# 63-00022_Mainboard_3_2.net
KiCad netlist of a schematic drawn in EAGLE
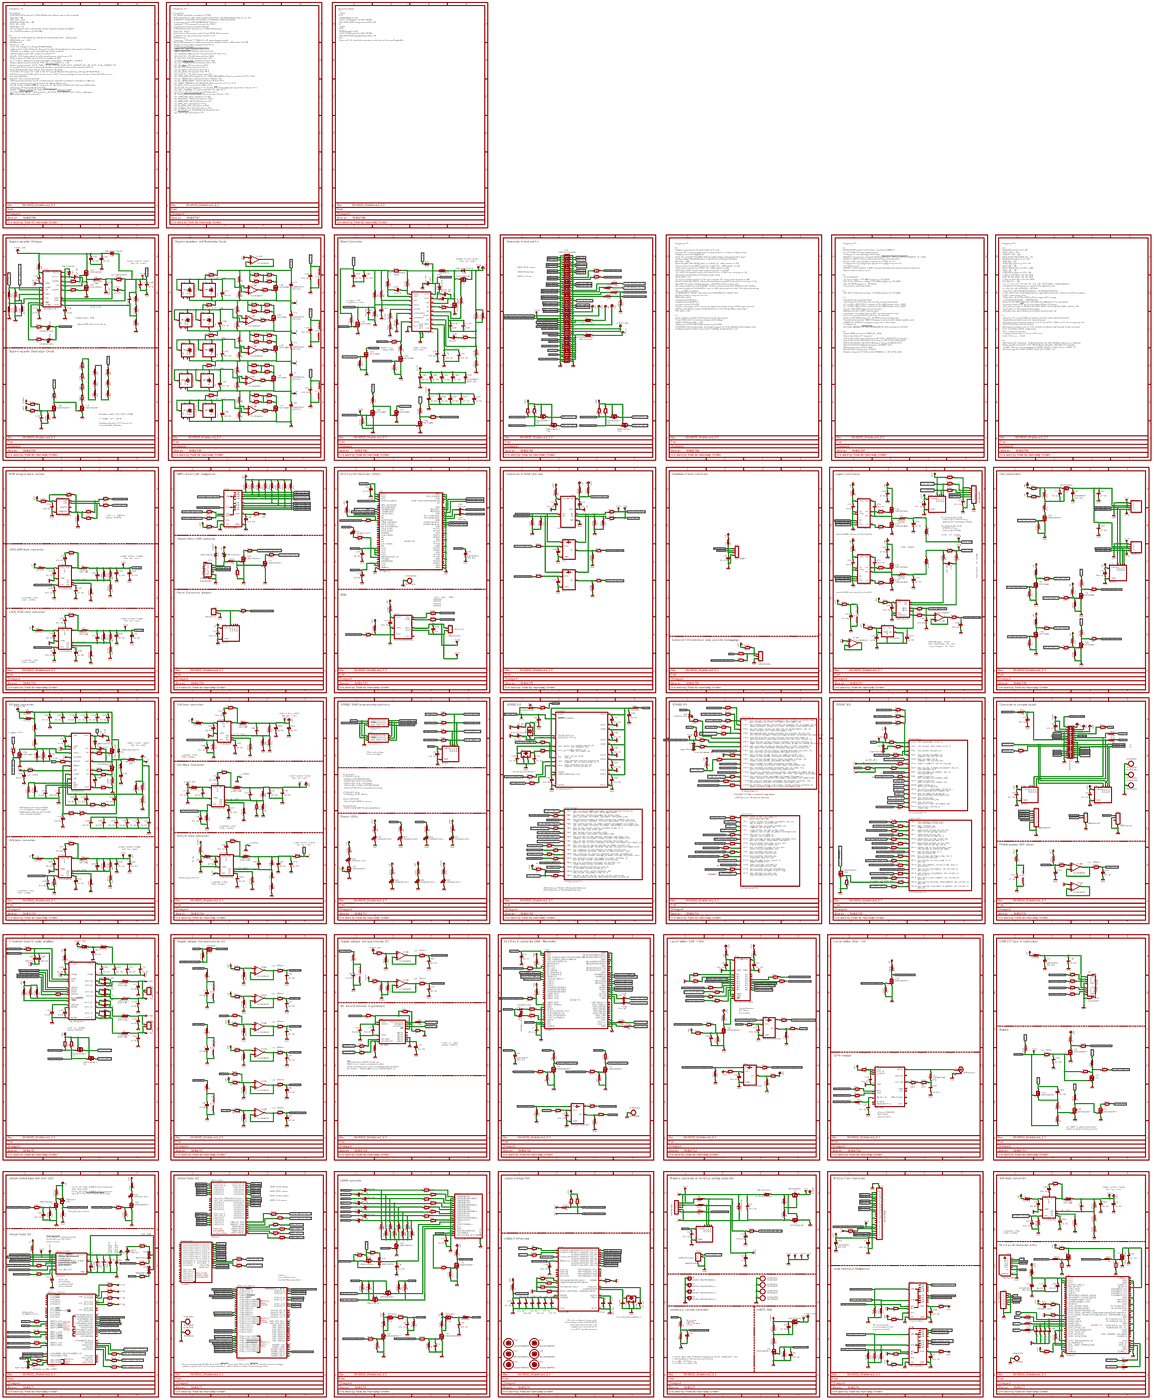
[diagram p0: schematic, sheet 1, overview]
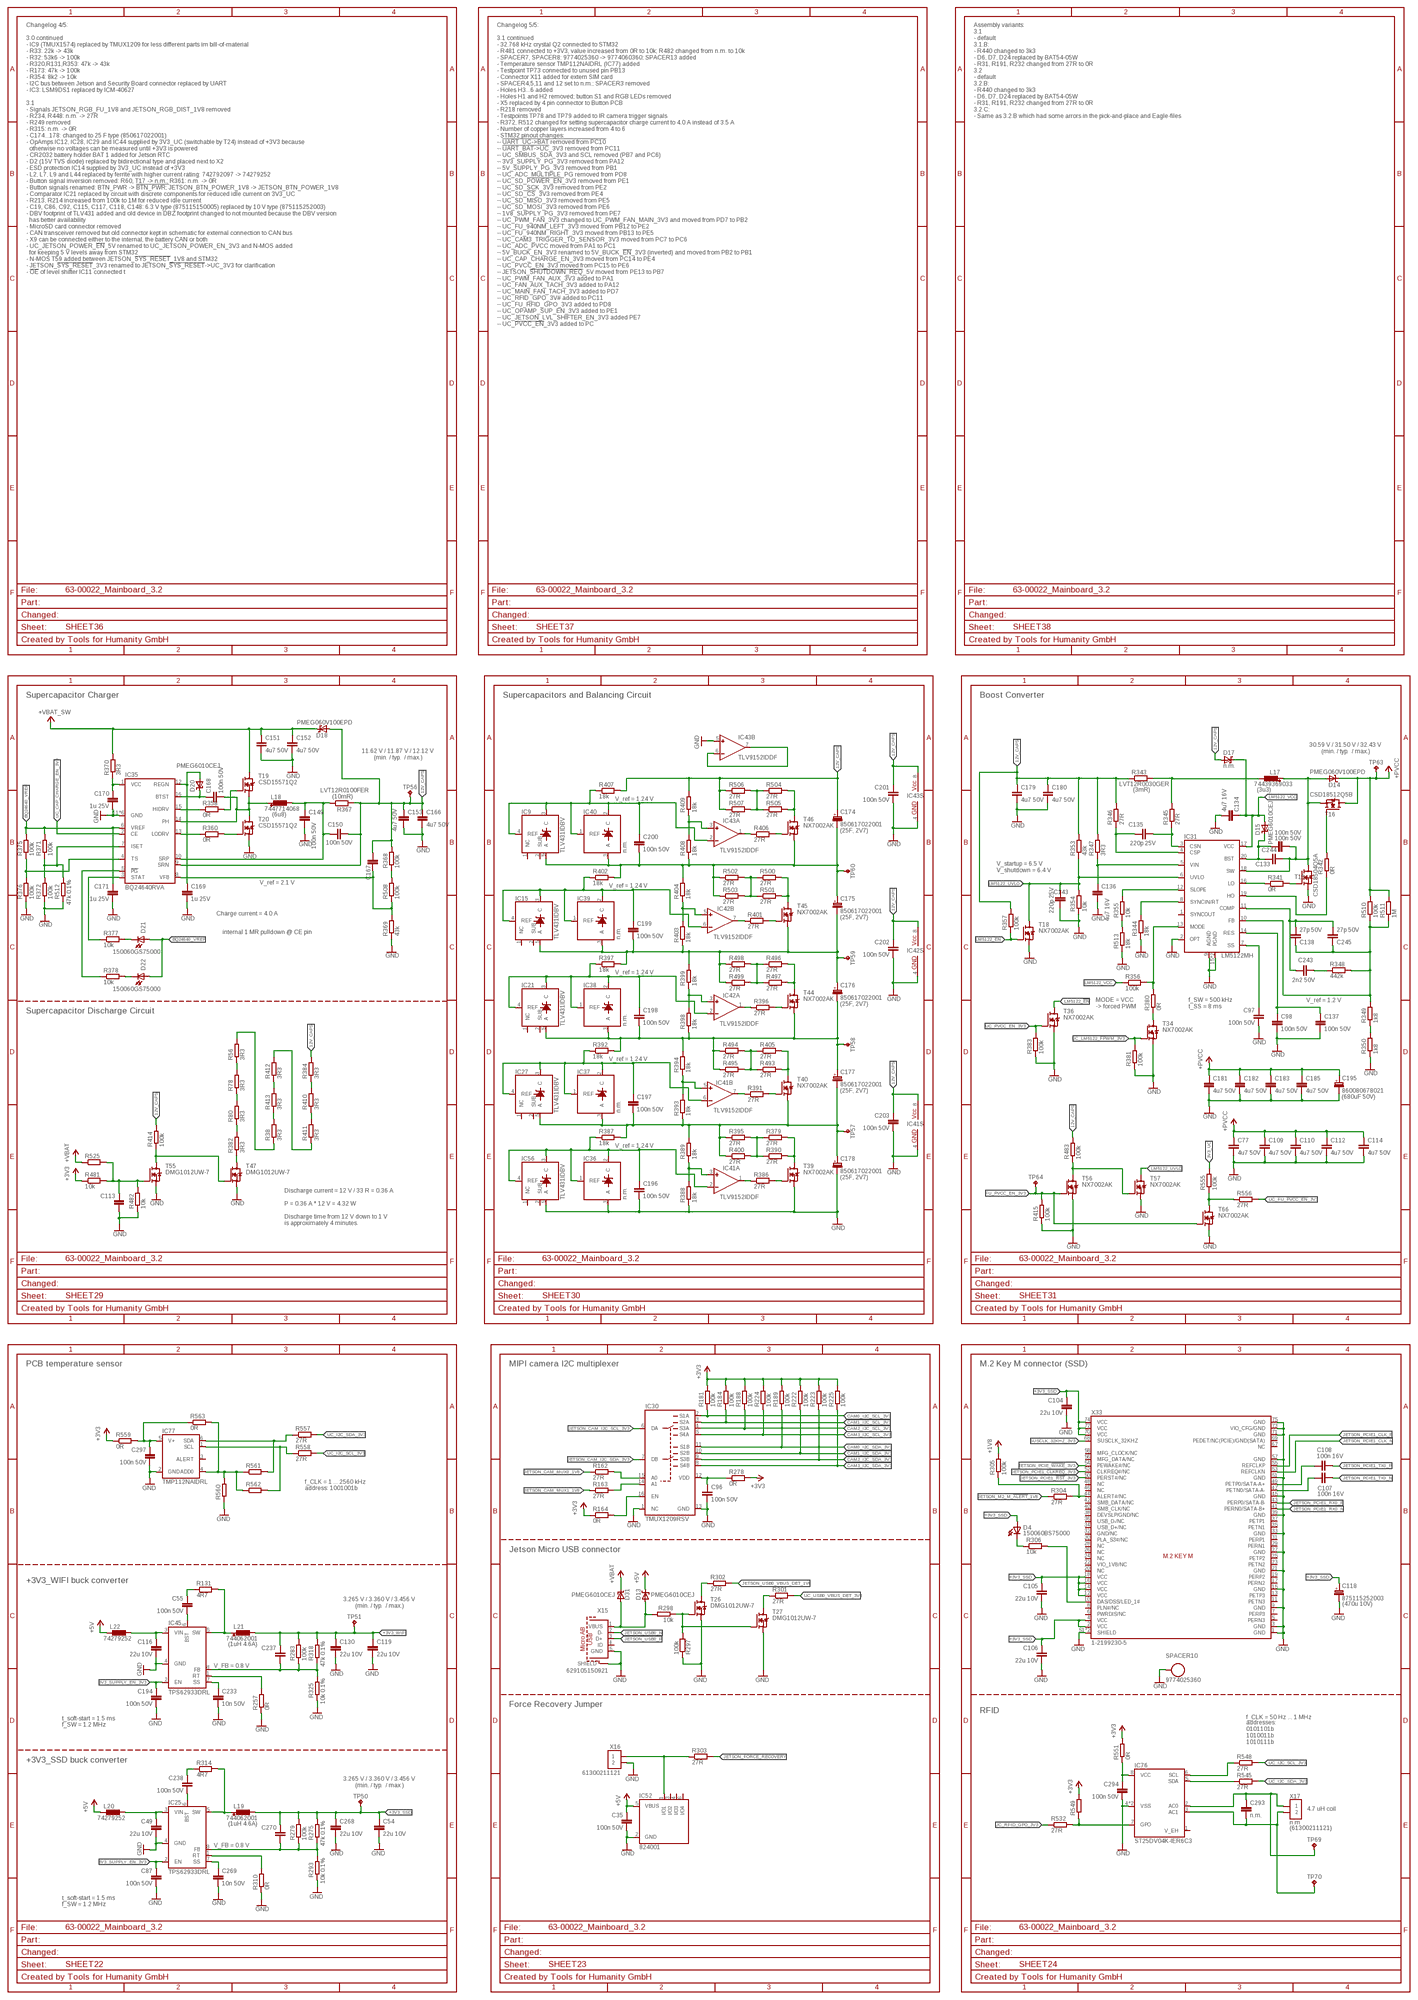
[diagram p1: schematic, sheet 1, part 1 of 4]
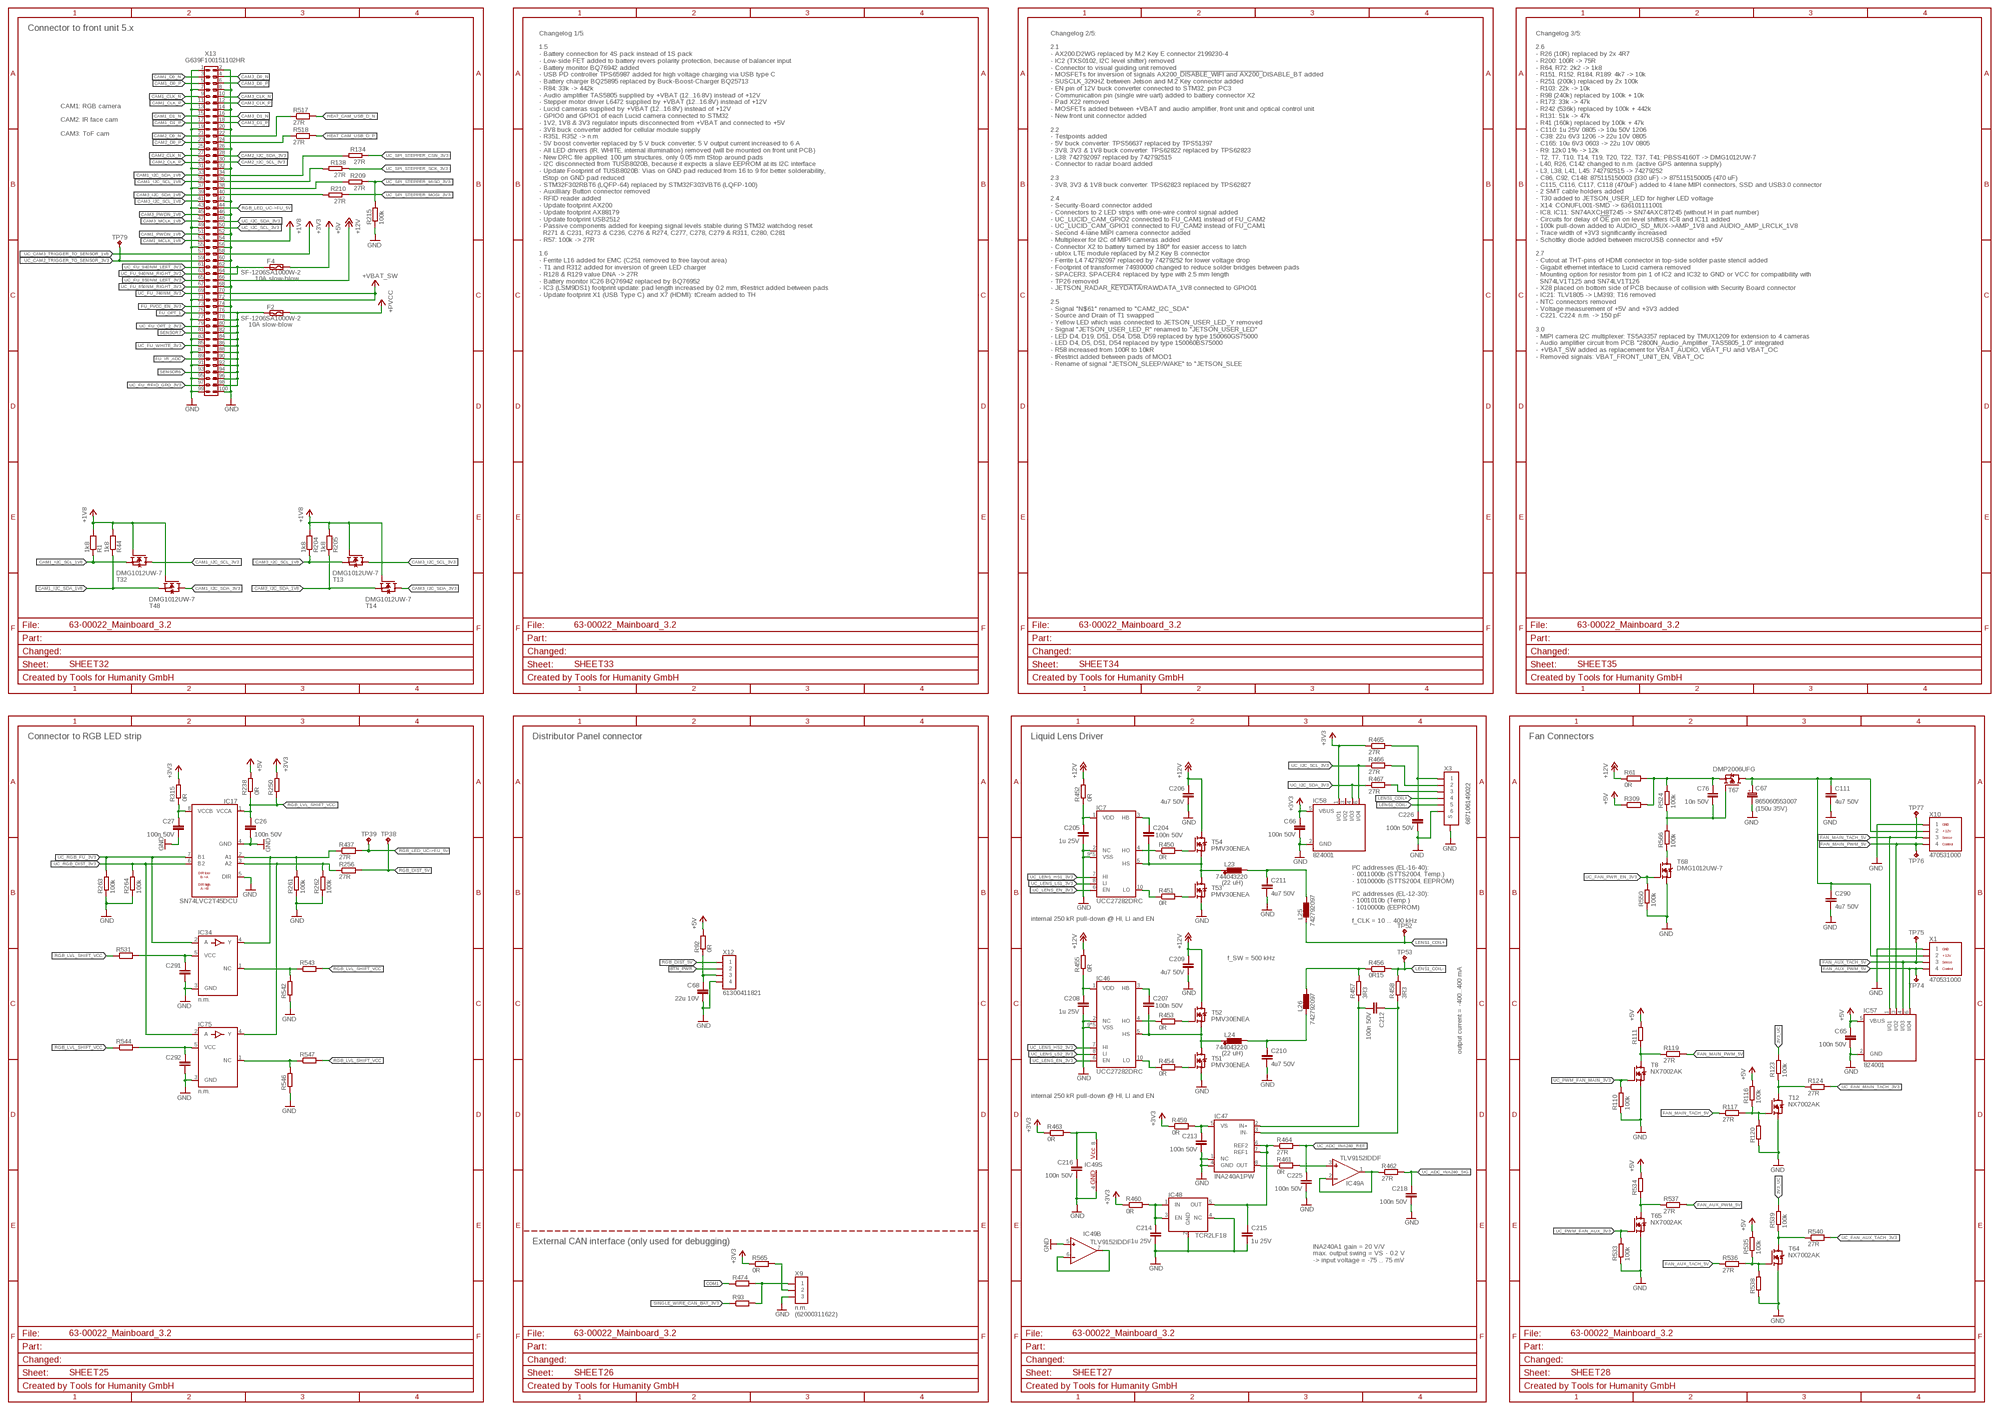
[diagram p2: schematic, sheet 1, part 2 of 4]
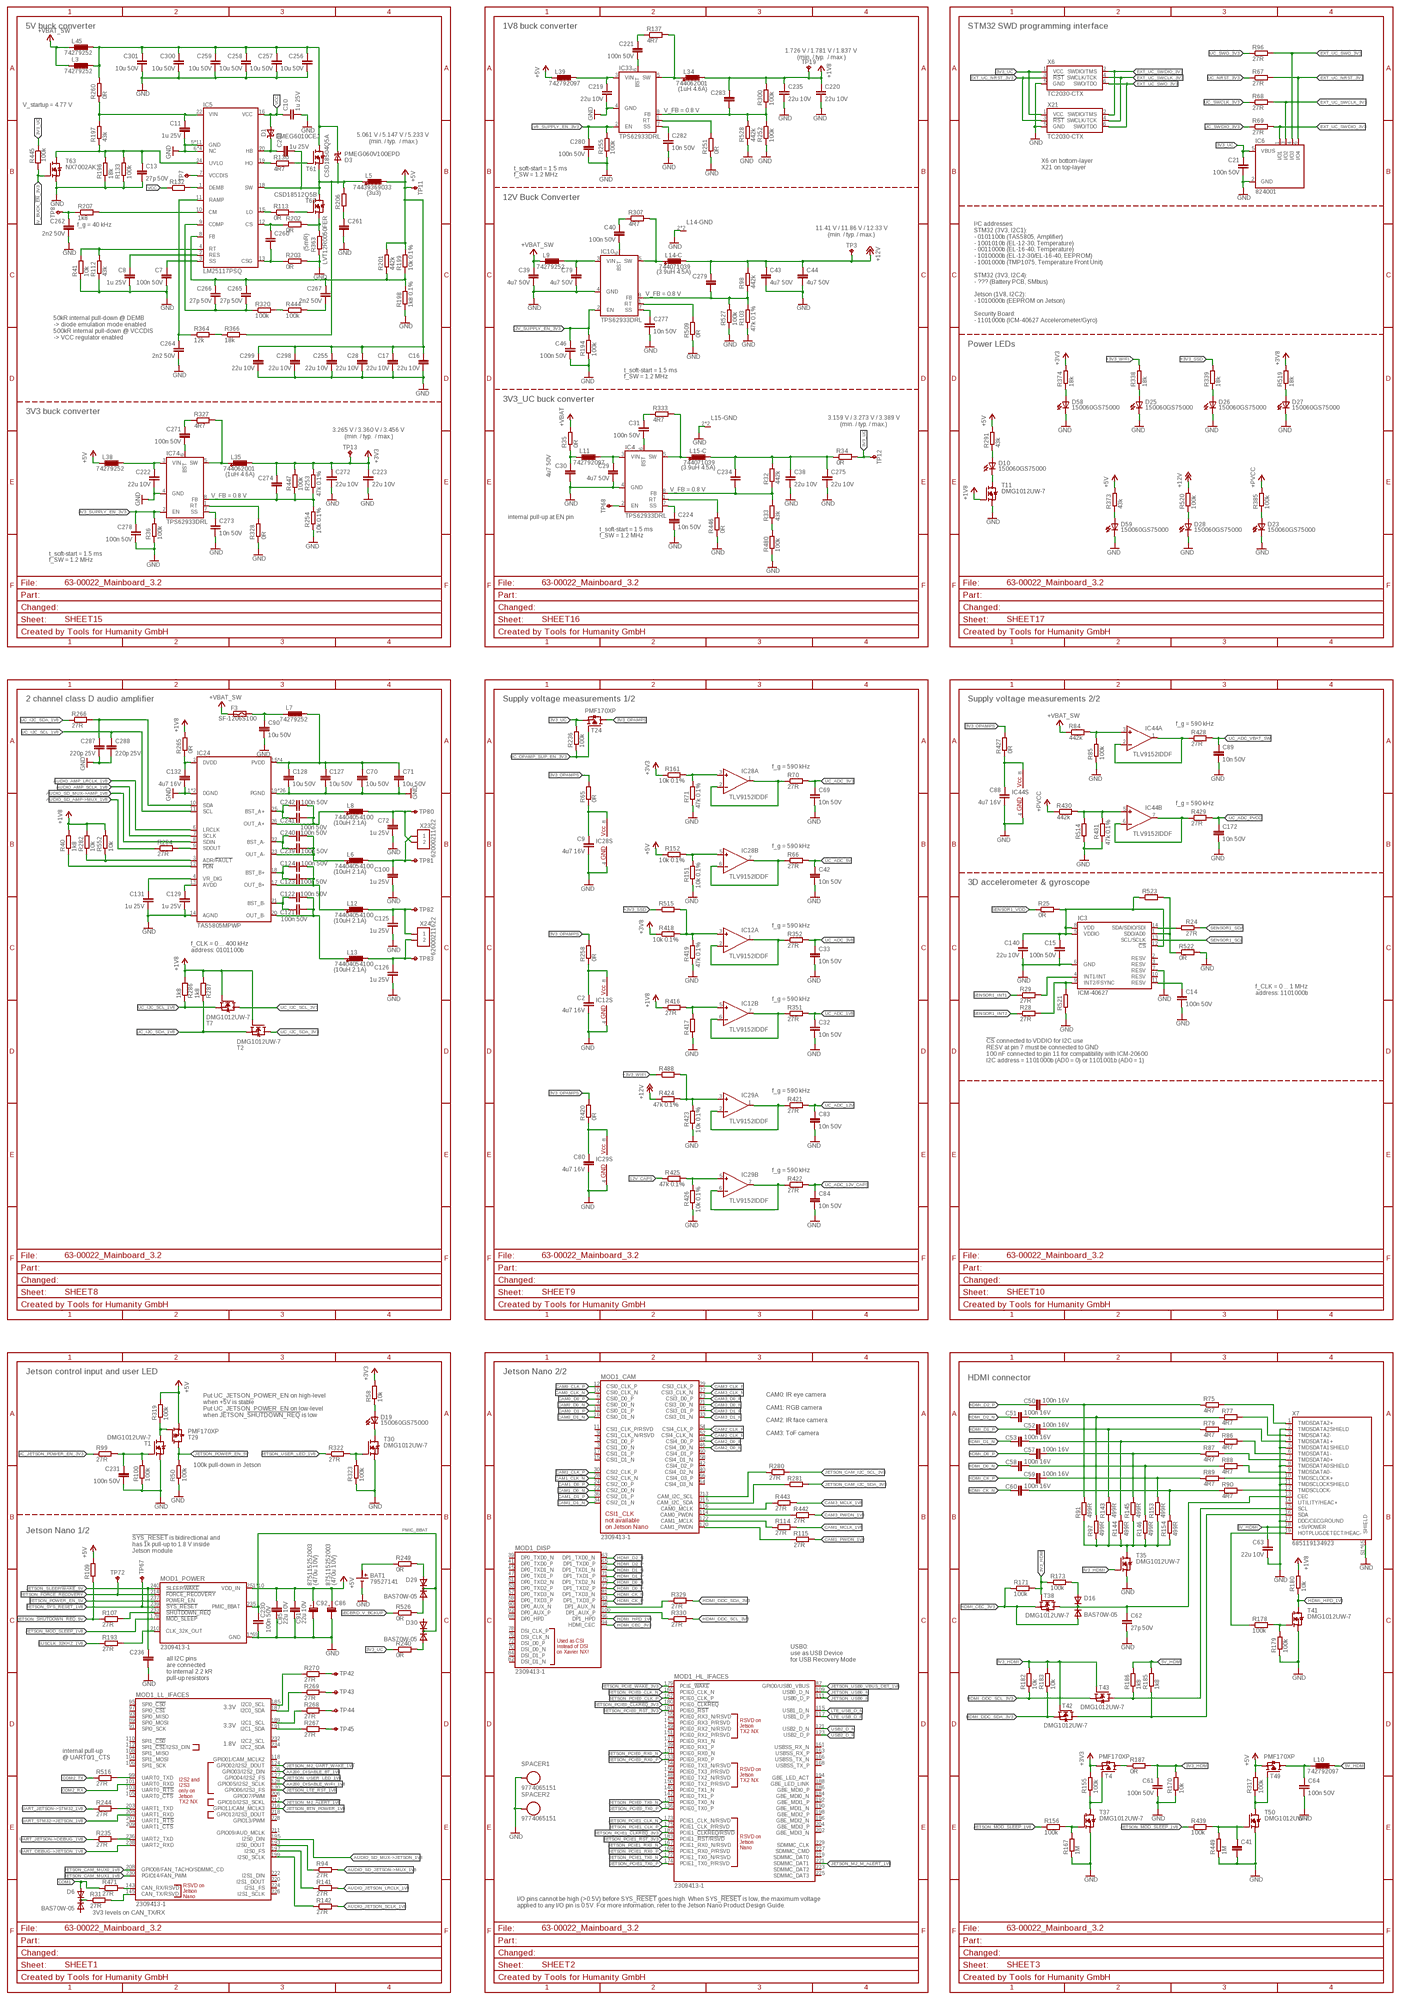
[diagram p3: schematic, sheet 1, part 3 of 4]
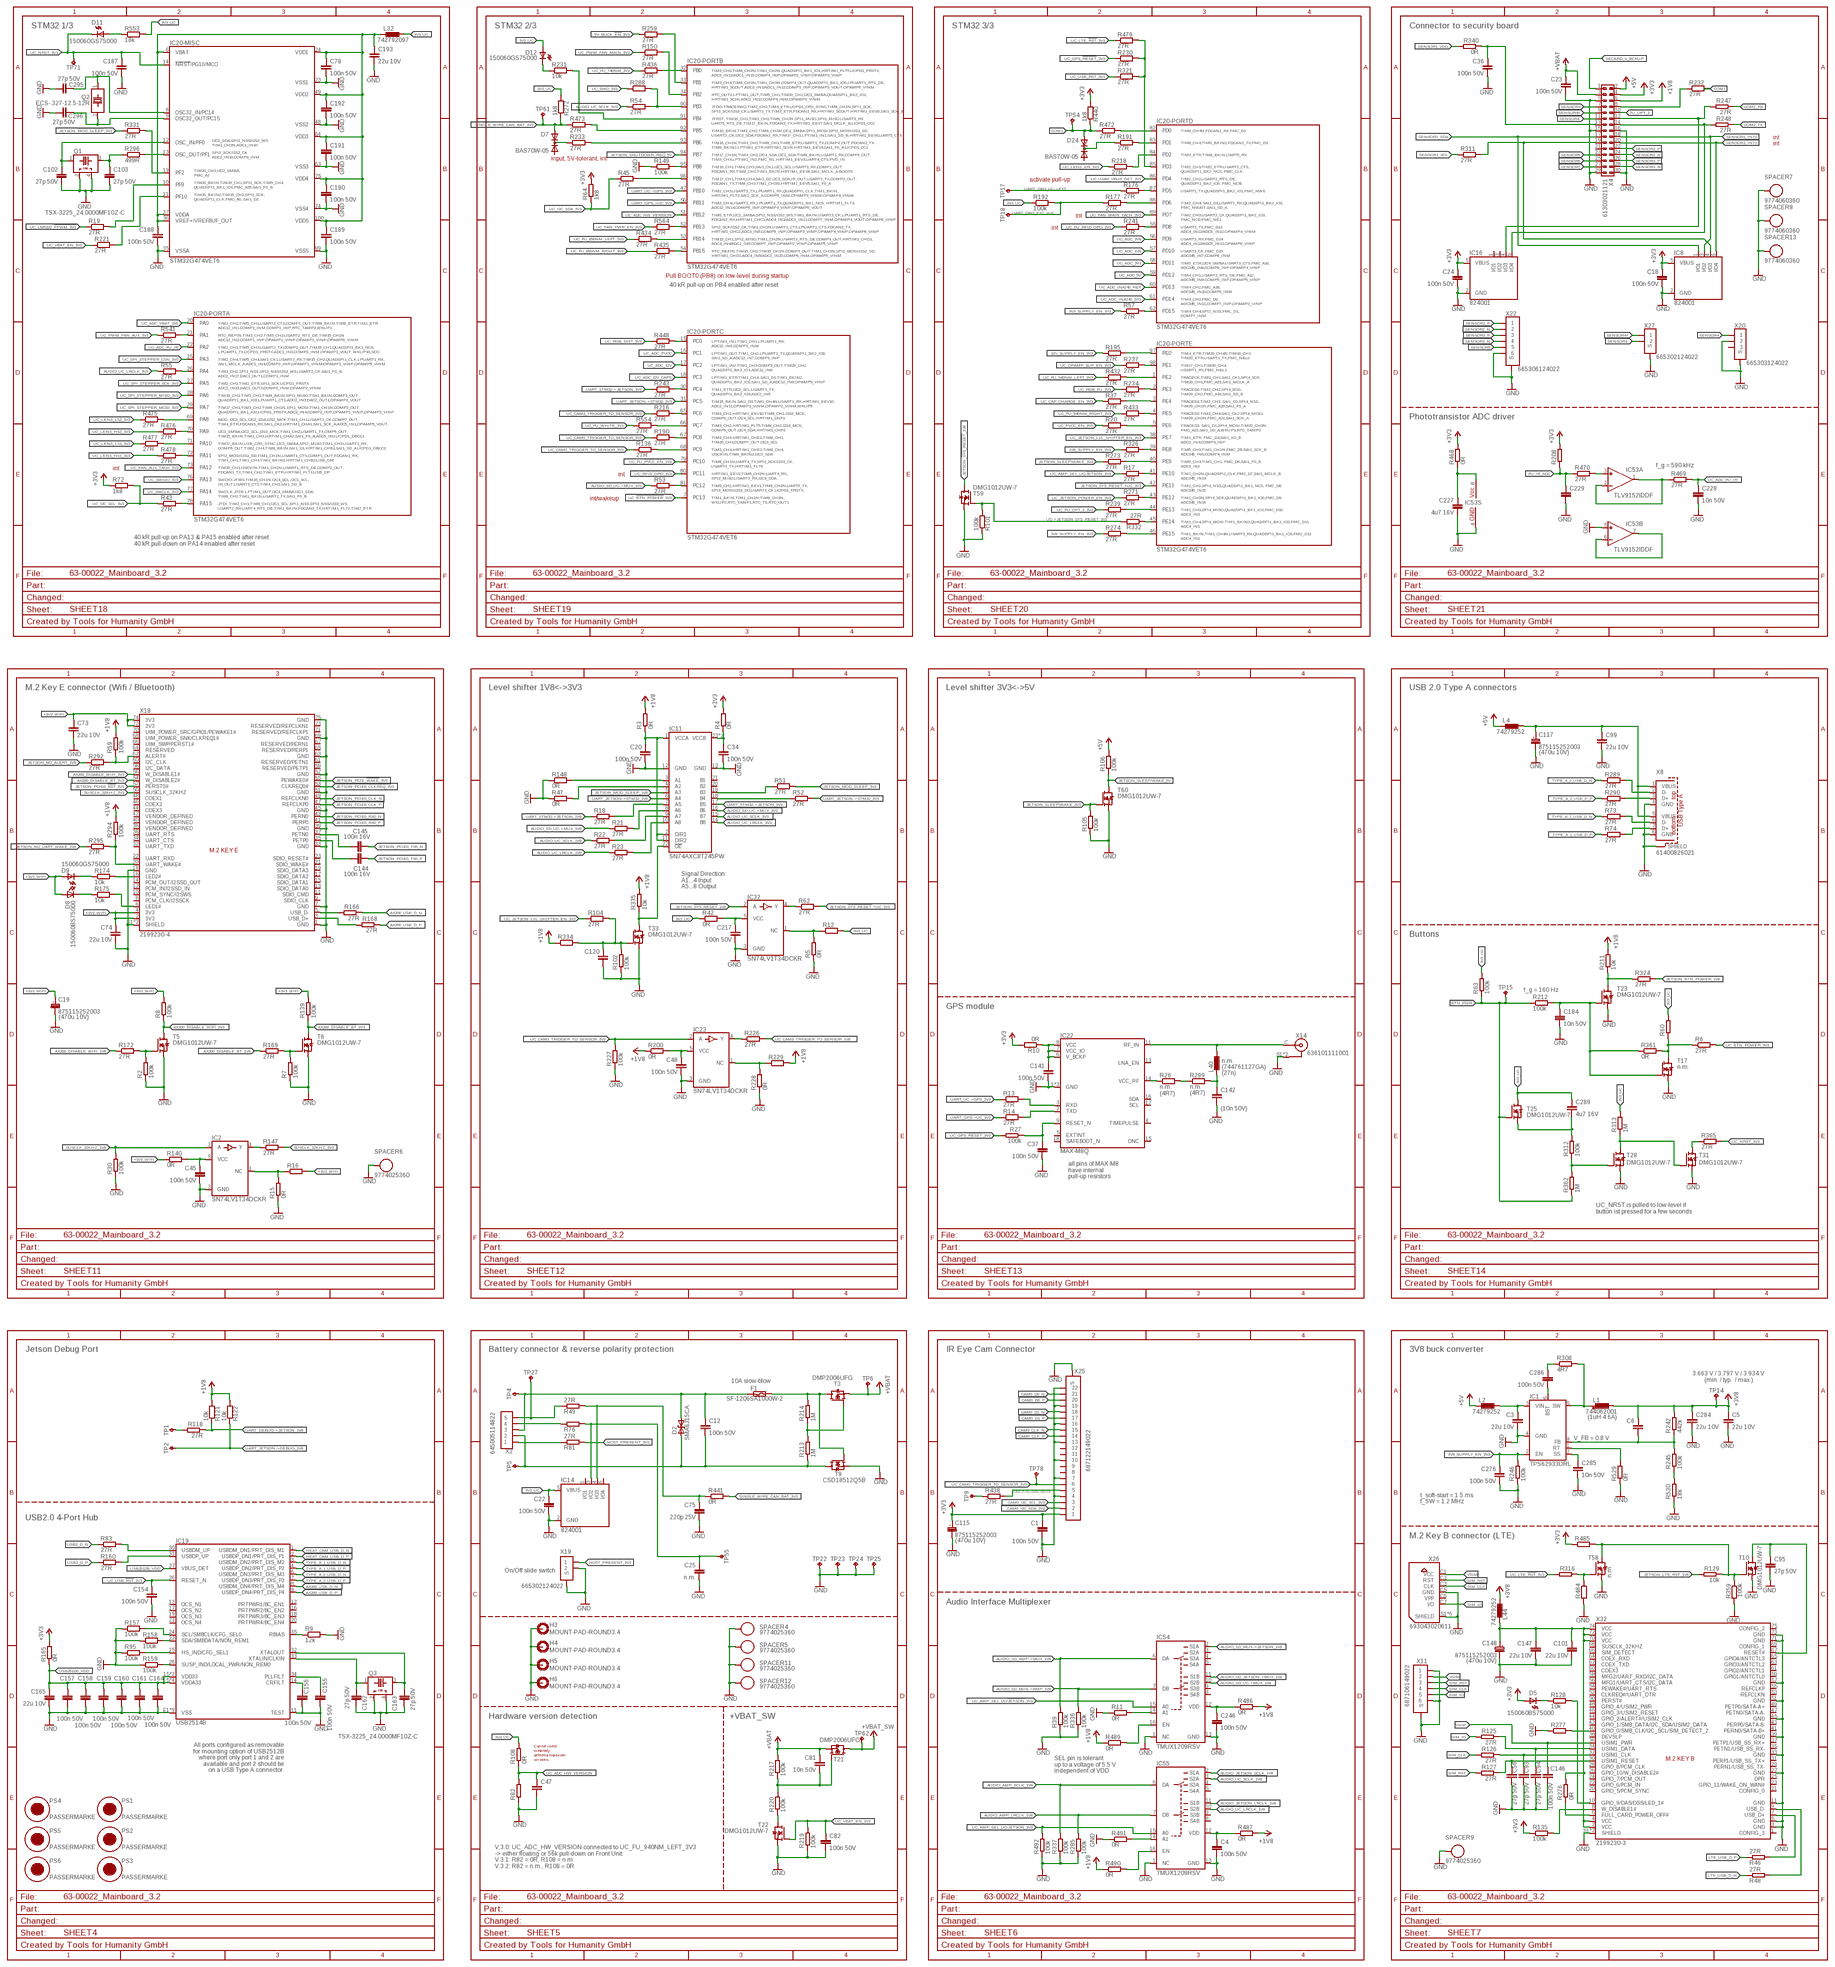
[diagram p4: schematic, sheet 1, part 4 of 4]

(export (version "E")
  (design (tool "Eeschema 10.0.6"))
  (components
    (comp (ref "BAT1")
      (value "79527141")
      (footprint "eagle-import:79527141_WUERTH")
      (fields (field (name "MANUFACTURER") "Wuerth"))
      (libsource (lib "eagle-import") (part "79527141"))
    )
    (comp (ref "C1")
      (value "100n 50V")
      (footprint "eagle-import:C0603")
      (fields
        (field (name "MANUFACTURER") "AVX")
        (field (name "TOLERANCE") "±20 %")
        (field (name "VOLTAGE") "50.0 V")
      )
      (libsource (lib "eagle-import") (part "C-EU-C0603-100N"))
    )
    (comp (ref "C2")
      (value "4u7 16V")
      (footprint "eagle-import:C0805")
      (fields
        (field (name "MANUFACTURER") "AVX")
        (field (name "TOLERANCE") "±20 %")
        (field (name "VOLTAGE") "16.0 V")
      )
      (libsource (lib "eagle-import") (part "C-EU-C0805-4U7"))
    )
    (comp (ref "C3")
      (value "22u 10V")
      (footprint "eagle-import:C0805")
      (fields
        (field (name "MANUFACTURER") "AVX")
        (field (name "TOLERANCE") "±20 %")
        (field (name "VOLTAGE") "10.0 V")
      )
      (libsource (lib "eagle-import") (part "C-EU-C0805-22U"))
    )
    (comp (ref "C4")
      (value "100n 50V")
      (footprint "eagle-import:C0603")
      (fields
        (field (name "MANUFACTURER") "AVX")
        (field (name "TOLERANCE") "±20 %")
        (field (name "VOLTAGE") "50.0 V")
      )
      (libsource (lib "eagle-import") (part "C-EU-C0603-100N"))
    )
    (comp (ref "C5")
      (value "22u 10V")
      (footprint "eagle-import:C0805")
      (fields
        (field (name "MANUFACTURER") "AVX")
        (field (name "TOLERANCE") "±20 %")
        (field (name "VOLTAGE") "10.0 V")
      )
      (libsource (lib "eagle-import") (part "C-EU-C0805-22U"))
    )
    (comp (ref "C6")
      (value "C-EU-C0603")
      (footprint "eagle-import:C0603")
      (fields (field (name "TOLERANCE") "±20 %") (field (name "VOLTAGE") "50.0 V"))
      (libsource (lib "eagle-import") (part "C-EU-C0603"))
    )
    (comp (ref "C7")
      (value "100n 50V")
      (footprint "eagle-import:C0603")
      (fields
        (field (name "MANUFACTURER") "AVX")
        (field (name "TOLERANCE") "±20 %")
        (field (name "VOLTAGE") "50.0 V")
      )
      (libsource (lib "eagle-import") (part "C-EU-C0603-100N"))
    )
    (comp (ref "C8")
      (value "1u 25V")
      (footprint "eagle-import:C0805")
      (fields
        (field (name "MANUFACTURER") "AVX")
        (field (name "TOLERANCE") "±20 %")
        (field (name "VOLTAGE") "25.0 V")
      )
      (libsource (lib "eagle-import") (part "C-EU-C0805-1U"))
    )
    (comp (ref "C9")
      (value "4u7 16V")
      (footprint "eagle-import:C0805")
      (fields
        (field (name "MANUFACTURER") "AVX")
        (field (name "TOLERANCE") "±20 %")
        (field (name "VOLTAGE") "16.0 V")
      )
      (libsource (lib "eagle-import") (part "C-EU-C0805-4U7"))
    )
    (comp (ref "C10")
      (value "1u 25V")
      (footprint "eagle-import:C0805")
      (fields
        (field (name "MANUFACTURER") "AVX")
        (field (name "TOLERANCE") "±20 %")
        (field (name "VOLTAGE") "25.0 V")
      )
      (libsource (lib "eagle-import") (part "C-EU-C0805-1U"))
    )
    (comp (ref "C11")
      (value "1u 25V")
      (footprint "eagle-import:C0805")
      (fields
        (field (name "MANUFACTURER") "AVX")
        (field (name "TOLERANCE") "±20 %")
        (field (name "VOLTAGE") "25.0 V")
      )
      (libsource (lib "eagle-import") (part "C-EU-C0805-1U"))
    )
    (comp (ref "C12")
      (value "100n 50V")
      (footprint "eagle-import:C0603")
      (fields
        (field (name "MANUFACTURER") "AVX")
        (field (name "TOLERANCE") "±20 %")
        (field (name "VOLTAGE") "50.0 V")
      )
      (libsource (lib "eagle-import") (part "C-EU-C0603-100N"))
    )
    (comp (ref "C13")
      (value "27p 50V")
      (footprint "eagle-import:C0603")
      (fields
        (field (name "MANUFACTURER") "AVX")
        (field (name "TOLERANCE") "±20 %")
        (field (name "VOLTAGE") "50.0 V")
      )
      (libsource (lib "eagle-import") (part "C-EU-C0603-27P"))
    )
    (comp (ref "C14")
      (value "100n 50V")
      (footprint "eagle-import:C0603")
      (fields
        (field (name "MANUFACTURER") "AVX")
        (field (name "TOLERANCE") "±20 %")
        (field (name "VOLTAGE") "50.0 V")
      )
      (libsource (lib "eagle-import") (part "C-EU-C0603-100N"))
    )
    (comp (ref "C15")
      (value "100n 50V")
      (footprint "eagle-import:C0603")
      (fields
        (field (name "MANUFACTURER") "AVX")
        (field (name "TOLERANCE") "±20 %")
        (field (name "VOLTAGE") "50.0 V")
      )
      (libsource (lib "eagle-import") (part "C-EU-C0603-100N"))
    )
    (comp (ref "C16")
      (value "22u 10V")
      (footprint "eagle-import:C0805")
      (fields
        (field (name "MANUFACTURER") "AVX")
        (field (name "TOLERANCE") "±20 %")
        (field (name "VOLTAGE") "10.0 V")
      )
      (libsource (lib "eagle-import") (part "C-EU-C0805-22U"))
    )
    (comp (ref "C17")
      (value "22u 10V")
      (footprint "eagle-import:C0805")
      (fields
        (field (name "MANUFACTURER") "AVX")
        (field (name "TOLERANCE") "±20 %")
        (field (name "VOLTAGE") "10.0 V")
      )
      (libsource (lib "eagle-import") (part "C-EU-C0805-22U"))
    )
    (comp (ref "C18")
      (value "100n 50V")
      (footprint "eagle-import:C0603")
      (fields
        (field (name "MANUFACTURER") "AVX")
        (field (name "TOLERANCE") "±20 %")
        (field (name "VOLTAGE") "50.0 V")
      )
      (libsource (lib "eagle-import") (part "C-EU-C0603-100N"))
    )
    (comp (ref "C19")
      (value "875115252003")
      (footprint "eagle-import:WCAP-PSHP_8.0X8.7_WE")
      (fields
        (field (name "MANUFACTURER") "Wuerth")
        (field (name "TOLERANCE") "±20 %")
        (field (name "VOLTAGE") "10.0 V")
      )
      (libsource (lib "eagle-import") (part "875115252003"))
    )
    (comp (ref "C20")
      (value "100n 50V")
      (footprint "eagle-import:C0603")
      (fields
        (field (name "MANUFACTURER") "AVX")
        (field (name "TOLERANCE") "±20 %")
        (field (name "VOLTAGE") "50.0 V")
      )
      (libsource (lib "eagle-import") (part "C-EU-C0603-100N"))
    )
    (comp (ref "C21")
      (value "100n 50V")
      (footprint "eagle-import:C0603")
      (fields
        (field (name "MANUFACTURER") "AVX")
        (field (name "TOLERANCE") "±20 %")
        (field (name "VOLTAGE") "50.0 V")
      )
      (libsource (lib "eagle-import") (part "C-EU-C0603-100N"))
    )
    (comp (ref "C22")
      (value "100n 50V")
      (footprint "eagle-import:C0603")
      (fields
        (field (name "MANUFACTURER") "AVX")
        (field (name "TOLERANCE") "±20 %")
        (field (name "VOLTAGE") "50.0 V")
      )
      (libsource (lib "eagle-import") (part "C-EU-C0603-100N"))
    )
    (comp (ref "C23")
      (value "100n 50V")
      (footprint "eagle-import:C0603")
      (fields
        (field (name "MANUFACTURER") "AVX")
        (field (name "TOLERANCE") "±20 %")
        (field (name "VOLTAGE") "50.0 V")
      )
      (libsource (lib "eagle-import") (part "C-EU-C0603-100N"))
    )
    (comp (ref "C24")
      (value "100n 50V")
      (footprint "eagle-import:C0603")
      (fields
        (field (name "MANUFACTURER") "AVX")
        (field (name "TOLERANCE") "±20 %")
        (field (name "VOLTAGE") "50.0 V")
      )
      (libsource (lib "eagle-import") (part "C-EU-C0603-100N"))
    )
    (comp (ref "C25")
      (value "n.m.")
      (footprint "eagle-import:C0402")
      (fields (field (name "TOLERANCE") "±20 %") (field (name "VOLTAGE") "25.0 V"))
      (libsource (lib "eagle-import") (part "C-EU-C0402"))
    )
    (comp (ref "C26")
      (value "100n 50V")
      (footprint "eagle-import:C0603")
      (fields
        (field (name "MANUFACTURER") "AVX")
        (field (name "TOLERANCE") "±20 %")
        (field (name "VOLTAGE") "50.0 V")
      )
      (libsource (lib "eagle-import") (part "C-EU-C0603-100N"))
    )
    (comp (ref "C27")
      (value "100n 50V")
      (footprint "eagle-import:C0603")
      (fields
        (field (name "MANUFACTURER") "AVX")
        (field (name "TOLERANCE") "±20 %")
        (field (name "VOLTAGE") "50.0 V")
      )
      (libsource (lib "eagle-import") (part "C-EU-C0603-100N"))
    )
    (comp (ref "C28")
      (value "22u 10V")
      (footprint "eagle-import:C0805")
      (fields
        (field (name "MANUFACTURER") "AVX")
        (field (name "TOLERANCE") "±20 %")
        (field (name "VOLTAGE") "10.0 V")
      )
      (libsource (lib "eagle-import") (part "C-EU-C0805-22U"))
    )
    (comp (ref "C29")
      (value "4u7 50V")
      (footprint "eagle-import:C1210")
      (fields
        (field (name "MANUFACTURER") "Taiyo Yuden")
        (field (name "TOLERANCE") "±20 %")
        (field (name "VOLTAGE") "50.0 V")
      )
      (libsource (lib "eagle-import") (part "C-EU-C1210-4U7-50V"))
    )
    (comp (ref "C30")
      (value "4u7 50V")
      (footprint "eagle-import:C1210")
      (fields
        (field (name "MANUFACTURER") "Taiyo Yuden")
        (field (name "TOLERANCE") "±20 %")
        (field (name "VOLTAGE") "50.0 V")
      )
      (libsource (lib "eagle-import") (part "C-EU-C1210-4U7-50V"))
    )
    (comp (ref "C31")
      (value "100n 50V")
      (footprint "eagle-import:C0603")
      (fields
        (field (name "MANUFACTURER") "AVX")
        (field (name "TOLERANCE") "±20 %")
        (field (name "VOLTAGE") "50.0 V")
      )
      (libsource (lib "eagle-import") (part "C-EU-C0603-100N"))
    )
    (comp (ref "C32")
      (value "10n 50V")
      (footprint "eagle-import:C0603")
      (fields
        (field (name "MANUFACTURER") "Samsung")
        (field (name "TOLERANCE") "±20 %")
        (field (name "VOLTAGE") "50.0 V")
      )
      (libsource (lib "eagle-import") (part "C-EU-C0603-10N"))
    )
    (comp (ref "C33")
      (value "10n 50V")
      (footprint "eagle-import:C0603")
      (fields
        (field (name "MANUFACTURER") "Samsung")
        (field (name "TOLERANCE") "±20 %")
        (field (name "VOLTAGE") "50.0 V")
      )
      (libsource (lib "eagle-import") (part "C-EU-C0603-10N"))
    )
    (comp (ref "C34")
      (value "100n 50V")
      (footprint "eagle-import:C0603")
      (fields
        (field (name "MANUFACTURER") "AVX")
        (field (name "TOLERANCE") "±20 %")
        (field (name "VOLTAGE") "50.0 V")
      )
      (libsource (lib "eagle-import") (part "C-EU-C0603-100N"))
    )
    (comp (ref "C35")
      (value "100n 50V")
      (footprint "eagle-import:C0603")
      (fields
        (field (name "MANUFACTURER") "AVX")
        (field (name "TOLERANCE") "±20 %")
        (field (name "VOLTAGE") "50.0 V")
      )
      (libsource (lib "eagle-import") (part "C-EU-C0603-100N"))
    )
    (comp (ref "C36")
      (value "100n 50V")
      (footprint "eagle-import:C0603")
      (fields
        (field (name "MANUFACTURER") "AVX")
        (field (name "TOLERANCE") "±20 %")
        (field (name "VOLTAGE") "50.0 V")
      )
      (libsource (lib "eagle-import") (part "C-EU-C0603-100N"))
    )
    (comp (ref "C37")
      (value "100n 50V")
      (footprint "eagle-import:C0603")
      (fields
        (field (name "MANUFACTURER") "AVX")
        (field (name "TOLERANCE") "±20 %")
        (field (name "VOLTAGE") "50.0 V")
      )
      (libsource (lib "eagle-import") (part "C-EU-C0603-100N"))
    )
    (comp (ref "C38")
      (value "22u 10V")
      (footprint "eagle-import:C0805")
      (fields
        (field (name "MANUFACTURER") "AVX")
        (field (name "TOLERANCE") "±20 %")
        (field (name "VOLTAGE") "10.0 V")
      )
      (libsource (lib "eagle-import") (part "C-EU-C0805-22U"))
    )
    (comp (ref "C39")
      (value "4u7 50V")
      (footprint "eagle-import:C1210")
      (fields
        (field (name "MANUFACTURER") "Taiyo Yuden")
        (field (name "TOLERANCE") "±20 %")
        (field (name "VOLTAGE") "50.0 V")
      )
      (libsource (lib "eagle-import") (part "C-EU-C1210-4U7-50V"))
    )
    (comp (ref "C40")
      (value "100n 50V")
      (footprint "eagle-import:C0603")
      (fields
        (field (name "MANUFACTURER") "AVX")
        (field (name "TOLERANCE") "±20 %")
        (field (name "VOLTAGE") "50.0 V")
      )
      (libsource (lib "eagle-import") (part "C-EU-C0603-100N"))
    )
    (comp (ref "C41")
      (value "C-EU-C0603")
      (footprint "eagle-import:C0603")
      (fields (field (name "TOLERANCE") "±20 %") (field (name "VOLTAGE") "50.0 V"))
      (libsource (lib "eagle-import") (part "C-EU-C0603"))
    )
    (comp (ref "C42")
      (value "10n 50V")
      (footprint "eagle-import:C0603")
      (fields
        (field (name "MANUFACTURER") "Samsung")
        (field (name "TOLERANCE") "±20 %")
        (field (name "VOLTAGE") "50.0 V")
      )
      (libsource (lib "eagle-import") (part "C-EU-C0603-10N"))
    )
    (comp (ref "C43")
      (value "4u7 50V")
      (footprint "eagle-import:C1210")
      (fields
        (field (name "MANUFACTURER") "Taiyo Yuden")
        (field (name "TOLERANCE") "±20 %")
        (field (name "VOLTAGE") "50.0 V")
      )
      (libsource (lib "eagle-import") (part "C-EU-C1210-4U7-50V"))
    )
    (comp (ref "C44")
      (value "4u7 50V")
      (footprint "eagle-import:C1210")
      (fields
        (field (name "MANUFACTURER") "Taiyo Yuden")
        (field (name "TOLERANCE") "±20 %")
        (field (name "VOLTAGE") "50.0 V")
      )
      (libsource (lib "eagle-import") (part "C-EU-C1210-4U7-50V"))
    )
    (comp (ref "C45")
      (value "100n 50V")
      (footprint "eagle-import:C0603")
      (fields
        (field (name "MANUFACTURER") "AVX")
        (field (name "TOLERANCE") "±20 %")
        (field (name "VOLTAGE") "50.0 V")
      )
      (libsource (lib "eagle-import") (part "C-EU-C0603-100N"))
    )
    (comp (ref "C46")
      (value "100n 50V")
      (footprint "eagle-import:C0603")
      (fields
        (field (name "MANUFACTURER") "AVX")
        (field (name "TOLERANCE") "±20 %")
        (field (name "VOLTAGE") "50.0 V")
      )
      (libsource (lib "eagle-import") (part "C-EU-C0603-100N"))
    )
    (comp (ref "C47")
      (value "C-EU-C0603")
      (footprint "eagle-import:C0603")
      (fields (field (name "TOLERANCE") "±20 %") (field (name "VOLTAGE") "50.0 V"))
      (libsource (lib "eagle-import") (part "C-EU-C0603"))
    )
    (comp (ref "C48")
      (value "100n 50V")
      (footprint "eagle-import:C0603")
      (fields
        (field (name "MANUFACTURER") "AVX")
        (field (name "TOLERANCE") "±20 %")
        (field (name "VOLTAGE") "50.0 V")
      )
      (libsource (lib "eagle-import") (part "C-EU-C0603-100N"))
    )
    (comp (ref "C49")
      (value "22u 10V")
      (footprint "eagle-import:C0805")
      (fields
        (field (name "MANUFACTURER") "AVX")
        (field (name "TOLERANCE") "±20 %")
        (field (name "VOLTAGE") "10.0 V")
      )
      (libsource (lib "eagle-import") (part "C-EU-C0805-22U"))
    )
    (comp (ref "C50")
      (value "100n 16V")
      (footprint "eagle-import:C0402")
      (fields
        (field (name "MANUFACTURER") "KEMET")
        (field (name "TOLERANCE") "±20 %")
        (field (name "VOLTAGE") "16.0 V")
      )
      (libsource (lib "eagle-import") (part "C-EU-C0402-100N"))
    )
    (comp (ref "C51")
      (value "100n 16V")
      (footprint "eagle-import:C0402")
      (fields
        (field (name "MANUFACTURER") "KEMET")
        (field (name "TOLERANCE") "±20 %")
        (field (name "VOLTAGE") "16.0 V")
      )
      (libsource (lib "eagle-import") (part "C-EU-C0402-100N"))
    )
    (comp (ref "C52")
      (value "100n 16V")
      (footprint "eagle-import:C0402")
      (fields
        (field (name "MANUFACTURER") "KEMET")
        (field (name "TOLERANCE") "±20 %")
        (field (name "VOLTAGE") "16.0 V")
      )
      (libsource (lib "eagle-import") (part "C-EU-C0402-100N"))
    )
    (comp (ref "C53")
      (value "100n 16V")
      (footprint "eagle-import:C0402")
      (fields
        (field (name "MANUFACTURER") "KEMET")
        (field (name "TOLERANCE") "±20 %")
        (field (name "VOLTAGE") "16.0 V")
      )
      (libsource (lib "eagle-import") (part "C-EU-C0402-100N"))
    )
    (comp (ref "C54")
      (value "22u 10V")
      (footprint "eagle-import:C0805")
      (fields
        (field (name "MANUFACTURER") "AVX")
        (field (name "TOLERANCE") "±20 %")
        (field (name "VOLTAGE") "10.0 V")
      )
      (libsource (lib "eagle-import") (part "C-EU-C0805-22U"))
    )
    (comp (ref "C55")
      (value "100n 50V")
      (footprint "eagle-import:C0603")
      (fields
        (field (name "MANUFACTURER") "AVX")
        (field (name "TOLERANCE") "±20 %")
        (field (name "VOLTAGE") "50.0 V")
      )
      (libsource (lib "eagle-import") (part "C-EU-C0603-100N"))
    )
    (comp (ref "C56")
      (value "27p 50V")
      (footprint "eagle-import:C0603")
      (fields
        (field (name "MANUFACTURER") "AVX")
        (field (name "TOLERANCE") "±20 %")
        (field (name "VOLTAGE") "50.0 V")
      )
      (libsource (lib "eagle-import") (part "C-EU-C0603-27P"))
    )
    (comp (ref "C57")
      (value "100n 16V")
      (footprint "eagle-import:C0402")
      (fields
        (field (name "MANUFACTURER") "KEMET")
        (field (name "TOLERANCE") "±20 %")
        (field (name "VOLTAGE") "16.0 V")
      )
      (libsource (lib "eagle-import") (part "C-EU-C0402-100N"))
    )
    (comp (ref "C58")
      (value "100n 16V")
      (footprint "eagle-import:C0402")
      (fields
        (field (name "MANUFACTURER") "KEMET")
        (field (name "TOLERANCE") "±20 %")
        (field (name "VOLTAGE") "16.0 V")
      )
      (libsource (lib "eagle-import") (part "C-EU-C0402-100N"))
    )
    (comp (ref "C59")
      (value "100n 16V")
      (footprint "eagle-import:C0402")
      (fields
        (field (name "MANUFACTURER") "KEMET")
        (field (name "TOLERANCE") "±20 %")
        (field (name "VOLTAGE") "16.0 V")
      )
      (libsource (lib "eagle-import") (part "C-EU-C0402-100N"))
    )
    (comp (ref "C60")
      (value "100n 16V")
      (footprint "eagle-import:C0402")
      (fields
        (field (name "MANUFACTURER") "KEMET")
        (field (name "TOLERANCE") "±20 %")
        (field (name "VOLTAGE") "16.0 V")
      )
      (libsource (lib "eagle-import") (part "C-EU-C0402-100N"))
    )
    (comp (ref "C61")
      (value "100n 50V")
      (footprint "eagle-import:C0603")
      (fields
        (field (name "MANUFACTURER") "AVX")
        (field (name "TOLERANCE") "±20 %")
        (field (name "VOLTAGE") "50.0 V")
      )
      (libsource (lib "eagle-import") (part "C-EU-C0603-100N"))
    )
    (comp (ref "C62")
      (value "27p 50V")
      (footprint "eagle-import:C0603")
      (fields
        (field (name "MANUFACTURER") "AVX")
        (field (name "TOLERANCE") "±20 %")
        (field (name "VOLTAGE") "50.0 V")
      )
      (libsource (lib "eagle-import") (part "C-EU-C0603-27P"))
    )
    (comp (ref "C63")
      (value "22u 10V")
      (footprint "eagle-import:C0805")
      (fields
        (field (name "MANUFACTURER") "AVX")
        (field (name "TOLERANCE") "±20 %")
        (field (name "VOLTAGE") "10.0 V")
      )
      (libsource (lib "eagle-import") (part "C-EU-C0805-22U"))
    )
    (comp (ref "C64")
      (value "100n 50V")
      (footprint "eagle-import:C0603")
      (fields
        (field (name "MANUFACTURER") "AVX")
        (field (name "TOLERANCE") "±20 %")
        (field (name "VOLTAGE") "50.0 V")
      )
      (libsource (lib "eagle-import") (part "C-EU-C0603-100N"))
    )
    (comp (ref "C65")
      (value "100n 50V")
      (footprint "eagle-import:C0603")
      (fields
        (field (name "MANUFACTURER") "AVX")
        (field (name "TOLERANCE") "±20 %")
        (field (name "VOLTAGE") "50.0 V")
      )
      (libsource (lib "eagle-import") (part "C-EU-C0603-100N"))
    )
    (comp (ref "C66")
      (value "100n 50V")
      (footprint "eagle-import:C0603")
      (fields
        (field (name "MANUFACTURER") "AVX")
        (field (name "TOLERANCE") "±20 %")
        (field (name "VOLTAGE") "50.0 V")
      )
      (libsource (lib "eagle-import") (part "C-EU-C0603-100N"))
    )
    (comp (ref "C67")
      (value "865060553007")
      (footprint "eagle-import:WCAP-ASLL_8.0X10.5_WE")
      (fields
        (field (name "MANUFACTURER") "Wuerth")
        (field (name "TOLERANCE") "± 20%")
        (field (name "VOLTAGE") "35.0 V")
      )
      (libsource (lib "eagle-import") (part "865060553007"))
    )
    (comp (ref "C68")
      (value "22u 10V")
      (footprint "eagle-import:C0805")
      (fields
        (field (name "MANUFACTURER") "AVX")
        (field (name "TOLERANCE") "±20 %")
        (field (name "VOLTAGE") "10.0 V")
      )
      (libsource (lib "eagle-import") (part "C-EU-C0805-22U"))
    )
    (comp (ref "C69")
      (value "10n 50V")
      (footprint "eagle-import:C0603")
      (fields
        (field (name "MANUFACTURER") "Samsung")
        (field (name "TOLERANCE") "±20 %")
        (field (name "VOLTAGE") "50.0 V")
      )
      (libsource (lib "eagle-import") (part "C-EU-C0603-10N"))
    )
    (comp (ref "C70")
      (value "10u 50V")
      (footprint "eagle-import:C1206")
      (fields
        (field (name "MANUFACTURER") "Samsung")
        (field (name "TOLERANCE") "±20 %")
        (field (name "VOLTAGE") "50.0 V")
      )
      (libsource (lib "eagle-import") (part "C-EU-C1206-10U"))
    )
    (comp (ref "C71")
      (value "10u 50V")
      (footprint "eagle-import:C1206")
      (fields
        (field (name "MANUFACTURER") "Samsung")
        (field (name "TOLERANCE") "±20 %")
        (field (name "VOLTAGE") "50.0 V")
      )
      (libsource (lib "eagle-import") (part "C-EU-C1206-10U"))
    )
    (comp (ref "C72")
      (value "1u 25V")
      (footprint "eagle-import:C0805")
      (fields
        (field (name "MANUFACTURER") "AVX")
        (field (name "TOLERANCE") "±20 %")
        (field (name "VOLTAGE") "25.0 V")
      )
      (libsource (lib "eagle-import") (part "C-EU-C0805-1U"))
    )
    (comp (ref "C73")
      (value "22u 10V")
      (footprint "eagle-import:C0805")
      (fields
        (field (name "MANUFACTURER") "AVX")
        (field (name "TOLERANCE") "±20 %")
        (field (name "VOLTAGE") "10.0 V")
      )
      (libsource (lib "eagle-import") (part "C-EU-C0805-22U"))
    )
    (comp (ref "C74")
      (value "22u 10V")
      (footprint "eagle-import:C0805")
      (fields
        (field (name "MANUFACTURER") "AVX")
        (field (name "TOLERANCE") "±20 %")
        (field (name "VOLTAGE") "10.0 V")
      )
      (libsource (lib "eagle-import") (part "C-EU-C0805-22U"))
    )
    (comp (ref "C75")
      (value "220p 25V")
      (footprint "eagle-import:C0402")
      (fields
        (field (name "MANUFACTURER") "Wuerth")
        (field (name "TOLERANCE") "±10 %")
        (field (name "VOLTAGE") "25.0 V")
      )
      (libsource (lib "eagle-import") (part "C-EU-C0402-220P"))
    )
    (comp (ref "C76")
      (value "10n 50V")
      (footprint "eagle-import:C0603")
      (fields
        (field (name "MANUFACTURER") "Samsung")
        (field (name "TOLERANCE") "±20 %")
        (field (name "VOLTAGE") "50.0 V")
      )
      (libsource (lib "eagle-import") (part "C-EU-C0603-10N"))
    )
    (comp (ref "C77")
      (value "4u7 50V")
      (footprint "eagle-import:C1210")
      (fields
        (field (name "MANUFACTURER") "Taiyo Yuden")
        (field (name "TOLERANCE") "±20 %")
        (field (name "VOLTAGE") "50.0 V")
      )
      (libsource (lib "eagle-import") (part "C-EU-C1210-4U7-50V"))
    )
    (comp (ref "C78")
      (value "100n 50V")
      (footprint "eagle-import:C0603")
      (fields
        (field (name "MANUFACTURER") "AVX")
        (field (name "TOLERANCE") "±20 %")
        (field (name "VOLTAGE") "50.0 V")
      )
      (libsource (lib "eagle-import") (part "C-EU-C0603-100N"))
    )
    (comp (ref "C79")
      (value "4u7 50V")
      (footprint "eagle-import:C1210")
      (fields
        (field (name "MANUFACTURER") "Taiyo Yuden")
        (field (name "TOLERANCE") "±20 %")
        (field (name "VOLTAGE") "50.0 V")
      )
      (libsource (lib "eagle-import") (part "C-EU-C1210-4U7-50V"))
    )
    (comp (ref "C80")
      (value "4u7 16V")
      (footprint "eagle-import:C0805")
      (fields
        (field (name "MANUFACTURER") "AVX")
        (field (name "TOLERANCE") "±20 %")
        (field (name "VOLTAGE") "16.0 V")
      )
      (libsource (lib "eagle-import") (part "C-EU-C0805-4U7"))
    )
    (comp (ref "C81")
      (value "10n 50V")
      (footprint "eagle-import:C0603")
      (fields
        (field (name "MANUFACTURER") "Samsung")
        (field (name "TOLERANCE") "±20 %")
        (field (name "VOLTAGE") "50.0 V")
      )
      (libsource (lib "eagle-import") (part "C-EU-C0603-10N"))
    )
    (comp (ref "C82")
      (value "100n 50V")
      (footprint "eagle-import:C0603")
      (fields
        (field (name "MANUFACTURER") "AVX")
        (field (name "TOLERANCE") "±20 %")
        (field (name "VOLTAGE") "50.0 V")
      )
      (libsource (lib "eagle-import") (part "C-EU-C0603-100N"))
    )
    (comp (ref "C83")
      (value "10n 50V")
      (footprint "eagle-import:C0603")
      (fields
        (field (name "MANUFACTURER") "Samsung")
        (field (name "TOLERANCE") "±20 %")
        (field (name "VOLTAGE") "50.0 V")
      )
      (libsource (lib "eagle-import") (part "C-EU-C0603-10N"))
    )
    (comp (ref "C84")
      (value "10n 50V")
      (footprint "eagle-import:C0603")
      (fields
        (field (name "MANUFACTURER") "Samsung")
        (field (name "TOLERANCE") "±20 %")
        (field (name "VOLTAGE") "50.0 V")
      )
      (libsource (lib "eagle-import") (part "C-EU-C0603-10N"))
    )
    (comp (ref "C85")
      (value "22u 10V")
      (footprint "eagle-import:C0805")
      (fields
        (field (name "MANUFACTURER") "AVX")
        (field (name "TOLERANCE") "±20 %")
        (field (name "VOLTAGE") "10.0 V")
      )
      (libsource (lib "eagle-import") (part "C-EU-C0805-22U"))
    )
    (comp (ref "C86")
      (value "875115252003")
      (footprint "eagle-import:WCAP-PSHP_8.0X8.7_WE")
      (fields
        (field (name "MANUFACTURER") "Wuerth")
        (field (name "TOLERANCE") "±20 %")
        (field (name "VOLTAGE") "10.0 V")
      )
      (libsource (lib "eagle-import") (part "875115252003"))
    )
    (comp (ref "C87")
      (value "100n 50V")
      (footprint "eagle-import:C0603")
      (fields
        (field (name "MANUFACTURER") "AVX")
        (field (name "TOLERANCE") "±20 %")
        (field (name "VOLTAGE") "50.0 V")
      )
      (libsource (lib "eagle-import") (part "C-EU-C0603-100N"))
    )
    (comp (ref "C88")
      (value "4u7 16V")
      (footprint "eagle-import:C0805")
      (fields
        (field (name "MANUFACTURER") "AVX")
        (field (name "TOLERANCE") "±20 %")
        (field (name "VOLTAGE") "16.0 V")
      )
      (libsource (lib "eagle-import") (part "C-EU-C0805-4U7"))
    )
    (comp (ref "C89")
      (value "10n 50V")
      (footprint "eagle-import:C0603")
      (fields
        (field (name "MANUFACTURER") "Samsung")
        (field (name "TOLERANCE") "±20 %")
        (field (name "VOLTAGE") "50.0 V")
      )
      (libsource (lib "eagle-import") (part "C-EU-C0603-10N"))
    )
    (comp (ref "C90")
      (value "10u 50V")
      (footprint "eagle-import:C1206")
      (fields
        (field (name "MANUFACTURER") "Samsung")
        (field (name "TOLERANCE") "±20 %")
        (field (name "VOLTAGE") "50.0 V")
      )
      (libsource (lib "eagle-import") (part "C-EU-C1206-10U"))
    )
    (comp (ref "C91")
      (value "22u 10V")
      (footprint "eagle-import:C0805")
      (fields
        (field (name "MANUFACTURER") "AVX")
        (field (name "TOLERANCE") "±20 %")
        (field (name "VOLTAGE") "10.0 V")
      )
      (libsource (lib "eagle-import") (part "C-EU-C0805-22U"))
    )
    (comp (ref "C92")
      (value "875115252003")
      (footprint "eagle-import:WCAP-PSHP_8.0X8.7_WE")
      (fields
        (field (name "MANUFACTURER") "Wuerth")
        (field (name "TOLERANCE") "±20 %")
        (field (name "VOLTAGE") "10.0 V")
      )
      (libsource (lib "eagle-import") (part "875115252003"))
    )
    (comp (ref "C93")
      (value "27p 50V")
      (footprint "eagle-import:C0603")
      (fields
        (field (name "MANUFACTURER") "AVX")
        (field (name "TOLERANCE") "±20 %")
        (field (name "VOLTAGE") "50.0 V")
      )
      (libsource (lib "eagle-import") (part "C-EU-C0603-27P"))
    )
    (comp (ref "C94")
      (value "27p 50V")
      (footprint "eagle-import:C0603")
      (fields
        (field (name "MANUFACTURER") "AVX")
        (field (name "TOLERANCE") "±20 %")
        (field (name "VOLTAGE") "50.0 V")
      )
      (libsource (lib "eagle-import") (part "C-EU-C0603-27P"))
    )
    (comp (ref "C95")
      (value "27p 50V")
      (footprint "eagle-import:C0603")
      (fields
        (field (name "MANUFACTURER") "AVX")
        (field (name "TOLERANCE") "±20 %")
        (field (name "VOLTAGE") "50.0 V")
      )
      (libsource (lib "eagle-import") (part "C-EU-C0603-27P"))
    )
    (comp (ref "C96")
      (value "100n 50V")
      (footprint "eagle-import:C0603")
      (fields
        (field (name "MANUFACTURER") "AVX")
        (field (name "TOLERANCE") "±20 %")
        (field (name "VOLTAGE") "50.0 V")
      )
      (libsource (lib "eagle-import") (part "C-EU-C0603-100N"))
    )
    (comp (ref "C97")
      (value "100n 50V")
      (footprint "eagle-import:C0603")
      (fields
        (field (name "MANUFACTURER") "AVX")
        (field (name "TOLERANCE") "±20 %")
        (field (name "VOLTAGE") "50.0 V")
      )
      (libsource (lib "eagle-import") (part "C-EU-C0603-100N"))
    )
    (comp (ref "C98")
      (value "100n 50V")
      (footprint "eagle-import:C0603")
      (fields
        (field (name "MANUFACTURER") "AVX")
        (field (name "TOLERANCE") "±20 %")
        (field (name "VOLTAGE") "50.0 V")
      )
      (libsource (lib "eagle-import") (part "C-EU-C0603-100N"))
    )
    (comp (ref "C99")
      (value "22u 10V")
      (footprint "eagle-import:C0805")
      (fields
        (field (name "MANUFACTURER") "AVX")
        (field (name "TOLERANCE") "±20 %")
        (field (name "VOLTAGE") "10.0 V")
      )
      (libsource (lib "eagle-import") (part "C-EU-C0805-22U"))
    )
    (comp (ref "C100")
      (value "1u 25V")
      (footprint "eagle-import:C0805")
      (fields
        (field (name "MANUFACTURER") "AVX")
        (field (name "TOLERANCE") "±20 %")
        (field (name "VOLTAGE") "25.0 V")
      )
      (libsource (lib "eagle-import") (part "C-EU-C0805-1U"))
    )
    (comp (ref "C101")
      (value "22u 10V")
      (footprint "eagle-import:C0805")
      (fields
        (field (name "MANUFACTURER") "AVX")
        (field (name "TOLERANCE") "±20 %")
        (field (name "VOLTAGE") "10.0 V")
      )
      (libsource (lib "eagle-import") (part "C-EU-C0805-22U"))
    )
    (comp (ref "C102")
      (value "27p 50V")
      (footprint "eagle-import:C0603")
      (fields
        (field (name "MANUFACTURER") "AVX")
        (field (name "TOLERANCE") "±20 %")
        (field (name "VOLTAGE") "50.0 V")
      )
      (libsource (lib "eagle-import") (part "C-EU-C0603-27P"))
    )
    (comp (ref "C103")
      (value "27p 50V")
      (footprint "eagle-import:C0603")
      (fields
        (field (name "MANUFACTURER") "AVX")
        (field (name "TOLERANCE") "±20 %")
        (field (name "VOLTAGE") "50.0 V")
      )
      (libsource (lib "eagle-import") (part "C-EU-C0603-27P"))
    )
    (comp (ref "C104")
      (value "22u 10V")
      (footprint "eagle-import:C0805")
      (fields
        (field (name "MANUFACTURER") "AVX")
        (field (name "TOLERANCE") "±20 %")
        (field (name "VOLTAGE") "10.0 V")
      )
      (libsource (lib "eagle-import") (part "C-EU-C0805-22U"))
    )
    (comp (ref "C105")
      (value "22u 10V")
      (footprint "eagle-import:C0805")
      (fields
        (field (name "MANUFACTURER") "AVX")
        (field (name "TOLERANCE") "±20 %")
        (field (name "VOLTAGE") "10.0 V")
      )
      (libsource (lib "eagle-import") (part "C-EU-C0805-22U"))
    )
    (comp (ref "C106")
      (value "22u 10V")
      (footprint "eagle-import:C0805")
      (fields
        (field (name "MANUFACTURER") "AVX")
        (field (name "TOLERANCE") "±20 %")
        (field (name "VOLTAGE") "10.0 V")
      )
      (libsource (lib "eagle-import") (part "C-EU-C0805-22U"))
    )
    (comp (ref "C107")
      (value "100n 16V")
      (footprint "eagle-import:C0402")
      (fields
        (field (name "MANUFACTURER") "KEMET")
        (field (name "TOLERANCE") "±20 %")
        (field (name "VOLTAGE") "16.0 V")
      )
      (libsource (lib "eagle-import") (part "C-EU-C0402-100N"))
    )
    (comp (ref "C108")
      (value "100n 16V")
      (footprint "eagle-import:C0402")
      (fields
        (field (name "MANUFACTURER") "KEMET")
        (field (name "TOLERANCE") "±20 %")
        (field (name "VOLTAGE") "16.0 V")
      )
      (libsource (lib "eagle-import") (part "C-EU-C0402-100N"))
    )
    (comp (ref "C109")
      (value "4u7 50V")
      (footprint "eagle-import:C1210")
      (fields
        (field (name "MANUFACTURER") "Taiyo Yuden")
        (field (name "TOLERANCE") "±20 %")
        (field (name "VOLTAGE") "50.0 V")
      )
      (libsource (lib "eagle-import") (part "C-EU-C1210-4U7-50V"))
    )
    (comp (ref "C110")
      (value "4u7 50V")
      (footprint "eagle-import:C1210")
      (fields
        (field (name "MANUFACTURER") "Taiyo Yuden")
        (field (name "TOLERANCE") "±20 %")
        (field (name "VOLTAGE") "50.0 V")
      )
      (libsource (lib "eagle-import") (part "C-EU-C1210-4U7-50V"))
    )
    (comp (ref "C111")
      (value "4u7 50V")
      (footprint "eagle-import:C1210")
      (fields
        (field (name "MANUFACTURER") "Taiyo Yuden")
        (field (name "TOLERANCE") "±20 %")
        (field (name "VOLTAGE") "50.0 V")
      )
      (libsource (lib "eagle-import") (part "C-EU-C1210-4U7-50V"))
    )
    (comp (ref "C112")
      (value "4u7 50V")
      (footprint "eagle-import:C1210")
      (fields
        (field (name "MANUFACTURER") "Taiyo Yuden")
        (field (name "TOLERANCE") "±20 %")
        (field (name "VOLTAGE") "50.0 V")
      )
      (libsource (lib "eagle-import") (part "C-EU-C1210-4U7-50V"))
    )
    (comp (ref "C113")
      (value "C-EU-C0603")
      (footprint "eagle-import:C0603")
      (fields (field (name "TOLERANCE") "±20 %") (field (name "VOLTAGE") "50.0 V"))
      (libsource (lib "eagle-import") (part "C-EU-C0603"))
    )
    (comp (ref "C114")
      (value "4u7 50V")
      (footprint "eagle-import:C1210")
      (fields
        (field (name "MANUFACTURER") "Taiyo Yuden")
        (field (name "TOLERANCE") "±20 %")
        (field (name "VOLTAGE") "50.0 V")
      )
      (libsource (lib "eagle-import") (part "C-EU-C1210-4U7-50V"))
    )
    (comp (ref "C115")
      (value "875115252003")
      (footprint "eagle-import:WCAP-PSHP_8.0X8.7_WE")
      (fields
        (field (name "MANUFACTURER") "Wuerth")
        (field (name "TOLERANCE") "±20 %")
        (field (name "VOLTAGE") "10.0 V")
      )
      (libsource (lib "eagle-import") (part "875115252003"))
    )
    (comp (ref "C116")
      (value "22u 10V")
      (footprint "eagle-import:C0805")
      (fields
        (field (name "MANUFACTURER") "AVX")
        (field (name "TOLERANCE") "±20 %")
        (field (name "VOLTAGE") "10.0 V")
      )
      (libsource (lib "eagle-import") (part "C-EU-C0805-22U"))
    )
    (comp (ref "C117")
      (value "875115252003")
      (footprint "eagle-import:WCAP-PSHP_8.0X8.7_WE")
      (fields
        (field (name "MANUFACTURER") "Wuerth")
        (field (name "TOLERANCE") "±20 %")
        (field (name "VOLTAGE") "10.0 V")
      )
      (libsource (lib "eagle-import") (part "875115252003"))
    )
    (comp (ref "C118")
      (value "875115252003")
      (footprint "eagle-import:WCAP-PSHP_8.0X8.7_WE")
      (fields
        (field (name "MANUFACTURER") "Wuerth")
        (field (name "TOLERANCE") "±20 %")
        (field (name "VOLTAGE") "10.0 V")
      )
      (libsource (lib "eagle-import") (part "875115252003"))
    )
    (comp (ref "C119")
      (value "22u 10V")
      (footprint "eagle-import:C0805")
      (fields
        (field (name "MANUFACTURER") "AVX")
        (field (name "TOLERANCE") "±20 %")
        (field (name "VOLTAGE") "10.0 V")
      )
      (libsource (lib "eagle-import") (part "C-EU-C0805-22U"))
    )
    (comp (ref "C120")
      (value "C-EU-C0603")
      (footprint "eagle-import:C0603")
      (fields (field (name "TOLERANCE") "±20 %") (field (name "VOLTAGE") "50.0 V"))
      (libsource (lib "eagle-import") (part "C-EU-C0603"))
    )
    (comp (ref "C121")
      (value "100n 50V")
      (footprint "eagle-import:C0603")
      (fields
        (field (name "MANUFACTURER") "AVX")
        (field (name "TOLERANCE") "±20 %")
        (field (name "VOLTAGE") "50.0 V")
      )
      (libsource (lib "eagle-import") (part "C-EU-C0603-100N"))
    )
    (comp (ref "C122")
      (value "100n 50V")
      (footprint "eagle-import:C0603")
      (fields
        (field (name "MANUFACTURER") "AVX")
        (field (name "TOLERANCE") "±20 %")
        (field (name "VOLTAGE") "50.0 V")
      )
      (libsource (lib "eagle-import") (part "C-EU-C0603-100N"))
    )
    (comp (ref "C123")
      (value "100n 50V")
      (footprint "eagle-import:C0603")
      (fields
        (field (name "MANUFACTURER") "AVX")
        (field (name "TOLERANCE") "±20 %")
        (field (name "VOLTAGE") "50.0 V")
      )
      (libsource (lib "eagle-import") (part "C-EU-C0603-100N"))
    )
    (comp (ref "C124")
      (value "100n 50V")
      (footprint "eagle-import:C0603")
      (fields
        (field (name "MANUFACTURER") "AVX")
        (field (name "TOLERANCE") "±20 %")
        (field (name "VOLTAGE") "50.0 V")
      )
      (libsource (lib "eagle-import") (part "C-EU-C0603-100N"))
    )
    (comp (ref "C125")
      (value "1u 25V")
      (footprint "eagle-import:C0805")
      (fields
        (field (name "MANUFACTURER") "AVX")
        (field (name "TOLERANCE") "±20 %")
        (field (name "VOLTAGE") "25.0 V")
      )
      (libsource (lib "eagle-import") (part "C-EU-C0805-1U"))
    )
    (comp (ref "C126")
      (value "1u 25V")
      (footprint "eagle-import:C0805")
      (fields
        (field (name "MANUFACTURER") "AVX")
        (field (name "TOLERANCE") "±20 %")
        (field (name "VOLTAGE") "25.0 V")
      )
      (libsource (lib "eagle-import") (part "C-EU-C0805-1U"))
    )
    (comp (ref "C127")
      (value "10u 50V")
      (footprint "eagle-import:C1206")
      (fields
        (field (name "MANUFACTURER") "Samsung")
        (field (name "TOLERANCE") "±20 %")
        (field (name "VOLTAGE") "50.0 V")
      )
      (libsource (lib "eagle-import") (part "C-EU-C1206-10U"))
    )
    (comp (ref "C128")
      (value "10u 50V")
      (footprint "eagle-import:C1206")
      (fields
        (field (name "MANUFACTURER") "Samsung")
        (field (name "TOLERANCE") "±20 %")
        (field (name "VOLTAGE") "50.0 V")
      )
      (libsource (lib "eagle-import") (part "C-EU-C1206-10U"))
    )
    (comp (ref "C129")
      (value "1u 25V")
      (footprint "eagle-import:C0805")
      (fields
        (field (name "MANUFACTURER") "AVX")
        (field (name "TOLERANCE") "±20 %")
        (field (name "VOLTAGE") "25.0 V")
      )
      (libsource (lib "eagle-import") (part "C-EU-C0805-1U"))
    )
    (comp (ref "C130")
      (value "22u 10V")
      (footprint "eagle-import:C0805")
      (fields
        (field (name "MANUFACTURER") "AVX")
        (field (name "TOLERANCE") "±20 %")
        (field (name "VOLTAGE") "10.0 V")
      )
      (libsource (lib "eagle-import") (part "C-EU-C0805-22U"))
    )
    (comp (ref "C131")
      (value "1u 25V")
      (footprint "eagle-import:C0805")
      (fields
        (field (name "MANUFACTURER") "AVX")
        (field (name "TOLERANCE") "±20 %")
        (field (name "VOLTAGE") "25.0 V")
      )
      (libsource (lib "eagle-import") (part "C-EU-C0805-1U"))
    )
    (comp (ref "C132")
      (value "4u7 16V")
      (footprint "eagle-import:C0805")
      (fields
        (field (name "MANUFACTURER") "AVX")
        (field (name "TOLERANCE") "±20 %")
        (field (name "VOLTAGE") "16.0 V")
      )
      (libsource (lib "eagle-import") (part "C-EU-C0805-4U7"))
    )
    (comp (ref "C133")
      (value "100n 50V")
      (footprint "eagle-import:C0603")
      (fields
        (field (name "MANUFACTURER") "AVX")
        (field (name "TOLERANCE") "±20 %")
        (field (name "VOLTAGE") "50.0 V")
      )
      (libsource (lib "eagle-import") (part "C-EU-C0603-100N"))
    )
    (comp (ref "C134")
      (value "4u7 16V")
      (footprint "eagle-import:C0805")
      (fields
        (field (name "MANUFACTURER") "AVX")
        (field (name "TOLERANCE") "±20 %")
        (field (name "VOLTAGE") "16.0 V")
      )
      (libsource (lib "eagle-import") (part "C-EU-C0805-4U7"))
    )
    (comp (ref "C135")
      (value "220p 25V")
      (footprint "eagle-import:C0402")
      (fields
        (field (name "MANUFACTURER") "Wuerth")
        (field (name "TOLERANCE") "±10 %")
        (field (name "VOLTAGE") "25.0 V")
      )
      (libsource (lib "eagle-import") (part "C-EU-C0402-220P"))
    )
    (comp (ref "C136")
      (value "4u7 16V")
      (footprint "eagle-import:C0805")
      (fields
        (field (name "MANUFACTURER") "AVX")
        (field (name "TOLERANCE") "±20 %")
        (field (name "VOLTAGE") "16.0 V")
      )
      (libsource (lib "eagle-import") (part "C-EU-C0805-4U7"))
    )
    (comp (ref "C137")
      (value "100n 50V")
      (footprint "eagle-import:C0603")
      (fields
        (field (name "MANUFACTURER") "AVX")
        (field (name "TOLERANCE") "±20 %")
        (field (name "VOLTAGE") "50.0 V")
      )
      (libsource (lib "eagle-import") (part "C-EU-C0603-100N"))
    )
    (comp (ref "C138")
      (value "27p 50V")
      (footprint "eagle-import:C0603")
      (fields
        (field (name "MANUFACTURER") "AVX")
        (field (name "TOLERANCE") "±20 %")
        (field (name "VOLTAGE") "50.0 V")
      )
      (libsource (lib "eagle-import") (part "C-EU-C0603-27P"))
    )
    (comp (ref "C140")
      (value "22u 10V")
      (footprint "eagle-import:C0805")
      (fields
        (field (name "MANUFACTURER") "AVX")
        (field (name "TOLERANCE") "±20 %")
        (field (name "VOLTAGE") "10.0 V")
      )
      (libsource (lib "eagle-import") (part "C-EU-C0805-22U"))
    )
    (comp (ref "C141")
      (value "100n 50V")
      (footprint "eagle-import:C0603")
      (fields
        (field (name "MANUFACTURER") "AVX")
        (field (name "TOLERANCE") "±20 %")
        (field (name "VOLTAGE") "50.0 V")
      )
      (libsource (lib "eagle-import") (part "C-EU-C0603-100N"))
    )
    (comp (ref "C142")
      (value "C-EU-C0603")
      (footprint "eagle-import:C0603")
      (fields (field (name "TOLERANCE") "±20 %") (field (name "VOLTAGE") "50.0 V"))
      (libsource (lib "eagle-import") (part "C-EU-C0603"))
    )
    (comp (ref "C143")
      (value "220p 25V")
      (footprint "eagle-import:C0402")
      (fields
        (field (name "MANUFACTURER") "Wuerth")
        (field (name "TOLERANCE") "±10 %")
        (field (name "VOLTAGE") "25.0 V")
      )
      (libsource (lib "eagle-import") (part "C-EU-C0402-220P"))
    )
    (comp (ref "C144")
      (value "100n 16V")
      (footprint "eagle-import:C0402")
      (fields
        (field (name "MANUFACTURER") "KEMET")
        (field (name "TOLERANCE") "±20 %")
        (field (name "VOLTAGE") "16.0 V")
      )
      (libsource (lib "eagle-import") (part "C-EU-C0402-100N"))
    )
    (comp (ref "C145")
      (value "100n 16V")
      (footprint "eagle-import:C0402")
      (fields
        (field (name "MANUFACTURER") "KEMET")
        (field (name "TOLERANCE") "±20 %")
        (field (name "VOLTAGE") "16.0 V")
      )
      (libsource (lib "eagle-import") (part "C-EU-C0402-100N"))
    )
    (comp (ref "C146")
      (value "100n 50V")
      (footprint "eagle-import:C0603")
      (fields
        (field (name "MANUFACTURER") "AVX")
        (field (name "TOLERANCE") "±20 %")
        (field (name "VOLTAGE") "50.0 V")
      )
      (libsource (lib "eagle-import") (part "C-EU-C0603-100N"))
    )
    (comp (ref "C147")
      (value "22u 10V")
      (footprint "eagle-import:C0805")
      (fields
        (field (name "MANUFACTURER") "AVX")
        (field (name "TOLERANCE") "±20 %")
        (field (name "VOLTAGE") "10.0 V")
      )
      (libsource (lib "eagle-import") (part "C-EU-C0805-22U"))
    )
    (comp (ref "C148")
      (value "875115252003")
      (footprint "eagle-import:WCAP-PSHP_8.0X8.7_WE")
      (fields
        (field (name "MANUFACTURER") "Wuerth")
        (field (name "TOLERANCE") "±20 %")
        (field (name "VOLTAGE") "10.0 V")
      )
      (libsource (lib "eagle-import") (part "875115252003"))
    )
    (comp (ref "C149")
      (value "100n 50V")
      (footprint "eagle-import:C0603")
      (fields
        (field (name "MANUFACTURER") "AVX")
        (field (name "TOLERANCE") "±20 %")
        (field (name "VOLTAGE") "50.0 V")
      )
      (libsource (lib "eagle-import") (part "C-EU-C0603-100N"))
    )
    (comp (ref "C150")
      (value "100n 50V")
      (footprint "eagle-import:C0603")
      (fields
        (field (name "MANUFACTURER") "AVX")
        (field (name "TOLERANCE") "±20 %")
        (field (name "VOLTAGE") "50.0 V")
      )
      (libsource (lib "eagle-import") (part "C-EU-C0603-100N"))
    )
    (comp (ref "C151")
      (value "4u7 50V")
      (footprint "eagle-import:C1210")
      (fields
        (field (name "MANUFACTURER") "Taiyo Yuden")
        (field (name "TOLERANCE") "±20 %")
        (field (name "VOLTAGE") "50.0 V")
      )
      (libsource (lib "eagle-import") (part "C-EU-C1210-4U7-50V"))
    )
    (comp (ref "C152")
      (value "4u7 50V")
      (footprint "eagle-import:C1210")
      (fields
        (field (name "MANUFACTURER") "Taiyo Yuden")
        (field (name "TOLERANCE") "±20 %")
        (field (name "VOLTAGE") "50.0 V")
      )
      (libsource (lib "eagle-import") (part "C-EU-C1210-4U7-50V"))
    )
    (comp (ref "C153")
      (value "4u7 50V")
      (footprint "eagle-import:C1210")
      (fields
        (field (name "MANUFACTURER") "Taiyo Yuden")
        (field (name "TOLERANCE") "±20 %")
        (field (name "VOLTAGE") "50.0 V")
      )
      (libsource (lib "eagle-import") (part "C-EU-C1210-4U7-50V"))
    )
    (comp (ref "C154")
      (value "100n 50V")
      (footprint "eagle-import:C0603")
      (fields
        (field (name "MANUFACTURER") "AVX")
        (field (name "TOLERANCE") "±20 %")
        (field (name "VOLTAGE") "50.0 V")
      )
      (libsource (lib "eagle-import") (part "C-EU-C0603-100N"))
    )
    (comp (ref "C155")
      (value "100n 50V")
      (footprint "eagle-import:C0603")
      (fields
        (field (name "MANUFACTURER") "AVX")
        (field (name "TOLERANCE") "±20 %")
        (field (name "VOLTAGE") "50.0 V")
      )
      (libsource (lib "eagle-import") (part "C-EU-C0603-100N"))
    )
    (comp (ref "C156")
      (value "100n 50V")
      (footprint "eagle-import:C0603")
      (fields
        (field (name "MANUFACTURER") "AVX")
        (field (name "TOLERANCE") "±20 %")
        (field (name "VOLTAGE") "50.0 V")
      )
      (libsource (lib "eagle-import") (part "C-EU-C0603-100N"))
    )
    (comp (ref "C157")
      (value "100n 50V")
      (footprint "eagle-import:C0603")
      (fields
        (field (name "MANUFACTURER") "AVX")
        (field (name "TOLERANCE") "±20 %")
        (field (name "VOLTAGE") "50.0 V")
      )
      (libsource (lib "eagle-import") (part "C-EU-C0603-100N"))
    )
    (comp (ref "C158")
      (value "100n 50V")
      (footprint "eagle-import:C0603")
      (fields
        (field (name "MANUFACTURER") "AVX")
        (field (name "TOLERANCE") "±20 %")
        (field (name "VOLTAGE") "50.0 V")
      )
      (libsource (lib "eagle-import") (part "C-EU-C0603-100N"))
    )
    (comp (ref "C159")
      (value "100n 50V")
      (footprint "eagle-import:C0603")
      (fields
        (field (name "MANUFACTURER") "AVX")
        (field (name "TOLERANCE") "±20 %")
        (field (name "VOLTAGE") "50.0 V")
      )
      (libsource (lib "eagle-import") (part "C-EU-C0603-100N"))
    )
    (comp (ref "C160")
      (value "100n 50V")
      (footprint "eagle-import:C0603")
      (fields
        (field (name "MANUFACTURER") "AVX")
        (field (name "TOLERANCE") "±20 %")
        (field (name "VOLTAGE") "50.0 V")
      )
      (libsource (lib "eagle-import") (part "C-EU-C0603-100N"))
    )
    (comp (ref "C161")
      (value "100n 50V")
      (footprint "eagle-import:C0603")
      (fields
        (field (name "MANUFACTURER") "AVX")
        (field (name "TOLERANCE") "±20 %")
        (field (name "VOLTAGE") "50.0 V")
      )
      (libsource (lib "eagle-import") (part "C-EU-C0603-100N"))
    )
    (comp (ref "C162")
      (value "27p 50V")
      (footprint "eagle-import:C0603")
      (fields
        (field (name "MANUFACTURER") "AVX")
        (field (name "TOLERANCE") "±20 %")
        (field (name "VOLTAGE") "50.0 V")
      )
      (libsource (lib "eagle-import") (part "C-EU-C0603-27P"))
    )
    (comp (ref "C163")
      (value "27p 50V")
      (footprint "eagle-import:C0603")
      (fields
        (field (name "MANUFACTURER") "AVX")
        (field (name "TOLERANCE") "±20 %")
        (field (name "VOLTAGE") "50.0 V")
      )
      (libsource (lib "eagle-import") (part "C-EU-C0603-27P"))
    )
    (comp (ref "C164")
      (value "100n 50V")
      (footprint "eagle-import:C0603")
      (fields
        (field (name "MANUFACTURER") "AVX")
        (field (name "TOLERANCE") "±20 %")
        (field (name "VOLTAGE") "50.0 V")
      )
      (libsource (lib "eagle-import") (part "C-EU-C0603-100N"))
    )
    (comp (ref "C165")
      (value "22u 10V")
      (footprint "eagle-import:C0805")
      (fields
        (field (name "MANUFACTURER") "AVX")
        (field (name "TOLERANCE") "±20 %")
        (field (name "VOLTAGE") "10.0 V")
      )
      (libsource (lib "eagle-import") (part "C-EU-C0805-22U"))
    )
    (comp (ref "C166")
      (value "4u7 50V")
      (footprint "eagle-import:C1210")
      (fields
        (field (name "MANUFACTURER") "Taiyo Yuden")
        (field (name "TOLERANCE") "±20 %")
        (field (name "VOLTAGE") "50.0 V")
      )
      (libsource (lib "eagle-import") (part "C-EU-C1210-4U7-50V"))
    )
    (comp (ref "C167")
      (value "C-EU-C0603")
      (footprint "eagle-import:C0603")
      (fields (field (name "TOLERANCE") "±20 %") (field (name "VOLTAGE") "50.0 V"))
      (libsource (lib "eagle-import") (part "C-EU-C0603"))
    )
    (comp (ref "C168")
      (value "100n 50V")
      (footprint "eagle-import:C0603")
      (fields
        (field (name "MANUFACTURER") "AVX")
        (field (name "TOLERANCE") "±20 %")
        (field (name "VOLTAGE") "50.0 V")
      )
      (libsource (lib "eagle-import") (part "C-EU-C0603-100N"))
    )
    (comp (ref "C169")
      (value "1u 25V")
      (footprint "eagle-import:C0805")
      (fields
        (field (name "MANUFACTURER") "AVX")
        (field (name "TOLERANCE") "±20 %")
        (field (name "VOLTAGE") "25.0 V")
      )
      (libsource (lib "eagle-import") (part "C-EU-C0805-1U"))
    )
    (comp (ref "C170")
      (value "1u 25V")
      (footprint "eagle-import:C0805")
      (fields
        (field (name "MANUFACTURER") "AVX")
        (field (name "TOLERANCE") "±20 %")
        (field (name "VOLTAGE") "25.0 V")
      )
      (libsource (lib "eagle-import") (part "C-EU-C0805-1U"))
    )
    (comp (ref "C171")
      (value "1u 25V")
      (footprint "eagle-import:C0805")
      (fields
        (field (name "MANUFACTURER") "AVX")
        (field (name "TOLERANCE") "±20 %")
        (field (name "VOLTAGE") "25.0 V")
      )
      (libsource (lib "eagle-import") (part "C-EU-C0805-1U"))
    )
    (comp (ref "C172")
      (value "10n 50V")
      (footprint "eagle-import:C0603")
      (fields
        (field (name "MANUFACTURER") "Samsung")
        (field (name "TOLERANCE") "±20 %")
        (field (name "VOLTAGE") "50.0 V")
      )
      (libsource (lib "eagle-import") (part "C-EU-C0603-10N"))
    )
    (comp (ref "C174")
      (value "850617022001")
      (footprint "eagle-import:WCAP-STSC_16.0X25.0_WE")
      (fields
        (field (name "MANUFACTURER") "Wuerth")
        (field (name "TOLERANCE") "+30%/-10%")
        (field (name "VOLTAGE") "2.7 V")
      )
      (libsource (lib "eagle-import") (part "850617022001"))
    )
    (comp (ref "C175")
      (value "850617022001")
      (footprint "eagle-import:WCAP-STSC_16.0X25.0_WE")
      (fields
        (field (name "MANUFACTURER") "Wuerth")
        (field (name "TOLERANCE") "+30%/-10%")
        (field (name "VOLTAGE") "2.7 V")
      )
      (libsource (lib "eagle-import") (part "850617022001"))
    )
    (comp (ref "C176")
      (value "850617022001")
      (footprint "eagle-import:WCAP-STSC_16.0X25.0_WE")
      (fields
        (field (name "MANUFACTURER") "Wuerth")
        (field (name "TOLERANCE") "+30%/-10%")
        (field (name "VOLTAGE") "2.7 V")
      )
      (libsource (lib "eagle-import") (part "850617022001"))
    )
    (comp (ref "C177")
      (value "850617022001")
      (footprint "eagle-import:WCAP-STSC_16.0X25.0_WE")
      (fields
        (field (name "MANUFACTURER") "Wuerth")
        (field (name "TOLERANCE") "+30%/-10%")
        (field (name "VOLTAGE") "2.7 V")
      )
      (libsource (lib "eagle-import") (part "850617022001"))
    )
    (comp (ref "C178")
      (value "850617022001")
      (footprint "eagle-import:WCAP-STSC_16.0X25.0_WE")
      (fields
        (field (name "MANUFACTURER") "Wuerth")
        (field (name "TOLERANCE") "+30%/-10%")
        (field (name "VOLTAGE") "2.7 V")
      )
      (libsource (lib "eagle-import") (part "850617022001"))
    )
    (comp (ref "C179")
      (value "4u7 50V")
      (footprint "eagle-import:C1210")
      (fields
        (field (name "MANUFACTURER") "Taiyo Yuden")
        (field (name "TOLERANCE") "±20 %")
        (field (name "VOLTAGE") "50.0 V")
      )
      (libsource (lib "eagle-import") (part "C-EU-C1210-4U7-50V"))
    )
    (comp (ref "C180")
      (value "4u7 50V")
      (footprint "eagle-import:C1210")
      (fields
        (field (name "MANUFACTURER") "Taiyo Yuden")
        (field (name "TOLERANCE") "±20 %")
        (field (name "VOLTAGE") "50.0 V")
      )
      (libsource (lib "eagle-import") (part "C-EU-C1210-4U7-50V"))
    )
    (comp (ref "C181")
      (value "4u7 50V")
      (footprint "eagle-import:C1210")
      (fields
        (field (name "MANUFACTURER") "Taiyo Yuden")
        (field (name "TOLERANCE") "±20 %")
        (field (name "VOLTAGE") "50.0 V")
      )
      (libsource (lib "eagle-import") (part "C-EU-C1210-4U7-50V"))
    )
    (comp (ref "C182")
      (value "4u7 50V")
      (footprint "eagle-import:C1210")
      (fields
        (field (name "MANUFACTURER") "Taiyo Yuden")
        (field (name "TOLERANCE") "±20 %")
        (field (name "VOLTAGE") "50.0 V")
      )
      (libsource (lib "eagle-import") (part "C-EU-C1210-4U7-50V"))
    )
    (comp (ref "C183")
      (value "4u7 50V")
      (footprint "eagle-import:C1210")
      (fields
        (field (name "MANUFACTURER") "Taiyo Yuden")
        (field (name "TOLERANCE") "±20 %")
        (field (name "VOLTAGE") "50.0 V")
      )
      (libsource (lib "eagle-import") (part "C-EU-C1210-4U7-50V"))
    )
    (comp (ref "C184")
      (value "10n 50V")
      (footprint "eagle-import:C0603")
      (fields
        (field (name "MANUFACTURER") "Samsung")
        (field (name "TOLERANCE") "±20 %")
        (field (name "VOLTAGE") "50.0 V")
      )
      (libsource (lib "eagle-import") (part "C-EU-C0603-10N"))
    )
    (comp (ref "C185")
      (value "4u7 50V")
      (footprint "eagle-import:C1210")
      (fields
        (field (name "MANUFACTURER") "Taiyo Yuden")
        (field (name "TOLERANCE") "±20 %")
        (field (name "VOLTAGE") "50.0 V")
      )
      (libsource (lib "eagle-import") (part "C-EU-C1210-4U7-50V"))
    )
    (comp (ref "C187")
      (value "100n 50V")
      (footprint "eagle-import:C0603")
      (fields
        (field (name "MANUFACTURER") "AVX")
        (field (name "TOLERANCE") "±20 %")
        (field (name "VOLTAGE") "50.0 V")
      )
      (libsource (lib "eagle-import") (part "C-EU-C0603-100N"))
    )
    (comp (ref "C188")
      (value "100n 50V")
      (footprint "eagle-import:C0603")
      (fields
        (field (name "MANUFACTURER") "AVX")
        (field (name "TOLERANCE") "±20 %")
        (field (name "VOLTAGE") "50.0 V")
      )
      (libsource (lib "eagle-import") (part "C-EU-C0603-100N"))
    )
    (comp (ref "C189")
      (value "100n 50V")
      (footprint "eagle-import:C0603")
      (fields
        (field (name "MANUFACTURER") "AVX")
        (field (name "TOLERANCE") "±20 %")
        (field (name "VOLTAGE") "50.0 V")
      )
      (libsource (lib "eagle-import") (part "C-EU-C0603-100N"))
    )
    (comp (ref "C190")
      (value "100n 50V")
      (footprint "eagle-import:C0603")
      (fields
        (field (name "MANUFACTURER") "AVX")
        (field (name "TOLERANCE") "±20 %")
        (field (name "VOLTAGE") "50.0 V")
      )
      (libsource (lib "eagle-import") (part "C-EU-C0603-100N"))
    )
    (comp (ref "C191")
      (value "100n 50V")
      (footprint "eagle-import:C0603")
      (fields
        (field (name "MANUFACTURER") "AVX")
        (field (name "TOLERANCE") "±20 %")
        (field (name "VOLTAGE") "50.0 V")
      )
      (libsource (lib "eagle-import") (part "C-EU-C0603-100N"))
    )
    (comp (ref "C192")
      (value "100n 50V")
      (footprint "eagle-import:C0603")
      (fields
        (field (name "MANUFACTURER") "AVX")
        (field (name "TOLERANCE") "±20 %")
        (field (name "VOLTAGE") "50.0 V")
      )
      (libsource (lib "eagle-import") (part "C-EU-C0603-100N"))
    )
    (comp (ref "C193")
      (value "22u 10V")
      (footprint "eagle-import:C0805")
      (fields
        (field (name "MANUFACTURER") "AVX")
        (field (name "TOLERANCE") "±20 %")
        (field (name "VOLTAGE") "10.0 V")
      )
      (libsource (lib "eagle-import") (part "C-EU-C0805-22U"))
    )
    (comp (ref "C194")
      (value "100n 50V")
      (footprint "eagle-import:C0603")
      (fields
        (field (name "MANUFACTURER") "AVX")
        (field (name "TOLERANCE") "±20 %")
        (field (name "VOLTAGE") "50.0 V")
      )
      (libsource (lib "eagle-import") (part "C-EU-C0603-100N"))
    )
    (comp (ref "C195")
      (value "860080678021")
      (footprint "eagle-import:WCAP-ATLI_13.0X25.0_WE")
      (fields
        (field (name "MANUFACTURER") "Wuerth")
        (field (name "TOLERANCE") "±20 %")
        (field (name "VOLTAGE") "50.0 V")
      )
      (libsource (lib "eagle-import") (part "860080678021"))
    )
    (comp (ref "C196")
      (value "100n 50V")
      (footprint "eagle-import:C0603")
      (fields
        (field (name "MANUFACTURER") "AVX")
        (field (name "TOLERANCE") "±20 %")
        (field (name "VOLTAGE") "50.0 V")
      )
      (libsource (lib "eagle-import") (part "C-EU-C0603-100N"))
    )
    (comp (ref "C197")
      (value "100n 50V")
      (footprint "eagle-import:C0603")
      (fields
        (field (name "MANUFACTURER") "AVX")
        (field (name "TOLERANCE") "±20 %")
        (field (name "VOLTAGE") "50.0 V")
      )
      (libsource (lib "eagle-import") (part "C-EU-C0603-100N"))
    )
    (comp (ref "C198")
      (value "100n 50V")
      (footprint "eagle-import:C0603")
      (fields
        (field (name "MANUFACTURER") "AVX")
        (field (name "TOLERANCE") "±20 %")
        (field (name "VOLTAGE") "50.0 V")
      )
      (libsource (lib "eagle-import") (part "C-EU-C0603-100N"))
    )
    (comp (ref "C199")
      (value "100n 50V")
      (footprint "eagle-import:C0603")
      (fields
        (field (name "MANUFACTURER") "AVX")
        (field (name "TOLERANCE") "±20 %")
        (field (name "VOLTAGE") "50.0 V")
      )
      (libsource (lib "eagle-import") (part "C-EU-C0603-100N"))
    )
    (comp (ref "C200")
      (value "100n 50V")
      (footprint "eagle-import:C0603")
      (fields
        (field (name "MANUFACTURER") "AVX")
        (field (name "TOLERANCE") "±20 %")
        (field (name "VOLTAGE") "50.0 V")
      )
      (libsource (lib "eagle-import") (part "C-EU-C0603-100N"))
    )
    (comp (ref "C201")
      (value "100n 50V")
      (footprint "eagle-import:C0603")
      (fields
        (field (name "MANUFACTURER") "AVX")
        (field (name "TOLERANCE") "±20 %")
        (field (name "VOLTAGE") "50.0 V")
      )
      (libsource (lib "eagle-import") (part "C-EU-C0603-100N"))
    )
    (comp (ref "C202")
      (value "100n 50V")
      (footprint "eagle-import:C0603")
      (fields
        (field (name "MANUFACTURER") "AVX")
        (field (name "TOLERANCE") "±20 %")
        (field (name "VOLTAGE") "50.0 V")
      )
      (libsource (lib "eagle-import") (part "C-EU-C0603-100N"))
    )
    (comp (ref "C203")
      (value "100n 50V")
      (footprint "eagle-import:C0603")
      (fields
        (field (name "MANUFACTURER") "AVX")
        (field (name "TOLERANCE") "±20 %")
        (field (name "VOLTAGE") "50.0 V")
      )
      (libsource (lib "eagle-import") (part "C-EU-C0603-100N"))
    )
    (comp (ref "C204")
      (value "100n 50V")
      (footprint "eagle-import:C0603")
      (fields
        (field (name "MANUFACTURER") "AVX")
        (field (name "TOLERANCE") "±20 %")
        (field (name "VOLTAGE") "50.0 V")
      )
      (libsource (lib "eagle-import") (part "C-EU-C0603-100N"))
    )
    (comp (ref "C205")
      (value "1u 25V")
      (footprint "eagle-import:C0805")
      (fields
        (field (name "MANUFACTURER") "AVX")
        (field (name "TOLERANCE") "±20 %")
        (field (name "VOLTAGE") "25.0 V")
      )
      (libsource (lib "eagle-import") (part "C-EU-C0805-1U"))
    )
    (comp (ref "C206")
      (value "4u7 50V")
      (footprint "eagle-import:C1210")
      (fields
        (field (name "MANUFACTURER") "Taiyo Yuden")
        (field (name "TOLERANCE") "±20 %")
        (field (name "VOLTAGE") "50.0 V")
      )
      (libsource (lib "eagle-import") (part "C-EU-C1210-4U7-50V"))
    )
    (comp (ref "C207")
      (value "100n 50V")
      (footprint "eagle-import:C0603")
      (fields
        (field (name "MANUFACTURER") "AVX")
        (field (name "TOLERANCE") "±20 %")
        (field (name "VOLTAGE") "50.0 V")
      )
      (libsource (lib "eagle-import") (part "C-EU-C0603-100N"))
    )
    (comp (ref "C208")
      (value "1u 25V")
      (footprint "eagle-import:C0805")
      (fields
        (field (name "MANUFACTURER") "AVX")
        (field (name "TOLERANCE") "±20 %")
        (field (name "VOLTAGE") "25.0 V")
      )
      (libsource (lib "eagle-import") (part "C-EU-C0805-1U"))
    )
    (comp (ref "C209")
      (value "4u7 50V")
      (footprint "eagle-import:C1210")
      (fields
        (field (name "MANUFACTURER") "Taiyo Yuden")
        (field (name "TOLERANCE") "±20 %")
        (field (name "VOLTAGE") "50.0 V")
      )
      (libsource (lib "eagle-import") (part "C-EU-C1210-4U7-50V"))
    )
    (comp (ref "C210")
      (value "4u7 50V")
      (footprint "eagle-import:C1210")
      (fields
        (field (name "MANUFACTURER") "Taiyo Yuden")
        (field (name "TOLERANCE") "±20 %")
        (field (name "VOLTAGE") "50.0 V")
      )
      (libsource (lib "eagle-import") (part "C-EU-C1210-4U7-50V"))
    )
    (comp (ref "C211")
      (value "4u7 50V")
      (footprint "eagle-import:C1210")
      (fields
        (field (name "MANUFACTURER") "Taiyo Yuden")
        (field (name "TOLERANCE") "±20 %")
        (field (name "VOLTAGE") "50.0 V")
      )
      (libsource (lib "eagle-import") (part "C-EU-C1210-4U7-50V"))
    )
    (comp (ref "C212")
      (value "100n 50V")
      (footprint "eagle-import:C0603")
      (fields
        (field (name "MANUFACTURER") "AVX")
        (field (name "TOLERANCE") "±20 %")
        (field (name "VOLTAGE") "50.0 V")
      )
      (libsource (lib "eagle-import") (part "C-EU-C0603-100N"))
    )
    (comp (ref "C213")
      (value "100n 50V")
      (footprint "eagle-import:C0603")
      (fields
        (field (name "MANUFACTURER") "AVX")
        (field (name "TOLERANCE") "±20 %")
        (field (name "VOLTAGE") "50.0 V")
      )
      (libsource (lib "eagle-import") (part "C-EU-C0603-100N"))
    )
    (comp (ref "C214")
      (value "1u 25V")
      (footprint "eagle-import:C0805")
      (fields
        (field (name "MANUFACTURER") "AVX")
        (field (name "TOLERANCE") "±20 %")
        (field (name "VOLTAGE") "25.0 V")
      )
      (libsource (lib "eagle-import") (part "C-EU-C0805-1U"))
    )
    (comp (ref "C215")
      (value "1u 25V")
      (footprint "eagle-import:C0805")
      (fields
        (field (name "MANUFACTURER") "AVX")
        (field (name "TOLERANCE") "±20 %")
        (field (name "VOLTAGE") "25.0 V")
      )
      (libsource (lib "eagle-import") (part "C-EU-C0805-1U"))
    )
    (comp (ref "C216")
      (value "100n 50V")
      (footprint "eagle-import:C0603")
      (fields
        (field (name "MANUFACTURER") "AVX")
        (field (name "TOLERANCE") "±20 %")
        (field (name "VOLTAGE") "50.0 V")
      )
      (libsource (lib "eagle-import") (part "C-EU-C0603-100N"))
    )
    (comp (ref "C217")
      (value "100n 50V")
      (footprint "eagle-import:C0603")
      (fields
        (field (name "MANUFACTURER") "AVX")
        (field (name "TOLERANCE") "±20 %")
        (field (name "VOLTAGE") "50.0 V")
      )
      (libsource (lib "eagle-import") (part "C-EU-C0603-100N"))
    )
    (comp (ref "C218")
      (value "100n 50V")
      (footprint "eagle-import:C0603")
      (fields
        (field (name "MANUFACTURER") "AVX")
        (field (name "TOLERANCE") "±20 %")
        (field (name "VOLTAGE") "50.0 V")
      )
      (libsource (lib "eagle-import") (part "C-EU-C0603-100N"))
    )
    (comp (ref "C219")
      (value "22u 10V")
      (footprint "eagle-import:C0805")
      (fields
        (field (name "MANUFACTURER") "AVX")
        (field (name "TOLERANCE") "±20 %")
        (field (name "VOLTAGE") "10.0 V")
      )
      (libsource (lib "eagle-import") (part "C-EU-C0805-22U"))
    )
    (comp (ref "C220")
      (value "22u 10V")
      (footprint "eagle-import:C0805")
      (fields
        (field (name "MANUFACTURER") "AVX")
        (field (name "TOLERANCE") "±20 %")
        (field (name "VOLTAGE") "10.0 V")
      )
      (libsource (lib "eagle-import") (part "C-EU-C0805-22U"))
    )
    (comp (ref "C221")
      (value "100n 50V")
      (footprint "eagle-import:C0603")
      (fields
        (field (name "MANUFACTURER") "AVX")
        (field (name "TOLERANCE") "±20 %")
        (field (name "VOLTAGE") "50.0 V")
      )
      (libsource (lib "eagle-import") (part "C-EU-C0603-100N"))
    )
    (comp (ref "C222")
      (value "22u 10V")
      (footprint "eagle-import:C0805")
      (fields
        (field (name "MANUFACTURER") "AVX")
        (field (name "TOLERANCE") "±20 %")
        (field (name "VOLTAGE") "10.0 V")
      )
      (libsource (lib "eagle-import") (part "C-EU-C0805-22U"))
    )
    (comp (ref "C223")
      (value "22u 10V")
      (footprint "eagle-import:C0805")
      (fields
        (field (name "MANUFACTURER") "AVX")
        (field (name "TOLERANCE") "±20 %")
        (field (name "VOLTAGE") "10.0 V")
      )
      (libsource (lib "eagle-import") (part "C-EU-C0805-22U"))
    )
    (comp (ref "C224")
      (value "10n 50V")
      (footprint "eagle-import:C0603")
      (fields
        (field (name "MANUFACTURER") "Samsung")
        (field (name "TOLERANCE") "±20 %")
        (field (name "VOLTAGE") "50.0 V")
      )
      (libsource (lib "eagle-import") (part "C-EU-C0603-10N"))
    )
    (comp (ref "C225")
      (value "100n 50V")
      (footprint "eagle-import:C0603")
      (fields
        (field (name "MANUFACTURER") "AVX")
        (field (name "TOLERANCE") "±20 %")
        (field (name "VOLTAGE") "50.0 V")
      )
      (libsource (lib "eagle-import") (part "C-EU-C0603-100N"))
    )
    (comp (ref "C226")
      (value "100n 50V")
      (footprint "eagle-import:C0603")
      (fields
        (field (name "MANUFACTURER") "AVX")
        (field (name "TOLERANCE") "±20 %")
        (field (name "VOLTAGE") "50.0 V")
      )
      (libsource (lib "eagle-import") (part "C-EU-C0603-100N"))
    )
    (comp (ref "C227")
      (value "4u7 16V")
      (footprint "eagle-import:C0805")
      (fields
        (field (name "MANUFACTURER") "AVX")
        (field (name "TOLERANCE") "±20 %")
        (field (name "VOLTAGE") "16.0 V")
      )
      (libsource (lib "eagle-import") (part "C-EU-C0805-4U7"))
    )
    (comp (ref "C228")
      (value "10n 50V")
      (footprint "eagle-import:C0603")
      (fields
        (field (name "MANUFACTURER") "Samsung")
        (field (name "TOLERANCE") "±20 %")
        (field (name "VOLTAGE") "50.0 V")
      )
      (libsource (lib "eagle-import") (part "C-EU-C0603-10N"))
    )
    (comp (ref "C229")
      (value "C-EU-C0603")
      (footprint "eagle-import:C0603")
      (fields (field (name "TOLERANCE") "±20 %") (field (name "VOLTAGE") "50.0 V"))
      (libsource (lib "eagle-import") (part "C-EU-C0603"))
    )
    (comp (ref "C230")
      (value "100n 50V")
      (footprint "eagle-import:C0603")
      (fields
        (field (name "MANUFACTURER") "AVX")
        (field (name "TOLERANCE") "±20 %")
        (field (name "VOLTAGE") "50.0 V")
      )
      (libsource (lib "eagle-import") (part "C-EU-C0603-100N"))
    )
    (comp (ref "C231")
      (value "100n 50V")
      (footprint "eagle-import:C0603")
      (fields
        (field (name "MANUFACTURER") "AVX")
        (field (name "TOLERANCE") "±20 %")
        (field (name "VOLTAGE") "50.0 V")
      )
      (libsource (lib "eagle-import") (part "C-EU-C0603-100N"))
    )
    (comp (ref "C233")
      (value "10n 50V")
      (footprint "eagle-import:C0603")
      (fields
        (field (name "MANUFACTURER") "Samsung")
        (field (name "TOLERANCE") "±20 %")
        (field (name "VOLTAGE") "50.0 V")
      )
      (libsource (lib "eagle-import") (part "C-EU-C0603-10N"))
    )
    (comp (ref "C234")
      (value "C-EU-C0603")
      (footprint "eagle-import:C0603")
      (fields (field (name "TOLERANCE") "±20 %") (field (name "VOLTAGE") "50.0 V"))
      (libsource (lib "eagle-import") (part "C-EU-C0603"))
    )
    (comp (ref "C235")
      (value "22u 10V")
      (footprint "eagle-import:C0805")
      (fields
        (field (name "MANUFACTURER") "AVX")
        (field (name "TOLERANCE") "±20 %")
        (field (name "VOLTAGE") "10.0 V")
      )
      (libsource (lib "eagle-import") (part "C-EU-C0805-22U"))
    )
    (comp (ref "C236")
      (value "C-EU-C0603")
      (footprint "eagle-import:C0603")
      (fields (field (name "TOLERANCE") "±20 %") (field (name "VOLTAGE") "50.0 V"))
      (libsource (lib "eagle-import") (part "C-EU-C0603"))
    )
    (comp (ref "C237")
      (value "C-EU-C0603")
      (footprint "eagle-import:C0603")
      (fields (field (name "TOLERANCE") "±20 %") (field (name "VOLTAGE") "50.0 V"))
      (libsource (lib "eagle-import") (part "C-EU-C0603"))
    )
    (comp (ref "C238")
      (value "100n 50V")
      (footprint "eagle-import:C0603")
      (fields
        (field (name "MANUFACTURER") "AVX")
        (field (name "TOLERANCE") "±20 %")
        (field (name "VOLTAGE") "50.0 V")
      )
      (libsource (lib "eagle-import") (part "C-EU-C0603-100N"))
    )
    (comp (ref "C239")
      (value "100n 50V")
      (footprint "eagle-import:C0603")
      (fields
        (field (name "MANUFACTURER") "AVX")
        (field (name "TOLERANCE") "±20 %")
        (field (name "VOLTAGE") "50.0 V")
      )
      (libsource (lib "eagle-import") (part "C-EU-C0603-100N"))
    )
    (comp (ref "C240")
      (value "100n 50V")
      (footprint "eagle-import:C0603")
      (fields
        (field (name "MANUFACTURER") "AVX")
        (field (name "TOLERANCE") "±20 %")
        (field (name "VOLTAGE") "50.0 V")
      )
      (libsource (lib "eagle-import") (part "C-EU-C0603-100N"))
    )
    (comp (ref "C241")
      (value "100n 50V")
      (footprint "eagle-import:C0603")
      (fields
        (field (name "MANUFACTURER") "AVX")
        (field (name "TOLERANCE") "±20 %")
        (field (name "VOLTAGE") "50.0 V")
      )
      (libsource (lib "eagle-import") (part "C-EU-C0603-100N"))
    )
    (comp (ref "C242")
      (value "100n 50V")
      (footprint "eagle-import:C0603")
      (fields
        (field (name "MANUFACTURER") "AVX")
        (field (name "TOLERANCE") "±20 %")
        (field (name "VOLTAGE") "50.0 V")
      )
      (libsource (lib "eagle-import") (part "C-EU-C0603-100N"))
    )
    (comp (ref "C243")
      (value "2n2 50V")
      (footprint "eagle-import:C0603")
      (fields
        (field (name "MANUFACTURER") "KEMET")
        (field (name "TOLERANCE") "±10 %")
        (field (name "VOLTAGE") "50.0 V")
      )
      (libsource (lib "eagle-import") (part "C-EU-C0603-2N2"))
    )
    (comp (ref "C244")
      (value "100n 50V")
      (footprint "eagle-import:C0603")
      (fields
        (field (name "MANUFACTURER") "AVX")
        (field (name "TOLERANCE") "±20 %")
        (field (name "VOLTAGE") "50.0 V")
      )
      (libsource (lib "eagle-import") (part "C-EU-C0603-100N"))
    )
    (comp (ref "C245")
      (value "27p 50V")
      (footprint "eagle-import:C0603")
      (fields
        (field (name "MANUFACTURER") "AVX")
        (field (name "TOLERANCE") "±20 %")
        (field (name "VOLTAGE") "50.0 V")
      )
      (libsource (lib "eagle-import") (part "C-EU-C0603-27P"))
    )
    (comp (ref "C246")
      (value "100n 50V")
      (footprint "eagle-import:C0603")
      (fields
        (field (name "MANUFACTURER") "AVX")
        (field (name "TOLERANCE") "±20 %")
        (field (name "VOLTAGE") "50.0 V")
      )
      (libsource (lib "eagle-import") (part "C-EU-C0603-100N"))
    )
    (comp (ref "C255")
      (value "22u 10V")
      (footprint "eagle-import:C0805")
      (fields
        (field (name "MANUFACTURER") "AVX")
        (field (name "TOLERANCE") "±20 %")
        (field (name "VOLTAGE") "10.0 V")
      )
      (libsource (lib "eagle-import") (part "C-EU-C0805-22U"))
    )
    (comp (ref "C256")
      (value "10u 50V")
      (footprint "eagle-import:C1206")
      (fields
        (field (name "MANUFACTURER") "Samsung")
        (field (name "TOLERANCE") "±20 %")
        (field (name "VOLTAGE") "50.0 V")
      )
      (libsource (lib "eagle-import") (part "C-EU-C1206-10U"))
    )
    (comp (ref "C257")
      (value "10u 50V")
      (footprint "eagle-import:C1206")
      (fields
        (field (name "MANUFACTURER") "Samsung")
        (field (name "TOLERANCE") "±20 %")
        (field (name "VOLTAGE") "50.0 V")
      )
      (libsource (lib "eagle-import") (part "C-EU-C1206-10U"))
    )
    (comp (ref "C258")
      (value "10u 50V")
      (footprint "eagle-import:C1206")
      (fields
        (field (name "MANUFACTURER") "Samsung")
        (field (name "TOLERANCE") "±20 %")
        (field (name "VOLTAGE") "50.0 V")
      )
      (libsource (lib "eagle-import") (part "C-EU-C1206-10U"))
    )
    (comp (ref "C259")
      (value "10u 50V")
      (footprint "eagle-import:C1206")
      (fields
        (field (name "MANUFACTURER") "Samsung")
        (field (name "TOLERANCE") "±20 %")
        (field (name "VOLTAGE") "50.0 V")
      )
      (libsource (lib "eagle-import") (part "C-EU-C1206-10U"))
    )
    (comp (ref "C260")
      (value "C-EU-C0603")
      (footprint "eagle-import:C0603")
      (fields (field (name "TOLERANCE") "±20 %") (field (name "VOLTAGE") "50.0 V"))
      (libsource (lib "eagle-import") (part "C-EU-C0603"))
    )
    (comp (ref "C261")
      (value "C-EU-C0603")
      (footprint "eagle-import:C0603")
      (fields (field (name "TOLERANCE") "±20 %") (field (name "VOLTAGE") "50.0 V"))
      (libsource (lib "eagle-import") (part "C-EU-C0603"))
    )
    (comp (ref "C262")
      (value "2n2 50V")
      (footprint "eagle-import:C0603")
      (fields
        (field (name "MANUFACTURER") "KEMET")
        (field (name "TOLERANCE") "±10 %")
        (field (name "VOLTAGE") "50.0 V")
      )
      (libsource (lib "eagle-import") (part "C-EU-C0603-2N2"))
    )
    (comp (ref "C263")
      (value "1u 25V")
      (footprint "eagle-import:C0805")
      (fields
        (field (name "MANUFACTURER") "AVX")
        (field (name "TOLERANCE") "±20 %")
        (field (name "VOLTAGE") "25.0 V")
      )
      (libsource (lib "eagle-import") (part "C-EU-C0805-1U"))
    )
    (comp (ref "C264")
      (value "2n2 50V")
      (footprint "eagle-import:C0603")
      (fields
        (field (name "MANUFACTURER") "KEMET")
        (field (name "TOLERANCE") "±10 %")
        (field (name "VOLTAGE") "50.0 V")
      )
      (libsource (lib "eagle-import") (part "C-EU-C0603-2N2"))
    )
    (comp (ref "C265")
      (value "27p 50V")
      (footprint "eagle-import:C0603")
      (fields
        (field (name "MANUFACTURER") "AVX")
        (field (name "TOLERANCE") "±20 %")
        (field (name "VOLTAGE") "50.0 V")
      )
      (libsource (lib "eagle-import") (part "C-EU-C0603-27P"))
    )
    (comp (ref "C266")
      (value "27p 50V")
      (footprint "eagle-import:C0603")
      (fields
        (field (name "MANUFACTURER") "AVX")
        (field (name "TOLERANCE") "±20 %")
        (field (name "VOLTAGE") "50.0 V")
      )
      (libsource (lib "eagle-import") (part "C-EU-C0603-27P"))
    )
    (comp (ref "C267")
      (value "2n2 50V")
      (footprint "eagle-import:C0603")
      (fields
        (field (name "MANUFACTURER") "KEMET")
        (field (name "TOLERANCE") "±10 %")
        (field (name "VOLTAGE") "50.0 V")
      )
      (libsource (lib "eagle-import") (part "C-EU-C0603-2N2"))
    )
    (comp (ref "C268")
      (value "22u 10V")
      (footprint "eagle-import:C0805")
      (fields
        (field (name "MANUFACTURER") "AVX")
        (field (name "TOLERANCE") "±20 %")
        (field (name "VOLTAGE") "10.0 V")
      )
      (libsource (lib "eagle-import") (part "C-EU-C0805-22U"))
    )
    (comp (ref "C269")
      (value "10n 50V")
      (footprint "eagle-import:C0603")
      (fields
        (field (name "MANUFACTURER") "Samsung")
        (field (name "TOLERANCE") "±20 %")
        (field (name "VOLTAGE") "50.0 V")
      )
      (libsource (lib "eagle-import") (part "C-EU-C0603-10N"))
    )
    (comp (ref "C270")
      (value "C-EU-C0603")
      (footprint "eagle-import:C0603")
      (fields (field (name "TOLERANCE") "±20 %") (field (name "VOLTAGE") "50.0 V"))
      (libsource (lib "eagle-import") (part "C-EU-C0603"))
    )
    (comp (ref "C271")
      (value "100n 50V")
      (footprint "eagle-import:C0603")
      (fields
        (field (name "MANUFACTURER") "AVX")
        (field (name "TOLERANCE") "±20 %")
        (field (name "VOLTAGE") "50.0 V")
      )
      (libsource (lib "eagle-import") (part "C-EU-C0603-100N"))
    )
    (comp (ref "C272")
      (value "22u 10V")
      (footprint "eagle-import:C0805")
      (fields
        (field (name "MANUFACTURER") "AVX")
        (field (name "TOLERANCE") "±20 %")
        (field (name "VOLTAGE") "10.0 V")
      )
      (libsource (lib "eagle-import") (part "C-EU-C0805-22U"))
    )
    (comp (ref "C273")
      (value "10n 50V")
      (footprint "eagle-import:C0603")
      (fields
        (field (name "MANUFACTURER") "Samsung")
        (field (name "TOLERANCE") "±20 %")
        (field (name "VOLTAGE") "50.0 V")
      )
      (libsource (lib "eagle-import") (part "C-EU-C0603-10N"))
    )
    (comp (ref "C274")
      (value "C-EU-C0603")
      (footprint "eagle-import:C0603")
      (fields (field (name "TOLERANCE") "±20 %") (field (name "VOLTAGE") "50.0 V"))
      (libsource (lib "eagle-import") (part "C-EU-C0603"))
    )
    (comp (ref "C275")
      (value "22u 10V")
      (footprint "eagle-import:C0805")
      (fields
        (field (name "MANUFACTURER") "AVX")
        (field (name "TOLERANCE") "±20 %")
        (field (name "VOLTAGE") "10.0 V")
      )
      (libsource (lib "eagle-import") (part "C-EU-C0805-22U"))
    )
    (comp (ref "C276")
      (value "100n 50V")
      (footprint "eagle-import:C0603")
      (fields
        (field (name "MANUFACTURER") "AVX")
        (field (name "TOLERANCE") "±20 %")
        (field (name "VOLTAGE") "50.0 V")
      )
      (libsource (lib "eagle-import") (part "C-EU-C0603-100N"))
    )
    (comp (ref "C277")
      (value "10n 50V")
      (footprint "eagle-import:C0603")
      (fields
        (field (name "MANUFACTURER") "Samsung")
        (field (name "TOLERANCE") "±20 %")
        (field (name "VOLTAGE") "50.0 V")
      )
      (libsource (lib "eagle-import") (part "C-EU-C0603-10N"))
    )
    (comp (ref "C278")
      (value "100n 50V")
      (footprint "eagle-import:C0603")
      (fields
        (field (name "MANUFACTURER") "AVX")
        (field (name "TOLERANCE") "±20 %")
        (field (name "VOLTAGE") "50.0 V")
      )
      (libsource (lib "eagle-import") (part "C-EU-C0603-100N"))
    )
    (comp (ref "C279")
      (value "C-EU-C0603")
      (footprint "eagle-import:C0603")
      (fields (field (name "TOLERANCE") "±20 %") (field (name "VOLTAGE") "50.0 V"))
      (libsource (lib "eagle-import") (part "C-EU-C0603"))
    )
    (comp (ref "C280")
      (value "100n 50V")
      (footprint "eagle-import:C0603")
      (fields
        (field (name "MANUFACTURER") "AVX")
        (field (name "TOLERANCE") "±20 %")
        (field (name "VOLTAGE") "50.0 V")
      )
      (libsource (lib "eagle-import") (part "C-EU-C0603-100N"))
    )
    (comp (ref "C282")
      (value "10n 50V")
      (footprint "eagle-import:C0603")
      (fields
        (field (name "MANUFACTURER") "Samsung")
        (field (name "TOLERANCE") "±20 %")
        (field (name "VOLTAGE") "50.0 V")
      )
      (libsource (lib "eagle-import") (part "C-EU-C0603-10N"))
    )
    (comp (ref "C283")
      (value "C-EU-C0603")
      (footprint "eagle-import:C0603")
      (fields (field (name "TOLERANCE") "±20 %") (field (name "VOLTAGE") "50.0 V"))
      (libsource (lib "eagle-import") (part "C-EU-C0603"))
    )
    (comp (ref "C284")
      (value "22u 10V")
      (footprint "eagle-import:C0805")
      (fields
        (field (name "MANUFACTURER") "AVX")
        (field (name "TOLERANCE") "±20 %")
        (field (name "VOLTAGE") "10.0 V")
      )
      (libsource (lib "eagle-import") (part "C-EU-C0805-22U"))
    )
    (comp (ref "C285")
      (value "10n 50V")
      (footprint "eagle-import:C0603")
      (fields
        (field (name "MANUFACTURER") "Samsung")
        (field (name "TOLERANCE") "±20 %")
        (field (name "VOLTAGE") "50.0 V")
      )
      (libsource (lib "eagle-import") (part "C-EU-C0603-10N"))
    )
    (comp (ref "C286")
      (value "100n 50V")
      (footprint "eagle-import:C0603")
      (fields
        (field (name "MANUFACTURER") "AVX")
        (field (name "TOLERANCE") "±20 %")
        (field (name "VOLTAGE") "50.0 V")
      )
      (libsource (lib "eagle-import") (part "C-EU-C0603-100N"))
    )
    (comp (ref "C287")
      (value "220p 25V")
      (footprint "eagle-import:C0402")
      (fields
        (field (name "MANUFACTURER") "Wuerth")
        (field (name "TOLERANCE") "±10 %")
        (field (name "VOLTAGE") "25.0 V")
      )
      (libsource (lib "eagle-import") (part "C-EU-C0402-220P"))
    )
    (comp (ref "C288")
      (value "220p 25V")
      (footprint "eagle-import:C0402")
      (fields
        (field (name "MANUFACTURER") "Wuerth")
        (field (name "TOLERANCE") "±10 %")
        (field (name "VOLTAGE") "25.0 V")
      )
      (libsource (lib "eagle-import") (part "C-EU-C0402-220P"))
    )
    (comp (ref "C289")
      (value "4u7 16V")
      (footprint "eagle-import:C0805")
      (fields
        (field (name "MANUFACTURER") "AVX")
        (field (name "TOLERANCE") "±20 %")
        (field (name "VOLTAGE") "16.0 V")
      )
      (libsource (lib "eagle-import") (part "C-EU-C0805-4U7"))
    )
    (comp (ref "C290")
      (value "4u7 50V")
      (footprint "eagle-import:C1210")
      (fields
        (field (name "MANUFACTURER") "Taiyo Yuden")
        (field (name "TOLERANCE") "±20 %")
        (field (name "VOLTAGE") "50.0 V")
      )
      (libsource (lib "eagle-import") (part "C-EU-C1210-4U7-50V"))
    )
    (comp (ref "C291")
      (value "C-EU-C0603")
      (footprint "eagle-import:C0603")
      (fields (field (name "TOLERANCE") "±20 %") (field (name "VOLTAGE") "50.0 V"))
      (libsource (lib "eagle-import") (part "C-EU-C0603"))
    )
    (comp (ref "C292")
      (value "C-EU-C0603")
      (footprint "eagle-import:C0603")
      (fields (field (name "TOLERANCE") "±20 %") (field (name "VOLTAGE") "50.0 V"))
      (libsource (lib "eagle-import") (part "C-EU-C0603"))
    )
    (comp (ref "C293")
      (value "n.m.")
      (footprint "eagle-import:C0402")
      (fields
        (field (name "TOLERANCE") "±20 %")
        (field (name "DIELECTRIC") "C0G")
        (field (name "TOLERANCE_1") "±5 %")
        (field (name "VOLTAGE") "50 V")
      )
      (libsource (lib "eagle-import") (part "C-EU-C0402"))
    )
    (comp (ref "C294")
      (value "100n 50V")
      (footprint "eagle-import:C0603")
      (fields
        (field (name "MANUFACTURER") "AVX")
        (field (name "TOLERANCE") "±20 %")
        (field (name "VOLTAGE") "50.0 V")
      )
      (libsource (lib "eagle-import") (part "C-EU-C0603-100N"))
    )
    (comp (ref "C295")
      (value "27p 50V")
      (footprint "eagle-import:C0603")
      (fields
        (field (name "MANUFACTURER") "AVX")
        (field (name "TOLERANCE") "±20 %")
        (field (name "VOLTAGE") "50.0 V")
      )
      (libsource (lib "eagle-import") (part "C-EU-C0603-27P"))
    )
    (comp (ref "C296")
      (value "27p 50V")
      (footprint "eagle-import:C0603")
      (fields
        (field (name "MANUFACTURER") "AVX")
        (field (name "TOLERANCE") "±20 %")
        (field (name "VOLTAGE") "50.0 V")
      )
      (libsource (lib "eagle-import") (part "C-EU-C0603-27P"))
    )
    (comp (ref "C297")
      (value "100n 50V")
      (footprint "eagle-import:C0603")
      (fields
        (field (name "MANUFACTURER") "AVX")
        (field (name "TOLERANCE") "±20 %")
        (field (name "VOLTAGE") "50.0 V")
      )
      (libsource (lib "eagle-import") (part "C-EU-C0603-100N"))
    )
    (comp (ref "C298")
      (value "22u 10V")
      (footprint "eagle-import:C0805")
      (fields
        (field (name "MANUFACTURER") "AVX")
        (field (name "TOLERANCE") "±20 %")
        (field (name "VOLTAGE") "10.0 V")
      )
      (libsource (lib "eagle-import") (part "C-EU-C0805-22U"))
    )
    (comp (ref "C299")
      (value "22u 10V")
      (footprint "eagle-import:C0805")
      (fields
        (field (name "MANUFACTURER") "AVX")
        (field (name "TOLERANCE") "±20 %")
        (field (name "VOLTAGE") "10.0 V")
      )
      (libsource (lib "eagle-import") (part "C-EU-C0805-22U"))
    )
    (comp (ref "C300")
      (value "10u 50V")
      (footprint "eagle-import:C1206")
      (fields
        (field (name "MANUFACTURER") "Samsung")
        (field (name "TOLERANCE") "±20 %")
        (field (name "VOLTAGE") "50.0 V")
      )
      (libsource (lib "eagle-import") (part "C-EU-C1206-10U"))
    )
    (comp (ref "C301")
      (value "10u 50V")
      (footprint "eagle-import:C1206")
      (fields
        (field (name "MANUFACTURER") "Samsung")
        (field (name "TOLERANCE") "±20 %")
        (field (name "VOLTAGE") "50.0 V")
      )
      (libsource (lib "eagle-import") (part "C-EU-C1206-10U"))
    )
    (comp (ref "D1")
      (value "PMEG6010CEJ")
      (footprint "eagle-import:SOD323F_SC-90_NXP")
      (fields (field (name "MANUFACTURER") "Nexperia") (field (name "VOLTAGE") "60 V"))
      (libsource (lib "eagle-import") (part "PMEG6010CEJ"))
    )
    (comp (ref "D2")
      (value "SMA6J15CA")
      (footprint "eagle-import:SMA_BI_ST")
      (fields (field (name "MANUFACTURER") "Bourns") (field (name "VOLTAGE") "15.0 V"))
      (libsource (lib "eagle-import") (part "SMA6J15CA"))
    )
    (comp (ref "D3")
      (value "PMEG060V100EPD")
      (footprint "eagle-import:CFP15_SOT1289_NXP")
      (fields (field (name "MANUFACTURER") "Nexperia") (field (name "VOLTAGE") "60.0 V"))
      (libsource (lib "eagle-import") (part "PMEG060V100EPD"))
    )
    (comp (ref "D4")
      (value "150060BS75000")
      (footprint "eagle-import:WL-SMCW_0603_WE")
      (fields (field (name "MANUFACTURER") "Wuerth") (field (name "VOLTAGE") "5.0 V"))
      (libsource (lib "eagle-import") (part "150060BS75000"))
    )
    (comp (ref "D5")
      (value "150060BS75000")
      (footprint "eagle-import:WL-SMCW_0603_WE")
      (fields (field (name "MANUFACTURER") "Wuerth") (field (name "VOLTAGE") "5.0 V"))
      (libsource (lib "eagle-import") (part "150060BS75000"))
    )
    (comp (ref "D6")
      (value "BAS70W-05")
      (footprint "eagle-import:SOT-323_DIODES_INC")
      (fields (field (name "MANUFACTURER") "Diodes Inc") (field (name "VOLTAGE") "70.0 V"))
      (libsource (lib "eagle-import") (part "BAS70W-05"))
    )
    (comp (ref "D7")
      (value "BAS70W-05")
      (footprint "eagle-import:SOT-323_DIODES_INC")
      (fields (field (name "MANUFACTURER") "Diodes Inc") (field (name "VOLTAGE") "70.0 V"))
      (libsource (lib "eagle-import") (part "BAS70W-05"))
    )
    (comp (ref "D8")
      (value "150060BS75000")
      (footprint "eagle-import:WL-SMCW_0603_WE")
      (fields (field (name "MANUFACTURER") "Wuerth") (field (name "VOLTAGE") "5.0 V"))
      (libsource (lib "eagle-import") (part "150060BS75000"))
    )
    (comp (ref "D9")
      (value "150060GS75000")
      (footprint "eagle-import:WL-SMCW_0603_WE")
      (fields (field (name "MANUFACTURER") "Wuerth") (field (name "VOLTAGE") "5.0 V"))
      (libsource (lib "eagle-import") (part "150060GS75000"))
    )
    (comp (ref "D10")
      (value "150060GS75000")
      (footprint "eagle-import:WL-SMCW_0603_WE")
      (fields (field (name "MANUFACTURER") "Wuerth") (field (name "VOLTAGE") "5.0 V"))
      (libsource (lib "eagle-import") (part "150060GS75000"))
    )
    (comp (ref "D11")
      (value "150060GS75000")
      (footprint "eagle-import:WL-SMCW_0603_WE")
      (fields (field (name "MANUFACTURER") "Wuerth") (field (name "VOLTAGE") "5.0 V"))
      (libsource (lib "eagle-import") (part "150060GS75000"))
    )
    (comp (ref "D12")
      (value "150060GS75000")
      (footprint "eagle-import:WL-SMCW_0603_WE")
      (fields (field (name "MANUFACTURER") "Wuerth") (field (name "VOLTAGE") "5.0 V"))
      (libsource (lib "eagle-import") (part "150060GS75000"))
    )
    (comp (ref "D13")
      (value "PMEG6010CEJ")
      (footprint "eagle-import:SOD323F_SC-90_NXP")
      (fields (field (name "MANUFACTURER") "Nexperia") (field (name "VOLTAGE") "60 V"))
      (libsource (lib "eagle-import") (part "PMEG6010CEJ"))
    )
    (comp (ref "D14")
      (value "PMEG060V100EPD")
      (footprint "eagle-import:CFP15_SOT1289_NXP")
      (fields (field (name "MANUFACTURER") "Nexperia") (field (name "VOLTAGE") "60.0 V"))
      (libsource (lib "eagle-import") (part "PMEG060V100EPD"))
    )
    (comp (ref "D15")
      (value "PMEG6010CEJ")
      (footprint "eagle-import:SOD323F_SC-90_NXP")
      (fields (field (name "MANUFACTURER") "Nexperia") (field (name "VOLTAGE") "60 V"))
      (libsource (lib "eagle-import") (part "PMEG6010CEJ"))
    )
    (comp (ref "D16")
      (value "BAS70W-05")
      (footprint "eagle-import:SOT-323_DIODES_INC")
      (fields (field (name "MANUFACTURER") "Diodes Inc") (field (name "VOLTAGE") "70.0 V"))
      (libsource (lib "eagle-import") (part "BAS70W-05"))
    )
    (comp (ref "D17")
      (value "n.m.")
      (footprint "eagle-import:SOD323F_SC-90_NXP")
      (fields (field (name "MANUFACTURER") "Nexperia") (field (name "VOLTAGE") "60 V"))
      (libsource (lib "eagle-import") (part "PMEG6010CEJ"))
    )
    (comp (ref "D18")
      (value "PMEG060V100EPD")
      (footprint "eagle-import:CFP15_SOT1289_NXP")
      (fields (field (name "MANUFACTURER") "Nexperia") (field (name "VOLTAGE") "60.0 V"))
      (libsource (lib "eagle-import") (part "PMEG060V100EPD"))
    )
    (comp (ref "D19")
      (value "150060GS75000")
      (footprint "eagle-import:WL-SMCW_0603_WE")
      (fields (field (name "MANUFACTURER") "Wuerth") (field (name "VOLTAGE") "5.0 V"))
      (libsource (lib "eagle-import") (part "150060GS75000"))
    )
    (comp (ref "D20")
      (value "PMEG6010CEJ")
      (footprint "eagle-import:SOD323F_SC-90_NXP")
      (fields (field (name "MANUFACTURER") "Nexperia") (field (name "VOLTAGE") "60 V"))
      (libsource (lib "eagle-import") (part "PMEG6010CEJ"))
    )
    (comp (ref "D21")
      (value "150060GS75000")
      (footprint "eagle-import:WL-SMCW_0603_WE")
      (fields (field (name "MANUFACTURER") "Wuerth") (field (name "VOLTAGE") "5.0 V"))
      (libsource (lib "eagle-import") (part "150060GS75000"))
    )
    (comp (ref "D22")
      (value "150060GS75000")
      (footprint "eagle-import:WL-SMCW_0603_WE")
      (fields (field (name "MANUFACTURER") "Wuerth") (field (name "VOLTAGE") "5.0 V"))
      (libsource (lib "eagle-import") (part "150060GS75000"))
    )
    (comp (ref "D23")
      (value "150060GS75000")
      (footprint "eagle-import:WL-SMCW_0603_WE")
      (fields (field (name "MANUFACTURER") "Wuerth") (field (name "VOLTAGE") "5.0 V"))
      (libsource (lib "eagle-import") (part "150060GS75000"))
    )
    (comp (ref "D24")
      (value "BAS70W-05")
      (footprint "eagle-import:SOT-323_DIODES_INC")
      (fields (field (name "MANUFACTURER") "Diodes Inc") (field (name "VOLTAGE") "70.0 V"))
      (libsource (lib "eagle-import") (part "BAS70W-05"))
    )
    (comp (ref "D25")
      (value "150060GS75000")
      (footprint "eagle-import:WL-SMCW_0603_WE")
      (fields (field (name "MANUFACTURER") "Wuerth") (field (name "VOLTAGE") "5.0 V"))
      (libsource (lib "eagle-import") (part "150060GS75000"))
    )
    (comp (ref "D26")
      (value "150060GS75000")
      (footprint "eagle-import:WL-SMCW_0603_WE")
      (fields (field (name "MANUFACTURER") "Wuerth") (field (name "VOLTAGE") "5.0 V"))
      (libsource (lib "eagle-import") (part "150060GS75000"))
    )
    (comp (ref "D27")
      (value "150060GS75000")
      (footprint "eagle-import:WL-SMCW_0603_WE")
      (fields (field (name "MANUFACTURER") "Wuerth") (field (name "VOLTAGE") "5.0 V"))
      (libsource (lib "eagle-import") (part "150060GS75000"))
    )
    (comp (ref "D28")
      (value "150060GS75000")
      (footprint "eagle-import:WL-SMCW_0603_WE")
      (fields (field (name "MANUFACTURER") "Wuerth") (field (name "VOLTAGE") "5.0 V"))
      (libsource (lib "eagle-import") (part "150060GS75000"))
    )
    (comp (ref "D29")
      (value "BAS70W-05")
      (footprint "eagle-import:SOT-323_DIODES_INC")
      (fields (field (name "MANUFACTURER") "Diodes Inc") (field (name "VOLTAGE") "70.0 V"))
      (libsource (lib "eagle-import") (part "BAS70W-05"))
    )
    (comp (ref "D30")
      (value "BAS70W-05")
      (footprint "eagle-import:SOT-323_DIODES_INC")
      (fields (field (name "MANUFACTURER") "Diodes Inc") (field (name "VOLTAGE") "70.0 V"))
      (libsource (lib "eagle-import") (part "BAS70W-05"))
    )
    (comp (ref "D31")
      (value "PMEG6010CEJ")
      (footprint "eagle-import:SOD323F_SC-90_NXP")
      (fields (field (name "MANUFACTURER") "Nexperia") (field (name "VOLTAGE") "60 V"))
      (libsource (lib "eagle-import") (part "PMEG6010CEJ"))
    )
    (comp (ref "D58")
      (value "150060GS75000")
      (footprint "eagle-import:WL-SMCW_0603_WE")
      (fields (field (name "MANUFACTURER") "Wuerth") (field (name "VOLTAGE") "5.0 V"))
      (libsource (lib "eagle-import") (part "150060GS75000"))
    )
    (comp (ref "D59")
      (value "150060GS75000")
      (footprint "eagle-import:WL-SMCW_0603_WE")
      (fields (field (name "MANUFACTURER") "Wuerth") (field (name "VOLTAGE") "5.0 V"))
      (libsource (lib "eagle-import") (part "150060GS75000"))
    )
    (comp (ref "F1")
      (value "SF-1206SA1000W-2")
      (footprint "eagle-import:SF-1206SA_BOURNS")
      (fields (field (name "MANUFACTURER") "Bourns"))
      (libsource (lib "eagle-import") (part "SF-1206SA1000W-2"))
    )
    (comp (ref "F2")
      (value "SF-1206SA1000W-2")
      (footprint "eagle-import:SF-1206SA_BOURNS")
      (fields (field (name "MANUFACTURER") "Bourns"))
      (libsource (lib "eagle-import") (part "SF-1206SA1000W-2"))
    )
    (comp (ref "F3")
      (value "SF-1206S100")
      (footprint "eagle-import:SF-1206S_BOURNS")
      (fields (field (name "MANUFACTURER") "Bourns") (field (name "VOLTAGE") "63 V(DC)"))
      (libsource (lib "eagle-import") (part "SF-1206S100"))
    )
    (comp (ref "F4")
      (value "SF-1206SA1000W-2")
      (footprint "eagle-import:SF-1206SA_BOURNS")
      (fields (field (name "MANUFACTURER") "Bourns"))
      (libsource (lib "eagle-import") (part "SF-1206SA1000W-2"))
    )
    (comp (ref "H3")
      (value "MOUNT-PAD-ROUND3.4")
      (footprint "eagle-import:3,4-PAD")
      (libsource (lib "eagle-import") (part "MOUNT-PAD-ROUND3.4"))
    )
    (comp (ref "H4")
      (value "MOUNT-PAD-ROUND3.4")
      (footprint "eagle-import:3,4-PAD")
      (libsource (lib "eagle-import") (part "MOUNT-PAD-ROUND3.4"))
    )
    (comp (ref "H5")
      (value "MOUNT-PAD-ROUND3.4")
      (footprint "eagle-import:3,4-PAD")
      (libsource (lib "eagle-import") (part "MOUNT-PAD-ROUND3.4"))
    )
    (comp (ref "H6")
      (value "MOUNT-PAD-ROUND3.4")
      (footprint "eagle-import:3,4-PAD")
      (libsource (lib "eagle-import") (part "MOUNT-PAD-ROUND3.4"))
    )
    (comp (ref "IC1")
      (value "TPS62933DRL")
      (footprint "eagle-import:DRL0008A_TI")
      (fields (field (name "MANUFACTURER") "TI") (field (name "VOLTAGE") "30.0 V"))
      (libsource (lib "eagle-import") (part "TPS62933DRL"))
    )
    (comp (ref "IC2")
      (value "SN74LV1T34DCKR")
      (footprint "eagle-import:R-PDSO-G5_DCK_TI")
      (fields (field (name "MANUFACTURER") "TI") (field (name "VOLTAGE") "5.5 V"))
      (libsource (lib "eagle-import") (part "SN74LV1T34DCKR"))
    )
    (comp (ref "IC3")
      (value "ICM-40627")
      (footprint "eagle-import:LGA-14_2.5X3.0_TDK")
      (fields (field (name "MANUFACTURER") "TDK") (field (name "VOLTAGE") "3.6 V"))
      (libsource (lib "eagle-import") (part "ICM-40627"))
    )
    (comp (ref "IC4")
      (value "TPS62933DRL")
      (footprint "eagle-import:DRL0008A_TI")
      (fields (field (name "MANUFACTURER") "TI") (field (name "VOLTAGE") "30.0 V"))
      (libsource (lib "eagle-import") (part "TPS62933DRL"))
    )
    (comp (ref "IC5")
      (value "LM25117PSQ")
      (footprint "eagle-import:S-PWQFN-N24_RTW_TI")
      (fields (field (name "MANUFACTURER") "TI") (field (name "VOLTAGE") "42.0 V"))
      (libsource (lib "eagle-import") (part "LM25117PSQ"))
    )
    (comp (ref "IC6")
      (value "824001")
      (footprint "eagle-import:SOT23-6L_WE")
      (fields (field (name "MANUFACTURER") "Wuerth") (field (name "VOLTAGE") "5.0 V"))
      (libsource (lib "eagle-import") (part "824001"))
    )
    (comp (ref "IC7")
      (value "UCC27282DRC")
      (footprint "eagle-import:DRC0010J_TI")
      (fields (field (name "MANUFACTURER") "TI") (field (name "VOLTAGE") "16.0 V"))
      (libsource (lib "eagle-import") (part "UCC27282DRC"))
    )
    (comp (ref "IC8")
      (value "824001")
      (footprint "eagle-import:SOT23-6L_WE")
      (fields (field (name "MANUFACTURER") "Wuerth") (field (name "VOLTAGE") "5.0 V"))
      (libsource (lib "eagle-import") (part "824001"))
    )
    (comp (ref "IC9")
      (value "TLV431IDBV")
      (footprint "eagle-import:DBV0005A_TI")
      (fields (field (name "MANUFACTURER") "TI") (field (name "VOLTAGE") "6.0 V"))
      (libsource (lib "eagle-import") (part "TLV431IDBV"))
    )
    (comp (ref "IC10")
      (value "TPS62933DRL")
      (footprint "eagle-import:DRL0008A_TI")
      (fields (field (name "MANUFACTURER") "TI") (field (name "VOLTAGE") "30.0 V"))
      (libsource (lib "eagle-import") (part "TPS62933DRL"))
    )
    (comp (ref "IC11")
      (value "SN74AXC8T245PW")
      (footprint "eagle-import:PW0024A_TSSOP_TI")
      (fields (field (name "MANUFACTURER") "TI") (field (name "VOLTAGE") "3.6 V"))
      (libsource (lib "eagle-import") (part "SN74AXC8T245PW"))
    )
    (comp (ref "IC12")
      (value "TLV9152IDDF")
      (footprint "eagle-import:DDF0008A_TI")
      (fields (field (name "MANUFACTURER") "TI") (field (name "VOLTAGE") "16.0 V"))
      (libsource (lib "eagle-import") (part "TLV9152DDFI"))
    )
    (comp (ref "IC14")
      (value "824001")
      (footprint "eagle-import:SOT23-6L_WE")
      (fields (field (name "MANUFACTURER") "Wuerth") (field (name "VOLTAGE") "5.0 V"))
      (libsource (lib "eagle-import") (part "824001"))
    )
    (comp (ref "IC15")
      (value "TLV431IDBV")
      (footprint "eagle-import:DBV0005A_TI")
      (fields (field (name "MANUFACTURER") "TI") (field (name "VOLTAGE") "6.0 V"))
      (libsource (lib "eagle-import") (part "TLV431IDBV"))
    )
    (comp (ref "IC16")
      (value "824001")
      (footprint "eagle-import:SOT23-6L_WE")
      (fields (field (name "MANUFACTURER") "Wuerth") (field (name "VOLTAGE") "5.0 V"))
      (libsource (lib "eagle-import") (part "824001"))
    )
    (comp (ref "IC17")
      (value "SN74LVC2T45DCU")
      (footprint "eagle-import:S-PDSO-G8_DCU_TI")
      (fields (field (name "MANUFACTURER") "TI") (field (name "VOLTAGE") "5.5 V"))
      (libsource (lib "eagle-import") (part "SN74LVC2T45DCU"))
    )
    (comp (ref "IC19")
      (value "USB2514B")
      (footprint "eagle-import:SQFN36_6X6_MCP")
      (fields (field (name "MANUFACTURER") "Microchip") (field (name "VOLTAGE") "3.6 V"))
      (libsource (lib "eagle-import") (part "USB2514B"))
    )
    (comp (ref "IC20")
      (value "STM32G474VET6")
      (footprint "eagle-import:LQFP100_STM")
      (fields (field (name "MANUFACTURER") "STM") (field (name "VOLTAGE") "3.6 V"))
      (libsource (lib "eagle-import") (part "STM32G474VET6"))
    )
    (comp (ref "IC21")
      (value "TLV431IDBV")
      (footprint "eagle-import:DBV0005A_TI")
      (fields (field (name "MANUFACTURER") "TI") (field (name "VOLTAGE") "6.0 V"))
      (libsource (lib "eagle-import") (part "TLV431IDBV"))
    )
    (comp (ref "IC22")
      (value "MAX-M8Q")
      (footprint "eagle-import:MAX-8_MAX-M8_UBLOX")
      (fields (field (name "MANUFACTURER") "u-blox") (field (name "VOLTAGE") "3.6 V"))
      (libsource (lib "eagle-import") (part "MAX-M8Q"))
    )
    (comp (ref "IC23")
      (value "SN74LV1T34DCKR")
      (footprint "eagle-import:R-PDSO-G5_DCK_TI")
      (fields (field (name "MANUFACTURER") "TI") (field (name "VOLTAGE") "5.5 V"))
      (libsource (lib "eagle-import") (part "SN74LV1T34DCKR"))
    )
    (comp (ref "IC24")
      (value "TAS5805MPWP")
      (footprint "eagle-import:PWP0028M_TI")
      (fields (field (name "MANUFACTURER") "TI") (field (name "VOLTAGE") "26.4 V"))
      (libsource (lib "eagle-import") (part "TAS5805MPWP"))
    )
    (comp (ref "IC25")
      (value "TPS62933DRL")
      (footprint "eagle-import:DRL0008A_TI")
      (fields (field (name "MANUFACTURER") "TI") (field (name "VOLTAGE") "30.0 V"))
      (libsource (lib "eagle-import") (part "TPS62933DRL"))
    )
    (comp (ref "IC27")
      (value "TLV431IDBV")
      (footprint "eagle-import:DBV0005A_TI")
      (fields (field (name "MANUFACTURER") "TI") (field (name "VOLTAGE") "6.0 V"))
      (libsource (lib "eagle-import") (part "TLV431IDBV"))
    )
    (comp (ref "IC28")
      (value "TLV9152IDDF")
      (footprint "eagle-import:DDF0008A_TI")
      (fields (field (name "MANUFACTURER") "TI") (field (name "VOLTAGE") "16.0 V"))
      (libsource (lib "eagle-import") (part "TLV9152DDFI"))
    )
    (comp (ref "IC29")
      (value "TLV9152IDDF")
      (footprint "eagle-import:DDF0008A_TI")
      (fields (field (name "MANUFACTURER") "TI") (field (name "VOLTAGE") "16.0 V"))
      (libsource (lib "eagle-import") (part "TLV9152DDFI"))
    )
    (comp (ref "IC30")
      (value "TMUX1209RSV")
      (footprint "eagle-import:RSV0016A_TI")
      (fields (field (name "MANUFACTURER") "TI") (field (name "VOLTAGE") "5.5 V"))
      (libsource (lib "eagle-import") (part "TMUX1209RSV"))
    )
    (comp (ref "IC31")
      (value "LM5122MH")
      (footprint "eagle-import:PWP0020A_TI")
      (fields (field (name "MANUFACTURER") "TI") (field (name "VOLTAGE") "65.0 V"))
      (libsource (lib "eagle-import") (part "LM5122MH"))
    )
    (comp (ref "IC32")
      (value "SN74LV1T34DCKR")
      (footprint "eagle-import:R-PDSO-G5_DCK_TI")
      (fields (field (name "MANUFACTURER") "TI") (field (name "VOLTAGE") "5.5 V"))
      (libsource (lib "eagle-import") (part "SN74LV1T34DCKR"))
    )
    (comp (ref "IC33")
      (value "TPS62933DRL")
      (footprint "eagle-import:DRL0008A_TI")
      (fields (field (name "MANUFACTURER") "TI") (field (name "VOLTAGE") "30.0 V"))
      (libsource (lib "eagle-import") (part "TPS62933DRL"))
    )
    (comp (ref "IC34")
      (value "n.m.")
      (footprint "eagle-import:R-PDSO-G5_DCK_TI")
      (fields (field (name "MANUFACTURER") "TI") (field (name "VOLTAGE") "5.5 V"))
      (libsource (lib "eagle-import") (part "SN74LV1T34DCKR"))
    )
    (comp (ref "IC35")
      (value "BQ24640RVA")
      (footprint "eagle-import:S-PVQFN-N16_RVA_TI")
      (fields (field (name "MANUFACTURER") "TI") (field (name "VOLTAGE") "28.0 V"))
      (libsource (lib "eagle-import") (part "BQ24640RVA"))
    )
    (comp (ref "IC36")
      (value "n.m.")
      (footprint "eagle-import:DBZ0003A_TI")
      (fields (field (name "MANUFACTURER") "TI") (field (name "VOLTAGE") "6.0 V"))
      (libsource (lib "eagle-import") (part "TLV431DBZI"))
    )
    (comp (ref "IC37")
      (value "n.m.")
      (footprint "eagle-import:DBZ0003A_TI")
      (fields (field (name "MANUFACTURER") "TI") (field (name "VOLTAGE") "6.0 V"))
      (libsource (lib "eagle-import") (part "TLV431DBZI"))
    )
    (comp (ref "IC38")
      (value "n.m.")
      (footprint "eagle-import:DBZ0003A_TI")
      (fields (field (name "MANUFACTURER") "TI") (field (name "VOLTAGE") "6.0 V"))
      (libsource (lib "eagle-import") (part "TLV431DBZI"))
    )
    (comp (ref "IC39")
      (value "n.m.")
      (footprint "eagle-import:DBZ0003A_TI")
      (fields (field (name "MANUFACTURER") "TI") (field (name "VOLTAGE") "6.0 V"))
      (libsource (lib "eagle-import") (part "TLV431DBZI"))
    )
    (comp (ref "IC40")
      (value "n.m.")
      (footprint "eagle-import:DBZ0003A_TI")
      (fields (field (name "MANUFACTURER") "TI") (field (name "VOLTAGE") "6.0 V"))
      (libsource (lib "eagle-import") (part "TLV431DBZI"))
    )
    (comp (ref "IC41")
      (value "TLV9152IDDF")
      (footprint "eagle-import:DDF0008A_TI")
      (fields (field (name "MANUFACTURER") "TI") (field (name "VOLTAGE") "16.0 V"))
      (libsource (lib "eagle-import") (part "TLV9152DDFI"))
    )
    (comp (ref "IC42")
      (value "TLV9152IDDF")
      (footprint "eagle-import:DDF0008A_TI")
      (fields (field (name "MANUFACTURER") "TI") (field (name "VOLTAGE") "16.0 V"))
      (libsource (lib "eagle-import") (part "TLV9152DDFI"))
    )
    (comp (ref "IC43")
      (value "TLV9152IDDF")
      (footprint "eagle-import:DDF0008A_TI")
      (fields (field (name "MANUFACTURER") "TI") (field (name "VOLTAGE") "16.0 V"))
      (libsource (lib "eagle-import") (part "TLV9152DDFI"))
    )
    (comp (ref "IC44")
      (value "TLV9152IDDF")
      (footprint "eagle-import:DDF0008A_TI")
      (fields (field (name "MANUFACTURER") "TI") (field (name "VOLTAGE") "16.0 V"))
      (libsource (lib "eagle-import") (part "TLV9152DDFI"))
    )
    (comp (ref "IC45")
      (value "TPS62933DRL")
      (footprint "eagle-import:DRL0008A_TI")
      (fields (field (name "MANUFACTURER") "TI") (field (name "VOLTAGE") "30.0 V"))
      (libsource (lib "eagle-import") (part "TPS62933DRL"))
    )
    (comp (ref "IC46")
      (value "UCC27282DRC")
      (footprint "eagle-import:DRC0010J_TI")
      (fields (field (name "MANUFACTURER") "TI") (field (name "VOLTAGE") "16.0 V"))
      (libsource (lib "eagle-import") (part "UCC27282DRC"))
    )
    (comp (ref "IC47")
      (value "INA240A1PW")
      (footprint "eagle-import:PW0008A_TSSOP_TI")
      (fields (field (name "MANUFACTURER") "TI") (field (name "VOLTAGE") "5.5 V"))
      (libsource (lib "eagle-import") (part "INA240PWA1"))
    )
    (comp (ref "IC48")
      (value "TCR2LF18")
      (footprint "eagle-import:SOT-25-5_SC-74A_TOSHIBA")
      (fields (field (name "MANUFACTURER") "Toshiba") (field (name "VOLTAGE") "5.5 V"))
      (libsource (lib "eagle-import") (part "TCR2LF18"))
    )
    (comp (ref "IC49")
      (value "TLV9152IDDF")
      (footprint "eagle-import:DDF0008A_TI")
      (fields (field (name "MANUFACTURER") "TI") (field (name "VOLTAGE") "16.0 V"))
      (libsource (lib "eagle-import") (part "TLV9152DDFI"))
    )
    (comp (ref "IC52")
      (value "824001")
      (footprint "eagle-import:SOT23-6L_WE")
      (fields (field (name "MANUFACTURER") "Wuerth") (field (name "VOLTAGE") "5.0 V"))
      (libsource (lib "eagle-import") (part "824001"))
    )
    (comp (ref "IC53")
      (value "TLV9152IDDF")
      (footprint "eagle-import:DDF0008A_TI")
      (fields (field (name "MANUFACTURER") "TI") (field (name "VOLTAGE") "16.0 V"))
      (libsource (lib "eagle-import") (part "TLV9152DDFI"))
    )
    (comp (ref "IC54")
      (value "TMUX1209RSV")
      (footprint "eagle-import:RSV0016A_TI")
      (fields (field (name "MANUFACTURER") "TI") (field (name "VOLTAGE") "5.5 V"))
      (libsource (lib "eagle-import") (part "TMUX1209RSV"))
    )
    (comp (ref "IC55")
      (value "TMUX1209RSV")
      (footprint "eagle-import:RSV0016A_TI")
      (fields (field (name "MANUFACTURER") "TI") (field (name "VOLTAGE") "5.5 V"))
      (libsource (lib "eagle-import") (part "TMUX1209RSV"))
    )
    (comp (ref "IC56")
      (value "TLV431IDBV")
      (footprint "eagle-import:DBV0005A_TI")
      (fields (field (name "MANUFACTURER") "TI") (field (name "VOLTAGE") "6.0 V"))
      (libsource (lib "eagle-import") (part "TLV431IDBV"))
    )
    (comp (ref "IC57")
      (value "824001")
      (footprint "eagle-import:SOT23-6L_WE")
      (fields (field (name "MANUFACTURER") "Wuerth") (field (name "VOLTAGE") "5.0 V"))
      (libsource (lib "eagle-import") (part "824001"))
    )
    (comp (ref "IC58")
      (value "824001")
      (footprint "eagle-import:SOT23-6L_WE")
      (fields (field (name "MANUFACTURER") "Wuerth") (field (name "VOLTAGE") "5.0 V"))
      (libsource (lib "eagle-import") (part "824001"))
    )
    (comp (ref "IC74")
      (value "TPS62933DRL")
      (footprint "eagle-import:DRL0008A_TI")
      (fields (field (name "MANUFACTURER") "TI") (field (name "VOLTAGE") "30.0 V"))
      (libsource (lib "eagle-import") (part "TPS62933DRL"))
    )
    (comp (ref "IC75")
      (value "n.m.")
      (footprint "eagle-import:R-PDSO-G5_DCK_TI")
      (fields (field (name "MANUFACTURER") "TI") (field (name "VOLTAGE") "5.5 V"))
      (libsource (lib "eagle-import") (part "SN74LV1T34DCKR"))
    )
    (comp (ref "IC76")
      (value "ST25DV04K-IER6C3")
      (footprint "eagle-import:UFDFPN8_ST")
      (fields (field (name "MANUFACTURER") "STM") (field (name "VOLTAGE") "5.5 V"))
      (libsource (lib "eagle-import") (part "ST25DV04K-IER6C3"))
    )
    (comp (ref "IC77")
      (value "TMP112NAIDRL")
      (footprint "eagle-import:DRL0006A_TI")
      (fields (field (name "MANUFACTURER") "TI") (field (name "VOLTAGE") "3.6 V"))
      (libsource (lib "eagle-import") (part "TMP112DRLNAI"))
    )
    (comp (ref "L1")
      (value "744062001")
      (footprint "eagle-import:WE-TPC_6823_WE")
      (fields (field (name "MANUFACTURER") "Wuerth") (field (name "TOLERANCE") "+20 %, -40 %"))
      (libsource (lib "eagle-import") (part "744062001"))
    )
    (comp (ref "L2")
      (value "74279252")
      (footprint "eagle-import:FERRIT_1812_WUERTH")
      (fields (field (name "MANUFACTURER") "Wuerth"))
      (libsource (lib "eagle-import") (part "74279252"))
    )
    (comp (ref "L3")
      (value "74279252")
      (footprint "eagle-import:FERRIT_1812_WUERTH")
      (fields (field (name "MANUFACTURER") "Wuerth"))
      (libsource (lib "eagle-import") (part "74279252"))
    )
    (comp (ref "L4")
      (value "74279252")
      (footprint "eagle-import:FERRIT_1812_WUERTH")
      (fields (field (name "MANUFACTURER") "Wuerth"))
      (libsource (lib "eagle-import") (part "74279252"))
    )
    (comp (ref "L5")
      (value "74439369033")
      (footprint "eagle-import:WE-XHMI_1090_WE")
      (fields (field (name "MANUFACTURER") "Wuerth") (field (name "TOLERANCE") "±20 %"))
      (libsource (lib "eagle-import") (part "74439369033"))
    )
    (comp (ref "L6")
      (value "74404054100")
      (footprint "eagle-import:WE-LQS_5040_WE")
      (fields (field (name "MANUFACTURER") "Wuerth") (field (name "TOLERANCE") "±20 %"))
      (libsource (lib "eagle-import") (part "74404054100"))
    )
    (comp (ref "L7")
      (value "74279252")
      (footprint "eagle-import:FERRIT_1812_WUERTH")
      (fields (field (name "MANUFACTURER") "Wuerth"))
      (libsource (lib "eagle-import") (part "74279252"))
    )
    (comp (ref "L8")
      (value "74404054100")
      (footprint "eagle-import:WE-LQS_5040_WE")
      (fields (field (name "MANUFACTURER") "Wuerth") (field (name "TOLERANCE") "±20 %"))
      (libsource (lib "eagle-import") (part "74404054100"))
    )
    (comp (ref "L9")
      (value "74279252")
      (footprint "eagle-import:FERRIT_1812_WUERTH")
      (fields (field (name "MANUFACTURER") "Wuerth"))
      (libsource (lib "eagle-import") (part "74279252"))
    )
    (comp (ref "L10")
      (value "742792097")
      (footprint "eagle-import:FERRIT_0805_WUERTH")
      (fields (field (name "MANUFACTURER") "Wuerth"))
      (libsource (lib "eagle-import") (part "742792097"))
    )
    (comp (ref "L11")
      (value "742792097")
      (footprint "eagle-import:FERRIT_0805_WUERTH")
      (fields (field (name "MANUFACTURER") "Wuerth"))
      (libsource (lib "eagle-import") (part "742792097"))
    )
    (comp (ref "L12")
      (value "74404054100")
      (footprint "eagle-import:WE-LQS_5040_WE")
      (fields (field (name "MANUFACTURER") "Wuerth") (field (name "TOLERANCE") "±20 %"))
      (libsource (lib "eagle-import") (part "74404054100"))
    )
    (comp (ref "L13")
      (value "74404054100")
      (footprint "eagle-import:WE-LQS_5040_WE")
      (fields (field (name "MANUFACTURER") "Wuerth") (field (name "TOLERANCE") "±20 %"))
      (libsource (lib "eagle-import") (part "74404054100"))
    )
    (comp (ref "L14")
      (value "744071039")
      (footprint "eagle-import:WE-TPC_8043_WE")
      (fields (field (name "MANUFACTURER") "Wuerth") (field (name "TOLERANCE") "±30 %"))
      (libsource (lib "eagle-import") (part "744071039"))
    )
    (comp (ref "L15")
      (value "744071039")
      (footprint "eagle-import:WE-TPC_8043_WE")
      (fields (field (name "MANUFACTURER") "Wuerth") (field (name "TOLERANCE") "±30 %"))
      (libsource (lib "eagle-import") (part "744071039"))
    )
    (comp (ref "L17")
      (value "74439369033")
      (footprint "eagle-import:WE-XHMI_1090_WE")
      (fields (field (name "MANUFACTURER") "Wuerth") (field (name "TOLERANCE") "±20 %"))
      (libsource (lib "eagle-import") (part "74439369033"))
    )
    (comp (ref "L18")
      (value "7447714068")
      (footprint "eagle-import:WE-PD_1050_WE")
      (fields (field (name "MANUFACTURER") "Wuerth") (field (name "TOLERANCE") "±30 %"))
      (libsource (lib "eagle-import") (part "7447714068"))
    )
    (comp (ref "L19")
      (value "744062001")
      (footprint "eagle-import:WE-TPC_6823_WE")
      (fields (field (name "MANUFACTURER") "Wuerth") (field (name "TOLERANCE") "+20 %, -40 %"))
      (libsource (lib "eagle-import") (part "744062001"))
    )
    (comp (ref "L20")
      (value "74279252")
      (footprint "eagle-import:FERRIT_1812_WUERTH")
      (fields (field (name "MANUFACTURER") "Wuerth"))
      (libsource (lib "eagle-import") (part "74279252"))
    )
    (comp (ref "L21")
      (value "744062001")
      (footprint "eagle-import:WE-TPC_6823_WE")
      (fields (field (name "MANUFACTURER") "Wuerth") (field (name "TOLERANCE") "+20 %, -40 %"))
      (libsource (lib "eagle-import") (part "744062001"))
    )
    (comp (ref "L22")
      (value "74279252")
      (footprint "eagle-import:FERRIT_1812_WUERTH")
      (fields (field (name "MANUFACTURER") "Wuerth"))
      (libsource (lib "eagle-import") (part "74279252"))
    )
    (comp (ref "L23")
      (value "744043220")
      (footprint "eagle-import:WE-TPC_4828_WE")
      (fields (field (name "MANUFACTURER") "Wuerth") (field (name "TOLERANCE") "±30 %"))
      (libsource (lib "eagle-import") (part "744043220"))
    )
    (comp (ref "L24")
      (value "744043220")
      (footprint "eagle-import:WE-TPC_4828_WE")
      (fields (field (name "MANUFACTURER") "Wuerth") (field (name "TOLERANCE") "±30 %"))
      (libsource (lib "eagle-import") (part "744043220"))
    )
    (comp (ref "L25")
      (value "742792097")
      (footprint "eagle-import:FERRIT_0805_WUERTH")
      (fields (field (name "MANUFACTURER") "Wuerth"))
      (libsource (lib "eagle-import") (part "742792097"))
    )
    (comp (ref "L26")
      (value "742792097")
      (footprint "eagle-import:FERRIT_0805_WUERTH")
      (fields (field (name "MANUFACTURER") "Wuerth"))
      (libsource (lib "eagle-import") (part "742792097"))
    )
    (comp (ref "L32")
      (value "742792097")
      (footprint "eagle-import:FERRIT_0805_WUERTH")
      (fields (field (name "MANUFACTURER") "Wuerth"))
      (libsource (lib "eagle-import") (part "742792097"))
    )
    (comp (ref "L34")
      (value "744062001")
      (footprint "eagle-import:WE-TPC_6823_WE")
      (fields (field (name "MANUFACTURER") "Wuerth") (field (name "TOLERANCE") "+20 %, -40 %"))
      (libsource (lib "eagle-import") (part "744062001"))
    )
    (comp (ref "L35")
      (value "744062001")
      (footprint "eagle-import:WE-TPC_6823_WE")
      (fields (field (name "MANUFACTURER") "Wuerth") (field (name "TOLERANCE") "+20 %, -40 %"))
      (libsource (lib "eagle-import") (part "744062001"))
    )
    (comp (ref "L38")
      (value "74279252")
      (footprint "eagle-import:FERRIT_1812_WUERTH")
      (fields (field (name "MANUFACTURER") "Wuerth"))
      (libsource (lib "eagle-import") (part "74279252"))
    )
    (comp (ref "L39")
      (value "742792097")
      (footprint "eagle-import:FERRIT_0805_WUERTH")
      (fields (field (name "MANUFACTURER") "Wuerth"))
      (libsource (lib "eagle-import") (part "742792097"))
    )
    (comp (ref "L40")
      (value "n.m.")
      (footprint "eagle-import:WE-KI_0603_WUERTH")
      (fields (field (name "MANUFACTURER") "Wuerth") (field (name "TOLERANCE") "±2 %"))
      (libsource (lib "eagle-import") (part "744761127GA"))
    )
    (comp (ref "L44")
      (value "74279252")
      (footprint "eagle-import:FERRIT_1812_WUERTH")
      (fields (field (name "MANUFACTURER") "Wuerth"))
      (libsource (lib "eagle-import") (part "74279252"))
    )
    (comp (ref "L45")
      (value "74279252")
      (footprint "eagle-import:FERRIT_1812_WUERTH")
      (fields (field (name "MANUFACTURER") "Wuerth"))
      (libsource (lib "eagle-import") (part "74279252"))
    )
    (comp (ref "MOD1")
      (value "2309413-1")
      (footprint "eagle-import:2309413_JETSON_NANO_TE")
      (fields (field (name "MANUFACTURER") "TE Connectivity") (field (name "VOLTAGE") "5.25"))
      (libsource (lib "eagle-import") (part "JETSON_NANO_TX2_NX_XAVIER_NX"))
    )
    (comp (ref "PS1")
      (value "PASSERMARKE")
      (footprint "eagle-import:PASSERMARKE")
      (libsource (lib "eagle-import") (part "PASSERMARKE"))
    )
    (comp (ref "PS2")
      (value "PASSERMARKE")
      (footprint "eagle-import:PASSERMARKE")
      (libsource (lib "eagle-import") (part "PASSERMARKE"))
    )
    (comp (ref "PS3")
      (value "PASSERMARKE")
      (footprint "eagle-import:PASSERMARKE")
      (libsource (lib "eagle-import") (part "PASSERMARKE"))
    )
    (comp (ref "PS4")
      (value "PASSERMARKE")
      (footprint "eagle-import:PASSERMARKE")
      (libsource (lib "eagle-import") (part "PASSERMARKE"))
    )
    (comp (ref "PS5")
      (value "PASSERMARKE")
      (footprint "eagle-import:PASSERMARKE")
      (libsource (lib "eagle-import") (part "PASSERMARKE"))
    )
    (comp (ref "PS6")
      (value "PASSERMARKE")
      (footprint "eagle-import:PASSERMARKE")
      (libsource (lib "eagle-import") (part "PASSERMARKE"))
    )
    (comp (ref "Q1")
      (value "TSX-3225_24.0000MF10Z-C")
      (footprint "eagle-import:TSX-3225_SEIKO_EPSON")
      (fields (field (name "MANUFACTURER") "Epson") (field (name "TOLERANCE") "±10 PPM"))
      (libsource (lib "eagle-import") (part "TSX-3225_24.0000MF10Z-C"))
    )
    (comp (ref "Q2")
      (value "ECS-.327-12.5-12R")
      (footprint "eagle-import:ECX-12R_ECS")
      (fields (field (name "MANUFACTURER") "ECS") (field (name "TOLERANCE") "±20 ppm"))
      (libsource (lib "eagle-import") (part "ECS-.327-12.5-12R"))
    )
    (comp (ref "Q3")
      (value "TSX-3225_24.0000MF10Z-C")
      (footprint "eagle-import:TSX-3225_SEIKO_EPSON")
      (fields (field (name "MANUFACTURER") "Epson") (field (name "TOLERANCE") "±10 PPM"))
      (libsource (lib "eagle-import") (part "TSX-3225_24.0000MF10Z-C"))
    )
    (comp (ref "R1")
      (value "1k8")
      (footprint "eagle-import:R0603")
      (fields
        (field (name "MANUFACTURER") "Stackpole")
        (field (name "POWER") "63 mW")
        (field (name "TOLERANCE") "±1 %")
      )
      (libsource (lib "eagle-import") (part "R-EU-R0603-1K8"))
    )
    (comp (ref "R2")
      (value "100k")
      (footprint "eagle-import:R0603")
      (fields
        (field (name "MANUFACTURER") "Stackpole")
        (field (name "POWER") "63 mW")
        (field (name "TOLERANCE") "±1 %")
      )
      (libsource (lib "eagle-import") (part "R-EU-R0603-100K"))
    )
    (comp (ref "R3")
      (value "0R")
      (footprint "eagle-import:R0603")
      (fields
        (field (name "MANUFACTURER") "Stackpole")
        (field (name "POWER") "63 mW")
        (field (name "VOLTAGE") "50.0 V")
      )
      (libsource (lib "eagle-import") (part "R-EU-R0603-0R"))
    )
    (comp (ref "R4")
      (value "0R")
      (footprint "eagle-import:R0603")
      (fields
        (field (name "MANUFACTURER") "Stackpole")
        (field (name "POWER") "63 mW")
        (field (name "VOLTAGE") "50.0 V")
      )
      (libsource (lib "eagle-import") (part "R-EU-R0603-0R"))
    )
    (comp (ref "R5")
      (value "0R")
      (footprint "eagle-import:R0603")
      (fields
        (field (name "MANUFACTURER") "Stackpole")
        (field (name "POWER") "63 mW")
        (field (name "VOLTAGE") "50.0 V")
      )
      (libsource (lib "eagle-import") (part "R-EU-R0603-0R"))
    )
    (comp (ref "R6")
      (value "27R")
      (footprint "eagle-import:R0603")
      (fields
        (field (name "MANUFACTURER") "Stackpole")
        (field (name "POWER") "63 mW")
        (field (name "TOLERANCE") "±1 %")
      )
      (libsource (lib "eagle-import") (part "R-EU-R0603-27R"))
    )
    (comp (ref "R7")
      (value "100k")
      (footprint "eagle-import:R0603")
      (fields
        (field (name "MANUFACTURER") "Stackpole")
        (field (name "POWER") "63 mW")
        (field (name "TOLERANCE") "±1 %")
      )
      (libsource (lib "eagle-import") (part "R-EU-R0603-100K"))
    )
    (comp (ref "R8")
      (value "100k")
      (footprint "eagle-import:R0603")
      (fields
        (field (name "MANUFACTURER") "Stackpole")
        (field (name "POWER") "63 mW")
        (field (name "TOLERANCE") "±1 %")
      )
      (libsource (lib "eagle-import") (part "R-EU-R0603-100K"))
    )
    (comp (ref "R9")
      (value "12k")
      (footprint "eagle-import:R0603")
      (fields
        (field (name "MANUFACTURER") "Stackpole")
        (field (name "POWER") "63 mW")
        (field (name "TOLERANCE") "±1 %")
      )
      (libsource (lib "eagle-import") (part "R-EU-R0603-12K"))
    )
    (comp (ref "R10")
      (value "0R")
      (footprint "eagle-import:R0603")
      (fields
        (field (name "MANUFACTURER") "Stackpole")
        (field (name "POWER") "63 mW")
        (field (name "VOLTAGE") "50.0 V")
      )
      (libsource (lib "eagle-import") (part "R-EU-R0603-0R"))
    )
    (comp (ref "R11")
      (value "0R")
      (footprint "eagle-import:R0603")
      (fields
        (field (name "MANUFACTURER") "Stackpole")
        (field (name "POWER") "63 mW")
        (field (name "VOLTAGE") "50.0 V")
      )
      (libsource (lib "eagle-import") (part "R-EU-R0603-0R"))
    )
    (comp (ref "R12")
      (value "R-EU-R0603")
      (footprint "eagle-import:R0603")
      (fields
        (field (name "POWER") "63 mW")
        (field (name "TOLERANCE") "±1 %")
        (field (name "VOLTAGE") "50 V")
      )
      (libsource (lib "eagle-import") (part "R-EU-R0603"))
    )
    (comp (ref "R13")
      (value "27R")
      (footprint "eagle-import:R0603")
      (fields
        (field (name "MANUFACTURER") "Stackpole")
        (field (name "POWER") "63 mW")
        (field (name "TOLERANCE") "±1 %")
      )
      (libsource (lib "eagle-import") (part "R-EU-R0603-27R"))
    )
    (comp (ref "R14")
      (value "27R")
      (footprint "eagle-import:R0603")
      (fields
        (field (name "MANUFACTURER") "Stackpole")
        (field (name "POWER") "63 mW")
        (field (name "TOLERANCE") "±1 %")
      )
      (libsource (lib "eagle-import") (part "R-EU-R0603-27R"))
    )
    (comp (ref "R15")
      (value "0R")
      (footprint "eagle-import:R0603")
      (fields
        (field (name "MANUFACTURER") "Stackpole")
        (field (name "POWER") "63 mW")
        (field (name "VOLTAGE") "50.0 V")
      )
      (libsource (lib "eagle-import") (part "R-EU-R0603-0R"))
    )
    (comp (ref "R16")
      (value "R-EU-R0603")
      (footprint "eagle-import:R0603")
      (fields
        (field (name "POWER") "63 mW")
        (field (name "TOLERANCE") "±1 %")
        (field (name "VOLTAGE") "50 V")
      )
      (libsource (lib "eagle-import") (part "R-EU-R0603"))
    )
    (comp (ref "R17")
      (value "27R")
      (footprint "eagle-import:R0603")
      (fields
        (field (name "MANUFACTURER") "Stackpole")
        (field (name "POWER") "63 mW")
        (field (name "TOLERANCE") "±1 %")
      )
      (libsource (lib "eagle-import") (part "R-EU-R0603-27R"))
    )
    (comp (ref "R18")
      (value "27R")
      (footprint "eagle-import:R0603")
      (fields
        (field (name "MANUFACTURER") "Stackpole")
        (field (name "POWER") "63 mW")
        (field (name "TOLERANCE") "±1 %")
      )
      (libsource (lib "eagle-import") (part "R-EU-R0603-27R"))
    )
    (comp (ref "R19")
      (value "27R")
      (footprint "eagle-import:R0603")
      (fields
        (field (name "MANUFACTURER") "Stackpole")
        (field (name "POWER") "63 mW")
        (field (name "TOLERANCE") "±1 %")
      )
      (libsource (lib "eagle-import") (part "R-EU-R0603-27R"))
    )
    (comp (ref "R20")
      (value "27R")
      (footprint "eagle-import:R0603")
      (fields
        (field (name "MANUFACTURER") "Stackpole")
        (field (name "POWER") "63 mW")
        (field (name "TOLERANCE") "±1 %")
      )
      (libsource (lib "eagle-import") (part "R-EU-R0603-27R"))
    )
    (comp (ref "R21")
      (value "27R")
      (footprint "eagle-import:R0603")
      (fields
        (field (name "MANUFACTURER") "Stackpole")
        (field (name "POWER") "63 mW")
        (field (name "TOLERANCE") "±1 %")
      )
      (libsource (lib "eagle-import") (part "R-EU-R0603-27R"))
    )
    (comp (ref "R22")
      (value "27R")
      (footprint "eagle-import:R0603")
      (fields
        (field (name "MANUFACTURER") "Stackpole")
        (field (name "POWER") "63 mW")
        (field (name "TOLERANCE") "±1 %")
      )
      (libsource (lib "eagle-import") (part "R-EU-R0603-27R"))
    )
    (comp (ref "R23")
      (value "27R")
      (footprint "eagle-import:R0603")
      (fields
        (field (name "MANUFACTURER") "Stackpole")
        (field (name "POWER") "63 mW")
        (field (name "TOLERANCE") "±1 %")
      )
      (libsource (lib "eagle-import") (part "R-EU-R0603-27R"))
    )
    (comp (ref "R24")
      (value "27R")
      (footprint "eagle-import:R0603")
      (fields
        (field (name "MANUFACTURER") "Stackpole")
        (field (name "POWER") "63 mW")
        (field (name "TOLERANCE") "±1 %")
      )
      (libsource (lib "eagle-import") (part "R-EU-R0603-27R"))
    )
    (comp (ref "R25")
      (value "0R")
      (footprint "eagle-import:R0603")
      (fields
        (field (name "MANUFACTURER") "Stackpole")
        (field (name "POWER") "63 mW")
        (field (name "VOLTAGE") "50.0 V")
      )
      (libsource (lib "eagle-import") (part "R-EU-R0603-0R"))
    )
    (comp (ref "R26")
      (value "n.m.")
      (footprint "eagle-import:R0402")
      (fields
        (field (name "POWER") "63 mW")
        (field (name "TOLERANCE") "±1 %")
        (field (name "VOLTAGE") "25 V")
      )
      (libsource (lib "eagle-import") (part "R-EU-R0402"))
    )
    (comp (ref "R27")
      (value "100k")
      (footprint "eagle-import:R0603")
      (fields
        (field (name "MANUFACTURER") "Stackpole")
        (field (name "POWER") "63 mW")
        (field (name "TOLERANCE") "±1 %")
      )
      (libsource (lib "eagle-import") (part "R-EU-R0603-100K"))
    )
    (comp (ref "R28")
      (value "27R")
      (footprint "eagle-import:R0603")
      (fields
        (field (name "MANUFACTURER") "Stackpole")
        (field (name "POWER") "63 mW")
        (field (name "TOLERANCE") "±1 %")
      )
      (libsource (lib "eagle-import") (part "R-EU-R0603-27R"))
    )
    (comp (ref "R29")
      (value "27R")
      (footprint "eagle-import:R0603")
      (fields
        (field (name "MANUFACTURER") "Stackpole")
        (field (name "POWER") "63 mW")
        (field (name "TOLERANCE") "±1 %")
      )
      (libsource (lib "eagle-import") (part "R-EU-R0603-27R"))
    )
    (comp (ref "R30")
      (value "100k")
      (footprint "eagle-import:R0603")
      (fields
        (field (name "MANUFACTURER") "Stackpole")
        (field (name "POWER") "63 mW")
        (field (name "TOLERANCE") "±1 %")
      )
      (libsource (lib "eagle-import") (part "R-EU-R0603-100K"))
    )
    (comp (ref "R31")
      (value "27R")
      (footprint "eagle-import:R0603")
      (fields
        (field (name "MANUFACTURER") "Stackpole")
        (field (name "POWER") "63 mW")
        (field (name "TOLERANCE") "±1 %")
      )
      (libsource (lib "eagle-import") (part "R-EU-R0603-27R"))
    )
    (comp (ref "R32")
      (value "442k")
      (footprint "eagle-import:R0603")
      (fields
        (field (name "MANUFACTURER") "Stackpole")
        (field (name "POWER") "63 mW")
        (field (name "TOLERANCE") "±1 %")
      )
      (libsource (lib "eagle-import") (part "R-EU-R0603-442K"))
    )
    (comp (ref "R33")
      (value "43k")
      (footprint "eagle-import:R0603")
      (fields
        (field (name "MANUFACTURER") "Uniroyal")
        (field (name "POWER") "63 mW")
        (field (name "TOLERANCE") "±1 %")
      )
      (libsource (lib "eagle-import") (part "R-EU-R0603-43K"))
    )
    (comp (ref "R34")
      (value "0R")
      (footprint "eagle-import:R0603")
      (fields
        (field (name "MANUFACTURER") "Stackpole")
        (field (name "POWER") "63 mW")
        (field (name "VOLTAGE") "50.0 V")
      )
      (libsource (lib "eagle-import") (part "R-EU-R0603-0R"))
    )
    (comp (ref "R35")
      (value "0R")
      (footprint "eagle-import:R0603")
      (fields
        (field (name "MANUFACTURER") "Stackpole")
        (field (name "POWER") "63 mW")
        (field (name "VOLTAGE") "50.0 V")
      )
      (libsource (lib "eagle-import") (part "R-EU-R0603-0R"))
    )
    (comp (ref "R36")
      (value "100k")
      (footprint "eagle-import:R0603")
      (fields
        (field (name "MANUFACTURER") "Stackpole")
        (field (name "POWER") "63 mW")
        (field (name "TOLERANCE") "±1 %")
      )
      (libsource (lib "eagle-import") (part "R-EU-R0603-100K"))
    )
    (comp (ref "R37")
      (value "27R")
      (footprint "eagle-import:R0603")
      (fields
        (field (name "MANUFACTURER") "Stackpole")
        (field (name "POWER") "63 mW")
        (field (name "TOLERANCE") "±1 %")
      )
      (libsource (lib "eagle-import") (part "R-EU-R0603-27R"))
    )
    (comp (ref "R38")
      (value "3R3")
      (footprint "eagle-import:R1210")
      (fields
        (field (name "MANUFACTURER") "YAGEO")
        (field (name "POWER") "500 mW")
        (field (name "TOLERANCE") "±1 %")
      )
      (libsource (lib "eagle-import") (part "R-EU-R1210-3R3"))
    )
    (comp (ref "R39")
      (value "100k")
      (footprint "eagle-import:R0603")
      (fields
        (field (name "MANUFACTURER") "Stackpole")
        (field (name "POWER") "63 mW")
        (field (name "TOLERANCE") "±1 %")
      )
      (libsource (lib "eagle-import") (part "R-EU-R0603-100K"))
    )
    (comp (ref "R40")
      (value "1k8")
      (footprint "eagle-import:R0603")
      (fields
        (field (name "MANUFACTURER") "Stackpole")
        (field (name "POWER") "63 mW")
        (field (name "TOLERANCE") "±1 %")
      )
      (libsource (lib "eagle-import") (part "R-EU-R0603-1K8"))
    )
    (comp (ref "R41")
      (value "10k")
      (footprint "eagle-import:R0603")
      (fields
        (field (name "MANUFACTURER") "Stackpole")
        (field (name "POWER") "63 mW")
        (field (name "TOLERANCE") "±1 %")
      )
      (libsource (lib "eagle-import") (part "R-EU-R0603-10K"))
    )
    (comp (ref "R42")
      (value "0R")
      (footprint "eagle-import:R0603")
      (fields
        (field (name "MANUFACTURER") "Stackpole")
        (field (name "POWER") "63 mW")
        (field (name "VOLTAGE") "50.0 V")
      )
      (libsource (lib "eagle-import") (part "R-EU-R0603-0R"))
    )
    (comp (ref "R43")
      (value "27R")
      (footprint "eagle-import:R0603")
      (fields
        (field (name "MANUFACTURER") "Stackpole")
        (field (name "POWER") "63 mW")
        (field (name "TOLERANCE") "±1 %")
      )
      (libsource (lib "eagle-import") (part "R-EU-R0603-27R"))
    )
    (comp (ref "R44")
      (value "1k8")
      (footprint "eagle-import:R0603")
      (fields
        (field (name "MANUFACTURER") "Stackpole")
        (field (name "POWER") "63 mW")
        (field (name "TOLERANCE") "±1 %")
      )
      (libsource (lib "eagle-import") (part "R-EU-R0603-1K8"))
    )
    (comp (ref "R45")
      (value "27R")
      (footprint "eagle-import:R0603")
      (fields
        (field (name "MANUFACTURER") "Stackpole")
        (field (name "POWER") "63 mW")
        (field (name "TOLERANCE") "±1 %")
      )
      (libsource (lib "eagle-import") (part "R-EU-R0603-27R"))
    )
    (comp (ref "R46")
      (value "27R")
      (footprint "eagle-import:R0603")
      (fields
        (field (name "MANUFACTURER") "Stackpole")
        (field (name "POWER") "63 mW")
        (field (name "TOLERANCE") "±1 %")
      )
      (libsource (lib "eagle-import") (part "R-EU-R0603-27R"))
    )
    (comp (ref "R47")
      (value "0R")
      (footprint "eagle-import:R0603")
      (fields
        (field (name "MANUFACTURER") "Stackpole")
        (field (name "POWER") "63 mW")
        (field (name "VOLTAGE") "50.0 V")
      )
      (libsource (lib "eagle-import") (part "R-EU-R0603-0R"))
    )
    (comp (ref "R48")
      (value "27R")
      (footprint "eagle-import:R0603")
      (fields
        (field (name "MANUFACTURER") "Stackpole")
        (field (name "POWER") "63 mW")
        (field (name "TOLERANCE") "±1 %")
      )
      (libsource (lib "eagle-import") (part "R-EU-R0603-27R"))
    )
    (comp (ref "R49")
      (value "27R")
      (footprint "eagle-import:R0603")
      (fields
        (field (name "MANUFACTURER") "Stackpole")
        (field (name "POWER") "63 mW")
        (field (name "TOLERANCE") "±1 %")
      )
      (libsource (lib "eagle-import") (part "R-EU-R0603-27R"))
    )
    (comp (ref "R50")
      (value "100k")
      (footprint "eagle-import:R0603")
      (fields
        (field (name "MANUFACTURER") "Stackpole")
        (field (name "POWER") "63 mW")
        (field (name "TOLERANCE") "±1 %")
      )
      (libsource (lib "eagle-import") (part "R-EU-R0603-100K"))
    )
    (comp (ref "R51")
      (value "27R")
      (footprint "eagle-import:R0603")
      (fields
        (field (name "MANUFACTURER") "Stackpole")
        (field (name "POWER") "63 mW")
        (field (name "TOLERANCE") "±1 %")
      )
      (libsource (lib "eagle-import") (part "R-EU-R0603-27R"))
    )
    (comp (ref "R52")
      (value "27R")
      (footprint "eagle-import:R0603")
      (fields
        (field (name "MANUFACTURER") "Stackpole")
        (field (name "POWER") "63 mW")
        (field (name "TOLERANCE") "±1 %")
      )
      (libsource (lib "eagle-import") (part "R-EU-R0603-27R"))
    )
    (comp (ref "R53")
      (value "27R")
      (footprint "eagle-import:R0603")
      (fields
        (field (name "MANUFACTURER") "Stackpole")
        (field (name "POWER") "63 mW")
        (field (name "TOLERANCE") "±1 %")
      )
      (libsource (lib "eagle-import") (part "R-EU-R0603-27R"))
    )
    (comp (ref "R54")
      (value "27R")
      (footprint "eagle-import:R0603")
      (fields
        (field (name "MANUFACTURER") "Stackpole")
        (field (name "POWER") "63 mW")
        (field (name "TOLERANCE") "±1 %")
      )
      (libsource (lib "eagle-import") (part "R-EU-R0603-27R"))
    )
    (comp (ref "R55")
      (value "27R")
      (footprint "eagle-import:R0603")
      (fields
        (field (name "MANUFACTURER") "Stackpole")
        (field (name "POWER") "63 mW")
        (field (name "TOLERANCE") "±1 %")
      )
      (libsource (lib "eagle-import") (part "R-EU-R0603-27R"))
    )
    (comp (ref "R56")
      (value "3R3")
      (footprint "eagle-import:R1210")
      (fields
        (field (name "MANUFACTURER") "YAGEO")
        (field (name "POWER") "500 mW")
        (field (name "TOLERANCE") "±1 %")
      )
      (libsource (lib "eagle-import") (part "R-EU-R1210-3R3"))
    )
    (comp (ref "R57")
      (value "27R")
      (footprint "eagle-import:R0603")
      (fields
        (field (name "MANUFACTURER") "Stackpole")
        (field (name "POWER") "63 mW")
        (field (name "TOLERANCE") "±1 %")
      )
      (libsource (lib "eagle-import") (part "R-EU-R0603-27R"))
    )
    (comp (ref "R58")
      (value "10k")
      (footprint "eagle-import:R0603")
      (fields
        (field (name "MANUFACTURER") "Stackpole")
        (field (name "POWER") "63 mW")
        (field (name "TOLERANCE") "±1 %")
      )
      (libsource (lib "eagle-import") (part "R-EU-R0603-10K"))
    )
    (comp (ref "R59")
      (value "100k")
      (footprint "eagle-import:R0603")
      (fields
        (field (name "MANUFACTURER") "Stackpole")
        (field (name "POWER") "63 mW")
        (field (name "TOLERANCE") "±1 %")
      )
      (libsource (lib "eagle-import") (part "R-EU-R0603-100K"))
    )
    (comp (ref "R60")
      (value "R-EU-R0603")
      (footprint "eagle-import:R0603")
      (fields
        (field (name "POWER") "63 mW")
        (field (name "TOLERANCE") "±1 %")
        (field (name "VOLTAGE") "50 V")
      )
      (libsource (lib "eagle-import") (part "R-EU-R0603"))
    )
    (comp (ref "R61")
      (value "0R")
      (footprint "eagle-import:R0603")
      (fields
        (field (name "MANUFACTURER") "Stackpole")
        (field (name "POWER") "63 mW")
        (field (name "VOLTAGE") "50.0 V")
      )
      (libsource (lib "eagle-import") (part "R-EU-R0603-0R"))
    )
    (comp (ref "R62")
      (value "27R")
      (footprint "eagle-import:R0603")
      (fields
        (field (name "MANUFACTURER") "Stackpole")
        (field (name "POWER") "63 mW")
        (field (name "TOLERANCE") "±1 %")
      )
      (libsource (lib "eagle-import") (part "R-EU-R0603-27R"))
    )
    (comp (ref "R63")
      (value "100k")
      (footprint "eagle-import:R0603")
      (fields
        (field (name "MANUFACTURER") "Stackpole")
        (field (name "POWER") "63 mW")
        (field (name "TOLERANCE") "±1 %")
      )
      (libsource (lib "eagle-import") (part "R-EU-R0603-100K"))
    )
    (comp (ref "R64")
      (value "1k8")
      (footprint "eagle-import:R0603")
      (fields
        (field (name "MANUFACTURER") "Stackpole")
        (field (name "POWER") "63 mW")
        (field (name "TOLERANCE") "±1 %")
      )
      (libsource (lib "eagle-import") (part "R-EU-R0603-1K8"))
    )
    (comp (ref "R65")
      (value "0R")
      (footprint "eagle-import:R0603")
      (fields
        (field (name "MANUFACTURER") "Stackpole")
        (field (name "POWER") "63 mW")
        (field (name "VOLTAGE") "50.0 V")
      )
      (libsource (lib "eagle-import") (part "R-EU-R0603-0R"))
    )
    (comp (ref "R66")
      (value "27R")
      (footprint "eagle-import:R0603")
      (fields
        (field (name "MANUFACTURER") "Stackpole")
        (field (name "POWER") "63 mW")
        (field (name "TOLERANCE") "±1 %")
      )
      (libsource (lib "eagle-import") (part "R-EU-R0603-27R"))
    )
    (comp (ref "R67")
      (value "27R")
      (footprint "eagle-import:R0603")
      (fields
        (field (name "MANUFACTURER") "Stackpole")
        (field (name "POWER") "63 mW")
        (field (name "TOLERANCE") "±1 %")
      )
      (libsource (lib "eagle-import") (part "R-EU-R0603-27R"))
    )
    (comp (ref "R68")
      (value "27R")
      (footprint "eagle-import:R0603")
      (fields
        (field (name "MANUFACTURER") "Stackpole")
        (field (name "POWER") "63 mW")
        (field (name "TOLERANCE") "±1 %")
      )
      (libsource (lib "eagle-import") (part "R-EU-R0603-27R"))
    )
    (comp (ref "R69")
      (value "27R")
      (footprint "eagle-import:R0603")
      (fields
        (field (name "MANUFACTURER") "Stackpole")
        (field (name "POWER") "63 mW")
        (field (name "TOLERANCE") "±1 %")
      )
      (libsource (lib "eagle-import") (part "R-EU-R0603-27R"))
    )
    (comp (ref "R70")
      (value "27R")
      (footprint "eagle-import:R0603")
      (fields
        (field (name "MANUFACTURER") "Stackpole")
        (field (name "POWER") "63 mW")
        (field (name "TOLERANCE") "±1 %")
      )
      (libsource (lib "eagle-import") (part "R-EU-R0603-27R"))
    )
    (comp (ref "R71")
      (value "47k 0.1%")
      (footprint "eagle-import:R0603")
      (fields
        (field (name "MANUFACTURER") "YAGEO")
        (field (name "POWER") "63 mW")
        (field (name "TOLERANCE") "±0.1 %")
      )
      (libsource (lib "eagle-import") (part "R-EU-R0603-47K-0P1"))
    )
    (comp (ref "R72")
      (value "1k8")
      (footprint "eagle-import:R0603")
      (fields
        (field (name "MANUFACTURER") "Stackpole")
        (field (name "POWER") "63 mW")
        (field (name "TOLERANCE") "±1 %")
      )
      (libsource (lib "eagle-import") (part "R-EU-R0603-1K8"))
    )
    (comp (ref "R73")
      (value "27R")
      (footprint "eagle-import:R0603")
      (fields
        (field (name "MANUFACTURER") "Stackpole")
        (field (name "POWER") "63 mW")
        (field (name "TOLERANCE") "±1 %")
      )
      (libsource (lib "eagle-import") (part "R-EU-R0603-27R"))
    )
    (comp (ref "R74")
      (value "27R")
      (footprint "eagle-import:R0603")
      (fields
        (field (name "MANUFACTURER") "Stackpole")
        (field (name "POWER") "63 mW")
        (field (name "TOLERANCE") "±1 %")
      )
      (libsource (lib "eagle-import") (part "R-EU-R0603-27R"))
    )
    (comp (ref "R75")
      (value "4R7")
      (footprint "eagle-import:R0402")
      (fields
        (field (name "MANUFACTURER") "Stackpole")
        (field (name "POWER") "63 mW")
        (field (name "TOLERANCE") "±1 %")
      )
      (libsource (lib "eagle-import") (part "R-EU-R0402-4R7"))
    )
    (comp (ref "R76")
      (value "R-EU-R0603")
      (footprint "eagle-import:R0603")
      (fields
        (field (name "POWER") "63 mW")
        (field (name "TOLERANCE") "±1 %")
        (field (name "VOLTAGE") "50 V")
      )
      (libsource (lib "eagle-import") (part "R-EU-R0603"))
    )
    (comp (ref "R77")
      (value "4R7")
      (footprint "eagle-import:R0402")
      (fields
        (field (name "MANUFACTURER") "Stackpole")
        (field (name "POWER") "63 mW")
        (field (name "TOLERANCE") "±1 %")
      )
      (libsource (lib "eagle-import") (part "R-EU-R0402-4R7"))
    )
    (comp (ref "R78")
      (value "3R3")
      (footprint "eagle-import:R1210")
      (fields
        (field (name "MANUFACTURER") "YAGEO")
        (field (name "POWER") "500 mW")
        (field (name "TOLERANCE") "±1 %")
      )
      (libsource (lib "eagle-import") (part "R-EU-R1210-3R3"))
    )
    (comp (ref "R79")
      (value "4R7")
      (footprint "eagle-import:R0402")
      (fields
        (field (name "MANUFACTURER") "Stackpole")
        (field (name "POWER") "63 mW")
        (field (name "TOLERANCE") "±1 %")
      )
      (libsource (lib "eagle-import") (part "R-EU-R0402-4R7"))
    )
    (comp (ref "R80")
      (value "3R3")
      (footprint "eagle-import:R1210")
      (fields
        (field (name "MANUFACTURER") "YAGEO")
        (field (name "POWER") "500 mW")
        (field (name "TOLERANCE") "±1 %")
      )
      (libsource (lib "eagle-import") (part "R-EU-R1210-3R3"))
    )
    (comp (ref "R81")
      (value "27R")
      (footprint "eagle-import:R0603")
      (fields
        (field (name "MANUFACTURER") "Stackpole")
        (field (name "POWER") "63 mW")
        (field (name "TOLERANCE") "±1 %")
      )
      (libsource (lib "eagle-import") (part "R-EU-R0603-27R"))
    )
    (comp (ref "R82")
      (value "R-EU-R0603")
      (footprint "eagle-import:R0603")
      (fields
        (field (name "POWER") "63 mW")
        (field (name "TOLERANCE") "±1 %")
        (field (name "VOLTAGE") "50 V")
      )
      (libsource (lib "eagle-import") (part "R-EU-R0603"))
    )
    (comp (ref "R83")
      (value "27R")
      (footprint "eagle-import:R0603")
      (fields
        (field (name "MANUFACTURER") "Stackpole")
        (field (name "POWER") "63 mW")
        (field (name "TOLERANCE") "±1 %")
      )
      (libsource (lib "eagle-import") (part "R-EU-R0603-27R"))
    )
    (comp (ref "R84")
      (value "442k")
      (footprint "eagle-import:R0603")
      (fields
        (field (name "MANUFACTURER") "Stackpole")
        (field (name "POWER") "63 mW")
        (field (name "TOLERANCE") "±1 %")
      )
      (libsource (lib "eagle-import") (part "R-EU-R0603-442K"))
    )
    (comp (ref "R85")
      (value "100k")
      (footprint "eagle-import:R0603")
      (fields
        (field (name "MANUFACTURER") "Stackpole")
        (field (name "POWER") "63 mW")
        (field (name "TOLERANCE") "±1 %")
      )
      (libsource (lib "eagle-import") (part "R-EU-R0603-100K"))
    )
    (comp (ref "R86")
      (value "4R7")
      (footprint "eagle-import:R0402")
      (fields
        (field (name "MANUFACTURER") "Stackpole")
        (field (name "POWER") "63 mW")
        (field (name "TOLERANCE") "±1 %")
      )
      (libsource (lib "eagle-import") (part "R-EU-R0402-4R7"))
    )
    (comp (ref "R87")
      (value "4R7")
      (footprint "eagle-import:R0402")
      (fields
        (field (name "MANUFACTURER") "Stackpole")
        (field (name "POWER") "63 mW")
        (field (name "TOLERANCE") "±1 %")
      )
      (libsource (lib "eagle-import") (part "R-EU-R0402-4R7"))
    )
    (comp (ref "R88")
      (value "4R7")
      (footprint "eagle-import:R0402")
      (fields
        (field (name "MANUFACTURER") "Stackpole")
        (field (name "POWER") "63 mW")
        (field (name "TOLERANCE") "±1 %")
      )
      (libsource (lib "eagle-import") (part "R-EU-R0402-4R7"))
    )
    (comp (ref "R89")
      (value "4R7")
      (footprint "eagle-import:R0402")
      (fields
        (field (name "MANUFACTURER") "Stackpole")
        (field (name "POWER") "63 mW")
        (field (name "TOLERANCE") "±1 %")
      )
      (libsource (lib "eagle-import") (part "R-EU-R0402-4R7"))
    )
    (comp (ref "R90")
      (value "4R7")
      (footprint "eagle-import:R0402")
      (fields
        (field (name "MANUFACTURER") "Stackpole")
        (field (name "POWER") "63 mW")
        (field (name "TOLERANCE") "±1 %")
      )
      (libsource (lib "eagle-import") (part "R-EU-R0402-4R7"))
    )
    (comp (ref "R91")
      (value "499R")
      (footprint "eagle-import:R0402")
      (fields
        (field (name "MANUFACTURER") "YAGEO")
        (field (name "POWER") "63 mW")
        (field (name "TOLERANCE") "±1 %")
      )
      (libsource (lib "eagle-import") (part "R-EU-R0402-499R"))
    )
    (comp (ref "R92")
      (value "0R")
      (footprint "eagle-import:R0603")
      (fields
        (field (name "MANUFACTURER") "Stackpole")
        (field (name "POWER") "63 mW")
        (field (name "VOLTAGE") "50.0 V")
      )
      (libsource (lib "eagle-import") (part "R-EU-R0603-0R"))
    )
    (comp (ref "R93")
      (value "R-EU-R0603")
      (footprint "eagle-import:R0603")
      (fields
        (field (name "POWER") "63 mW")
        (field (name "TOLERANCE") "±1 %")
        (field (name "VOLTAGE") "50 V")
      )
      (libsource (lib "eagle-import") (part "R-EU-R0603"))
    )
    (comp (ref "R94")
      (value "27R")
      (footprint "eagle-import:R0603")
      (fields
        (field (name "MANUFACTURER") "Stackpole")
        (field (name "POWER") "63 mW")
        (field (name "TOLERANCE") "±1 %")
      )
      (libsource (lib "eagle-import") (part "R-EU-R0603-27R"))
    )
    (comp (ref "R95")
      (value "100k")
      (footprint "eagle-import:R0603")
      (fields
        (field (name "MANUFACTURER") "Stackpole")
        (field (name "POWER") "63 mW")
        (field (name "TOLERANCE") "±1 %")
      )
      (libsource (lib "eagle-import") (part "R-EU-R0603-100K"))
    )
    (comp (ref "R96")
      (value "27R")
      (footprint "eagle-import:R0603")
      (fields
        (field (name "MANUFACTURER") "Stackpole")
        (field (name "POWER") "63 mW")
        (field (name "TOLERANCE") "±1 %")
      )
      (libsource (lib "eagle-import") (part "R-EU-R0603-27R"))
    )
    (comp (ref "R97")
      (value "499R")
      (footprint "eagle-import:R0402")
      (fields
        (field (name "MANUFACTURER") "YAGEO")
        (field (name "POWER") "63 mW")
        (field (name "TOLERANCE") "±1 %")
      )
      (libsource (lib "eagle-import") (part "R-EU-R0402-499R"))
    )
    (comp (ref "R98")
      (value "442k")
      (footprint "eagle-import:R0603")
      (fields
        (field (name "MANUFACTURER") "Stackpole")
        (field (name "POWER") "63 mW")
        (field (name "TOLERANCE") "±1 %")
      )
      (libsource (lib "eagle-import") (part "R-EU-R0603-442K"))
    )
    (comp (ref "R99")
      (value "27R")
      (footprint "eagle-import:R0603")
      (fields
        (field (name "MANUFACTURER") "Stackpole")
        (field (name "POWER") "63 mW")
        (field (name "TOLERANCE") "±1 %")
      )
      (libsource (lib "eagle-import") (part "R-EU-R0603-27R"))
    )
    (comp (ref "R100")
      (value "100k")
      (footprint "eagle-import:R0603")
      (fields
        (field (name "MANUFACTURER") "Stackpole")
        (field (name "POWER") "63 mW")
        (field (name "TOLERANCE") "±1 %")
      )
      (libsource (lib "eagle-import") (part "R-EU-R0603-100K"))
    )
    (comp (ref "R101")
      (value "100k")
      (footprint "eagle-import:R0603")
      (fields
        (field (name "MANUFACTURER") "Stackpole")
        (field (name "POWER") "63 mW")
        (field (name "TOLERANCE") "±1 %")
      )
      (libsource (lib "eagle-import") (part "R-EU-R0603-100K"))
    )
    (comp (ref "R102")
      (value "100k")
      (footprint "eagle-import:R0603")
      (fields
        (field (name "MANUFACTURER") "Stackpole")
        (field (name "POWER") "63 mW")
        (field (name "TOLERANCE") "±1 %")
      )
      (libsource (lib "eagle-import") (part "R-EU-R0603-100K"))
    )
    (comp (ref "R103")
      (value "47k 0.1%")
      (footprint "eagle-import:R0603")
      (fields
        (field (name "MANUFACTURER") "YAGEO")
        (field (name "POWER") "63 mW")
        (field (name "TOLERANCE") "±0.1 %")
      )
      (libsource (lib "eagle-import") (part "R-EU-R0603-47K-0P1"))
    )
    (comp (ref "R104")
      (value "27R")
      (footprint "eagle-import:R0603")
      (fields
        (field (name "MANUFACTURER") "Stackpole")
        (field (name "POWER") "63 mW")
        (field (name "TOLERANCE") "±1 %")
      )
      (libsource (lib "eagle-import") (part "R-EU-R0603-27R"))
    )
    (comp (ref "R105")
      (value "100k")
      (footprint "eagle-import:R0603")
      (fields
        (field (name "MANUFACTURER") "Stackpole")
        (field (name "POWER") "63 mW")
        (field (name "TOLERANCE") "±1 %")
      )
      (libsource (lib "eagle-import") (part "R-EU-R0603-100K"))
    )
    (comp (ref "R106")
      (value "100k")
      (footprint "eagle-import:R0603")
      (fields
        (field (name "MANUFACTURER") "Stackpole")
        (field (name "POWER") "63 mW")
        (field (name "TOLERANCE") "±1 %")
      )
      (libsource (lib "eagle-import") (part "R-EU-R0603-100K"))
    )
    (comp (ref "R107")
      (value "27R")
      (footprint "eagle-import:R0603")
      (fields
        (field (name "MANUFACTURER") "Stackpole")
        (field (name "POWER") "63 mW")
        (field (name "TOLERANCE") "±1 %")
      )
      (libsource (lib "eagle-import") (part "R-EU-R0603-27R"))
    )
    (comp (ref "R108")
      (value "0R")
      (footprint "eagle-import:R0603")
      (fields
        (field (name "MANUFACTURER") "Stackpole")
        (field (name "POWER") "63 mW")
        (field (name "VOLTAGE") "50.0 V")
      )
      (libsource (lib "eagle-import") (part "R-EU-R0603-0R"))
    )
    (comp (ref "R109")
      (value "R-EU-R0603")
      (footprint "eagle-import:R0603")
      (fields
        (field (name "POWER") "63 mW")
        (field (name "TOLERANCE") "±1 %")
        (field (name "VOLTAGE") "50 V")
      )
      (libsource (lib "eagle-import") (part "R-EU-R0603"))
    )
    (comp (ref "R110")
      (value "100k")
      (footprint "eagle-import:R0603")
      (fields
        (field (name "MANUFACTURER") "Stackpole")
        (field (name "POWER") "63 mW")
        (field (name "TOLERANCE") "±1 %")
      )
      (libsource (lib "eagle-import") (part "R-EU-R0603-100K"))
    )
    (comp (ref "R111")
      (value "R-EU-R0603")
      (footprint "eagle-import:R0603")
      (fields
        (field (name "POWER") "63 mW")
        (field (name "TOLERANCE") "±1 %")
        (field (name "VOLTAGE") "50 V")
      )
      (libsource (lib "eagle-import") (part "R-EU-R0603"))
    )
    (comp (ref "R112")
      (value "43k")
      (footprint "eagle-import:R0603")
      (fields
        (field (name "MANUFACTURER") "Uniroyal")
        (field (name "POWER") "63 mW")
        (field (name "TOLERANCE") "±1 %")
      )
      (libsource (lib "eagle-import") (part "R-EU-R0603-43K"))
    )
    (comp (ref "R113")
      (value "0R")
      (footprint "eagle-import:R0603")
      (fields
        (field (name "MANUFACTURER") "Stackpole")
        (field (name "POWER") "63 mW")
        (field (name "VOLTAGE") "50.0 V")
      )
      (libsource (lib "eagle-import") (part "R-EU-R0603-0R"))
    )
    (comp (ref "R114")
      (value "27R")
      (footprint "eagle-import:R0603")
      (fields
        (field (name "MANUFACTURER") "Stackpole")
        (field (name "POWER") "63 mW")
        (field (name "TOLERANCE") "±1 %")
      )
      (libsource (lib "eagle-import") (part "R-EU-R0603-27R"))
    )
    (comp (ref "R115")
      (value "27R")
      (footprint "eagle-import:R0603")
      (fields
        (field (name "MANUFACTURER") "Stackpole")
        (field (name "POWER") "63 mW")
        (field (name "TOLERANCE") "±1 %")
      )
      (libsource (lib "eagle-import") (part "R-EU-R0603-27R"))
    )
    (comp (ref "R116")
      (value "100k")
      (footprint "eagle-import:R0603")
      (fields
        (field (name "MANUFACTURER") "Stackpole")
        (field (name "POWER") "63 mW")
        (field (name "TOLERANCE") "±1 %")
      )
      (libsource (lib "eagle-import") (part "R-EU-R0603-100K"))
    )
    (comp (ref "R117")
      (value "27R")
      (footprint "eagle-import:R0603")
      (fields
        (field (name "MANUFACTURER") "Stackpole")
        (field (name "POWER") "63 mW")
        (field (name "TOLERANCE") "±1 %")
      )
      (libsource (lib "eagle-import") (part "R-EU-R0603-27R"))
    )
    (comp (ref "R118")
      (value "27R")
      (footprint "eagle-import:R0603")
      (fields
        (field (name "MANUFACTURER") "Stackpole")
        (field (name "POWER") "63 mW")
        (field (name "TOLERANCE") "±1 %")
      )
      (libsource (lib "eagle-import") (part "R-EU-R0603-27R"))
    )
    (comp (ref "R119")
      (value "27R")
      (footprint "eagle-import:R0603")
      (fields
        (field (name "MANUFACTURER") "Stackpole")
        (field (name "POWER") "63 mW")
        (field (name "TOLERANCE") "±1 %")
      )
      (libsource (lib "eagle-import") (part "R-EU-R0603-27R"))
    )
    (comp (ref "R120")
      (value "R-EU-R0603")
      (footprint "eagle-import:R0603")
      (fields
        (field (name "POWER") "63 mW")
        (field (name "TOLERANCE") "±1 %")
        (field (name "VOLTAGE") "50 V")
      )
      (libsource (lib "eagle-import") (part "R-EU-R0603"))
    )
    (comp (ref "R121")
      (value "10k")
      (footprint "eagle-import:R0603")
      (fields
        (field (name "MANUFACTURER") "Stackpole")
        (field (name "POWER") "63 mW")
        (field (name "TOLERANCE") "±1 %")
      )
      (libsource (lib "eagle-import") (part "R-EU-R0603-10K"))
    )
    (comp (ref "R122")
      (value "10k")
      (footprint "eagle-import:R0603")
      (fields
        (field (name "MANUFACTURER") "Stackpole")
        (field (name "POWER") "63 mW")
        (field (name "TOLERANCE") "±1 %")
      )
      (libsource (lib "eagle-import") (part "R-EU-R0603-10K"))
    )
    (comp (ref "R123")
      (value "100k")
      (footprint "eagle-import:R0603")
      (fields
        (field (name "MANUFACTURER") "Stackpole")
        (field (name "POWER") "63 mW")
        (field (name "TOLERANCE") "±1 %")
      )
      (libsource (lib "eagle-import") (part "R-EU-R0603-100K"))
    )
    (comp (ref "R124")
      (value "27R")
      (footprint "eagle-import:R0603")
      (fields
        (field (name "MANUFACTURER") "Stackpole")
        (field (name "POWER") "63 mW")
        (field (name "TOLERANCE") "±1 %")
      )
      (libsource (lib "eagle-import") (part "R-EU-R0603-27R"))
    )
    (comp (ref "R125")
      (value "27R")
      (footprint "eagle-import:R0603")
      (fields
        (field (name "MANUFACTURER") "Stackpole")
        (field (name "POWER") "63 mW")
        (field (name "TOLERANCE") "±1 %")
      )
      (libsource (lib "eagle-import") (part "R-EU-R0603-27R"))
    )
    (comp (ref "R126")
      (value "27R")
      (footprint "eagle-import:R0603")
      (fields
        (field (name "MANUFACTURER") "Stackpole")
        (field (name "POWER") "63 mW")
        (field (name "TOLERANCE") "±1 %")
      )
      (libsource (lib "eagle-import") (part "R-EU-R0603-27R"))
    )
    (comp (ref "R127")
      (value "27R")
      (footprint "eagle-import:R0603")
      (fields
        (field (name "MANUFACTURER") "Stackpole")
        (field (name "POWER") "63 mW")
        (field (name "TOLERANCE") "±1 %")
      )
      (libsource (lib "eagle-import") (part "R-EU-R0603-27R"))
    )
    (comp (ref "R128")
      (value "10k")
      (footprint "eagle-import:R0603")
      (fields
        (field (name "MANUFACTURER") "Stackpole")
        (field (name "POWER") "63 mW")
        (field (name "TOLERANCE") "±1 %")
      )
      (libsource (lib "eagle-import") (part "R-EU-R0603-10K"))
    )
    (comp (ref "R129")
      (value "10k")
      (footprint "eagle-import:R0603")
      (fields
        (field (name "MANUFACTURER") "Stackpole")
        (field (name "POWER") "63 mW")
        (field (name "TOLERANCE") "±1 %")
      )
      (libsource (lib "eagle-import") (part "R-EU-R0603-10K"))
    )
    (comp (ref "R130")
      (value "4R7")
      (footprint "eagle-import:R0402")
      (fields
        (field (name "MANUFACTURER") "Stackpole")
        (field (name "POWER") "63 mW")
        (field (name "TOLERANCE") "±1 %")
      )
      (libsource (lib "eagle-import") (part "R-EU-R0402-4R7"))
    )
    (comp (ref "R131")
      (value "4R7")
      (footprint "eagle-import:R0402")
      (fields
        (field (name "MANUFACTURER") "Stackpole")
        (field (name "POWER") "63 mW")
        (field (name "TOLERANCE") "±1 %")
      )
      (libsource (lib "eagle-import") (part "R-EU-R0402-4R7"))
    )
    (comp (ref "R132")
      (value "R-EU-R0603")
      (footprint "eagle-import:R0603")
      (fields
        (field (name "POWER") "63 mW")
        (field (name "TOLERANCE") "±1 %")
        (field (name "VOLTAGE") "50 V")
      )
      (libsource (lib "eagle-import") (part "R-EU-R0603"))
    )
    (comp (ref "R133")
      (value "100k")
      (footprint "eagle-import:R0603")
      (fields
        (field (name "MANUFACTURER") "Stackpole")
        (field (name "POWER") "63 mW")
        (field (name "TOLERANCE") "±1 %")
      )
      (libsource (lib "eagle-import") (part "R-EU-R0603-100K"))
    )
    (comp (ref "R134")
      (value "27R")
      (footprint "eagle-import:R0603")
      (fields
        (field (name "MANUFACTURER") "Stackpole")
        (field (name "POWER") "63 mW")
        (field (name "TOLERANCE") "±1 %")
      )
      (libsource (lib "eagle-import") (part "R-EU-R0603-27R"))
    )
    (comp (ref "R135")
      (value "100k")
      (footprint "eagle-import:R0603")
      (fields
        (field (name "MANUFACTURER") "Stackpole")
        (field (name "POWER") "63 mW")
        (field (name "TOLERANCE") "±1 %")
      )
      (libsource (lib "eagle-import") (part "R-EU-R0603-100K"))
    )
    (comp (ref "R136")
      (value "27R")
      (footprint "eagle-import:R0603")
      (fields
        (field (name "MANUFACTURER") "Stackpole")
        (field (name "POWER") "63 mW")
        (field (name "TOLERANCE") "±1 %")
      )
      (libsource (lib "eagle-import") (part "R-EU-R0603-27R"))
    )
    (comp (ref "R137")
      (value "4R7")
      (footprint "eagle-import:R0402")
      (fields
        (field (name "MANUFACTURER") "Stackpole")
        (field (name "POWER") "63 mW")
        (field (name "TOLERANCE") "±1 %")
      )
      (libsource (lib "eagle-import") (part "R-EU-R0402-4R7"))
    )
    (comp (ref "R138")
      (value "27R")
      (footprint "eagle-import:R0603")
      (fields
        (field (name "MANUFACTURER") "Stackpole")
        (field (name "POWER") "63 mW")
        (field (name "TOLERANCE") "±1 %")
      )
      (libsource (lib "eagle-import") (part "R-EU-R0603-27R"))
    )
    (comp (ref "R139")
      (value "100k")
      (footprint "eagle-import:R0603")
      (fields
        (field (name "MANUFACTURER") "Stackpole")
        (field (name "POWER") "63 mW")
        (field (name "TOLERANCE") "±1 %")
      )
      (libsource (lib "eagle-import") (part "R-EU-R0603-100K"))
    )
    (comp (ref "R140")
      (value "0R")
      (footprint "eagle-import:R0603")
      (fields
        (field (name "MANUFACTURER") "Stackpole")
        (field (name "POWER") "63 mW")
        (field (name "VOLTAGE") "50.0 V")
      )
      (libsource (lib "eagle-import") (part "R-EU-R0603-0R"))
    )
    (comp (ref "R141")
      (value "27R")
      (footprint "eagle-import:R0603")
      (fields
        (field (name "MANUFACTURER") "Stackpole")
        (field (name "POWER") "63 mW")
        (field (name "TOLERANCE") "±1 %")
      )
      (libsource (lib "eagle-import") (part "R-EU-R0603-27R"))
    )
    (comp (ref "R142")
      (value "27R")
      (footprint "eagle-import:R0603")
      (fields
        (field (name "MANUFACTURER") "Stackpole")
        (field (name "POWER") "63 mW")
        (field (name "TOLERANCE") "±1 %")
      )
      (libsource (lib "eagle-import") (part "R-EU-R0603-27R"))
    )
    (comp (ref "R143")
      (value "499R")
      (footprint "eagle-import:R0402")
      (fields
        (field (name "MANUFACTURER") "YAGEO")
        (field (name "POWER") "63 mW")
        (field (name "TOLERANCE") "±1 %")
      )
      (libsource (lib "eagle-import") (part "R-EU-R0402-499R"))
    )
    (comp (ref "R144")
      (value "499R")
      (footprint "eagle-import:R0402")
      (fields
        (field (name "MANUFACTURER") "YAGEO")
        (field (name "POWER") "63 mW")
        (field (name "TOLERANCE") "±1 %")
      )
      (libsource (lib "eagle-import") (part "R-EU-R0402-499R"))
    )
    (comp (ref "R145")
      (value "499R")
      (footprint "eagle-import:R0402")
      (fields
        (field (name "MANUFACTURER") "YAGEO")
        (field (name "POWER") "63 mW")
        (field (name "TOLERANCE") "±1 %")
      )
      (libsource (lib "eagle-import") (part "R-EU-R0402-499R"))
    )
    (comp (ref "R146")
      (value "499R")
      (footprint "eagle-import:R0402")
      (fields
        (field (name "MANUFACTURER") "YAGEO")
        (field (name "POWER") "63 mW")
        (field (name "TOLERANCE") "±1 %")
      )
      (libsource (lib "eagle-import") (part "R-EU-R0402-499R"))
    )
    (comp (ref "R147")
      (value "27R")
      (footprint "eagle-import:R0603")
      (fields
        (field (name "MANUFACTURER") "Stackpole")
        (field (name "POWER") "63 mW")
        (field (name "TOLERANCE") "±1 %")
      )
      (libsource (lib "eagle-import") (part "R-EU-R0603-27R"))
    )
    (comp (ref "R148")
      (value "0R")
      (footprint "eagle-import:R0603")
      (fields
        (field (name "MANUFACTURER") "Stackpole")
        (field (name "POWER") "63 mW")
        (field (name "VOLTAGE") "50.0 V")
      )
      (libsource (lib "eagle-import") (part "R-EU-R0603-0R"))
    )
    (comp (ref "R149")
      (value "100k")
      (footprint "eagle-import:R0603")
      (fields
        (field (name "MANUFACTURER") "Stackpole")
        (field (name "POWER") "63 mW")
        (field (name "TOLERANCE") "±1 %")
      )
      (libsource (lib "eagle-import") (part "R-EU-R0603-100K"))
    )
    (comp (ref "R150")
      (value "27R")
      (footprint "eagle-import:R0603")
      (fields
        (field (name "MANUFACTURER") "Stackpole")
        (field (name "POWER") "63 mW")
        (field (name "TOLERANCE") "±1 %")
      )
      (libsource (lib "eagle-import") (part "R-EU-R0603-27R"))
    )
    (comp (ref "R151")
      (value "10k 0.1%")
      (footprint "eagle-import:R0603")
      (fields
        (field (name "MANUFACTURER") "KOA Speer")
        (field (name "POWER") "63 mW")
        (field (name "TOLERANCE") "±0.1 %")
      )
      (libsource (lib "eagle-import") (part "R-EU-R0603-10K-0P1"))
    )
    (comp (ref "R152")
      (value "10k 0.1%")
      (footprint "eagle-import:R0603")
      (fields
        (field (name "MANUFACTURER") "KOA Speer")
        (field (name "POWER") "63 mW")
        (field (name "TOLERANCE") "±0.1 %")
      )
      (libsource (lib "eagle-import") (part "R-EU-R0603-10K-0P1"))
    )
    (comp (ref "R153")
      (value "499R")
      (footprint "eagle-import:R0402")
      (fields
        (field (name "MANUFACTURER") "YAGEO")
        (field (name "POWER") "63 mW")
        (field (name "TOLERANCE") "±1 %")
      )
      (libsource (lib "eagle-import") (part "R-EU-R0402-499R"))
    )
    (comp (ref "R154")
      (value "499R")
      (footprint "eagle-import:R0402")
      (fields
        (field (name "MANUFACTURER") "YAGEO")
        (field (name "POWER") "63 mW")
        (field (name "TOLERANCE") "±1 %")
      )
      (libsource (lib "eagle-import") (part "R-EU-R0402-499R"))
    )
    (comp (ref "R155")
      (value "100k")
      (footprint "eagle-import:R0603")
      (fields
        (field (name "MANUFACTURER") "Stackpole")
        (field (name "POWER") "63 mW")
        (field (name "TOLERANCE") "±1 %")
      )
      (libsource (lib "eagle-import") (part "R-EU-R0603-100K"))
    )
    (comp (ref "R156")
      (value "100k")
      (footprint "eagle-import:R0603")
      (fields
        (field (name "MANUFACTURER") "Stackpole")
        (field (name "POWER") "63 mW")
        (field (name "TOLERANCE") "±1 %")
      )
      (libsource (lib "eagle-import") (part "R-EU-R0603-100K"))
    )
    (comp (ref "R157")
      (value "100k")
      (footprint "eagle-import:R0603")
      (fields
        (field (name "MANUFACTURER") "Stackpole")
        (field (name "POWER") "63 mW")
        (field (name "TOLERANCE") "±1 %")
      )
      (libsource (lib "eagle-import") (part "R-EU-R0603-100K"))
    )
    (comp (ref "R158")
      (value "100k")
      (footprint "eagle-import:R0603")
      (fields
        (field (name "MANUFACTURER") "Stackpole")
        (field (name "POWER") "63 mW")
        (field (name "TOLERANCE") "±1 %")
      )
      (libsource (lib "eagle-import") (part "R-EU-R0603-100K"))
    )
    (comp (ref "R159")
      (value "100k")
      (footprint "eagle-import:R0603")
      (fields
        (field (name "MANUFACTURER") "Stackpole")
        (field (name "POWER") "63 mW")
        (field (name "TOLERANCE") "±1 %")
      )
      (libsource (lib "eagle-import") (part "R-EU-R0603-100K"))
    )
    (comp (ref "R160")
      (value "27R")
      (footprint "eagle-import:R0603")
      (fields
        (field (name "MANUFACTURER") "Stackpole")
        (field (name "POWER") "63 mW")
        (field (name "TOLERANCE") "±1 %")
      )
      (libsource (lib "eagle-import") (part "R-EU-R0603-27R"))
    )
    (comp (ref "R161")
      (value "10k 0.1%")
      (footprint "eagle-import:R0603")
      (fields
        (field (name "MANUFACTURER") "KOA Speer")
        (field (name "POWER") "63 mW")
        (field (name "TOLERANCE") "±0.1 %")
      )
      (libsource (lib "eagle-import") (part "R-EU-R0603-10K-0P1"))
    )
    (comp (ref "R162")
      (value "27R")
      (footprint "eagle-import:R0603")
      (fields
        (field (name "MANUFACTURER") "Stackpole")
        (field (name "POWER") "63 mW")
        (field (name "TOLERANCE") "±1 %")
      )
      (libsource (lib "eagle-import") (part "R-EU-R0603-27R"))
    )
    (comp (ref "R163")
      (value "27R")
      (footprint "eagle-import:R0603")
      (fields
        (field (name "MANUFACTURER") "Stackpole")
        (field (name "POWER") "63 mW")
        (field (name "TOLERANCE") "±1 %")
      )
      (libsource (lib "eagle-import") (part "R-EU-R0603-27R"))
    )
    (comp (ref "R164")
      (value "0R")
      (footprint "eagle-import:R0603")
      (fields
        (field (name "MANUFACTURER") "Stackpole")
        (field (name "POWER") "63 mW")
        (field (name "VOLTAGE") "50.0 V")
      )
      (libsource (lib "eagle-import") (part "R-EU-R0603-0R"))
    )
    (comp (ref "R165")
      (value "0R")
      (footprint "eagle-import:R0603")
      (fields
        (field (name "MANUFACTURER") "Stackpole")
        (field (name "POWER") "63 mW")
        (field (name "VOLTAGE") "50.0 V")
      )
      (libsource (lib "eagle-import") (part "R-EU-R0603-0R"))
    )
    (comp (ref "R166")
      (value "27R")
      (footprint "eagle-import:R0603")
      (fields
        (field (name "MANUFACTURER") "Stackpole")
        (field (name "POWER") "63 mW")
        (field (name "TOLERANCE") "±1 %")
      )
      (libsource (lib "eagle-import") (part "R-EU-R0603-27R"))
    )
    (comp (ref "R167")
      (value "1M")
      (footprint "eagle-import:R0603")
      (fields
        (field (name "MANUFACTURER") "Uniroyal")
        (field (name "POWER") "63 mW")
        (field (name "TOLERANCE") "±1 %")
      )
      (libsource (lib "eagle-import") (part "R-EU-R0603-1M"))
    )
    (comp (ref "R168")
      (value "27R")
      (footprint "eagle-import:R0603")
      (fields
        (field (name "MANUFACTURER") "Stackpole")
        (field (name "POWER") "63 mW")
        (field (name "TOLERANCE") "±1 %")
      )
      (libsource (lib "eagle-import") (part "R-EU-R0603-27R"))
    )
    (comp (ref "R169")
      (value "27R")
      (footprint "eagle-import:R0603")
      (fields
        (field (name "MANUFACTURER") "Stackpole")
        (field (name "POWER") "63 mW")
        (field (name "TOLERANCE") "±1 %")
      )
      (libsource (lib "eagle-import") (part "R-EU-R0603-27R"))
    )
    (comp (ref "R170")
      (value "10k")
      (footprint "eagle-import:R0603")
      (fields
        (field (name "MANUFACTURER") "Stackpole")
        (field (name "POWER") "63 mW")
        (field (name "TOLERANCE") "±1 %")
      )
      (libsource (lib "eagle-import") (part "R-EU-R0603-10K"))
    )
    (comp (ref "R171")
      (value "100k")
      (footprint "eagle-import:R0603")
      (fields
        (field (name "MANUFACTURER") "Stackpole")
        (field (name "POWER") "63 mW")
        (field (name "TOLERANCE") "±1 %")
      )
      (libsource (lib "eagle-import") (part "R-EU-R0603-100K"))
    )
    (comp (ref "R172")
      (value "27R")
      (footprint "eagle-import:R0603")
      (fields
        (field (name "MANUFACTURER") "Stackpole")
        (field (name "POWER") "63 mW")
        (field (name "TOLERANCE") "±1 %")
      )
      (libsource (lib "eagle-import") (part "R-EU-R0603-27R"))
    )
    (comp (ref "R173")
      (value "100k")
      (footprint "eagle-import:R0603")
      (fields
        (field (name "MANUFACTURER") "Stackpole")
        (field (name "POWER") "63 mW")
        (field (name "TOLERANCE") "±1 %")
      )
      (libsource (lib "eagle-import") (part "R-EU-R0603-100K"))
    )
    (comp (ref "R174")
      (value "10k")
      (footprint "eagle-import:R0603")
      (fields
        (field (name "MANUFACTURER") "Stackpole")
        (field (name "POWER") "63 mW")
        (field (name "TOLERANCE") "±1 %")
      )
      (libsource (lib "eagle-import") (part "R-EU-R0603-10K"))
    )
    (comp (ref "R175")
      (value "10k")
      (footprint "eagle-import:R0603")
      (fields
        (field (name "MANUFACTURER") "Stackpole")
        (field (name "POWER") "63 mW")
        (field (name "TOLERANCE") "±1 %")
      )
      (libsource (lib "eagle-import") (part "R-EU-R0603-10K"))
    )
    (comp (ref "R176")
      (value "27R")
      (footprint "eagle-import:R0603")
      (fields
        (field (name "MANUFACTURER") "Stackpole")
        (field (name "POWER") "63 mW")
        (field (name "TOLERANCE") "±1 %")
      )
      (libsource (lib "eagle-import") (part "R-EU-R0603-27R"))
    )
    (comp (ref "R177")
      (value "27R")
      (footprint "eagle-import:R0603")
      (fields
        (field (name "MANUFACTURER") "Stackpole")
        (field (name "POWER") "63 mW")
        (field (name "TOLERANCE") "±1 %")
      )
      (libsource (lib "eagle-import") (part "R-EU-R0603-27R"))
    )
    (comp (ref "R178")
      (value "100k")
      (footprint "eagle-import:R0603")
      (fields
        (field (name "MANUFACTURER") "Stackpole")
        (field (name "POWER") "63 mW")
        (field (name "TOLERANCE") "±1 %")
      )
      (libsource (lib "eagle-import") (part "R-EU-R0603-100K"))
    )
    (comp (ref "R179")
      (value "100k")
      (footprint "eagle-import:R0603")
      (fields
        (field (name "MANUFACTURER") "Stackpole")
        (field (name "POWER") "63 mW")
        (field (name "TOLERANCE") "±1 %")
      )
      (libsource (lib "eagle-import") (part "R-EU-R0603-100K"))
    )
    (comp (ref "R180")
      (value "10k")
      (footprint "eagle-import:R0603")
      (fields
        (field (name "MANUFACTURER") "Stackpole")
        (field (name "POWER") "63 mW")
        (field (name "TOLERANCE") "±1 %")
      )
      (libsource (lib "eagle-import") (part "R-EU-R0603-10K"))
    )
    (comp (ref "R181")
      (value "100k")
      (footprint "eagle-import:R0603")
      (fields
        (field (name "MANUFACTURER") "Stackpole")
        (field (name "POWER") "63 mW")
        (field (name "TOLERANCE") "±1 %")
      )
      (libsource (lib "eagle-import") (part "R-EU-R0603-100K"))
    )
    (comp (ref "R182")
      (value "10k")
      (footprint "eagle-import:R0603")
      (fields
        (field (name "MANUFACTURER") "Stackpole")
        (field (name "POWER") "63 mW")
        (field (name "TOLERANCE") "±1 %")
      )
      (libsource (lib "eagle-import") (part "R-EU-R0603-10K"))
    )
    (comp (ref "R183")
      (value "10k")
      (footprint "eagle-import:R0603")
      (fields
        (field (name "MANUFACTURER") "Stackpole")
        (field (name "POWER") "63 mW")
        (field (name "TOLERANCE") "±1 %")
      )
      (libsource (lib "eagle-import") (part "R-EU-R0603-10K"))
    )
    (comp (ref "R184")
      (value "100k")
      (footprint "eagle-import:R0603")
      (fields
        (field (name "MANUFACTURER") "Stackpole")
        (field (name "POWER") "63 mW")
        (field (name "TOLERANCE") "±1 %")
      )
      (libsource (lib "eagle-import") (part "R-EU-R0603-100K"))
    )
    (comp (ref "R185")
      (value "1k8")
      (footprint "eagle-import:R0603")
      (fields
        (field (name "MANUFACTURER") "Stackpole")
        (field (name "POWER") "63 mW")
        (field (name "TOLERANCE") "±1 %")
      )
      (libsource (lib "eagle-import") (part "R-EU-R0603-1K8"))
    )
    (comp (ref "R186")
      (value "1k8")
      (footprint "eagle-import:R0603")
      (fields
        (field (name "MANUFACTURER") "Stackpole")
        (field (name "POWER") "63 mW")
        (field (name "TOLERANCE") "±1 %")
      )
      (libsource (lib "eagle-import") (part "R-EU-R0603-1K8"))
    )
    (comp (ref "R187")
      (value "0R")
      (footprint "eagle-import:R0603")
      (fields
        (field (name "MANUFACTURER") "Stackpole")
        (field (name "POWER") "63 mW")
        (field (name "VOLTAGE") "50.0 V")
      )
      (libsource (lib "eagle-import") (part "R-EU-R0603-0R"))
    )
    (comp (ref "R188")
      (value "100k")
      (footprint "eagle-import:R0603")
      (fields
        (field (name "MANUFACTURER") "Stackpole")
        (field (name "POWER") "63 mW")
        (field (name "TOLERANCE") "±1 %")
      )
      (libsource (lib "eagle-import") (part "R-EU-R0603-100K"))
    )
    (comp (ref "R189")
      (value "100k")
      (footprint "eagle-import:R0603")
      (fields
        (field (name "MANUFACTURER") "Stackpole")
        (field (name "POWER") "63 mW")
        (field (name "TOLERANCE") "±1 %")
      )
      (libsource (lib "eagle-import") (part "R-EU-R0603-100K"))
    )
    (comp (ref "R190")
      (value "27R")
      (footprint "eagle-import:R0603")
      (fields
        (field (name "MANUFACTURER") "Stackpole")
        (field (name "POWER") "63 mW")
        (field (name "TOLERANCE") "±1 %")
      )
      (libsource (lib "eagle-import") (part "R-EU-R0603-27R"))
    )
    (comp (ref "R191")
      (value "27R")
      (footprint "eagle-import:R0603")
      (fields
        (field (name "MANUFACTURER") "Stackpole")
        (field (name "POWER") "63 mW")
        (field (name "TOLERANCE") "±1 %")
      )
      (libsource (lib "eagle-import") (part "R-EU-R0603-27R"))
    )
    (comp (ref "R192")
      (value "100k")
      (footprint "eagle-import:R0603")
      (fields
        (field (name "MANUFACTURER") "Stackpole")
        (field (name "POWER") "63 mW")
        (field (name "TOLERANCE") "±1 %")
      )
      (libsource (lib "eagle-import") (part "R-EU-R0603-100K"))
    )
    (comp (ref "R193")
      (value "27R")
      (footprint "eagle-import:R0603")
      (fields
        (field (name "MANUFACTURER") "Stackpole")
        (field (name "POWER") "63 mW")
        (field (name "TOLERANCE") "±1 %")
      )
      (libsource (lib "eagle-import") (part "R-EU-R0603-27R"))
    )
    (comp (ref "R194")
      (value "100k")
      (footprint "eagle-import:R0603")
      (fields
        (field (name "MANUFACTURER") "Stackpole")
        (field (name "POWER") "63 mW")
        (field (name "TOLERANCE") "±1 %")
      )
      (libsource (lib "eagle-import") (part "R-EU-R0603-100K"))
    )
    (comp (ref "R195")
      (value "27R")
      (footprint "eagle-import:R0603")
      (fields
        (field (name "MANUFACTURER") "Stackpole")
        (field (name "POWER") "63 mW")
        (field (name "TOLERANCE") "±1 %")
      )
      (libsource (lib "eagle-import") (part "R-EU-R0603-27R"))
    )
    (comp (ref "R196")
      (value "18k")
      (footprint "eagle-import:R0603")
      (fields
        (field (name "MANUFACTURER") "Stackpole")
        (field (name "POWER") "63 mW")
        (field (name "TOLERANCE") "±1 %")
      )
      (libsource (lib "eagle-import") (part "R-EU-R0603-18K"))
    )
    (comp (ref "R197")
      (value "43k")
      (footprint "eagle-import:R0603")
      (fields
        (field (name "MANUFACTURER") "Uniroyal")
        (field (name "POWER") "63 mW")
        (field (name "TOLERANCE") "±1 %")
      )
      (libsource (lib "eagle-import") (part "R-EU-R0603-43K"))
    )
    (comp (ref "R198")
      (value "1k8 0.1%")
      (footprint "eagle-import:R0603")
      (fields
        (field (name "MANUFACTURER") "TE Connectivity")
        (field (name "POWER") "63 mW")
        (field (name "TOLERANCE") "±0.1 %")
      )
      (libsource (lib "eagle-import") (part "R-EU-R0603-1K8-0P1"))
    )
    (comp (ref "R199")
      (value "10k 0.1%")
      (footprint "eagle-import:R0603")
      (fields
        (field (name "MANUFACTURER") "KOA Speer")
        (field (name "POWER") "63 mW")
        (field (name "TOLERANCE") "±0.1 %")
      )
      (libsource (lib "eagle-import") (part "R-EU-R0603-10K-0P1"))
    )
    (comp (ref "R200")
      (value "0R")
      (footprint "eagle-import:R0603")
      (fields
        (field (name "MANUFACTURER") "Stackpole")
        (field (name "POWER") "63 mW")
        (field (name "VOLTAGE") "50.0 V")
      )
      (libsource (lib "eagle-import") (part "R-EU-R0603-0R"))
    )
    (comp (ref "R201")
      (value "442k")
      (footprint "eagle-import:R0603")
      (fields
        (field (name "MANUFACTURER") "Stackpole")
        (field (name "POWER") "63 mW")
        (field (name "TOLERANCE") "±1 %")
      )
      (libsource (lib "eagle-import") (part "R-EU-R0603-442K"))
    )
    (comp (ref "R202")
      (value "0R")
      (footprint "eagle-import:R0603")
      (fields
        (field (name "MANUFACTURER") "Stackpole")
        (field (name "POWER") "63 mW")
        (field (name "VOLTAGE") "50.0 V")
      )
      (libsource (lib "eagle-import") (part "R-EU-R0603-0R"))
    )
    (comp (ref "R203")
      (value "0R")
      (footprint "eagle-import:R0603")
      (fields
        (field (name "MANUFACTURER") "Stackpole")
        (field (name "POWER") "63 mW")
        (field (name "VOLTAGE") "50.0 V")
      )
      (libsource (lib "eagle-import") (part "R-EU-R0603-0R"))
    )
    (comp (ref "R204")
      (value "1k8")
      (footprint "eagle-import:R0603")
      (fields
        (field (name "MANUFACTURER") "Stackpole")
        (field (name "POWER") "63 mW")
        (field (name "TOLERANCE") "±1 %")
      )
      (libsource (lib "eagle-import") (part "R-EU-R0603-1K8"))
    )
    (comp (ref "R205")
      (value "1k8")
      (footprint "eagle-import:R0603")
      (fields
        (field (name "MANUFACTURER") "Stackpole")
        (field (name "POWER") "63 mW")
        (field (name "TOLERANCE") "±1 %")
      )
      (libsource (lib "eagle-import") (part "R-EU-R0603-1K8"))
    )
    (comp (ref "R206")
      (value "R-EU-R0603")
      (footprint "eagle-import:R0603")
      (fields
        (field (name "POWER") "63 mW")
        (field (name "TOLERANCE") "±1 %")
        (field (name "VOLTAGE") "50 V")
      )
      (libsource (lib "eagle-import") (part "R-EU-R0603"))
    )
    (comp (ref "R207")
      (value "1k8")
      (footprint "eagle-import:R0603")
      (fields
        (field (name "MANUFACTURER") "Stackpole")
        (field (name "POWER") "63 mW")
        (field (name "TOLERANCE") "±1 %")
      )
      (libsource (lib "eagle-import") (part "R-EU-R0603-1K8"))
    )
    (comp (ref "R208")
      (value "R-EU-R0603")
      (footprint "eagle-import:R0603")
      (fields
        (field (name "POWER") "63 mW")
        (field (name "TOLERANCE") "±1 %")
        (field (name "VOLTAGE") "50 V")
      )
      (libsource (lib "eagle-import") (part "R-EU-R0603"))
    )
    (comp (ref "R209")
      (value "27R")
      (footprint "eagle-import:R0603")
      (fields
        (field (name "MANUFACTURER") "Stackpole")
        (field (name "POWER") "63 mW")
        (field (name "TOLERANCE") "±1 %")
      )
      (libsource (lib "eagle-import") (part "R-EU-R0603-27R"))
    )
    (comp (ref "R210")
      (value "27R")
      (footprint "eagle-import:R0603")
      (fields
        (field (name "MANUFACTURER") "Stackpole")
        (field (name "POWER") "63 mW")
        (field (name "TOLERANCE") "±1 %")
      )
      (libsource (lib "eagle-import") (part "R-EU-R0603-27R"))
    )
    (comp (ref "R211")
      (value "10k")
      (footprint "eagle-import:R0603")
      (fields
        (field (name "MANUFACTURER") "Stackpole")
        (field (name "POWER") "63 mW")
        (field (name "TOLERANCE") "±1 %")
      )
      (libsource (lib "eagle-import") (part "R-EU-R0603-10K"))
    )
    (comp (ref "R212")
      (value "100k")
      (footprint "eagle-import:R0603")
      (fields
        (field (name "MANUFACTURER") "Stackpole")
        (field (name "POWER") "63 mW")
        (field (name "TOLERANCE") "±1 %")
      )
      (libsource (lib "eagle-import") (part "R-EU-R0603-100K"))
    )
    (comp (ref "R213")
      (value "1M")
      (footprint "eagle-import:R0603")
      (fields
        (field (name "MANUFACTURER") "Uniroyal")
        (field (name "POWER") "63 mW")
        (field (name "TOLERANCE") "±1 %")
      )
      (libsource (lib "eagle-import") (part "R-EU-R0603-1M"))
    )
    (comp (ref "R214")
      (value "1M")
      (footprint "eagle-import:R0603")
      (fields
        (field (name "MANUFACTURER") "Uniroyal")
        (field (name "POWER") "63 mW")
        (field (name "TOLERANCE") "±1 %")
      )
      (libsource (lib "eagle-import") (part "R-EU-R0603-1M"))
    )
    (comp (ref "R215")
      (value "100k")
      (footprint "eagle-import:R0603")
      (fields
        (field (name "MANUFACTURER") "Stackpole")
        (field (name "POWER") "63 mW")
        (field (name "TOLERANCE") "±1 %")
      )
      (libsource (lib "eagle-import") (part "R-EU-R0603-100K"))
    )
    (comp (ref "R216")
      (value "27R")
      (footprint "eagle-import:R0603")
      (fields
        (field (name "MANUFACTURER") "Stackpole")
        (field (name "POWER") "63 mW")
        (field (name "TOLERANCE") "±1 %")
      )
      (libsource (lib "eagle-import") (part "R-EU-R0603-27R"))
    )
    (comp (ref "R217")
      (value "100k")
      (footprint "eagle-import:R0603")
      (fields
        (field (name "MANUFACTURER") "Stackpole")
        (field (name "POWER") "63 mW")
        (field (name "TOLERANCE") "±1 %")
      )
      (libsource (lib "eagle-import") (part "R-EU-R0603-100K"))
    )
    (comp (ref "R218")
      (value "27R")
      (footprint "eagle-import:R0603")
      (fields
        (field (name "MANUFACTURER") "Stackpole")
        (field (name "POWER") "63 mW")
        (field (name "TOLERANCE") "±1 %")
      )
      (libsource (lib "eagle-import") (part "R-EU-R0603-27R"))
    )
    (comp (ref "R219")
      (value "100k")
      (footprint "eagle-import:R0603")
      (fields
        (field (name "MANUFACTURER") "Stackpole")
        (field (name "POWER") "63 mW")
        (field (name "TOLERANCE") "±1 %")
      )
      (libsource (lib "eagle-import") (part "R-EU-R0603-100K"))
    )
    (comp (ref "R220")
      (value "100k")
      (footprint "eagle-import:R0603")
      (fields
        (field (name "MANUFACTURER") "Stackpole")
        (field (name "POWER") "63 mW")
        (field (name "TOLERANCE") "±1 %")
      )
      (libsource (lib "eagle-import") (part "R-EU-R0603-100K"))
    )
    (comp (ref "R221")
      (value "27R")
      (footprint "eagle-import:R0603")
      (fields
        (field (name "MANUFACTURER") "Stackpole")
        (field (name "POWER") "63 mW")
        (field (name "TOLERANCE") "±1 %")
      )
      (libsource (lib "eagle-import") (part "R-EU-R0603-27R"))
    )
    (comp (ref "R222")
      (value "100k")
      (footprint "eagle-import:R0603")
      (fields
        (field (name "MANUFACTURER") "Stackpole")
        (field (name "POWER") "63 mW")
        (field (name "TOLERANCE") "±1 %")
      )
      (libsource (lib "eagle-import") (part "R-EU-R0603-100K"))
    )
    (comp (ref "R223")
      (value "100k")
      (footprint "eagle-import:R0603")
      (fields
        (field (name "MANUFACTURER") "Stackpole")
        (field (name "POWER") "63 mW")
        (field (name "TOLERANCE") "±1 %")
      )
      (libsource (lib "eagle-import") (part "R-EU-R0603-100K"))
    )
    (comp (ref "R224")
      (value "100k")
      (footprint "eagle-import:R0603")
      (fields
        (field (name "MANUFACTURER") "Stackpole")
        (field (name "POWER") "63 mW")
        (field (name "TOLERANCE") "±1 %")
      )
      (libsource (lib "eagle-import") (part "R-EU-R0603-100K"))
    )
    (comp (ref "R225")
      (value "100k")
      (footprint "eagle-import:R0603")
      (fields
        (field (name "MANUFACTURER") "Stackpole")
        (field (name "POWER") "63 mW")
        (field (name "TOLERANCE") "±1 %")
      )
      (libsource (lib "eagle-import") (part "R-EU-R0603-100K"))
    )
    (comp (ref "R226")
      (value "27R")
      (footprint "eagle-import:R0603")
      (fields
        (field (name "MANUFACTURER") "Stackpole")
        (field (name "POWER") "63 mW")
        (field (name "TOLERANCE") "±1 %")
      )
      (libsource (lib "eagle-import") (part "R-EU-R0603-27R"))
    )
    (comp (ref "R227")
      (value "100k")
      (footprint "eagle-import:R0603")
      (fields
        (field (name "MANUFACTURER") "Stackpole")
        (field (name "POWER") "63 mW")
        (field (name "TOLERANCE") "±1 %")
      )
      (libsource (lib "eagle-import") (part "R-EU-R0603-100K"))
    )
    (comp (ref "R228")
      (value "0R")
      (footprint "eagle-import:R0603")
      (fields
        (field (name "MANUFACTURER") "Stackpole")
        (field (name "POWER") "63 mW")
        (field (name "VOLTAGE") "50.0 V")
      )
      (libsource (lib "eagle-import") (part "R-EU-R0603-0R"))
    )
    (comp (ref "R229")
      (value "R-EU-R0603")
      (footprint "eagle-import:R0603")
      (fields
        (field (name "POWER") "63 mW")
        (field (name "TOLERANCE") "±1 %")
        (field (name "VOLTAGE") "50 V")
      )
      (libsource (lib "eagle-import") (part "R-EU-R0603"))
    )
    (comp (ref "R230")
      (value "27R")
      (footprint "eagle-import:R0603")
      (fields
        (field (name "MANUFACTURER") "Stackpole")
        (field (name "POWER") "63 mW")
        (field (name "TOLERANCE") "±1 %")
      )
      (libsource (lib "eagle-import") (part "R-EU-R0603-27R"))
    )
    (comp (ref "R231")
      (value "10k")
      (footprint "eagle-import:R0603")
      (fields
        (field (name "MANUFACTURER") "Stackpole")
        (field (name "POWER") "63 mW")
        (field (name "TOLERANCE") "±1 %")
      )
      (libsource (lib "eagle-import") (part "R-EU-R0603-10K"))
    )
    (comp (ref "R232")
      (value "27R")
      (footprint "eagle-import:R0603")
      (fields
        (field (name "MANUFACTURER") "Stackpole")
        (field (name "POWER") "63 mW")
        (field (name "TOLERANCE") "±1 %")
      )
      (libsource (lib "eagle-import") (part "R-EU-R0603-27R"))
    )
    (comp (ref "R233")
      (value "27R")
      (footprint "eagle-import:R0603")
      (fields
        (field (name "MANUFACTURER") "Stackpole")
        (field (name "POWER") "63 mW")
        (field (name "TOLERANCE") "±1 %")
      )
      (libsource (lib "eagle-import") (part "R-EU-R0603-27R"))
    )
    (comp (ref "R234")
      (value "27R")
      (footprint "eagle-import:R0603")
      (fields
        (field (name "MANUFACTURER") "Stackpole")
        (field (name "POWER") "63 mW")
        (field (name "TOLERANCE") "±1 %")
      )
      (libsource (lib "eagle-import") (part "R-EU-R0603-27R"))
    )
    (comp (ref "R235")
      (value "27R")
      (footprint "eagle-import:R0603")
      (fields
        (field (name "MANUFACTURER") "Stackpole")
        (field (name "POWER") "63 mW")
        (field (name "TOLERANCE") "±1 %")
      )
      (libsource (lib "eagle-import") (part "R-EU-R0603-27R"))
    )
    (comp (ref "R236")
      (value "100k")
      (footprint "eagle-import:R0603")
      (fields
        (field (name "MANUFACTURER") "Stackpole")
        (field (name "POWER") "63 mW")
        (field (name "TOLERANCE") "±1 %")
      )
      (libsource (lib "eagle-import") (part "R-EU-R0603-100K"))
    )
    (comp (ref "R237")
      (value "27R")
      (footprint "eagle-import:R0603")
      (fields
        (field (name "MANUFACTURER") "Stackpole")
        (field (name "POWER") "63 mW")
        (field (name "TOLERANCE") "±1 %")
      )
      (libsource (lib "eagle-import") (part "R-EU-R0603-27R"))
    )
    (comp (ref "R238")
      (value "0R")
      (footprint "eagle-import:R0603")
      (fields
        (field (name "MANUFACTURER") "Stackpole")
        (field (name "POWER") "63 mW")
        (field (name "VOLTAGE") "50.0 V")
      )
      (libsource (lib "eagle-import") (part "R-EU-R0603-0R"))
    )
    (comp (ref "R239")
      (value "27R")
      (footprint "eagle-import:R0603")
      (fields
        (field (name "MANUFACTURER") "Stackpole")
        (field (name "POWER") "63 mW")
        (field (name "TOLERANCE") "±1 %")
      )
      (libsource (lib "eagle-import") (part "R-EU-R0603-27R"))
    )
    (comp (ref "R240")
      (value "0R")
      (footprint "eagle-import:R0603")
      (fields
        (field (name "MANUFACTURER") "Stackpole")
        (field (name "POWER") "63 mW")
        (field (name "VOLTAGE") "50.0 V")
      )
      (libsource (lib "eagle-import") (part "R-EU-R0603-0R"))
    )
    (comp (ref "R241")
      (value "27R")
      (footprint "eagle-import:R0603")
      (fields
        (field (name "MANUFACTURER") "Stackpole")
        (field (name "POWER") "63 mW")
        (field (name "TOLERANCE") "±1 %")
      )
      (libsource (lib "eagle-import") (part "R-EU-R0603-27R"))
    )
    (comp (ref "R242")
      (value "442k")
      (footprint "eagle-import:R0603")
      (fields
        (field (name "MANUFACTURER") "Stackpole")
        (field (name "POWER") "63 mW")
        (field (name "TOLERANCE") "±1 %")
      )
      (libsource (lib "eagle-import") (part "R-EU-R0603-442K"))
    )
    (comp (ref "R243")
      (value "27R")
      (footprint "eagle-import:R0603")
      (fields
        (field (name "MANUFACTURER") "Stackpole")
        (field (name "POWER") "63 mW")
        (field (name "TOLERANCE") "±1 %")
      )
      (libsource (lib "eagle-import") (part "R-EU-R0603-27R"))
    )
    (comp (ref "R244")
      (value "27R")
      (footprint "eagle-import:R0603")
      (fields
        (field (name "MANUFACTURER") "Stackpole")
        (field (name "POWER") "63 mW")
        (field (name "TOLERANCE") "±1 %")
      )
      (libsource (lib "eagle-import") (part "R-EU-R0603-27R"))
    )
    (comp (ref "R245")
      (value "100k")
      (footprint "eagle-import:R0603")
      (fields
        (field (name "MANUFACTURER") "Stackpole")
        (field (name "POWER") "63 mW")
        (field (name "TOLERANCE") "±1 %")
      )
      (libsource (lib "eagle-import") (part "R-EU-R0603-100K"))
    )
    (comp (ref "R246")
      (value "100k")
      (footprint "eagle-import:R0603")
      (fields
        (field (name "MANUFACTURER") "Stackpole")
        (field (name "POWER") "63 mW")
        (field (name "TOLERANCE") "±1 %")
      )
      (libsource (lib "eagle-import") (part "R-EU-R0603-100K"))
    )
    (comp (ref "R247")
      (value "27R")
      (footprint "eagle-import:R0603")
      (fields
        (field (name "MANUFACTURER") "Stackpole")
        (field (name "POWER") "63 mW")
        (field (name "TOLERANCE") "±1 %")
      )
      (libsource (lib "eagle-import") (part "R-EU-R0603-27R"))
    )
    (comp (ref "R248")
      (value "27R")
      (footprint "eagle-import:R0603")
      (fields
        (field (name "MANUFACTURER") "Stackpole")
        (field (name "POWER") "63 mW")
        (field (name "TOLERANCE") "±1 %")
      )
      (libsource (lib "eagle-import") (part "R-EU-R0603-27R"))
    )
    (comp (ref "R249")
      (value "0R")
      (footprint "eagle-import:R0603")
      (fields
        (field (name "MANUFACTURER") "Stackpole")
        (field (name "POWER") "63 mW")
        (field (name "VOLTAGE") "50.0 V")
      )
      (libsource (lib "eagle-import") (part "R-EU-R0603-0R"))
    )
    (comp (ref "R250")
      (value "R-EU-R0603")
      (footprint "eagle-import:R0603")
      (fields
        (field (name "POWER") "63 mW")
        (field (name "TOLERANCE") "±1 %")
        (field (name "VOLTAGE") "50 V")
      )
      (libsource (lib "eagle-import") (part "R-EU-R0603"))
    )
    (comp (ref "R251")
      (value "0R")
      (footprint "eagle-import:R0603")
      (fields
        (field (name "MANUFACTURER") "Stackpole")
        (field (name "POWER") "63 mW")
        (field (name "VOLTAGE") "50.0 V")
      )
      (libsource (lib "eagle-import") (part "R-EU-R0603-0R"))
    )
    (comp (ref "R252")
      (value "100k")
      (footprint "eagle-import:R0603")
      (fields
        (field (name "MANUFACTURER") "Stackpole")
        (field (name "POWER") "63 mW")
        (field (name "TOLERANCE") "±1 %")
      )
      (libsource (lib "eagle-import") (part "R-EU-R0603-100K"))
    )
    (comp (ref "R253")
      (value "47k 0.1%")
      (footprint "eagle-import:R0603")
      (fields
        (field (name "MANUFACTURER") "YAGEO")
        (field (name "POWER") "63 mW")
        (field (name "TOLERANCE") "±0.1 %")
      )
      (libsource (lib "eagle-import") (part "R-EU-R0603-47K-0P1"))
    )
    (comp (ref "R254")
      (value "10k 0.1%")
      (footprint "eagle-import:R0603")
      (fields
        (field (name "MANUFACTURER") "KOA Speer")
        (field (name "POWER") "63 mW")
        (field (name "TOLERANCE") "±0.1 %")
      )
      (libsource (lib "eagle-import") (part "R-EU-R0603-10K-0P1"))
    )
    (comp (ref "R255")
      (value "100k")
      (footprint "eagle-import:R0603")
      (fields
        (field (name "MANUFACTURER") "Stackpole")
        (field (name "POWER") "63 mW")
        (field (name "TOLERANCE") "±1 %")
      )
      (libsource (lib "eagle-import") (part "R-EU-R0603-100K"))
    )
    (comp (ref "R256")
      (value "27R")
      (footprint "eagle-import:R0603")
      (fields
        (field (name "MANUFACTURER") "Stackpole")
        (field (name "POWER") "63 mW")
        (field (name "TOLERANCE") "±1 %")
      )
      (libsource (lib "eagle-import") (part "R-EU-R0603-27R"))
    )
    (comp (ref "R257")
      (value "0R")
      (footprint "eagle-import:R0603")
      (fields
        (field (name "MANUFACTURER") "Stackpole")
        (field (name "POWER") "63 mW")
        (field (name "VOLTAGE") "50.0 V")
      )
      (libsource (lib "eagle-import") (part "R-EU-R0603-0R"))
    )
    (comp (ref "R258")
      (value "0R")
      (footprint "eagle-import:R0603")
      (fields
        (field (name "MANUFACTURER") "Stackpole")
        (field (name "POWER") "63 mW")
        (field (name "VOLTAGE") "50.0 V")
      )
      (libsource (lib "eagle-import") (part "R-EU-R0603-0R"))
    )
    (comp (ref "R259")
      (value "27R")
      (footprint "eagle-import:R0603")
      (fields
        (field (name "MANUFACTURER") "Stackpole")
        (field (name "POWER") "63 mW")
        (field (name "TOLERANCE") "±1 %")
      )
      (libsource (lib "eagle-import") (part "R-EU-R0603-27R"))
    )
    (comp (ref "R260")
      (value "0R")
      (footprint "eagle-import:R0603")
      (fields
        (field (name "MANUFACTURER") "Stackpole")
        (field (name "POWER") "63 mW")
        (field (name "VOLTAGE") "50.0 V")
      )
      (libsource (lib "eagle-import") (part "R-EU-R0603-0R"))
    )
    (comp (ref "R261")
      (value "100k")
      (footprint "eagle-import:R0603")
      (fields
        (field (name "MANUFACTURER") "Stackpole")
        (field (name "POWER") "63 mW")
        (field (name "TOLERANCE") "±1 %")
      )
      (libsource (lib "eagle-import") (part "R-EU-R0603-100K"))
    )
    (comp (ref "R262")
      (value "100k")
      (footprint "eagle-import:R0603")
      (fields
        (field (name "MANUFACTURER") "Stackpole")
        (field (name "POWER") "63 mW")
        (field (name "TOLERANCE") "±1 %")
      )
      (libsource (lib "eagle-import") (part "R-EU-R0603-100K"))
    )
    (comp (ref "R263")
      (value "100k")
      (footprint "eagle-import:R0603")
      (fields
        (field (name "MANUFACTURER") "Stackpole")
        (field (name "POWER") "63 mW")
        (field (name "TOLERANCE") "±1 %")
      )
      (libsource (lib "eagle-import") (part "R-EU-R0603-100K"))
    )
    (comp (ref "R264")
      (value "100k")
      (footprint "eagle-import:R0603")
      (fields
        (field (name "MANUFACTURER") "Stackpole")
        (field (name "POWER") "63 mW")
        (field (name "TOLERANCE") "±1 %")
      )
      (libsource (lib "eagle-import") (part "R-EU-R0603-100K"))
    )
    (comp (ref "R265")
      (value "0R")
      (footprint "eagle-import:R0603")
      (fields
        (field (name "MANUFACTURER") "Stackpole")
        (field (name "POWER") "63 mW")
        (field (name "VOLTAGE") "50.0 V")
      )
      (libsource (lib "eagle-import") (part "R-EU-R0603-0R"))
    )
    (comp (ref "R266")
      (value "27R")
      (footprint "eagle-import:R0603")
      (fields
        (field (name "MANUFACTURER") "Stackpole")
        (field (name "POWER") "63 mW")
        (field (name "TOLERANCE") "±1 %")
      )
      (libsource (lib "eagle-import") (part "R-EU-R0603-27R"))
    )
    (comp (ref "R267")
      (value "27R")
      (footprint "eagle-import:R0603")
      (fields
        (field (name "MANUFACTURER") "Stackpole")
        (field (name "POWER") "63 mW")
        (field (name "TOLERANCE") "±1 %")
      )
      (libsource (lib "eagle-import") (part "R-EU-R0603-27R"))
    )
    (comp (ref "R268")
      (value "27R")
      (footprint "eagle-import:R0603")
      (fields
        (field (name "MANUFACTURER") "Stackpole")
        (field (name "POWER") "63 mW")
        (field (name "TOLERANCE") "±1 %")
      )
      (libsource (lib "eagle-import") (part "R-EU-R0603-27R"))
    )
    (comp (ref "R269")
      (value "27R")
      (footprint "eagle-import:R0603")
      (fields
        (field (name "MANUFACTURER") "Stackpole")
        (field (name "POWER") "63 mW")
        (field (name "TOLERANCE") "±1 %")
      )
      (libsource (lib "eagle-import") (part "R-EU-R0603-27R"))
    )
    (comp (ref "R270")
      (value "27R")
      (footprint "eagle-import:R0603")
      (fields
        (field (name "MANUFACTURER") "Stackpole")
        (field (name "POWER") "63 mW")
        (field (name "TOLERANCE") "±1 %")
      )
      (libsource (lib "eagle-import") (part "R-EU-R0603-27R"))
    )
    (comp (ref "R271")
      (value "27R")
      (footprint "eagle-import:R0603")
      (fields
        (field (name "MANUFACTURER") "Stackpole")
        (field (name "POWER") "63 mW")
        (field (name "TOLERANCE") "±1 %")
      )
      (libsource (lib "eagle-import") (part "R-EU-R0603-27R"))
    )
    (comp (ref "R272")
      (value "1k8")
      (footprint "eagle-import:R0603")
      (fields
        (field (name "MANUFACTURER") "Stackpole")
        (field (name "POWER") "63 mW")
        (field (name "TOLERANCE") "±1 %")
      )
      (libsource (lib "eagle-import") (part "R-EU-R0603-1K8"))
    )
    (comp (ref "R273")
      (value "27R")
      (footprint "eagle-import:R0603")
      (fields
        (field (name "MANUFACTURER") "Stackpole")
        (field (name "POWER") "63 mW")
        (field (name "TOLERANCE") "±1 %")
      )
      (libsource (lib "eagle-import") (part "R-EU-R0603-27R"))
    )
    (comp (ref "R274")
      (value "27R")
      (footprint "eagle-import:R0603")
      (fields
        (field (name "MANUFACTURER") "Stackpole")
        (field (name "POWER") "63 mW")
        (field (name "TOLERANCE") "±1 %")
      )
      (libsource (lib "eagle-import") (part "R-EU-R0603-27R"))
    )
    (comp (ref "R275")
      (value "47k 0.1%")
      (footprint "eagle-import:R0603")
      (fields
        (field (name "MANUFACTURER") "YAGEO")
        (field (name "POWER") "63 mW")
        (field (name "TOLERANCE") "±0.1 %")
      )
      (libsource (lib "eagle-import") (part "R-EU-R0603-47K-0P1"))
    )
    (comp (ref "R276")
      (value "0R")
      (footprint "eagle-import:R0603")
      (fields
        (field (name "MANUFACTURER") "Stackpole")
        (field (name "POWER") "63 mW")
        (field (name "VOLTAGE") "50.0 V")
      )
      (libsource (lib "eagle-import") (part "R-EU-R0603-0R"))
    )
    (comp (ref "R277")
      (value "R-EU-R0603")
      (footprint "eagle-import:R0603")
      (fields
        (field (name "POWER") "63 mW")
        (field (name "TOLERANCE") "±1 %")
        (field (name "VOLTAGE") "50 V")
      )
      (libsource (lib "eagle-import") (part "R-EU-R0603"))
    )
    (comp (ref "R278")
      (value "0R")
      (footprint "eagle-import:R0603")
      (fields
        (field (name "MANUFACTURER") "Stackpole")
        (field (name "POWER") "63 mW")
        (field (name "VOLTAGE") "50.0 V")
      )
      (libsource (lib "eagle-import") (part "R-EU-R0603-0R"))
    )
    (comp (ref "R279")
      (value "100k")
      (footprint "eagle-import:R0603")
      (fields
        (field (name "MANUFACTURER") "Stackpole")
        (field (name "POWER") "63 mW")
        (field (name "TOLERANCE") "±1 %")
      )
      (libsource (lib "eagle-import") (part "R-EU-R0603-100K"))
    )
    (comp (ref "R280")
      (value "27R")
      (footprint "eagle-import:R0603")
      (fields
        (field (name "MANUFACTURER") "Stackpole")
        (field (name "POWER") "63 mW")
        (field (name "TOLERANCE") "±1 %")
      )
      (libsource (lib "eagle-import") (part "R-EU-R0603-27R"))
    )
    (comp (ref "R281")
      (value "27R")
      (footprint "eagle-import:R0603")
      (fields
        (field (name "MANUFACTURER") "Stackpole")
        (field (name "POWER") "63 mW")
        (field (name "TOLERANCE") "±1 %")
      )
      (libsource (lib "eagle-import") (part "R-EU-R0603-27R"))
    )
    (comp (ref "R282")
      (value "10k")
      (footprint "eagle-import:R0603")
      (fields
        (field (name "MANUFACTURER") "Stackpole")
        (field (name "POWER") "63 mW")
        (field (name "TOLERANCE") "±1 %")
      )
      (libsource (lib "eagle-import") (part "R-EU-R0603-10K"))
    )
    (comp (ref "R283")
      (value "100k")
      (footprint "eagle-import:R0603")
      (fields
        (field (name "MANUFACTURER") "Stackpole")
        (field (name "POWER") "63 mW")
        (field (name "TOLERANCE") "±1 %")
      )
      (libsource (lib "eagle-import") (part "R-EU-R0603-100K"))
    )
    (comp (ref "R284")
      (value "27R")
      (footprint "eagle-import:R0603")
      (fields
        (field (name "MANUFACTURER") "Stackpole")
        (field (name "POWER") "63 mW")
        (field (name "TOLERANCE") "±1 %")
      )
      (libsource (lib "eagle-import") (part "R-EU-R0603-27R"))
    )
    (comp (ref "R285")
      (value "100k")
      (footprint "eagle-import:R0603")
      (fields
        (field (name "MANUFACTURER") "Stackpole")
        (field (name "POWER") "63 mW")
        (field (name "TOLERANCE") "±1 %")
      )
      (libsource (lib "eagle-import") (part "R-EU-R0603-100K"))
    )
    (comp (ref "R286")
      (value "1k8")
      (footprint "eagle-import:R0603")
      (fields
        (field (name "MANUFACTURER") "Stackpole")
        (field (name "POWER") "63 mW")
        (field (name "TOLERANCE") "±1 %")
      )
      (libsource (lib "eagle-import") (part "R-EU-R0603-1K8"))
    )
    (comp (ref "R287")
      (value "1k8")
      (footprint "eagle-import:R0603")
      (fields
        (field (name "MANUFACTURER") "Stackpole")
        (field (name "POWER") "63 mW")
        (field (name "TOLERANCE") "±1 %")
      )
      (libsource (lib "eagle-import") (part "R-EU-R0603-1K8"))
    )
    (comp (ref "R288")
      (value "R-EU-R0603")
      (footprint "eagle-import:R0603")
      (fields
        (field (name "POWER") "63 mW")
        (field (name "TOLERANCE") "±1 %")
        (field (name "VOLTAGE") "50 V")
      )
      (libsource (lib "eagle-import") (part "R-EU-R0603"))
    )
    (comp (ref "R289")
      (value "27R")
      (footprint "eagle-import:R0603")
      (fields
        (field (name "MANUFACTURER") "Stackpole")
        (field (name "POWER") "63 mW")
        (field (name "TOLERANCE") "±1 %")
      )
      (libsource (lib "eagle-import") (part "R-EU-R0603-27R"))
    )
    (comp (ref "R290")
      (value "27R")
      (footprint "eagle-import:R0603")
      (fields
        (field (name "MANUFACTURER") "Stackpole")
        (field (name "POWER") "63 mW")
        (field (name "TOLERANCE") "±1 %")
      )
      (libsource (lib "eagle-import") (part "R-EU-R0603-27R"))
    )
    (comp (ref "R291")
      (value "43k")
      (footprint "eagle-import:R0603")
      (fields
        (field (name "MANUFACTURER") "Uniroyal")
        (field (name "POWER") "63 mW")
        (field (name "TOLERANCE") "±1 %")
      )
      (libsource (lib "eagle-import") (part "R-EU-R0603-43K"))
    )
    (comp (ref "R292")
      (value "27R")
      (footprint "eagle-import:R0603")
      (fields
        (field (name "MANUFACTURER") "Stackpole")
        (field (name "POWER") "63 mW")
        (field (name "TOLERANCE") "±1 %")
      )
      (libsource (lib "eagle-import") (part "R-EU-R0603-27R"))
    )
    (comp (ref "R293")
      (value "10k 0.1%")
      (footprint "eagle-import:R0603")
      (fields
        (field (name "MANUFACTURER") "KOA Speer")
        (field (name "POWER") "63 mW")
        (field (name "TOLERANCE") "±0.1 %")
      )
      (libsource (lib "eagle-import") (part "R-EU-R0603-10K-0P1"))
    )
    (comp (ref "R294")
      (value "100k")
      (footprint "eagle-import:R0603")
      (fields
        (field (name "MANUFACTURER") "Stackpole")
        (field (name "POWER") "63 mW")
        (field (name "TOLERANCE") "±1 %")
      )
      (libsource (lib "eagle-import") (part "R-EU-R0603-100K"))
    )
    (comp (ref "R295")
      (value "27R")
      (footprint "eagle-import:R0603")
      (fields
        (field (name "MANUFACTURER") "Stackpole")
        (field (name "POWER") "63 mW")
        (field (name "TOLERANCE") "±1 %")
      )
      (libsource (lib "eagle-import") (part "R-EU-R0603-27R"))
    )
    (comp (ref "R296")
      (value "499R")
      (footprint "eagle-import:R0402")
      (fields
        (field (name "MANUFACTURER") "YAGEO")
        (field (name "POWER") "63 mW")
        (field (name "TOLERANCE") "±1 %")
      )
      (libsource (lib "eagle-import") (part "R-EU-R0402-499R"))
    )
    (comp (ref "R297")
      (value "100k")
      (footprint "eagle-import:R0603")
      (fields
        (field (name "MANUFACTURER") "Stackpole")
        (field (name "POWER") "63 mW")
        (field (name "TOLERANCE") "±1 %")
      )
      (libsource (lib "eagle-import") (part "R-EU-R0603-100K"))
    )
    (comp (ref "R298")
      (value "10k")
      (footprint "eagle-import:R0603")
      (fields
        (field (name "MANUFACTURER") "Stackpole")
        (field (name "POWER") "63 mW")
        (field (name "TOLERANCE") "±1 %")
      )
      (libsource (lib "eagle-import") (part "R-EU-R0603-10K"))
    )
    (comp (ref "R299")
      (value "n.m.")
      (footprint "eagle-import:R0402")
      (fields
        (field (name "POWER") "63 mW")
        (field (name "TOLERANCE") "±1 %")
        (field (name "VOLTAGE") "25 V")
      )
      (libsource (lib "eagle-import") (part "R-EU-R0402"))
    )
    (comp (ref "R300")
      (value "100k")
      (footprint "eagle-import:R0603")
      (fields
        (field (name "MANUFACTURER") "Stackpole")
        (field (name "POWER") "63 mW")
        (field (name "TOLERANCE") "±1 %")
      )
      (libsource (lib "eagle-import") (part "R-EU-R0603-100K"))
    )
    (comp (ref "R301")
      (value "27R")
      (footprint "eagle-import:R0603")
      (fields
        (field (name "MANUFACTURER") "Stackpole")
        (field (name "POWER") "63 mW")
        (field (name "TOLERANCE") "±1 %")
      )
      (libsource (lib "eagle-import") (part "R-EU-R0603-27R"))
    )
    (comp (ref "R302")
      (value "27R")
      (footprint "eagle-import:R0603")
      (fields
        (field (name "MANUFACTURER") "Stackpole")
        (field (name "POWER") "63 mW")
        (field (name "TOLERANCE") "±1 %")
      )
      (libsource (lib "eagle-import") (part "R-EU-R0603-27R"))
    )
    (comp (ref "R303")
      (value "27R")
      (footprint "eagle-import:R0603")
      (fields
        (field (name "MANUFACTURER") "Stackpole")
        (field (name "POWER") "63 mW")
        (field (name "TOLERANCE") "±1 %")
      )
      (libsource (lib "eagle-import") (part "R-EU-R0603-27R"))
    )
    (comp (ref "R304")
      (value "27R")
      (footprint "eagle-import:R0603")
      (fields
        (field (name "MANUFACTURER") "Stackpole")
        (field (name "POWER") "63 mW")
        (field (name "TOLERANCE") "±1 %")
      )
      (libsource (lib "eagle-import") (part "R-EU-R0603-27R"))
    )
    (comp (ref "R305")
      (value "100k")
      (footprint "eagle-import:R0603")
      (fields
        (field (name "MANUFACTURER") "Stackpole")
        (field (name "POWER") "63 mW")
        (field (name "TOLERANCE") "±1 %")
      )
      (libsource (lib "eagle-import") (part "R-EU-R0603-100K"))
    )
    (comp (ref "R306")
      (value "10k")
      (footprint "eagle-import:R0603")
      (fields
        (field (name "MANUFACTURER") "Stackpole")
        (field (name "POWER") "63 mW")
        (field (name "TOLERANCE") "±1 %")
      )
      (libsource (lib "eagle-import") (part "R-EU-R0603-10K"))
    )
    (comp (ref "R307")
      (value "4R7")
      (footprint "eagle-import:R0402")
      (fields
        (field (name "MANUFACTURER") "Stackpole")
        (field (name "POWER") "63 mW")
        (field (name "TOLERANCE") "±1 %")
      )
      (libsource (lib "eagle-import") (part "R-EU-R0402-4R7"))
    )
    (comp (ref "R308")
      (value "4R7")
      (footprint "eagle-import:R0402")
      (fields
        (field (name "MANUFACTURER") "Stackpole")
        (field (name "POWER") "63 mW")
        (field (name "TOLERANCE") "±1 %")
      )
      (libsource (lib "eagle-import") (part "R-EU-R0402-4R7"))
    )
    (comp (ref "R309")
      (value "R-EU-R0603")
      (footprint "eagle-import:R0603")
      (fields
        (field (name "POWER") "63 mW")
        (field (name "TOLERANCE") "±1 %")
        (field (name "VOLTAGE") "50 V")
      )
      (libsource (lib "eagle-import") (part "R-EU-R0603"))
    )
    (comp (ref "R310")
      (value "0R")
      (footprint "eagle-import:R0603")
      (fields
        (field (name "MANUFACTURER") "Stackpole")
        (field (name "POWER") "63 mW")
        (field (name "VOLTAGE") "50.0 V")
      )
      (libsource (lib "eagle-import") (part "R-EU-R0603-0R"))
    )
    (comp (ref "R311")
      (value "27R")
      (footprint "eagle-import:R0603")
      (fields
        (field (name "MANUFACTURER") "Stackpole")
        (field (name "POWER") "63 mW")
        (field (name "TOLERANCE") "±1 %")
      )
      (libsource (lib "eagle-import") (part "R-EU-R0603-27R"))
    )
    (comp (ref "R312")
      (value "100k")
      (footprint "eagle-import:R0603")
      (fields
        (field (name "MANUFACTURER") "Stackpole")
        (field (name "POWER") "63 mW")
        (field (name "TOLERANCE") "±1 %")
      )
      (libsource (lib "eagle-import") (part "R-EU-R0603-100K"))
    )
    (comp (ref "R313")
      (value "1M")
      (footprint "eagle-import:R0603")
      (fields
        (field (name "MANUFACTURER") "Uniroyal")
        (field (name "POWER") "63 mW")
        (field (name "TOLERANCE") "±1 %")
      )
      (libsource (lib "eagle-import") (part "R-EU-R0603-1M"))
    )
    (comp (ref "R314")
      (value "4R7")
      (footprint "eagle-import:R0402")
      (fields
        (field (name "MANUFACTURER") "Stackpole")
        (field (name "POWER") "63 mW")
        (field (name "TOLERANCE") "±1 %")
      )
      (libsource (lib "eagle-import") (part "R-EU-R0402-4R7"))
    )
    (comp (ref "R315")
      (value "0R")
      (footprint "eagle-import:R0603")
      (fields
        (field (name "MANUFACTURER") "Stackpole")
        (field (name "POWER") "63 mW")
        (field (name "VOLTAGE") "50.0 V")
      )
      (libsource (lib "eagle-import") (part "R-EU-R0603-0R"))
    )
    (comp (ref "R316")
      (value "R-EU-R0603")
      (footprint "eagle-import:R0603")
      (fields
        (field (name "POWER") "63 mW")
        (field (name "TOLERANCE") "±1 %")
        (field (name "VOLTAGE") "50 V")
      )
      (libsource (lib "eagle-import") (part "R-EU-R0603"))
    )
    (comp (ref "R317")
      (value "100k")
      (footprint "eagle-import:R0603")
      (fields
        (field (name "MANUFACTURER") "Stackpole")
        (field (name "POWER") "63 mW")
        (field (name "TOLERANCE") "±1 %")
      )
      (libsource (lib "eagle-import") (part "R-EU-R0603-100K"))
    )
    (comp (ref "R318")
      (value "47k 0.1%")
      (footprint "eagle-import:R0603")
      (fields
        (field (name "MANUFACTURER") "YAGEO")
        (field (name "POWER") "63 mW")
        (field (name "TOLERANCE") "±0.1 %")
      )
      (libsource (lib "eagle-import") (part "R-EU-R0603-47K-0P1"))
    )
    (comp (ref "R319")
      (value "100k")
      (footprint "eagle-import:R0603")
      (fields
        (field (name "MANUFACTURER") "Stackpole")
        (field (name "POWER") "63 mW")
        (field (name "TOLERANCE") "±1 %")
      )
      (libsource (lib "eagle-import") (part "R-EU-R0603-100K"))
    )
    (comp (ref "R320")
      (value "100k")
      (footprint "eagle-import:R0603")
      (fields
        (field (name "MANUFACTURER") "Stackpole")
        (field (name "POWER") "63 mW")
        (field (name "TOLERANCE") "±1 %")
      )
      (libsource (lib "eagle-import") (part "R-EU-R0603-100K"))
    )
    (comp (ref "R321")
      (value "27R")
      (footprint "eagle-import:R0603")
      (fields
        (field (name "MANUFACTURER") "Stackpole")
        (field (name "POWER") "63 mW")
        (field (name "TOLERANCE") "±1 %")
      )
      (libsource (lib "eagle-import") (part "R-EU-R0603-27R"))
    )
    (comp (ref "R322")
      (value "27R")
      (footprint "eagle-import:R0603")
      (fields
        (field (name "MANUFACTURER") "Stackpole")
        (field (name "POWER") "63 mW")
        (field (name "TOLERANCE") "±1 %")
      )
      (libsource (lib "eagle-import") (part "R-EU-R0603-27R"))
    )
    (comp (ref "R323")
      (value "100k")
      (footprint "eagle-import:R0603")
      (fields
        (field (name "MANUFACTURER") "Stackpole")
        (field (name "POWER") "63 mW")
        (field (name "TOLERANCE") "±1 %")
      )
      (libsource (lib "eagle-import") (part "R-EU-R0603-100K"))
    )
    (comp (ref "R324")
      (value "27R")
      (footprint "eagle-import:R0603")
      (fields
        (field (name "MANUFACTURER") "Stackpole")
        (field (name "POWER") "63 mW")
        (field (name "TOLERANCE") "±1 %")
      )
      (libsource (lib "eagle-import") (part "R-EU-R0603-27R"))
    )
    (comp (ref "R325")
      (value "10k 0.1%")
      (footprint "eagle-import:R0603")
      (fields
        (field (name "MANUFACTURER") "KOA Speer")
        (field (name "POWER") "63 mW")
        (field (name "TOLERANCE") "±0.1 %")
      )
      (libsource (lib "eagle-import") (part "R-EU-R0603-10K-0P1"))
    )
    (comp (ref "R326")
      (value "27R")
      (footprint "eagle-import:R0603")
      (fields
        (field (name "MANUFACTURER") "Stackpole")
        (field (name "POWER") "63 mW")
        (field (name "TOLERANCE") "±1 %")
      )
      (libsource (lib "eagle-import") (part "R-EU-R0603-27R"))
    )
    (comp (ref "R327")
      (value "4R7")
      (footprint "eagle-import:R0402")
      (fields
        (field (name "MANUFACTURER") "Stackpole")
        (field (name "POWER") "63 mW")
        (field (name "TOLERANCE") "±1 %")
      )
      (libsource (lib "eagle-import") (part "R-EU-R0402-4R7"))
    )
    (comp (ref "R328")
      (value "0R")
      (footprint "eagle-import:R0603")
      (fields
        (field (name "MANUFACTURER") "Stackpole")
        (field (name "POWER") "63 mW")
        (field (name "VOLTAGE") "50.0 V")
      )
      (libsource (lib "eagle-import") (part "R-EU-R0603-0R"))
    )
    (comp (ref "R329")
      (value "27R")
      (footprint "eagle-import:R0603")
      (fields
        (field (name "MANUFACTURER") "Stackpole")
        (field (name "POWER") "63 mW")
        (field (name "TOLERANCE") "±1 %")
      )
      (libsource (lib "eagle-import") (part "R-EU-R0603-27R"))
    )
    (comp (ref "R330")
      (value "27R")
      (footprint "eagle-import:R0603")
      (fields
        (field (name "MANUFACTURER") "Stackpole")
        (field (name "POWER") "63 mW")
        (field (name "TOLERANCE") "±1 %")
      )
      (libsource (lib "eagle-import") (part "R-EU-R0603-27R"))
    )
    (comp (ref "R331")
      (value "27R")
      (footprint "eagle-import:R0603")
      (fields
        (field (name "MANUFACTURER") "Stackpole")
        (field (name "POWER") "63 mW")
        (field (name "TOLERANCE") "±1 %")
      )
      (libsource (lib "eagle-import") (part "R-EU-R0603-27R"))
    )
    (comp (ref "R332")
      (value "27R")
      (footprint "eagle-import:R0603")
      (fields
        (field (name "MANUFACTURER") "Stackpole")
        (field (name "POWER") "63 mW")
        (field (name "TOLERANCE") "±1 %")
      )
      (libsource (lib "eagle-import") (part "R-EU-R0603-27R"))
    )
    (comp (ref "R333")
      (value "4R7")
      (footprint "eagle-import:R0402")
      (fields
        (field (name "MANUFACTURER") "Stackpole")
        (field (name "POWER") "63 mW")
        (field (name "TOLERANCE") "±1 %")
      )
      (libsource (lib "eagle-import") (part "R-EU-R0402-4R7"))
    )
    (comp (ref "R334")
      (value "R-EU-R0603")
      (footprint "eagle-import:R0603")
      (fields
        (field (name "POWER") "63 mW")
        (field (name "TOLERANCE") "±1 %")
        (field (name "VOLTAGE") "50 V")
      )
      (libsource (lib "eagle-import") (part "R-EU-R0603"))
    )
    (comp (ref "R335")
      (value "10k")
      (footprint "eagle-import:R0603")
      (fields
        (field (name "MANUFACTURER") "Stackpole")
        (field (name "POWER") "63 mW")
        (field (name "TOLERANCE") "±1 %")
      )
      (libsource (lib "eagle-import") (part "R-EU-R0603-10K"))
    )
    (comp (ref "R336")
      (value "100k")
      (footprint "eagle-import:R0603")
      (fields
        (field (name "MANUFACTURER") "Stackpole")
        (field (name "POWER") "63 mW")
        (field (name "TOLERANCE") "±1 %")
      )
      (libsource (lib "eagle-import") (part "R-EU-R0603-100K"))
    )
    (comp (ref "R337")
      (value "100k")
      (footprint "eagle-import:R0603")
      (fields
        (field (name "MANUFACTURER") "Stackpole")
        (field (name "POWER") "63 mW")
        (field (name "TOLERANCE") "±1 %")
      )
      (libsource (lib "eagle-import") (part "R-EU-R0603-100K"))
    )
    (comp (ref "R338")
      (value "18k")
      (footprint "eagle-import:R0603")
      (fields
        (field (name "MANUFACTURER") "Stackpole")
        (field (name "POWER") "63 mW")
        (field (name "TOLERANCE") "±1 %")
      )
      (libsource (lib "eagle-import") (part "R-EU-R0603-18K"))
    )
    (comp (ref "R339")
      (value "18k")
      (footprint "eagle-import:R0603")
      (fields
        (field (name "MANUFACTURER") "Stackpole")
        (field (name "POWER") "63 mW")
        (field (name "TOLERANCE") "±1 %")
      )
      (libsource (lib "eagle-import") (part "R-EU-R0603-18K"))
    )
    (comp (ref "R340")
      (value "0R")
      (footprint "eagle-import:R0603")
      (fields
        (field (name "MANUFACTURER") "Stackpole")
        (field (name "POWER") "63 mW")
        (field (name "VOLTAGE") "50.0 V")
      )
      (libsource (lib "eagle-import") (part "R-EU-R0603-0R"))
    )
    (comp (ref "R341")
      (value "0R")
      (footprint "eagle-import:R0603")
      (fields
        (field (name "MANUFACTURER") "Stackpole")
        (field (name "POWER") "63 mW")
        (field (name "VOLTAGE") "50.0 V")
      )
      (libsource (lib "eagle-import") (part "R-EU-R0603-0R"))
    )
    (comp (ref "R342")
      (value "0R")
      (footprint "eagle-import:R0603")
      (fields
        (field (name "MANUFACTURER") "Stackpole")
        (field (name "POWER") "63 mW")
        (field (name "VOLTAGE") "50.0 V")
      )
      (libsource (lib "eagle-import") (part "R-EU-R0603-0R"))
    )
    (comp (ref "R343")
      (value "LVT12R0030GER")
      (footprint "eagle-import:LVT12_R003_OHMITE")
      (fields (field (name "MANUFACTURER") "ohmite") (field (name "TOLERANCE") "±2 %"))
      (libsource (lib "eagle-import") (part "LVT12R0030GER"))
    )
    (comp (ref "R344")
      (value "18k")
      (footprint "eagle-import:R0603")
      (fields
        (field (name "MANUFACTURER") "Stackpole")
        (field (name "POWER") "63 mW")
        (field (name "TOLERANCE") "±1 %")
      )
      (libsource (lib "eagle-import") (part "R-EU-R0603-18K"))
    )
    (comp (ref "R345")
      (value "27R")
      (footprint "eagle-import:R0603")
      (fields
        (field (name "MANUFACTURER") "Stackpole")
        (field (name "POWER") "63 mW")
        (field (name "TOLERANCE") "±1 %")
      )
      (libsource (lib "eagle-import") (part "R-EU-R0603-27R"))
    )
    (comp (ref "R346")
      (value "27R")
      (footprint "eagle-import:R0603")
      (fields
        (field (name "MANUFACTURER") "Stackpole")
        (field (name "POWER") "63 mW")
        (field (name "TOLERANCE") "±1 %")
      )
      (libsource (lib "eagle-import") (part "R-EU-R0603-27R"))
    )
    (comp (ref "R347")
      (value "3R3")
      (footprint "eagle-import:R0603")
      (fields
        (field (name "MANUFACTURER") "Uniroyal")
        (field (name "POWER") "63 mW")
        (field (name "TOLERANCE") "±1 %")
      )
      (libsource (lib "eagle-import") (part "R-EU-R0603-3R3"))
    )
    (comp (ref "R348")
      (value "442k")
      (footprint "eagle-import:R0603")
      (fields
        (field (name "MANUFACTURER") "Stackpole")
        (field (name "POWER") "63 mW")
        (field (name "TOLERANCE") "±1 %")
      )
      (libsource (lib "eagle-import") (part "R-EU-R0603-442K"))
    )
    (comp (ref "R349")
      (value "1k8")
      (footprint "eagle-import:R0603")
      (fields
        (field (name "MANUFACTURER") "Stackpole")
        (field (name "POWER") "63 mW")
        (field (name "TOLERANCE") "±1 %")
      )
      (libsource (lib "eagle-import") (part "R-EU-R0603-1K8"))
    )
    (comp (ref "R350")
      (value "1k8")
      (footprint "eagle-import:R0603")
      (fields
        (field (name "MANUFACTURER") "Stackpole")
        (field (name "POWER") "63 mW")
        (field (name "TOLERANCE") "±1 %")
      )
      (libsource (lib "eagle-import") (part "R-EU-R0603-1K8"))
    )
    (comp (ref "R351")
      (value "27R")
      (footprint "eagle-import:R0603")
      (fields
        (field (name "MANUFACTURER") "Stackpole")
        (field (name "POWER") "63 mW")
        (field (name "TOLERANCE") "±1 %")
      )
      (libsource (lib "eagle-import") (part "R-EU-R0603-27R"))
    )
    (comp (ref "R352")
      (value "27R")
      (footprint "eagle-import:R0603")
      (fields
        (field (name "MANUFACTURER") "Stackpole")
        (field (name "POWER") "63 mW")
        (field (name "TOLERANCE") "±1 %")
      )
      (libsource (lib "eagle-import") (part "R-EU-R0603-27R"))
    )
    (comp (ref "R353")
      (value "43k")
      (footprint "eagle-import:R0603")
      (fields
        (field (name "MANUFACTURER") "Uniroyal")
        (field (name "POWER") "63 mW")
        (field (name "TOLERANCE") "±1 %")
      )
      (libsource (lib "eagle-import") (part "R-EU-R0603-43K"))
    )
    (comp (ref "R354")
      (value "10k")
      (footprint "eagle-import:R0603")
      (fields
        (field (name "MANUFACTURER") "Stackpole")
        (field (name "POWER") "63 mW")
        (field (name "TOLERANCE") "±1 %")
      )
      (libsource (lib "eagle-import") (part "R-EU-R0603-10K"))
    )
    (comp (ref "R355")
      (value "10k")
      (footprint "eagle-import:R0603")
      (fields
        (field (name "MANUFACTURER") "Stackpole")
        (field (name "POWER") "63 mW")
        (field (name "TOLERANCE") "±1 %")
      )
      (libsource (lib "eagle-import") (part "R-EU-R0603-10K"))
    )
    (comp (ref "R356")
      (value "100k")
      (footprint "eagle-import:R0603")
      (fields
        (field (name "MANUFACTURER") "Stackpole")
        (field (name "POWER") "63 mW")
        (field (name "TOLERANCE") "±1 %")
      )
      (libsource (lib "eagle-import") (part "R-EU-R0603-100K"))
    )
    (comp (ref "R357")
      (value "100k")
      (footprint "eagle-import:R0603")
      (fields
        (field (name "MANUFACTURER") "Stackpole")
        (field (name "POWER") "63 mW")
        (field (name "TOLERANCE") "±1 %")
      )
      (libsource (lib "eagle-import") (part "R-EU-R0603-100K"))
    )
    (comp (ref "R358")
      (value "0R")
      (footprint "eagle-import:R0603")
      (fields
        (field (name "MANUFACTURER") "Stackpole")
        (field (name "POWER") "63 mW")
        (field (name "VOLTAGE") "50.0 V")
      )
      (libsource (lib "eagle-import") (part "R-EU-R0603-0R"))
    )
    (comp (ref "R359")
      (value "100k")
      (footprint "eagle-import:R0603")
      (fields
        (field (name "MANUFACTURER") "Stackpole")
        (field (name "POWER") "63 mW")
        (field (name "TOLERANCE") "±1 %")
      )
      (libsource (lib "eagle-import") (part "R-EU-R0603-100K"))
    )
    (comp (ref "R360")
      (value "0R")
      (footprint "eagle-import:R0603")
      (fields
        (field (name "MANUFACTURER") "Stackpole")
        (field (name "POWER") "63 mW")
        (field (name "VOLTAGE") "50.0 V")
      )
      (libsource (lib "eagle-import") (part "R-EU-R0603-0R"))
    )
    (comp (ref "R361")
      (value "0R")
      (footprint "eagle-import:R0603")
      (fields
        (field (name "MANUFACTURER") "Stackpole")
        (field (name "POWER") "63 mW")
        (field (name "VOLTAGE") "50.0 V")
      )
      (libsource (lib "eagle-import") (part "R-EU-R0603-0R"))
    )
    (comp (ref "R362")
      (value "1M")
      (footprint "eagle-import:R0603")
      (fields
        (field (name "MANUFACTURER") "Uniroyal")
        (field (name "POWER") "63 mW")
        (field (name "TOLERANCE") "±1 %")
      )
      (libsource (lib "eagle-import") (part "R-EU-R0603-1M"))
    )
    (comp (ref "R363")
      (value "LVT12R0050FER")
      (footprint "eagle-import:LVT12_R003_OHMITE")
      (fields (field (name "MANUFACTURER") "ohmite") (field (name "TOLERANCE") "±1 %"))
      (libsource (lib "eagle-import") (part "LVT12R0050FER"))
    )
    (comp (ref "R364")
      (value "12k")
      (footprint "eagle-import:R0603")
      (fields
        (field (name "MANUFACTURER") "Stackpole")
        (field (name "POWER") "63 mW")
        (field (name "TOLERANCE") "±1 %")
      )
      (libsource (lib "eagle-import") (part "R-EU-R0603-12K"))
    )
    (comp (ref "R365")
      (value "27R")
      (footprint "eagle-import:R0603")
      (fields
        (field (name "MANUFACTURER") "Stackpole")
        (field (name "POWER") "63 mW")
        (field (name "TOLERANCE") "±1 %")
      )
      (libsource (lib "eagle-import") (part "R-EU-R0603-27R"))
    )
    (comp (ref "R366")
      (value "18k")
      (footprint "eagle-import:R0603")
      (fields
        (field (name "MANUFACTURER") "Stackpole")
        (field (name "POWER") "63 mW")
        (field (name "TOLERANCE") "±1 %")
      )
      (libsource (lib "eagle-import") (part "R-EU-R0603-18K"))
    )
    (comp (ref "R367")
      (value "LVT12R0100FER")
      (footprint "eagle-import:LVT12_R003_OHMITE")
      (fields (field (name "MANUFACTURER") "ohmite") (field (name "TOLERANCE") "±1 %"))
      (libsource (lib "eagle-import") (part "LVT12R0100FER"))
    )
    (comp (ref "R368")
      (value "100k")
      (footprint "eagle-import:R0603")
      (fields
        (field (name "MANUFACTURER") "Stackpole")
        (field (name "POWER") "63 mW")
        (field (name "TOLERANCE") "±1 %")
      )
      (libsource (lib "eagle-import") (part "R-EU-R0603-100K"))
    )
    (comp (ref "R369")
      (value "43k")
      (footprint "eagle-import:R0603")
      (fields
        (field (name "MANUFACTURER") "Uniroyal")
        (field (name "POWER") "63 mW")
        (field (name "TOLERANCE") "±1 %")
      )
      (libsource (lib "eagle-import") (part "R-EU-R0603-43K"))
    )
    (comp (ref "R370")
      (value "3R3")
      (footprint "eagle-import:R0603")
      (fields
        (field (name "MANUFACTURER") "Uniroyal")
        (field (name "POWER") "63 mW")
        (field (name "TOLERANCE") "±1 %")
      )
      (libsource (lib "eagle-import") (part "R-EU-R0603-3R3"))
    )
    (comp (ref "R371")
      (value "100k")
      (footprint "eagle-import:R0603")
      (fields
        (field (name "MANUFACTURER") "Stackpole")
        (field (name "POWER") "63 mW")
        (field (name "TOLERANCE") "±1 %")
      )
      (libsource (lib "eagle-import") (part "R-EU-R0603-100K"))
    )
    (comp (ref "R372")
      (value "100k")
      (footprint "eagle-import:R0603")
      (fields
        (field (name "MANUFACTURER") "Stackpole")
        (field (name "POWER") "63 mW")
        (field (name "TOLERANCE") "±1 %")
      )
      (libsource (lib "eagle-import") (part "R-EU-R0603-100K"))
    )
    (comp (ref "R373")
      (value "43k")
      (footprint "eagle-import:R0603")
      (fields
        (field (name "MANUFACTURER") "Uniroyal")
        (field (name "POWER") "63 mW")
        (field (name "TOLERANCE") "±1 %")
      )
      (libsource (lib "eagle-import") (part "R-EU-R0603-43K"))
    )
    (comp (ref "R374")
      (value "18k")
      (footprint "eagle-import:R0603")
      (fields
        (field (name "MANUFACTURER") "Stackpole")
        (field (name "POWER") "63 mW")
        (field (name "TOLERANCE") "±1 %")
      )
      (libsource (lib "eagle-import") (part "R-EU-R0603-18K"))
    )
    (comp (ref "R375")
      (value "100k")
      (footprint "eagle-import:R0603")
      (fields
        (field (name "MANUFACTURER") "Stackpole")
        (field (name "POWER") "63 mW")
        (field (name "TOLERANCE") "±1 %")
      )
      (libsource (lib "eagle-import") (part "R-EU-R0603-100K"))
    )
    (comp (ref "R376")
      (value "100k")
      (footprint "eagle-import:R0603")
      (fields
        (field (name "MANUFACTURER") "Stackpole")
        (field (name "POWER") "63 mW")
        (field (name "TOLERANCE") "±1 %")
      )
      (libsource (lib "eagle-import") (part "R-EU-R0603-100K"))
    )
    (comp (ref "R377")
      (value "10k")
      (footprint "eagle-import:R0603")
      (fields
        (field (name "MANUFACTURER") "Stackpole")
        (field (name "POWER") "63 mW")
        (field (name "TOLERANCE") "±1 %")
      )
      (libsource (lib "eagle-import") (part "R-EU-R0603-10K"))
    )
    (comp (ref "R378")
      (value "10k")
      (footprint "eagle-import:R0603")
      (fields
        (field (name "MANUFACTURER") "Stackpole")
        (field (name "POWER") "63 mW")
        (field (name "TOLERANCE") "±1 %")
      )
      (libsource (lib "eagle-import") (part "R-EU-R0603-10K"))
    )
    (comp (ref "R379")
      (value "27R")
      (footprint "eagle-import:R0603")
      (fields
        (field (name "MANUFACTURER") "Stackpole")
        (field (name "POWER") "63 mW")
        (field (name "TOLERANCE") "±1 %")
      )
      (libsource (lib "eagle-import") (part "R-EU-R0603-27R"))
    )
    (comp (ref "R380")
      (value "0R")
      (footprint "eagle-import:R0603")
      (fields
        (field (name "MANUFACTURER") "Stackpole")
        (field (name "POWER") "63 mW")
        (field (name "VOLTAGE") "50.0 V")
      )
      (libsource (lib "eagle-import") (part "R-EU-R0603-0R"))
    )
    (comp (ref "R381")
      (value "100k")
      (footprint "eagle-import:R0603")
      (fields
        (field (name "MANUFACTURER") "Stackpole")
        (field (name "POWER") "63 mW")
        (field (name "TOLERANCE") "±1 %")
      )
      (libsource (lib "eagle-import") (part "R-EU-R0603-100K"))
    )
    (comp (ref "R382")
      (value "3R3")
      (footprint "eagle-import:R1210")
      (fields
        (field (name "MANUFACTURER") "YAGEO")
        (field (name "POWER") "500 mW")
        (field (name "TOLERANCE") "±1 %")
      )
      (libsource (lib "eagle-import") (part "R-EU-R1210-3R3"))
    )
    (comp (ref "R383")
      (value "100k")
      (footprint "eagle-import:R0603")
      (fields
        (field (name "MANUFACTURER") "Stackpole")
        (field (name "POWER") "63 mW")
        (field (name "TOLERANCE") "±1 %")
      )
      (libsource (lib "eagle-import") (part "R-EU-R0603-100K"))
    )
    (comp (ref "R384")
      (value "3R3")
      (footprint "eagle-import:R1210")
      (fields
        (field (name "MANUFACTURER") "YAGEO")
        (field (name "POWER") "500 mW")
        (field (name "TOLERANCE") "±1 %")
      )
      (libsource (lib "eagle-import") (part "R-EU-R1210-3R3"))
    )
    (comp (ref "R385")
      (value "100k")
      (footprint "eagle-import:R0603")
      (fields
        (field (name "MANUFACTURER") "Stackpole")
        (field (name "POWER") "63 mW")
        (field (name "TOLERANCE") "±1 %")
      )
      (libsource (lib "eagle-import") (part "R-EU-R0603-100K"))
    )
    (comp (ref "R386")
      (value "27R")
      (footprint "eagle-import:R0603")
      (fields
        (field (name "MANUFACTURER") "Stackpole")
        (field (name "POWER") "63 mW")
        (field (name "TOLERANCE") "±1 %")
      )
      (libsource (lib "eagle-import") (part "R-EU-R0603-27R"))
    )
    (comp (ref "R387")
      (value "18k")
      (footprint "eagle-import:R0603")
      (fields
        (field (name "MANUFACTURER") "Stackpole")
        (field (name "POWER") "63 mW")
        (field (name "TOLERANCE") "±1 %")
      )
      (libsource (lib "eagle-import") (part "R-EU-R0603-18K"))
    )
    (comp (ref "R388")
      (value "18k")
      (footprint "eagle-import:R0603")
      (fields
        (field (name "MANUFACTURER") "Stackpole")
        (field (name "POWER") "63 mW")
        (field (name "TOLERANCE") "±1 %")
      )
      (libsource (lib "eagle-import") (part "R-EU-R0603-18K"))
    )
    (comp (ref "R389")
      (value "18k")
      (footprint "eagle-import:R0603")
      (fields
        (field (name "MANUFACTURER") "Stackpole")
        (field (name "POWER") "63 mW")
        (field (name "TOLERANCE") "±1 %")
      )
      (libsource (lib "eagle-import") (part "R-EU-R0603-18K"))
    )
    (comp (ref "R390")
      (value "27R")
      (footprint "eagle-import:R0603")
      (fields
        (field (name "MANUFACTURER") "Stackpole")
        (field (name "POWER") "63 mW")
        (field (name "TOLERANCE") "±1 %")
      )
      (libsource (lib "eagle-import") (part "R-EU-R0603-27R"))
    )
    (comp (ref "R391")
      (value "27R")
      (footprint "eagle-import:R0603")
      (fields
        (field (name "MANUFACTURER") "Stackpole")
        (field (name "POWER") "63 mW")
        (field (name "TOLERANCE") "±1 %")
      )
      (libsource (lib "eagle-import") (part "R-EU-R0603-27R"))
    )
    (comp (ref "R392")
      (value "18k")
      (footprint "eagle-import:R0603")
      (fields
        (field (name "MANUFACTURER") "Stackpole")
        (field (name "POWER") "63 mW")
        (field (name "TOLERANCE") "±1 %")
      )
      (libsource (lib "eagle-import") (part "R-EU-R0603-18K"))
    )
    (comp (ref "R393")
      (value "18k")
      (footprint "eagle-import:R0603")
      (fields
        (field (name "MANUFACTURER") "Stackpole")
        (field (name "POWER") "63 mW")
        (field (name "TOLERANCE") "±1 %")
      )
      (libsource (lib "eagle-import") (part "R-EU-R0603-18K"))
    )
    (comp (ref "R394")
      (value "18k")
      (footprint "eagle-import:R0603")
      (fields
        (field (name "MANUFACTURER") "Stackpole")
        (field (name "POWER") "63 mW")
        (field (name "TOLERANCE") "±1 %")
      )
      (libsource (lib "eagle-import") (part "R-EU-R0603-18K"))
    )
    (comp (ref "R395")
      (value "27R")
      (footprint "eagle-import:R0603")
      (fields
        (field (name "MANUFACTURER") "Stackpole")
        (field (name "POWER") "63 mW")
        (field (name "TOLERANCE") "±1 %")
      )
      (libsource (lib "eagle-import") (part "R-EU-R0603-27R"))
    )
    (comp (ref "R396")
      (value "27R")
      (footprint "eagle-import:R0603")
      (fields
        (field (name "MANUFACTURER") "Stackpole")
        (field (name "POWER") "63 mW")
        (field (name "TOLERANCE") "±1 %")
      )
      (libsource (lib "eagle-import") (part "R-EU-R0603-27R"))
    )
    (comp (ref "R397")
      (value "18k")
      (footprint "eagle-import:R0603")
      (fields
        (field (name "MANUFACTURER") "Stackpole")
        (field (name "POWER") "63 mW")
        (field (name "TOLERANCE") "±1 %")
      )
      (libsource (lib "eagle-import") (part "R-EU-R0603-18K"))
    )
    (comp (ref "R398")
      (value "18k")
      (footprint "eagle-import:R0603")
      (fields
        (field (name "MANUFACTURER") "Stackpole")
        (field (name "POWER") "63 mW")
        (field (name "TOLERANCE") "±1 %")
      )
      (libsource (lib "eagle-import") (part "R-EU-R0603-18K"))
    )
    (comp (ref "R399")
      (value "18k")
      (footprint "eagle-import:R0603")
      (fields
        (field (name "MANUFACTURER") "Stackpole")
        (field (name "POWER") "63 mW")
        (field (name "TOLERANCE") "±1 %")
      )
      (libsource (lib "eagle-import") (part "R-EU-R0603-18K"))
    )
    (comp (ref "R400")
      (value "27R")
      (footprint "eagle-import:R0603")
      (fields
        (field (name "MANUFACTURER") "Stackpole")
        (field (name "POWER") "63 mW")
        (field (name "TOLERANCE") "±1 %")
      )
      (libsource (lib "eagle-import") (part "R-EU-R0603-27R"))
    )
    (comp (ref "R401")
      (value "27R")
      (footprint "eagle-import:R0603")
      (fields
        (field (name "MANUFACTURER") "Stackpole")
        (field (name "POWER") "63 mW")
        (field (name "TOLERANCE") "±1 %")
      )
      (libsource (lib "eagle-import") (part "R-EU-R0603-27R"))
    )
    (comp (ref "R402")
      (value "18k")
      (footprint "eagle-import:R0603")
      (fields
        (field (name "MANUFACTURER") "Stackpole")
        (field (name "POWER") "63 mW")
        (field (name "TOLERANCE") "±1 %")
      )
      (libsource (lib "eagle-import") (part "R-EU-R0603-18K"))
    )
    (comp (ref "R403")
      (value "18k")
      (footprint "eagle-import:R0603")
      (fields
        (field (name "MANUFACTURER") "Stackpole")
        (field (name "POWER") "63 mW")
        (field (name "TOLERANCE") "±1 %")
      )
      (libsource (lib "eagle-import") (part "R-EU-R0603-18K"))
    )
    (comp (ref "R404")
      (value "18k")
      (footprint "eagle-import:R0603")
      (fields
        (field (name "MANUFACTURER") "Stackpole")
        (field (name "POWER") "63 mW")
        (field (name "TOLERANCE") "±1 %")
      )
      (libsource (lib "eagle-import") (part "R-EU-R0603-18K"))
    )
    (comp (ref "R405")
      (value "27R")
      (footprint "eagle-import:R0603")
      (fields
        (field (name "MANUFACTURER") "Stackpole")
        (field (name "POWER") "63 mW")
        (field (name "TOLERANCE") "±1 %")
      )
      (libsource (lib "eagle-import") (part "R-EU-R0603-27R"))
    )
    (comp (ref "R406")
      (value "27R")
      (footprint "eagle-import:R0603")
      (fields
        (field (name "MANUFACTURER") "Stackpole")
        (field (name "POWER") "63 mW")
        (field (name "TOLERANCE") "±1 %")
      )
      (libsource (lib "eagle-import") (part "R-EU-R0603-27R"))
    )
    (comp (ref "R407")
      (value "18k")
      (footprint "eagle-import:R0603")
      (fields
        (field (name "MANUFACTURER") "Stackpole")
        (field (name "POWER") "63 mW")
        (field (name "TOLERANCE") "±1 %")
      )
      (libsource (lib "eagle-import") (part "R-EU-R0603-18K"))
    )
    (comp (ref "R408")
      (value "18k")
      (footprint "eagle-import:R0603")
      (fields
        (field (name "MANUFACTURER") "Stackpole")
        (field (name "POWER") "63 mW")
        (field (name "TOLERANCE") "±1 %")
      )
      (libsource (lib "eagle-import") (part "R-EU-R0603-18K"))
    )
    (comp (ref "R409")
      (value "18k")
      (footprint "eagle-import:R0603")
      (fields
        (field (name "MANUFACTURER") "Stackpole")
        (field (name "POWER") "63 mW")
        (field (name "TOLERANCE") "±1 %")
      )
      (libsource (lib "eagle-import") (part "R-EU-R0603-18K"))
    )
    (comp (ref "R410")
      (value "3R3")
      (footprint "eagle-import:R1210")
      (fields
        (field (name "MANUFACTURER") "YAGEO")
        (field (name "POWER") "500 mW")
        (field (name "TOLERANCE") "±1 %")
      )
      (libsource (lib "eagle-import") (part "R-EU-R1210-3R3"))
    )
    (comp (ref "R411")
      (value "3R3")
      (footprint "eagle-import:R1210")
      (fields
        (field (name "MANUFACTURER") "YAGEO")
        (field (name "POWER") "500 mW")
        (field (name "TOLERANCE") "±1 %")
      )
      (libsource (lib "eagle-import") (part "R-EU-R1210-3R3"))
    )
    (comp (ref "R412")
      (value "3R3")
      (footprint "eagle-import:R1210")
      (fields
        (field (name "MANUFACTURER") "YAGEO")
        (field (name "POWER") "500 mW")
        (field (name "TOLERANCE") "±1 %")
      )
      (libsource (lib "eagle-import") (part "R-EU-R1210-3R3"))
    )
    (comp (ref "R413")
      (value "3R3")
      (footprint "eagle-import:R1210")
      (fields
        (field (name "MANUFACTURER") "YAGEO")
        (field (name "POWER") "500 mW")
        (field (name "TOLERANCE") "±1 %")
      )
      (libsource (lib "eagle-import") (part "R-EU-R1210-3R3"))
    )
    (comp (ref "R414")
      (value "100k")
      (footprint "eagle-import:R0603")
      (fields
        (field (name "MANUFACTURER") "Stackpole")
        (field (name "POWER") "63 mW")
        (field (name "TOLERANCE") "±1 %")
      )
      (libsource (lib "eagle-import") (part "R-EU-R0603-100K"))
    )
    (comp (ref "R415")
      (value "100k")
      (footprint "eagle-import:R0603")
      (fields
        (field (name "MANUFACTURER") "Stackpole")
        (field (name "POWER") "63 mW")
        (field (name "TOLERANCE") "±1 %")
      )
      (libsource (lib "eagle-import") (part "R-EU-R0603-100K"))
    )
    (comp (ref "R416")
      (value "27R")
      (footprint "eagle-import:R0603")
      (fields
        (field (name "MANUFACTURER") "Stackpole")
        (field (name "POWER") "63 mW")
        (field (name "TOLERANCE") "±1 %")
      )
      (libsource (lib "eagle-import") (part "R-EU-R0603-27R"))
    )
    (comp (ref "R417")
      (value "R-EU-R0603")
      (footprint "eagle-import:R0603")
      (fields
        (field (name "POWER") "63 mW")
        (field (name "TOLERANCE") "±1 %")
        (field (name "VOLTAGE") "50 V")
      )
      (libsource (lib "eagle-import") (part "R-EU-R0603"))
    )
    (comp (ref "R418")
      (value "10k 0.1%")
      (footprint "eagle-import:R0603")
      (fields
        (field (name "MANUFACTURER") "KOA Speer")
        (field (name "POWER") "63 mW")
        (field (name "TOLERANCE") "±0.1 %")
      )
      (libsource (lib "eagle-import") (part "R-EU-R0603-10K-0P1"))
    )
    (comp (ref "R419")
      (value "47k 0.1%")
      (footprint "eagle-import:R0603")
      (fields
        (field (name "MANUFACTURER") "YAGEO")
        (field (name "POWER") "63 mW")
        (field (name "TOLERANCE") "±0.1 %")
      )
      (libsource (lib "eagle-import") (part "R-EU-R0603-47K-0P1"))
    )
    (comp (ref "R420")
      (value "0R")
      (footprint "eagle-import:R0603")
      (fields
        (field (name "MANUFACTURER") "Stackpole")
        (field (name "POWER") "63 mW")
        (field (name "VOLTAGE") "50.0 V")
      )
      (libsource (lib "eagle-import") (part "R-EU-R0603-0R"))
    )
    (comp (ref "R421")
      (value "27R")
      (footprint "eagle-import:R0603")
      (fields
        (field (name "MANUFACTURER") "Stackpole")
        (field (name "POWER") "63 mW")
        (field (name "TOLERANCE") "±1 %")
      )
      (libsource (lib "eagle-import") (part "R-EU-R0603-27R"))
    )
    (comp (ref "R422")
      (value "27R")
      (footprint "eagle-import:R0603")
      (fields
        (field (name "MANUFACTURER") "Stackpole")
        (field (name "POWER") "63 mW")
        (field (name "TOLERANCE") "±1 %")
      )
      (libsource (lib "eagle-import") (part "R-EU-R0603-27R"))
    )
    (comp (ref "R423")
      (value "10k 0.1%")
      (footprint "eagle-import:R0603")
      (fields
        (field (name "MANUFACTURER") "KOA Speer")
        (field (name "POWER") "63 mW")
        (field (name "TOLERANCE") "±0.1 %")
      )
      (libsource (lib "eagle-import") (part "R-EU-R0603-10K-0P1"))
    )
    (comp (ref "R424")
      (value "47k 0.1%")
      (footprint "eagle-import:R0603")
      (fields
        (field (name "MANUFACTURER") "YAGEO")
        (field (name "POWER") "63 mW")
        (field (name "TOLERANCE") "±0.1 %")
      )
      (libsource (lib "eagle-import") (part "R-EU-R0603-47K-0P1"))
    )
    (comp (ref "R425")
      (value "47k 0.1%")
      (footprint "eagle-import:R0603")
      (fields
        (field (name "MANUFACTURER") "YAGEO")
        (field (name "POWER") "63 mW")
        (field (name "TOLERANCE") "±0.1 %")
      )
      (libsource (lib "eagle-import") (part "R-EU-R0603-47K-0P1"))
    )
    (comp (ref "R426")
      (value "10k 0.1%")
      (footprint "eagle-import:R0603")
      (fields
        (field (name "MANUFACTURER") "KOA Speer")
        (field (name "POWER") "63 mW")
        (field (name "TOLERANCE") "±0.1 %")
      )
      (libsource (lib "eagle-import") (part "R-EU-R0603-10K-0P1"))
    )
    (comp (ref "R427")
      (value "0R")
      (footprint "eagle-import:R0603")
      (fields
        (field (name "MANUFACTURER") "Stackpole")
        (field (name "POWER") "63 mW")
        (field (name "VOLTAGE") "50.0 V")
      )
      (libsource (lib "eagle-import") (part "R-EU-R0603-0R"))
    )
    (comp (ref "R428")
      (value "27R")
      (footprint "eagle-import:R0603")
      (fields
        (field (name "MANUFACTURER") "Stackpole")
        (field (name "POWER") "63 mW")
        (field (name "TOLERANCE") "±1 %")
      )
      (libsource (lib "eagle-import") (part "R-EU-R0603-27R"))
    )
    (comp (ref "R429")
      (value "27R")
      (footprint "eagle-import:R0603")
      (fields
        (field (name "MANUFACTURER") "Stackpole")
        (field (name "POWER") "63 mW")
        (field (name "TOLERANCE") "±1 %")
      )
      (libsource (lib "eagle-import") (part "R-EU-R0603-27R"))
    )
    (comp (ref "R430")
      (value "442k")
      (footprint "eagle-import:R0603")
      (fields
        (field (name "MANUFACTURER") "Stackpole")
        (field (name "POWER") "63 mW")
        (field (name "TOLERANCE") "±1 %")
      )
      (libsource (lib "eagle-import") (part "R-EU-R0603-442K"))
    )
    (comp (ref "R431")
      (value "47k 0.1%")
      (footprint "eagle-import:R0603")
      (fields
        (field (name "MANUFACTURER") "YAGEO")
        (field (name "POWER") "63 mW")
        (field (name "TOLERANCE") "±0.1 %")
      )
      (libsource (lib "eagle-import") (part "R-EU-R0603-47K-0P1"))
    )
    (comp (ref "R432")
      (value "27R")
      (footprint "eagle-import:R0603")
      (fields
        (field (name "MANUFACTURER") "Stackpole")
        (field (name "POWER") "63 mW")
        (field (name "TOLERANCE") "±1 %")
      )
      (libsource (lib "eagle-import") (part "R-EU-R0603-27R"))
    )
    (comp (ref "R433")
      (value "27R")
      (footprint "eagle-import:R0603")
      (fields
        (field (name "MANUFACTURER") "Stackpole")
        (field (name "POWER") "63 mW")
        (field (name "TOLERANCE") "±1 %")
      )
      (libsource (lib "eagle-import") (part "R-EU-R0603-27R"))
    )
    (comp (ref "R434")
      (value "27R")
      (footprint "eagle-import:R0603")
      (fields
        (field (name "MANUFACTURER") "Stackpole")
        (field (name "POWER") "63 mW")
        (field (name "TOLERANCE") "±1 %")
      )
      (libsource (lib "eagle-import") (part "R-EU-R0603-27R"))
    )
    (comp (ref "R435")
      (value "27R")
      (footprint "eagle-import:R0603")
      (fields
        (field (name "MANUFACTURER") "Stackpole")
        (field (name "POWER") "63 mW")
        (field (name "TOLERANCE") "±1 %")
      )
      (libsource (lib "eagle-import") (part "R-EU-R0603-27R"))
    )
    (comp (ref "R436")
      (value "27R")
      (footprint "eagle-import:R0603")
      (fields
        (field (name "MANUFACTURER") "Stackpole")
        (field (name "POWER") "63 mW")
        (field (name "TOLERANCE") "±1 %")
      )
      (libsource (lib "eagle-import") (part "R-EU-R0603-27R"))
    )
    (comp (ref "R437")
      (value "27R")
      (footprint "eagle-import:R0603")
      (fields
        (field (name "MANUFACTURER") "Stackpole")
        (field (name "POWER") "63 mW")
        (field (name "TOLERANCE") "±1 %")
      )
      (libsource (lib "eagle-import") (part "R-EU-R0603-27R"))
    )
    (comp (ref "R438")
      (value "27R")
      (footprint "eagle-import:R0603")
      (fields
        (field (name "MANUFACTURER") "Stackpole")
        (field (name "POWER") "63 mW")
        (field (name "TOLERANCE") "±1 %")
      )
      (libsource (lib "eagle-import") (part "R-EU-R0603-27R"))
    )
    (comp (ref "R439")
      (value "100k")
      (footprint "eagle-import:R0603")
      (fields
        (field (name "MANUFACTURER") "Stackpole")
        (field (name "POWER") "63 mW")
        (field (name "TOLERANCE") "±1 %")
      )
      (libsource (lib "eagle-import") (part "R-EU-R0603-100K"))
    )
    (comp (ref "R440")
      (value "1k8")
      (footprint "eagle-import:R0603")
      (fields
        (field (name "MANUFACTURER") "Stackpole")
        (field (name "POWER") "63 mW")
        (field (name "TOLERANCE") "±1 %")
      )
      (libsource (lib "eagle-import") (part "R-EU-R0603-1K8"))
    )
    (comp (ref "R441")
      (value "0R")
      (footprint "eagle-import:R0603")
      (fields
        (field (name "MANUFACTURER") "Stackpole")
        (field (name "POWER") "63 mW")
        (field (name "VOLTAGE") "50.0 V")
      )
      (libsource (lib "eagle-import") (part "R-EU-R0603-0R"))
    )
    (comp (ref "R442")
      (value "27R")
      (footprint "eagle-import:R0603")
      (fields
        (field (name "MANUFACTURER") "Stackpole")
        (field (name "POWER") "63 mW")
        (field (name "TOLERANCE") "±1 %")
      )
      (libsource (lib "eagle-import") (part "R-EU-R0603-27R"))
    )
    (comp (ref "R443")
      (value "27R")
      (footprint "eagle-import:R0603")
      (fields
        (field (name "MANUFACTURER") "Stackpole")
        (field (name "POWER") "63 mW")
        (field (name "TOLERANCE") "±1 %")
      )
      (libsource (lib "eagle-import") (part "R-EU-R0603-27R"))
    )
    (comp (ref "R444")
      (value "100k")
      (footprint "eagle-import:R0603")
      (fields
        (field (name "MANUFACTURER") "Stackpole")
        (field (name "POWER") "63 mW")
        (field (name "TOLERANCE") "±1 %")
      )
      (libsource (lib "eagle-import") (part "R-EU-R0603-100K"))
    )
    (comp (ref "R445")
      (value "100k")
      (footprint "eagle-import:R0603")
      (fields
        (field (name "MANUFACTURER") "Stackpole")
        (field (name "POWER") "63 mW")
        (field (name "TOLERANCE") "±1 %")
      )
      (libsource (lib "eagle-import") (part "R-EU-R0603-100K"))
    )
    (comp (ref "R446")
      (value "0R")
      (footprint "eagle-import:R0603")
      (fields
        (field (name "MANUFACTURER") "Stackpole")
        (field (name "POWER") "63 mW")
        (field (name "VOLTAGE") "50.0 V")
      )
      (libsource (lib "eagle-import") (part "R-EU-R0603-0R"))
    )
    (comp (ref "R447")
      (value "100k")
      (footprint "eagle-import:R0603")
      (fields
        (field (name "MANUFACTURER") "Stackpole")
        (field (name "POWER") "63 mW")
        (field (name "TOLERANCE") "±1 %")
      )
      (libsource (lib "eagle-import") (part "R-EU-R0603-100K"))
    )
    (comp (ref "R448")
      (value "27R")
      (footprint "eagle-import:R0603")
      (fields
        (field (name "MANUFACTURER") "Stackpole")
        (field (name "POWER") "63 mW")
        (field (name "TOLERANCE") "±1 %")
      )
      (libsource (lib "eagle-import") (part "R-EU-R0603-27R"))
    )
    (comp (ref "R449")
      (value "1M")
      (footprint "eagle-import:R0603")
      (fields
        (field (name "MANUFACTURER") "Uniroyal")
        (field (name "POWER") "63 mW")
        (field (name "TOLERANCE") "±1 %")
      )
      (libsource (lib "eagle-import") (part "R-EU-R0603-1M"))
    )
    (comp (ref "R450")
      (value "0R")
      (footprint "eagle-import:R0603")
      (fields
        (field (name "MANUFACTURER") "Stackpole")
        (field (name "POWER") "63 mW")
        (field (name "VOLTAGE") "50.0 V")
      )
      (libsource (lib "eagle-import") (part "R-EU-R0603-0R"))
    )
    (comp (ref "R451")
      (value "0R")
      (footprint "eagle-import:R0603")
      (fields
        (field (name "MANUFACTURER") "Stackpole")
        (field (name "POWER") "63 mW")
        (field (name "VOLTAGE") "50.0 V")
      )
      (libsource (lib "eagle-import") (part "R-EU-R0603-0R"))
    )
    (comp (ref "R452")
      (value "0R")
      (footprint "eagle-import:R0603")
      (fields
        (field (name "MANUFACTURER") "Stackpole")
        (field (name "POWER") "63 mW")
        (field (name "VOLTAGE") "50.0 V")
      )
      (libsource (lib "eagle-import") (part "R-EU-R0603-0R"))
    )
    (comp (ref "R453")
      (value "0R")
      (footprint "eagle-import:R0603")
      (fields
        (field (name "MANUFACTURER") "Stackpole")
        (field (name "POWER") "63 mW")
        (field (name "VOLTAGE") "50.0 V")
      )
      (libsource (lib "eagle-import") (part "R-EU-R0603-0R"))
    )
    (comp (ref "R454")
      (value "0R")
      (footprint "eagle-import:R0603")
      (fields
        (field (name "MANUFACTURER") "Stackpole")
        (field (name "POWER") "63 mW")
        (field (name "VOLTAGE") "50.0 V")
      )
      (libsource (lib "eagle-import") (part "R-EU-R0603-0R"))
    )
    (comp (ref "R455")
      (value "0R")
      (footprint "eagle-import:R0603")
      (fields
        (field (name "MANUFACTURER") "Stackpole")
        (field (name "POWER") "63 mW")
        (field (name "VOLTAGE") "50.0 V")
      )
      (libsource (lib "eagle-import") (part "R-EU-R0603-0R"))
    )
    (comp (ref "R456")
      (value "0R15")
      (footprint "eagle-import:R1206")
      (fields
        (field (name "MANUFACTURER") "Uniroyal")
        (field (name "POWER") "250 mW")
        (field (name "TOLERANCE") "±1 %")
      )
      (libsource (lib "eagle-import") (part "R-EU-R1206-0R15"))
    )
    (comp (ref "R457")
      (value "3R3")
      (footprint "eagle-import:R0603")
      (fields
        (field (name "MANUFACTURER") "Uniroyal")
        (field (name "POWER") "63 mW")
        (field (name "TOLERANCE") "±1 %")
      )
      (libsource (lib "eagle-import") (part "R-EU-R0603-3R3"))
    )
    (comp (ref "R458")
      (value "3R3")
      (footprint "eagle-import:R0603")
      (fields
        (field (name "MANUFACTURER") "Uniroyal")
        (field (name "POWER") "63 mW")
        (field (name "TOLERANCE") "±1 %")
      )
      (libsource (lib "eagle-import") (part "R-EU-R0603-3R3"))
    )
    (comp (ref "R459")
      (value "0R")
      (footprint "eagle-import:R0603")
      (fields
        (field (name "MANUFACTURER") "Stackpole")
        (field (name "POWER") "63 mW")
        (field (name "VOLTAGE") "50.0 V")
      )
      (libsource (lib "eagle-import") (part "R-EU-R0603-0R"))
    )
    (comp (ref "R460")
      (value "0R")
      (footprint "eagle-import:R0603")
      (fields
        (field (name "MANUFACTURER") "Stackpole")
        (field (name "POWER") "63 mW")
        (field (name "VOLTAGE") "50.0 V")
      )
      (libsource (lib "eagle-import") (part "R-EU-R0603-0R"))
    )
    (comp (ref "R461")
      (value "0R")
      (footprint "eagle-import:R0603")
      (fields
        (field (name "MANUFACTURER") "Stackpole")
        (field (name "POWER") "63 mW")
        (field (name "VOLTAGE") "50.0 V")
      )
      (libsource (lib "eagle-import") (part "R-EU-R0603-0R"))
    )
    (comp (ref "R462")
      (value "27R")
      (footprint "eagle-import:R0603")
      (fields
        (field (name "MANUFACTURER") "Stackpole")
        (field (name "POWER") "63 mW")
        (field (name "TOLERANCE") "±1 %")
      )
      (libsource (lib "eagle-import") (part "R-EU-R0603-27R"))
    )
    (comp (ref "R463")
      (value "0R")
      (footprint "eagle-import:R0603")
      (fields
        (field (name "MANUFACTURER") "Stackpole")
        (field (name "POWER") "63 mW")
        (field (name "VOLTAGE") "50.0 V")
      )
      (libsource (lib "eagle-import") (part "R-EU-R0603-0R"))
    )
    (comp (ref "R464")
      (value "27R")
      (footprint "eagle-import:R0603")
      (fields
        (field (name "MANUFACTURER") "Stackpole")
        (field (name "POWER") "63 mW")
        (field (name "TOLERANCE") "±1 %")
      )
      (libsource (lib "eagle-import") (part "R-EU-R0603-27R"))
    )
    (comp (ref "R465")
      (value "27R")
      (footprint "eagle-import:R0603")
      (fields
        (field (name "MANUFACTURER") "Stackpole")
        (field (name "POWER") "63 mW")
        (field (name "TOLERANCE") "±1 %")
      )
      (libsource (lib "eagle-import") (part "R-EU-R0603-27R"))
    )
    (comp (ref "R466")
      (value "27R")
      (footprint "eagle-import:R0603")
      (fields
        (field (name "MANUFACTURER") "Stackpole")
        (field (name "POWER") "63 mW")
        (field (name "TOLERANCE") "±1 %")
      )
      (libsource (lib "eagle-import") (part "R-EU-R0603-27R"))
    )
    (comp (ref "R467")
      (value "27R")
      (footprint "eagle-import:R0603")
      (fields
        (field (name "MANUFACTURER") "Stackpole")
        (field (name "POWER") "63 mW")
        (field (name "TOLERANCE") "±1 %")
      )
      (libsource (lib "eagle-import") (part "R-EU-R0603-27R"))
    )
    (comp (ref "R468")
      (value "0R")
      (footprint "eagle-import:R0603")
      (fields
        (field (name "MANUFACTURER") "Stackpole")
        (field (name "POWER") "63 mW")
        (field (name "VOLTAGE") "50.0 V")
      )
      (libsource (lib "eagle-import") (part "R-EU-R0603-0R"))
    )
    (comp (ref "R469")
      (value "27R")
      (footprint "eagle-import:R0603")
      (fields
        (field (name "MANUFACTURER") "Stackpole")
        (field (name "POWER") "63 mW")
        (field (name "TOLERANCE") "±1 %")
      )
      (libsource (lib "eagle-import") (part "R-EU-R0603-27R"))
    )
    (comp (ref "R470")
      (value "27R")
      (footprint "eagle-import:R0603")
      (fields
        (field (name "MANUFACTURER") "Stackpole")
        (field (name "POWER") "63 mW")
        (field (name "TOLERANCE") "±1 %")
      )
      (libsource (lib "eagle-import") (part "R-EU-R0603-27R"))
    )
    (comp (ref "R471")
      (value "27R")
      (footprint "eagle-import:R0603")
      (fields
        (field (name "MANUFACTURER") "Stackpole")
        (field (name "POWER") "63 mW")
        (field (name "TOLERANCE") "±1 %")
      )
      (libsource (lib "eagle-import") (part "R-EU-R0603-27R"))
    )
    (comp (ref "R472")
      (value "27R")
      (footprint "eagle-import:R0603")
      (fields
        (field (name "MANUFACTURER") "Stackpole")
        (field (name "POWER") "63 mW")
        (field (name "TOLERANCE") "±1 %")
      )
      (libsource (lib "eagle-import") (part "R-EU-R0603-27R"))
    )
    (comp (ref "R473")
      (value "27R")
      (footprint "eagle-import:R0603")
      (fields
        (field (name "MANUFACTURER") "Stackpole")
        (field (name "POWER") "63 mW")
        (field (name "TOLERANCE") "±1 %")
      )
      (libsource (lib "eagle-import") (part "R-EU-R0603-27R"))
    )
    (comp (ref "R474")
      (value "R-EU-R0603")
      (footprint "eagle-import:R0603")
      (fields
        (field (name "POWER") "63 mW")
        (field (name "TOLERANCE") "±1 %")
        (field (name "VOLTAGE") "50 V")
      )
      (libsource (lib "eagle-import") (part "R-EU-R0603"))
    )
    (comp (ref "R475")
      (value "27R")
      (footprint "eagle-import:R0603")
      (fields
        (field (name "MANUFACTURER") "Stackpole")
        (field (name "POWER") "63 mW")
        (field (name "TOLERANCE") "±1 %")
      )
      (libsource (lib "eagle-import") (part "R-EU-R0603-27R"))
    )
    (comp (ref "R476")
      (value "27R")
      (footprint "eagle-import:R0603")
      (fields
        (field (name "MANUFACTURER") "Stackpole")
        (field (name "POWER") "63 mW")
        (field (name "TOLERANCE") "±1 %")
      )
      (libsource (lib "eagle-import") (part "R-EU-R0603-27R"))
    )
    (comp (ref "R477")
      (value "27R")
      (footprint "eagle-import:R0603")
      (fields
        (field (name "MANUFACTURER") "Stackpole")
        (field (name "POWER") "63 mW")
        (field (name "TOLERANCE") "±1 %")
      )
      (libsource (lib "eagle-import") (part "R-EU-R0603-27R"))
    )
    (comp (ref "R478")
      (value "27R")
      (footprint "eagle-import:R0603")
      (fields
        (field (name "MANUFACTURER") "Stackpole")
        (field (name "POWER") "63 mW")
        (field (name "TOLERANCE") "±1 %")
      )
      (libsource (lib "eagle-import") (part "R-EU-R0603-27R"))
    )
    (comp (ref "R479")
      (value "27R")
      (footprint "eagle-import:R0603")
      (fields
        (field (name "MANUFACTURER") "Stackpole")
        (field (name "POWER") "63 mW")
        (field (name "TOLERANCE") "±1 %")
      )
      (libsource (lib "eagle-import") (part "R-EU-R0603-27R"))
    )
    (comp (ref "R480")
      (value "100k")
      (footprint "eagle-import:R0603")
      (fields
        (field (name "MANUFACTURER") "Stackpole")
        (field (name "POWER") "63 mW")
        (field (name "TOLERANCE") "±1 %")
      )
      (libsource (lib "eagle-import") (part "R-EU-R0603-100K"))
    )
    (comp (ref "R481")
      (value "10k")
      (footprint "eagle-import:R0603")
      (fields
        (field (name "MANUFACTURER") "Stackpole")
        (field (name "POWER") "63 mW")
        (field (name "TOLERANCE") "±1 %")
      )
      (libsource (lib "eagle-import") (part "R-EU-R0603-10K"))
    )
    (comp (ref "R482")
      (value "10k")
      (footprint "eagle-import:R0603")
      (fields
        (field (name "MANUFACTURER") "Stackpole")
        (field (name "POWER") "63 mW")
        (field (name "TOLERANCE") "±1 %")
      )
      (libsource (lib "eagle-import") (part "R-EU-R0603-10K"))
    )
    (comp (ref "R483")
      (value "100k")
      (footprint "eagle-import:R0603")
      (fields
        (field (name "MANUFACTURER") "Stackpole")
        (field (name "POWER") "63 mW")
        (field (name "TOLERANCE") "±1 %")
      )
      (libsource (lib "eagle-import") (part "R-EU-R0603-100K"))
    )
    (comp (ref "R484")
      (value "R-EU-R0603")
      (footprint "eagle-import:R0603")
      (fields
        (field (name "POWER") "63 mW")
        (field (name "TOLERANCE") "±1 %")
        (field (name "VOLTAGE") "50 V")
      )
      (libsource (lib "eagle-import") (part "R-EU-R0603"))
    )
    (comp (ref "R485")
      (value "R-EU-R0603")
      (footprint "eagle-import:R0603")
      (fields
        (field (name "POWER") "63 mW")
        (field (name "TOLERANCE") "±1 %")
        (field (name "VOLTAGE") "50 V")
      )
      (libsource (lib "eagle-import") (part "R-EU-R0603"))
    )
    (comp (ref "R486")
      (value "0R")
      (footprint "eagle-import:R0603")
      (fields
        (field (name "MANUFACTURER") "Stackpole")
        (field (name "POWER") "63 mW")
        (field (name "VOLTAGE") "50.0 V")
      )
      (libsource (lib "eagle-import") (part "R-EU-R0603-0R"))
    )
    (comp (ref "R487")
      (value "0R")
      (footprint "eagle-import:R0603")
      (fields
        (field (name "MANUFACTURER") "Stackpole")
        (field (name "POWER") "63 mW")
        (field (name "VOLTAGE") "50.0 V")
      )
      (libsource (lib "eagle-import") (part "R-EU-R0603-0R"))
    )
    (comp (ref "R488")
      (value "R-EU-R0603")
      (footprint "eagle-import:R0603")
      (fields
        (field (name "POWER") "63 mW")
        (field (name "TOLERANCE") "±1 %")
        (field (name "VOLTAGE") "50 V")
      )
      (libsource (lib "eagle-import") (part "R-EU-R0603"))
    )
    (comp (ref "R489")
      (value "0R")
      (footprint "eagle-import:R0603")
      (fields
        (field (name "MANUFACTURER") "Stackpole")
        (field (name "POWER") "63 mW")
        (field (name "VOLTAGE") "50.0 V")
      )
      (libsource (lib "eagle-import") (part "R-EU-R0603-0R"))
    )
    (comp (ref "R490")
      (value "0R")
      (footprint "eagle-import:R0603")
      (fields
        (field (name "MANUFACTURER") "Stackpole")
        (field (name "POWER") "63 mW")
        (field (name "VOLTAGE") "50.0 V")
      )
      (libsource (lib "eagle-import") (part "R-EU-R0603-0R"))
    )
    (comp (ref "R491")
      (value "0R")
      (footprint "eagle-import:R0603")
      (fields
        (field (name "MANUFACTURER") "Stackpole")
        (field (name "POWER") "63 mW")
        (field (name "VOLTAGE") "50.0 V")
      )
      (libsource (lib "eagle-import") (part "R-EU-R0603-0R"))
    )
    (comp (ref "R492")
      (value "100k")
      (footprint "eagle-import:R0603")
      (fields
        (field (name "MANUFACTURER") "Stackpole")
        (field (name "POWER") "63 mW")
        (field (name "TOLERANCE") "±1 %")
      )
      (libsource (lib "eagle-import") (part "R-EU-R0603-100K"))
    )
    (comp (ref "R493")
      (value "27R")
      (footprint "eagle-import:R0603")
      (fields
        (field (name "MANUFACTURER") "Stackpole")
        (field (name "POWER") "63 mW")
        (field (name "TOLERANCE") "±1 %")
      )
      (libsource (lib "eagle-import") (part "R-EU-R0603-27R"))
    )
    (comp (ref "R494")
      (value "27R")
      (footprint "eagle-import:R0603")
      (fields
        (field (name "MANUFACTURER") "Stackpole")
        (field (name "POWER") "63 mW")
        (field (name "TOLERANCE") "±1 %")
      )
      (libsource (lib "eagle-import") (part "R-EU-R0603-27R"))
    )
    (comp (ref "R495")
      (value "27R")
      (footprint "eagle-import:R0603")
      (fields
        (field (name "MANUFACTURER") "Stackpole")
        (field (name "POWER") "63 mW")
        (field (name "TOLERANCE") "±1 %")
      )
      (libsource (lib "eagle-import") (part "R-EU-R0603-27R"))
    )
    (comp (ref "R496")
      (value "27R")
      (footprint "eagle-import:R0603")
      (fields
        (field (name "MANUFACTURER") "Stackpole")
        (field (name "POWER") "63 mW")
        (field (name "TOLERANCE") "±1 %")
      )
      (libsource (lib "eagle-import") (part "R-EU-R0603-27R"))
    )
    (comp (ref "R497")
      (value "27R")
      (footprint "eagle-import:R0603")
      (fields
        (field (name "MANUFACTURER") "Stackpole")
        (field (name "POWER") "63 mW")
        (field (name "TOLERANCE") "±1 %")
      )
      (libsource (lib "eagle-import") (part "R-EU-R0603-27R"))
    )
    (comp (ref "R498")
      (value "27R")
      (footprint "eagle-import:R0603")
      (fields
        (field (name "MANUFACTURER") "Stackpole")
        (field (name "POWER") "63 mW")
        (field (name "TOLERANCE") "±1 %")
      )
      (libsource (lib "eagle-import") (part "R-EU-R0603-27R"))
    )
    (comp (ref "R499")
      (value "27R")
      (footprint "eagle-import:R0603")
      (fields
        (field (name "MANUFACTURER") "Stackpole")
        (field (name "POWER") "63 mW")
        (field (name "TOLERANCE") "±1 %")
      )
      (libsource (lib "eagle-import") (part "R-EU-R0603-27R"))
    )
    (comp (ref "R500")
      (value "27R")
      (footprint "eagle-import:R0603")
      (fields
        (field (name "MANUFACTURER") "Stackpole")
        (field (name "POWER") "63 mW")
        (field (name "TOLERANCE") "±1 %")
      )
      (libsource (lib "eagle-import") (part "R-EU-R0603-27R"))
    )
    (comp (ref "R501")
      (value "27R")
      (footprint "eagle-import:R0603")
      (fields
        (field (name "MANUFACTURER") "Stackpole")
        (field (name "POWER") "63 mW")
        (field (name "TOLERANCE") "±1 %")
      )
      (libsource (lib "eagle-import") (part "R-EU-R0603-27R"))
    )
    (comp (ref "R502")
      (value "27R")
      (footprint "eagle-import:R0603")
      (fields
        (field (name "MANUFACTURER") "Stackpole")
        (field (name "POWER") "63 mW")
        (field (name "TOLERANCE") "±1 %")
      )
      (libsource (lib "eagle-import") (part "R-EU-R0603-27R"))
    )
    (comp (ref "R503")
      (value "27R")
      (footprint "eagle-import:R0603")
      (fields
        (field (name "MANUFACTURER") "Stackpole")
        (field (name "POWER") "63 mW")
        (field (name "TOLERANCE") "±1 %")
      )
      (libsource (lib "eagle-import") (part "R-EU-R0603-27R"))
    )
    (comp (ref "R504")
      (value "27R")
      (footprint "eagle-import:R0603")
      (fields
        (field (name "MANUFACTURER") "Stackpole")
        (field (name "POWER") "63 mW")
        (field (name "TOLERANCE") "±1 %")
      )
      (libsource (lib "eagle-import") (part "R-EU-R0603-27R"))
    )
    (comp (ref "R505")
      (value "27R")
      (footprint "eagle-import:R0603")
      (fields
        (field (name "MANUFACTURER") "Stackpole")
        (field (name "POWER") "63 mW")
        (field (name "TOLERANCE") "±1 %")
      )
      (libsource (lib "eagle-import") (part "R-EU-R0603-27R"))
    )
    (comp (ref "R506")
      (value "27R")
      (footprint "eagle-import:R0603")
      (fields
        (field (name "MANUFACTURER") "Stackpole")
        (field (name "POWER") "63 mW")
        (field (name "TOLERANCE") "±1 %")
      )
      (libsource (lib "eagle-import") (part "R-EU-R0603-27R"))
    )
    (comp (ref "R507")
      (value "27R")
      (footprint "eagle-import:R0603")
      (fields
        (field (name "MANUFACTURER") "Stackpole")
        (field (name "POWER") "63 mW")
        (field (name "TOLERANCE") "±1 %")
      )
      (libsource (lib "eagle-import") (part "R-EU-R0603-27R"))
    )
    (comp (ref "R508")
      (value "100k")
      (footprint "eagle-import:R0603")
      (fields
        (field (name "MANUFACTURER") "Stackpole")
        (field (name "POWER") "63 mW")
        (field (name "TOLERANCE") "±1 %")
      )
      (libsource (lib "eagle-import") (part "R-EU-R0603-100K"))
    )
    (comp (ref "R509")
      (value "0R")
      (footprint "eagle-import:R0603")
      (fields
        (field (name "MANUFACTURER") "Stackpole")
        (field (name "POWER") "63 mW")
        (field (name "VOLTAGE") "50.0 V")
      )
      (libsource (lib "eagle-import") (part "R-EU-R0603-0R"))
    )
    (comp (ref "R510")
      (value "100k")
      (footprint "eagle-import:R0603")
      (fields
        (field (name "MANUFACTURER") "Stackpole")
        (field (name "POWER") "63 mW")
        (field (name "TOLERANCE") "±1 %")
      )
      (libsource (lib "eagle-import") (part "R-EU-R0603-100K"))
    )
    (comp (ref "R511")
      (value "1M")
      (footprint "eagle-import:R0603")
      (fields
        (field (name "MANUFACTURER") "Uniroyal")
        (field (name "POWER") "63 mW")
        (field (name "TOLERANCE") "±1 %")
      )
      (libsource (lib "eagle-import") (part "R-EU-R0603-1M"))
    )
    (comp (ref "R512")
      (value "47k 0.1%")
      (footprint "eagle-import:R0603")
      (fields
        (field (name "MANUFACTURER") "YAGEO")
        (field (name "POWER") "63 mW")
        (field (name "TOLERANCE") "±0.1 %")
      )
      (libsource (lib "eagle-import") (part "R-EU-R0603-47K-0P1"))
    )
    (comp (ref "R513")
      (value "18k")
      (footprint "eagle-import:R0603")
      (fields
        (field (name "MANUFACTURER") "Stackpole")
        (field (name "POWER") "63 mW")
        (field (name "TOLERANCE") "±1 %")
      )
      (libsource (lib "eagle-import") (part "R-EU-R0603-18K"))
    )
    (comp (ref "R514")
      (value "R-EU-R0603")
      (footprint "eagle-import:R0603")
      (fields
        (field (name "POWER") "63 mW")
        (field (name "TOLERANCE") "±1 %")
        (field (name "VOLTAGE") "50 V")
      )
      (libsource (lib "eagle-import") (part "R-EU-R0603"))
    )
    (comp (ref "R515")
      (value "R-EU-R0603")
      (footprint "eagle-import:R0603")
      (fields
        (field (name "POWER") "63 mW")
        (field (name "TOLERANCE") "±1 %")
        (field (name "VOLTAGE") "50 V")
      )
      (libsource (lib "eagle-import") (part "R-EU-R0603"))
    )
    (comp (ref "R516")
      (value "27R")
      (footprint "eagle-import:R0603")
      (fields
        (field (name "MANUFACTURER") "Stackpole")
        (field (name "POWER") "63 mW")
        (field (name "TOLERANCE") "±1 %")
      )
      (libsource (lib "eagle-import") (part "R-EU-R0603-27R"))
    )
    (comp (ref "R517")
      (value "27R")
      (footprint "eagle-import:R0603")
      (fields
        (field (name "MANUFACTURER") "Stackpole")
        (field (name "POWER") "63 mW")
        (field (name "TOLERANCE") "±1 %")
      )
      (libsource (lib "eagle-import") (part "R-EU-R0603-27R"))
    )
    (comp (ref "R518")
      (value "27R")
      (footprint "eagle-import:R0603")
      (fields
        (field (name "MANUFACTURER") "Stackpole")
        (field (name "POWER") "63 mW")
        (field (name "TOLERANCE") "±1 %")
      )
      (libsource (lib "eagle-import") (part "R-EU-R0603-27R"))
    )
    (comp (ref "R519")
      (value "18k")
      (footprint "eagle-import:R0603")
      (fields
        (field (name "MANUFACTURER") "Stackpole")
        (field (name "POWER") "63 mW")
        (field (name "TOLERANCE") "±1 %")
      )
      (libsource (lib "eagle-import") (part "R-EU-R0603-18K"))
    )
    (comp (ref "R520")
      (value "100k")
      (footprint "eagle-import:R0603")
      (fields
        (field (name "MANUFACTURER") "Stackpole")
        (field (name "POWER") "63 mW")
        (field (name "TOLERANCE") "±1 %")
      )
      (libsource (lib "eagle-import") (part "R-EU-R0603-100K"))
    )
    (comp (ref "R521")
      (value "R-EU-R0603")
      (footprint "eagle-import:R0603")
      (fields
        (field (name "POWER") "63 mW")
        (field (name "TOLERANCE") "±1 %")
        (field (name "VOLTAGE") "50 V")
      )
      (libsource (lib "eagle-import") (part "R-EU-R0603"))
    )
    (comp (ref "R522")
      (value "0R")
      (footprint "eagle-import:R0603")
      (fields
        (field (name "MANUFACTURER") "Stackpole")
        (field (name "POWER") "63 mW")
        (field (name "VOLTAGE") "50.0 V")
      )
      (libsource (lib "eagle-import") (part "R-EU-R0603-0R"))
    )
    (comp (ref "R523")
      (value "R-EU-R0603")
      (footprint "eagle-import:R0603")
      (fields
        (field (name "POWER") "63 mW")
        (field (name "TOLERANCE") "±1 %")
        (field (name "VOLTAGE") "50 V")
      )
      (libsource (lib "eagle-import") (part "R-EU-R0603"))
    )
    (comp (ref "R524")
      (value "100k")
      (footprint "eagle-import:R0603")
      (fields
        (field (name "MANUFACTURER") "Stackpole")
        (field (name "POWER") "63 mW")
        (field (name "TOLERANCE") "±1 %")
      )
      (libsource (lib "eagle-import") (part "R-EU-R0603-100K"))
    )
    (comp (ref "R525")
      (value "R-EU-R0603")
      (footprint "eagle-import:R0603")
      (fields
        (field (name "POWER") "63 mW")
        (field (name "TOLERANCE") "±1 %")
        (field (name "VOLTAGE") "50 V")
      )
      (libsource (lib "eagle-import") (part "R-EU-R0603"))
    )
    (comp (ref "R526")
      (value "0R")
      (footprint "eagle-import:R0603")
      (fields
        (field (name "MANUFACTURER") "Stackpole")
        (field (name "POWER") "63 mW")
        (field (name "VOLTAGE") "50.0 V")
      )
      (libsource (lib "eagle-import") (part "R-EU-R0603-0R"))
    )
    (comp (ref "R527")
      (value "100k")
      (footprint "eagle-import:R0603")
      (fields
        (field (name "MANUFACTURER") "Stackpole")
        (field (name "POWER") "63 mW")
        (field (name "TOLERANCE") "±1 %")
      )
      (libsource (lib "eagle-import") (part "R-EU-R0603-100K"))
    )
    (comp (ref "R528")
      (value "442k")
      (footprint "eagle-import:R0603")
      (fields
        (field (name "MANUFACTURER") "Stackpole")
        (field (name "POWER") "63 mW")
        (field (name "TOLERANCE") "±1 %")
      )
      (libsource (lib "eagle-import") (part "R-EU-R0603-442K"))
    )
    (comp (ref "R529")
      (value "0R")
      (footprint "eagle-import:R0603")
      (fields
        (field (name "MANUFACTURER") "Stackpole")
        (field (name "POWER") "63 mW")
        (field (name "VOLTAGE") "50.0 V")
      )
      (libsource (lib "eagle-import") (part "R-EU-R0603-0R"))
    )
    (comp (ref "R530")
      (value "18k")
      (footprint "eagle-import:R0603")
      (fields
        (field (name "MANUFACTURER") "Stackpole")
        (field (name "POWER") "63 mW")
        (field (name "TOLERANCE") "±1 %")
      )
      (libsource (lib "eagle-import") (part "R-EU-R0603-18K"))
    )
    (comp (ref "R531")
      (value "R-EU-R0603")
      (footprint "eagle-import:R0603")
      (fields
        (field (name "POWER") "63 mW")
        (field (name "TOLERANCE") "±1 %")
        (field (name "VOLTAGE") "50 V")
      )
      (libsource (lib "eagle-import") (part "R-EU-R0603"))
    )
    (comp (ref "R532")
      (value "27R")
      (footprint "eagle-import:R0603")
      (fields
        (field (name "MANUFACTURER") "Stackpole")
        (field (name "POWER") "63 mW")
        (field (name "TOLERANCE") "±1 %")
      )
      (libsource (lib "eagle-import") (part "R-EU-R0603-27R"))
    )
    (comp (ref "R533")
      (value "100k")
      (footprint "eagle-import:R0603")
      (fields
        (field (name "MANUFACTURER") "Stackpole")
        (field (name "POWER") "63 mW")
        (field (name "TOLERANCE") "±1 %")
      )
      (libsource (lib "eagle-import") (part "R-EU-R0603-100K"))
    )
    (comp (ref "R534")
      (value "R-EU-R0603")
      (footprint "eagle-import:R0603")
      (fields
        (field (name "POWER") "63 mW")
        (field (name "TOLERANCE") "±1 %")
        (field (name "VOLTAGE") "50 V")
      )
      (libsource (lib "eagle-import") (part "R-EU-R0603"))
    )
    (comp (ref "R535")
      (value "100k")
      (footprint "eagle-import:R0603")
      (fields
        (field (name "MANUFACTURER") "Stackpole")
        (field (name "POWER") "63 mW")
        (field (name "TOLERANCE") "±1 %")
      )
      (libsource (lib "eagle-import") (part "R-EU-R0603-100K"))
    )
    (comp (ref "R536")
      (value "27R")
      (footprint "eagle-import:R0603")
      (fields
        (field (name "MANUFACTURER") "Stackpole")
        (field (name "POWER") "63 mW")
        (field (name "TOLERANCE") "±1 %")
      )
      (libsource (lib "eagle-import") (part "R-EU-R0603-27R"))
    )
    (comp (ref "R537")
      (value "27R")
      (footprint "eagle-import:R0603")
      (fields
        (field (name "MANUFACTURER") "Stackpole")
        (field (name "POWER") "63 mW")
        (field (name "TOLERANCE") "±1 %")
      )
      (libsource (lib "eagle-import") (part "R-EU-R0603-27R"))
    )
    (comp (ref "R538")
      (value "R-EU-R0603")
      (footprint "eagle-import:R0603")
      (fields
        (field (name "POWER") "63 mW")
        (field (name "TOLERANCE") "±1 %")
        (field (name "VOLTAGE") "50 V")
      )
      (libsource (lib "eagle-import") (part "R-EU-R0603"))
    )
    (comp (ref "R539")
      (value "100k")
      (footprint "eagle-import:R0603")
      (fields
        (field (name "MANUFACTURER") "Stackpole")
        (field (name "POWER") "63 mW")
        (field (name "TOLERANCE") "±1 %")
      )
      (libsource (lib "eagle-import") (part "R-EU-R0603-100K"))
    )
    (comp (ref "R540")
      (value "27R")
      (footprint "eagle-import:R0603")
      (fields
        (field (name "MANUFACTURER") "Stackpole")
        (field (name "POWER") "63 mW")
        (field (name "TOLERANCE") "±1 %")
      )
      (libsource (lib "eagle-import") (part "R-EU-R0603-27R"))
    )
    (comp (ref "R541")
      (value "27R")
      (footprint "eagle-import:R0603")
      (fields
        (field (name "MANUFACTURER") "Stackpole")
        (field (name "POWER") "63 mW")
        (field (name "TOLERANCE") "±1 %")
      )
      (libsource (lib "eagle-import") (part "R-EU-R0603-27R"))
    )
    (comp (ref "R542")
      (value "R-EU-R0603")
      (footprint "eagle-import:R0603")
      (fields
        (field (name "POWER") "63 mW")
        (field (name "TOLERANCE") "±1 %")
        (field (name "VOLTAGE") "50 V")
      )
      (libsource (lib "eagle-import") (part "R-EU-R0603"))
    )
    (comp (ref "R543")
      (value "R-EU-R0603")
      (footprint "eagle-import:R0603")
      (fields
        (field (name "POWER") "63 mW")
        (field (name "TOLERANCE") "±1 %")
        (field (name "VOLTAGE") "50 V")
      )
      (libsource (lib "eagle-import") (part "R-EU-R0603"))
    )
    (comp (ref "R544")
      (value "R-EU-R0603")
      (footprint "eagle-import:R0603")
      (fields
        (field (name "POWER") "63 mW")
        (field (name "TOLERANCE") "±1 %")
        (field (name "VOLTAGE") "50 V")
      )
      (libsource (lib "eagle-import") (part "R-EU-R0603"))
    )
    (comp (ref "R545")
      (value "27R")
      (footprint "eagle-import:R0603")
      (fields
        (field (name "MANUFACTURER") "Stackpole")
        (field (name "POWER") "63 mW")
        (field (name "TOLERANCE") "±1 %")
      )
      (libsource (lib "eagle-import") (part "R-EU-R0603-27R"))
    )
    (comp (ref "R546")
      (value "R-EU-R0603")
      (footprint "eagle-import:R0603")
      (fields
        (field (name "POWER") "63 mW")
        (field (name "TOLERANCE") "±1 %")
        (field (name "VOLTAGE") "50 V")
      )
      (libsource (lib "eagle-import") (part "R-EU-R0603"))
    )
    (comp (ref "R547")
      (value "R-EU-R0603")
      (footprint "eagle-import:R0603")
      (fields
        (field (name "POWER") "63 mW")
        (field (name "TOLERANCE") "±1 %")
        (field (name "VOLTAGE") "50 V")
      )
      (libsource (lib "eagle-import") (part "R-EU-R0603"))
    )
    (comp (ref "R548")
      (value "27R")
      (footprint "eagle-import:R0603")
      (fields
        (field (name "MANUFACTURER") "Stackpole")
        (field (name "POWER") "63 mW")
        (field (name "TOLERANCE") "±1 %")
      )
      (libsource (lib "eagle-import") (part "R-EU-R0603-27R"))
    )
    (comp (ref "R549")
      (value "R-EU-R0603")
      (footprint "eagle-import:R0603")
      (fields
        (field (name "POWER") "63 mW")
        (field (name "TOLERANCE") "±1 %")
        (field (name "VOLTAGE") "50 V")
      )
      (libsource (lib "eagle-import") (part "R-EU-R0603"))
    )
    (comp (ref "R550")
      (value "100k")
      (footprint "eagle-import:R0603")
      (fields
        (field (name "MANUFACTURER") "Stackpole")
        (field (name "POWER") "63 mW")
        (field (name "TOLERANCE") "±1 %")
      )
      (libsource (lib "eagle-import") (part "R-EU-R0603-100K"))
    )
    (comp (ref "R551")
      (value "0R")
      (footprint "eagle-import:R0603")
      (fields
        (field (name "MANUFACTURER") "Stackpole")
        (field (name "POWER") "63 mW")
        (field (name "VOLTAGE") "50.0 V")
      )
      (libsource (lib "eagle-import") (part "R-EU-R0603-0R"))
    )
    (comp (ref "R552")
      (value "10k")
      (footprint "eagle-import:R0603")
      (fields
        (field (name "MANUFACTURER") "Stackpole")
        (field (name "POWER") "63 mW")
        (field (name "TOLERANCE") "±1 %")
      )
      (libsource (lib "eagle-import") (part "R-EU-R0603-10K"))
    )
    (comp (ref "R553")
      (value "18k")
      (footprint "eagle-import:R0603")
      (fields
        (field (name "MANUFACTURER") "Stackpole")
        (field (name "POWER") "63 mW")
        (field (name "TOLERANCE") "±1 %")
      )
      (libsource (lib "eagle-import") (part "R-EU-R0603-18K"))
    )
    (comp (ref "R554")
      (value "27R")
      (footprint "eagle-import:R0603")
      (fields
        (field (name "MANUFACTURER") "Stackpole")
        (field (name "POWER") "63 mW")
        (field (name "TOLERANCE") "±1 %")
      )
      (libsource (lib "eagle-import") (part "R-EU-R0603-27R"))
    )
    (comp (ref "R555")
      (value "100k")
      (footprint "eagle-import:R0603")
      (fields
        (field (name "MANUFACTURER") "Stackpole")
        (field (name "POWER") "63 mW")
        (field (name "TOLERANCE") "±1 %")
      )
      (libsource (lib "eagle-import") (part "R-EU-R0603-100K"))
    )
    (comp (ref "R556")
      (value "27R")
      (footprint "eagle-import:R0603")
      (fields
        (field (name "MANUFACTURER") "Stackpole")
        (field (name "POWER") "63 mW")
        (field (name "TOLERANCE") "±1 %")
      )
      (libsource (lib "eagle-import") (part "R-EU-R0603-27R"))
    )
    (comp (ref "R557")
      (value "27R")
      (footprint "eagle-import:R0603")
      (fields
        (field (name "MANUFACTURER") "Stackpole")
        (field (name "POWER") "63 mW")
        (field (name "TOLERANCE") "±1 %")
      )
      (libsource (lib "eagle-import") (part "R-EU-R0603-27R"))
    )
    (comp (ref "R558")
      (value "27R")
      (footprint "eagle-import:R0603")
      (fields
        (field (name "MANUFACTURER") "Stackpole")
        (field (name "POWER") "63 mW")
        (field (name "TOLERANCE") "±1 %")
      )
      (libsource (lib "eagle-import") (part "R-EU-R0603-27R"))
    )
    (comp (ref "R559")
      (value "0R")
      (footprint "eagle-import:R0603")
      (fields
        (field (name "MANUFACTURER") "Stackpole")
        (field (name "POWER") "63 mW")
        (field (name "VOLTAGE") "50.0 V")
      )
      (libsource (lib "eagle-import") (part "R-EU-R0603-0R"))
    )
    (comp (ref "R560")
      (value "R-EU-R0603")
      (footprint "eagle-import:R0603")
      (fields
        (field (name "POWER") "63 mW")
        (field (name "TOLERANCE") "±1 %")
        (field (name "VOLTAGE") "50 V")
      )
      (libsource (lib "eagle-import") (part "R-EU-R0603"))
    )
    (comp (ref "R561")
      (value "R-EU-R0603")
      (footprint "eagle-import:R0603")
      (fields
        (field (name "POWER") "63 mW")
        (field (name "TOLERANCE") "±1 %")
        (field (name "VOLTAGE") "50 V")
      )
      (libsource (lib "eagle-import") (part "R-EU-R0603"))
    )
    (comp (ref "R562")
      (value "R-EU-R0603")
      (footprint "eagle-import:R0603")
      (fields
        (field (name "POWER") "63 mW")
        (field (name "TOLERANCE") "±1 %")
        (field (name "VOLTAGE") "50 V")
      )
      (libsource (lib "eagle-import") (part "R-EU-R0603"))
    )
    (comp (ref "R563")
      (value "0R")
      (footprint "eagle-import:R0603")
      (fields
        (field (name "MANUFACTURER") "Stackpole")
        (field (name "POWER") "63 mW")
        (field (name "VOLTAGE") "50.0 V")
      )
      (libsource (lib "eagle-import") (part "R-EU-R0603-0R"))
    )
    (comp (ref "R564")
      (value "27R")
      (footprint "eagle-import:R0603")
      (fields
        (field (name "MANUFACTURER") "Stackpole")
        (field (name "POWER") "63 mW")
        (field (name "TOLERANCE") "±1 %")
      )
      (libsource (lib "eagle-import") (part "R-EU-R0603-27R"))
    )
    (comp (ref "R565")
      (value "0R")
      (footprint "eagle-import:R0603")
      (fields
        (field (name "MANUFACTURER") "Stackpole")
        (field (name "POWER") "63 mW")
        (field (name "VOLTAGE") "50.0 V")
      )
      (libsource (lib "eagle-import") (part "R-EU-R0603-0R"))
    )
    (comp (ref "R566")
      (value "100k")
      (footprint "eagle-import:R0603")
      (fields
        (field (name "MANUFACTURER") "Stackpole")
        (field (name "POWER") "63 mW")
        (field (name "TOLERANCE") "±1 %")
      )
      (libsource (lib "eagle-import") (part "R-EU-R0603-100K"))
    )
    (comp (ref "SPACER1")
      (value "9774065151")
      (footprint "eagle-import:WA-SMSI_9774065151_WUERTH")
      (fields (field (name "MANUFACTURER") "Wuerth"))
      (libsource (lib "eagle-import") (part "9774065151"))
    )
    (comp (ref "SPACER2")
      (value "9774065151")
      (footprint "eagle-import:WA-SMSI_9774065151_WUERTH")
      (fields (field (name "MANUFACTURER") "Wuerth"))
      (libsource (lib "eagle-import") (part "9774065151"))
    )
    (comp (ref "SPACER4")
      (value "9774025360")
      (footprint "eagle-import:WA-SMSI_9774025360_WUERTH")
      (fields (field (name "MANUFACTURER") "Wuerth"))
      (libsource (lib "eagle-import") (part "9774025360"))
    )
    (comp (ref "SPACER5")
      (value "9774025360")
      (footprint "eagle-import:WA-SMSI_9774025360_WUERTH")
      (fields (field (name "MANUFACTURER") "Wuerth"))
      (libsource (lib "eagle-import") (part "9774025360"))
    )
    (comp (ref "SPACER6")
      (value "9774025360")
      (footprint "eagle-import:WA-SMSI_9774025360_WUERTH")
      (fields (field (name "MANUFACTURER") "Wuerth"))
      (libsource (lib "eagle-import") (part "9774025360"))
    )
    (comp (ref "SPACER7")
      (value "9774060360")
      (footprint "eagle-import:WA-SMSI_9774060360_WUERTH")
      (fields (field (name "MANUFACTURER") "Wuerth"))
      (libsource (lib "eagle-import") (part "9774060360"))
    )
    (comp (ref "SPACER8")
      (value "9774060360")
      (footprint "eagle-import:WA-SMSI_9774060360_WUERTH")
      (fields (field (name "MANUFACTURER") "Wuerth"))
      (libsource (lib "eagle-import") (part "9774060360"))
    )
    (comp (ref "SPACER9")
      (value "9774025360")
      (footprint "eagle-import:WA-SMSI_9774025360_WUERTH")
      (fields (field (name "MANUFACTURER") "Wuerth"))
      (libsource (lib "eagle-import") (part "9774025360"))
    )
    (comp (ref "SPACER10")
      (value "9774025360")
      (footprint "eagle-import:WA-SMSI_9774025360_WUERTH")
      (fields (field (name "MANUFACTURER") "Wuerth"))
      (libsource (lib "eagle-import") (part "9774025360"))
    )
    (comp (ref "SPACER11")
      (value "9774025360")
      (footprint "eagle-import:WA-SMSI_9774025360_WUERTH")
      (fields (field (name "MANUFACTURER") "Wuerth"))
      (libsource (lib "eagle-import") (part "9774025360"))
    )
    (comp (ref "SPACER12")
      (value "9774025360")
      (footprint "eagle-import:WA-SMSI_9774025360_WUERTH")
      (fields (field (name "MANUFACTURER") "Wuerth"))
      (libsource (lib "eagle-import") (part "9774025360"))
    )
    (comp (ref "SPACER13")
      (value "9774060360")
      (footprint "eagle-import:WA-SMSI_9774060360_WUERTH")
      (fields (field (name "MANUFACTURER") "Wuerth"))
      (libsource (lib "eagle-import") (part "9774060360"))
    )
    (comp (ref "T1")
      (value "DMG1012UW-7")
      (footprint "eagle-import:SOT-323_DIODES_INC")
      (fields (field (name "MANUFACTURER") "Diodes Inc"))
      (libsource (lib "eagle-import") (part "DMG1012UW-7"))
    )
    (comp (ref "T2")
      (value "DMG1012UW-7")
      (footprint "eagle-import:SOT-323_DIODES_INC")
      (fields (field (name "MANUFACTURER") "Diodes Inc"))
      (libsource (lib "eagle-import") (part "DMG1012UW-7"))
    )
    (comp (ref "T3")
      (value "DMP2006UFG")
      (footprint "eagle-import:POWERDI3333-8_DIODES_INC")
      (fields (field (name "MANUFACTURER") "Diodes Inc"))
      (libsource (lib "eagle-import") (part "DMP2006UFG"))
    )
    (comp (ref "T4")
      (value "PMF170XP")
      (footprint "eagle-import:SOT-323_SC-70_NXP")
      (fields (field (name "MANUFACTURER") "Nexperia"))
      (libsource (lib "eagle-import") (part "PMF170XP"))
    )
    (comp (ref "T5")
      (value "DMG1012UW-7")
      (footprint "eagle-import:SOT-323_DIODES_INC")
      (fields (field (name "MANUFACTURER") "Diodes Inc"))
      (libsource (lib "eagle-import") (part "DMG1012UW-7"))
    )
    (comp (ref "T6")
      (value "DMG1012UW-7")
      (footprint "eagle-import:SOT-323_DIODES_INC")
      (fields (field (name "MANUFACTURER") "Diodes Inc"))
      (libsource (lib "eagle-import") (part "DMG1012UW-7"))
    )
    (comp (ref "T7")
      (value "DMG1012UW-7")
      (footprint "eagle-import:SOT-323_DIODES_INC")
      (fields (field (name "MANUFACTURER") "Diodes Inc"))
      (libsource (lib "eagle-import") (part "DMG1012UW-7"))
    )
    (comp (ref "T8")
      (value "NX7002AK")
      (footprint "eagle-import:SOT-23_NXP")
      (fields (field (name "MANUFACTURER") "Nexperia"))
      (libsource (lib "eagle-import") (part "NX7002AK"))
    )
    (comp (ref "T9")
      (value "CSD18512Q5B")
      (footprint "eagle-import:Q5B_TI")
      (fields (field (name "MANUFACTURER") "TI"))
      (libsource (lib "eagle-import") (part "CSD18512Q5B"))
    )
    (comp (ref "T10")
      (value "DMG1012UW-7")
      (footprint "eagle-import:SOT-323_DIODES_INC")
      (fields (field (name "MANUFACTURER") "Diodes Inc"))
      (libsource (lib "eagle-import") (part "DMG1012UW-7"))
    )
    (comp (ref "T11")
      (value "DMG1012UW-7")
      (footprint "eagle-import:SOT-323_DIODES_INC")
      (fields (field (name "MANUFACTURER") "Diodes Inc"))
      (libsource (lib "eagle-import") (part "DMG1012UW-7"))
    )
    (comp (ref "T12")
      (value "NX7002AK")
      (footprint "eagle-import:SOT-23_NXP")
      (fields (field (name "MANUFACTURER") "Nexperia"))
      (libsource (lib "eagle-import") (part "NX7002AK"))
    )
    (comp (ref "T13")
      (value "DMG1012UW-7")
      (footprint "eagle-import:SOT-323_DIODES_INC")
      (fields (field (name "MANUFACTURER") "Diodes Inc"))
      (libsource (lib "eagle-import") (part "DMG1012UW-7"))
    )
    (comp (ref "T14")
      (value "DMG1012UW-7")
      (footprint "eagle-import:SOT-323_DIODES_INC")
      (fields (field (name "MANUFACTURER") "Diodes Inc"))
      (libsource (lib "eagle-import") (part "DMG1012UW-7"))
    )
    (comp (ref "T15")
      (value "CSD18504Q5A")
      (footprint "eagle-import:Q5A_TI")
      (fields (field (name "MANUFACTURER") "TI"))
      (libsource (lib "eagle-import") (part "CSD18504Q5A"))
    )
    (comp (ref "T16")
      (value "CSD18512Q5B")
      (footprint "eagle-import:Q5B_TI")
      (fields (field (name "MANUFACTURER") "TI"))
      (libsource (lib "eagle-import") (part "CSD18512Q5B"))
    )
    (comp (ref "T17")
      (value "n.m.")
      (footprint "eagle-import:SOT-323_DIODES_INC")
      (fields (field (name "MANUFACTURER") "Diodes Inc"))
      (libsource (lib "eagle-import") (part "DMG1012UW-7"))
    )
    (comp (ref "T18")
      (value "NX7002AK")
      (footprint "eagle-import:SOT-23_NXP")
      (fields (field (name "MANUFACTURER") "Nexperia"))
      (libsource (lib "eagle-import") (part "NX7002AK"))
    )
    (comp (ref "T19")
      (value "CSD15571Q2")
      (footprint "eagle-import:Q2_TI")
      (fields (field (name "MANUFACTURER") "TI"))
      (libsource (lib "eagle-import") (part "CSD15571Q2"))
    )
    (comp (ref "T20")
      (value "CSD15571Q2")
      (footprint "eagle-import:Q2_TI")
      (fields (field (name "MANUFACTURER") "TI"))
      (libsource (lib "eagle-import") (part "CSD15571Q2"))
    )
    (comp (ref "T21")
      (value "DMP2006UFG")
      (footprint "eagle-import:POWERDI3333-8_DIODES_INC")
      (fields (field (name "MANUFACTURER") "Diodes Inc"))
      (libsource (lib "eagle-import") (part "DMP2006UFG"))
    )
    (comp (ref "T22")
      (value "DMG1012UW-7")
      (footprint "eagle-import:SOT-323_DIODES_INC")
      (fields (field (name "MANUFACTURER") "Diodes Inc"))
      (libsource (lib "eagle-import") (part "DMG1012UW-7"))
    )
    (comp (ref "T23")
      (value "DMG1012UW-7")
      (footprint "eagle-import:SOT-323_DIODES_INC")
      (fields (field (name "MANUFACTURER") "Diodes Inc"))
      (libsource (lib "eagle-import") (part "DMG1012UW-7"))
    )
    (comp (ref "T24")
      (value "PMF170XP")
      (footprint "eagle-import:SOT-323_SC-70_NXP")
      (fields (field (name "MANUFACTURER") "Nexperia"))
      (libsource (lib "eagle-import") (part "PMF170XP"))
    )
    (comp (ref "T25")
      (value "DMG1012UW-7")
      (footprint "eagle-import:SOT-323_DIODES_INC")
      (fields (field (name "MANUFACTURER") "Diodes Inc"))
      (libsource (lib "eagle-import") (part "DMG1012UW-7"))
    )
    (comp (ref "T26")
      (value "DMG1012UW-7")
      (footprint "eagle-import:SOT-323_DIODES_INC")
      (fields (field (name "MANUFACTURER") "Diodes Inc"))
      (libsource (lib "eagle-import") (part "DMG1012UW-7"))
    )
    (comp (ref "T27")
      (value "DMG1012UW-7")
      (footprint "eagle-import:SOT-323_DIODES_INC")
      (fields (field (name "MANUFACTURER") "Diodes Inc"))
      (libsource (lib "eagle-import") (part "DMG1012UW-7"))
    )
    (comp (ref "T28")
      (value "DMG1012UW-7")
      (footprint "eagle-import:SOT-323_DIODES_INC")
      (fields (field (name "MANUFACTURER") "Diodes Inc"))
      (libsource (lib "eagle-import") (part "DMG1012UW-7"))
    )
    (comp (ref "T29")
      (value "PMF170XP")
      (footprint "eagle-import:SOT-323_SC-70_NXP")
      (fields (field (name "MANUFACTURER") "Nexperia"))
      (libsource (lib "eagle-import") (part "PMF170XP"))
    )
    (comp (ref "T30")
      (value "DMG1012UW-7")
      (footprint "eagle-import:SOT-323_DIODES_INC")
      (fields (field (name "MANUFACTURER") "Diodes Inc"))
      (libsource (lib "eagle-import") (part "DMG1012UW-7"))
    )
    (comp (ref "T31")
      (value "DMG1012UW-7")
      (footprint "eagle-import:SOT-323_DIODES_INC")
      (fields (field (name "MANUFACTURER") "Diodes Inc"))
      (libsource (lib "eagle-import") (part "DMG1012UW-7"))
    )
    (comp (ref "T32")
      (value "DMG1012UW-7")
      (footprint "eagle-import:SOT-323_DIODES_INC")
      (fields (field (name "MANUFACTURER") "Diodes Inc"))
      (libsource (lib "eagle-import") (part "DMG1012UW-7"))
    )
    (comp (ref "T33")
      (value "DMG1012UW-7")
      (footprint "eagle-import:SOT-323_DIODES_INC")
      (fields (field (name "MANUFACTURER") "Diodes Inc"))
      (libsource (lib "eagle-import") (part "DMG1012UW-7"))
    )
    (comp (ref "T34")
      (value "NX7002AK")
      (footprint "eagle-import:SOT-23_NXP")
      (fields (field (name "MANUFACTURER") "Nexperia"))
      (libsource (lib "eagle-import") (part "NX7002AK"))
    )
    (comp (ref "T35")
      (value "DMG1012UW-7")
      (footprint "eagle-import:SOT-323_DIODES_INC")
      (fields (field (name "MANUFACTURER") "Diodes Inc"))
      (libsource (lib "eagle-import") (part "DMG1012UW-7"))
    )
    (comp (ref "T36")
      (value "NX7002AK")
      (footprint "eagle-import:SOT-23_NXP")
      (fields (field (name "MANUFACTURER") "Nexperia"))
      (libsource (lib "eagle-import") (part "NX7002AK"))
    )
    (comp (ref "T37")
      (value "DMG1012UW-7")
      (footprint "eagle-import:SOT-323_DIODES_INC")
      (fields (field (name "MANUFACTURER") "Diodes Inc"))
      (libsource (lib "eagle-import") (part "DMG1012UW-7"))
    )
    (comp (ref "T38")
      (value "DMG1012UW-7")
      (footprint "eagle-import:SOT-323_DIODES_INC")
      (fields (field (name "MANUFACTURER") "Diodes Inc"))
      (libsource (lib "eagle-import") (part "DMG1012UW-7"))
    )
    (comp (ref "T39")
      (value "NX7002AK")
      (footprint "eagle-import:SOT-23_NXP")
      (fields (field (name "MANUFACTURER") "Nexperia"))
      (libsource (lib "eagle-import") (part "NX7002AK"))
    )
    (comp (ref "T40")
      (value "NX7002AK")
      (footprint "eagle-import:SOT-23_NXP")
      (fields (field (name "MANUFACTURER") "Nexperia"))
      (libsource (lib "eagle-import") (part "NX7002AK"))
    )
    (comp (ref "T41")
      (value "DMG1012UW-7")
      (footprint "eagle-import:SOT-323_DIODES_INC")
      (fields (field (name "MANUFACTURER") "Diodes Inc"))
      (libsource (lib "eagle-import") (part "DMG1012UW-7"))
    )
    (comp (ref "T42")
      (value "DMG1012UW-7")
      (footprint "eagle-import:SOT-323_DIODES_INC")
      (fields (field (name "MANUFACTURER") "Diodes Inc"))
      (libsource (lib "eagle-import") (part "DMG1012UW-7"))
    )
    (comp (ref "T43")
      (value "DMG1012UW-7")
      (footprint "eagle-import:SOT-323_DIODES_INC")
      (fields (field (name "MANUFACTURER") "Diodes Inc"))
      (libsource (lib "eagle-import") (part "DMG1012UW-7"))
    )
    (comp (ref "T44")
      (value "NX7002AK")
      (footprint "eagle-import:SOT-23_NXP")
      (fields (field (name "MANUFACTURER") "Nexperia"))
      (libsource (lib "eagle-import") (part "NX7002AK"))
    )
    (comp (ref "T45")
      (value "NX7002AK")
      (footprint "eagle-import:SOT-23_NXP")
      (fields (field (name "MANUFACTURER") "Nexperia"))
      (libsource (lib "eagle-import") (part "NX7002AK"))
    )
    (comp (ref "T46")
      (value "NX7002AK")
      (footprint "eagle-import:SOT-23_NXP")
      (fields (field (name "MANUFACTURER") "Nexperia"))
      (libsource (lib "eagle-import") (part "NX7002AK"))
    )
    (comp (ref "T47")
      (value "DMG1012UW-7")
      (footprint "eagle-import:SOT-323_DIODES_INC")
      (fields (field (name "MANUFACTURER") "Diodes Inc"))
      (libsource (lib "eagle-import") (part "DMG1012UW-7"))
    )
    (comp (ref "T48")
      (value "DMG1012UW-7")
      (footprint "eagle-import:SOT-323_DIODES_INC")
      (fields (field (name "MANUFACTURER") "Diodes Inc"))
      (libsource (lib "eagle-import") (part "DMG1012UW-7"))
    )
    (comp (ref "T49")
      (value "PMF170XP")
      (footprint "eagle-import:SOT-323_SC-70_NXP")
      (fields (field (name "MANUFACTURER") "Nexperia"))
      (libsource (lib "eagle-import") (part "PMF170XP"))
    )
    (comp (ref "T50")
      (value "DMG1012UW-7")
      (footprint "eagle-import:SOT-323_DIODES_INC")
      (fields (field (name "MANUFACTURER") "Diodes Inc"))
      (libsource (lib "eagle-import") (part "DMG1012UW-7"))
    )
    (comp (ref "T51")
      (value "PMV30ENEA")
      (footprint "eagle-import:SOT-23_NXP")
      (fields (field (name "MANUFACTURER") "Nexperia"))
      (libsource (lib "eagle-import") (part "PMV30ENEA"))
    )
    (comp (ref "T52")
      (value "PMV30ENEA")
      (footprint "eagle-import:SOT-23_NXP")
      (fields (field (name "MANUFACTURER") "Nexperia"))
      (libsource (lib "eagle-import") (part "PMV30ENEA"))
    )
    (comp (ref "T53")
      (value "PMV30ENEA")
      (footprint "eagle-import:SOT-23_NXP")
      (fields (field (name "MANUFACTURER") "Nexperia"))
      (libsource (lib "eagle-import") (part "PMV30ENEA"))
    )
    (comp (ref "T54")
      (value "PMV30ENEA")
      (footprint "eagle-import:SOT-23_NXP")
      (fields (field (name "MANUFACTURER") "Nexperia"))
      (libsource (lib "eagle-import") (part "PMV30ENEA"))
    )
    (comp (ref "T55")
      (value "DMG1012UW-7")
      (footprint "eagle-import:SOT-323_DIODES_INC")
      (fields (field (name "MANUFACTURER") "Diodes Inc"))
      (libsource (lib "eagle-import") (part "DMG1012UW-7"))
    )
    (comp (ref "T56")
      (value "NX7002AK")
      (footprint "eagle-import:SOT-23_NXP")
      (fields (field (name "MANUFACTURER") "Nexperia"))
      (libsource (lib "eagle-import") (part "NX7002AK"))
    )
    (comp (ref "T57")
      (value "NX7002AK")
      (footprint "eagle-import:SOT-23_NXP")
      (fields (field (name "MANUFACTURER") "Nexperia"))
      (libsource (lib "eagle-import") (part "NX7002AK"))
    )
    (comp (ref "T58")
      (value "n.m.")
      (footprint "eagle-import:SOT-323_DIODES_INC")
      (fields (field (name "MANUFACTURER") "Diodes Inc"))
      (libsource (lib "eagle-import") (part "DMG1012UW-7"))
    )
    (comp (ref "T59")
      (value "DMG1012UW-7")
      (footprint "eagle-import:SOT-323_DIODES_INC")
      (fields (field (name "MANUFACTURER") "Diodes Inc"))
      (libsource (lib "eagle-import") (part "DMG1012UW-7"))
    )
    (comp (ref "T60")
      (value "DMG1012UW-7")
      (footprint "eagle-import:SOT-323_DIODES_INC")
      (fields (field (name "MANUFACTURER") "Diodes Inc"))
      (libsource (lib "eagle-import") (part "DMG1012UW-7"))
    )
    (comp (ref "T61")
      (value "CSD18504Q5A")
      (footprint "eagle-import:Q5A_TI")
      (fields (field (name "MANUFACTURER") "TI"))
      (libsource (lib "eagle-import") (part "CSD18504Q5A"))
    )
    (comp (ref "T62")
      (value "CSD18512Q5B")
      (footprint "eagle-import:Q5B_TI")
      (fields (field (name "MANUFACTURER") "TI"))
      (libsource (lib "eagle-import") (part "CSD18512Q5B"))
    )
    (comp (ref "T63")
      (value "NX7002AK")
      (footprint "eagle-import:SOT-23_NXP")
      (fields (field (name "MANUFACTURER") "Nexperia"))
      (libsource (lib "eagle-import") (part "NX7002AK"))
    )
    (comp (ref "T64")
      (value "NX7002AK")
      (footprint "eagle-import:SOT-23_NXP")
      (fields (field (name "MANUFACTURER") "Nexperia"))
      (libsource (lib "eagle-import") (part "NX7002AK"))
    )
    (comp (ref "T65")
      (value "NX7002AK")
      (footprint "eagle-import:SOT-23_NXP")
      (fields (field (name "MANUFACTURER") "Nexperia"))
      (libsource (lib "eagle-import") (part "NX7002AK"))
    )
    (comp (ref "T66")
      (value "NX7002AK")
      (footprint "eagle-import:SOT-23_NXP")
      (fields (field (name "MANUFACTURER") "Nexperia"))
      (libsource (lib "eagle-import") (part "NX7002AK"))
    )
    (comp (ref "T67")
      (value "DMP2006UFG")
      (footprint "eagle-import:POWERDI3333-8_DIODES_INC")
      (fields (field (name "MANUFACTURER") "Diodes Inc"))
      (libsource (lib "eagle-import") (part "DMP2006UFG"))
    )
    (comp (ref "T68")
      (value "DMG1012UW-7")
      (footprint "eagle-import:SOT-323_DIODES_INC")
      (fields (field (name "MANUFACTURER") "Diodes Inc"))
      (libsource (lib "eagle-import") (part "DMG1012UW-7"))
    )
    (comp (ref "TP1")
      (value "TESTPOINT_VIA_ROUND_0.8MM")
      (footprint "eagle-import:TESTVIA_ROUND_0.8MM")
      (libsource (lib "eagle-import") (part "TESTPOINT_VIA_ROUND_0.8MM"))
    )
    (comp (ref "TP2")
      (value "TESTPOINT_VIA_ROUND_0.8MM")
      (footprint "eagle-import:TESTVIA_ROUND_0.8MM")
      (libsource (lib "eagle-import") (part "TESTPOINT_VIA_ROUND_0.8MM"))
    )
    (comp (ref "TP3")
      (value "TESTPOINT_VIA_ROUND_0.8MM")
      (footprint "eagle-import:TESTVIA_ROUND_0.8MM")
      (libsource (lib "eagle-import") (part "TESTPOINT_VIA_ROUND_0.8MM"))
    )
    (comp (ref "TP4")
      (value "TESTPOINT_VIA_ROUND_0.8MM")
      (footprint "eagle-import:TESTVIA_ROUND_0.8MM")
      (libsource (lib "eagle-import") (part "TESTPOINT_VIA_ROUND_0.8MM"))
    )
    (comp (ref "TP5")
      (value "TESTPOINT_VIA_ROUND_0.8MM")
      (footprint "eagle-import:TESTVIA_ROUND_0.8MM")
      (libsource (lib "eagle-import") (part "TESTPOINT_VIA_ROUND_0.8MM"))
    )
    (comp (ref "TP6")
      (value "TESTPOINT_VIA_ROUND_0.8MM")
      (footprint "eagle-import:TESTVIA_ROUND_0.8MM")
      (libsource (lib "eagle-import") (part "TESTPOINT_VIA_ROUND_0.8MM"))
    )
    (comp (ref "TP7")
      (value "TESTPOINT_VIA_ROUND_0.8MM")
      (footprint "eagle-import:TESTVIA_ROUND_0.8MM")
      (libsource (lib "eagle-import") (part "TESTPOINT_VIA_ROUND_0.8MM"))
    )
    (comp (ref "TP8")
      (value "TESTPOINT_VIA_ROUND_0.8MM")
      (footprint "eagle-import:TESTVIA_ROUND_0.8MM")
      (libsource (lib "eagle-import") (part "TESTPOINT_VIA_ROUND_0.8MM"))
    )
    (comp (ref "TP9")
      (value "TESTPOINT_VIA_ROUND_0.8MM")
      (footprint "eagle-import:TESTVIA_ROUND_0.8MM")
      (libsource (lib "eagle-import") (part "TESTPOINT_VIA_ROUND_0.8MM"))
    )
    (comp (ref "TP11")
      (value "TESTPOINT_VIA_ROUND_0.8MM")
      (footprint "eagle-import:TESTVIA_ROUND_0.8MM")
      (libsource (lib "eagle-import") (part "TESTPOINT_VIA_ROUND_0.8MM"))
    )
    (comp (ref "TP12")
      (value "TESTPOINT_VIA_ROUND_0.8MM")
      (footprint "eagle-import:TESTVIA_ROUND_0.8MM")
      (libsource (lib "eagle-import") (part "TESTPOINT_VIA_ROUND_0.8MM"))
    )
    (comp (ref "TP13")
      (value "TESTPOINT_VIA_ROUND_0.8MM")
      (footprint "eagle-import:TESTVIA_ROUND_0.8MM")
      (libsource (lib "eagle-import") (part "TESTPOINT_VIA_ROUND_0.8MM"))
    )
    (comp (ref "TP14")
      (value "TESTPOINT_VIA_ROUND_0.8MM")
      (footprint "eagle-import:TESTVIA_ROUND_0.8MM")
      (libsource (lib "eagle-import") (part "TESTPOINT_VIA_ROUND_0.8MM"))
    )
    (comp (ref "TP15")
      (value "TESTPOINT_VIA_ROUND_0.8MM")
      (footprint "eagle-import:TESTVIA_ROUND_0.8MM")
      (libsource (lib "eagle-import") (part "TESTPOINT_VIA_ROUND_0.8MM"))
    )
    (comp (ref "TP17")
      (value "TESTPOINT_VIA_ROUND_0.8MM")
      (footprint "eagle-import:TESTVIA_ROUND_0.8MM")
      (libsource (lib "eagle-import") (part "TESTPOINT_VIA_ROUND_0.8MM"))
    )
    (comp (ref "TP18")
      (value "TESTPOINT_VIA_ROUND_0.8MM")
      (footprint "eagle-import:TESTVIA_ROUND_0.8MM")
      (libsource (lib "eagle-import") (part "TESTPOINT_VIA_ROUND_0.8MM"))
    )
    (comp (ref "TP19")
      (value "TESTPOINT_VIA_ROUND_0.8MM")
      (footprint "eagle-import:TESTVIA_ROUND_0.8MM")
      (libsource (lib "eagle-import") (part "TESTPOINT_VIA_ROUND_0.8MM"))
    )
    (comp (ref "TP22")
      (value "TESTPOINT_VIA_ROUND_0.8MM")
      (footprint "eagle-import:TESTVIA_ROUND_0.8MM")
      (libsource (lib "eagle-import") (part "TESTPOINT_VIA_ROUND_0.8MM"))
    )
    (comp (ref "TP23")
      (value "TESTPOINT_VIA_ROUND_0.8MM")
      (footprint "eagle-import:TESTVIA_ROUND_0.8MM")
      (libsource (lib "eagle-import") (part "TESTPOINT_VIA_ROUND_0.8MM"))
    )
    (comp (ref "TP24")
      (value "TESTPOINT_VIA_ROUND_0.8MM")
      (footprint "eagle-import:TESTVIA_ROUND_0.8MM")
      (libsource (lib "eagle-import") (part "TESTPOINT_VIA_ROUND_0.8MM"))
    )
    (comp (ref "TP25")
      (value "TESTPOINT_VIA_ROUND_0.8MM")
      (footprint "eagle-import:TESTVIA_ROUND_0.8MM")
      (libsource (lib "eagle-import") (part "TESTPOINT_VIA_ROUND_0.8MM"))
    )
    (comp (ref "TP27")
      (value "TESTPOINT_VIA_ROUND_0.8MM")
      (footprint "eagle-import:TESTVIA_ROUND_0.8MM")
      (libsource (lib "eagle-import") (part "TESTPOINT_VIA_ROUND_0.8MM"))
    )
    (comp (ref "TP38")
      (value "TESTPOINT_VIA_ROUND_0.8MM")
      (footprint "eagle-import:TESTVIA_ROUND_0.8MM")
      (libsource (lib "eagle-import") (part "TESTPOINT_VIA_ROUND_0.8MM"))
    )
    (comp (ref "TP39")
      (value "TESTPOINT_VIA_ROUND_0.8MM")
      (footprint "eagle-import:TESTVIA_ROUND_0.8MM")
      (libsource (lib "eagle-import") (part "TESTPOINT_VIA_ROUND_0.8MM"))
    )
    (comp (ref "TP42")
      (value "TESTPOINT_VIA_ROUND_0.8MM")
      (footprint "eagle-import:TESTVIA_ROUND_0.8MM")
      (libsource (lib "eagle-import") (part "TESTPOINT_VIA_ROUND_0.8MM"))
    )
    (comp (ref "TP43")
      (value "TESTPOINT_VIA_ROUND_0.8MM")
      (footprint "eagle-import:TESTVIA_ROUND_0.8MM")
      (libsource (lib "eagle-import") (part "TESTPOINT_VIA_ROUND_0.8MM"))
    )
    (comp (ref "TP44")
      (value "TESTPOINT_VIA_ROUND_0.8MM")
      (footprint "eagle-import:TESTVIA_ROUND_0.8MM")
      (libsource (lib "eagle-import") (part "TESTPOINT_VIA_ROUND_0.8MM"))
    )
    (comp (ref "TP45")
      (value "TESTPOINT_VIA_ROUND_0.8MM")
      (footprint "eagle-import:TESTVIA_ROUND_0.8MM")
      (libsource (lib "eagle-import") (part "TESTPOINT_VIA_ROUND_0.8MM"))
    )
    (comp (ref "TP50")
      (value "TESTPOINT_VIA_ROUND_0.8MM")
      (footprint "eagle-import:TESTVIA_ROUND_0.8MM")
      (libsource (lib "eagle-import") (part "TESTPOINT_VIA_ROUND_0.8MM"))
    )
    (comp (ref "TP51")
      (value "TESTPOINT_VIA_ROUND_0.8MM")
      (footprint "eagle-import:TESTVIA_ROUND_0.8MM")
      (libsource (lib "eagle-import") (part "TESTPOINT_VIA_ROUND_0.8MM"))
    )
    (comp (ref "TP52")
      (value "TESTPOINT_VIA_ROUND_0.8MM")
      (footprint "eagle-import:TESTVIA_ROUND_0.8MM")
      (libsource (lib "eagle-import") (part "TESTPOINT_VIA_ROUND_0.8MM"))
    )
    (comp (ref "TP53")
      (value "TESTPOINT_VIA_ROUND_0.8MM")
      (footprint "eagle-import:TESTVIA_ROUND_0.8MM")
      (libsource (lib "eagle-import") (part "TESTPOINT_VIA_ROUND_0.8MM"))
    )
    (comp (ref "TP54")
      (value "TESTPOINT_VIA_ROUND_0.8MM")
      (footprint "eagle-import:TESTVIA_ROUND_0.8MM")
      (libsource (lib "eagle-import") (part "TESTPOINT_VIA_ROUND_0.8MM"))
    )
    (comp (ref "TP55")
      (value "TESTPOINT_VIA_ROUND_0.8MM")
      (footprint "eagle-import:TESTVIA_ROUND_0.8MM")
      (libsource (lib "eagle-import") (part "TESTPOINT_VIA_ROUND_0.8MM"))
    )
    (comp (ref "TP56")
      (value "TESTPOINT_VIA_ROUND_0.8MM")
      (footprint "eagle-import:TESTVIA_ROUND_0.8MM")
      (libsource (lib "eagle-import") (part "TESTPOINT_VIA_ROUND_0.8MM"))
    )
    (comp (ref "TP57")
      (value "TESTPOINT_VIA_ROUND_0.8MM")
      (footprint "eagle-import:TESTVIA_ROUND_0.8MM")
      (libsource (lib "eagle-import") (part "TESTPOINT_VIA_ROUND_0.8MM"))
    )
    (comp (ref "TP58")
      (value "TESTPOINT_VIA_ROUND_0.8MM")
      (footprint "eagle-import:TESTVIA_ROUND_0.8MM")
      (libsource (lib "eagle-import") (part "TESTPOINT_VIA_ROUND_0.8MM"))
    )
    (comp (ref "TP59")
      (value "TESTPOINT_VIA_ROUND_0.8MM")
      (footprint "eagle-import:TESTVIA_ROUND_0.8MM")
      (libsource (lib "eagle-import") (part "TESTPOINT_VIA_ROUND_0.8MM"))
    )
    (comp (ref "TP60")
      (value "TESTPOINT_VIA_ROUND_0.8MM")
      (footprint "eagle-import:TESTVIA_ROUND_0.8MM")
      (libsource (lib "eagle-import") (part "TESTPOINT_VIA_ROUND_0.8MM"))
    )
    (comp (ref "TP61")
      (value "TESTPOINT_VIA_ROUND_0.8MM")
      (footprint "eagle-import:TESTVIA_ROUND_0.8MM")
      (libsource (lib "eagle-import") (part "TESTPOINT_VIA_ROUND_0.8MM"))
    )
    (comp (ref "TP62")
      (value "TESTPOINT_VIA_ROUND_0.8MM")
      (footprint "eagle-import:TESTVIA_ROUND_0.8MM")
      (libsource (lib "eagle-import") (part "TESTPOINT_VIA_ROUND_0.8MM"))
    )
    (comp (ref "TP63")
      (value "TESTPOINT_VIA_ROUND_0.8MM")
      (footprint "eagle-import:TESTVIA_ROUND_0.8MM")
      (libsource (lib "eagle-import") (part "TESTPOINT_VIA_ROUND_0.8MM"))
    )
    (comp (ref "TP64")
      (value "TESTPOINT_VIA_ROUND_0.8MM")
      (footprint "eagle-import:TESTVIA_ROUND_0.8MM")
      (libsource (lib "eagle-import") (part "TESTPOINT_VIA_ROUND_0.8MM"))
    )
    (comp (ref "TP67")
      (value "TESTPOINT_VIA_ROUND_0.8MM")
      (footprint "eagle-import:TESTVIA_ROUND_0.8MM")
      (libsource (lib "eagle-import") (part "TESTPOINT_VIA_ROUND_0.8MM"))
    )
    (comp (ref "TP68")
      (value "TESTPOINT_VIA_ROUND_0.8MM")
      (footprint "eagle-import:TESTVIA_ROUND_0.8MM")
      (libsource (lib "eagle-import") (part "TESTPOINT_VIA_ROUND_0.8MM"))
    )
    (comp (ref "TP69")
      (value "TESTPOINT_VIA_ROUND_0.8MM")
      (footprint "eagle-import:TESTVIA_ROUND_0.8MM")
      (libsource (lib "eagle-import") (part "TESTPOINT_VIA_ROUND_0.8MM"))
    )
    (comp (ref "TP70")
      (value "TESTPOINT_VIA_ROUND_0.8MM")
      (footprint "eagle-import:TESTVIA_ROUND_0.8MM")
      (libsource (lib "eagle-import") (part "TESTPOINT_VIA_ROUND_0.8MM"))
    )
    (comp (ref "TP71")
      (value "TESTPOINT_VIA_ROUND_0.8MM")
      (footprint "eagle-import:TESTVIA_ROUND_0.8MM")
      (libsource (lib "eagle-import") (part "TESTPOINT_VIA_ROUND_0.8MM"))
    )
    (comp (ref "TP72")
      (value "TESTPOINT_VIA_ROUND_0.8MM")
      (footprint "eagle-import:TESTVIA_ROUND_0.8MM")
      (libsource (lib "eagle-import") (part "TESTPOINT_VIA_ROUND_0.8MM"))
    )
    (comp (ref "TP74")
      (value "TESTPOINT_VIA_ROUND_0.8MM")
      (footprint "eagle-import:TESTVIA_ROUND_0.8MM")
      (libsource (lib "eagle-import") (part "TESTPOINT_VIA_ROUND_0.8MM"))
    )
    (comp (ref "TP75")
      (value "TESTPOINT_VIA_ROUND_0.8MM")
      (footprint "eagle-import:TESTVIA_ROUND_0.8MM")
      (libsource (lib "eagle-import") (part "TESTPOINT_VIA_ROUND_0.8MM"))
    )
    (comp (ref "TP76")
      (value "TESTPOINT_VIA_ROUND_0.8MM")
      (footprint "eagle-import:TESTVIA_ROUND_0.8MM")
      (libsource (lib "eagle-import") (part "TESTPOINT_VIA_ROUND_0.8MM"))
    )
    (comp (ref "TP77")
      (value "TESTPOINT_VIA_ROUND_0.8MM")
      (footprint "eagle-import:TESTVIA_ROUND_0.8MM")
      (libsource (lib "eagle-import") (part "TESTPOINT_VIA_ROUND_0.8MM"))
    )
    (comp (ref "TP78")
      (value "TESTPOINT_VIA_ROUND_0.8MM")
      (footprint "eagle-import:TESTVIA_ROUND_0.8MM")
      (libsource (lib "eagle-import") (part "TESTPOINT_VIA_ROUND_0.8MM"))
    )
    (comp (ref "TP79")
      (value "TESTPOINT_VIA_ROUND_0.8MM")
      (footprint "eagle-import:TESTVIA_ROUND_0.8MM")
      (libsource (lib "eagle-import") (part "TESTPOINT_VIA_ROUND_0.8MM"))
    )
    (comp (ref "TP80")
      (value "TESTPOINT_VIA_ROUND_0.8MM")
      (footprint "eagle-import:TESTVIA_ROUND_0.8MM")
      (libsource (lib "eagle-import") (part "TESTPOINT_VIA_ROUND_0.8MM"))
    )
    (comp (ref "TP81")
      (value "TESTPOINT_VIA_ROUND_0.8MM")
      (footprint "eagle-import:TESTVIA_ROUND_0.8MM")
      (libsource (lib "eagle-import") (part "TESTPOINT_VIA_ROUND_0.8MM"))
    )
    (comp (ref "TP82")
      (value "TESTPOINT_VIA_ROUND_0.8MM")
      (footprint "eagle-import:TESTVIA_ROUND_0.8MM")
      (libsource (lib "eagle-import") (part "TESTPOINT_VIA_ROUND_0.8MM"))
    )
    (comp (ref "TP83")
      (value "TESTPOINT_VIA_ROUND_0.8MM")
      (footprint "eagle-import:TESTVIA_ROUND_0.8MM")
      (libsource (lib "eagle-import") (part "TESTPOINT_VIA_ROUND_0.8MM"))
    )
    (comp (ref "X1")
      (value "470531000")
      (footprint "eagle-import:470531000_MOLEX")
      (fields (field (name "MANUFACTURER") "Molex") (field (name "VOLTAGE") "500 V(AC)"))
      (libsource (lib "eagle-import") (part "470531000"))
    )
    (comp (ref "X2")
      (value "645005114822")
      (footprint "eagle-import:645005114822_WUERTH")
      (fields (field (name "MANUFACTURER") "Wuerth") (field (name "VOLTAGE") "250.0 V(AC)"))
      (libsource (lib "eagle-import") (part "645005114822"))
    )
    (comp (ref "X3")
      (value "687106149022")
      (footprint "eagle-import:687106149022_WUERTH")
      (fields (field (name "MANUFACTURER") "Wuerth") (field (name "VOLTAGE") "50 V (AC)"))
      (libsource (lib "eagle-import") (part "687106149022"))
    )
    (comp (ref "X4")
      (value "61303021121")
      (footprint "eagle-import:61303021121_WUERTH")
      (fields (field (name "MANUFACTURER") "Wuerth") (field (name "VOLTAGE") "250 VAC"))
      (libsource (lib "eagle-import") (part "61303021121"))
    )
    (comp (ref "X6")
      (value "TC2030-CTX")
      (footprint "eagle-import:TC2030-IDC-FP_TAGCONNECT")
      (libsource (lib "eagle-import") (part "TC2030-CTX"))
    )
    (comp (ref "X7")
      (value "685119134923")
      (footprint "eagle-import:685119134923_WUERTH")
      (fields (field (name "MANUFACTURER") "Wuerth"))
      (libsource (lib "eagle-import") (part "685119134923"))
    )
    (comp (ref "X8")
      (value "61400826021")
      (footprint "eagle-import:61400826021_WUERTH")
      (fields (field (name "MANUFACTURER") "Wuerth") (field (name "VOLTAGE") "30.0 V"))
      (libsource (lib "eagle-import") (part "61400826021"))
    )
    (comp (ref "X9")
      (value "n.m.")
      (footprint "eagle-import:62000311622_WUERTH")
      (fields (field (name "MANUFACTURER") "Wuerth") (field (name "VOLTAGE") "125 V(AC)"))
      (libsource (lib "eagle-import") (part "62000311622"))
    )
    (comp (ref "X10")
      (value "470531000")
      (footprint "eagle-import:470531000_MOLEX")
      (fields (field (name "MANUFACTURER") "Molex") (field (name "VOLTAGE") "500 V(AC)"))
      (libsource (lib "eagle-import") (part "470531000"))
    )
    (comp (ref "X11")
      (value "687106149022")
      (footprint "eagle-import:687106149022_WUERTH")
      (fields (field (name "MANUFACTURER") "Wuerth") (field (name "VOLTAGE") "50 V (AC)"))
      (libsource (lib "eagle-import") (part "687106149022"))
    )
    (comp (ref "X12")
      (value "61300411821")
      (footprint "eagle-import:61300411821_WUERTH")
      (fields (field (name "MANUFACTURER") "Wuerth") (field (name "VOLTAGE") "250 V(AC)"))
      (libsource (lib "eagle-import") (part "61300411821"))
    )
    (comp (ref "X13")
      (value "G639F100151102HR")
      (footprint "eagle-import:G639F100151102HR_AMPHENOL")
      (fields (field (name "MANUFACTURER") "Amphenol") (field (name "VOLTAGE") "???"))
      (libsource (lib "eagle-import") (part "G639F100151102HR"))
    )
    (comp (ref "X14")
      (value "636101111001")
      (footprint "eagle-import:636101111001_WE")
      (fields (field (name "MANUFACTURER") "Wuerth"))
      (libsource (lib "eagle-import") (part "636101111001"))
    )
    (comp (ref "X15")
      (value "629105150921")
      (footprint "eagle-import:629105150921_WUERTH")
      (fields (field (name "MANUFACTURER") "Wuerth"))
      (libsource (lib "eagle-import") (part "629105150921"))
    )
    (comp (ref "X16")
      (value "61300211121")
      (footprint "eagle-import:61300211121_WUERTH")
      (fields (field (name "MANUFACTURER") "Wuerth") (field (name "VOLTAGE") "500 V(AC)"))
      (libsource (lib "eagle-import") (part "61300211121"))
    )
    (comp (ref "X17")
      (value "n.m.")
      (footprint "eagle-import:61300211121_WUERTH")
      (fields (field (name "MANUFACTURER") "Wuerth") (field (name "VOLTAGE") "500 V(AC)"))
      (libsource (lib "eagle-import") (part "61300211121"))
    )
    (comp (ref "X18")
      (value "2199230-4")
      (footprint "eagle-import:2199230-4_2230_TE")
      (fields (field (name "MANUFACTURER") "TE Connectivity"))
      (libsource (lib "eagle-import") (part "2199230-4"))
    )
    (comp (ref "X19")
      (value "665302124022")
      (footprint "eagle-import:665302124022_WUERTH")
      (fields (field (name "MANUFACTURER") "Wuerth") (field (name "VOLTAGE") "50.0 VAC"))
      (libsource (lib "eagle-import") (part "665302124022"))
    )
    (comp (ref "X20")
      (value "665303124022")
      (footprint "eagle-import:665303124022_WUERTH")
      (fields (field (name "MANUFACTURER") "Wuerth") (field (name "VOLTAGE") "50.0 VAC"))
      (libsource (lib "eagle-import") (part "665303124022"))
    )
    (comp (ref "X21")
      (value "TC2030-CTX")
      (footprint "eagle-import:TC2030-IDC-FP_TAGCONNECT")
      (libsource (lib "eagle-import") (part "TC2030-CTX"))
    )
    (comp (ref "X22")
      (value "665306124022")
      (footprint "eagle-import:665306124022_WUERTH")
      (fields (field (name "MANUFACTURER") "Wuerth") (field (name "VOLTAGE") "50.0 VAC"))
      (libsource (lib "eagle-import") (part "665306124022"))
    )
    (comp (ref "X23")
      (value "62000211622")
      (footprint "eagle-import:62000211622_WUERTH")
      (fields (field (name "MANUFACTURER") "Wuerth") (field (name "VOLTAGE") "125 V(AC)"))
      (libsource (lib "eagle-import") (part "62000211622"))
    )
    (comp (ref "X24")
      (value "62000211622")
      (footprint "eagle-import:62000211622_WUERTH")
      (fields (field (name "MANUFACTURER") "Wuerth") (field (name "VOLTAGE") "125 V(AC)"))
      (libsource (lib "eagle-import") (part "62000211622"))
    )
    (comp (ref "X25")
      (value "687122149022")
      (footprint "eagle-import:687122149022_WUERTH")
      (fields (field (name "MANUFACTURER") "Wuerth") (field (name "VOLTAGE") "50 V (AC)"))
      (libsource (lib "eagle-import") (part "687122149022"))
    )
    (comp (ref "X26")
      (value "693043020611")
      (footprint "eagle-import:693043020611_WUERTH")
      (fields (field (name "MANUFACTURER") "Wuerth"))
      (libsource (lib "eagle-import") (part "693043020611"))
    )
    (comp (ref "X27")
      (value "665302124022")
      (footprint "eagle-import:665302124022_WUERTH")
      (fields (field (name "MANUFACTURER") "Wuerth") (field (name "VOLTAGE") "50.0 VAC"))
      (libsource (lib "eagle-import") (part "665302124022"))
    )
    (comp (ref "X32")
      (value "2199230-3")
      (footprint "eagle-import:2199230-3_3042_TE")
      (fields (field (name "MANUFACTURER") "TE Connectivity"))
      (libsource (lib "eagle-import") (part "2199230-3"))
    )
    (comp (ref "X33")
      (value "1-2199230-5")
      (footprint "eagle-import:1-2199230-5_2280_TE")
      (fields (field (name "MANUFACTURER") "TE Connectivity"))
      (libsource (lib "eagle-import") (part "1-2199230-5"))
    )
  )
  (nets
    (net (code "1") (name "+1V8") (class "Default")
      (node (ref "C220") (pin "1") (pinfunction "1_1") (pintype "passive"))
      (node (ref "C235") (pin "1") (pinfunction "1_1") (pintype "passive"))
      (node (ref "C283") (pin "1") (pinfunction "1_1") (pintype "passive"))
      (node (ref "L34") (pin "NO_DOT") (pinfunction "NODOT_NO_DOT") (pintype "passive"))
      (node (ref "R1") (pin "2") (pinfunction "2_2") (pintype "passive"))
      (node (ref "R121") (pin "2") (pinfunction "2_2") (pintype "passive"))
      (node (ref "R122") (pin "2") (pinfunction "2_2") (pintype "passive"))
      (node (ref "R180") (pin "2") (pinfunction "2_2") (pintype "passive"))
      (node (ref "R200") (pin "1") (pinfunction "1_1") (pintype "passive"))
      (node (ref "R204") (pin "2") (pinfunction "2_2") (pintype "passive"))
      (node (ref "R205") (pin "2") (pinfunction "2_2") (pintype "passive"))
      (node (ref "R211") (pin "2") (pinfunction "2_2") (pintype "passive"))
      (node (ref "R229") (pin "2") (pinfunction "2_2") (pintype "passive"))
      (node (ref "R265") (pin "2") (pinfunction "2_2") (pintype "passive"))
      (node (ref "R282") (pin "2") (pinfunction "2_2") (pintype "passive"))
      (node (ref "R286") (pin "2") (pinfunction "2_2") (pintype "passive"))
      (node (ref "R287") (pin "2") (pinfunction "2_2") (pintype "passive"))
      (node (ref "R294") (pin "2") (pinfunction "2_2") (pintype "passive"))
      (node (ref "R3") (pin "2") (pinfunction "2_2") (pintype "passive"))
      (node (ref "R300") (pin "2") (pinfunction "2_2") (pintype "passive"))
      (node (ref "R305") (pin "2") (pinfunction "2_2") (pintype "passive"))
      (node (ref "R334") (pin "1") (pinfunction "1_1") (pintype "passive"))
      (node (ref "R335") (pin "2") (pinfunction "2_2") (pintype "passive"))
      (node (ref "R40") (pin "2") (pinfunction "2_2") (pintype "passive"))
      (node (ref "R416") (pin "1") (pinfunction "1_1") (pintype "passive"))
      (node (ref "R44") (pin "2") (pinfunction "2_2") (pintype "passive"))
      (node (ref "R486") (pin "2") (pinfunction "2_2") (pintype "passive"))
      (node (ref "R487") (pin "2") (pinfunction "2_2") (pintype "passive"))
      (node (ref "R489") (pin "1") (pinfunction "1_1") (pintype "passive"))
      (node (ref "R490") (pin "1") (pinfunction "1_1") (pintype "passive"))
      (node (ref "R552") (pin "2") (pinfunction "2_2") (pintype "passive"))
      (node (ref "R59") (pin "2") (pinfunction "2_2") (pintype "passive"))
      (node (ref "T11") (pin "1") (pinfunction "G_1") (pintype "passive"))
      (node (ref "T13") (pin "1") (pinfunction "G_1") (pintype "passive"))
      (node (ref "T14") (pin "1") (pinfunction "G_1") (pintype "passive"))
      (node (ref "T2") (pin "1") (pinfunction "G_1") (pintype "passive"))
      (node (ref "T32") (pin "1") (pinfunction "G_1") (pintype "passive"))
      (node (ref "T48") (pin "1") (pinfunction "G_1") (pintype "passive"))
      (node (ref "T7") (pin "1") (pinfunction "G_1") (pintype "passive"))
      (node (ref "TP19") (pin "P$1") (pinfunction "TP_P$1") (pintype "input"))
      (node (ref "X13") (pin "54") (pinfunction "54_54") (pintype "passive"))
      (node (ref "X4") (pin "6") (pinfunction "6_6") (pintype "passive"))
    )
    (net (code "2") (name "+3V3") (class "Default")
      (node (ref "C1") (pin "1") (pinfunction "1_1") (pintype "passive"))
      (node (ref "C115") (pin "+") (pinfunction "+_+") (pintype "passive"))
      (node (ref "C18") (pin "1") (pinfunction "1_1") (pintype "passive"))
      (node (ref "C223") (pin "1") (pinfunction "1_1") (pintype "passive"))
      (node (ref "C24") (pin "1") (pinfunction "1_1") (pintype "passive"))
      (node (ref "C272") (pin "1") (pinfunction "1_1") (pintype "passive"))
      (node (ref "C274") (pin "1") (pinfunction "1_1") (pintype "passive"))
      (node (ref "C66") (pin "1") (pinfunction "1_1") (pintype "passive"))
      (node (ref "D5") (pin "A") (pinfunction "A_A") (pintype "passive"))
      (node (ref "IC16") (pin "5") (pinfunction "VBUS_5") (pintype "input"))
      (node (ref "IC58") (pin "1") (pinfunction "I/O1_1") (pintype "passive"))
      (node (ref "IC58") (pin "5") (pinfunction "VBUS_5") (pintype "input"))
      (node (ref "IC8") (pin "5") (pinfunction "VBUS_5") (pintype "input"))
      (node (ref "L35") (pin "NO_DOT") (pinfunction "NODOT_NO_DOT") (pintype "passive"))
      (node (ref "R10") (pin "2") (pinfunction "2_2") (pintype "passive"))
      (node (ref "R135") (pin "1") (pinfunction "1_1") (pintype "passive"))
      (node (ref "R155") (pin "2") (pinfunction "2_2") (pintype "passive"))
      (node (ref "R161") (pin "1") (pinfunction "1_1") (pintype "passive"))
      (node (ref "R164") (pin "1") (pinfunction "1_1") (pintype "passive"))
      (node (ref "R165") (pin "2") (pinfunction "2_2") (pintype "passive"))
      (node (ref "R181") (pin "2") (pinfunction "2_2") (pintype "passive"))
      (node (ref "R184") (pin "2") (pinfunction "2_2") (pintype "passive"))
      (node (ref "R188") (pin "2") (pinfunction "2_2") (pintype "passive"))
      (node (ref "R189") (pin "2") (pinfunction "2_2") (pintype "passive"))
      (node (ref "R208") (pin "2") (pinfunction "2_2") (pintype "passive"))
      (node (ref "R222") (pin "2") (pinfunction "2_2") (pintype "passive"))
      (node (ref "R223") (pin "2") (pinfunction "2_2") (pintype "passive"))
      (node (ref "R224") (pin "2") (pinfunction "2_2") (pintype "passive"))
      (node (ref "R225") (pin "2") (pinfunction "2_2") (pintype "passive"))
      (node (ref "R250") (pin "2") (pinfunction "2_2") (pintype "passive"))
      (node (ref "R253") (pin "2") (pinfunction "2_2") (pintype "passive"))
      (node (ref "R278") (pin "2") (pinfunction "2_2") (pintype "passive"))
      (node (ref "R315") (pin "2") (pinfunction "2_2") (pintype "passive"))
      (node (ref "R374") (pin "2") (pinfunction "2_2") (pintype "passive"))
      (node (ref "R4") (pin "2") (pinfunction "2_2") (pintype "passive"))
      (node (ref "R440") (pin "2") (pinfunction "2_2") (pintype "passive"))
      (node (ref "R447") (pin "2") (pinfunction "2_2") (pintype "passive"))
      (node (ref "R459") (pin "1") (pinfunction "1_1") (pintype "passive"))
      (node (ref "R460") (pin "1") (pinfunction "1_1") (pintype "passive"))
      (node (ref "R463") (pin "1") (pinfunction "1_1") (pintype "passive"))
      (node (ref "R465") (pin "1") (pinfunction "1_1") (pintype "passive"))
      (node (ref "R468") (pin "2") (pinfunction "2_2") (pintype "passive"))
      (node (ref "R481") (pin "1") (pinfunction "1_1") (pintype "passive"))
      (node (ref "R485") (pin "1") (pinfunction "1_1") (pintype "passive"))
      (node (ref "R549") (pin "2") (pinfunction "2_2") (pintype "passive"))
      (node (ref "R551") (pin "2") (pinfunction "2_2") (pintype "passive"))
      (node (ref "R559") (pin "1") (pinfunction "1_1") (pintype "passive"))
      (node (ref "R565") (pin "1") (pinfunction "1_1") (pintype "passive"))
      (node (ref "R58") (pin "2") (pinfunction "2_2") (pintype "passive"))
      (node (ref "R64") (pin "2") (pinfunction "2_2") (pintype "passive"))
      (node (ref "R72") (pin "1") (pinfunction "1_1") (pintype "passive"))
      (node (ref "T4") (pin "2") (pinfunction "S_2") (pintype "passive"))
      (node (ref "TP13") (pin "P$1") (pinfunction "TP_P$1") (pintype "input"))
      (node (ref "X13") (pin "58") (pinfunction "58_58") (pintype "passive"))
      (node (ref "X25") (pin "1") (pinfunction "1_1") (pintype "passive"))
      (node (ref "X4") (pin "4") (pinfunction "4_4") (pintype "passive"))
    )
    (net (code "3") (name "+3V3_SSD") (class "Default")
      (node (ref "C104") (pin "1") (pinfunction "1_1") (pintype "passive"))
      (node (ref "C105") (pin "1") (pinfunction "1_1") (pintype "passive"))
      (node (ref "C106") (pin "1") (pinfunction "1_1") (pintype "passive"))
      (node (ref "C118") (pin "+") (pinfunction "+_+") (pintype "passive"))
      (node (ref "C268") (pin "1") (pinfunction "1_1") (pintype "passive"))
      (node (ref "C270") (pin "1") (pinfunction "1_1") (pintype "passive"))
      (node (ref "C54") (pin "1") (pinfunction "1_1") (pintype "passive"))
      (node (ref "D4") (pin "A") (pinfunction "A_A") (pintype "passive"))
      (node (ref "L19") (pin "NO_DOT") (pinfunction "NODOT_NO_DOT") (pintype "passive"))
      (node (ref "R275") (pin "2") (pinfunction "2_2") (pintype "passive"))
      (node (ref "R279") (pin "2") (pinfunction "2_2") (pintype "passive"))
      (node (ref "R339") (pin "2") (pinfunction "2_2") (pintype "passive"))
      (node (ref "R515") (pin "1") (pinfunction "1_1") (pintype "passive"))
      (node (ref "TP50") (pin "P$1") (pinfunction "TP_P$1") (pintype "input"))
      (node (ref "X33") (pin "12") (pinfunction "VCC_12") (pintype "input"))
      (node (ref "X33") (pin "14") (pinfunction "VCC_14") (pintype "input"))
      (node (ref "X33") (pin "16") (pinfunction "VCC_16") (pintype "input"))
      (node (ref "X33") (pin "18") (pinfunction "VCC_18") (pintype "input"))
      (node (ref "X33") (pin "2") (pinfunction "VCC_2") (pintype "input"))
      (node (ref "X33") (pin "4") (pinfunction "VCC_4") (pintype "input"))
      (node (ref "X33") (pin "70") (pinfunction "VCC_70") (pintype "input"))
      (node (ref "X33") (pin "72") (pinfunction "VCC_72") (pintype "input"))
      (node (ref "X33") (pin "74") (pinfunction "VCC_74") (pintype "input"))
    )
    (net (code "4") (name "+3V3_WIFI") (class "Default")
      (node (ref "C119") (pin "1") (pinfunction "1_1") (pintype "passive"))
      (node (ref "C130") (pin "1") (pinfunction "1_1") (pintype "passive"))
      (node (ref "C19") (pin "+") (pinfunction "+_+") (pintype "passive"))
      (node (ref "C237") (pin "1") (pinfunction "1_1") (pintype "passive"))
      (node (ref "C73") (pin "1") (pinfunction "1_1") (pintype "passive"))
      (node (ref "C74") (pin "1") (pinfunction "1_1") (pintype "passive"))
      (node (ref "D8") (pin "A") (pinfunction "A_A") (pintype "passive"))
      (node (ref "D9") (pin "A") (pinfunction "A_A") (pintype "passive"))
      (node (ref "L21") (pin "NO_DOT") (pinfunction "NODOT_NO_DOT") (pintype "passive"))
      (node (ref "R139") (pin "2") (pinfunction "2_2") (pintype "passive"))
      (node (ref "R140") (pin "1") (pinfunction "1_1") (pintype "passive"))
      (node (ref "R16") (pin "2") (pinfunction "2_2") (pintype "passive"))
      (node (ref "R283") (pin "2") (pinfunction "2_2") (pintype "passive"))
      (node (ref "R318") (pin "2") (pinfunction "2_2") (pintype "passive"))
      (node (ref "R338") (pin "2") (pinfunction "2_2") (pintype "passive"))
      (node (ref "R488") (pin "1") (pinfunction "1_1") (pintype "passive"))
      (node (ref "R8") (pin "2") (pinfunction "2_2") (pintype "passive"))
      (node (ref "TP51") (pin "P$1") (pinfunction "TP_P$1") (pintype "input"))
      (node (ref "X18") (pin "2") (pinfunction "3V3_2") (pintype "input"))
      (node (ref "X18") (pin "4") (pinfunction "3V3_4") (pintype "input"))
      (node (ref "X18") (pin "72") (pinfunction "3V3_72") (pintype "input"))
      (node (ref "X18") (pin "74") (pinfunction "3V3_74") (pintype "input"))
    )
    (net (code "5") (name "+3V8") (class "Default")
      (node (ref "C284") (pin "1") (pinfunction "1_1") (pintype "passive"))
      (node (ref "C5") (pin "1") (pinfunction "1_1") (pintype "passive"))
      (node (ref "C6") (pin "1") (pinfunction "1_1") (pintype "passive"))
      (node (ref "L1") (pin "NO_DOT") (pinfunction "NODOT_NO_DOT") (pintype "passive"))
      (node (ref "L44") (pin "1") (pinfunction "1_1") (pintype "passive"))
      (node (ref "R242") (pin "2") (pinfunction "2_2") (pintype "passive"))
      (node (ref "R418") (pin "1") (pinfunction "1_1") (pintype "passive"))
      (node (ref "R519") (pin "2") (pinfunction "2_2") (pintype "passive"))
      (node (ref "TP14") (pin "P$1") (pinfunction "TP_P$1") (pintype "input"))
    )
    (net (code "6") (name "+5V") (class "Default")
      (node (ref "C16") (pin "1") (pinfunction "1_1") (pintype "passive"))
      (node (ref "C17") (pin "1") (pinfunction "1_1") (pintype "passive"))
      (node (ref "C255") (pin "1") (pinfunction "1_1") (pintype "passive"))
      (node (ref "C28") (pin "1") (pinfunction "1_1") (pintype "passive"))
      (node (ref "C298") (pin "1") (pinfunction "1_1") (pintype "passive"))
      (node (ref "C299") (pin "1") (pinfunction "1_1") (pintype "passive"))
      (node (ref "C35") (pin "1") (pinfunction "1_1") (pintype "passive"))
      (node (ref "C65") (pin "1") (pinfunction "1_1") (pintype "passive"))
      (node (ref "C85") (pin "1") (pinfunction "1_1") (pintype "passive"))
      (node (ref "C86") (pin "+") (pinfunction "+_+") (pintype "passive"))
      (node (ref "C91") (pin "1") (pinfunction "1_1") (pintype "passive"))
      (node (ref "C92") (pin "+") (pinfunction "+_+") (pintype "passive"))
      (node (ref "D13") (pin "C") (pinfunction "C_C") (pintype "passive"))
      (node (ref "F4") (pin "2") (pinfunction "2_2") (pintype "passive"))
      (node (ref "IC52") (pin "5") (pinfunction "VBUS_5") (pintype "input"))
      (node (ref "IC57") (pin "5") (pinfunction "VBUS_5") (pintype "input"))
      (node (ref "L2") (pin "2") (pinfunction "2_2") (pintype "passive"))
      (node (ref "L20") (pin "2") (pinfunction "2_2") (pintype "passive"))
      (node (ref "L22") (pin "2") (pinfunction "2_2") (pintype "passive"))
      (node (ref "L38") (pin "2") (pinfunction "2_2") (pintype "passive"))
      (node (ref "L39") (pin "2") (pinfunction "2_2") (pintype "passive"))
      (node (ref "L4") (pin "2") (pinfunction "2_2") (pintype "passive"))
      (node (ref "L5") (pin "NO_DOT") (pinfunction "NODOT_NO_DOT") (pintype "passive"))
      (node (ref "MOD1") (pin "251") (pinfunction "VDD_IN_251") (pintype "input"))
      (node (ref "MOD1") (pin "252") (pinfunction "VDD_IN_252") (pintype "input"))
      (node (ref "MOD1") (pin "253") (pinfunction "VDD_IN_253") (pintype "input"))
      (node (ref "MOD1") (pin "254") (pinfunction "VDD_IN_254") (pintype "input"))
      (node (ref "MOD1") (pin "255") (pinfunction "VDD_IN_255") (pintype "input"))
      (node (ref "MOD1") (pin "256") (pinfunction "VDD_IN_256") (pintype "input"))
      (node (ref "MOD1") (pin "257") (pinfunction "VDD_IN_257") (pintype "input"))
      (node (ref "MOD1") (pin "258") (pinfunction "VDD_IN_258") (pintype "input"))
      (node (ref "MOD1") (pin "259") (pinfunction "VDD_IN_259") (pintype "input"))
      (node (ref "MOD1") (pin "260") (pinfunction "VDD_IN_260") (pintype "input"))
      (node (ref "R106") (pin "2") (pinfunction "2_2") (pintype "passive"))
      (node (ref "R109") (pin "2") (pinfunction "2_2") (pintype "passive"))
      (node (ref "R111") (pin "2") (pinfunction "2_2") (pintype "passive"))
      (node (ref "R116") (pin "2") (pinfunction "2_2") (pintype "passive"))
      (node (ref "R152") (pin "1") (pinfunction "1_1") (pintype "passive"))
      (node (ref "R199") (pin "2") (pinfunction "2_2") (pintype "passive"))
      (node (ref "R201") (pin "2") (pinfunction "2_2") (pintype "passive"))
      (node (ref "R238") (pin "2") (pinfunction "2_2") (pintype "passive"))
      (node (ref "R291") (pin "2") (pinfunction "2_2") (pintype "passive"))
      (node (ref "R309") (pin "1") (pinfunction "1_1") (pintype "passive"))
      (node (ref "R317") (pin "2") (pinfunction "2_2") (pintype "passive"))
      (node (ref "R319") (pin "2") (pinfunction "2_2") (pintype "passive"))
      (node (ref "R373") (pin "2") (pinfunction "2_2") (pintype "passive"))
      (node (ref "R534") (pin "2") (pinfunction "2_2") (pintype "passive"))
      (node (ref "R535") (pin "2") (pinfunction "2_2") (pintype "passive"))
      (node (ref "R92") (pin "2") (pinfunction "2_2") (pintype "passive"))
      (node (ref "T29") (pin "2") (pinfunction "S_2") (pintype "passive"))
      (node (ref "T49") (pin "2") (pinfunction "S_2") (pintype "passive"))
      (node (ref "TP11") (pin "P$1") (pinfunction "TP_P$1") (pintype "input"))
      (node (ref "X4") (pin "2") (pinfunction "2_2") (pintype "passive"))
    )
    (net (code "7") (name "+12V") (class "Default")
      (node (ref "C206") (pin "1") (pinfunction "1_1") (pintype "passive"))
      (node (ref "C209") (pin "1") (pinfunction "1_1") (pintype "passive"))
      (node (ref "C279") (pin "1") (pinfunction "1_1") (pintype "passive"))
      (node (ref "C43") (pin "1") (pinfunction "1_1") (pintype "passive"))
      (node (ref "C44") (pin "1") (pinfunction "1_1") (pintype "passive"))
      (node (ref "L14") (pin "3") (pinfunction "NODOT_3") (pintype "passive"))
      (node (ref "R424") (pin "1") (pinfunction "1_1") (pintype "passive"))
      (node (ref "R452") (pin "2") (pinfunction "2_2") (pintype "passive"))
      (node (ref "R455") (pin "2") (pinfunction "2_2") (pintype "passive"))
      (node (ref "R520") (pin "2") (pinfunction "2_2") (pintype "passive"))
      (node (ref "R61") (pin "1") (pinfunction "1_1") (pintype "passive"))
      (node (ref "R98") (pin "2") (pinfunction "2_2") (pintype "passive"))
      (node (ref "T52") (pin "3") (pinfunction "D_3") (pintype "passive"))
      (node (ref "T54") (pin "3") (pinfunction "D_3") (pintype "passive"))
      (node (ref "TP3") (pin "P$1") (pinfunction "TP_P$1") (pintype "input"))
      (node (ref "X13") (pin "66") (pinfunction "66_66") (pintype "passive"))
    )
    (net (code "8") (name "+PVCC") (class "Default")
      (node (ref "C109") (pin "1") (pinfunction "1_1") (pintype "passive"))
      (node (ref "C110") (pin "1") (pinfunction "1_1") (pintype "passive"))
      (node (ref "C112") (pin "1") (pinfunction "1_1") (pintype "passive"))
      (node (ref "C114") (pin "1") (pinfunction "1_1") (pintype "passive"))
      (node (ref "C181") (pin "1") (pinfunction "1_1") (pintype "passive"))
      (node (ref "C182") (pin "1") (pinfunction "1_1") (pintype "passive"))
      (node (ref "C183") (pin "1") (pinfunction "1_1") (pintype "passive"))
      (node (ref "C185") (pin "1") (pinfunction "1_1") (pintype "passive"))
      (node (ref "C195") (pin "+") (pinfunction "+_+") (pintype "passive"))
      (node (ref "C77") (pin "1") (pinfunction "1_1") (pintype "passive"))
      (node (ref "D14") (pin "C") (pinfunction "C_C") (pintype "passive"))
      (node (ref "F2") (pin "2") (pinfunction "2_2") (pintype "passive"))
      (node (ref "R385") (pin "2") (pinfunction "2_2") (pintype "passive"))
      (node (ref "R430") (pin "1") (pinfunction "1_1") (pintype "passive"))
      (node (ref "R510") (pin "2") (pinfunction "2_2") (pintype "passive"))
      (node (ref "R511") (pin "2") (pinfunction "2_2") (pintype "passive"))
      (node (ref "T16") (pin "D1") (pinfunction "D_D1") (pintype "passive"))
      (node (ref "T16") (pin "D10") (pinfunction "D_D10") (pintype "passive"))
      (node (ref "T16") (pin "D11") (pinfunction "D_D11") (pintype "passive"))
      (node (ref "T16") (pin "D12") (pinfunction "D_D12") (pintype "passive"))
      (node (ref "T16") (pin "D13") (pinfunction "D_D13") (pintype "passive"))
      (node (ref "T16") (pin "D14") (pinfunction "D_D14") (pintype "passive"))
      (node (ref "T16") (pin "D15") (pinfunction "D_D15") (pintype "passive"))
      (node (ref "T16") (pin "D2") (pinfunction "D_D2") (pintype "passive"))
      (node (ref "T16") (pin "D3") (pinfunction "D_D3") (pintype "passive"))
      (node (ref "T16") (pin "D4") (pinfunction "D_D4") (pintype "passive"))
      (node (ref "T16") (pin "D5") (pinfunction "D_D5") (pintype "passive"))
      (node (ref "T16") (pin "D6") (pinfunction "D_D6") (pintype "passive"))
      (node (ref "T16") (pin "D7") (pinfunction "D_D7") (pintype "passive"))
      (node (ref "T16") (pin "D8") (pinfunction "D_D8") (pintype "passive"))
      (node (ref "T16") (pin "D9") (pinfunction "D_D9") (pintype "passive"))
      (node (ref "TP63") (pin "P$1") (pinfunction "TP_P$1") (pintype "input"))
    )
    (net (code "9") (name "+VBAT") (class "Default")
      (node (ref "C23") (pin "1") (pinfunction "1_1") (pintype "passive"))
      (node (ref "C81") (pin "1") (pinfunction "1_1") (pintype "passive"))
      (node (ref "D31") (pin "C") (pinfunction "C_C") (pintype "passive"))
      (node (ref "R217") (pin "2") (pinfunction "2_2") (pintype "passive"))
      (node (ref "R35") (pin "2") (pinfunction "2_2") (pintype "passive"))
      (node (ref "R525") (pin "1") (pinfunction "1_1") (pintype "passive"))
      (node (ref "T21") (pin "1") (pinfunction "S_1") (pintype "passive"))
      (node (ref "T21") (pin "2") (pinfunction "S_2") (pintype "passive"))
      (node (ref "T21") (pin "3") (pinfunction "S_3") (pintype "passive"))
      (node (ref "T3") (pin "1") (pinfunction "S_1") (pintype "passive"))
      (node (ref "T3") (pin "2") (pinfunction "S_2") (pintype "passive"))
      (node (ref "T3") (pin "3") (pinfunction "S_3") (pintype "passive"))
      (node (ref "TP6") (pin "P$1") (pinfunction "TP_P$1") (pintype "input"))
      (node (ref "X4") (pin "3") (pinfunction "3_3") (pintype "passive"))
    )
    (net (code "10") (name "+VBAT_SW") (class "Default")
      (node (ref "C151") (pin "1") (pinfunction "1_1") (pintype "passive"))
      (node (ref "C152") (pin "1") (pinfunction "1_1") (pintype "passive"))
      (node (ref "C39") (pin "1") (pinfunction "1_1") (pintype "passive"))
      (node (ref "D18") (pin "C") (pinfunction "C_C") (pintype "passive"))
      (node (ref "F3") (pin "1") (pinfunction "1_1") (pintype "passive"))
      (node (ref "L3") (pin "2") (pinfunction "2_2") (pintype "passive"))
      (node (ref "L45") (pin "2") (pinfunction "2_2") (pintype "passive"))
      (node (ref "L9") (pin "2") (pinfunction "2_2") (pintype "passive"))
      (node (ref "R370") (pin "2") (pinfunction "2_2") (pintype "passive"))
      (node (ref "R84") (pin "1") (pinfunction "1_1") (pintype "passive"))
      (node (ref "T19") (pin "1") (pinfunction "D_1") (pintype "passive"))
      (node (ref "T19") (pin "2") (pinfunction "D_2") (pintype "passive"))
      (node (ref "T19") (pin "5") (pinfunction "D_5") (pintype "passive"))
      (node (ref "T19") (pin "6") (pinfunction "D_6") (pintype "passive"))
      (node (ref "T19") (pin "D") (pinfunction "D_D") (pintype "passive"))
      (node (ref "T21") (pin "5") (pinfunction "D_5") (pintype "passive"))
      (node (ref "TP62") (pin "P$1") (pinfunction "TP_P$1") (pintype "input"))
      (node (ref "X13") (pin "70") (pinfunction "70_70") (pintype "passive"))
      (node (ref "X13") (pin "72") (pinfunction "72_72") (pintype "passive"))
    )
    (net (code "11") (name "/5V_BUCK_~{EN}_3V3") (class "Default")
      (node (ref "R259") (pin "1") (pinfunction "1_1") (pintype "passive"))
      (node (ref "R445") (pin "2") (pinfunction "2_2") (pintype "passive"))
      (node (ref "T63") (pin "1") (pinfunction "G_1") (pintype "passive"))
    )
    (net (code "12") (name "/AX200_~{DISABLE_BT}_3V3") (class "Default")
      (node (ref "R139") (pin "1") (pinfunction "1_1") (pintype "passive"))
      (node (ref "T6") (pin "3") (pinfunction "D_3") (pintype "passive"))
      (node (ref "X18") (pin "54") (pinfunction "W_DISABLE2#_54") (pintype "input"))
    )
    (net (code "13") (name "/AX200_~{DISABLE_WIFI}_3V3") (class "Default")
      (node (ref "R8") (pin "1") (pinfunction "1_1") (pintype "passive"))
      (node (ref "T5") (pin "3") (pinfunction "D_3") (pintype "passive"))
      (node (ref "X18") (pin "56") (pinfunction "W_DISABLE1#_56") (pintype "input"))
    )
    (net (code "14") (name "/CAM0_FLASH_FROM_SENSOR") (class "Default")
      (node (ref "R438") (pin "2") (pinfunction "2_2") (pintype "passive"))
      (node (ref "X25") (pin "5") (pinfunction "5_5") (pintype "passive"))
    )
    (net (code "15") (name "/JETSON_M2_M_~{ALERT}_1V8") (class "Default")
      (node (ref "MOD1") (pin "221") (pinfunction "SDMMC_DAT1_221") (pintype "bidirectional"))
      (node (ref "R304") (pin "1") (pinfunction "1_1") (pintype "passive"))
    )
    (net (code "16") (name "/JETSON_M2_~{ALERT_1V8}") (class "Default")
      (node (ref "MOD1") (pin "212") (pinfunction "GPIO10/I2S3_SCKL_212") (pintype "bidirectional"))
      (node (ref "R292") (pin "1") (pinfunction "1_1") (pintype "passive"))
    )
    (net (code "17") (name "/JETSON_M2_~{UART_WAKE_1V8}") (class "Default")
      (node (ref "MOD1") (pin "124") (pinfunction "GPIO02/I2S2_DOUT_124") (pintype "bidirectional"))
      (node (ref "R295") (pin "1") (pinfunction "1_1") (pintype "passive"))
    )
    (net (code "18") (name "/JETSON_PCIE0_~{CLKREQ}_3V3") (class "Default")
      (node (ref "MOD1") (pin "180") (pinfunction "PCIE0_~{CLKREQ}_180") (pintype "bidirectional"))
      (node (ref "X18") (pin "53") (pinfunction "CLKREQ0#_53") (pintype "bidirectional"))
    )
    (net (code "19") (name "/JETSON_PCIE0_~{RST}_3V3") (class "Default")
      (node (ref "MOD1") (pin "181") (pinfunction "PCIE0_~{RST}_181") (pintype "output"))
      (node (ref "X18") (pin "52") (pinfunction "PERST0#_52") (pintype "input"))
    )
    (net (code "20") (name "/JETSON_PCIE1_~{CLKREQ}_3V3") (class "Default")
      (node (ref "MOD1") (pin "182") (pinfunction "PCIE1_~{CLKREQ/RSVD}_182") (pintype "bidirectional"))
      (node (ref "X33") (pin "52") (pinfunction "CLKREQ#/NC_52") (pintype "bidirectional"))
    )
    (net (code "21") (name "/JETSON_PCIE1_~{RST}_3V3") (class "Default")
      (node (ref "MOD1") (pin "183") (pinfunction "PCIE1_~{RST/RSVD}_183") (pintype "output"))
      (node (ref "X33") (pin "50") (pinfunction "PERST#/NC_50") (pintype "input"))
    )
    (net (code "22") (name "/JETSON_PCIE_~{WAKE}_3V3") (class "Default")
      (node (ref "MOD1") (pin "179") (pinfunction "PCIE_~{WAKE}_179") (pintype "input"))
      (node (ref "X18") (pin "55") (pinfunction "PEWAKE0#_55") (pintype "bidirectional"))
      (node (ref "X33") (pin "54") (pinfunction "PEWAKE#/NC_54") (pintype "bidirectional"))
    )
    (net (code "23") (name "/JETSON_SLEEP{slash}~{WAKE}_5V") (class "Default")
      (node (ref "C236") (pin "1") (pinfunction "1_1") (pintype "passive"))
      (node (ref "MOD1") (pin "240") (pinfunction "SLEEP/~{WAKE}_240") (pintype "input"))
      (node (ref "R106") (pin "1") (pinfunction "1_1") (pintype "passive"))
      (node (ref "T60") (pin "3") (pinfunction "D_3") (pintype "passive"))
    )
    (net (code "24") (name "/JETSON_~{FORCE_RECOVERY}") (class "Default")
      (node (ref "MOD1") (pin "214") (pinfunction "~{FORCE_RECOVERY}_214") (pintype "input"))
      (node (ref "R303") (pin "2") (pinfunction "2_2") (pintype "passive"))
      (node (ref "TP72") (pin "P$1") (pinfunction "TP_P$1") (pintype "input"))
    )
    (net (code "25") (name "/JETSON_~{MOD_SLEEP}_1V8") (class "Default")
      (node (ref "IC11") (pin "5") (pinfunction "A3_5") (pintype "bidirectional"))
      (node (ref "MOD1") (pin "178") (pinfunction "~{MOD_SLEEP}_178") (pintype "output"))
      (node (ref "R156") (pin "1") (pinfunction "1_1") (pintype "passive"))
      (node (ref "R439") (pin "1") (pinfunction "1_1") (pintype "passive"))
    )
    (net (code "26") (name "/JETSON_~{MOD_SLEEP}_3V3") (class "Default")
      (node (ref "R331") (pin "1") (pinfunction "1_1") (pintype "passive"))
      (node (ref "R51") (pin "2") (pinfunction "2_2") (pintype "passive"))
    )
    (net (code "27") (name "/JETSON_~{SHUTDOWN_REQ}_5V") (class "Default")
      (node (ref "IC20") (pin "94") (pinfunction "PB7_94") (pintype "bidirectional"))
      (node (ref "R107") (pin "1") (pinfunction "1_1") (pintype "passive"))
      (node (ref "R109") (pin "1") (pinfunction "1_1") (pintype "passive"))
    )
    (net (code "28") (name "/JETSON_~{SLEEP}{slash}WAKE_3V3") (class "Default")
      (node (ref "R105") (pin "2") (pinfunction "2_2") (pintype "passive"))
      (node (ref "R273") (pin "1") (pinfunction "1_1") (pintype "passive"))
      (node (ref "T60") (pin "1") (pinfunction "G_1") (pintype "passive"))
    )
    (net (code "29") (name "/JETSON_~{SYS_RESET}->UC_3V3") (class "Default")
      (node (ref "IC20") (pin "42") (pinfunction "PE11_42") (pintype "bidirectional"))
      (node (ref "R62") (pin "2") (pinfunction "2_2") (pintype "passive"))
    )
    (net (code "30") (name "/JETSON_~{SYS_RESET}_1V8") (class "Default")
      (node (ref "IC32") (pin "2") (pinfunction "A_2") (pintype "input"))
      (node (ref "MOD1") (pin "239") (pinfunction "~{SYS_RESET}_239") (pintype "bidirectional"))
      (node (ref "T59") (pin "3") (pinfunction "D_3") (pintype "passive"))
      (node (ref "TP67") (pin "P$1") (pinfunction "TP_P$1") (pintype "input"))
    )
    (net (code "31") (name "/LM5122_~{EN}") (class "Default")
      (node (ref "R357") (pin "1") (pinfunction "1_1") (pintype "passive"))
      (node (ref "T18") (pin "1") (pinfunction "G_1") (pintype "passive"))
      (node (ref "T36") (pin "3") (pinfunction "D_3") (pintype "passive"))
    )
    (net (code "32") (name "/PMIC_BBAT") (class "Default")
      (node (ref "C230") (pin "1") (pinfunction "1_1") (pintype "passive"))
      (node (ref "D29") (pin "3") (pinfunction "C_3") (pintype "passive"))
      (node (ref "D30") (pin "3") (pinfunction "C_3") (pintype "passive"))
      (node (ref "MOD1") (pin "235") (pinfunction "PMIC_BBAT_235") (pintype "bidirectional"))
    )
    (net (code "33") (name "/UART_DBG_EXT->UC") (class "Default")
      (node (ref "R177") (pin "1") (pinfunction "1_1") (pintype "passive"))
      (node (ref "R192") (pin "2") (pinfunction "2_2") (pintype "passive"))
      (node (ref "TP18") (pin "P$1") (pinfunction "TP_P$1") (pintype "input"))
    )
    (net (code "34") (name "/UART_DBG_UC->EXT") (class "Default")
      (node (ref "R176") (pin "1") (pinfunction "1_1") (pintype "passive"))
      (node (ref "TP17") (pin "P$1") (pinfunction "TP_P$1") (pintype "input"))
    )
    (net (code "35") (name "/UC->JETSON_SYS_RESET_3V3") (class "Default")
      (node (ref "R101") (pin "2") (pinfunction "2_2") (pintype "passive"))
      (node (ref "R332") (pin "2") (pinfunction "2_2") (pintype "passive"))
      (node (ref "T59") (pin "1") (pinfunction "G_1") (pintype "passive"))
    )
    (net (code "36") (name "/UC_AMP_SEL_UC{slash}~{JETSON}_3V3") (class "Default")
      (node (ref "IC54") (pin "15") (pinfunction "A0_15") (pintype "input"))
      (node (ref "IC55") (pin "15") (pinfunction "A0_15") (pintype "input"))
      (node (ref "R17") (pin "1") (pinfunction "1_1") (pintype "passive"))
      (node (ref "R492") (pin "2") (pinfunction "2_2") (pintype "passive"))
    )
    (net (code "37") (name "/UC_FU_~{PVCC_EN}_3V3") (class "Default")
      (node (ref "IC20") (pin "79") (pinfunction "PC10_79") (pintype "bidirectional"))
      (node (ref "R556") (pin "2") (pinfunction "2_2") (pintype "passive"))
    )
    (net (code "38") (name "/UC_GPS_~{RESET}_3V3") (class "Default")
      (node (ref "R230") (pin "1") (pinfunction "1_1") (pintype "passive"))
      (node (ref "R27") (pin "2") (pinfunction "2_2") (pintype "passive"))
    )
    (net (code "39") (name "/UC_LM5122_~{FPWM_3V3}") (class "Default")
      (node (ref "R19") (pin "1") (pinfunction "1_1") (pintype "passive"))
      (node (ref "R381") (pin "2") (pinfunction "2_2") (pintype "passive"))
      (node (ref "T34") (pin "1") (pinfunction "G_1") (pintype "passive"))
    )
    (net (code "40") (name "/UC_LTE_~{RST}_3V3") (class "Default")
      (node (ref "R316") (pin "2") (pinfunction "2_2") (pintype "passive"))
      (node (ref "R479") (pin "1") (pinfunction "1_1") (pintype "passive"))
    )
    (net (code "41") (name "/UC_USB_~{RST}_3V3") (class "Default")
      (node (ref "C154") (pin "1") (pinfunction "1_1") (pintype "passive"))
      (node (ref "IC19") (pin "26") (pinfunction "RESET_N_26") (pintype "input"))
      (node (ref "R321") (pin "1") (pinfunction "1_1") (pintype "passive"))
    )
    (net (code "42") (name "/UC_~{BTN_POWER}_3V3") (class "Default")
      (node (ref "IC20") (pin "7") (pinfunction "PC13_7") (pintype "bidirectional"))
      (node (ref "R6") (pin "2") (pinfunction "2_2") (pintype "passive"))
    )
    (net (code "43") (name "/~{BTN_PWR}") (class "Default")
      (node (ref "R212") (pin "1") (pinfunction "1_1") (pintype "passive"))
      (node (ref "R362") (pin "1") (pinfunction "1_1") (pintype "passive"))
      (node (ref "R63") (pin "1") (pinfunction "1_1") (pintype "passive"))
      (node (ref "T25") (pin "1") (pinfunction "G_1") (pintype "passive"))
      (node (ref "TP15") (pin "P$1") (pinfunction "TP_P$1") (pintype "input"))
      (node (ref "X12") (pin "2") (pinfunction "2_2") (pintype "passive"))
    )
    (net (code "44") (name "1V8_SUPPLY_EN_3V3") (class "Default")
      (node (ref "C280") (pin "1") (pinfunction "1_1") (pintype "passive"))
      (node (ref "IC33") (pin "2") (pinfunction "EN_2") (pintype "input"))
      (node (ref "R255") (pin "2") (pinfunction "2_2") (pintype "passive"))
      (node (ref "R326") (pin "1") (pinfunction "1_1") (pintype "passive"))
    )
    (net (code "45") (name "3V3_HDMI") (class "Default")
      (node (ref "C61") (pin "1") (pinfunction "1_1") (pintype "passive"))
      (node (ref "R170") (pin "2") (pinfunction "2_2") (pintype "passive"))
      (node (ref "R171") (pin "2") (pinfunction "2_2") (pintype "passive"))
      (node (ref "R173") (pin "1") (pinfunction "1_1") (pintype "passive"))
      (node (ref "R182") (pin "2") (pinfunction "2_2") (pintype "passive"))
      (node (ref "R183") (pin "2") (pinfunction "2_2") (pintype "passive"))
      (node (ref "R187") (pin "2") (pinfunction "2_2") (pintype "passive"))
      (node (ref "T35") (pin "1") (pinfunction "G_1") (pintype "passive"))
      (node (ref "T38") (pin "1") (pinfunction "G_1") (pintype "passive"))
      (node (ref "T42") (pin "1") (pinfunction "G_1") (pintype "passive"))
      (node (ref "T43") (pin "1") (pinfunction "G_1") (pintype "passive"))
    )
    (net (code "46") (name "3V3_OPAMPS") (class "Default")
      (node (ref "R258") (pin "2") (pinfunction "2_2") (pintype "passive"))
      (node (ref "R420") (pin "2") (pinfunction "2_2") (pintype "passive"))
      (node (ref "R427") (pin "2") (pinfunction "2_2") (pintype "passive"))
      (node (ref "R65") (pin "2") (pinfunction "2_2") (pintype "passive"))
      (node (ref "T24") (pin "3") (pinfunction "D_3") (pintype "passive"))
    )
    (net (code "47") (name "3V3_SUPPLY_EN_3V3") (class "Default")
      (node (ref "C194") (pin "1") (pinfunction "1_1") (pintype "passive"))
      (node (ref "C278") (pin "1") (pinfunction "1_1") (pintype "passive"))
      (node (ref "C87") (pin "1") (pinfunction "1_1") (pintype "passive"))
      (node (ref "IC25") (pin "2") (pinfunction "EN_2") (pintype "input"))
      (node (ref "IC45") (pin "2") (pinfunction "EN_2") (pintype "input"))
      (node (ref "IC74") (pin "2") (pinfunction "EN_2") (pintype "input"))
      (node (ref "R36") (pin "2") (pinfunction "2_2") (pintype "passive"))
      (node (ref "R57") (pin "1") (pinfunction "1_1") (pintype "passive"))
    )
    (net (code "48") (name "3V3_UC") (class "Default")
      (node (ref "C21") (pin "1") (pinfunction "1_1") (pintype "passive"))
      (node (ref "C22") (pin "1") (pinfunction "1_1") (pintype "passive"))
      (node (ref "C289") (pin "1") (pinfunction "1_1") (pintype "passive"))
      (node (ref "D12") (pin "A") (pinfunction "A_A") (pintype "passive"))
      (node (ref "IC14") (pin "5") (pinfunction "VBUS_5") (pintype "input"))
      (node (ref "IC6") (pin "5") (pinfunction "VBUS_5") (pintype "input"))
      (node (ref "L32") (pin "1") (pinfunction "1_1") (pintype "passive"))
      (node (ref "R108") (pin "2") (pinfunction "2_2") (pintype "passive"))
      (node (ref "R12") (pin "2") (pinfunction "2_2") (pintype "passive"))
      (node (ref "R123") (pin "2") (pinfunction "2_2") (pintype "passive"))
      (node (ref "R192") (pin "1") (pinfunction "1_1") (pintype "passive"))
      (node (ref "R236") (pin "2") (pinfunction "2_2") (pintype "passive"))
      (node (ref "R240") (pin "1") (pinfunction "1_1") (pintype "passive"))
      (node (ref "R272") (pin "2") (pinfunction "2_2") (pintype "passive"))
      (node (ref "R313") (pin "2") (pinfunction "2_2") (pintype "passive"))
      (node (ref "R34") (pin "2") (pinfunction "2_2") (pintype "passive"))
      (node (ref "R42") (pin "1") (pinfunction "1_1") (pintype "passive"))
      (node (ref "R445") (pin "1") (pinfunction "1_1") (pintype "passive"))
      (node (ref "R539") (pin "2") (pinfunction "2_2") (pintype "passive"))
      (node (ref "R553") (pin "2") (pinfunction "2_2") (pintype "passive"))
      (node (ref "R555") (pin "2") (pinfunction "2_2") (pintype "passive"))
      (node (ref "R60") (pin "2") (pinfunction "2_2") (pintype "passive"))
      (node (ref "R63") (pin "2") (pinfunction "2_2") (pintype "passive"))
      (node (ref "T24") (pin "2") (pinfunction "S_2") (pintype "passive"))
      (node (ref "T25") (pin "3") (pinfunction "D_3") (pintype "passive"))
      (node (ref "TP12") (pin "P$1") (pinfunction "TP_P$1") (pintype "input"))
      (node (ref "X21") (pin "1") (pinfunction "VCC_1") (pintype "input"))
      (node (ref "X6") (pin "1") (pinfunction "VCC_1") (pintype "input"))
    )
    (net (code "49") (name "3V8_SUPPLY_EN_3V3") (class "Default")
      (node (ref "C276") (pin "1") (pinfunction "1_1") (pintype "passive"))
      (node (ref "IC1") (pin "2") (pinfunction "EN_2") (pintype "input"))
      (node (ref "R246") (pin "2") (pinfunction "2_2") (pintype "passive"))
      (node (ref "R274") (pin "1") (pinfunction "1_1") (pintype "passive"))
    )
    (net (code "50") (name "5V_HDMI") (class "Default")
      (node (ref "C63") (pin "1") (pinfunction "1_1") (pintype "passive"))
      (node (ref "L10") (pin "1") (pinfunction "1_1") (pintype "passive"))
      (node (ref "R185") (pin "2") (pinfunction "2_2") (pintype "passive"))
      (node (ref "R186") (pin "2") (pinfunction "2_2") (pintype "passive"))
      (node (ref "X7") (pin "18") (pinfunction "+5VPOWER_18") (pintype "input"))
    )
    (net (code "51") (name "12V_CAPS") (class "Default")
      (node (ref "C150") (pin "2") (pinfunction "2_2") (pintype "passive"))
      (node (ref "C153") (pin "1") (pinfunction "1_1") (pintype "passive"))
      (node (ref "C166") (pin "1") (pinfunction "1_1") (pintype "passive"))
      (node (ref "C167") (pin "1") (pinfunction "1_1") (pintype "passive"))
      (node (ref "C174") (pin "+") (pinfunction "+_+") (pintype "passive"))
      (node (ref "C179") (pin "1") (pinfunction "1_1") (pintype "passive"))
      (node (ref "C180") (pin "1") (pinfunction "1_1") (pintype "passive"))
      (node (ref "C201") (pin "1") (pinfunction "1_1") (pintype "passive"))
      (node (ref "C202") (pin "1") (pinfunction "1_1") (pintype "passive"))
      (node (ref "C203") (pin "1") (pinfunction "1_1") (pintype "passive"))
      (node (ref "D17") (pin "A") (pinfunction "A_A") (pintype "passive"))
      (node (ref "D18") (pin "A1") (pinfunction "A_A1") (pintype "passive"))
      (node (ref "D18") (pin "A2") (pinfunction "A_A2") (pintype "passive"))
      (node (ref "IC35") (pin "9") (pinfunction "SRN_9") (pintype "input"))
      (node (ref "IC41") (pin "8") (pinfunction "VCC_8") (pintype "input"))
      (node (ref "IC42") (pin "8") (pinfunction "VCC_8") (pintype "input"))
      (node (ref "IC43") (pin "8") (pinfunction "VCC_8") (pintype "input"))
      (node (ref "R343") (pin "1") (pinfunction "1_1") (pintype "passive"))
      (node (ref "R346") (pin "2") (pinfunction "2_2") (pintype "passive"))
      (node (ref "R347") (pin "2") (pinfunction "2_2") (pintype "passive"))
      (node (ref "R353") (pin "2") (pinfunction "2_2") (pintype "passive"))
      (node (ref "R357") (pin "2") (pinfunction "2_2") (pintype "passive"))
      (node (ref "R367") (pin "2") (pinfunction "2_2") (pintype "passive"))
      (node (ref "R368") (pin "2") (pinfunction "2_2") (pintype "passive"))
      (node (ref "R384") (pin "2") (pinfunction "2_2") (pintype "passive"))
      (node (ref "R407") (pin "2") (pinfunction "2_2") (pintype "passive"))
      (node (ref "R409") (pin "2") (pinfunction "2_2") (pintype "passive"))
      (node (ref "R414") (pin "2") (pinfunction "2_2") (pintype "passive"))
      (node (ref "R425") (pin "1") (pinfunction "1_1") (pintype "passive"))
      (node (ref "R483") (pin "2") (pinfunction "2_2") (pintype "passive"))
      (node (ref "R506") (pin "1") (pinfunction "1_1") (pintype "passive"))
      (node (ref "R507") (pin "1") (pinfunction "1_1") (pintype "passive"))
      (node (ref "TP56") (pin "P$1") (pinfunction "TP_P$1") (pintype "input"))
    )
    (net (code "52") (name "12V_SUPPLY_EN_3V3") (class "Default")
      (node (ref "C46") (pin "1") (pinfunction "1_1") (pintype "passive"))
      (node (ref "IC10") (pin "2") (pinfunction "EN_2") (pintype "input"))
      (node (ref "R194") (pin "2") (pinfunction "2_2") (pintype "passive"))
      (node (ref "R195") (pin "1") (pinfunction "1_1") (pintype "passive"))
    )
    (net (code "53") (name "AUDIO_AMP_LRCLK_1V8") (class "Default")
      (node (ref "IC24") (pin "6") (pinfunction "LRCLK_6") (pintype "input"))
      (node (ref "IC55") (pin "7") (pinfunction "DB_7") (pintype "passive"))
      (node (ref "R285") (pin "2") (pinfunction "2_2") (pintype "passive"))
    )
    (net (code "54") (name "AUDIO_AMP_SCLK_1V8") (class "Default")
      (node (ref "IC24") (pin "7") (pinfunction "SCLK_7") (pintype "input"))
      (node (ref "IC55") (pin "6") (pinfunction "DA_6") (pintype "passive"))
      (node (ref "R337") (pin "2") (pinfunction "2_2") (pintype "passive"))
    )
    (net (code "55") (name "AUDIO_JETSON_LRCLK_1V8") (class "Default")
      (node (ref "IC55") (pin "11") (pinfunction "S1B_11") (pintype "passive"))
      (node (ref "R141") (pin "2") (pinfunction "2_2") (pintype "passive"))
    )
    (net (code "56") (name "AUDIO_JETSON_SCLK_1V8") (class "Default")
      (node (ref "IC55") (pin "2") (pinfunction "S1A_2") (pintype "passive"))
      (node (ref "R142") (pin "2") (pinfunction "2_2") (pintype "passive"))
    )
    (net (code "57") (name "AUDIO_SD_AMP->MUX_1V8") (class "Default")
      (node (ref "IC54") (pin "6") (pinfunction "DA_6") (pintype "passive"))
      (node (ref "R284") (pin "1") (pinfunction "1_1") (pintype "passive"))
      (node (ref "R39") (pin "2") (pinfunction "2_2") (pintype "passive"))
    )
    (net (code "58") (name "AUDIO_SD_JETSON->MUX_1V8") (class "Default")
      (node (ref "IC54") (pin "11") (pinfunction "S1B_11") (pintype "passive"))
      (node (ref "R94") (pin "2") (pinfunction "2_2") (pintype "passive"))
    )
    (net (code "59") (name "AUDIO_SD_MUX->AMP_1V8") (class "Default")
      (node (ref "IC24") (pin "8") (pinfunction "SDIN_8") (pintype "input"))
      (node (ref "IC54") (pin "7") (pinfunction "DB_7") (pintype "passive"))
      (node (ref "R336") (pin "2") (pinfunction "2_2") (pintype "passive"))
    )
    (net (code "60") (name "AUDIO_SD_MUX->JETSON_1V8") (class "Default")
      (node (ref "IC54") (pin "2") (pinfunction "S1A_2") (pintype "passive"))
      (node (ref "MOD1") (pin "195") (pinfunction "I2S0_DIN_195") (pintype "input"))
    )
    (net (code "61") (name "AUDIO_SD_UC->MUX_1V8") (class "Default")
      (node (ref "IC54") (pin "10") (pinfunction "S2B_10") (pintype "passive"))
      (node (ref "R21") (pin "1") (pinfunction "1_1") (pintype "passive"))
    )
    (net (code "62") (name "AUDIO_SD_UC->MUX_3V3") (class "Default")
      (node (ref "IC11") (pin "16") (pinfunction "B6_16") (pintype "bidirectional"))
      (node (ref "R53") (pin "1") (pinfunction "1_1") (pintype "passive"))
    )
    (net (code "63") (name "AUDIO_UC_LRCLK_1V8") (class "Default")
      (node (ref "IC55") (pin "10") (pinfunction "S2B_10") (pintype "passive"))
      (node (ref "R23") (pin "1") (pinfunction "1_1") (pintype "passive"))
    )
    (net (code "64") (name "AUDIO_UC_LRCLK_3V3") (class "Default")
      (node (ref "IC11") (pin "14") (pinfunction "B8_14") (pintype "bidirectional"))
      (node (ref "R55") (pin "1") (pinfunction "1_1") (pintype "passive"))
    )
    (net (code "65") (name "AUDIO_UC_SCLK_1V8") (class "Default")
      (node (ref "IC55") (pin "3") (pinfunction "S2A_3") (pintype "passive"))
      (node (ref "R22") (pin "1") (pinfunction "1_1") (pintype "passive"))
    )
    (net (code "66") (name "AUDIO_UC_SCLK_3V3") (class "Default")
      (node (ref "IC11") (pin "15") (pinfunction "B7_15") (pintype "bidirectional"))
      (node (ref "R54") (pin "1") (pinfunction "1_1") (pintype "passive"))
    )
    (net (code "67") (name "AX200_DISABLE_BT_1V8") (class "Default")
      (node (ref "MOD1") (pin "126") (pinfunction "GPIO03/I2S2_DIN_126") (pintype "bidirectional"))
      (node (ref "R169") (pin "1") (pinfunction "1_1") (pintype "passive"))
    )
    (net (code "68") (name "AX200_DISABLE_WIFI_1V8") (class "Default")
      (node (ref "MOD1") (pin "128") (pinfunction "GPIO05/I2S2_SCLK_128") (pintype "bidirectional"))
      (node (ref "R172") (pin "1") (pinfunction "1_1") (pintype "passive"))
    )
    (net (code "69") (name "AX200_USB_D_N") (class "Default")
      (node (ref "IC19") (pin "8") (pinfunction "USBDM_DN4/PRT_DIS_M4_8") (pintype "bidirectional"))
      (node (ref "R166") (pin "1") (pinfunction "1_1") (pintype "passive"))
    )
    (net (code "70") (name "AX200_USB_D_P") (class "Default")
      (node (ref "IC19") (pin "9") (pinfunction "USBDP_DN4/PRT_DIS_P4_9") (pintype "bidirectional"))
      (node (ref "R168") (pin "1") (pinfunction "1_1") (pintype "passive"))
    )
    (net (code "71") (name "BQ24640_VREF") (class "Default")
      (node (ref "C171") (pin "1") (pinfunction "1_1") (pintype "passive"))
      (node (ref "D21") (pin "A") (pinfunction "A_A") (pintype "passive"))
      (node (ref "D22") (pin "A") (pinfunction "A_A") (pintype "passive"))
      (node (ref "IC35") (pin "6") (pinfunction "VREF_6") (pintype "output"))
      (node (ref "R371") (pin "2") (pinfunction "2_2") (pintype "passive"))
      (node (ref "R375") (pin "2") (pinfunction "2_2") (pintype "passive"))
    )
    (net (code "72") (name "CAM0_CLK_N") (class "Default")
      (node (ref "MOD1") (pin "10") (pinfunction "CSI0_CLK_N_10") (pintype "input"))
      (node (ref "X25") (pin "15") (pinfunction "15_15") (pintype "passive"))
    )
    (net (code "73") (name "CAM0_CLK_P") (class "Default")
      (node (ref "MOD1") (pin "12") (pinfunction "CSI0_CLK_P_12") (pintype "input"))
      (node (ref "X25") (pin "14") (pinfunction "14_14") (pintype "passive"))
    )
    (net (code "74") (name "CAM0_D0_N") (class "Default")
      (node (ref "MOD1") (pin "4") (pinfunction "CSI0_D0_N_4") (pintype "input"))
      (node (ref "X25") (pin "21") (pinfunction "21_21") (pintype "passive"))
    )
    (net (code "75") (name "CAM0_D0_P") (class "Default")
      (node (ref "MOD1") (pin "6") (pinfunction "CSI0_D0_P_6") (pintype "input"))
      (node (ref "X25") (pin "20") (pinfunction "20_20") (pintype "passive"))
    )
    (net (code "76") (name "CAM0_D1_N") (class "Default")
      (node (ref "MOD1") (pin "16") (pinfunction "CSI0_D1_N_16") (pintype "input"))
      (node (ref "X25") (pin "18") (pinfunction "18_18") (pintype "passive"))
    )
    (net (code "77") (name "CAM0_D1_P") (class "Default")
      (node (ref "MOD1") (pin "18") (pinfunction "CSI0_D1_P_18") (pintype "input"))
      (node (ref "X25") (pin "17") (pinfunction "17_17") (pintype "passive"))
    )
    (net (code "78") (name "CAM0_I2C_SCL_3V3") (class "Default")
      (node (ref "IC30") (pin "2") (pinfunction "S1A_2") (pintype "passive"))
      (node (ref "R181") (pin "1") (pinfunction "1_1") (pintype "passive"))
      (node (ref "X25") (pin "3") (pinfunction "3_3") (pintype "passive"))
    )
    (net (code "79") (name "CAM0_I2C_SDA_3V3") (class "Default")
      (node (ref "IC30") (pin "11") (pinfunction "S1B_11") (pintype "passive"))
      (node (ref "R189") (pin "1") (pinfunction "1_1") (pintype "passive"))
      (node (ref "X25") (pin "2") (pinfunction "2_2") (pintype "passive"))
    )
    (net (code "80") (name "CAM1_CLK_N") (class "Default")
      (node (ref "MOD1") (pin "28") (pinfunction "CSI2_CLK_N_28") (pintype "input"))
      (node (ref "X13") (pin "9") (pinfunction "9_9") (pintype "passive"))
    )
    (net (code "81") (name "CAM1_CLK_P") (class "Default")
      (node (ref "MOD1") (pin "30") (pinfunction "CSI2_CLK_P_30") (pintype "input"))
      (node (ref "X13") (pin "11") (pinfunction "11_11") (pintype "passive"))
    )
    (net (code "82") (name "CAM1_D0_N") (class "Default")
      (node (ref "MOD1") (pin "22") (pinfunction "CSI2_D0_N_22") (pintype "input"))
      (node (ref "X13") (pin "3") (pinfunction "3_3") (pintype "passive"))
    )
    (net (code "83") (name "CAM1_D0_P") (class "Default")
      (node (ref "MOD1") (pin "24") (pinfunction "CSI2_D0_P_24") (pintype "input"))
      (node (ref "X13") (pin "5") (pinfunction "5_5") (pintype "passive"))
    )
    (net (code "84") (name "CAM1_D1_N") (class "Default")
      (node (ref "MOD1") (pin "34") (pinfunction "CSI2_D1_N_34") (pintype "input"))
      (node (ref "X13") (pin "15") (pinfunction "15_15") (pintype "passive"))
    )
    (net (code "85") (name "CAM1_D1_P") (class "Default")
      (node (ref "MOD1") (pin "36") (pinfunction "CSI2_D1_P_36") (pintype "input"))
      (node (ref "X13") (pin "17") (pinfunction "17_17") (pintype "passive"))
    )
    (net (code "86") (name "CAM1_I2C_SCL_1V8") (class "Default")
      (node (ref "R1") (pin "1") (pinfunction "1_1") (pintype "passive"))
      (node (ref "T32") (pin "2") (pinfunction "S_2") (pintype "passive"))
      (node (ref "X13") (pin "35") (pinfunction "35_35") (pintype "passive"))
    )
    (net (code "87") (name "CAM1_I2C_SCL_3V3") (class "Default")
      (node (ref "IC30") (pin "3") (pinfunction "S2A_3") (pintype "passive"))
      (node (ref "R184") (pin "1") (pinfunction "1_1") (pintype "passive"))
      (node (ref "T32") (pin "3") (pinfunction "D_3") (pintype "passive"))
    )
    (net (code "88") (name "CAM1_I2C_SDA_1V8") (class "Default")
      (node (ref "R44") (pin "1") (pinfunction "1_1") (pintype "passive"))
      (node (ref "T48") (pin "2") (pinfunction "S_2") (pintype "passive"))
      (node (ref "X13") (pin "33") (pinfunction "33_33") (pintype "passive"))
    )
    (net (code "89") (name "CAM1_I2C_SDA_3V3") (class "Default")
      (node (ref "IC30") (pin "10") (pinfunction "S2B_10") (pintype "passive"))
      (node (ref "R222") (pin "1") (pinfunction "1_1") (pintype "passive"))
      (node (ref "T48") (pin "3") (pinfunction "D_3") (pintype "passive"))
    )
    (net (code "90") (name "CAM1_MCLK_1V8") (class "Default")
      (node (ref "R114") (pin "2") (pinfunction "2_2") (pintype "passive"))
      (node (ref "X13") (pin "53") (pinfunction "53_53") (pintype "passive"))
    )
    (net (code "91") (name "CAM1_PWDN_1V8") (class "Default")
      (node (ref "R115") (pin "2") (pinfunction "2_2") (pintype "passive"))
      (node (ref "X13") (pin "51") (pinfunction "51_51") (pintype "passive"))
    )
    (net (code "92") (name "CAM2_CLK_N") (class "Default")
      (node (ref "MOD1") (pin "52") (pinfunction "CSI4_CLK_N_52") (pintype "input"))
      (node (ref "X13") (pin "27") (pinfunction "27_27") (pintype "passive"))
    )
    (net (code "93") (name "CAM2_CLK_P") (class "Default")
      (node (ref "MOD1") (pin "54") (pinfunction "CSI4_CLK_P_54") (pintype "input"))
      (node (ref "X13") (pin "29") (pinfunction "29_29") (pintype "passive"))
    )
    (net (code "94") (name "CAM2_D0_N") (class "Default")
      (node (ref "MOD1") (pin "46") (pinfunction "CSI4_D0_N_46") (pintype "input"))
      (node (ref "X13") (pin "21") (pinfunction "21_21") (pintype "passive"))
    )
    (net (code "95") (name "CAM2_D0_P") (class "Default")
      (node (ref "MOD1") (pin "48") (pinfunction "CSI4_D0_P_48") (pintype "input"))
      (node (ref "X13") (pin "23") (pinfunction "23_23") (pintype "passive"))
    )
    (net (code "96") (name "CAM2_I2C_SCL_3V3") (class "Default")
      (node (ref "IC30") (pin "4") (pinfunction "S3A_4") (pintype "passive"))
      (node (ref "R188") (pin "1") (pinfunction "1_1") (pintype "passive"))
      (node (ref "X13") (pin "30") (pinfunction "30_30") (pintype "passive"))
    )
    (net (code "97") (name "CAM2_I2C_SDA_3V3") (class "Default")
      (node (ref "IC30") (pin "9") (pinfunction "S3B_9") (pintype "passive"))
      (node (ref "R223") (pin "1") (pinfunction "1_1") (pintype "passive"))
      (node (ref "X13") (pin "28") (pinfunction "28_28") (pintype "passive"))
    )
    (net (code "98") (name "CAM3_CLK_N") (class "Default")
      (node (ref "MOD1") (pin "27") (pinfunction "CSI3_CLK_N_27") (pintype "input"))
      (node (ref "X13") (pin "10") (pinfunction "10_10") (pintype "passive"))
    )
    (net (code "99") (name "CAM3_CLK_P") (class "Default")
      (node (ref "MOD1") (pin "29") (pinfunction "CSI3_CLK_P_29") (pintype "input"))
      (node (ref "X13") (pin "12") (pinfunction "12_12") (pintype "passive"))
    )
    (net (code "100") (name "CAM3_D0_N") (class "Default")
      (node (ref "MOD1") (pin "21") (pinfunction "CSI3_D0_N_21") (pintype "input"))
      (node (ref "X13") (pin "4") (pinfunction "4_4") (pintype "passive"))
    )
    (net (code "101") (name "CAM3_D0_P") (class "Default")
      (node (ref "MOD1") (pin "23") (pinfunction "CSI3_D0_P_23") (pintype "input"))
      (node (ref "X13") (pin "6") (pinfunction "6_6") (pintype "passive"))
    )
    (net (code "102") (name "CAM3_D1_N") (class "Default")
      (node (ref "MOD1") (pin "33") (pinfunction "CSI3_D1_N_33") (pintype "input"))
      (node (ref "X13") (pin "16") (pinfunction "16_16") (pintype "passive"))
    )
    (net (code "103") (name "CAM3_D1_P") (class "Default")
      (node (ref "MOD1") (pin "35") (pinfunction "CSI3_D1_P_35") (pintype "input"))
      (node (ref "X13") (pin "18") (pinfunction "18_18") (pintype "passive"))
    )
    (net (code "104") (name "CAM3_I2C_SCL_1V8") (class "Default")
      (node (ref "R204") (pin "1") (pinfunction "1_1") (pintype "passive"))
      (node (ref "T13") (pin "2") (pinfunction "S_2") (pintype "passive"))
      (node (ref "X13") (pin "41") (pinfunction "41_41") (pintype "passive"))
    )
    (net (code "105") (name "CAM3_I2C_SCL_3V3") (class "Default")
      (node (ref "IC30") (pin "5") (pinfunction "S4A_5") (pintype "passive"))
      (node (ref "R224") (pin "1") (pinfunction "1_1") (pintype "passive"))
      (node (ref "T13") (pin "3") (pinfunction "D_3") (pintype "passive"))
    )
    (net (code "106") (name "CAM3_I2C_SDA_1V8") (class "Default")
      (node (ref "R205") (pin "1") (pinfunction "1_1") (pintype "passive"))
      (node (ref "T14") (pin "2") (pinfunction "S_2") (pintype "passive"))
      (node (ref "X13") (pin "39") (pinfunction "39_39") (pintype "passive"))
    )
    (net (code "107") (name "CAM3_I2C_SDA_3V3") (class "Default")
      (node (ref "IC30") (pin "8") (pinfunction "S4B_8") (pintype "passive"))
      (node (ref "R225") (pin "1") (pinfunction "1_1") (pintype "passive"))
      (node (ref "T14") (pin "3") (pinfunction "D_3") (pintype "passive"))
    )
    (net (code "108") (name "CAM3_MCLK_1V8") (class "Default")
      (node (ref "R443") (pin "2") (pinfunction "2_2") (pintype "passive"))
      (node (ref "X13") (pin "47") (pinfunction "47_47") (pintype "passive"))
    )
    (net (code "109") (name "CAM3_PWDN_1V8") (class "Default")
      (node (ref "R442") (pin "2") (pinfunction "2_2") (pintype "passive"))
      (node (ref "X13") (pin "45") (pinfunction "45_45") (pintype "passive"))
    )
    (net (code "110") (name "COM1") (class "Default")
      (node (ref "D24") (pin "2") (pinfunction "A2_2") (pintype "passive"))
      (node (ref "D6") (pin "2") (pinfunction "A2_2") (pintype "passive"))
      (node (ref "R232") (pin "2") (pinfunction "2_2") (pintype "passive"))
      (node (ref "R440") (pin "1") (pinfunction "1_1") (pintype "passive"))
      (node (ref "R471") (pin "1") (pinfunction "1_1") (pintype "passive"))
      (node (ref "R472") (pin "1") (pinfunction "1_1") (pintype "passive"))
      (node (ref "R474") (pin "1") (pinfunction "1_1") (pintype "passive"))
      (node (ref "TP54") (pin "P$1") (pinfunction "TP_P$1") (pintype "input"))
    )
    (net (code "111") (name "COM2_RX") (class "Default")
      (node (ref "MOD1") (pin "101") (pinfunction "UART0_RXD_101") (pintype "input"))
      (node (ref "R247") (pin "1") (pinfunction "1_1") (pintype "passive"))
    )
    (net (code "112") (name "COM2_TX") (class "Default")
      (node (ref "R248") (pin "1") (pinfunction "1_1") (pintype "passive"))
      (node (ref "R516") (pin "1") (pinfunction "1_1") (pintype "passive"))
    )
    (net (code "113") (name "EXT_UC_NRST_3V3") (class "Default")
      (node (ref "IC6") (pin "6") (pinfunction "I/O4_6") (pintype "passive"))
      (node (ref "R67") (pin "2") (pinfunction "2_2") (pintype "passive"))
      (node (ref "X21") (pin "3") (pinfunction "~{RST}_3") (pintype "output"))
      (node (ref "X6") (pin "3") (pinfunction "~{RST}_3") (pintype "output"))
    )
    (net (code "114") (name "EXT_UC_SWCLK_3V3") (class "Default")
      (node (ref "IC6") (pin "3") (pinfunction "I/O2_3") (pintype "passive"))
      (node (ref "R68") (pin "2") (pinfunction "2_2") (pintype "passive"))
      (node (ref "X21") (pin "4") (pinfunction "SWCLK/TCK_4") (pintype "output"))
      (node (ref "X6") (pin "4") (pinfunction "SWCLK/TCK_4") (pintype "output"))
    )
    (net (code "115") (name "EXT_UC_SWDIO_3V3") (class "Default")
      (node (ref "IC6") (pin "1") (pinfunction "I/O1_1") (pintype "passive"))
      (node (ref "R69") (pin "2") (pinfunction "2_2") (pintype "passive"))
      (node (ref "X21") (pin "2") (pinfunction "SWDIO/TMS_2") (pintype "bidirectional"))
      (node (ref "X6") (pin "2") (pinfunction "SWDIO/TMS_2") (pintype "bidirectional"))
    )
    (net (code "116") (name "EXT_UC_SWO_3V3") (class "Default")
      (node (ref "IC6") (pin "4") (pinfunction "I/O3_4") (pintype "passive"))
      (node (ref "R96") (pin "2") (pinfunction "2_2") (pintype "passive"))
      (node (ref "X21") (pin "6") (pinfunction "SWO/TDO_6") (pintype "input"))
      (node (ref "X6") (pin "6") (pinfunction "SWO/TDO_6") (pintype "input"))
    )
    (net (code "117") (name "FAN_AUX_PWM_5V") (class "Default")
      (node (ref "IC57") (pin "6") (pinfunction "I/O4_6") (pintype "passive"))
      (node (ref "R537") (pin "2") (pinfunction "2_2") (pintype "passive"))
      (node (ref "TP74") (pin "P$1") (pinfunction "TP_P$1") (pintype "input"))
      (node (ref "X1") (pin "4") (pinfunction "4_4") (pintype "input"))
    )
    (net (code "118") (name "FAN_AUX_TACH_5V") (class "Default")
      (node (ref "IC57") (pin "4") (pinfunction "I/O3_4") (pintype "passive"))
      (node (ref "R536") (pin "1") (pinfunction "1_1") (pintype "passive"))
      (node (ref "TP75") (pin "P$1") (pinfunction "TP_P$1") (pintype "input"))
      (node (ref "X1") (pin "3") (pinfunction "3_3") (pintype "output"))
    )
    (net (code "119") (name "FAN_MAIN_PWM_5V") (class "Default")
      (node (ref "IC57") (pin "3") (pinfunction "I/O2_3") (pintype "passive"))
      (node (ref "R119") (pin "2") (pinfunction "2_2") (pintype "passive"))
      (node (ref "TP76") (pin "P$1") (pinfunction "TP_P$1") (pintype "input"))
      (node (ref "X10") (pin "4") (pinfunction "4_4") (pintype "input"))
    )
    (net (code "120") (name "FAN_MAIN_TACH_5V") (class "Default")
      (node (ref "IC57") (pin "1") (pinfunction "I/O1_1") (pintype "passive"))
      (node (ref "R117") (pin "1") (pinfunction "1_1") (pintype "passive"))
      (node (ref "TP77") (pin "P$1") (pinfunction "TP_P$1") (pintype "input"))
      (node (ref "X10") (pin "3") (pinfunction "3_3") (pintype "output"))
    )
    (net (code "121") (name "FU_IR_ADC") (class "Default")
      (node (ref "C229") (pin "1") (pinfunction "1_1") (pintype "passive"))
      (node (ref "R208") (pin "1") (pinfunction "1_1") (pintype "passive"))
      (node (ref "R470") (pin "1") (pinfunction "1_1") (pintype "passive"))
      (node (ref "X13") (pin "89") (pinfunction "89_89") (pintype "passive"))
    )
    (net (code "122") (name "FU_OPT_1") (class "Default")
      (node (ref "X13") (pin "75") (pinfunction "75_75") (pintype "passive"))
      (node (ref "X4") (pin "10") (pinfunction "10_10") (pintype "passive"))
    )
    (net (code "123") (name "FU_PVCC_EN_3V3") (class "Default")
      (node (ref "R415") (pin "2") (pinfunction "2_2") (pintype "passive"))
      (node (ref "T56") (pin "1") (pinfunction "G_1") (pintype "passive"))
      (node (ref "T66") (pin "1") (pinfunction "G_1") (pintype "passive"))
      (node (ref "TP64") (pin "P$1") (pinfunction "TP_P$1") (pintype "input"))
      (node (ref "X13") (pin "73") (pinfunction "73_73") (pintype "passive"))
    )
    (net (code "124") (name "GND") (class "Default")
      (node (ref "BAT1") (pin "-") (pinfunction "-_-") (pintype "passive"))
      (node (ref "C1") (pin "2") (pinfunction "2_2") (pintype "passive"))
      (node (ref "C10") (pin "2") (pinfunction "2_2") (pintype "passive"))
      (node (ref "C100") (pin "2") (pinfunction "2_2") (pintype "passive"))
      (node (ref "C101") (pin "2") (pinfunction "2_2") (pintype "passive"))
      (node (ref "C102") (pin "2") (pinfunction "2_2") (pintype "passive"))
      (node (ref "C103") (pin "2") (pinfunction "2_2") (pintype "passive"))
      (node (ref "C104") (pin "2") (pinfunction "2_2") (pintype "passive"))
      (node (ref "C105") (pin "2") (pinfunction "2_2") (pintype "passive"))
      (node (ref "C106") (pin "2") (pinfunction "2_2") (pintype "passive"))
      (node (ref "C109") (pin "2") (pinfunction "2_2") (pintype "passive"))
      (node (ref "C11") (pin "2") (pinfunction "2_2") (pintype "passive"))
      (node (ref "C110") (pin "2") (pinfunction "2_2") (pintype "passive"))
      (node (ref "C111") (pin "2") (pinfunction "2_2") (pintype "passive"))
      (node (ref "C112") (pin "2") (pinfunction "2_2") (pintype "passive"))
      (node (ref "C113") (pin "2") (pinfunction "2_2") (pintype "passive"))
      (node (ref "C114") (pin "2") (pinfunction "2_2") (pintype "passive"))
      (node (ref "C115") (pin "-") (pinfunction "-_-") (pintype "passive"))
      (node (ref "C116") (pin "2") (pinfunction "2_2") (pintype "passive"))
      (node (ref "C117") (pin "-") (pinfunction "-_-") (pintype "passive"))
      (node (ref "C118") (pin "-") (pinfunction "-_-") (pintype "passive"))
      (node (ref "C119") (pin "2") (pinfunction "2_2") (pintype "passive"))
      (node (ref "C120") (pin "2") (pinfunction "2_2") (pintype "passive"))
      (node (ref "C125") (pin "2") (pinfunction "2_2") (pintype "passive"))
      (node (ref "C126") (pin "2") (pinfunction "2_2") (pintype "passive"))
      (node (ref "C127") (pin "2") (pinfunction "2_2") (pintype "passive"))
      (node (ref "C128") (pin "2") (pinfunction "2_2") (pintype "passive"))
      (node (ref "C129") (pin "2") (pinfunction "2_2") (pintype "passive"))
      (node (ref "C13") (pin "2") (pinfunction "2_2") (pintype "passive"))
      (node (ref "C130") (pin "2") (pinfunction "2_2") (pintype "passive"))
      (node (ref "C131") (pin "2") (pinfunction "2_2") (pintype "passive"))
      (node (ref "C132") (pin "2") (pinfunction "2_2") (pintype "passive"))
      (node (ref "C134") (pin "2") (pinfunction "2_2") (pintype "passive"))
      (node (ref "C136") (pin "2") (pinfunction "2_2") (pintype "passive"))
      (node (ref "C137") (pin "2") (pinfunction "2_2") (pintype "passive"))
      (node (ref "C14") (pin "2") (pinfunction "2_2") (pintype "passive"))
      (node (ref "C140") (pin "2") (pinfunction "2_2") (pintype "passive"))
      (node (ref "C141") (pin "2") (pinfunction "2_2") (pintype "passive"))
      (node (ref "C142") (pin "2") (pinfunction "2_2") (pintype "passive"))
      (node (ref "C143") (pin "2") (pinfunction "2_2") (pintype "passive"))
      (node (ref "C146") (pin "2") (pinfunction "2_2") (pintype "passive"))
      (node (ref "C147") (pin "2") (pinfunction "2_2") (pintype "passive"))
      (node (ref "C148") (pin "-") (pinfunction "-_-") (pintype "passive"))
      (node (ref "C149") (pin "2") (pinfunction "2_2") (pintype "passive"))
      (node (ref "C15") (pin "2") (pinfunction "2_2") (pintype "passive"))
      (node (ref "C151") (pin "2") (pinfunction "2_2") (pintype "passive"))
      (node (ref "C152") (pin "2") (pinfunction "2_2") (pintype "passive"))
      (node (ref "C153") (pin "2") (pinfunction "2_2") (pintype "passive"))
      (node (ref "C154") (pin "2") (pinfunction "2_2") (pintype "passive"))
      (node (ref "C155") (pin "2") (pinfunction "2_2") (pintype "passive"))
      (node (ref "C156") (pin "2") (pinfunction "2_2") (pintype "passive"))
      (node (ref "C157") (pin "1") (pinfunction "1_1") (pintype "passive"))
      (node (ref "C158") (pin "1") (pinfunction "1_1") (pintype "passive"))
      (node (ref "C159") (pin "1") (pinfunction "1_1") (pintype "passive"))
      (node (ref "C16") (pin "2") (pinfunction "2_2") (pintype "passive"))
      (node (ref "C160") (pin "1") (pinfunction "1_1") (pintype "passive"))
      (node (ref "C161") (pin "1") (pinfunction "1_1") (pintype "passive"))
      (node (ref "C162") (pin "2") (pinfunction "2_2") (pintype "passive"))
      (node (ref "C163") (pin "1") (pinfunction "1_1") (pintype "passive"))
      (node (ref "C164") (pin "1") (pinfunction "1_1") (pintype "passive"))
      (node (ref "C165") (pin "2") (pinfunction "2_2") (pintype "passive"))
      (node (ref "C166") (pin "2") (pinfunction "2_2") (pintype "passive"))
      (node (ref "C169") (pin "2") (pinfunction "2_2") (pintype "passive"))
      (node (ref "C17") (pin "2") (pinfunction "2_2") (pintype "passive"))
      (node (ref "C170") (pin "2") (pinfunction "2_2") (pintype "passive"))
      (node (ref "C171") (pin "2") (pinfunction "2_2") (pintype "passive"))
      (node (ref "C172") (pin "2") (pinfunction "2_2") (pintype "passive"))
      (node (ref "C178") (pin "-") (pinfunction "-_-") (pintype "passive"))
      (node (ref "C179") (pin "2") (pinfunction "2_2") (pintype "passive"))
      (node (ref "C18") (pin "2") (pinfunction "2_2") (pintype "passive"))
      (node (ref "C180") (pin "2") (pinfunction "2_2") (pintype "passive"))
      (node (ref "C181") (pin "2") (pinfunction "2_2") (pintype "passive"))
      (node (ref "C182") (pin "2") (pinfunction "2_2") (pintype "passive"))
      (node (ref "C183") (pin "2") (pinfunction "2_2") (pintype "passive"))
      (node (ref "C184") (pin "2") (pinfunction "2_2") (pintype "passive"))
      (node (ref "C185") (pin "2") (pinfunction "2_2") (pintype "passive"))
      (node (ref "C187") (pin "2") (pinfunction "2_2") (pintype "passive"))
      (node (ref "C188") (pin "2") (pinfunction "2_2") (pintype "passive"))
      (node (ref "C189") (pin "2") (pinfunction "2_2") (pintype "passive"))
      (node (ref "C19") (pin "-") (pinfunction "-_-") (pintype "passive"))
      (node (ref "C190") (pin "2") (pinfunction "2_2") (pintype "passive"))
      (node (ref "C191") (pin "2") (pinfunction "2_2") (pintype "passive"))
      (node (ref "C192") (pin "2") (pinfunction "2_2") (pintype "passive"))
      (node (ref "C193") (pin "2") (pinfunction "2_2") (pintype "passive"))
      (node (ref "C194") (pin "2") (pinfunction "2_2") (pintype "passive"))
      (node (ref "C195") (pin "-") (pinfunction "-_-") (pintype "passive"))
      (node (ref "C196") (pin "2") (pinfunction "2_2") (pintype "passive"))
      (node (ref "C2") (pin "2") (pinfunction "2_2") (pintype "passive"))
      (node (ref "C20") (pin "2") (pinfunction "2_2") (pintype "passive"))
      (node (ref "C201") (pin "2") (pinfunction "2_2") (pintype "passive"))
      (node (ref "C202") (pin "2") (pinfunction "2_2") (pintype "passive"))
      (node (ref "C203") (pin "2") (pinfunction "2_2") (pintype "passive"))
      (node (ref "C205") (pin "2") (pinfunction "2_2") (pintype "passive"))
      (node (ref "C206") (pin "2") (pinfunction "2_2") (pintype "passive"))
      (node (ref "C208") (pin "2") (pinfunction "2_2") (pintype "passive"))
      (node (ref "C209") (pin "2") (pinfunction "2_2") (pintype "passive"))
      (node (ref "C21") (pin "2") (pinfunction "2_2") (pintype "passive"))
      (node (ref "C210") (pin "2") (pinfunction "2_2") (pintype "passive"))
      (node (ref "C211") (pin "2") (pinfunction "2_2") (pintype "passive"))
      (node (ref "C213") (pin "2") (pinfunction "2_2") (pintype "passive"))
      (node (ref "C214") (pin "2") (pinfunction "2_2") (pintype "passive"))
      (node (ref "C215") (pin "2") (pinfunction "2_2") (pintype "passive"))
      (node (ref "C216") (pin "2") (pinfunction "2_2") (pintype "passive"))
      (node (ref "C217") (pin "2") (pinfunction "2_2") (pintype "passive"))
      (node (ref "C218") (pin "2") (pinfunction "2_2") (pintype "passive"))
      (node (ref "C219") (pin "2") (pinfunction "2_2") (pintype "passive"))
      (node (ref "C22") (pin "2") (pinfunction "2_2") (pintype "passive"))
      (node (ref "C220") (pin "2") (pinfunction "2_2") (pintype "passive"))
      (node (ref "C222") (pin "2") (pinfunction "2_2") (pintype "passive"))
      (node (ref "C223") (pin "2") (pinfunction "2_2") (pintype "passive"))
      (node (ref "C224") (pin "2") (pinfunction "2_2") (pintype "passive"))
      (node (ref "C225") (pin "2") (pinfunction "2_2") (pintype "passive"))
      (node (ref "C226") (pin "2") (pinfunction "2_2") (pintype "passive"))
      (node (ref "C227") (pin "2") (pinfunction "2_2") (pintype "passive"))
      (node (ref "C228") (pin "2") (pinfunction "2_2") (pintype "passive"))
      (node (ref "C229") (pin "2") (pinfunction "2_2") (pintype "passive"))
      (node (ref "C23") (pin "2") (pinfunction "2_2") (pintype "passive"))
      (node (ref "C230") (pin "2") (pinfunction "2_2") (pintype "passive"))
      (node (ref "C231") (pin "2") (pinfunction "2_2") (pintype "passive"))
      (node (ref "C233") (pin "2") (pinfunction "2_2") (pintype "passive"))
      (node (ref "C235") (pin "2") (pinfunction "2_2") (pintype "passive"))
      (node (ref "C236") (pin "2") (pinfunction "2_2") (pintype "passive"))
      (node (ref "C24") (pin "2") (pinfunction "2_2") (pintype "passive"))
      (node (ref "C246") (pin "2") (pinfunction "2_2") (pintype "passive"))
      (node (ref "C25") (pin "2") (pinfunction "2_2") (pintype "passive"))
      (node (ref "C255") (pin "2") (pinfunction "2_2") (pintype "passive"))
      (node (ref "C256") (pin "2") (pinfunction "2_2") (pintype "passive"))
      (node (ref "C257") (pin "2") (pinfunction "2_2") (pintype "passive"))
      (node (ref "C258") (pin "2") (pinfunction "2_2") (pintype "passive"))
      (node (ref "C259") (pin "2") (pinfunction "2_2") (pintype "passive"))
      (node (ref "C26") (pin "2") (pinfunction "2_2") (pintype "passive"))
      (node (ref "C261") (pin "2") (pinfunction "2_2") (pintype "passive"))
      (node (ref "C262") (pin "2") (pinfunction "2_2") (pintype "passive"))
      (node (ref "C264") (pin "2") (pinfunction "2_2") (pintype "passive"))
      (node (ref "C268") (pin "2") (pinfunction "2_2") (pintype "passive"))
      (node (ref "C269") (pin "2") (pinfunction "2_2") (pintype "passive"))
      (node (ref "C27") (pin "2") (pinfunction "2_2") (pintype "passive"))
      (node (ref "C272") (pin "2") (pinfunction "2_2") (pintype "passive"))
      (node (ref "C273") (pin "2") (pinfunction "2_2") (pintype "passive"))
      (node (ref "C275") (pin "2") (pinfunction "2_2") (pintype "passive"))
      (node (ref "C276") (pin "2") (pinfunction "2_2") (pintype "passive"))
      (node (ref "C277") (pin "2") (pinfunction "2_2") (pintype "passive"))
      (node (ref "C278") (pin "2") (pinfunction "2_2") (pintype "passive"))
      (node (ref "C28") (pin "2") (pinfunction "2_2") (pintype "passive"))
      (node (ref "C280") (pin "2") (pinfunction "2_2") (pintype "passive"))
      (node (ref "C282") (pin "2") (pinfunction "2_2") (pintype "passive"))
      (node (ref "C284") (pin "2") (pinfunction "2_2") (pintype "passive"))
      (node (ref "C285") (pin "2") (pinfunction "2_2") (pintype "passive"))
      (node (ref "C287") (pin "2") (pinfunction "2_2") (pintype "passive"))
      (node (ref "C288") (pin "2") (pinfunction "2_2") (pintype "passive"))
      (node (ref "C29") (pin "2") (pinfunction "2_2") (pintype "passive"))
      (node (ref "C290") (pin "2") (pinfunction "2_2") (pintype "passive"))
      (node (ref "C291") (pin "2") (pinfunction "2_2") (pintype "passive"))
      (node (ref "C292") (pin "2") (pinfunction "2_2") (pintype "passive"))
      (node (ref "C294") (pin "2") (pinfunction "2_2") (pintype "passive"))
      (node (ref "C295") (pin "2") (pinfunction "2_2") (pintype "passive"))
      (node (ref "C296") (pin "2") (pinfunction "2_2") (pintype "passive"))
      (node (ref "C297") (pin "2") (pinfunction "2_2") (pintype "passive"))
      (node (ref "C298") (pin "2") (pinfunction "2_2") (pintype "passive"))
      (node (ref "C299") (pin "2") (pinfunction "2_2") (pintype "passive"))
      (node (ref "C3") (pin "2") (pinfunction "2_2") (pintype "passive"))
      (node (ref "C30") (pin "2") (pinfunction "2_2") (pintype "passive"))
      (node (ref "C300") (pin "2") (pinfunction "2_2") (pintype "passive"))
      (node (ref "C301") (pin "2") (pinfunction "2_2") (pintype "passive"))
      (node (ref "C32") (pin "2") (pinfunction "2_2") (pintype "passive"))
      (node (ref "C33") (pin "2") (pinfunction "2_2") (pintype "passive"))
      (node (ref "C34") (pin "2") (pinfunction "2_2") (pintype "passive"))
      (node (ref "C35") (pin "2") (pinfunction "2_2") (pintype "passive"))
      (node (ref "C36") (pin "2") (pinfunction "2_2") (pintype "passive"))
      (node (ref "C37") (pin "2") (pinfunction "2_2") (pintype "passive"))
      (node (ref "C38") (pin "2") (pinfunction "2_2") (pintype "passive"))
      (node (ref "C39") (pin "2") (pinfunction "2_2") (pintype "passive"))
      (node (ref "C4") (pin "2") (pinfunction "2_2") (pintype "passive"))
      (node (ref "C41") (pin "2") (pinfunction "2_2") (pintype "passive"))
      (node (ref "C42") (pin "2") (pinfunction "2_2") (pintype "passive"))
      (node (ref "C43") (pin "2") (pinfunction "2_2") (pintype "passive"))
      (node (ref "C44") (pin "2") (pinfunction "2_2") (pintype "passive"))
      (node (ref "C45") (pin "2") (pinfunction "2_2") (pintype "passive"))
      (node (ref "C46") (pin "2") (pinfunction "2_2") (pintype "passive"))
      (node (ref "C47") (pin "2") (pinfunction "2_2") (pintype "passive"))
      (node (ref "C48") (pin "2") (pinfunction "2_2") (pintype "passive"))
      (node (ref "C49") (pin "2") (pinfunction "2_2") (pintype "passive"))
      (node (ref "C5") (pin "2") (pinfunction "2_2") (pintype "passive"))
      (node (ref "C54") (pin "2") (pinfunction "2_2") (pintype "passive"))
      (node (ref "C56") (pin "2") (pinfunction "2_2") (pintype "passive"))
      (node (ref "C61") (pin "2") (pinfunction "2_2") (pintype "passive"))
      (node (ref "C62") (pin "2") (pinfunction "2_2") (pintype "passive"))
      (node (ref "C63") (pin "2") (pinfunction "2_2") (pintype "passive"))
      (node (ref "C64") (pin "2") (pinfunction "2_2") (pintype "passive"))
      (node (ref "C65") (pin "2") (pinfunction "2_2") (pintype "passive"))
      (node (ref "C66") (pin "2") (pinfunction "2_2") (pintype "passive"))
      (node (ref "C67") (pin "-") (pinfunction "-_-") (pintype "passive"))
      (node (ref "C68") (pin "2") (pinfunction "2_2") (pintype "passive"))
      (node (ref "C69") (pin "2") (pinfunction "2_2") (pintype "passive"))
      (node (ref "C7") (pin "2") (pinfunction "2_2") (pintype "passive"))
      (node (ref "C70") (pin "2") (pinfunction "2_2") (pintype "passive"))
      (node (ref "C71") (pin "2") (pinfunction "2_2") (pintype "passive"))
      (node (ref "C72") (pin "2") (pinfunction "2_2") (pintype "passive"))
      (node (ref "C73") (pin "2") (pinfunction "2_2") (pintype "passive"))
      (node (ref "C74") (pin "2") (pinfunction "2_2") (pintype "passive"))
      (node (ref "C75") (pin "2") (pinfunction "2_2") (pintype "passive"))
      (node (ref "C77") (pin "2") (pinfunction "2_2") (pintype "passive"))
      (node (ref "C78") (pin "2") (pinfunction "2_2") (pintype "passive"))
      (node (ref "C79") (pin "2") (pinfunction "2_2") (pintype "passive"))
      (node (ref "C8") (pin "2") (pinfunction "2_2") (pintype "passive"))
      (node (ref "C80") (pin "2") (pinfunction "2_2") (pintype "passive"))
      (node (ref "C82") (pin "2") (pinfunction "2_2") (pintype "passive"))
      (node (ref "C83") (pin "2") (pinfunction "2_2") (pintype "passive"))
      (node (ref "C84") (pin "2") (pinfunction "2_2") (pintype "passive"))
      (node (ref "C85") (pin "2") (pinfunction "2_2") (pintype "passive"))
      (node (ref "C86") (pin "-") (pinfunction "-_-") (pintype "passive"))
      (node (ref "C87") (pin "2") (pinfunction "2_2") (pintype "passive"))
      (node (ref "C88") (pin "2") (pinfunction "2_2") (pintype "passive"))
      (node (ref "C89") (pin "2") (pinfunction "2_2") (pintype "passive"))
      (node (ref "C9") (pin "2") (pinfunction "2_2") (pintype "passive"))
      (node (ref "C90") (pin "2") (pinfunction "2_2") (pintype "passive"))
      (node (ref "C91") (pin "2") (pinfunction "2_2") (pintype "passive"))
      (node (ref "C92") (pin "-") (pinfunction "-_-") (pintype "passive"))
      (node (ref "C93") (pin "2") (pinfunction "2_2") (pintype "passive"))
      (node (ref "C94") (pin "2") (pinfunction "2_2") (pintype "passive"))
      (node (ref "C95") (pin "2") (pinfunction "2_2") (pintype "passive"))
      (node (ref "C96") (pin "2") (pinfunction "2_2") (pintype "passive"))
      (node (ref "C97") (pin "2") (pinfunction "2_2") (pintype "passive"))
      (node (ref "C98") (pin "2") (pinfunction "2_2") (pintype "passive"))
      (node (ref "C99") (pin "2") (pinfunction "2_2") (pintype "passive"))
      (node (ref "D23") (pin "C") (pinfunction "C_C") (pintype "passive"))
      (node (ref "D25") (pin "C") (pinfunction "C_C") (pintype "passive"))
      (node (ref "D26") (pin "C") (pinfunction "C_C") (pintype "passive"))
      (node (ref "D27") (pin "C") (pinfunction "C_C") (pintype "passive"))
      (node (ref "D28") (pin "C") (pinfunction "C_C") (pintype "passive"))
      (node (ref "D58") (pin "C") (pinfunction "C_C") (pintype "passive"))
      (node (ref "D59") (pin "C") (pinfunction "C_C") (pintype "passive"))
      (node (ref "H3") (pin "B3,4") (pinfunction "MOUNT_B3,4") (pintype "passive"))
      (node (ref "H4") (pin "B3,4") (pinfunction "MOUNT_B3,4") (pintype "passive"))
      (node (ref "H5") (pin "B3,4") (pinfunction "MOUNT_B3,4") (pintype "passive"))
      (node (ref "H6") (pin "B3,4") (pinfunction "MOUNT_B3,4") (pintype "passive"))
      (node (ref "IC1") (pin "4") (pinfunction "GND_4") (pintype "input"))
      (node (ref "IC10") (pin "4") (pinfunction "GND_4") (pintype "input"))
      (node (ref "IC11") (pin "12") (pinfunction "GND_12") (pintype "input"))
      (node (ref "IC11") (pin "13") (pinfunction "GND_13") (pintype "input"))
      (node (ref "IC12") (pin "4") (pinfunction "GND_4") (pintype "input"))
      (node (ref "IC14") (pin "2") (pinfunction "GND_2") (pintype "input"))
      (node (ref "IC16") (pin "2") (pinfunction "GND_2") (pintype "input"))
      (node (ref "IC17") (pin "4") (pinfunction "GND_4") (pintype "input"))
      (node (ref "IC17") (pin "5") (pinfunction "DIR_5") (pintype "input"))
      (node (ref "IC19") (pin "11") (pinfunction "TEST_11") (pintype "input"))
      (node (ref "IC19") (pin "E1") (pinfunction "VSS_E1") (pintype "input"))
      (node (ref "IC19") (pin "E2") (pinfunction "VSS_E2") (pintype "input"))
      (node (ref "IC19") (pin "E3") (pinfunction "VSS_E3") (pintype "input"))
      (node (ref "IC19") (pin "E4") (pinfunction "VSS_E4") (pintype "input"))
      (node (ref "IC19") (pin "E5") (pinfunction "VSS_E5") (pintype "input"))
      (node (ref "IC19") (pin "E6") (pinfunction "VSS_E6") (pintype "input"))
      (node (ref "IC19") (pin "E7") (pinfunction "VSS_E7") (pintype "input"))
      (node (ref "IC19") (pin "E8") (pinfunction "VSS_E8") (pintype "input"))
      (node (ref "IC19") (pin "E9") (pinfunction "VSS_E9") (pintype "input"))
      (node (ref "IC2") (pin "3") (pinfunction "GND_3") (pintype "input"))
      (node (ref "IC20") (pin "23") (pinfunction "VSS1_23") (pintype "input"))
      (node (ref "IC20") (pin "35") (pinfunction "VSSA_35") (pintype "input"))
      (node (ref "IC20") (pin "48") (pinfunction "VSS2_48") (pintype "input"))
      (node (ref "IC20") (pin "63") (pinfunction "VSS3_63") (pintype "input"))
      (node (ref "IC20") (pin "74") (pinfunction "VSS4_74") (pintype "input"))
      (node (ref "IC20") (pin "99") (pinfunction "VSS5_99") (pintype "input"))
      (node (ref "IC22") (pin "1") (pinfunction "GND_1") (pintype "input"))
      (node (ref "IC22") (pin "10") (pinfunction "GND_10") (pintype "input"))
      (node (ref "IC22") (pin "12") (pinfunction "GND_12") (pintype "input"))
      (node (ref "IC23") (pin "3") (pinfunction "GND_3") (pintype "input"))
      (node (ref "IC24") (pin "1") (pinfunction "DGND_1") (pintype "input"))
      (node (ref "IC24") (pin "14") (pinfunction "AGND_14") (pintype "input"))
      (node (ref "IC24") (pin "19") (pinfunction "PGND_19") (pintype "input"))
      (node (ref "IC24") (pin "24") (pinfunction "PGND_24") (pintype "input"))
      (node (ref "IC24") (pin "5") (pinfunction "DGND_5") (pintype "input"))
      (node (ref "IC24") (pin "P$1") (pinfunction "PGND_P$1") (pintype "input"))
      (node (ref "IC24") (pin "P$10") (pinfunction "PGND_P$10") (pintype "input"))
      (node (ref "IC24") (pin "P$11") (pinfunction "PGND_P$11") (pintype "input"))
      (node (ref "IC24") (pin "P$12") (pinfunction "PGND_P$12") (pintype "input"))
      (node (ref "IC24") (pin "P$13") (pinfunction "PGND_P$13") (pintype "input"))
      (node (ref "IC24") (pin "P$14") (pinfunction "PGND_P$14") (pintype "input"))
      (node (ref "IC24") (pin "P$15") (pinfunction "PGND_P$15") (pintype "input"))
      (node (ref "IC24") (pin "P$16") (pinfunction "PGND_P$16") (pintype "input"))
      (node (ref "IC24") (pin "P$17") (pinfunction "PGND_P$17") (pintype "input"))
      (node (ref "IC24") (pin "P$18") (pinfunction "PGND_P$18") (pintype "input"))
      (node (ref "IC24") (pin "P$19") (pinfunction "PGND_P$19") (pintype "input"))
      (node (ref "IC24") (pin "P$2") (pinfunction "PGND_P$2") (pintype "input"))
      (node (ref "IC24") (pin "P$20") (pinfunction "PGND_P$20") (pintype "input"))
      (node (ref "IC24") (pin "P$21") (pinfunction "PGND_P$21") (pintype "input"))
      (node (ref "IC24") (pin "P$22") (pinfunction "PGND_P$22") (pintype "input"))
      (node (ref "IC24") (pin "P$23") (pinfunction "PGND_P$23") (pintype "input"))
      (node (ref "IC24") (pin "P$24") (pinfunction "PGND_P$24") (pintype "input"))
      (node (ref "IC24") (pin "P$3") (pinfunction "PGND_P$3") (pintype "input"))
      (node (ref "IC24") (pin "P$4") (pinfunction "PGND_P$4") (pintype "input"))
      (node (ref "IC24") (pin "P$5") (pinfunction "PGND_P$5") (pintype "input"))
      (node (ref "IC24") (pin "P$6") (pinfunction "PGND_P$6") (pintype "input"))
      (node (ref "IC24") (pin "P$7") (pinfunction "PGND_P$7") (pintype "input"))
      (node (ref "IC24") (pin "P$8") (pinfunction "PGND_P$8") (pintype "input"))
      (node (ref "IC24") (pin "P$9") (pinfunction "PGND_P$9") (pintype "input"))
      (node (ref "IC25") (pin "4") (pinfunction "GND_4") (pintype "input"))
      (node (ref "IC28") (pin "4") (pinfunction "GND_4") (pintype "input"))
      (node (ref "IC29") (pin "4") (pinfunction "GND_4") (pintype "input"))
      (node (ref "IC3") (pin "6") (pinfunction "GND_6") (pintype "input"))
      (node (ref "IC3") (pin "7") (pinfunction "RESV_7") (pintype "input"))
      (node (ref "IC30") (pin "1") (pinfunction "NC_1") (pintype "passive"))
      (node (ref "IC30") (pin "13") (pinfunction "GND_13") (pintype "input"))
      (node (ref "IC31") (pin "15") (pinfunction "PGND_15") (pintype "input"))
      (node (ref "IC31") (pin "2") (pinfunction "OPT_2") (pintype "input"))
      (node (ref "IC31") (pin "9") (pinfunction "AGND_9") (pintype "input"))
      (node (ref "IC31") (pin "EP") (pinfunction "PGND_EP") (pintype "input"))
      (node (ref "IC32") (pin "3") (pinfunction "GND_3") (pintype "input"))
      (node (ref "IC33") (pin "4") (pinfunction "GND_4") (pintype "input"))
      (node (ref "IC34") (pin "3") (pinfunction "GND_3") (pintype "input"))
      (node (ref "IC35") (pin "11") (pinfunction "GND_11") (pintype "input"))
      (node (ref "IC35") (pin "EP1") (pinfunction "GND_EP1") (pintype "input"))
      (node (ref "IC35") (pin "EP2") (pinfunction "GND_EP2") (pintype "input"))
      (node (ref "IC35") (pin "EP3") (pinfunction "GND_EP3") (pintype "input"))
      (node (ref "IC35") (pin "EP4") (pinfunction "GND_EP4") (pintype "input"))
      (node (ref "IC35") (pin "EP5") (pinfunction "GND_EP5") (pintype "input"))
      (node (ref "IC36") (pin "3") (pinfunction "A_3") (pintype "input"))
      (node (ref "IC4") (pin "4") (pinfunction "GND_4") (pintype "input"))
      (node (ref "IC41") (pin "4") (pinfunction "GND_4") (pintype "input"))
      (node (ref "IC42") (pin "4") (pinfunction "GND_4") (pintype "input"))
      (node (ref "IC43") (pin "4") (pinfunction "GND_4") (pintype "input"))
      (node (ref "IC43") (pin "5") (pinfunction "+IN_5") (pintype "input"))
      (node (ref "IC44") (pin "4") (pinfunction "GND_4") (pintype "input"))
      (node (ref "IC45") (pin "4") (pinfunction "GND_4") (pintype "input"))
      (node (ref "IC46") (pin "2") (pinfunction "NC_2") (pintype "passive"))
      (node (ref "IC46") (pin "9") (pinfunction "VSS_9") (pintype "input"))
      (node (ref "IC46") (pin "EP1") (pinfunction "VSS_EP1") (pintype "input"))
      (node (ref "IC46") (pin "EP2") (pinfunction "VSS_EP2") (pintype "input"))
      (node (ref "IC46") (pin "EP3") (pinfunction "VSS_EP3") (pintype "input"))
      (node (ref "IC46") (pin "EP4") (pinfunction "VSS_EP4") (pintype "input"))
      (node (ref "IC47") (pin "1") (pinfunction "NC_1") (pintype "passive"))
      (node (ref "IC47") (pin "4") (pinfunction "GND_4") (pintype "input"))
      (node (ref "IC48") (pin "2") (pinfunction "GND_2") (pintype "power_in"))
      (node (ref "IC48") (pin "4") (pinfunction "NC_4") (pintype "passive"))
      (node (ref "IC49") (pin "4") (pinfunction "GND_4") (pintype "input"))
      (node (ref "IC49") (pin "5") (pinfunction "+IN_5") (pintype "input"))
      (node (ref "IC5") (pin "14") (pinfunction "GND_14") (pintype "input"))
      (node (ref "IC5") (pin "17") (pinfunction "NC_17") (pintype "passive"))
      (node (ref "IC5") (pin "21") (pinfunction "NC_21") (pintype "passive"))
      (node (ref "IC5") (pin "23") (pinfunction "NC_23") (pintype "passive"))
      (node (ref "IC5") (pin "5") (pinfunction "GND_5") (pintype "input"))
      (node (ref "IC5") (pin "6") (pinfunction "NC_6") (pintype "passive"))
      (node (ref "IC5") (pin "P$1") (pinfunction "GND_P$1") (pintype "input"))
      (node (ref "IC5") (pin "P$2") (pinfunction "GND_P$2") (pintype "input"))
      (node (ref "IC5") (pin "P$3") (pinfunction "GND_P$3") (pintype "input"))
      (node (ref "IC5") (pin "P$4") (pinfunction "GND_P$4") (pintype "input"))
      (node (ref "IC5") (pin "P$5") (pinfunction "GND_P$5") (pintype "input"))
      (node (ref "IC5") (pin "P$6") (pinfunction "GND_P$6") (pintype "input"))
      (node (ref "IC5") (pin "P$7") (pinfunction "GND_P$7") (pintype "input"))
      (node (ref "IC5") (pin "P$8") (pinfunction "GND_P$8") (pintype "input"))
      (node (ref "IC5") (pin "P$9") (pinfunction "GND_P$9") (pintype "input"))
      (node (ref "IC52") (pin "2") (pinfunction "GND_2") (pintype "input"))
      (node (ref "IC53") (pin "4") (pinfunction "GND_4") (pintype "input"))
      (node (ref "IC53") (pin "5") (pinfunction "+IN_5") (pintype "input"))
      (node (ref "IC54") (pin "1") (pinfunction "NC_1") (pintype "passive"))
      (node (ref "IC54") (pin "13") (pinfunction "GND_13") (pintype "input"))
      (node (ref "IC55") (pin "1") (pinfunction "NC_1") (pintype "passive"))
      (node (ref "IC55") (pin "13") (pinfunction "GND_13") (pintype "input"))
      (node (ref "IC56") (pin "5") (pinfunction "A_5") (pintype "input"))
      (node (ref "IC57") (pin "2") (pinfunction "GND_2") (pintype "input"))
      (node (ref "IC58") (pin "2") (pinfunction "GND_2") (pintype "input"))
      (node (ref "IC6") (pin "2") (pinfunction "GND_2") (pintype "input"))
      (node (ref "IC7") (pin "2") (pinfunction "NC_2") (pintype "passive"))
      (node (ref "IC7") (pin "9") (pinfunction "VSS_9") (pintype "input"))
      (node (ref "IC7") (pin "EP1") (pinfunction "VSS_EP1") (pintype "input"))
      (node (ref "IC7") (pin "EP2") (pinfunction "VSS_EP2") (pintype "input"))
      (node (ref "IC7") (pin "EP3") (pinfunction "VSS_EP3") (pintype "input"))
      (node (ref "IC7") (pin "EP4") (pinfunction "VSS_EP4") (pintype "input"))
      (node (ref "IC74") (pin "4") (pinfunction "GND_4") (pintype "input"))
      (node (ref "IC75") (pin "3") (pinfunction "GND_3") (pintype "input"))
      (node (ref "IC76") (pin "4") (pinfunction "VSS_4") (pintype "input"))
      (node (ref "IC76") (pin "EP") (pinfunction "VSS_EP") (pintype "input"))
      (node (ref "IC77") (pin "2") (pinfunction "GND_2") (pintype "input"))
      (node (ref "IC8") (pin "2") (pinfunction "GND_2") (pintype "input"))
      (node (ref "L14") (pin "2") (pinfunction "P$1_2") (pintype "passive"))
      (node (ref "L14") (pin "4") (pinfunction "P$1_4") (pintype "passive"))
      (node (ref "L15") (pin "2") (pinfunction "P$1_2") (pintype "passive"))
      (node (ref "L15") (pin "4") (pinfunction "P$1_4") (pintype "passive"))
      (node (ref "MOD1") (pin "1") (pinfunction "GND_1") (pintype "input"))
      (node (ref "MOD1") (pin "102") (pinfunction "GND_102") (pintype "input"))
      (node (ref "MOD1") (pin "107") (pinfunction "GND_107") (pintype "input"))
      (node (ref "MOD1") (pin "113") (pinfunction "GND_113") (pintype "input"))
      (node (ref "MOD1") (pin "119") (pinfunction "GND_119") (pintype "input"))
      (node (ref "MOD1") (pin "125") (pinfunction "GND_125") (pintype "input"))
      (node (ref "MOD1") (pin "129") (pinfunction "GND_129") (pintype "input"))
      (node (ref "MOD1") (pin "13") (pinfunction "GND_13") (pintype "input"))
      (node (ref "MOD1") (pin "132") (pinfunction "GND_132") (pintype "input"))
      (node (ref "MOD1") (pin "135") (pinfunction "GND_135") (pintype "input"))
      (node (ref "MOD1") (pin "138") (pinfunction "GND_138") (pintype "input"))
      (node (ref "MOD1") (pin "14") (pinfunction "GND_14") (pintype "input"))
      (node (ref "MOD1") (pin "141") (pinfunction "GND_141") (pintype "input"))
      (node (ref "MOD1") (pin "144") (pinfunction "GND_144") (pintype "input"))
      (node (ref "MOD1") (pin "146") (pinfunction "GND_146") (pintype "input"))
      (node (ref "MOD1") (pin "147") (pinfunction "GND_147") (pintype "input"))
      (node (ref "MOD1") (pin "152") (pinfunction "GND_152") (pintype "input"))
      (node (ref "MOD1") (pin "153") (pinfunction "GND_153") (pintype "input"))
      (node (ref "MOD1") (pin "158") (pinfunction "GND_158") (pintype "input"))
      (node (ref "MOD1") (pin "159") (pinfunction "GND_159") (pintype "input"))
      (node (ref "MOD1") (pin "164") (pinfunction "GND_164") (pintype "input"))
      (node (ref "MOD1") (pin "165") (pinfunction "GND_165") (pintype "input"))
      (node (ref "MOD1") (pin "170") (pinfunction "GND_170") (pintype "input"))
      (node (ref "MOD1") (pin "171") (pinfunction "GND_171") (pintype "input"))
      (node (ref "MOD1") (pin "176") (pinfunction "GND_176") (pintype "input"))
      (node (ref "MOD1") (pin "177") (pinfunction "GND_177") (pintype "input"))
      (node (ref "MOD1") (pin "19") (pinfunction "GND_19") (pintype "input"))
      (node (ref "MOD1") (pin "2") (pinfunction "GND_2") (pintype "input"))
      (node (ref "MOD1") (pin "20") (pinfunction "GND_20") (pintype "input"))
      (node (ref "MOD1") (pin "200") (pinfunction "GND_200") (pintype "input"))
      (node (ref "MOD1") (pin "201") (pinfunction "GND_201") (pintype "input"))
      (node (ref "MOD1") (pin "217") (pinfunction "GND_217") (pintype "input"))
      (node (ref "MOD1") (pin "231") (pinfunction "GND_231") (pintype "input"))
      (node (ref "MOD1") (pin "241") (pinfunction "GND_241") (pintype "input"))
      (node (ref "MOD1") (pin "242") (pinfunction "GND_242") (pintype "input"))
      (node (ref "MOD1") (pin "243") (pinfunction "GND_243") (pintype "input"))
      (node (ref "MOD1") (pin "244") (pinfunction "GND_244") (pintype "input"))
      (node (ref "MOD1") (pin "245") (pinfunction "GND_245") (pintype "input"))
      (node (ref "MOD1") (pin "246") (pinfunction "GND_246") (pintype "input"))
      (node (ref "MOD1") (pin "247") (pinfunction "GND_247") (pintype "input"))
      (node (ref "MOD1") (pin "248") (pinfunction "GND_248") (pintype "input"))
      (node (ref "MOD1") (pin "249") (pinfunction "GND_249") (pintype "input"))
      (node (ref "MOD1") (pin "25") (pinfunction "GND_25") (pintype "input"))
      (node (ref "MOD1") (pin "250") (pinfunction "GND_250") (pintype "input"))
      (node (ref "MOD1") (pin "26") (pinfunction "GND_26") (pintype "input"))
      (node (ref "MOD1") (pin "31") (pinfunction "GND_31") (pintype "input"))
      (node (ref "MOD1") (pin "32") (pinfunction "GND_32") (pintype "input"))
      (node (ref "MOD1") (pin "37") (pinfunction "GND_37") (pintype "input"))
      (node (ref "MOD1") (pin "38") (pinfunction "GND_38") (pintype "input"))
      (node (ref "MOD1") (pin "43") (pinfunction "GND_43") (pintype "input"))
      (node (ref "MOD1") (pin "44") (pinfunction "GND_44") (pintype "input"))
      (node (ref "MOD1") (pin "49") (pinfunction "GND_49") (pintype "input"))
      (node (ref "MOD1") (pin "50") (pinfunction "GND_50") (pintype "input"))
      (node (ref "MOD1") (pin "55") (pinfunction "GND_55") (pintype "input"))
      (node (ref "MOD1") (pin "56") (pinfunction "GND_56") (pintype "input"))
      (node (ref "MOD1") (pin "61") (pinfunction "GND_61") (pintype "input"))
      (node (ref "MOD1") (pin "62") (pinfunction "GND_62") (pintype "input"))
      (node (ref "MOD1") (pin "67") (pinfunction "GND_67") (pintype "input"))
      (node (ref "MOD1") (pin "68") (pinfunction "GND_68") (pintype "input"))
      (node (ref "MOD1") (pin "7") (pinfunction "GND_7") (pintype "input"))
      (node (ref "MOD1") (pin "73") (pinfunction "GND_73") (pintype "input"))
      (node (ref "MOD1") (pin "74") (pinfunction "GND_74") (pintype "input"))
      (node (ref "MOD1") (pin "79") (pinfunction "GND_79") (pintype "input"))
      (node (ref "MOD1") (pin "8") (pinfunction "GND_8") (pintype "input"))
      (node (ref "MOD1") (pin "80") (pinfunction "GND_80") (pintype "input"))
      (node (ref "MOD1") (pin "85") (pinfunction "GND_85") (pintype "input"))
      (node (ref "MOD1") (pin "86") (pinfunction "GND_86") (pintype "input"))
      (node (ref "MOD1") (pin "M1") (pinfunction "GND_M1") (pintype "input"))
      (node (ref "MOD1") (pin "M2") (pinfunction "GND_M2") (pintype "input"))
      (node (ref "Q1") (pin "2") (pinfunction "G1_2") (pintype "bidirectional"))
      (node (ref "Q1") (pin "4") (pinfunction "G2_4") (pintype "bidirectional"))
      (node (ref "Q3") (pin "2") (pinfunction "G1_2") (pintype "bidirectional"))
      (node (ref "Q3") (pin "4") (pinfunction "G2_4") (pintype "bidirectional"))
      (node (ref "R100") (pin "1") (pinfunction "1_1") (pintype "passive"))
      (node (ref "R101") (pin "1") (pinfunction "1_1") (pintype "passive"))
      (node (ref "R102") (pin "1") (pinfunction "1_1") (pintype "passive"))
      (node (ref "R103") (pin "1") (pinfunction "1_1") (pintype "passive"))
      (node (ref "R105") (pin "1") (pinfunction "1_1") (pintype "passive"))
      (node (ref "R11") (pin "1") (pinfunction "1_1") (pintype "passive"))
      (node (ref "R110") (pin "1") (pinfunction "1_1") (pintype "passive"))
      (node (ref "R112") (pin "1") (pinfunction "1_1") (pintype "passive"))
      (node (ref "R120") (pin "1") (pinfunction "1_1") (pintype "passive"))
      (node (ref "R133") (pin "1") (pinfunction "1_1") (pintype "passive"))
      (node (ref "R148") (pin "1") (pinfunction "1_1") (pintype "passive"))
      (node (ref "R149") (pin "1") (pinfunction "1_1") (pintype "passive"))
      (node (ref "R15") (pin "1") (pinfunction "1_1") (pintype "passive"))
      (node (ref "R151") (pin "1") (pinfunction "1_1") (pintype "passive"))
      (node (ref "R157") (pin "1") (pinfunction "1_1") (pintype "passive"))
      (node (ref "R158") (pin "1") (pinfunction "1_1") (pintype "passive"))
      (node (ref "R159") (pin "1") (pinfunction "1_1") (pintype "passive"))
      (node (ref "R167") (pin "1") (pinfunction "1_1") (pintype "passive"))
      (node (ref "R170") (pin "1") (pinfunction "1_1") (pintype "passive"))
      (node (ref "R179") (pin "1") (pinfunction "1_1") (pintype "passive"))
      (node (ref "R194") (pin "1") (pinfunction "1_1") (pintype "passive"))
      (node (ref "R196") (pin "1") (pinfunction "1_1") (pintype "passive"))
      (node (ref "R198") (pin "1") (pinfunction "1_1") (pintype "passive"))
      (node (ref "R2") (pin "1") (pinfunction "1_1") (pintype "passive"))
      (node (ref "R203") (pin "2") (pinfunction "2_2") (pintype "passive"))
      (node (ref "R215") (pin "1") (pinfunction "1_1") (pintype "passive"))
      (node (ref "R219") (pin "1") (pinfunction "1_1") (pintype "passive"))
      (node (ref "R227") (pin "1") (pinfunction "1_1") (pintype "passive"))
      (node (ref "R228") (pin "1") (pinfunction "1_1") (pintype "passive"))
      (node (ref "R246") (pin "1") (pinfunction "1_1") (pintype "passive"))
      (node (ref "R251") (pin "1") (pinfunction "1_1") (pintype "passive"))
      (node (ref "R252") (pin "1") (pinfunction "1_1") (pintype "passive"))
      (node (ref "R254") (pin "1") (pinfunction "1_1") (pintype "passive"))
      (node (ref "R255") (pin "1") (pinfunction "1_1") (pintype "passive"))
      (node (ref "R257") (pin "1") (pinfunction "1_1") (pintype "passive"))
      (node (ref "R261") (pin "1") (pinfunction "1_1") (pintype "passive"))
      (node (ref "R262") (pin "1") (pinfunction "1_1") (pintype "passive"))
      (node (ref "R263") (pin "1") (pinfunction "1_1") (pintype "passive"))
      (node (ref "R264") (pin "1") (pinfunction "1_1") (pintype "passive"))
      (node (ref "R277") (pin "1") (pinfunction "1_1") (pintype "passive"))
      (node (ref "R285") (pin "1") (pinfunction "1_1") (pintype "passive"))
      (node (ref "R293") (pin "1") (pinfunction "1_1") (pintype "passive"))
      (node (ref "R297") (pin "1") (pinfunction "1_1") (pintype "passive"))
      (node (ref "R30") (pin "1") (pinfunction "1_1") (pintype "passive"))
      (node (ref "R310") (pin "1") (pinfunction "1_1") (pintype "passive"))
      (node (ref "R323") (pin "1") (pinfunction "1_1") (pintype "passive"))
      (node (ref "R325") (pin "1") (pinfunction "1_1") (pintype "passive"))
      (node (ref "R328") (pin "1") (pinfunction "1_1") (pintype "passive"))
      (node (ref "R336") (pin "1") (pinfunction "1_1") (pintype "passive"))
      (node (ref "R337") (pin "1") (pinfunction "1_1") (pintype "passive"))
      (node (ref "R344") (pin "1") (pinfunction "1_1") (pintype "passive"))
      (node (ref "R350") (pin "1") (pinfunction "1_1") (pintype "passive"))
      (node (ref "R354") (pin "1") (pinfunction "1_1") (pintype "passive"))
      (node (ref "R359") (pin "2") (pinfunction "2_2") (pintype "passive"))
      (node (ref "R36") (pin "1") (pinfunction "1_1") (pintype "passive"))
      (node (ref "R363") (pin "1") (pinfunction "1_1") (pintype "passive"))
      (node (ref "R369") (pin "1") (pinfunction "1_1") (pintype "passive"))
      (node (ref "R372") (pin "1") (pinfunction "1_1") (pintype "passive"))
      (node (ref "R376") (pin "1") (pinfunction "1_1") (pintype "passive"))
      (node (ref "R381") (pin "1") (pinfunction "1_1") (pintype "passive"))
      (node (ref "R383") (pin "1") (pinfunction "1_1") (pintype "passive"))
      (node (ref "R388") (pin "1") (pinfunction "1_1") (pintype "passive"))
      (node (ref "R39") (pin "1") (pinfunction "1_1") (pintype "passive"))
      (node (ref "R41") (pin "1") (pinfunction "1_1") (pintype "passive"))
      (node (ref "R415") (pin "1") (pinfunction "1_1") (pintype "passive"))
      (node (ref "R417") (pin "1") (pinfunction "1_1") (pintype "passive"))
      (node (ref "R419") (pin "1") (pinfunction "1_1") (pintype "passive"))
      (node (ref "R423") (pin "1") (pinfunction "1_1") (pintype "passive"))
      (node (ref "R426") (pin "1") (pinfunction "1_1") (pintype "passive"))
      (node (ref "R431") (pin "1") (pinfunction "1_1") (pintype "passive"))
      (node (ref "R446") (pin "1") (pinfunction "1_1") (pintype "passive"))
      (node (ref "R449") (pin "1") (pinfunction "1_1") (pintype "passive"))
      (node (ref "R47") (pin "1") (pinfunction "1_1") (pintype "passive"))
      (node (ref "R480") (pin "1") (pinfunction "1_1") (pintype "passive"))
      (node (ref "R482") (pin "1") (pinfunction "1_1") (pintype "passive"))
      (node (ref "R484") (pin "2") (pinfunction "2_2") (pintype "passive"))
      (node (ref "R491") (pin "1") (pinfunction "1_1") (pintype "passive"))
      (node (ref "R492") (pin "1") (pinfunction "1_1") (pintype "passive"))
      (node (ref "R5") (pin "1") (pinfunction "1_1") (pintype "passive"))
      (node (ref "R50") (pin "1") (pinfunction "1_1") (pintype "passive"))
      (node (ref "R509") (pin "1") (pinfunction "1_1") (pintype "passive"))
      (node (ref "R512") (pin "1") (pinfunction "1_1") (pintype "passive"))
      (node (ref "R513") (pin "1") (pinfunction "1_1") (pintype "passive"))
      (node (ref "R514") (pin "1") (pinfunction "1_1") (pintype "passive"))
      (node (ref "R521") (pin "1") (pinfunction "1_1") (pintype "passive"))
      (node (ref "R522") (pin "2") (pinfunction "2_2") (pintype "passive"))
      (node (ref "R527") (pin "1") (pinfunction "1_1") (pintype "passive"))
      (node (ref "R528") (pin "1") (pinfunction "1_1") (pintype "passive"))
      (node (ref "R529") (pin "1") (pinfunction "1_1") (pintype "passive"))
      (node (ref "R530") (pin "1") (pinfunction "1_1") (pintype "passive"))
      (node (ref "R533") (pin "1") (pinfunction "1_1") (pintype "passive"))
      (node (ref "R538") (pin "1") (pinfunction "1_1") (pintype "passive"))
      (node (ref "R542") (pin "1") (pinfunction "1_1") (pintype "passive"))
      (node (ref "R546") (pin "1") (pinfunction "1_1") (pintype "passive"))
      (node (ref "R550") (pin "1") (pinfunction "1_1") (pintype "passive"))
      (node (ref "R560") (pin "1") (pinfunction "1_1") (pintype "passive"))
      (node (ref "R7") (pin "1") (pinfunction "1_1") (pintype "passive"))
      (node (ref "R71") (pin "1") (pinfunction "1_1") (pintype "passive"))
      (node (ref "R82") (pin "1") (pinfunction "1_1") (pintype "passive"))
      (node (ref "R85") (pin "1") (pinfunction "1_1") (pintype "passive"))
      (node (ref "R9") (pin "2") (pinfunction "2_2") (pintype "passive"))
      (node (ref "R95") (pin "1") (pinfunction "1_1") (pintype "passive"))
      (node (ref "SPACER1") (pin "2") (pinfunction "1_2") (pintype "passive"))
      (node (ref "SPACER1") (pin "3") (pinfunction "1_3") (pintype "passive"))
      (node (ref "SPACER10") (pin "2") (pinfunction "1_2") (pintype "passive"))
      (node (ref "SPACER10") (pin "3") (pinfunction "1_3") (pintype "passive"))
      (node (ref "SPACER11") (pin "2") (pinfunction "1_2") (pintype "passive"))
      (node (ref "SPACER11") (pin "3") (pinfunction "1_3") (pintype "passive"))
      (node (ref "SPACER12") (pin "2") (pinfunction "1_2") (pintype "passive"))
      (node (ref "SPACER12") (pin "3") (pinfunction "1_3") (pintype "passive"))
      (node (ref "SPACER13") (pin "2") (pinfunction "1_2") (pintype "passive"))
      (node (ref "SPACER13") (pin "3") (pinfunction "1_3") (pintype "passive"))
      (node (ref "SPACER2") (pin "2") (pinfunction "1_2") (pintype "passive"))
      (node (ref "SPACER2") (pin "3") (pinfunction "1_3") (pintype "passive"))
      (node (ref "SPACER4") (pin "2") (pinfunction "1_2") (pintype "passive"))
      (node (ref "SPACER4") (pin "3") (pinfunction "1_3") (pintype "passive"))
      (node (ref "SPACER5") (pin "2") (pinfunction "1_2") (pintype "passive"))
      (node (ref "SPACER5") (pin "3") (pinfunction "1_3") (pintype "passive"))
      (node (ref "SPACER6") (pin "2") (pinfunction "1_2") (pintype "passive"))
      (node (ref "SPACER6") (pin "3") (pinfunction "1_3") (pintype "passive"))
      (node (ref "SPACER7") (pin "2") (pinfunction "1_2") (pintype "passive"))
      (node (ref "SPACER7") (pin "3") (pinfunction "1_3") (pintype "passive"))
      (node (ref "SPACER8") (pin "2") (pinfunction "1_2") (pintype "passive"))
      (node (ref "SPACER8") (pin "3") (pinfunction "1_3") (pintype "passive"))
      (node (ref "SPACER9") (pin "2") (pinfunction "1_2") (pintype "passive"))
      (node (ref "SPACER9") (pin "3") (pinfunction "1_3") (pintype "passive"))
      (node (ref "T1") (pin "2") (pinfunction "S_2") (pintype "passive"))
      (node (ref "T10") (pin "2") (pinfunction "S_2") (pintype "passive"))
      (node (ref "T11") (pin "2") (pinfunction "S_2") (pintype "passive"))
      (node (ref "T12") (pin "2") (pinfunction "S_2") (pintype "passive"))
      (node (ref "T15") (pin "1") (pinfunction "S_1") (pintype "passive"))
      (node (ref "T15") (pin "2") (pinfunction "S_2") (pintype "passive"))
      (node (ref "T15") (pin "3") (pinfunction "S_3") (pintype "passive"))
      (node (ref "T17") (pin "2") (pinfunction "S_2") (pintype "passive"))
      (node (ref "T18") (pin "2") (pinfunction "S_2") (pintype "passive"))
      (node (ref "T20") (pin "4") (pinfunction "S_4") (pintype "passive"))
      (node (ref "T20") (pin "S") (pinfunction "S_S") (pintype "passive"))
      (node (ref "T22") (pin "2") (pinfunction "S_2") (pintype "passive"))
      (node (ref "T23") (pin "2") (pinfunction "S_2") (pintype "passive"))
      (node (ref "T26") (pin "2") (pinfunction "S_2") (pintype "passive"))
      (node (ref "T27") (pin "2") (pinfunction "S_2") (pintype "passive"))
      (node (ref "T28") (pin "2") (pinfunction "S_2") (pintype "passive"))
      (node (ref "T30") (pin "2") (pinfunction "S_2") (pintype "passive"))
      (node (ref "T31") (pin "2") (pinfunction "S_2") (pintype "passive"))
      (node (ref "T33") (pin "2") (pinfunction "S_2") (pintype "passive"))
      (node (ref "T34") (pin "2") (pinfunction "S_2") (pintype "passive"))
      (node (ref "T35") (pin "2") (pinfunction "S_2") (pintype "passive"))
      (node (ref "T36") (pin "2") (pinfunction "S_2") (pintype "passive"))
      (node (ref "T37") (pin "2") (pinfunction "S_2") (pintype "passive"))
      (node (ref "T39") (pin "2") (pinfunction "S_2") (pintype "passive"))
      (node (ref "T41") (pin "2") (pinfunction "S_2") (pintype "passive"))
      (node (ref "T47") (pin "2") (pinfunction "S_2") (pintype "passive"))
      (node (ref "T5") (pin "2") (pinfunction "S_2") (pintype "passive"))
      (node (ref "T50") (pin "2") (pinfunction "S_2") (pintype "passive"))
      (node (ref "T51") (pin "2") (pinfunction "S_2") (pintype "passive"))
      (node (ref "T53") (pin "2") (pinfunction "S_2") (pintype "passive"))
      (node (ref "T55") (pin "2") (pinfunction "S_2") (pintype "passive"))
      (node (ref "T56") (pin "2") (pinfunction "S_2") (pintype "passive"))
      (node (ref "T57") (pin "2") (pinfunction "S_2") (pintype "passive"))
      (node (ref "T58") (pin "2") (pinfunction "S_2") (pintype "passive"))
      (node (ref "T59") (pin "2") (pinfunction "S_2") (pintype "passive"))
      (node (ref "T6") (pin "2") (pinfunction "S_2") (pintype "passive"))
      (node (ref "T60") (pin "2") (pinfunction "S_2") (pintype "passive"))
      (node (ref "T63") (pin "2") (pinfunction "S_2") (pintype "passive"))
      (node (ref "T64") (pin "2") (pinfunction "S_2") (pintype "passive"))
      (node (ref "T65") (pin "2") (pinfunction "S_2") (pintype "passive"))
      (node (ref "T66") (pin "2") (pinfunction "S_2") (pintype "passive"))
      (node (ref "T68") (pin "2") (pinfunction "S_2") (pintype "passive"))
      (node (ref "T8") (pin "2") (pinfunction "S_2") (pintype "passive"))
      (node (ref "T9") (pin "1") (pinfunction "S_1") (pintype "passive"))
      (node (ref "T9") (pin "2") (pinfunction "S_2") (pintype "passive"))
      (node (ref "T9") (pin "3") (pinfunction "S_3") (pintype "passive"))
      (node (ref "TP22") (pin "P$1") (pinfunction "TP_P$1") (pintype "input"))
      (node (ref "TP23") (pin "P$1") (pinfunction "TP_P$1") (pintype "input"))
      (node (ref "TP24") (pin "P$1") (pinfunction "TP_P$1") (pintype "input"))
      (node (ref "TP25") (pin "P$1") (pinfunction "TP_P$1") (pintype "input"))
      (node (ref "X1") (pin "1") (pinfunction "1_1") (pintype "input"))
      (node (ref "X10") (pin "1") (pinfunction "1_1") (pintype "input"))
      (node (ref "X11") (pin "1") (pinfunction "1_1") (pintype "passive"))
      (node (ref "X11") (pin "6") (pinfunction "6_6") (pintype "passive"))
      (node (ref "X11") (pin "S1") (pinfunction "S_S1") (pintype "passive"))
      (node (ref "X11") (pin "S2") (pinfunction "S_S2") (pintype "passive"))
      (node (ref "X12") (pin "4") (pinfunction "4_4") (pintype "passive"))
      (node (ref "X13") (pin "1") (pinfunction "1_1") (pintype "passive"))
      (node (ref "X13") (pin "100") (pinfunction "100_100") (pintype "passive"))
      (node (ref "X13") (pin "13") (pinfunction "13_13") (pintype "passive"))
      (node (ref "X13") (pin "14") (pinfunction "14_14") (pintype "passive"))
      (node (ref "X13") (pin "19") (pinfunction "19_19") (pintype "passive"))
      (node (ref "X13") (pin "2") (pinfunction "2_2") (pintype "passive"))
      (node (ref "X13") (pin "20") (pinfunction "20_20") (pintype "passive"))
      (node (ref "X13") (pin "25") (pinfunction "25_25") (pintype "passive"))
      (node (ref "X13") (pin "26") (pinfunction "26_26") (pintype "passive"))
      (node (ref "X13") (pin "31") (pinfunction "31_31") (pintype "passive"))
      (node (ref "X13") (pin "32") (pinfunction "32_32") (pintype "passive"))
      (node (ref "X13") (pin "37") (pinfunction "37_37") (pintype "passive"))
      (node (ref "X13") (pin "42") (pinfunction "42_42") (pintype "passive"))
      (node (ref "X13") (pin "43") (pinfunction "43_43") (pintype "passive"))
      (node (ref "X13") (pin "46") (pinfunction "46_46") (pintype "passive"))
      (node (ref "X13") (pin "49") (pinfunction "49_49") (pintype "passive"))
      (node (ref "X13") (pin "52") (pinfunction "52_52") (pintype "passive"))
      (node (ref "X13") (pin "55") (pinfunction "55_55") (pintype "passive"))
      (node (ref "X13") (pin "56") (pinfunction "56_56") (pintype "passive"))
      (node (ref "X13") (pin "60") (pinfunction "60_60") (pintype "passive"))
      (node (ref "X13") (pin "68") (pinfunction "68_68") (pintype "passive"))
      (node (ref "X13") (pin "7") (pinfunction "7_7") (pintype "passive"))
      (node (ref "X13") (pin "71") (pinfunction "71_71") (pintype "passive"))
      (node (ref "X13") (pin "74") (pinfunction "74_74") (pintype "passive"))
      (node (ref "X13") (pin "77") (pinfunction "77_77") (pintype "passive"))
      (node (ref "X13") (pin "8") (pinfunction "8_8") (pintype "passive"))
      (node (ref "X13") (pin "83") (pinfunction "83_83") (pintype "passive"))
      (node (ref "X13") (pin "87") (pinfunction "87_87") (pintype "passive"))
      (node (ref "X13") (pin "91") (pinfunction "91_91") (pintype "passive"))
      (node (ref "X13") (pin "95") (pinfunction "95_95") (pintype "passive"))
      (node (ref "X13") (pin "99") (pinfunction "99_99") (pintype "passive"))
      (node (ref "X14") (pin "S1") (pinfunction "S_S1") (pintype "passive"))
      (node (ref "X14") (pin "S2") (pinfunction "S_S2") (pintype "passive"))
      (node (ref "X15") (pin "5") (pinfunction "GND_5") (pintype "passive"))
      (node (ref "X15") (pin "SHELL1") (pinfunction "SHIELD_SHELL1") (pintype "passive"))
      (node (ref "X15") (pin "SHELL10") (pinfunction "SHIELD_SHELL10") (pintype "passive"))
      (node (ref "X15") (pin "SHELL2") (pinfunction "SHIELD_SHELL2") (pintype "passive"))
      (node (ref "X15") (pin "SHELL3") (pinfunction "SHIELD_SHELL3") (pintype "passive"))
      (node (ref "X15") (pin "SHELL4") (pinfunction "SHIELD_SHELL4") (pintype "passive"))
      (node (ref "X15") (pin "SHELL5") (pinfunction "SHIELD_SHELL5") (pintype "passive"))
      (node (ref "X15") (pin "SHELL6") (pinfunction "SHIELD_SHELL6") (pintype "passive"))
      (node (ref "X15") (pin "SHELL7") (pinfunction "SHIELD_SHELL7") (pintype "passive"))
      (node (ref "X15") (pin "SHELL8") (pinfunction "SHIELD_SHELL8") (pintype "passive"))
      (node (ref "X15") (pin "SHELL9") (pinfunction "SHIELD_SHELL9") (pintype "passive"))
      (node (ref "X16") (pin "2") (pinfunction "2_2") (pintype "passive"))
      (node (ref "X18") (pin "1") (pinfunction "GND_1") (pintype "input"))
      (node (ref "X18") (pin "18") (pinfunction "GND_18") (pintype "input"))
      (node (ref "X18") (pin "33") (pinfunction "GND_33") (pintype "input"))
      (node (ref "X18") (pin "39") (pinfunction "GND_39") (pintype "input"))
      (node (ref "X18") (pin "45") (pinfunction "GND_45") (pintype "input"))
      (node (ref "X18") (pin "51") (pinfunction "GND_51") (pintype "input"))
      (node (ref "X18") (pin "57") (pinfunction "GND_57") (pintype "input"))
      (node (ref "X18") (pin "63") (pinfunction "GND_63") (pintype "input"))
      (node (ref "X18") (pin "69") (pinfunction "GND_69") (pintype "input"))
      (node (ref "X18") (pin "7") (pinfunction "GND_7") (pintype "input"))
      (node (ref "X18") (pin "75") (pinfunction "GND_75") (pintype "input"))
      (node (ref "X18") (pin "S1") (pinfunction "SHIELD_S1") (pintype "passive"))
      (node (ref "X18") (pin "S2") (pinfunction "SHIELD_S2") (pintype "passive"))
      (node (ref "X19") (pin "2") (pinfunction "2_2") (pintype "passive"))
      (node (ref "X19") (pin "S1") (pinfunction "S_S1") (pintype "passive"))
      (node (ref "X19") (pin "S2") (pinfunction "S_S2") (pintype "passive"))
      (node (ref "X20") (pin "2") (pinfunction "2_2") (pintype "passive"))
      (node (ref "X20") (pin "S1") (pinfunction "S_S1") (pintype "passive"))
      (node (ref "X20") (pin "S2") (pinfunction "S_S2") (pintype "passive"))
      (node (ref "X21") (pin "5") (pinfunction "GND_5") (pintype "input"))
      (node (ref "X22") (pin "6") (pinfunction "6_6") (pintype "passive"))
      (node (ref "X22") (pin "S1") (pinfunction "S_S1") (pintype "passive"))
      (node (ref "X22") (pin "S2") (pinfunction "S_S2") (pintype "passive"))
      (node (ref "X25") (pin "10") (pinfunction "10_10") (pintype "passive"))
      (node (ref "X25") (pin "13") (pinfunction "13_13") (pintype "passive"))
      (node (ref "X25") (pin "16") (pinfunction "16_16") (pintype "passive"))
      (node (ref "X25") (pin "19") (pinfunction "19_19") (pintype "passive"))
      (node (ref "X25") (pin "22") (pinfunction "22_22") (pintype "passive"))
      (node (ref "X25") (pin "4") (pinfunction "4_4") (pintype "passive"))
      (node (ref "X25") (pin "7") (pinfunction "7_7") (pintype "passive"))
      (node (ref "X25") (pin "S1") (pinfunction "S_S1") (pintype "passive"))
      (node (ref "X25") (pin "S2") (pinfunction "S_S2") (pintype "passive"))
      (node (ref "X26") (pin "C5") (pinfunction "GND_C5") (pintype "input"))
      (node (ref "X26") (pin "S1") (pinfunction "SHIELD_S1") (pintype "input"))
      (node (ref "X26") (pin "S2") (pinfunction "SHIELD_S2") (pintype "input"))
      (node (ref "X26") (pin "S3") (pinfunction "SHIELD_S3") (pintype "input"))
      (node (ref "X26") (pin "S4") (pinfunction "SHIELD_S4") (pintype "input"))
      (node (ref "X26") (pin "S5") (pinfunction "SHIELD_S5") (pintype "input"))
      (node (ref "X26") (pin "S6") (pinfunction "SHIELD_S6") (pintype "input"))
      (node (ref "X27") (pin "S1") (pinfunction "S_S1") (pintype "passive"))
      (node (ref "X27") (pin "S2") (pinfunction "S_S2") (pintype "passive"))
      (node (ref "X3") (pin "6") (pinfunction "6_6") (pintype "passive"))
      (node (ref "X3") (pin "S1") (pinfunction "S_S1") (pintype "passive"))
      (node (ref "X3") (pin "S2") (pinfunction "S_S2") (pintype "passive"))
      (node (ref "X32") (pin "11") (pinfunction "GND_11") (pintype "input"))
      (node (ref "X32") (pin "27") (pinfunction "GND_27") (pintype "input"))
      (node (ref "X32") (pin "3") (pinfunction "GND_3") (pintype "input"))
      (node (ref "X32") (pin "33") (pinfunction "GND_33") (pintype "input"))
      (node (ref "X32") (pin "39") (pinfunction "GND_39") (pintype "input"))
      (node (ref "X32") (pin "45") (pinfunction "GND_45") (pintype "input"))
      (node (ref "X32") (pin "5") (pinfunction "GND_5") (pintype "input"))
      (node (ref "X32") (pin "51") (pinfunction "GND_51") (pintype "input"))
      (node (ref "X32") (pin "57") (pinfunction "GND_57") (pintype "input"))
      (node (ref "X32") (pin "71") (pinfunction "GND_71") (pintype "bidirectional"))
      (node (ref "X32") (pin "73") (pinfunction "GND_73") (pintype "bidirectional"))
      (node (ref "X32") (pin "S1") (pinfunction "SHIELD_S1") (pintype "passive"))
      (node (ref "X32") (pin "S2") (pinfunction "SHIELD_S2") (pintype "passive"))
      (node (ref "X33") (pin "1") (pinfunction "GND_1") (pintype "input"))
      (node (ref "X33") (pin "15") (pinfunction "GND_15") (pintype "input"))
      (node (ref "X33") (pin "21") (pinfunction "GND_21") (pintype "input"))
      (node (ref "X33") (pin "27") (pinfunction "GND_27") (pintype "input"))
      (node (ref "X33") (pin "3") (pinfunction "GND_3") (pintype "input"))
      (node (ref "X33") (pin "33") (pinfunction "GND_33") (pintype "input"))
      (node (ref "X33") (pin "39") (pinfunction "GND_39") (pintype "input"))
      (node (ref "X33") (pin "45") (pinfunction "GND_45") (pintype "input"))
      (node (ref "X33") (pin "51") (pinfunction "GND_51") (pintype "input"))
      (node (ref "X33") (pin "57") (pinfunction "GND_57") (pintype "input"))
      (node (ref "X33") (pin "71") (pinfunction "GND_71") (pintype "input"))
      (node (ref "X33") (pin "73") (pinfunction "VIO_CFG/GND_73") (pintype "bidirectional"))
      (node (ref "X33") (pin "75") (pinfunction "GND_75") (pintype "input"))
      (node (ref "X33") (pin "9") (pinfunction "GND_9") (pintype "input"))
      (node (ref "X33") (pin "S1") (pinfunction "SHIELD_S1") (pintype "passive"))
      (node (ref "X33") (pin "S2") (pinfunction "SHIELD_S2") (pintype "passive"))
      (node (ref "X4") (pin "15") (pinfunction "15_15") (pintype "passive"))
      (node (ref "X4") (pin "16") (pinfunction "16_16") (pintype "passive"))
      (node (ref "X4") (pin "29") (pinfunction "29_29") (pintype "passive"))
      (node (ref "X4") (pin "30") (pinfunction "30_30") (pintype "passive"))
      (node (ref "X4") (pin "5") (pinfunction "5_5") (pintype "passive"))
      (node (ref "X6") (pin "5") (pinfunction "GND_5") (pintype "input"))
      (node (ref "X7") (pin "11") (pinfunction "TMDSCLOCKSHIELD_11") (pintype "input"))
      (node (ref "X7") (pin "17") (pinfunction "DDC/CECGROUND_17") (pintype "bidirectional"))
      (node (ref "X7") (pin "2") (pinfunction "TMDSDATA2SHIELD_2") (pintype "input"))
      (node (ref "X7") (pin "5") (pinfunction "TMDSDATA1SHIELD_5") (pintype "input"))
      (node (ref "X7") (pin "8") (pinfunction "TMDSDATA0SHIELD_8") (pintype "input"))
      (node (ref "X7") (pin "S1") (pinfunction "SHIELD_S1") (pintype "input"))
      (node (ref "X7") (pin "S10") (pinfunction "SHIELD_S10") (pintype "input"))
      (node (ref "X7") (pin "S11") (pinfunction "SHIELD_S11") (pintype "input"))
      (node (ref "X7") (pin "S12") (pinfunction "SHIELD_S12") (pintype "input"))
      (node (ref "X7") (pin "S13") (pinfunction "SHIELD_S13") (pintype "input"))
      (node (ref "X7") (pin "S14") (pinfunction "SHIELD_S14") (pintype "input"))
      (node (ref "X7") (pin "S16") (pinfunction "SHIELD_S16") (pintype "input"))
      (node (ref "X7") (pin "S17") (pinfunction "SHIELD_S17") (pintype "input"))
      (node (ref "X7") (pin "S18") (pinfunction "SHIELD_S18") (pintype "input"))
      (node (ref "X7") (pin "S19") (pinfunction "SHIELD_S19") (pintype "input"))
      (node (ref "X7") (pin "S2") (pinfunction "SHIELD_S2") (pintype "input"))
      (node (ref "X7") (pin "S20") (pinfunction "SHIELD_S20") (pintype "input"))
      (node (ref "X7") (pin "S21") (pinfunction "SHIELD_S21") (pintype "input"))
      (node (ref "X7") (pin "S22") (pinfunction "SHIELD_S22") (pintype "input"))
      (node (ref "X7") (pin "S23") (pinfunction "SHIELD_S23") (pintype "input"))
      (node (ref "X7") (pin "S24") (pinfunction "SHIELD_S24") (pintype "input"))
      (node (ref "X7") (pin "S25") (pinfunction "SHIELD_S25") (pintype "input"))
      (node (ref "X7") (pin "S26") (pinfunction "SHIELD_S26") (pintype "input"))
      (node (ref "X7") (pin "S27") (pinfunction "SHIELD_S27") (pintype "input"))
      (node (ref "X7") (pin "S28") (pinfunction "SHIELD_S28") (pintype "input"))
      (node (ref "X7") (pin "S29") (pinfunction "SHIELD_S29") (pintype "input"))
      (node (ref "X7") (pin "S3") (pinfunction "SHIELD_S3") (pintype "input"))
      (node (ref "X7") (pin "S30") (pinfunction "SHIELD_S30") (pintype "input"))
      (node (ref "X7") (pin "S31") (pinfunction "SHIELD_S31") (pintype "input"))
      (node (ref "X7") (pin "S32") (pinfunction "SHIELD_S32") (pintype "input"))
      (node (ref "X7") (pin "S33") (pinfunction "SHIELD_S33") (pintype "input"))
      (node (ref "X7") (pin "S34") (pinfunction "SHIELD_S34") (pintype "input"))
      (node (ref "X7") (pin "S35") (pinfunction "SHIELD_S35") (pintype "input"))
      (node (ref "X7") (pin "S36") (pinfunction "SHIELD_S36") (pintype "input"))
      (node (ref "X7") (pin "S37") (pinfunction "SHIELD_S37") (pintype "input"))
      (node (ref "X7") (pin "S38") (pinfunction "SHIELD_S38") (pintype "input"))
      (node (ref "X7") (pin "S39") (pinfunction "SHIELD_S39") (pintype "input"))
      (node (ref "X7") (pin "S4") (pinfunction "SHIELD_S4") (pintype "input"))
      (node (ref "X7") (pin "S40") (pinfunction "SHIELD_S40") (pintype "input"))
      (node (ref "X7") (pin "S41") (pinfunction "SHIELD_S41") (pintype "input"))
      (node (ref "X7") (pin "S42") (pinfunction "SHIELD_S42") (pintype "input"))
      (node (ref "X7") (pin "S43") (pinfunction "SHIELD_S43") (pintype "input"))
      (node (ref "X7") (pin "S44") (pinfunction "SHIELD_S44") (pintype "input"))
      (node (ref "X7") (pin "S45") (pinfunction "SHIELD_S45") (pintype "input"))
      (node (ref "X7") (pin "S46") (pinfunction "SHIELD_S46") (pintype "input"))
      (node (ref "X7") (pin "S47") (pinfunction "SHIELD_S47") (pintype "input"))
      (node (ref "X7") (pin "S48") (pinfunction "SHIELD_S48") (pintype "input"))
      (node (ref "X7") (pin "S49") (pinfunction "SHIELD_S49") (pintype "input"))
      (node (ref "X7") (pin "S5") (pinfunction "SHIELD_S5") (pintype "input"))
      (node (ref "X7") (pin "S50") (pinfunction "SHIELD_S50") (pintype "input"))
      (node (ref "X7") (pin "S51") (pinfunction "SHIELD_S51") (pintype "input"))
      (node (ref "X7") (pin "S52") (pinfunction "SHIELD_S52") (pintype "input"))
      (node (ref "X7") (pin "S53") (pinfunction "SHIELD_S53") (pintype "input"))
      (node (ref "X7") (pin "S54") (pinfunction "SHIELD_S54") (pintype "input"))
      (node (ref "X7") (pin "S55") (pinfunction "SHIELD_S55") (pintype "input"))
      (node (ref "X7") (pin "S56") (pinfunction "SHIELD_S56") (pintype "input"))
      (node (ref "X7") (pin "S57") (pinfunction "SHIELD_S57") (pintype "input"))
      (node (ref "X7") (pin "S58") (pinfunction "SHIELD_S58") (pintype "input"))
      (node (ref "X7") (pin "S59") (pinfunction "SHIELD_S59") (pintype "input"))
      (node (ref "X7") (pin "S6") (pinfunction "SHIELD_S6") (pintype "input"))
      (node (ref "X7") (pin "S60") (pinfunction "SHIELD_S60") (pintype "input"))
      (node (ref "X7") (pin "S61") (pinfunction "SHIELD_S61") (pintype "input"))
      (node (ref "X7") (pin "S62") (pinfunction "SHIELD_S62") (pintype "input"))
      (node (ref "X7") (pin "S63") (pinfunction "SHIELD_S63") (pintype "input"))
      (node (ref "X7") (pin "S64") (pinfunction "SHIELD_S64") (pintype "input"))
      (node (ref "X7") (pin "S65") (pinfunction "SHIELD_S65") (pintype "input"))
      (node (ref "X7") (pin "S66") (pinfunction "SHIELD_S66") (pintype "input"))
      (node (ref "X7") (pin "S7") (pinfunction "SHIELD_S7") (pintype "input"))
      (node (ref "X7") (pin "S8") (pinfunction "SHIELD_S8") (pintype "input"))
      (node (ref "X7") (pin "S9") (pinfunction "SHIELD_S9") (pintype "input"))
      (node (ref "X8") (pin "4") (pinfunction "GND_4") (pintype "passive"))
      (node (ref "X8") (pin "8") (pinfunction "GND_8") (pintype "passive"))
      (node (ref "X8") (pin "S1") (pinfunction "SHIELD_S1") (pintype "passive"))
      (node (ref "X8") (pin "S2") (pinfunction "SHIELD_S2") (pintype "passive"))
      (node (ref "X8") (pin "S3") (pinfunction "SHIELD_S3") (pintype "passive"))
      (node (ref "X8") (pin "S4") (pinfunction "SHIELD_S4") (pintype "passive"))
      (node (ref "X9") (pin "3") (pinfunction "3_3") (pintype "passive"))
    )
    (net (code "125") (name "HDMI_CEC_3V3") (class "Default")
      (node (ref "D16") (pin "1") (pinfunction "A1_1") (pintype "passive"))
      (node (ref "MOD1") (pin "94") (pinfunction "HDMI_CEC_94") (pintype "bidirectional"))
      (node (ref "R171") (pin "1") (pinfunction "1_1") (pintype "passive"))
      (node (ref "T38") (pin "2") (pinfunction "S_2") (pintype "passive"))
    )
    (net (code "126") (name "HDMI_CK_N") (class "Default")
      (node (ref "C60") (pin "1") (pinfunction "1_1") (pintype "passive"))
      (node (ref "MOD1") (pin "81") (pinfunction "DP1_TXD3_N_81") (pintype "output"))
    )
    (net (code "127") (name "HDMI_CK_P") (class "Default")
      (node (ref "C59") (pin "1") (pinfunction "1_1") (pintype "passive"))
      (node (ref "MOD1") (pin "83") (pinfunction "DP1_TXD3_P_83") (pintype "output"))
    )
    (net (code "128") (name "HDMI_D0_N") (class "Default")
      (node (ref "C58") (pin "1") (pinfunction "1_1") (pintype "passive"))
      (node (ref "MOD1") (pin "75") (pinfunction "DP1_TXD2_N_75") (pintype "output"))
    )
    (net (code "129") (name "HDMI_D0_P") (class "Default")
      (node (ref "C57") (pin "1") (pinfunction "1_1") (pintype "passive"))
      (node (ref "MOD1") (pin "77") (pinfunction "DP1_TXD2_P_77") (pintype "output"))
    )
    (net (code "130") (name "HDMI_D1_N") (class "Default")
      (node (ref "C53") (pin "1") (pinfunction "1_1") (pintype "passive"))
      (node (ref "MOD1") (pin "69") (pinfunction "DP1_TXD1_N_69") (pintype "output"))
    )
    (net (code "131") (name "HDMI_D1_P") (class "Default")
      (node (ref "C52") (pin "1") (pinfunction "1_1") (pintype "passive"))
      (node (ref "MOD1") (pin "71") (pinfunction "DP1_TXD1_P_71") (pintype "output"))
    )
    (net (code "132") (name "HDMI_D2_N") (class "Default")
      (node (ref "C51") (pin "1") (pinfunction "1_1") (pintype "passive"))
      (node (ref "MOD1") (pin "63") (pinfunction "DP1_TXD0_N_63") (pintype "output"))
    )
    (net (code "133") (name "HDMI_D2_P") (class "Default")
      (node (ref "C50") (pin "1") (pinfunction "1_1") (pintype "passive"))
      (node (ref "MOD1") (pin "65") (pinfunction "DP1_TXD0_P_65") (pintype "output"))
    )
    (net (code "134") (name "HDMI_DDC_SCL_3V3") (class "Default")
      (node (ref "R182") (pin "1") (pinfunction "1_1") (pintype "passive"))
      (node (ref "R330") (pin "2") (pinfunction "2_2") (pintype "passive"))
      (node (ref "T43") (pin "2") (pinfunction "S_2") (pintype "passive"))
    )
    (net (code "135") (name "HDMI_DDC_SDA_3V3") (class "Default")
      (node (ref "R183") (pin "1") (pinfunction "1_1") (pintype "passive"))
      (node (ref "R329") (pin "2") (pinfunction "2_2") (pintype "passive"))
      (node (ref "T42") (pin "2") (pinfunction "S_2") (pintype "passive"))
    )
    (net (code "136") (name "HDMI_HPD_1V8") (class "Default")
      (node (ref "MOD1") (pin "96") (pinfunction "DP1_HPD_96") (pintype "input"))
      (node (ref "R180") (pin "1") (pinfunction "1_1") (pintype "passive"))
      (node (ref "T41") (pin "3") (pinfunction "D_3") (pintype "passive"))
    )
    (net (code "137") (name "HEAT_CAM_USB_D_N") (class "Default")
      (node (ref "IC19") (pin "1") (pinfunction "USBDM_DN1/PRT_DIS_M1_1") (pintype "bidirectional"))
      (node (ref "R517") (pin "2") (pinfunction "2_2") (pintype "passive"))
    )
    (net (code "138") (name "HEAT_CAM_USB_D_P") (class "Default")
      (node (ref "IC19") (pin "2") (pinfunction "USBDP_DN1/PRT_DIS_P1_2") (pintype "bidirectional"))
      (node (ref "R518") (pin "2") (pinfunction "2_2") (pintype "passive"))
    )
    (net (code "139") (name "HOST_PRESENT_3V3") (class "Default")
      (node (ref "R81") (pin "2") (pinfunction "2_2") (pintype "passive"))
      (node (ref "X19") (pin "1") (pinfunction "1_1") (pintype "passive"))
    )
    (net (code "140") (name "JETSON_BTN_POWER_1V8") (class "Default")
      (node (ref "MOD1") (pin "216") (pinfunction "GPIO11/CAM_MCLK3_216") (pintype "bidirectional"))
      (node (ref "R324") (pin "2") (pinfunction "2_2") (pintype "passive"))
    )
    (net (code "141") (name "JETSON_CAM_I2C_SCL_3V3") (class "Default")
      (node (ref "IC30") (pin "6") (pinfunction "DA_6") (pintype "passive"))
      (node (ref "R280") (pin "2") (pinfunction "2_2") (pintype "passive"))
    )
    (net (code "142") (name "JETSON_CAM_I2C_SDA_3V3") (class "Default")
      (node (ref "IC30") (pin "7") (pinfunction "DB_7") (pintype "passive"))
      (node (ref "R281") (pin "2") (pinfunction "2_2") (pintype "passive"))
    )
    (net (code "143") (name "JETSON_CAM_MUX0_1V8") (class "Default")
      (node (ref "MOD1") (pin "208") (pinfunction "GPIO08/FAN_TACHO/SDMMC_CD_208") (pintype "input"))
      (node (ref "R162") (pin "1") (pinfunction "1_1") (pintype "passive"))
    )
    (net (code "144") (name "JETSON_CAM_MUX1_1V8") (class "Default")
      (node (ref "MOD1") (pin "230") (pinfunction "PGIO14/FAN_PWM_230") (pintype "output"))
      (node (ref "R163") (pin "1") (pinfunction "1_1") (pintype "passive"))
    )
    (net (code "145") (name "JETSON_LTE_RST_1V8") (class "Default")
      (node (ref "MOD1") (pin "130") (pinfunction "GPIO06/I2S3_FS_130") (pintype "bidirectional"))
      (node (ref "R129") (pin "2") (pinfunction "2_2") (pintype "passive"))
    )
    (net (code "146") (name "JETSON_PCIE0_CLK_N") (class "Default")
      (node (ref "MOD1") (pin "160") (pinfunction "PCIE0_CLK_N_160") (pintype "output"))
      (node (ref "X18") (pin "49") (pinfunction "REFCLKN0_49") (pintype "bidirectional"))
    )
    (net (code "147") (name "JETSON_PCIE0_CLK_P") (class "Default")
      (node (ref "MOD1") (pin "162") (pinfunction "PCIE0_CLK_P_162") (pintype "output"))
      (node (ref "X18") (pin "47") (pinfunction "REFCLKP0_47") (pintype "bidirectional"))
    )
    (net (code "148") (name "JETSON_PCIE0_RX0_N") (class "Default")
      (node (ref "MOD1") (pin "131") (pinfunction "PCIE0_RX0_N_131") (pintype "input"))
      (node (ref "X18") (pin "43") (pinfunction "PERN0_43") (pintype "bidirectional"))
    )
    (net (code "149") (name "JETSON_PCIE0_RX0_P") (class "Default")
      (node (ref "MOD1") (pin "133") (pinfunction "PCIE0_RX0_P_133") (pintype "input"))
      (node (ref "X18") (pin "41") (pinfunction "PERP0_41") (pintype "bidirectional"))
    )
    (net (code "150") (name "JETSON_PCIE0_TX0_N") (class "Default")
      (node (ref "C145") (pin "1") (pinfunction "1_1") (pintype "passive"))
      (node (ref "MOD1") (pin "134") (pinfunction "PCIE0_TX0_N_134") (pintype "output"))
    )
    (net (code "151") (name "JETSON_PCIE0_TX0_P") (class "Default")
      (node (ref "C144") (pin "1") (pinfunction "1_1") (pintype "passive"))
      (node (ref "MOD1") (pin "136") (pinfunction "PCIE0_TX0_P_136") (pintype "output"))
    )
    (net (code "152") (name "JETSON_PCIE1_CLK_N") (class "Default")
      (node (ref "MOD1") (pin "173") (pinfunction "PCIE1_CLK_N/RSVD_173") (pintype "output"))
      (node (ref "X33") (pin "53") (pinfunction "REFCLKN_53") (pintype "bidirectional"))
    )
    (net (code "153") (name "JETSON_PCIE1_CLK_P") (class "Default")
      (node (ref "MOD1") (pin "175") (pinfunction "PCIE1_CLK_P/RSVD_175") (pintype "output"))
      (node (ref "X33") (pin "55") (pinfunction "REFCLKP_55") (pintype "bidirectional"))
    )
    (net (code "154") (name "JETSON_PCIE1_RX0_N") (class "Default")
      (node (ref "MOD1") (pin "167") (pinfunction "PCIE1_RX0_N/RSVD_167") (pintype "input"))
      (node (ref "X33") (pin "41") (pinfunction "PERN0/SATA-B+_41") (pintype "bidirectional"))
    )
    (net (code "155") (name "JETSON_PCIE1_RX0_P") (class "Default")
      (node (ref "MOD1") (pin "169") (pinfunction "PCIE1_RX0_P/RSVD_169") (pintype "input"))
      (node (ref "X33") (pin "43") (pinfunction "PERP0/SATA-B-_43") (pintype "bidirectional"))
    )
    (net (code "156") (name "JETSON_PCIE1_TX0_N") (class "Default")
      (node (ref "C107") (pin "1") (pinfunction "1_1") (pintype "passive"))
      (node (ref "MOD1") (pin "172") (pinfunction "PCIE1_TX0_N/RSVD_172") (pintype "output"))
    )
    (net (code "157") (name "JETSON_PCIE1_TX0_P") (class "Default")
      (node (ref "C108") (pin "1") (pinfunction "1_1") (pintype "passive"))
      (node (ref "MOD1") (pin "174") (pinfunction "PCIE1_TX0_P/RSVD_174") (pintype "output"))
    )
    (net (code "158") (name "JETSON_POWER_EN_5V") (class "Default")
      (node (ref "MOD1") (pin "237") (pinfunction "POWER_EN_237") (pintype "input"))
      (node (ref "R50") (pin "2") (pinfunction "2_2") (pintype "passive"))
      (node (ref "T29") (pin "3") (pinfunction "D_3") (pintype "passive"))
    )
    (net (code "159") (name "JETSON_USB0_N") (class "Default")
      (node (ref "MOD1") (pin "109") (pinfunction "USB0_D_N_109") (pintype "bidirectional"))
      (node (ref "X15") (pin "2") (pinfunction "D-_2") (pintype "bidirectional"))
    )
    (net (code "160") (name "JETSON_USB0_P") (class "Default")
      (node (ref "MOD1") (pin "111") (pinfunction "USB0_D_P_111") (pintype "bidirectional"))
      (node (ref "X15") (pin "3") (pinfunction "D+_3") (pintype "bidirectional"))
    )
    (net (code "161") (name "JETSON_USB0_VBUS_DET_1V8") (class "Default")
      (node (ref "MOD1") (pin "87") (pinfunction "GPIO0/USB0_VBUS_87") (pintype "input"))
      (node (ref "R302") (pin "2") (pinfunction "2_2") (pintype "passive"))
    )
    (net (code "162") (name "JETSON_USER_LED_1V8") (class "Default")
      (node (ref "MOD1") (pin "127") (pinfunction "GPIO04/I2S2_FS_127") (pintype "bidirectional"))
      (node (ref "R322") (pin "1") (pinfunction "1_1") (pintype "passive"))
    )
    (net (code "163") (name "LENS1_COIL+") (class "Default")
      (node (ref "L25") (pin "2") (pinfunction "2_2") (pintype "passive"))
      (node (ref "TP52") (pin "P$1") (pinfunction "TP_P$1") (pintype "input"))
      (node (ref "X3") (pin "4") (pinfunction "4_4") (pintype "passive"))
    )
    (net (code "164") (name "LENS1_COIL-") (class "Default")
      (node (ref "R456") (pin "2") (pinfunction "2_2") (pintype "passive"))
      (node (ref "R458") (pin "2") (pinfunction "2_2") (pintype "passive"))
      (node (ref "TP53") (pin "P$1") (pinfunction "TP_P$1") (pintype "input"))
      (node (ref "X3") (pin "5") (pinfunction "5_5") (pintype "passive"))
    )
    (net (code "165") (name "LM5122_UVLO") (class "Default")
      (node (ref "C143") (pin "1") (pinfunction "1_1") (pintype "passive"))
      (node (ref "IC31") (pin "6") (pinfunction "UVLO_6") (pintype "input"))
      (node (ref "R353") (pin "1") (pinfunction "1_1") (pintype "passive"))
      (node (ref "R354") (pin "2") (pinfunction "2_2") (pintype "passive"))
      (node (ref "T18") (pin "3") (pinfunction "D_3") (pintype "passive"))
      (node (ref "T57") (pin "3") (pinfunction "D_3") (pintype "passive"))
    )
    (net (code "166") (name "LM5122_VCC") (class "Default")
      (node (ref "C134") (pin "1") (pinfunction "1_1") (pintype "passive"))
      (node (ref "D15") (pin "A") (pinfunction "A_A") (pintype "passive"))
      (node (ref "D17") (pin "C") (pinfunction "C_C") (pintype "passive"))
      (node (ref "IC31") (pin "17") (pinfunction "VCC_17") (pintype "bidirectional"))
      (node (ref "R356") (pin "1") (pinfunction "1_1") (pintype "passive"))
    )
    (net (code "167") (name "LTE_USB_D_N") (class "Default")
      (node (ref "MOD1") (pin "115") (pinfunction "USB1_D_N_115") (pintype "bidirectional"))
      (node (ref "R48") (pin "1") (pinfunction "1_1") (pintype "passive"))
    )
    (net (code "168") (name "LTE_USB_D_P") (class "Default")
      (node (ref "MOD1") (pin "117") (pinfunction "USB1_D_P_117") (pintype "bidirectional"))
      (node (ref "R46") (pin "1") (pinfunction "1_1") (pintype "passive"))
    )
    (net (code "169") (name "Net-(BAT1-Pad+)") (class "Default")
      (node (ref "BAT1") (pin "+") (pinfunction "+_+") (pintype "passive"))
      (node (ref "R249") (pin "1") (pinfunction "1_1") (pintype "passive"))
    )
    (net (code "170") (name "Net-(C14-Pad1)") (class "Default")
      (node (ref "C14") (pin "1") (pinfunction "1_1") (pintype "passive"))
      (node (ref "IC3") (pin "11") (pinfunction "RESV_11") (pintype "bidirectional"))
    )
    (net (code "171") (name "Net-(C30-Pad1)") (class "Default")
      (node (ref "C30") (pin "1") (pinfunction "1_1") (pintype "passive"))
      (node (ref "L11") (pin "2") (pinfunction "2_2") (pintype "passive"))
      (node (ref "R35") (pin "1") (pinfunction "1_1") (pintype "passive"))
    )
    (net (code "172") (name "Net-(C31-Pad1)") (class "Default")
      (node (ref "C31") (pin "1") (pinfunction "1_1") (pintype "passive"))
      (node (ref "R333") (pin "1") (pinfunction "1_1") (pintype "passive"))
    )
    (net (code "173") (name "Net-(C34-Pad1)") (class "Default")
      (node (ref "C34") (pin "1") (pinfunction "1_1") (pintype "passive"))
      (node (ref "IC11") (pin "23") (pinfunction "VCCB_23") (pintype "input"))
      (node (ref "IC11") (pin "24") (pinfunction "VCCB_24") (pintype "input"))
      (node (ref "R4") (pin "1") (pinfunction "1_1") (pintype "passive"))
    )
    (net (code "174") (name "Net-(C36-Pad1)") (class "Default")
      (node (ref "C36") (pin "1") (pinfunction "1_1") (pintype "passive"))
      (node (ref "R340") (pin "1") (pinfunction "1_1") (pintype "passive"))
      (node (ref "X4") (pin "13") (pinfunction "13_13") (pintype "passive"))
    )
    (net (code "175") (name "Net-(C40-Pad1)") (class "Default")
      (node (ref "C40") (pin "1") (pinfunction "1_1") (pintype "passive"))
      (node (ref "R307") (pin "1") (pinfunction "1_1") (pintype "passive"))
    )
    (net (code "176") (name "Net-(C50-Pad2)") (class "Default")
      (node (ref "C50") (pin "2") (pinfunction "2_2") (pintype "passive"))
      (node (ref "R75") (pin "1") (pinfunction "1_1") (pintype "passive"))
      (node (ref "R91") (pin "2") (pinfunction "2_2") (pintype "passive"))
    )
    (net (code "177") (name "Net-(C51-Pad2)") (class "Default")
      (node (ref "C51") (pin "2") (pinfunction "2_2") (pintype "passive"))
      (node (ref "R77") (pin "1") (pinfunction "1_1") (pintype "passive"))
      (node (ref "R97") (pin "2") (pinfunction "2_2") (pintype "passive"))
    )
    (net (code "178") (name "Net-(C52-Pad2)") (class "Default")
      (node (ref "C52") (pin "2") (pinfunction "2_2") (pintype "passive"))
      (node (ref "R143") (pin "2") (pinfunction "2_2") (pintype "passive"))
      (node (ref "R79") (pin "1") (pinfunction "1_1") (pintype "passive"))
    )
    (net (code "179") (name "Net-(C53-Pad2)") (class "Default")
      (node (ref "C53") (pin "2") (pinfunction "2_2") (pintype "passive"))
      (node (ref "R144") (pin "2") (pinfunction "2_2") (pintype "passive"))
      (node (ref "R86") (pin "1") (pinfunction "1_1") (pintype "passive"))
    )
    (net (code "180") (name "Net-(C55-Pad1)") (class "Default")
      (node (ref "C55") (pin "1") (pinfunction "1_1") (pintype "passive"))
      (node (ref "R131") (pin "1") (pinfunction "1_1") (pintype "passive"))
    )
    (net (code "181") (name "Net-(C57-Pad2)") (class "Default")
      (node (ref "C57") (pin "2") (pinfunction "2_2") (pintype "passive"))
      (node (ref "R145") (pin "2") (pinfunction "2_2") (pintype "passive"))
      (node (ref "R87") (pin "1") (pinfunction "1_1") (pintype "passive"))
    )
    (net (code "182") (name "Net-(C58-Pad2)") (class "Default")
      (node (ref "C58") (pin "2") (pinfunction "2_2") (pintype "passive"))
      (node (ref "R146") (pin "2") (pinfunction "2_2") (pintype "passive"))
      (node (ref "R88") (pin "1") (pinfunction "1_1") (pintype "passive"))
    )
    (net (code "183") (name "Net-(C59-Pad2)") (class "Default")
      (node (ref "C59") (pin "2") (pinfunction "2_2") (pintype "passive"))
      (node (ref "R153") (pin "2") (pinfunction "2_2") (pintype "passive"))
      (node (ref "R89") (pin "1") (pinfunction "1_1") (pintype "passive"))
    )
    (net (code "184") (name "Net-(C60-Pad2)") (class "Default")
      (node (ref "C60") (pin "2") (pinfunction "2_2") (pintype "passive"))
      (node (ref "R154") (pin "2") (pinfunction "2_2") (pintype "passive"))
      (node (ref "R90") (pin "1") (pinfunction "1_1") (pintype "passive"))
    )
    (net (code "185") (name "Net-(C68-Pad1)") (class "Default")
      (node (ref "C68") (pin "1") (pinfunction "1_1") (pintype "passive"))
      (node (ref "R92") (pin "1") (pinfunction "1_1") (pintype "passive"))
      (node (ref "X12") (pin "3") (pinfunction "3_3") (pintype "passive"))
    )
    (net (code "186") (name "Net-(C76-Pad1)") (class "Default")
      (node (ref "C76") (pin "1") (pinfunction "1_1") (pintype "passive"))
      (node (ref "R309") (pin "2") (pinfunction "2_2") (pintype "passive"))
      (node (ref "R524") (pin "2") (pinfunction "2_2") (pintype "passive"))
      (node (ref "R61") (pin "2") (pinfunction "2_2") (pintype "passive"))
      (node (ref "T67") (pin "1") (pinfunction "S_1") (pintype "passive"))
      (node (ref "T67") (pin "2") (pinfunction "S_2") (pintype "passive"))
      (node (ref "T67") (pin "3") (pinfunction "S_3") (pintype "passive"))
    )
    (net (code "187") (name "Net-(C90-Pad1)") (class "Default")
      (node (ref "C90") (pin "1") (pinfunction "1_1") (pintype "passive"))
      (node (ref "F3") (pin "2") (pinfunction "2_2") (pintype "passive"))
      (node (ref "L7") (pin "2") (pinfunction "2_2") (pintype "passive"))
    )
    (net (code "188") (name "Net-(C101-Pad1)") (class "Default")
      (node (ref "C101") (pin "1") (pinfunction "1_1") (pintype "passive"))
      (node (ref "C147") (pin "1") (pinfunction "1_1") (pintype "passive"))
      (node (ref "C148") (pin "+") (pinfunction "+_+") (pintype "passive"))
      (node (ref "L44") (pin "2") (pinfunction "2_2") (pintype "passive"))
      (node (ref "R276") (pin "2") (pinfunction "2_2") (pintype "passive"))
      (node (ref "X32") (pin "2") (pinfunction "VCC_2") (pintype "input"))
      (node (ref "X32") (pin "4") (pinfunction "VCC_4") (pintype "input"))
      (node (ref "X32") (pin "70") (pinfunction "VCC_70") (pintype "bidirectional"))
      (node (ref "X32") (pin "72") (pinfunction "VCC_72") (pintype "input"))
      (node (ref "X32") (pin "74") (pinfunction "VCC_74") (pintype "input"))
    )
    (net (code "189") (name "Net-(C117-Pad+)") (class "Default")
      (node (ref "C117") (pin "+") (pinfunction "+_+") (pintype "passive"))
      (node (ref "C99") (pin "1") (pinfunction "1_1") (pintype "passive"))
      (node (ref "L4") (pin "1") (pinfunction "1_1") (pintype "passive"))
      (node (ref "X8") (pin "1") (pinfunction "VBUS_1") (pintype "output"))
      (node (ref "X8") (pin "5") (pinfunction "VBUS_5") (pintype "output"))
    )
    (net (code "190") (name "Net-(C127-Pad1)") (class "Default")
      (node (ref "C127") (pin "1") (pinfunction "1_1") (pintype "passive"))
      (node (ref "C128") (pin "1") (pinfunction "1_1") (pintype "passive"))
      (node (ref "C70") (pin "1") (pinfunction "1_1") (pintype "passive"))
      (node (ref "C71") (pin "1") (pinfunction "1_1") (pintype "passive"))
      (node (ref "IC24") (pin "15") (pinfunction "PVDD_15") (pintype "input"))
      (node (ref "IC24") (pin "16") (pinfunction "PVDD_16") (pintype "input"))
      (node (ref "IC24") (pin "27") (pinfunction "PVDD_27") (pintype "input"))
      (node (ref "IC24") (pin "28") (pinfunction "PVDD_28") (pintype "input"))
      (node (ref "L7") (pin "1") (pinfunction "1_1") (pintype "passive"))
    )
    (net (code "191") (name "Net-(C142-Pad1)") (class "Default")
      (node (ref "C142") (pin "1") (pinfunction "1_1") (pintype "passive"))
      (node (ref "L40") (pin "2") (pinfunction "2_2") (pintype "passive"))
      (node (ref "R299") (pin "2") (pinfunction "2_2") (pintype "passive"))
    )
    (net (code "192") (name "Net-(C221-Pad1)") (class "Default")
      (node (ref "C221") (pin "1") (pinfunction "1_1") (pintype "passive"))
      (node (ref "R137") (pin "1") (pinfunction "1_1") (pintype "passive"))
    )
    (net (code "193") (name "Net-(C226-Pad1)") (class "Default")
      (node (ref "C226") (pin "1") (pinfunction "1_1") (pintype "passive"))
      (node (ref "R465") (pin "2") (pinfunction "2_2") (pintype "passive"))
      (node (ref "X3") (pin "1") (pinfunction "1_1") (pintype "passive"))
    )
    (net (code "194") (name "Net-(C238-Pad1)") (class "Default")
      (node (ref "C238") (pin "1") (pinfunction "1_1") (pintype "passive"))
      (node (ref "R314") (pin "1") (pinfunction "1_1") (pintype "passive"))
    )
    (net (code "195") (name "Net-(C243-Pad2)") (class "Default")
      (node (ref "C243") (pin "2") (pinfunction "2_2") (pintype "passive"))
      (node (ref "R348") (pin "1") (pinfunction "1_1") (pintype "passive"))
    )
    (net (code "196") (name "Net-(C256-Pad1)") (class "Default")
      (node (ref "C256") (pin "1") (pinfunction "1_1") (pintype "passive"))
      (node (ref "C257") (pin "1") (pinfunction "1_1") (pintype "passive"))
      (node (ref "C258") (pin "1") (pinfunction "1_1") (pintype "passive"))
      (node (ref "C259") (pin "1") (pinfunction "1_1") (pintype "passive"))
      (node (ref "C300") (pin "1") (pinfunction "1_1") (pintype "passive"))
      (node (ref "C301") (pin "1") (pinfunction "1_1") (pintype "passive"))
      (node (ref "D3") (pin "C") (pinfunction "C_C") (pintype "passive"))
      (node (ref "L3") (pin "1") (pinfunction "1_1") (pintype "passive"))
      (node (ref "L45") (pin "1") (pinfunction "1_1") (pintype "passive"))
      (node (ref "R260") (pin "2") (pinfunction "2_2") (pintype "passive"))
      (node (ref "T61") (pin "D1") (pinfunction "D_D1") (pintype "passive"))
      (node (ref "T61") (pin "D10") (pinfunction "D_D10") (pintype "passive"))
      (node (ref "T61") (pin "D11") (pinfunction "D_D11") (pintype "passive"))
      (node (ref "T61") (pin "D12") (pinfunction "D_D12") (pintype "passive"))
      (node (ref "T61") (pin "D13") (pinfunction "D_D13") (pintype "passive"))
      (node (ref "T61") (pin "D14") (pinfunction "D_D14") (pintype "passive"))
      (node (ref "T61") (pin "D15") (pinfunction "D_D15") (pintype "passive"))
      (node (ref "T61") (pin "D2") (pinfunction "D_D2") (pintype "passive"))
      (node (ref "T61") (pin "D3") (pinfunction "D_D3") (pintype "passive"))
      (node (ref "T61") (pin "D4") (pinfunction "D_D4") (pintype "passive"))
      (node (ref "T61") (pin "D5") (pinfunction "D_D5") (pintype "passive"))
      (node (ref "T61") (pin "D6") (pinfunction "D_D6") (pintype "passive"))
      (node (ref "T61") (pin "D7") (pinfunction "D_D7") (pintype "passive"))
      (node (ref "T61") (pin "D8") (pinfunction "D_D8") (pintype "passive"))
      (node (ref "T61") (pin "D9") (pinfunction "D_D9") (pintype "passive"))
    )
    (net (code "197") (name "Net-(C261-Pad1)") (class "Default")
      (node (ref "C261") (pin "1") (pinfunction "1_1") (pintype "passive"))
      (node (ref "R206") (pin "1") (pinfunction "1_1") (pintype "passive"))
    )
    (net (code "198") (name "Net-(C267-Pad2)") (class "Default")
      (node (ref "C267") (pin "2") (pinfunction "2_2") (pintype "passive"))
      (node (ref "R444") (pin "2") (pinfunction "2_2") (pintype "passive"))
    )
    (net (code "199") (name "Net-(C271-Pad1)") (class "Default")
      (node (ref "C271") (pin "1") (pinfunction "1_1") (pintype "passive"))
      (node (ref "R327") (pin "1") (pinfunction "1_1") (pintype "passive"))
    )
    (net (code "200") (name "Net-(C286-Pad1)") (class "Default")
      (node (ref "C286") (pin "1") (pinfunction "1_1") (pintype "passive"))
      (node (ref "R308") (pin "1") (pinfunction "1_1") (pintype "passive"))
    )
    (net (code "201") (name "Net-(D4-PadC)") (class "Default")
      (node (ref "D4") (pin "C") (pinfunction "C_C") (pintype "passive"))
      (node (ref "R306") (pin "1") (pinfunction "1_1") (pintype "passive"))
    )
    (net (code "202") (name "Net-(D5-PadC)") (class "Default")
      (node (ref "D5") (pin "C") (pinfunction "C_C") (pintype "passive"))
      (node (ref "R128") (pin "1") (pinfunction "1_1") (pintype "passive"))
    )
    (net (code "203") (name "Net-(D6-C)") (class "Default")
      (node (ref "D6") (pin "3") (pinfunction "C_3") (pintype "passive"))
      (node (ref "R31") (pin "1") (pinfunction "1_1") (pintype "passive"))
    )
    (net (code "204") (name "Net-(D7-C)") (class "Default")
      (node (ref "D7") (pin "3") (pinfunction "C_3") (pintype "passive"))
      (node (ref "R233") (pin "1") (pinfunction "1_1") (pintype "passive"))
    )
    (net (code "205") (name "Net-(D8-PadC)") (class "Default")
      (node (ref "D8") (pin "C") (pinfunction "C_C") (pintype "passive"))
      (node (ref "R175") (pin "1") (pinfunction "1_1") (pintype "passive"))
    )
    (net (code "206") (name "Net-(D9-PadC)") (class "Default")
      (node (ref "D9") (pin "C") (pinfunction "C_C") (pintype "passive"))
      (node (ref "R174") (pin "1") (pinfunction "1_1") (pintype "passive"))
    )
    (net (code "207") (name "Net-(D10-PadA)") (class "Default")
      (node (ref "D10") (pin "A") (pinfunction "A_A") (pintype "passive"))
      (node (ref "R291") (pin "1") (pinfunction "1_1") (pintype "passive"))
    )
    (net (code "208") (name "Net-(D11-PadA)") (class "Default")
      (node (ref "D11") (pin "A") (pinfunction "A_A") (pintype "passive"))
      (node (ref "R553") (pin "1") (pinfunction "1_1") (pintype "passive"))
    )
    (net (code "209") (name "Net-(D12-PadC)") (class "Default")
      (node (ref "D12") (pin "C") (pinfunction "C_C") (pintype "passive"))
      (node (ref "R231") (pin "1") (pinfunction "1_1") (pintype "passive"))
    )
    (net (code "210") (name "Net-(D16-A2)") (class "Default")
      (node (ref "D16") (pin "2") (pinfunction "A2_2") (pintype "passive"))
      (node (ref "R173") (pin "2") (pinfunction "2_2") (pintype "passive"))
    )
    (net (code "211") (name "Net-(D16-C)") (class "Default")
      (node (ref "C62") (pin "1") (pinfunction "1_1") (pintype "passive"))
      (node (ref "D16") (pin "3") (pinfunction "C_3") (pintype "passive"))
      (node (ref "T38") (pin "3") (pinfunction "D_3") (pintype "passive"))
      (node (ref "X7") (pin "13") (pinfunction "CEC_13") (pintype "bidirectional"))
    )
    (net (code "212") (name "Net-(D19-PadA)") (class "Default")
      (node (ref "D19") (pin "A") (pinfunction "A_A") (pintype "passive"))
      (node (ref "R58") (pin "1") (pinfunction "1_1") (pintype "passive"))
    )
    (net (code "213") (name "Net-(D21-PadC)") (class "Default")
      (node (ref "D21") (pin "C") (pinfunction "C_C") (pintype "passive"))
      (node (ref "R377") (pin "2") (pinfunction "2_2") (pintype "passive"))
    )
    (net (code "214") (name "Net-(D22-PadC)") (class "Default")
      (node (ref "D22") (pin "C") (pinfunction "C_C") (pintype "passive"))
      (node (ref "R378") (pin "2") (pinfunction "2_2") (pintype "passive"))
    )
    (net (code "215") (name "Net-(D23-PadA)") (class "Default")
      (node (ref "D23") (pin "A") (pinfunction "A_A") (pintype "passive"))
      (node (ref "R385") (pin "1") (pinfunction "1_1") (pintype "passive"))
    )
    (net (code "216") (name "Net-(D24-C)") (class "Default")
      (node (ref "D24") (pin "3") (pinfunction "C_3") (pintype "passive"))
      (node (ref "R191") (pin "1") (pinfunction "1_1") (pintype "passive"))
    )
    (net (code "217") (name "Net-(D25-PadA)") (class "Default")
      (node (ref "D25") (pin "A") (pinfunction "A_A") (pintype "passive"))
      (node (ref "R338") (pin "1") (pinfunction "1_1") (pintype "passive"))
    )
    (net (code "218") (name "Net-(D26-PadA)") (class "Default")
      (node (ref "D26") (pin "A") (pinfunction "A_A") (pintype "passive"))
      (node (ref "R339") (pin "1") (pinfunction "1_1") (pintype "passive"))
    )
    (net (code "219") (name "Net-(D27-PadA)") (class "Default")
      (node (ref "D27") (pin "A") (pinfunction "A_A") (pintype "passive"))
      (node (ref "R519") (pin "1") (pinfunction "1_1") (pintype "passive"))
    )
    (net (code "220") (name "Net-(D28-PadA)") (class "Default")
      (node (ref "D28") (pin "A") (pinfunction "A_A") (pintype "passive"))
      (node (ref "R520") (pin "1") (pinfunction "1_1") (pintype "passive"))
    )
    (net (code "221") (name "Net-(D29-A1)") (class "Default")
      (node (ref "D29") (pin "1") (pinfunction "A1_1") (pintype "passive"))
      (node (ref "R526") (pin "2") (pinfunction "2_2") (pintype "passive"))
    )
    (net (code "222") (name "Net-(D29-A2)") (class "Default")
      (node (ref "D29") (pin "2") (pinfunction "A2_2") (pintype "passive"))
      (node (ref "R249") (pin "2") (pinfunction "2_2") (pintype "passive"))
    )
    (net (code "223") (name "Net-(D30-A1)") (class "Default")
      (node (ref "D30") (pin "1") (pinfunction "A1_1") (pintype "passive"))
      (node (ref "R240") (pin "2") (pinfunction "2_2") (pintype "passive"))
    )
    (net (code "224") (name "Net-(D58-PadA)") (class "Default")
      (node (ref "D58") (pin "A") (pinfunction "A_A") (pintype "passive"))
      (node (ref "R374") (pin "1") (pinfunction "1_1") (pintype "passive"))
    )
    (net (code "225") (name "Net-(D59-PadA)") (class "Default")
      (node (ref "D59") (pin "A") (pinfunction "A_A") (pintype "passive"))
      (node (ref "R373") (pin "1") (pinfunction "1_1") (pintype "passive"))
    )
    (net (code "226") (name "Net-(F2-Pad1)") (class "Default")
      (node (ref "F2") (pin "1") (pinfunction "1_1") (pintype "passive"))
      (node (ref "X13") (pin "76") (pinfunction "76_76") (pintype "passive"))
      (node (ref "X13") (pin "78") (pinfunction "78_78") (pintype "passive"))
      (node (ref "X13") (pin "80") (pinfunction "80_80") (pintype "passive"))
      (node (ref "X13") (pin "82") (pinfunction "82_82") (pintype "passive"))
      (node (ref "X13") (pin "84") (pinfunction "84_84") (pintype "passive"))
      (node (ref "X13") (pin "86") (pinfunction "86_86") (pintype "passive"))
      (node (ref "X13") (pin "88") (pinfunction "88_88") (pintype "passive"))
      (node (ref "X13") (pin "90") (pinfunction "90_90") (pintype "passive"))
      (node (ref "X13") (pin "92") (pinfunction "92_92") (pintype "passive"))
      (node (ref "X13") (pin "94") (pinfunction "94_94") (pintype "passive"))
      (node (ref "X13") (pin "96") (pinfunction "96_96") (pintype "passive"))
      (node (ref "X13") (pin "98") (pinfunction "98_98") (pintype "passive"))
    )
    (net (code "227") (name "Net-(F4-Pad1)") (class "Default")
      (node (ref "F4") (pin "1") (pinfunction "1_1") (pintype "passive"))
      (node (ref "X13") (pin "62") (pinfunction "62_62") (pintype "passive"))
      (node (ref "X13") (pin "64") (pinfunction "64_64") (pintype "passive"))
    )
    (net (code "228") (name "Net-(IC1-BST)") (class "Default")
      (node (ref "C286") (pin "2") (pinfunction "2_2") (pintype "passive"))
      (node (ref "IC1") (pin "6") (pinfunction "BST_6") (pintype "input"))
    )
    (net (code "229") (name "Net-(IC1-FB)") (class "Default")
      (node (ref "C6") (pin "2") (pinfunction "2_2") (pintype "passive"))
      (node (ref "IC1") (pin "8") (pinfunction "FB_8") (pintype "input"))
      (node (ref "R242") (pin "1") (pinfunction "1_1") (pintype "passive"))
      (node (ref "R245") (pin "2") (pinfunction "2_2") (pintype "passive"))
    )
    (net (code "230") (name "Net-(IC1-RT)") (class "Default")
      (node (ref "IC1") (pin "1") (pinfunction "RT_1") (pintype "input"))
      (node (ref "R529") (pin "2") (pinfunction "2_2") (pintype "passive"))
    )
    (net (code "231") (name "Net-(IC1-SS)") (class "Default")
      (node (ref "C285") (pin "1") (pinfunction "1_1") (pintype "passive"))
      (node (ref "IC1") (pin "7") (pinfunction "SS_7") (pintype "input"))
    )
    (net (code "232") (name "Net-(IC1-SW)") (class "Default")
      (node (ref "IC1") (pin "5") (pinfunction "SW_5") (pintype "bidirectional"))
      (node (ref "L1") (pin "DOT") (pinfunction "DOT_DOT") (pintype "passive"))
      (node (ref "R308") (pin "2") (pinfunction "2_2") (pintype "passive"))
    )
    (net (code "233") (name "Net-(IC1-VIN)") (class "Default")
      (node (ref "C3") (pin "1") (pinfunction "1_1") (pintype "passive"))
      (node (ref "IC1") (pin "3") (pinfunction "VIN_3") (pintype "input"))
      (node (ref "L2") (pin "1") (pinfunction "1_1") (pintype "passive"))
    )
    (net (code "234") (name "Net-(IC2-NC)") (class "Default")
      (node (ref "IC2") (pin "1") (pinfunction "NC_1") (pintype "passive"))
      (node (ref "R15") (pin "2") (pinfunction "2_2") (pintype "passive"))
      (node (ref "R16") (pin "1") (pinfunction "1_1") (pintype "passive"))
    )
    (net (code "235") (name "Net-(IC2-VCC)") (class "Default")
      (node (ref "C45") (pin "1") (pinfunction "1_1") (pintype "passive"))
      (node (ref "IC2") (pin "5") (pinfunction "VCC_5") (pintype "input"))
      (node (ref "R140") (pin "2") (pinfunction "2_2") (pintype "passive"))
    )
    (net (code "236") (name "Net-(IC2-Y)") (class "Default")
      (node (ref "IC2") (pin "4") (pinfunction "Y_4") (pintype "output"))
      (node (ref "R147") (pin "1") (pinfunction "1_1") (pintype "passive"))
    )
    (net (code "237") (name "Net-(IC3-INT1{slash}INT)") (class "Default")
      (node (ref "IC3") (pin "4") (pinfunction "INT1/INT_4") (pintype "bidirectional"))
      (node (ref "R29") (pin "2") (pinfunction "2_2") (pintype "passive"))
    )
    (net (code "238") (name "Net-(IC3-INT2{slash}FSYNC)") (class "Default")
      (node (ref "IC3") (pin "9") (pinfunction "INT2/FSYNC_9") (pintype "bidirectional"))
      (node (ref "R28") (pin "2") (pinfunction "2_2") (pintype "passive"))
      (node (ref "R521") (pin "2") (pinfunction "2_2") (pintype "passive"))
    )
    (net (code "239") (name "Net-(IC3-SDA{slash}SDIO{slash}SDI)") (class "Default")
      (node (ref "IC3") (pin "14") (pinfunction "SDA/SDIO/SDI_14") (pintype "bidirectional"))
      (node (ref "R24") (pin "2") (pinfunction "2_2") (pintype "passive"))
    )
    (net (code "240") (name "Net-(IC3-SDO{slash}AD0)") (class "Default")
      (node (ref "IC3") (pin "1") (pinfunction "SDO/AD0_1") (pintype "bidirectional"))
      (node (ref "R522") (pin "1") (pinfunction "1_1") (pintype "passive"))
      (node (ref "R523") (pin "2") (pinfunction "2_2") (pintype "passive"))
    )
    (net (code "241") (name "Net-(IC3-VDD)") (class "Default")
      (node (ref "C140") (pin "1") (pinfunction "1_1") (pintype "passive"))
      (node (ref "C15") (pin "1") (pinfunction "1_1") (pintype "passive"))
      (node (ref "IC3") (pin "12") (pinfunction "~{CS}_12") (pintype "input"))
      (node (ref "IC3") (pin "5") (pinfunction "VDDIO_5") (pintype "input"))
      (node (ref "IC3") (pin "8") (pinfunction "VDD_8") (pintype "input"))
      (node (ref "R25") (pin "2") (pinfunction "2_2") (pintype "passive"))
      (node (ref "R523") (pin "1") (pinfunction "1_1") (pintype "passive"))
    )
    (net (code "242") (name "Net-(IC4-BST)") (class "Default")
      (node (ref "C31") (pin "2") (pinfunction "2_2") (pintype "passive"))
      (node (ref "IC4") (pin "6") (pinfunction "BST_6") (pintype "input"))
    )
    (net (code "243") (name "Net-(IC4-EN)") (class "Default")
      (node (ref "IC4") (pin "2") (pinfunction "EN_2") (pintype "input"))
      (node (ref "TP68") (pin "P$1") (pinfunction "TP_P$1") (pintype "input"))
    )
    (net (code "244") (name "Net-(IC4-FB)") (class "Default")
      (node (ref "C234") (pin "2") (pinfunction "2_2") (pintype "passive"))
      (node (ref "IC4") (pin "8") (pinfunction "FB_8") (pintype "input"))
      (node (ref "R32") (pin "1") (pinfunction "1_1") (pintype "passive"))
      (node (ref "R33") (pin "2") (pinfunction "2_2") (pintype "passive"))
    )
    (net (code "245") (name "Net-(IC4-RT)") (class "Default")
      (node (ref "IC4") (pin "1") (pinfunction "RT_1") (pintype "input"))
      (node (ref "R446") (pin "2") (pinfunction "2_2") (pintype "passive"))
    )
    (net (code "246") (name "Net-(IC4-SS)") (class "Default")
      (node (ref "C224") (pin "1") (pinfunction "1_1") (pintype "passive"))
      (node (ref "IC4") (pin "7") (pinfunction "SS_7") (pintype "input"))
    )
    (net (code "247") (name "Net-(IC4-SW)") (class "Default")
      (node (ref "IC4") (pin "5") (pinfunction "SW_5") (pintype "bidirectional"))
      (node (ref "L15") (pin "1") (pinfunction "DOT_1") (pintype "passive"))
      (node (ref "R333") (pin "2") (pinfunction "2_2") (pintype "passive"))
    )
    (net (code "248") (name "Net-(IC4-VIN)") (class "Default")
      (node (ref "C29") (pin "1") (pinfunction "1_1") (pintype "passive"))
      (node (ref "IC4") (pin "3") (pinfunction "VIN_3") (pintype "input"))
      (node (ref "L11") (pin "1") (pinfunction "1_1") (pintype "passive"))
    )
    (net (code "249") (name "Net-(IC5-CM)") (class "Default")
      (node (ref "IC5") (pin "10") (pinfunction "CM_10") (pintype "output"))
      (node (ref "R207") (pin "2") (pinfunction "2_2") (pintype "passive"))
    )
    (net (code "250") (name "Net-(IC5-COMP)") (class "Default")
      (node (ref "C265") (pin "2") (pinfunction "2_2") (pintype "passive"))
      (node (ref "C266") (pin "2") (pinfunction "2_2") (pintype "passive"))
      (node (ref "IC5") (pin "9") (pinfunction "COMP_9") (pintype "bidirectional"))
      (node (ref "R320") (pin "1") (pinfunction "1_1") (pintype "passive"))
    )
    (net (code "251") (name "Net-(IC5-CS)") (class "Default")
      (node (ref "C260") (pin "1") (pinfunction "1_1") (pintype "passive"))
      (node (ref "IC5") (pin "12") (pinfunction "CS_12") (pintype "input"))
      (node (ref "R202") (pin "1") (pinfunction "1_1") (pintype "passive"))
    )
    (net (code "252") (name "Net-(IC5-CSG)") (class "Default")
      (node (ref "C260") (pin "2") (pinfunction "2_2") (pintype "passive"))
      (node (ref "IC5") (pin "13") (pinfunction "CSG_13") (pintype "input"))
      (node (ref "R203") (pin "1") (pinfunction "1_1") (pintype "passive"))
    )
    (net (code "253") (name "Net-(IC5-DEMB)") (class "Default")
      (node (ref "IC5") (pin "1") (pinfunction "DEMB_1") (pintype "input"))
      (node (ref "R132") (pin "2") (pinfunction "2_2") (pintype "passive"))
    )
    (net (code "254") (name "Net-(IC5-FB)") (class "Default")
      (node (ref "C265") (pin "1") (pinfunction "1_1") (pintype "passive"))
      (node (ref "C266") (pin "1") (pinfunction "1_1") (pintype "passive"))
      (node (ref "C267") (pin "1") (pinfunction "1_1") (pintype "passive"))
      (node (ref "IC5") (pin "8") (pinfunction "FB_8") (pintype "input"))
      (node (ref "R198") (pin "2") (pinfunction "2_2") (pintype "passive"))
      (node (ref "R199") (pin "1") (pinfunction "1_1") (pintype "passive"))
      (node (ref "R201") (pin "1") (pinfunction "1_1") (pintype "passive"))
    )
    (net (code "255") (name "Net-(IC5-HB)") (class "Default")
      (node (ref "C263") (pin "1") (pinfunction "1_1") (pintype "passive"))
      (node (ref "D1") (pin "C") (pinfunction "C_C") (pintype "passive"))
      (node (ref "IC5") (pin "20") (pinfunction "HB_20") (pintype "bidirectional"))
    )
    (net (code "256") (name "Net-(IC5-HO)") (class "Default")
      (node (ref "IC5") (pin "19") (pinfunction "HO_19") (pintype "output"))
      (node (ref "R130") (pin "1") (pinfunction "1_1") (pintype "passive"))
    )
    (net (code "257") (name "Net-(IC5-LO)") (class "Default")
      (node (ref "IC5") (pin "15") (pinfunction "LO_15") (pintype "output"))
      (node (ref "R113") (pin "1") (pinfunction "1_1") (pintype "passive"))
    )
    (net (code "258") (name "Net-(IC5-RAMP)") (class "Default")
      (node (ref "C264") (pin "1") (pinfunction "1_1") (pintype "passive"))
      (node (ref "IC5") (pin "11") (pinfunction "RAMP_11") (pintype "input"))
      (node (ref "R364") (pin "1") (pinfunction "1_1") (pintype "passive"))
    )
    (net (code "259") (name "Net-(IC5-RES)") (class "Default")
      (node (ref "C8") (pin "1") (pinfunction "1_1") (pintype "passive"))
      (node (ref "IC5") (pin "2") (pinfunction "RES_2") (pintype "bidirectional"))
    )
    (net (code "260") (name "Net-(IC5-RT)") (class "Default")
      (node (ref "IC5") (pin "4") (pinfunction "RT_4") (pintype "input"))
      (node (ref "R112") (pin "2") (pinfunction "2_2") (pintype "passive"))
      (node (ref "R41") (pin "2") (pinfunction "2_2") (pintype "passive"))
    )
    (net (code "261") (name "Net-(IC5-SS)") (class "Default")
      (node (ref "C7") (pin "1") (pinfunction "1_1") (pintype "passive"))
      (node (ref "IC5") (pin "3") (pinfunction "SS_3") (pintype "input"))
    )
    (net (code "262") (name "Net-(IC5-SW)") (class "Default")
      (node (ref "C263") (pin "2") (pinfunction "2_2") (pintype "passive"))
      (node (ref "D3") (pin "A1") (pinfunction "A_A1") (pintype "passive"))
      (node (ref "D3") (pin "A2") (pinfunction "A_A2") (pintype "passive"))
      (node (ref "IC5") (pin "18") (pinfunction "SW_18") (pintype "bidirectional"))
      (node (ref "L5") (pin "DOT") (pinfunction "DOT_DOT") (pintype "passive"))
      (node (ref "R206") (pin "2") (pinfunction "2_2") (pintype "passive"))
      (node (ref "R366") (pin "2") (pinfunction "2_2") (pintype "passive"))
      (node (ref "T61") (pin "1") (pinfunction "S_1") (pintype "passive"))
      (node (ref "T61") (pin "2") (pinfunction "S_2") (pintype "passive"))
      (node (ref "T61") (pin "3") (pinfunction "S_3") (pintype "passive"))
      (node (ref "T62") (pin "D1") (pinfunction "D_D1") (pintype "passive"))
      (node (ref "T62") (pin "D10") (pinfunction "D_D10") (pintype "passive"))
      (node (ref "T62") (pin "D11") (pinfunction "D_D11") (pintype "passive"))
      (node (ref "T62") (pin "D12") (pinfunction "D_D12") (pintype "passive"))
      (node (ref "T62") (pin "D13") (pinfunction "D_D13") (pintype "passive"))
      (node (ref "T62") (pin "D14") (pinfunction "D_D14") (pintype "passive"))
      (node (ref "T62") (pin "D15") (pinfunction "D_D15") (pintype "passive"))
      (node (ref "T62") (pin "D2") (pinfunction "D_D2") (pintype "passive"))
      (node (ref "T62") (pin "D3") (pinfunction "D_D3") (pintype "passive"))
      (node (ref "T62") (pin "D4") (pinfunction "D_D4") (pintype "passive"))
      (node (ref "T62") (pin "D5") (pinfunction "D_D5") (pintype "passive"))
      (node (ref "T62") (pin "D6") (pinfunction "D_D6") (pintype "passive"))
      (node (ref "T62") (pin "D7") (pinfunction "D_D7") (pintype "passive"))
      (node (ref "T62") (pin "D8") (pinfunction "D_D8") (pintype "passive"))
      (node (ref "T62") (pin "D9") (pinfunction "D_D9") (pintype "passive"))
    )
    (net (code "263") (name "Net-(IC5-UVLO)") (class "Default")
      (node (ref "C13") (pin "1") (pinfunction "1_1") (pintype "passive"))
      (node (ref "IC5") (pin "24") (pinfunction "UVLO_24") (pintype "input"))
      (node (ref "R133") (pin "2") (pinfunction "2_2") (pintype "passive"))
      (node (ref "R196") (pin "2") (pinfunction "2_2") (pintype "passive"))
      (node (ref "R197") (pin "1") (pinfunction "1_1") (pintype "passive"))
      (node (ref "T63") (pin "3") (pinfunction "D_3") (pintype "passive"))
    )
    (net (code "264") (name "Net-(IC5-VCCDIS)") (class "Default")
      (node (ref "IC5") (pin "7") (pinfunction "VCCDIS_7") (pintype "input"))
      (node (ref "TP7") (pin "P$1") (pinfunction "TP_P$1") (pintype "input"))
    )
    (net (code "265") (name "Net-(IC5-VIN)") (class "Default")
      (node (ref "C11") (pin "1") (pinfunction "1_1") (pintype "passive"))
      (node (ref "IC5") (pin "22") (pinfunction "VIN_22") (pintype "input"))
      (node (ref "R197") (pin "2") (pinfunction "2_2") (pintype "passive"))
      (node (ref "R260") (pin "1") (pinfunction "1_1") (pintype "passive"))
    )
    (net (code "266") (name "Net-(IC7-HB)") (class "Default")
      (node (ref "C204") (pin "1") (pinfunction "1_1") (pintype "passive"))
      (node (ref "IC7") (pin "3") (pinfunction "HB_3") (pintype "input"))
    )
    (net (code "267") (name "Net-(IC7-HO)") (class "Default")
      (node (ref "IC7") (pin "4") (pinfunction "HO_4") (pintype "output"))
      (node (ref "R450") (pin "1") (pinfunction "1_1") (pintype "passive"))
    )
    (net (code "268") (name "Net-(IC7-HS)") (class "Default")
      (node (ref "C204") (pin "2") (pinfunction "2_2") (pintype "passive"))
      (node (ref "IC7") (pin "5") (pinfunction "HS_5") (pintype "input"))
      (node (ref "L23") (pin "DOT") (pinfunction "DOT_DOT") (pintype "passive"))
      (node (ref "T53") (pin "3") (pinfunction "D_3") (pintype "passive"))
      (node (ref "T54") (pin "2") (pinfunction "S_2") (pintype "passive"))
    )
    (net (code "269") (name "Net-(IC7-LO)") (class "Default")
      (node (ref "IC7") (pin "10") (pinfunction "LO_10") (pintype "output"))
      (node (ref "R451") (pin "1") (pinfunction "1_1") (pintype "passive"))
    )
    (net (code "270") (name "Net-(IC7-VDD)") (class "Default")
      (node (ref "C205") (pin "1") (pinfunction "1_1") (pintype "passive"))
      (node (ref "IC7") (pin "1") (pinfunction "VDD_1") (pintype "input"))
      (node (ref "R452") (pin "1") (pinfunction "1_1") (pintype "passive"))
    )
    (net (code "271") (name "Net-(IC8-I{slash}O3)") (class "Default")
      (node (ref "IC8") (pin "4") (pinfunction "I/O3_4") (pintype "passive"))
      (node (ref "R311") (pin "2") (pinfunction "2_2") (pintype "passive"))
      (node (ref "X4") (pin "19") (pinfunction "19_19") (pintype "passive"))
    )
    (net (code "272") (name "Net-(IC10-BST)") (class "Default")
      (node (ref "C40") (pin "2") (pinfunction "2_2") (pintype "passive"))
      (node (ref "IC10") (pin "6") (pinfunction "BST_6") (pintype "input"))
    )
    (net (code "273") (name "Net-(IC10-FB)") (class "Default")
      (node (ref "C279") (pin "2") (pinfunction "2_2") (pintype "passive"))
      (node (ref "IC10") (pin "8") (pinfunction "FB_8") (pintype "input"))
      (node (ref "R103") (pin "2") (pinfunction "2_2") (pintype "passive"))
      (node (ref "R527") (pin "2") (pinfunction "2_2") (pintype "passive"))
      (node (ref "R98") (pin "1") (pinfunction "1_1") (pintype "passive"))
    )
    (net (code "274") (name "Net-(IC10-RT)") (class "Default")
      (node (ref "IC10") (pin "1") (pinfunction "RT_1") (pintype "input"))
      (node (ref "R509") (pin "2") (pinfunction "2_2") (pintype "passive"))
    )
    (net (code "275") (name "Net-(IC10-SS)") (class "Default")
      (node (ref "C277") (pin "1") (pinfunction "1_1") (pintype "passive"))
      (node (ref "IC10") (pin "7") (pinfunction "SS_7") (pintype "input"))
    )
    (net (code "276") (name "Net-(IC10-SW)") (class "Default")
      (node (ref "IC10") (pin "5") (pinfunction "SW_5") (pintype "bidirectional"))
      (node (ref "L14") (pin "1") (pinfunction "DOT_1") (pintype "passive"))
      (node (ref "R307") (pin "2") (pinfunction "2_2") (pintype "passive"))
    )
    (net (code "277") (name "Net-(IC10-VIN)") (class "Default")
      (node (ref "C79") (pin "1") (pinfunction "1_1") (pintype "passive"))
      (node (ref "IC10") (pin "3") (pinfunction "VIN_3") (pintype "input"))
      (node (ref "L9") (pin "1") (pinfunction "1_1") (pintype "passive"))
    )
    (net (code "278") (name "Net-(IC11-A1)") (class "Default")
      (node (ref "IC11") (pin "3") (pinfunction "A1_3") (pintype "bidirectional"))
      (node (ref "R148") (pin "2") (pinfunction "2_2") (pintype "passive"))
    )
    (net (code "279") (name "Net-(IC11-A2)") (class "Default")
      (node (ref "IC11") (pin "4") (pinfunction "A2_4") (pintype "bidirectional"))
      (node (ref "R47") (pin "2") (pinfunction "2_2") (pintype "passive"))
    )
    (net (code "280") (name "Net-(IC11-A5)") (class "Default")
      (node (ref "IC11") (pin "7") (pinfunction "A5_7") (pintype "bidirectional"))
      (node (ref "R18") (pin "2") (pinfunction "2_2") (pintype "passive"))
    )
    (net (code "281") (name "Net-(IC11-A6)") (class "Default")
      (node (ref "IC11") (pin "8") (pinfunction "A6_8") (pintype "bidirectional"))
      (node (ref "R21") (pin "2") (pinfunction "2_2") (pintype "passive"))
    )
    (net (code "282") (name "Net-(IC11-A7)") (class "Default")
      (node (ref "IC11") (pin "9") (pinfunction "A7_9") (pintype "bidirectional"))
      (node (ref "R22") (pin "2") (pinfunction "2_2") (pintype "passive"))
    )
    (net (code "283") (name "Net-(IC11-A8)") (class "Default")
      (node (ref "IC11") (pin "10") (pinfunction "A8_10") (pintype "bidirectional"))
      (node (ref "R23") (pin "2") (pinfunction "2_2") (pintype "passive"))
    )
    (net (code "284") (name "Net-(IC11-B3)") (class "Default")
      (node (ref "IC11") (pin "19") (pinfunction "B3_19") (pintype "bidirectional"))
      (node (ref "R51") (pin "1") (pinfunction "1_1") (pintype "passive"))
    )
    (net (code "285") (name "Net-(IC11-B4)") (class "Default")
      (node (ref "IC11") (pin "18") (pinfunction "B4_18") (pintype "bidirectional"))
      (node (ref "R52") (pin "1") (pinfunction "1_1") (pintype "passive"))
    )
    (net (code "286") (name "Net-(IC11-DIR1)") (class "Default")
      (node (ref "C20") (pin "1") (pinfunction "1_1") (pintype "passive"))
      (node (ref "IC11") (pin "1") (pinfunction "VCCA_1") (pintype "input"))
      (node (ref "IC11") (pin "11") (pinfunction "DIR2_11") (pintype "input"))
      (node (ref "IC11") (pin "2") (pinfunction "DIR1_2") (pintype "input"))
      (node (ref "R3") (pin "1") (pinfunction "1_1") (pintype "passive"))
    )
    (net (code "287") (name "Net-(IC11-~{OE})") (class "Default")
      (node (ref "IC11") (pin "22") (pinfunction "~{OE}_22") (pintype "input"))
      (node (ref "R335") (pin "1") (pinfunction "1_1") (pintype "passive"))
      (node (ref "T33") (pin "3") (pinfunction "D_3") (pintype "passive"))
    )
    (net (code "288") (name "Net-(IC12A-+IN)") (class "Default")
      (node (ref "IC12") (pin "3") (pinfunction "+IN_3") (pintype "input"))
      (node (ref "R418") (pin "2") (pinfunction "2_2") (pintype "passive"))
      (node (ref "R419") (pin "2") (pinfunction "2_2") (pintype "passive"))
      (node (ref "R515") (pin "2") (pinfunction "2_2") (pintype "passive"))
    )
    (net (code "289") (name "Net-(IC12A--IN)") (class "Default")
      (node (ref "IC12") (pin "1") (pinfunction "OUT_1") (pintype "output"))
      (node (ref "IC12") (pin "2") (pinfunction "-IN_2") (pintype "input"))
      (node (ref "R352") (pin "1") (pinfunction "1_1") (pintype "passive"))
    )
    (net (code "290") (name "Net-(IC12B-+IN)") (class "Default")
      (node (ref "IC12") (pin "5") (pinfunction "+IN_5") (pintype "input"))
      (node (ref "R416") (pin "2") (pinfunction "2_2") (pintype "passive"))
      (node (ref "R417") (pin "2") (pinfunction "2_2") (pintype "passive"))
    )
    (net (code "291") (name "Net-(IC12B--IN)") (class "Default")
      (node (ref "IC12") (pin "6") (pinfunction "-IN_6") (pintype "input"))
      (node (ref "IC12") (pin "7") (pinfunction "OUT_7") (pintype "output"))
      (node (ref "R351") (pin "1") (pinfunction "1_1") (pintype "passive"))
    )
    (net (code "292") (name "Net-(IC12C-VCC)") (class "Default")
      (node (ref "C2") (pin "1") (pinfunction "1_1") (pintype "passive"))
      (node (ref "IC12") (pin "8") (pinfunction "VCC_8") (pintype "input"))
      (node (ref "R258") (pin "1") (pinfunction "1_1") (pintype "passive"))
    )
    (net (code "293") (name "Net-(IC14-I{slash}O2)") (class "Default")
      (node (ref "C25") (pin "1") (pinfunction "1_1") (pintype "passive"))
      (node (ref "IC14") (pin "3") (pinfunction "I/O2_3") (pintype "passive"))
      (node (ref "R76") (pin "2") (pinfunction "2_2") (pintype "passive"))
      (node (ref "TP55") (pin "P$1") (pinfunction "TP_P$1") (pintype "input"))
    )
    (net (code "294") (name "Net-(IC14-I{slash}O3)") (class "Default")
      (node (ref "C75") (pin "1") (pinfunction "1_1") (pintype "passive"))
      (node (ref "IC14") (pin "4") (pinfunction "I/O3_4") (pintype "passive"))
      (node (ref "R441") (pin "1") (pinfunction "1_1") (pintype "passive"))
      (node (ref "R49") (pin "2") (pinfunction "2_2") (pintype "passive"))
    )
    (net (code "295") (name "Net-(IC15-A)") (class "Default")
      (node (ref "C175") (pin "-") (pinfunction "-_-") (pintype "passive"))
      (node (ref "C176") (pin "+") (pinfunction "+_+") (pintype "passive"))
      (node (ref "C199") (pin "2") (pinfunction "2_2") (pintype "passive"))
      (node (ref "IC15") (pin "5") (pinfunction "A_5") (pintype "input"))
      (node (ref "IC39") (pin "3") (pinfunction "A_3") (pintype "input"))
      (node (ref "R397") (pin "2") (pinfunction "2_2") (pintype "passive"))
      (node (ref "R399") (pin "2") (pinfunction "2_2") (pintype "passive"))
      (node (ref "R403") (pin "1") (pinfunction "1_1") (pintype "passive"))
      (node (ref "R498") (pin "1") (pinfunction "1_1") (pintype "passive"))
      (node (ref "R499") (pin "1") (pinfunction "1_1") (pintype "passive"))
      (node (ref "T45") (pin "2") (pinfunction "S_2") (pintype "passive"))
      (node (ref "TP59") (pin "P$1") (pinfunction "TP_P$1") (pintype "input"))
    )
    (net (code "296") (name "Net-(IC15-C)") (class "Default")
      (node (ref "C199") (pin "1") (pinfunction "1_1") (pintype "passive"))
      (node (ref "IC15") (pin "3") (pinfunction "C_3") (pintype "bidirectional"))
      (node (ref "IC15") (pin "4") (pinfunction "REF_4") (pintype "input"))
      (node (ref "IC39") (pin "1") (pinfunction "REF_1") (pintype "input"))
      (node (ref "IC39") (pin "2") (pinfunction "C_2") (pintype "bidirectional"))
      (node (ref "IC42") (pin "6") (pinfunction "-IN_6") (pintype "input"))
      (node (ref "R402") (pin "1") (pinfunction "1_1") (pintype "passive"))
    )
    (net (code "297") (name "Net-(IC16-I{slash}O3)") (class "Default")
      (node (ref "IC16") (pin "4") (pinfunction "I/O3_4") (pintype "passive"))
      (node (ref "R247") (pin "2") (pinfunction "2_2") (pintype "passive"))
      (node (ref "X4") (pin "12") (pinfunction "12_12") (pintype "passive"))
    )
    (net (code "298") (name "Net-(IC16-I{slash}O4)") (class "Default")
      (node (ref "IC16") (pin "6") (pinfunction "I/O4_6") (pintype "passive"))
      (node (ref "R248") (pin "2") (pinfunction "2_2") (pintype "passive"))
      (node (ref "X4") (pin "14") (pinfunction "14_14") (pintype "passive"))
    )
    (net (code "299") (name "Net-(IC17-A1)") (class "Default")
      (node (ref "IC17") (pin "2") (pinfunction "A1_2") (pintype "bidirectional"))
      (node (ref "IC34") (pin "4") (pinfunction "Y_4") (pintype "output"))
      (node (ref "R261") (pin "2") (pinfunction "2_2") (pintype "passive"))
      (node (ref "R437") (pin "1") (pinfunction "1_1") (pintype "passive"))
    )
    (net (code "300") (name "Net-(IC17-A2)") (class "Default")
      (node (ref "IC17") (pin "3") (pinfunction "A2_3") (pintype "bidirectional"))
      (node (ref "IC75") (pin "4") (pinfunction "Y_4") (pintype "output"))
      (node (ref "R256") (pin "1") (pinfunction "1_1") (pintype "passive"))
      (node (ref "R262") (pin "2") (pinfunction "2_2") (pintype "passive"))
    )
    (net (code "301") (name "Net-(IC17-VCCB)") (class "Default")
      (node (ref "C27") (pin "1") (pinfunction "1_1") (pintype "passive"))
      (node (ref "IC17") (pin "8") (pinfunction "VCCB_8") (pintype "input"))
      (node (ref "R315") (pin "1") (pinfunction "1_1") (pintype "passive"))
    )
    (net (code "302") (name "Net-(IC19-CRFILT)") (class "Default")
      (node (ref "C156") (pin "1") (pinfunction "1_1") (pintype "passive"))
      (node (ref "IC19") (pin "14") (pinfunction "CRFILT_14") (pintype "input"))
    )
    (net (code "303") (name "Net-(IC19-HS_IND{slash}CFG_SEL1)") (class "Default")
      (node (ref "IC19") (pin "25") (pinfunction "HS_IND/CFG_SEL1_25") (pintype "bidirectional"))
      (node (ref "R95") (pin "2") (pinfunction "2_2") (pintype "passive"))
    )
    (net (code "304") (name "Net-(IC19-PLLFILT)") (class "Default")
      (node (ref "C155") (pin "1") (pinfunction "1_1") (pintype "passive"))
      (node (ref "IC19") (pin "34") (pinfunction "PLLFILT_34") (pintype "input"))
    )
    (net (code "305") (name "Net-(IC19-RBIAS)") (class "Default")
      (node (ref "IC19") (pin "35") (pinfunction "RBIAS_35") (pintype "input"))
      (node (ref "R9") (pin "1") (pinfunction "1_1") (pintype "passive"))
    )
    (net (code "306") (name "Net-(IC19-SCL{slash}SMBCLK{slash}CFG_SEL0)") (class "Default")
      (node (ref "IC19") (pin "24") (pinfunction "SCL/SMBCLK/CFG_SEL0_24") (pintype "bidirectional"))
      (node (ref "R157") (pin "2") (pinfunction "2_2") (pintype "passive"))
    )
    (net (code "307") (name "Net-(IC19-SDA{slash}SMBDATA{slash}NON_REM1)") (class "Default")
      (node (ref "IC19") (pin "22") (pinfunction "SDA/SMBDATA/NON_REM1_22") (pintype "bidirectional"))
      (node (ref "R158") (pin "2") (pinfunction "2_2") (pintype "passive"))
    )
    (net (code "308") (name "Net-(IC19-SUSP_IND{slash}LOCAL_PWR{slash}NON_REM0)") (class "Default")
      (node (ref "IC19") (pin "28") (pinfunction "SUSP_IND/LOCAL_PWR/NON_REM0_28") (pintype "bidirectional"))
      (node (ref "R159") (pin "2") (pinfunction "2_2") (pintype "passive"))
    )
    (net (code "309") (name "Net-(IC19-USBDM_UP)") (class "Default")
      (node (ref "IC19") (pin "30") (pinfunction "USBDM_UP_30") (pintype "bidirectional"))
      (node (ref "R83") (pin "2") (pinfunction "2_2") (pintype "passive"))
    )
    (net (code "310") (name "Net-(IC19-USBDP_UP)") (class "Default")
      (node (ref "IC19") (pin "31") (pinfunction "USBDP_UP_31") (pintype "bidirectional"))
      (node (ref "R160") (pin "2") (pinfunction "2_2") (pintype "passive"))
    )
    (net (code "311") (name "Net-(IC19-XTALIN{slash}CLKIN)") (class "Default")
      (node (ref "C162") (pin "1") (pinfunction "1_1") (pintype "passive"))
      (node (ref "IC19") (pin "33") (pinfunction "XTALIN/CLKIN_33") (pintype "input"))
      (node (ref "Q3") (pin "1") (pinfunction "C1_1") (pintype "bidirectional"))
    )
    (net (code "312") (name "Net-(IC19-XTALOUT)") (class "Default")
      (node (ref "C163") (pin "2") (pinfunction "2_2") (pintype "passive"))
      (node (ref "IC19") (pin "32") (pinfunction "XTALOUT_32") (pintype "output"))
      (node (ref "Q3") (pin "3") (pinfunction "C2_3") (pintype "bidirectional"))
    )
    (net (code "313") (name "Net-(IC20A-OSC32_IN{slash}PC14)") (class "Default")
      (node (ref "C295") (pin "1") (pinfunction "1_1") (pintype "passive"))
      (node (ref "IC20") (pin "8") (pinfunction "OSC32_IN/PC14_8") (pintype "bidirectional"))
      (node (ref "Q2") (pin "1") (pinfunction "1_1") (pintype "passive"))
    )
    (net (code "314") (name "Net-(IC20A-OSC32_OUT{slash}PC15)") (class "Default")
      (node (ref "C296") (pin "1") (pinfunction "1_1") (pintype "passive"))
      (node (ref "IC20") (pin "9") (pinfunction "OSC32_OUT/PC15_9") (pintype "bidirectional"))
      (node (ref "Q2") (pin "2") (pinfunction "2_2") (pintype "passive"))
    )
    (net (code "315") (name "Net-(IC20A-OSC_IN{slash}PF0)") (class "Default")
      (node (ref "C102") (pin "1") (pinfunction "1_1") (pintype "passive"))
      (node (ref "IC20") (pin "12") (pinfunction "OSC_IN/PF0_12") (pintype "bidirectional"))
      (node (ref "Q1") (pin "1") (pinfunction "C1_1") (pintype "bidirectional"))
    )
    (net (code "316") (name "Net-(IC20A-OSC_OUT{slash}PF1)") (class "Default")
      (node (ref "IC20") (pin "13") (pinfunction "OSC_OUT/PF1_13") (pintype "bidirectional"))
      (node (ref "R296") (pin "2") (pinfunction "2_2") (pintype "passive"))
    )
    (net (code "317") (name "Net-(IC20A-PF2)") (class "Default")
      (node (ref "IC20") (pin "19") (pinfunction "PF2_19") (pintype "bidirectional"))
      (node (ref "R331") (pin "2") (pinfunction "2_2") (pintype "passive"))
    )
    (net (code "318") (name "Net-(IC20A-PF9)") (class "Default")
      (node (ref "IC20") (pin "10") (pinfunction "PF9_10") (pintype "bidirectional"))
      (node (ref "R19") (pin "2") (pinfunction "2_2") (pintype "passive"))
    )
    (net (code "319") (name "Net-(IC20A-PF10)") (class "Default")
      (node (ref "IC20") (pin "11") (pinfunction "PF10_11") (pintype "bidirectional"))
      (node (ref "R221") (pin "2") (pinfunction "2_2") (pintype "passive"))
    )
    (net (code "320") (name "Net-(IC20A-VBAT)") (class "Default")
      (node (ref "C188") (pin "1") (pinfunction "1_1") (pintype "passive"))
      (node (ref "C189") (pin "1") (pinfunction "1_1") (pintype "passive"))
      (node (ref "C190") (pin "1") (pinfunction "1_1") (pintype "passive"))
      (node (ref "C191") (pin "1") (pinfunction "1_1") (pintype "passive"))
      (node (ref "C192") (pin "1") (pinfunction "1_1") (pintype "passive"))
      (node (ref "C193") (pin "1") (pinfunction "1_1") (pintype "passive"))
      (node (ref "C78") (pin "1") (pinfunction "1_1") (pintype "passive"))
      (node (ref "IC20") (pin "100") (pinfunction "VDD5_100") (pintype "input"))
      (node (ref "IC20") (pin "24") (pinfunction "VDD1_24") (pintype "input"))
      (node (ref "IC20") (pin "36") (pinfunction "VREF+/VREFBUF_OUT_36") (pintype "input"))
      (node (ref "IC20") (pin "37") (pinfunction "VDDA_37") (pintype "input"))
      (node (ref "IC20") (pin "49") (pinfunction "VDD2_49") (pintype "input"))
      (node (ref "IC20") (pin "6") (pinfunction "VBAT_6") (pintype "input"))
      (node (ref "IC20") (pin "64") (pinfunction "VDD3_64") (pintype "input"))
      (node (ref "IC20") (pin "75") (pinfunction "VDD4_75") (pintype "input"))
      (node (ref "L32") (pin "2") (pinfunction "2_2") (pintype "passive"))
    )
    (net (code "321") (name "Net-(IC20B-PA1)") (class "Default")
      (node (ref "IC20") (pin "21") (pinfunction "PA1_21") (pintype "bidirectional"))
      (node (ref "R541") (pin "2") (pinfunction "2_2") (pintype "passive"))
    )
    (net (code "322") (name "Net-(IC20B-PA4)") (class "Default")
      (node (ref "IC20") (pin "26") (pinfunction "PA4_26") (pintype "bidirectional"))
      (node (ref "R55") (pin "2") (pinfunction "2_2") (pintype "passive"))
    )
    (net (code "323") (name "Net-(IC20B-PA8)") (class "Default")
      (node (ref "IC20") (pin "69") (pinfunction "PA8_69") (pintype "bidirectional"))
      (node (ref "R475") (pin "2") (pinfunction "2_2") (pintype "passive"))
    )
    (net (code "324") (name "Net-(IC20B-PA9)") (class "Default")
      (node (ref "IC20") (pin "70") (pinfunction "PA9_70") (pintype "bidirectional"))
      (node (ref "R476") (pin "2") (pinfunction "2_2") (pintype "passive"))
    )
    (net (code "325") (name "Net-(IC20B-PA10)") (class "Default")
      (node (ref "IC20") (pin "71") (pinfunction "PA10_71") (pintype "bidirectional"))
      (node (ref "R477") (pin "2") (pinfunction "2_2") (pintype "passive"))
    )
    (net (code "326") (name "Net-(IC20B-PA11)") (class "Default")
      (node (ref "IC20") (pin "72") (pinfunction "PA11_72") (pintype "bidirectional"))
      (node (ref "R478") (pin "2") (pinfunction "2_2") (pintype "passive"))
    )
    (net (code "327") (name "Net-(IC20B-PA15)") (class "Default")
      (node (ref "IC20") (pin "78") (pinfunction "PA15_78") (pintype "bidirectional"))
      (node (ref "R43") (pin "2") (pinfunction "2_2") (pintype "passive"))
    )
    (net (code "328") (name "Net-(IC20C-PB0)") (class "Default")
      (node (ref "IC20") (pin "32") (pinfunction "PB0_32") (pintype "bidirectional"))
      (node (ref "R436") (pin "2") (pinfunction "2_2") (pintype "passive"))
    )
    (net (code "329") (name "Net-(IC20C-PB1)") (class "Default")
      (node (ref "IC20") (pin "33") (pinfunction "PB1_33") (pintype "bidirectional"))
      (node (ref "R259") (pin "2") (pinfunction "2_2") (pintype "passive"))
    )
    (net (code "330") (name "Net-(IC20C-PB2)") (class "Default")
      (node (ref "IC20") (pin "34") (pinfunction "PB2_34") (pintype "bidirectional"))
      (node (ref "R150") (pin "2") (pinfunction "2_2") (pintype "passive"))
    )
    (net (code "331") (name "Net-(IC20C-PB3)") (class "Default")
      (node (ref "IC20") (pin "90") (pinfunction "PB3_90") (pintype "bidirectional"))
      (node (ref "R288") (pin "2") (pinfunction "2_2") (pintype "passive"))
      (node (ref "R54") (pin "2") (pinfunction "2_2") (pintype "passive"))
    )
    (net (code "332") (name "Net-(IC20C-PB4)") (class "Default")
      (node (ref "IC20") (pin "91") (pinfunction "PB4_91") (pintype "bidirectional"))
      (node (ref "R231") (pin "2") (pinfunction "2_2") (pintype "passive"))
    )
    (net (code "333") (name "Net-(IC20C-PB5)") (class "Default")
      (node (ref "IC20") (pin "92") (pinfunction "PB5_92") (pintype "bidirectional"))
      (node (ref "R473") (pin "2") (pinfunction "2_2") (pintype "passive"))
    )
    (net (code "334") (name "Net-(IC20C-PB6)") (class "Default")
      (node (ref "IC20") (pin "93") (pinfunction "PB6_93") (pintype "bidirectional"))
      (node (ref "R233") (pin "2") (pinfunction "2_2") (pintype "passive"))
    )
    (net (code "335") (name "Net-(IC20C-PB8)") (class "Default")
      (node (ref "IC20") (pin "95") (pinfunction "PB8_95") (pintype "bidirectional"))
      (node (ref "R149") (pin "2") (pinfunction "2_2") (pintype "passive"))
    )
    (net (code "336") (name "Net-(IC20C-PB9)") (class "Default")
      (node (ref "IC20") (pin "96") (pinfunction "PB9_96") (pintype "bidirectional"))
      (node (ref "R45") (pin "2") (pinfunction "2_2") (pintype "passive"))
    )
    (net (code "337") (name "Net-(IC20C-PB13)") (class "Default")
      (node (ref "IC20") (pin "52") (pinfunction "PB13_52") (pintype "bidirectional"))
      (node (ref "R564") (pin "2") (pinfunction "2_2") (pintype "passive"))
    )
    (net (code "338") (name "Net-(IC20C-PB14)") (class "Default")
      (node (ref "IC20") (pin "53") (pinfunction "PB14_53") (pintype "bidirectional"))
      (node (ref "R434") (pin "2") (pinfunction "2_2") (pintype "passive"))
    )
    (net (code "339") (name "Net-(IC20C-PB15)") (class "Default")
      (node (ref "IC20") (pin "54") (pinfunction "PB15_54") (pintype "bidirectional"))
      (node (ref "R435") (pin "2") (pinfunction "2_2") (pintype "passive"))
    )
    (net (code "340") (name "Net-(IC20D-PC0)") (class "Default")
      (node (ref "IC20") (pin "15") (pinfunction "PC0_15") (pintype "bidirectional"))
      (node (ref "R448") (pin "2") (pinfunction "2_2") (pintype "passive"))
    )
    (net (code "341") (name "Net-(IC20D-PC4)") (class "Default")
      (node (ref "IC20") (pin "30") (pinfunction "PC4_30") (pintype "bidirectional"))
      (node (ref "R243") (pin "2") (pinfunction "2_2") (pintype "passive"))
    )
    (net (code "342") (name "Net-(IC20D-PC6)") (class "Default")
      (node (ref "IC20") (pin "65") (pinfunction "PC6_65") (pintype "bidirectional"))
      (node (ref "R216") (pin "2") (pinfunction "2_2") (pintype "passive"))
    )
    (net (code "343") (name "Net-(IC20D-PC7)") (class "Default")
      (node (ref "IC20") (pin "66") (pinfunction "PC7_66") (pintype "bidirectional"))
      (node (ref "R554") (pin "2") (pinfunction "2_2") (pintype "passive"))
    )
    (net (code "344") (name "Net-(IC20D-PC8)") (class "Default")
      (node (ref "IC20") (pin "67") (pinfunction "PC8_67") (pintype "bidirectional"))
      (node (ref "R190") (pin "2") (pinfunction "2_2") (pintype "passive"))
    )
    (net (code "345") (name "Net-(IC20D-PC9)") (class "Default")
      (node (ref "IC20") (pin "68") (pinfunction "PC9_68") (pintype "bidirectional"))
      (node (ref "R136") (pin "2") (pinfunction "2_2") (pintype "passive"))
    )
    (net (code "346") (name "Net-(IC20D-PC12)") (class "Default")
      (node (ref "IC20") (pin "81") (pinfunction "PC12_81") (pintype "bidirectional"))
      (node (ref "R53") (pin "2") (pinfunction "2_2") (pintype "passive"))
    )
    (net (code "347") (name "Net-(IC20E-PD0)") (class "Default")
      (node (ref "IC20") (pin "82") (pinfunction "PD0_82") (pintype "bidirectional"))
      (node (ref "R472") (pin "2") (pinfunction "2_2") (pintype "passive"))
    )
    (net (code "348") (name "Net-(IC20E-PD1)") (class "Default")
      (node (ref "IC20") (pin "83") (pinfunction "PD1_83") (pintype "bidirectional"))
      (node (ref "R191") (pin "2") (pinfunction "2_2") (pintype "passive"))
    )
    (net (code "349") (name "Net-(IC20E-PD2)") (class "Default")
      (node (ref "IC20") (pin "84") (pinfunction "PD2_84") (pintype "bidirectional"))
      (node (ref "R218") (pin "2") (pinfunction "2_2") (pintype "passive"))
    )
    (net (code "350") (name "Net-(IC20E-PD3)") (class "Default")
      (node (ref "IC20") (pin "85") (pinfunction "PD3_85") (pintype "bidirectional"))
      (node (ref "R230") (pin "2") (pinfunction "2_2") (pintype "passive"))
      (node (ref "R321") (pin "2") (pinfunction "2_2") (pintype "passive"))
      (node (ref "R479") (pin "2") (pinfunction "2_2") (pintype "passive"))
    )
    (net (code "351") (name "Net-(IC20E-PD5)") (class "Default")
      (node (ref "IC20") (pin "87") (pinfunction "PD5_87") (pintype "bidirectional"))
      (node (ref "R176") (pin "2") (pinfunction "2_2") (pintype "passive"))
    )
    (net (code "352") (name "Net-(IC20E-PD6)") (class "Default")
      (node (ref "IC20") (pin "88") (pinfunction "PD6_88") (pintype "bidirectional"))
      (node (ref "R177") (pin "2") (pinfunction "2_2") (pintype "passive"))
    )
    (net (code "353") (name "Net-(IC20E-PD8)") (class "Default")
      (node (ref "IC20") (pin "55") (pinfunction "PD8_55") (pintype "bidirectional"))
      (node (ref "R241") (pin "2") (pinfunction "2_2") (pintype "passive"))
    )
    (net (code "354") (name "Net-(IC20E-PD15)") (class "Default")
      (node (ref "IC20") (pin "62") (pinfunction "PD15_62") (pintype "bidirectional"))
      (node (ref "R57") (pin "2") (pinfunction "2_2") (pintype "passive"))
    )
    (net (code "355") (name "Net-(IC20F-PE0)") (class "Default")
      (node (ref "IC20") (pin "97") (pinfunction "PE0_97") (pintype "bidirectional"))
      (node (ref "R195") (pin "2") (pinfunction "2_2") (pintype "passive"))
    )
    (net (code "356") (name "Net-(IC20F-PE1)") (class "Default")
      (node (ref "IC20") (pin "98") (pinfunction "PE1_98") (pintype "bidirectional"))
      (node (ref "R237") (pin "2") (pinfunction "2_2") (pintype "passive"))
    )
    (net (code "357") (name "Net-(IC20F-PE2)") (class "Default")
      (node (ref "IC20") (pin "1") (pinfunction "PE2_1") (pintype "bidirectional"))
      (node (ref "R432") (pin "2") (pinfunction "2_2") (pintype "passive"))
    )
    (net (code "358") (name "Net-(IC20F-PE3)") (class "Default")
      (node (ref "IC20") (pin "2") (pinfunction "PE3_2") (pintype "bidirectional"))
      (node (ref "R234") (pin "2") (pinfunction "2_2") (pintype "passive"))
    )
    (net (code "359") (name "Net-(IC20F-PE4)") (class "Default")
      (node (ref "IC20") (pin "3") (pinfunction "PE4_3") (pintype "bidirectional"))
      (node (ref "R37") (pin "2") (pinfunction "2_2") (pintype "passive"))
    )
    (net (code "360") (name "Net-(IC20F-PE5)") (class "Default")
      (node (ref "IC20") (pin "4") (pinfunction "PE5_4") (pintype "bidirectional"))
      (node (ref "R433") (pin "2") (pinfunction "2_2") (pintype "passive"))
    )
    (net (code "361") (name "Net-(IC20F-PE6)") (class "Default")
      (node (ref "IC20") (pin "5") (pinfunction "PE6_5") (pintype "bidirectional"))
      (node (ref "R20") (pin "2") (pinfunction "2_2") (pintype "passive"))
    )
    (net (code "362") (name "Net-(IC20F-PE8)") (class "Default")
      (node (ref "IC20") (pin "39") (pinfunction "PE8_39") (pintype "bidirectional"))
      (node (ref "R326") (pin "2") (pinfunction "2_2") (pintype "passive"))
    )
    (net (code "363") (name "Net-(IC20F-PE9)") (class "Default")
      (node (ref "IC20") (pin "40") (pinfunction "PE9_40") (pintype "bidirectional"))
      (node (ref "R273") (pin "2") (pinfunction "2_2") (pintype "passive"))
    )
    (net (code "364") (name "Net-(IC20F-PE10)") (class "Default")
      (node (ref "IC20") (pin "41") (pinfunction "PE10_41") (pintype "bidirectional"))
      (node (ref "R17") (pin "2") (pinfunction "2_2") (pintype "passive"))
    )
    (net (code "365") (name "Net-(IC20F-PE12)") (class "Default")
      (node (ref "IC20") (pin "43") (pinfunction "PE12_43") (pintype "bidirectional"))
      (node (ref "R271") (pin "2") (pinfunction "2_2") (pintype "passive"))
    )
    (net (code "366") (name "Net-(IC20F-PE13)") (class "Default")
      (node (ref "IC20") (pin "44") (pinfunction "PE13_44") (pintype "bidirectional"))
      (node (ref "R239") (pin "2") (pinfunction "2_2") (pintype "passive"))
    )
    (net (code "367") (name "Net-(IC20F-PE14)") (class "Default")
      (node (ref "IC20") (pin "45") (pinfunction "PE14_45") (pintype "bidirectional"))
      (node (ref "R332") (pin "1") (pinfunction "1_1") (pintype "passive"))
    )
    (net (code "368") (name "Net-(IC20F-PE15)") (class "Default")
      (node (ref "IC20") (pin "46") (pinfunction "PE15_46") (pintype "bidirectional"))
      (node (ref "R274") (pin "2") (pinfunction "2_2") (pintype "passive"))
    )
    (net (code "369") (name "Net-(IC21-A)") (class "Default")
      (node (ref "C176") (pin "-") (pinfunction "-_-") (pintype "passive"))
      (node (ref "C177") (pin "+") (pinfunction "+_+") (pintype "passive"))
      (node (ref "C198") (pin "2") (pinfunction "2_2") (pintype "passive"))
      (node (ref "IC21") (pin "5") (pinfunction "A_5") (pintype "input"))
      (node (ref "IC38") (pin "3") (pinfunction "A_3") (pintype "input"))
      (node (ref "R392") (pin "2") (pinfunction "2_2") (pintype "passive"))
      (node (ref "R394") (pin "2") (pinfunction "2_2") (pintype "passive"))
      (node (ref "R398") (pin "1") (pinfunction "1_1") (pintype "passive"))
      (node (ref "R494") (pin "1") (pinfunction "1_1") (pintype "passive"))
      (node (ref "R495") (pin "1") (pinfunction "1_1") (pintype "passive"))
      (node (ref "T44") (pin "2") (pinfunction "S_2") (pintype "passive"))
      (node (ref "TP58") (pin "P$1") (pinfunction "TP_P$1") (pintype "input"))
    )
    (net (code "370") (name "Net-(IC21-C)") (class "Default")
      (node (ref "C198") (pin "1") (pinfunction "1_1") (pintype "passive"))
      (node (ref "IC21") (pin "3") (pinfunction "C_3") (pintype "bidirectional"))
      (node (ref "IC21") (pin "4") (pinfunction "REF_4") (pintype "input"))
      (node (ref "IC38") (pin "1") (pinfunction "REF_1") (pintype "input"))
      (node (ref "IC38") (pin "2") (pinfunction "C_2") (pintype "bidirectional"))
      (node (ref "IC42") (pin "2") (pinfunction "-IN_2") (pintype "input"))
      (node (ref "R397") (pin "1") (pinfunction "1_1") (pintype "passive"))
    )
    (net (code "371") (name "Net-(IC22-RESET_N)") (class "Default")
      (node (ref "C37") (pin "1") (pinfunction "1_1") (pintype "passive"))
      (node (ref "IC22") (pin "9") (pinfunction "RESET_N_9") (pintype "input"))
      (node (ref "R27") (pin "1") (pinfunction "1_1") (pintype "passive"))
    )
    (net (code "372") (name "Net-(IC22-RF_IN)") (class "Default")
      (node (ref "IC22") (pin "11") (pinfunction "RF_IN_11") (pintype "input"))
      (node (ref "L40") (pin "1") (pinfunction "1_1") (pintype "passive"))
      (node (ref "X14") (pin "C") (pinfunction "C_C") (pintype "passive"))
    )
    (net (code "373") (name "Net-(IC22-RXD)") (class "Default")
      (node (ref "IC22") (pin "3") (pinfunction "RXD_3") (pintype "input"))
      (node (ref "R13") (pin "2") (pinfunction "2_2") (pintype "passive"))
    )
    (net (code "374") (name "Net-(IC22-TXD)") (class "Default")
      (node (ref "IC22") (pin "2") (pinfunction "TXD_2") (pintype "output"))
      (node (ref "R14") (pin "2") (pinfunction "2_2") (pintype "passive"))
    )
    (net (code "375") (name "Net-(IC22-VCC)") (class "Default")
      (node (ref "C141") (pin "1") (pinfunction "1_1") (pintype "passive"))
      (node (ref "IC22") (pin "6") (pinfunction "V_BCKP_6") (pintype "input"))
      (node (ref "IC22") (pin "7") (pinfunction "VCC_IO_7") (pintype "input"))
      (node (ref "IC22") (pin "8") (pinfunction "VCC_8") (pintype "input"))
      (node (ref "R10") (pin "1") (pinfunction "1_1") (pintype "passive"))
    )
    (net (code "376") (name "Net-(IC22-VCC_RF)") (class "Default")
      (node (ref "IC22") (pin "14") (pinfunction "VCC_RF_14") (pintype "output"))
      (node (ref "R26") (pin "1") (pinfunction "1_1") (pintype "passive"))
    )
    (net (code "377") (name "Net-(IC23-NC)") (class "Default")
      (node (ref "IC23") (pin "1") (pinfunction "NC_1") (pintype "passive"))
      (node (ref "R228") (pin "2") (pinfunction "2_2") (pintype "passive"))
      (node (ref "R229") (pin "1") (pinfunction "1_1") (pintype "passive"))
    )
    (net (code "378") (name "Net-(IC23-VCC)") (class "Default")
      (node (ref "C48") (pin "1") (pinfunction "1_1") (pintype "passive"))
      (node (ref "IC23") (pin "5") (pinfunction "VCC_5") (pintype "input"))
      (node (ref "R200") (pin "2") (pinfunction "2_2") (pintype "passive"))
    )
    (net (code "379") (name "Net-(IC23-Y)") (class "Default")
      (node (ref "IC23") (pin "4") (pinfunction "Y_4") (pintype "output"))
      (node (ref "R226") (pin "1") (pinfunction "1_1") (pintype "passive"))
    )
    (net (code "380") (name "Net-(IC24-ADR{slash}~{FAULT})") (class "Default")
      (node (ref "IC24") (pin "3") (pinfunction "ADR/~{FAULT}_3") (pintype "bidirectional"))
      (node (ref "R282") (pin "1") (pinfunction "1_1") (pintype "passive"))
      (node (ref "R552") (pin "1") (pinfunction "1_1") (pintype "passive"))
    )
    (net (code "381") (name "Net-(IC24-AVDD)") (class "Default")
      (node (ref "C129") (pin "1") (pinfunction "1_1") (pintype "passive"))
      (node (ref "IC24") (pin "13") (pinfunction "AVDD_13") (pintype "output"))
    )
    (net (code "382") (name "Net-(IC24-BST_A+)") (class "Default")
      (node (ref "C241") (pin "1") (pinfunction "1_1") (pintype "passive"))
      (node (ref "C242") (pin "1") (pinfunction "1_1") (pintype "passive"))
      (node (ref "IC24") (pin "25") (pinfunction "BST_A+_25") (pintype "input"))
    )
    (net (code "383") (name "Net-(IC24-BST_A-)") (class "Default")
      (node (ref "C239") (pin "1") (pinfunction "1_1") (pintype "passive"))
      (node (ref "C240") (pin "1") (pinfunction "1_1") (pintype "passive"))
      (node (ref "IC24") (pin "22") (pinfunction "BST_A-_22") (pintype "input"))
    )
    (net (code "384") (name "Net-(IC24-BST_B+)") (class "Default")
      (node (ref "C123") (pin "1") (pinfunction "1_1") (pintype "passive"))
      (node (ref "C124") (pin "1") (pinfunction "1_1") (pintype "passive"))
      (node (ref "IC24") (pin "18") (pinfunction "BST_B+_18") (pintype "input"))
    )
    (net (code "385") (name "Net-(IC24-BST_B-)") (class "Default")
      (node (ref "C121") (pin "1") (pinfunction "1_1") (pintype "passive"))
      (node (ref "C122") (pin "1") (pinfunction "1_1") (pintype "passive"))
      (node (ref "IC24") (pin "21") (pinfunction "BST_B-_21") (pintype "input"))
    )
    (net (code "386") (name "Net-(IC24-DVDD)") (class "Default")
      (node (ref "C132") (pin "1") (pinfunction "1_1") (pintype "passive"))
      (node (ref "IC24") (pin "2") (pinfunction "DVDD_2") (pintype "input"))
      (node (ref "R265") (pin "1") (pinfunction "1_1") (pintype "passive"))
    )
    (net (code "387") (name "Net-(IC24-OUT_A+)") (class "Default")
      (node (ref "C241") (pin "2") (pinfunction "2_2") (pintype "passive"))
      (node (ref "C242") (pin "2") (pinfunction "2_2") (pintype "passive"))
      (node (ref "IC24") (pin "26") (pinfunction "OUT_A+_26") (pintype "output"))
      (node (ref "L8") (pin "DOT") (pinfunction "DOT_DOT") (pintype "passive"))
    )
    (net (code "388") (name "Net-(IC24-OUT_A-)") (class "Default")
      (node (ref "C239") (pin "2") (pinfunction "2_2") (pintype "passive"))
      (node (ref "C240") (pin "2") (pinfunction "2_2") (pintype "passive"))
      (node (ref "IC24") (pin "23") (pinfunction "OUT_A-_23") (pintype "output"))
      (node (ref "L6") (pin "DOT") (pinfunction "DOT_DOT") (pintype "passive"))
    )
    (net (code "389") (name "Net-(IC24-OUT_B+)") (class "Default")
      (node (ref "C123") (pin "2") (pinfunction "2_2") (pintype "passive"))
      (node (ref "C124") (pin "2") (pinfunction "2_2") (pintype "passive"))
      (node (ref "IC24") (pin "17") (pinfunction "OUT_B+_17") (pintype "output"))
      (node (ref "L12") (pin "DOT") (pinfunction "DOT_DOT") (pintype "passive"))
    )
    (net (code "390") (name "Net-(IC24-OUT_B-)") (class "Default")
      (node (ref "C121") (pin "2") (pinfunction "2_2") (pintype "passive"))
      (node (ref "C122") (pin "2") (pinfunction "2_2") (pintype "passive"))
      (node (ref "IC24") (pin "20") (pinfunction "OUT_B-_20") (pintype "output"))
      (node (ref "L13") (pin "DOT") (pinfunction "DOT_DOT") (pintype "passive"))
    )
    (net (code "391") (name "Net-(IC24-SDA)") (class "Default")
      (node (ref "C287") (pin "1") (pinfunction "1_1") (pintype "passive"))
      (node (ref "IC24") (pin "10") (pinfunction "SDA_10") (pintype "bidirectional"))
      (node (ref "R266") (pin "2") (pinfunction "2_2") (pintype "passive"))
    )
    (net (code "392") (name "Net-(IC24-SDOUT)") (class "Default")
      (node (ref "IC24") (pin "9") (pinfunction "SDOUT_9") (pintype "output"))
      (node (ref "R284") (pin "2") (pinfunction "2_2") (pintype "passive"))
    )
    (net (code "393") (name "Net-(IC24-VR_DIG)") (class "Default")
      (node (ref "C131") (pin "1") (pinfunction "1_1") (pintype "passive"))
      (node (ref "IC24") (pin "4") (pinfunction "VR_DIG_4") (pintype "output"))
    )
    (net (code "394") (name "Net-(IC24-~{PDN})") (class "Default")
      (node (ref "IC24") (pin "12") (pinfunction "~{PDN}_12") (pintype "input"))
      (node (ref "R40") (pin "1") (pinfunction "1_1") (pintype "passive"))
    )
    (net (code "395") (name "Net-(IC25-BST)") (class "Default")
      (node (ref "C238") (pin "2") (pinfunction "2_2") (pintype "passive"))
      (node (ref "IC25") (pin "6") (pinfunction "BST_6") (pintype "input"))
    )
    (net (code "396") (name "Net-(IC25-FB)") (class "Default")
      (node (ref "C270") (pin "2") (pinfunction "2_2") (pintype "passive"))
      (node (ref "IC25") (pin "8") (pinfunction "FB_8") (pintype "input"))
      (node (ref "R275") (pin "1") (pinfunction "1_1") (pintype "passive"))
      (node (ref "R279") (pin "1") (pinfunction "1_1") (pintype "passive"))
      (node (ref "R293") (pin "2") (pinfunction "2_2") (pintype "passive"))
    )
    (net (code "397") (name "Net-(IC25-RT)") (class "Default")
      (node (ref "IC25") (pin "1") (pinfunction "RT_1") (pintype "input"))
      (node (ref "R310") (pin "2") (pinfunction "2_2") (pintype "passive"))
    )
    (net (code "398") (name "Net-(IC25-SS)") (class "Default")
      (node (ref "C269") (pin "1") (pinfunction "1_1") (pintype "passive"))
      (node (ref "IC25") (pin "7") (pinfunction "SS_7") (pintype "input"))
    )
    (net (code "399") (name "Net-(IC25-SW)") (class "Default")
      (node (ref "IC25") (pin "5") (pinfunction "SW_5") (pintype "bidirectional"))
      (node (ref "L19") (pin "DOT") (pinfunction "DOT_DOT") (pintype "passive"))
      (node (ref "R314") (pin "2") (pinfunction "2_2") (pintype "passive"))
    )
    (net (code "400") (name "Net-(IC25-VIN)") (class "Default")
      (node (ref "C49") (pin "1") (pinfunction "1_1") (pintype "passive"))
      (node (ref "IC25") (pin "3") (pinfunction "VIN_3") (pintype "input"))
      (node (ref "L20") (pin "1") (pinfunction "1_1") (pintype "passive"))
    )
    (net (code "401") (name "Net-(IC27-A)") (class "Default")
      (node (ref "C177") (pin "-") (pinfunction "-_-") (pintype "passive"))
      (node (ref "C178") (pin "+") (pinfunction "+_+") (pintype "passive"))
      (node (ref "C197") (pin "2") (pinfunction "2_2") (pintype "passive"))
      (node (ref "IC27") (pin "5") (pinfunction "A_5") (pintype "input"))
      (node (ref "IC37") (pin "3") (pinfunction "A_3") (pintype "input"))
      (node (ref "R387") (pin "2") (pinfunction "2_2") (pintype "passive"))
      (node (ref "R389") (pin "2") (pinfunction "2_2") (pintype "passive"))
      (node (ref "R393") (pin "1") (pinfunction "1_1") (pintype "passive"))
      (node (ref "R395") (pin "1") (pinfunction "1_1") (pintype "passive"))
      (node (ref "R400") (pin "1") (pinfunction "1_1") (pintype "passive"))
      (node (ref "T40") (pin "2") (pinfunction "S_2") (pintype "passive"))
      (node (ref "TP57") (pin "P$1") (pinfunction "TP_P$1") (pintype "input"))
    )
    (net (code "402") (name "Net-(IC27-C)") (class "Default")
      (node (ref "C197") (pin "1") (pinfunction "1_1") (pintype "passive"))
      (node (ref "IC27") (pin "3") (pinfunction "C_3") (pintype "bidirectional"))
      (node (ref "IC27") (pin "4") (pinfunction "REF_4") (pintype "input"))
      (node (ref "IC37") (pin "1") (pinfunction "REF_1") (pintype "input"))
      (node (ref "IC37") (pin "2") (pinfunction "C_2") (pintype "bidirectional"))
      (node (ref "IC41") (pin "6") (pinfunction "-IN_6") (pintype "input"))
      (node (ref "R392") (pin "1") (pinfunction "1_1") (pintype "passive"))
    )
    (net (code "403") (name "Net-(IC28A-+IN)") (class "Default")
      (node (ref "IC28") (pin "3") (pinfunction "+IN_3") (pintype "input"))
      (node (ref "R161") (pin "2") (pinfunction "2_2") (pintype "passive"))
      (node (ref "R71") (pin "2") (pinfunction "2_2") (pintype "passive"))
    )
    (net (code "404") (name "Net-(IC28A--IN)") (class "Default")
      (node (ref "IC28") (pin "1") (pinfunction "OUT_1") (pintype "output"))
      (node (ref "IC28") (pin "2") (pinfunction "-IN_2") (pintype "input"))
      (node (ref "R70") (pin "1") (pinfunction "1_1") (pintype "passive"))
    )
    (net (code "405") (name "Net-(IC28B-+IN)") (class "Default")
      (node (ref "IC28") (pin "5") (pinfunction "+IN_5") (pintype "input"))
      (node (ref "R151") (pin "2") (pinfunction "2_2") (pintype "passive"))
      (node (ref "R152") (pin "2") (pinfunction "2_2") (pintype "passive"))
    )
    (net (code "406") (name "Net-(IC28B--IN)") (class "Default")
      (node (ref "IC28") (pin "6") (pinfunction "-IN_6") (pintype "input"))
      (node (ref "IC28") (pin "7") (pinfunction "OUT_7") (pintype "output"))
      (node (ref "R66") (pin "1") (pinfunction "1_1") (pintype "passive"))
    )
    (net (code "407") (name "Net-(IC28C-VCC)") (class "Default")
      (node (ref "C9") (pin "1") (pinfunction "1_1") (pintype "passive"))
      (node (ref "IC28") (pin "8") (pinfunction "VCC_8") (pintype "input"))
      (node (ref "R65") (pin "1") (pinfunction "1_1") (pintype "passive"))
    )
    (net (code "408") (name "Net-(IC29A-+IN)") (class "Default")
      (node (ref "IC29") (pin "3") (pinfunction "+IN_3") (pintype "input"))
      (node (ref "R423") (pin "2") (pinfunction "2_2") (pintype "passive"))
      (node (ref "R424") (pin "2") (pinfunction "2_2") (pintype "passive"))
      (node (ref "R488") (pin "2") (pinfunction "2_2") (pintype "passive"))
    )
    (net (code "409") (name "Net-(IC29A--IN)") (class "Default")
      (node (ref "IC29") (pin "1") (pinfunction "OUT_1") (pintype "output"))
      (node (ref "IC29") (pin "2") (pinfunction "-IN_2") (pintype "input"))
      (node (ref "R421") (pin "1") (pinfunction "1_1") (pintype "passive"))
    )
    (net (code "410") (name "Net-(IC29B-+IN)") (class "Default")
      (node (ref "IC29") (pin "5") (pinfunction "+IN_5") (pintype "input"))
      (node (ref "R425") (pin "2") (pinfunction "2_2") (pintype "passive"))
      (node (ref "R426") (pin "2") (pinfunction "2_2") (pintype "passive"))
    )
    (net (code "411") (name "Net-(IC29B--IN)") (class "Default")
      (node (ref "IC29") (pin "6") (pinfunction "-IN_6") (pintype "input"))
      (node (ref "IC29") (pin "7") (pinfunction "OUT_7") (pintype "output"))
      (node (ref "R422") (pin "1") (pinfunction "1_1") (pintype "passive"))
    )
    (net (code "412") (name "Net-(IC29C-VCC)") (class "Default")
      (node (ref "C80") (pin "1") (pinfunction "1_1") (pintype "passive"))
      (node (ref "IC29") (pin "8") (pinfunction "VCC_8") (pintype "input"))
      (node (ref "R420") (pin "1") (pinfunction "1_1") (pintype "passive"))
    )
    (net (code "413") (name "Net-(IC30-A0)") (class "Default")
      (node (ref "IC30") (pin "15") (pinfunction "A0_15") (pintype "input"))
      (node (ref "R162") (pin "2") (pinfunction "2_2") (pintype "passive"))
    )
    (net (code "414") (name "Net-(IC30-A1)") (class "Default")
      (node (ref "IC30") (pin "14") (pinfunction "A1_14") (pintype "input"))
      (node (ref "R163") (pin "2") (pinfunction "2_2") (pintype "passive"))
    )
    (net (code "415") (name "Net-(IC30-EN)") (class "Default")
      (node (ref "IC30") (pin "16") (pinfunction "EN_16") (pintype "input"))
      (node (ref "R164") (pin "2") (pinfunction "2_2") (pintype "passive"))
    )
    (net (code "416") (name "Net-(IC30-VDD)") (class "Default")
      (node (ref "C96") (pin "1") (pinfunction "1_1") (pintype "passive"))
      (node (ref "IC30") (pin "12") (pinfunction "VDD_12") (pintype "input"))
      (node (ref "R278") (pin "1") (pinfunction "1_1") (pintype "passive"))
    )
    (net (code "417") (name "Net-(IC31-BST)") (class "Default")
      (node (ref "C133") (pin "1") (pinfunction "1_1") (pintype "passive"))
      (node (ref "C244") (pin "1") (pinfunction "1_1") (pintype "passive"))
      (node (ref "D15") (pin "C") (pinfunction "C_C") (pintype "passive"))
      (node (ref "IC31") (pin "20") (pinfunction "BST_20") (pintype "bidirectional"))
    )
    (net (code "418") (name "Net-(IC31-COMP)") (class "Default")
      (node (ref "C138") (pin "2") (pinfunction "2_2") (pintype "passive"))
      (node (ref "C243") (pin "1") (pinfunction "1_1") (pintype "passive"))
      (node (ref "C245") (pin "2") (pinfunction "2_2") (pintype "passive"))
      (node (ref "IC31") (pin "11") (pinfunction "COMP_11") (pintype "output"))
    )
    (net (code "419") (name "Net-(IC31-CSN)") (class "Default")
      (node (ref "C135") (pin "1") (pinfunction "1_1") (pintype "passive"))
      (node (ref "IC31") (pin "3") (pinfunction "CSN_3") (pintype "input"))
      (node (ref "R345") (pin "1") (pinfunction "1_1") (pintype "passive"))
    )
    (net (code "420") (name "Net-(IC31-CSP)") (class "Default")
      (node (ref "C135") (pin "2") (pinfunction "2_2") (pintype "passive"))
      (node (ref "IC31") (pin "4") (pinfunction "CSP_4") (pintype "input"))
      (node (ref "R346") (pin "1") (pinfunction "1_1") (pintype "passive"))
    )
    (net (code "421") (name "Net-(IC31-FB)") (class "Default")
      (node (ref "C138") (pin "1") (pinfunction "1_1") (pintype "passive"))
      (node (ref "C245") (pin "1") (pinfunction "1_1") (pintype "passive"))
      (node (ref "IC31") (pin "10") (pinfunction "FB_10") (pintype "input"))
      (node (ref "R348") (pin "2") (pinfunction "2_2") (pintype "passive"))
      (node (ref "R349") (pin "2") (pinfunction "2_2") (pintype "passive"))
      (node (ref "R510") (pin "1") (pinfunction "1_1") (pintype "passive"))
      (node (ref "R511") (pin "1") (pinfunction "1_1") (pintype "passive"))
    )
    (net (code "422") (name "Net-(IC31-HO)") (class "Default")
      (node (ref "IC31") (pin "19") (pinfunction "HO_19") (pintype "output"))
      (node (ref "R342") (pin "1") (pinfunction "1_1") (pintype "passive"))
    )
    (net (code "423") (name "Net-(IC31-LO)") (class "Default")
      (node (ref "IC31") (pin "16") (pinfunction "LO_16") (pintype "output"))
      (node (ref "R341") (pin "1") (pinfunction "1_1") (pintype "passive"))
    )
    (net (code "424") (name "Net-(IC31-MODE)") (class "Default")
      (node (ref "IC31") (pin "13") (pinfunction "MODE_13") (pintype "input"))
      (node (ref "R356") (pin "2") (pinfunction "2_2") (pintype "passive"))
      (node (ref "R380") (pin "2") (pinfunction "2_2") (pintype "passive"))
    )
    (net (code "425") (name "Net-(IC31-RES)") (class "Default")
      (node (ref "C137") (pin "1") (pinfunction "1_1") (pintype "passive"))
      (node (ref "C98") (pin "1") (pinfunction "1_1") (pintype "passive"))
      (node (ref "IC31") (pin "14") (pinfunction "RES_14") (pintype "output"))
    )
    (net (code "426") (name "Net-(IC31-SLOPE)") (class "Default")
      (node (ref "IC31") (pin "12") (pinfunction "SLOPE_12") (pintype "input"))
      (node (ref "R355") (pin "2") (pinfunction "2_2") (pintype "passive"))
    )
    (net (code "427") (name "Net-(IC31-SS)") (class "Default")
      (node (ref "C97") (pin "1") (pinfunction "1_1") (pintype "passive"))
      (node (ref "IC31") (pin "7") (pinfunction "SS_7") (pintype "input"))
    )
    (net (code "428") (name "Net-(IC31-SW)") (class "Default")
      (node (ref "C133") (pin "2") (pinfunction "2_2") (pintype "passive"))
      (node (ref "C244") (pin "2") (pinfunction "2_2") (pintype "passive"))
      (node (ref "D14") (pin "A1") (pinfunction "A_A1") (pintype "passive"))
      (node (ref "D14") (pin "A2") (pinfunction "A_A2") (pintype "passive"))
      (node (ref "IC31") (pin "18") (pinfunction "SW_18") (pintype "bidirectional"))
      (node (ref "L17") (pin "DOT") (pinfunction "DOT_DOT") (pintype "passive"))
      (node (ref "T15") (pin "D1") (pinfunction "D_D1") (pintype "passive"))
      (node (ref "T15") (pin "D10") (pinfunction "D_D10") (pintype "passive"))
      (node (ref "T15") (pin "D11") (pinfunction "D_D11") (pintype "passive"))
      (node (ref "T15") (pin "D12") (pinfunction "D_D12") (pintype "passive"))
      (node (ref "T15") (pin "D13") (pinfunction "D_D13") (pintype "passive"))
      (node (ref "T15") (pin "D14") (pinfunction "D_D14") (pintype "passive"))
      (node (ref "T15") (pin "D15") (pinfunction "D_D15") (pintype "passive"))
      (node (ref "T15") (pin "D2") (pinfunction "D_D2") (pintype "passive"))
      (node (ref "T15") (pin "D3") (pinfunction "D_D3") (pintype "passive"))
      (node (ref "T15") (pin "D4") (pinfunction "D_D4") (pintype "passive"))
      (node (ref "T15") (pin "D5") (pinfunction "D_D5") (pintype "passive"))
      (node (ref "T15") (pin "D6") (pinfunction "D_D6") (pintype "passive"))
      (node (ref "T15") (pin "D7") (pinfunction "D_D7") (pintype "passive"))
      (node (ref "T15") (pin "D8") (pinfunction "D_D8") (pintype "passive"))
      (node (ref "T15") (pin "D9") (pinfunction "D_D9") (pintype "passive"))
      (node (ref "T16") (pin "1") (pinfunction "S_1") (pintype "passive"))
      (node (ref "T16") (pin "2") (pinfunction "S_2") (pintype "passive"))
      (node (ref "T16") (pin "3") (pinfunction "S_3") (pintype "passive"))
    )
    (net (code "429") (name "Net-(IC31-SYNCIN{slash}RT)") (class "Default")
      (node (ref "IC31") (pin "8") (pinfunction "SYNCIN/RT_8") (pintype "input"))
      (node (ref "R344") (pin "2") (pinfunction "2_2") (pintype "passive"))
    )
    (net (code "430") (name "Net-(IC31-VIN)") (class "Default")
      (node (ref "C136") (pin "1") (pinfunction "1_1") (pintype "passive"))
      (node (ref "IC31") (pin "5") (pinfunction "VIN_5") (pintype "input"))
      (node (ref "R347") (pin "1") (pinfunction "1_1") (pintype "passive"))
    )
    (net (code "431") (name "Net-(IC32-NC)") (class "Default")
      (node (ref "IC32") (pin "1") (pinfunction "NC_1") (pintype "passive"))
      (node (ref "R12") (pin "1") (pinfunction "1_1") (pintype "passive"))
      (node (ref "R5") (pin "2") (pinfunction "2_2") (pintype "passive"))
    )
    (net (code "432") (name "Net-(IC32-VCC)") (class "Default")
      (node (ref "C217") (pin "1") (pinfunction "1_1") (pintype "passive"))
      (node (ref "IC32") (pin "5") (pinfunction "VCC_5") (pintype "input"))
      (node (ref "R42") (pin "2") (pinfunction "2_2") (pintype "passive"))
    )
    (net (code "433") (name "Net-(IC32-Y)") (class "Default")
      (node (ref "IC32") (pin "4") (pinfunction "Y_4") (pintype "output"))
      (node (ref "R62") (pin "1") (pinfunction "1_1") (pintype "passive"))
    )
    (net (code "434") (name "Net-(IC33-BST)") (class "Default")
      (node (ref "C221") (pin "2") (pinfunction "2_2") (pintype "passive"))
      (node (ref "IC33") (pin "6") (pinfunction "BST_6") (pintype "input"))
    )
    (net (code "435") (name "Net-(IC33-FB)") (class "Default")
      (node (ref "C283") (pin "2") (pinfunction "2_2") (pintype "passive"))
      (node (ref "IC33") (pin "8") (pinfunction "FB_8") (pintype "input"))
      (node (ref "R252") (pin "2") (pinfunction "2_2") (pintype "passive"))
      (node (ref "R300") (pin "1") (pinfunction "1_1") (pintype "passive"))
      (node (ref "R528") (pin "2") (pinfunction "2_2") (pintype "passive"))
    )
    (net (code "436") (name "Net-(IC33-RT)") (class "Default")
      (node (ref "IC33") (pin "1") (pinfunction "RT_1") (pintype "input"))
      (node (ref "R251") (pin "2") (pinfunction "2_2") (pintype "passive"))
    )
    (net (code "437") (name "Net-(IC33-SS)") (class "Default")
      (node (ref "C282") (pin "1") (pinfunction "1_1") (pintype "passive"))
      (node (ref "IC33") (pin "7") (pinfunction "SS_7") (pintype "input"))
    )
    (net (code "438") (name "Net-(IC33-SW)") (class "Default")
      (node (ref "IC33") (pin "5") (pinfunction "SW_5") (pintype "bidirectional"))
      (node (ref "L34") (pin "DOT") (pinfunction "DOT_DOT") (pintype "passive"))
      (node (ref "R137") (pin "2") (pinfunction "2_2") (pintype "passive"))
    )
    (net (code "439") (name "Net-(IC33-VIN)") (class "Default")
      (node (ref "C219") (pin "1") (pinfunction "1_1") (pintype "passive"))
      (node (ref "IC33") (pin "3") (pinfunction "VIN_3") (pintype "input"))
      (node (ref "L39") (pin "1") (pinfunction "1_1") (pintype "passive"))
    )
    (net (code "440") (name "Net-(IC34-NC)") (class "Default")
      (node (ref "IC34") (pin "1") (pinfunction "NC_1") (pintype "passive"))
      (node (ref "R542") (pin "2") (pinfunction "2_2") (pintype "passive"))
      (node (ref "R543") (pin "1") (pinfunction "1_1") (pintype "passive"))
    )
    (net (code "441") (name "Net-(IC34-VCC)") (class "Default")
      (node (ref "C291") (pin "1") (pinfunction "1_1") (pintype "passive"))
      (node (ref "IC34") (pin "5") (pinfunction "VCC_5") (pintype "input"))
      (node (ref "R531") (pin "2") (pinfunction "2_2") (pintype "passive"))
    )
    (net (code "442") (name "Net-(IC35-BTST)") (class "Default")
      (node (ref "C168") (pin "1") (pinfunction "1_1") (pintype "passive"))
      (node (ref "D20") (pin "C") (pinfunction "C_C") (pintype "passive"))
      (node (ref "IC35") (pin "16") (pinfunction "BTST_16") (pintype "bidirectional"))
    )
    (net (code "443") (name "Net-(IC35-HIDRV)") (class "Default")
      (node (ref "IC35") (pin "15") (pinfunction "HIDRV_15") (pintype "output"))
      (node (ref "R358") (pin "1") (pinfunction "1_1") (pintype "passive"))
    )
    (net (code "444") (name "Net-(IC35-ISET)") (class "Default")
      (node (ref "IC35") (pin "7") (pinfunction "ISET_7") (pintype "input"))
      (node (ref "R371") (pin "1") (pinfunction "1_1") (pintype "passive"))
      (node (ref "R372") (pin "2") (pinfunction "2_2") (pintype "passive"))
      (node (ref "R512") (pin "2") (pinfunction "2_2") (pintype "passive"))
    )
    (net (code "445") (name "Net-(IC35-LODRV)") (class "Default")
      (node (ref "IC35") (pin "13") (pinfunction "LODRV_13") (pintype "output"))
      (node (ref "R360") (pin "1") (pinfunction "1_1") (pintype "passive"))
    )
    (net (code "446") (name "Net-(IC35-PH)") (class "Default")
      (node (ref "C168") (pin "2") (pinfunction "2_2") (pintype "passive"))
      (node (ref "IC35") (pin "14") (pinfunction "PH_14") (pintype "input"))
      (node (ref "L18") (pin "DOT") (pinfunction "DOT_DOT") (pintype "passive"))
      (node (ref "T19") (pin "4") (pinfunction "S_4") (pintype "passive"))
      (node (ref "T19") (pin "S") (pinfunction "S_S") (pintype "passive"))
      (node (ref "T20") (pin "1") (pinfunction "D_1") (pintype "passive"))
      (node (ref "T20") (pin "2") (pinfunction "D_2") (pintype "passive"))
      (node (ref "T20") (pin "5") (pinfunction "D_5") (pintype "passive"))
      (node (ref "T20") (pin "6") (pinfunction "D_6") (pintype "passive"))
      (node (ref "T20") (pin "D") (pinfunction "D_D") (pintype "passive"))
    )
    (net (code "447") (name "Net-(IC35-REGN)") (class "Default")
      (node (ref "C169") (pin "1") (pinfunction "1_1") (pintype "passive"))
      (node (ref "D20") (pin "A") (pinfunction "A_A") (pintype "passive"))
      (node (ref "IC35") (pin "12") (pinfunction "REGN_12") (pintype "output"))
    )
    (net (code "448") (name "Net-(IC35-SRP)") (class "Default")
      (node (ref "C149") (pin "1") (pinfunction "1_1") (pintype "passive"))
      (node (ref "C150") (pin "1") (pinfunction "1_1") (pintype "passive"))
      (node (ref "IC35") (pin "10") (pinfunction "SRP_10") (pintype "input"))
      (node (ref "L18") (pin "NODOT") (pinfunction "NODOT_NODOT") (pintype "passive"))
      (node (ref "R367") (pin "1") (pinfunction "1_1") (pintype "passive"))
    )
    (net (code "449") (name "Net-(IC35-STAT)") (class "Default")
      (node (ref "IC35") (pin "3") (pinfunction "STAT_3") (pintype "open_collector"))
      (node (ref "R377") (pin "1") (pinfunction "1_1") (pintype "passive"))
    )
    (net (code "450") (name "Net-(IC35-TS)") (class "Default")
      (node (ref "IC35") (pin "4") (pinfunction "TS_4") (pintype "input"))
      (node (ref "R375") (pin "1") (pinfunction "1_1") (pintype "passive"))
      (node (ref "R376") (pin "2") (pinfunction "2_2") (pintype "passive"))
    )
    (net (code "451") (name "Net-(IC35-VCC)") (class "Default")
      (node (ref "C170") (pin "1") (pinfunction "1_1") (pintype "passive"))
      (node (ref "IC35") (pin "1") (pinfunction "VCC_1") (pintype "input"))
      (node (ref "R370") (pin "1") (pinfunction "1_1") (pintype "passive"))
    )
    (net (code "452") (name "Net-(IC35-VFB)") (class "Default")
      (node (ref "C167") (pin "2") (pinfunction "2_2") (pintype "passive"))
      (node (ref "IC35") (pin "8") (pinfunction "VFB_8") (pintype "input"))
      (node (ref "R369") (pin "2") (pinfunction "2_2") (pintype "passive"))
      (node (ref "R508") (pin "1") (pinfunction "1_1") (pintype "passive"))
    )
    (net (code "453") (name "Net-(IC35-~{PG})") (class "Default")
      (node (ref "IC35") (pin "5") (pinfunction "~{PG}_5") (pintype "open_collector"))
      (node (ref "R378") (pin "1") (pinfunction "1_1") (pintype "passive"))
    )
    (net (code "454") (name "Net-(IC36-C)") (class "Default")
      (node (ref "C196") (pin "1") (pinfunction "1_1") (pintype "passive"))
      (node (ref "IC36") (pin "1") (pinfunction "REF_1") (pintype "input"))
      (node (ref "IC36") (pin "2") (pinfunction "C_2") (pintype "bidirectional"))
      (node (ref "IC41") (pin "2") (pinfunction "-IN_2") (pintype "input"))
      (node (ref "IC56") (pin "3") (pinfunction "C_3") (pintype "bidirectional"))
      (node (ref "IC56") (pin "4") (pinfunction "REF_4") (pintype "input"))
      (node (ref "R387") (pin "1") (pinfunction "1_1") (pintype "passive"))
    )
    (net (code "455") (name "Net-(IC40-A)") (class "Default")
      (node (ref "C174") (pin "-") (pinfunction "-_-") (pintype "passive"))
      (node (ref "C175") (pin "+") (pinfunction "+_+") (pintype "passive"))
      (node (ref "C200") (pin "2") (pinfunction "2_2") (pintype "passive"))
      (node (ref "IC40") (pin "3") (pinfunction "A_3") (pintype "input"))
      (node (ref "IC9") (pin "5") (pinfunction "A_5") (pintype "input"))
      (node (ref "R402") (pin "2") (pinfunction "2_2") (pintype "passive"))
      (node (ref "R404") (pin "2") (pinfunction "2_2") (pintype "passive"))
      (node (ref "R408") (pin "1") (pinfunction "1_1") (pintype "passive"))
      (node (ref "R502") (pin "1") (pinfunction "1_1") (pintype "passive"))
      (node (ref "R503") (pin "1") (pinfunction "1_1") (pintype "passive"))
      (node (ref "T46") (pin "2") (pinfunction "S_2") (pintype "passive"))
      (node (ref "TP60") (pin "P$1") (pinfunction "TP_P$1") (pintype "input"))
    )
    (net (code "456") (name "Net-(IC40-C)") (class "Default")
      (node (ref "C200") (pin "1") (pinfunction "1_1") (pintype "passive"))
      (node (ref "IC40") (pin "1") (pinfunction "REF_1") (pintype "input"))
      (node (ref "IC40") (pin "2") (pinfunction "C_2") (pintype "bidirectional"))
      (node (ref "IC43") (pin "2") (pinfunction "-IN_2") (pintype "input"))
      (node (ref "IC9") (pin "3") (pinfunction "C_3") (pintype "bidirectional"))
      (node (ref "IC9") (pin "4") (pinfunction "REF_4") (pintype "input"))
      (node (ref "R407") (pin "1") (pinfunction "1_1") (pintype "passive"))
    )
    (net (code "457") (name "Net-(IC41A-+IN)") (class "Default")
      (node (ref "IC41") (pin "3") (pinfunction "+IN_3") (pintype "input"))
      (node (ref "R388") (pin "2") (pinfunction "2_2") (pintype "passive"))
      (node (ref "R389") (pin "1") (pinfunction "1_1") (pintype "passive"))
    )
    (net (code "458") (name "Net-(IC41A-OUT)") (class "Default")
      (node (ref "IC41") (pin "1") (pinfunction "OUT_1") (pintype "output"))
      (node (ref "R386") (pin "1") (pinfunction "1_1") (pintype "passive"))
    )
    (net (code "459") (name "Net-(IC41B-+IN)") (class "Default")
      (node (ref "IC41") (pin "5") (pinfunction "+IN_5") (pintype "input"))
      (node (ref "R393") (pin "2") (pinfunction "2_2") (pintype "passive"))
      (node (ref "R394") (pin "1") (pinfunction "1_1") (pintype "passive"))
    )
    (net (code "460") (name "Net-(IC41B-OUT)") (class "Default")
      (node (ref "IC41") (pin "7") (pinfunction "OUT_7") (pintype "output"))
      (node (ref "R391") (pin "1") (pinfunction "1_1") (pintype "passive"))
    )
    (net (code "461") (name "Net-(IC42A-+IN)") (class "Default")
      (node (ref "IC42") (pin "3") (pinfunction "+IN_3") (pintype "input"))
      (node (ref "R398") (pin "2") (pinfunction "2_2") (pintype "passive"))
      (node (ref "R399") (pin "1") (pinfunction "1_1") (pintype "passive"))
    )
    (net (code "462") (name "Net-(IC42A-OUT)") (class "Default")
      (node (ref "IC42") (pin "1") (pinfunction "OUT_1") (pintype "output"))
      (node (ref "R396") (pin "1") (pinfunction "1_1") (pintype "passive"))
    )
    (net (code "463") (name "Net-(IC42B-+IN)") (class "Default")
      (node (ref "IC42") (pin "5") (pinfunction "+IN_5") (pintype "input"))
      (node (ref "R403") (pin "2") (pinfunction "2_2") (pintype "passive"))
      (node (ref "R404") (pin "1") (pinfunction "1_1") (pintype "passive"))
    )
    (net (code "464") (name "Net-(IC42B-OUT)") (class "Default")
      (node (ref "IC42") (pin "7") (pinfunction "OUT_7") (pintype "output"))
      (node (ref "R401") (pin "1") (pinfunction "1_1") (pintype "passive"))
    )
    (net (code "465") (name "Net-(IC43A-+IN)") (class "Default")
      (node (ref "IC43") (pin "3") (pinfunction "+IN_3") (pintype "input"))
      (node (ref "R408") (pin "2") (pinfunction "2_2") (pintype "passive"))
      (node (ref "R409") (pin "1") (pinfunction "1_1") (pintype "passive"))
    )
    (net (code "466") (name "Net-(IC43A-OUT)") (class "Default")
      (node (ref "IC43") (pin "1") (pinfunction "OUT_1") (pintype "output"))
      (node (ref "R406") (pin "1") (pinfunction "1_1") (pintype "passive"))
    )
    (net (code "467") (name "Net-(IC43B--IN)") (class "Default")
      (node (ref "IC43") (pin "6") (pinfunction "-IN_6") (pintype "input"))
      (node (ref "IC43") (pin "7") (pinfunction "OUT_7") (pintype "output"))
    )
    (net (code "468") (name "Net-(IC44A-+IN)") (class "Default")
      (node (ref "IC44") (pin "3") (pinfunction "+IN_3") (pintype "input"))
      (node (ref "R84") (pin "2") (pinfunction "2_2") (pintype "passive"))
      (node (ref "R85") (pin "2") (pinfunction "2_2") (pintype "passive"))
    )
    (net (code "469") (name "Net-(IC44A--IN)") (class "Default")
      (node (ref "IC44") (pin "1") (pinfunction "OUT_1") (pintype "output"))
      (node (ref "IC44") (pin "2") (pinfunction "-IN_2") (pintype "input"))
      (node (ref "R428") (pin "1") (pinfunction "1_1") (pintype "passive"))
    )
    (net (code "470") (name "Net-(IC44B-+IN)") (class "Default")
      (node (ref "IC44") (pin "5") (pinfunction "+IN_5") (pintype "input"))
      (node (ref "R430") (pin "2") (pinfunction "2_2") (pintype "passive"))
      (node (ref "R431") (pin "2") (pinfunction "2_2") (pintype "passive"))
      (node (ref "R514") (pin "2") (pinfunction "2_2") (pintype "passive"))
    )
    (net (code "471") (name "Net-(IC44B--IN)") (class "Default")
      (node (ref "IC44") (pin "6") (pinfunction "-IN_6") (pintype "input"))
      (node (ref "IC44") (pin "7") (pinfunction "OUT_7") (pintype "output"))
      (node (ref "R429") (pin "1") (pinfunction "1_1") (pintype "passive"))
    )
    (net (code "472") (name "Net-(IC44C-VCC)") (class "Default")
      (node (ref "C88") (pin "1") (pinfunction "1_1") (pintype "passive"))
      (node (ref "IC44") (pin "8") (pinfunction "VCC_8") (pintype "input"))
      (node (ref "R427") (pin "1") (pinfunction "1_1") (pintype "passive"))
    )
    (net (code "473") (name "Net-(IC45-BST)") (class "Default")
      (node (ref "C55") (pin "2") (pinfunction "2_2") (pintype "passive"))
      (node (ref "IC45") (pin "6") (pinfunction "BST_6") (pintype "input"))
    )
    (net (code "474") (name "Net-(IC45-FB)") (class "Default")
      (node (ref "C237") (pin "2") (pinfunction "2_2") (pintype "passive"))
      (node (ref "IC45") (pin "8") (pinfunction "FB_8") (pintype "input"))
      (node (ref "R283") (pin "1") (pinfunction "1_1") (pintype "passive"))
      (node (ref "R318") (pin "1") (pinfunction "1_1") (pintype "passive"))
      (node (ref "R325") (pin "2") (pinfunction "2_2") (pintype "passive"))
    )
    (net (code "475") (name "Net-(IC45-RT)") (class "Default")
      (node (ref "IC45") (pin "1") (pinfunction "RT_1") (pintype "input"))
      (node (ref "R257") (pin "2") (pinfunction "2_2") (pintype "passive"))
    )
    (net (code "476") (name "Net-(IC45-SS)") (class "Default")
      (node (ref "C233") (pin "1") (pinfunction "1_1") (pintype "passive"))
      (node (ref "IC45") (pin "7") (pinfunction "SS_7") (pintype "input"))
    )
    (net (code "477") (name "Net-(IC45-SW)") (class "Default")
      (node (ref "IC45") (pin "5") (pinfunction "SW_5") (pintype "bidirectional"))
      (node (ref "L21") (pin "DOT") (pinfunction "DOT_DOT") (pintype "passive"))
      (node (ref "R131") (pin "2") (pinfunction "2_2") (pintype "passive"))
    )
    (net (code "478") (name "Net-(IC45-VIN)") (class "Default")
      (node (ref "C116") (pin "1") (pinfunction "1_1") (pintype "passive"))
      (node (ref "IC45") (pin "3") (pinfunction "VIN_3") (pintype "input"))
      (node (ref "L22") (pin "1") (pinfunction "1_1") (pintype "passive"))
    )
    (net (code "479") (name "Net-(IC46-HB)") (class "Default")
      (node (ref "C207") (pin "1") (pinfunction "1_1") (pintype "passive"))
      (node (ref "IC46") (pin "3") (pinfunction "HB_3") (pintype "input"))
    )
    (net (code "480") (name "Net-(IC46-HO)") (class "Default")
      (node (ref "IC46") (pin "4") (pinfunction "HO_4") (pintype "output"))
      (node (ref "R453") (pin "1") (pinfunction "1_1") (pintype "passive"))
    )
    (net (code "481") (name "Net-(IC46-HS)") (class "Default")
      (node (ref "C207") (pin "2") (pinfunction "2_2") (pintype "passive"))
      (node (ref "IC46") (pin "5") (pinfunction "HS_5") (pintype "input"))
      (node (ref "L24") (pin "DOT") (pinfunction "DOT_DOT") (pintype "passive"))
      (node (ref "T51") (pin "3") (pinfunction "D_3") (pintype "passive"))
      (node (ref "T52") (pin "2") (pinfunction "S_2") (pintype "passive"))
    )
    (net (code "482") (name "Net-(IC46-LO)") (class "Default")
      (node (ref "IC46") (pin "10") (pinfunction "LO_10") (pintype "output"))
      (node (ref "R454") (pin "1") (pinfunction "1_1") (pintype "passive"))
    )
    (net (code "483") (name "Net-(IC46-VDD)") (class "Default")
      (node (ref "C208") (pin "1") (pinfunction "1_1") (pintype "passive"))
      (node (ref "IC46") (pin "1") (pinfunction "VDD_1") (pintype "input"))
      (node (ref "R455") (pin "1") (pinfunction "1_1") (pintype "passive"))
    )
    (net (code "484") (name "Net-(IC47-IN+)") (class "Default")
      (node (ref "C212") (pin "2") (pinfunction "2_2") (pintype "passive"))
      (node (ref "IC47") (pin "2") (pinfunction "IN+_2") (pintype "input"))
      (node (ref "R457") (pin "1") (pinfunction "1_1") (pintype "passive"))
    )
    (net (code "485") (name "Net-(IC47-IN-)") (class "Default")
      (node (ref "C212") (pin "1") (pinfunction "1_1") (pintype "passive"))
      (node (ref "IC47") (pin "3") (pinfunction "IN-_3") (pintype "input"))
      (node (ref "R458") (pin "1") (pinfunction "1_1") (pintype "passive"))
    )
    (net (code "486") (name "Net-(IC47-OUT)") (class "Default")
      (node (ref "IC47") (pin "8") (pinfunction "OUT_8") (pintype "output"))
      (node (ref "R461") (pin "1") (pinfunction "1_1") (pintype "passive"))
    )
    (net (code "487") (name "Net-(IC47-REF1)") (class "Default")
      (node (ref "C215") (pin "1") (pinfunction "1_1") (pintype "passive"))
      (node (ref "IC47") (pin "6") (pinfunction "REF2_6") (pintype "input"))
      (node (ref "IC47") (pin "7") (pinfunction "REF1_7") (pintype "input"))
      (node (ref "IC48") (pin "5") (pinfunction "OUT_5") (pintype "passive"))
      (node (ref "R464") (pin "1") (pinfunction "1_1") (pintype "passive"))
    )
    (net (code "488") (name "Net-(IC47-VS)") (class "Default")
      (node (ref "C213") (pin "1") (pinfunction "1_1") (pintype "passive"))
      (node (ref "IC47") (pin "5") (pinfunction "VS_5") (pintype "input"))
      (node (ref "R459") (pin "2") (pinfunction "2_2") (pintype "passive"))
    )
    (net (code "489") (name "Net-(IC48-EN)") (class "Default")
      (node (ref "C214") (pin "1") (pinfunction "1_1") (pintype "passive"))
      (node (ref "IC48") (pin "1") (pinfunction "IN_1") (pintype "input"))
      (node (ref "IC48") (pin "3") (pinfunction "EN_3") (pintype "input"))
      (node (ref "R460") (pin "2") (pinfunction "2_2") (pintype "passive"))
    )
    (net (code "490") (name "Net-(IC49A-+IN)") (class "Default")
      (node (ref "IC49") (pin "3") (pinfunction "+IN_3") (pintype "input"))
      (node (ref "R461") (pin "2") (pinfunction "2_2") (pintype "passive"))
    )
    (net (code "491") (name "Net-(IC49A--IN)") (class "Default")
      (node (ref "IC49") (pin "1") (pinfunction "OUT_1") (pintype "output"))
      (node (ref "IC49") (pin "2") (pinfunction "-IN_2") (pintype "input"))
      (node (ref "R462") (pin "1") (pinfunction "1_1") (pintype "passive"))
    )
    (net (code "492") (name "Net-(IC49B--IN)") (class "Default")
      (node (ref "IC49") (pin "6") (pinfunction "-IN_6") (pintype "input"))
      (node (ref "IC49") (pin "7") (pinfunction "OUT_7") (pintype "output"))
    )
    (net (code "493") (name "Net-(IC49C-VCC)") (class "Default")
      (node (ref "C216") (pin "1") (pinfunction "1_1") (pintype "passive"))
      (node (ref "IC49") (pin "8") (pinfunction "VCC_8") (pintype "input"))
      (node (ref "R463") (pin "2") (pinfunction "2_2") (pintype "passive"))
    )
    (net (code "494") (name "Net-(IC52-I{slash}O1)") (class "Default")
      (node (ref "IC52") (pin "1") (pinfunction "I/O1_1") (pintype "passive"))
      (node (ref "R303") (pin "1") (pinfunction "1_1") (pintype "passive"))
      (node (ref "X16") (pin "1") (pinfunction "1_1") (pintype "passive"))
    )
    (net (code "495") (name "Net-(IC53A-+IN)") (class "Default")
      (node (ref "IC53") (pin "3") (pinfunction "+IN_3") (pintype "input"))
      (node (ref "R470") (pin "2") (pinfunction "2_2") (pintype "passive"))
    )
    (net (code "496") (name "Net-(IC53A--IN)") (class "Default")
      (node (ref "IC53") (pin "1") (pinfunction "OUT_1") (pintype "output"))
      (node (ref "IC53") (pin "2") (pinfunction "-IN_2") (pintype "input"))
      (node (ref "R469") (pin "1") (pinfunction "1_1") (pintype "passive"))
    )
    (net (code "497") (name "Net-(IC53B--IN)") (class "Default")
      (node (ref "IC53") (pin "6") (pinfunction "-IN_6") (pintype "input"))
      (node (ref "IC53") (pin "7") (pinfunction "OUT_7") (pintype "output"))
    )
    (net (code "498") (name "Net-(IC53C-VCC)") (class "Default")
      (node (ref "C227") (pin "1") (pinfunction "1_1") (pintype "passive"))
      (node (ref "IC53") (pin "8") (pinfunction "VCC_8") (pintype "input"))
      (node (ref "R468") (pin "1") (pinfunction "1_1") (pintype "passive"))
    )
    (net (code "499") (name "Net-(IC54-A1)") (class "Default")
      (node (ref "IC54") (pin "14") (pinfunction "A1_14") (pintype "input"))
      (node (ref "R11") (pin "2") (pinfunction "2_2") (pintype "passive"))
    )
    (net (code "500") (name "Net-(IC54-EN)") (class "Default")
      (node (ref "IC54") (pin "16") (pinfunction "EN_16") (pintype "input"))
      (node (ref "R489") (pin "2") (pinfunction "2_2") (pintype "passive"))
    )
    (net (code "501") (name "Net-(IC54-VDD)") (class "Default")
      (node (ref "C246") (pin "1") (pinfunction "1_1") (pintype "passive"))
      (node (ref "IC54") (pin "12") (pinfunction "VDD_12") (pintype "input"))
      (node (ref "R486") (pin "1") (pinfunction "1_1") (pintype "passive"))
    )
    (net (code "502") (name "Net-(IC55-A1)") (class "Default")
      (node (ref "IC55") (pin "14") (pinfunction "A1_14") (pintype "input"))
      (node (ref "R491") (pin "2") (pinfunction "2_2") (pintype "passive"))
    )
    (net (code "503") (name "Net-(IC55-EN)") (class "Default")
      (node (ref "IC55") (pin "16") (pinfunction "EN_16") (pintype "input"))
      (node (ref "R490") (pin "2") (pinfunction "2_2") (pintype "passive"))
    )
    (net (code "504") (name "Net-(IC55-VDD)") (class "Default")
      (node (ref "C4") (pin "1") (pinfunction "1_1") (pintype "passive"))
      (node (ref "IC55") (pin "12") (pinfunction "VDD_12") (pintype "input"))
      (node (ref "R487") (pin "1") (pinfunction "1_1") (pintype "passive"))
    )
    (net (code "505") (name "Net-(IC74-BST)") (class "Default")
      (node (ref "C271") (pin "2") (pinfunction "2_2") (pintype "passive"))
      (node (ref "IC74") (pin "6") (pinfunction "BST_6") (pintype "input"))
    )
    (net (code "506") (name "Net-(IC74-FB)") (class "Default")
      (node (ref "C274") (pin "2") (pinfunction "2_2") (pintype "passive"))
      (node (ref "IC74") (pin "8") (pinfunction "FB_8") (pintype "input"))
      (node (ref "R253") (pin "1") (pinfunction "1_1") (pintype "passive"))
      (node (ref "R254") (pin "2") (pinfunction "2_2") (pintype "passive"))
      (node (ref "R447") (pin "1") (pinfunction "1_1") (pintype "passive"))
    )
    (net (code "507") (name "Net-(IC74-RT)") (class "Default")
      (node (ref "IC74") (pin "1") (pinfunction "RT_1") (pintype "input"))
      (node (ref "R328") (pin "2") (pinfunction "2_2") (pintype "passive"))
    )
    (net (code "508") (name "Net-(IC74-SS)") (class "Default")
      (node (ref "C273") (pin "1") (pinfunction "1_1") (pintype "passive"))
      (node (ref "IC74") (pin "7") (pinfunction "SS_7") (pintype "input"))
    )
    (net (code "509") (name "Net-(IC74-SW)") (class "Default")
      (node (ref "IC74") (pin "5") (pinfunction "SW_5") (pintype "bidirectional"))
      (node (ref "L35") (pin "DOT") (pinfunction "DOT_DOT") (pintype "passive"))
      (node (ref "R327") (pin "2") (pinfunction "2_2") (pintype "passive"))
    )
    (net (code "510") (name "Net-(IC74-VIN)") (class "Default")
      (node (ref "C222") (pin "1") (pinfunction "1_1") (pintype "passive"))
      (node (ref "IC74") (pin "3") (pinfunction "VIN_3") (pintype "input"))
      (node (ref "L38") (pin "1") (pinfunction "1_1") (pintype "passive"))
    )
    (net (code "511") (name "Net-(IC75-NC)") (class "Default")
      (node (ref "IC75") (pin "1") (pinfunction "NC_1") (pintype "passive"))
      (node (ref "R546") (pin "2") (pinfunction "2_2") (pintype "passive"))
      (node (ref "R547") (pin "1") (pinfunction "1_1") (pintype "passive"))
    )
    (net (code "512") (name "Net-(IC75-VCC)") (class "Default")
      (node (ref "C292") (pin "1") (pinfunction "1_1") (pintype "passive"))
      (node (ref "IC75") (pin "5") (pinfunction "VCC_5") (pintype "input"))
      (node (ref "R544") (pin "2") (pinfunction "2_2") (pintype "passive"))
    )
    (net (code "513") (name "Net-(IC76-AC0)") (class "Default")
      (node (ref "C293") (pin "1") (pinfunction "1_1") (pintype "passive"))
      (node (ref "IC76") (pin "2") (pinfunction "AC0_2") (pintype "bidirectional"))
      (node (ref "TP69") (pin "P$1") (pinfunction "TP_P$1") (pintype "input"))
      (node (ref "X17") (pin "1") (pinfunction "1_1") (pintype "passive"))
    )
    (net (code "514") (name "Net-(IC76-AC1)") (class "Default")
      (node (ref "C293") (pin "2") (pinfunction "2_2") (pintype "passive"))
      (node (ref "IC76") (pin "3") (pinfunction "AC1_3") (pintype "bidirectional"))
      (node (ref "TP70") (pin "P$1") (pinfunction "TP_P$1") (pintype "input"))
      (node (ref "X17") (pin "2") (pinfunction "2_2") (pintype "passive"))
    )
    (net (code "515") (name "Net-(IC76-GPO)") (class "Default")
      (node (ref "IC76") (pin "7") (pinfunction "GPO_7") (pintype "open_collector"))
      (node (ref "R532") (pin "2") (pinfunction "2_2") (pintype "passive"))
      (node (ref "R549") (pin "1") (pinfunction "1_1") (pintype "passive"))
    )
    (net (code "516") (name "Net-(IC76-SCL)") (class "Default")
      (node (ref "IC76") (pin "6") (pinfunction "SCL_6") (pintype "input"))
      (node (ref "R548") (pin "1") (pinfunction "1_1") (pintype "passive"))
    )
    (net (code "517") (name "Net-(IC76-SDA)") (class "Default")
      (node (ref "IC76") (pin "5") (pinfunction "SDA_5") (pintype "bidirectional"))
      (node (ref "R545") (pin "1") (pinfunction "1_1") (pintype "passive"))
    )
    (net (code "518") (name "Net-(IC76-VCC)") (class "Default")
      (node (ref "C294") (pin "1") (pinfunction "1_1") (pintype "passive"))
      (node (ref "IC76") (pin "8") (pinfunction "VCC_8") (pintype "input"))
      (node (ref "R551") (pin "1") (pinfunction "1_1") (pintype "passive"))
    )
    (net (code "519") (name "Net-(IC77-ADD0)") (class "Default")
      (node (ref "IC77") (pin "4") (pinfunction "ADD0_4") (pintype "input"))
      (node (ref "R560") (pin "2") (pinfunction "2_2") (pintype "passive"))
      (node (ref "R561") (pin "1") (pinfunction "1_1") (pintype "passive"))
      (node (ref "R562") (pin "1") (pinfunction "1_1") (pintype "passive"))
      (node (ref "R563") (pin "2") (pinfunction "2_2") (pintype "passive"))
    )
    (net (code "520") (name "Net-(IC77-SCL)") (class "Default")
      (node (ref "IC77") (pin "1") (pinfunction "SCL_1") (pintype "input"))
      (node (ref "R558") (pin "1") (pinfunction "1_1") (pintype "passive"))
      (node (ref "R562") (pin "2") (pinfunction "2_2") (pintype "passive"))
    )
    (net (code "521") (name "Net-(IC77-SDA)") (class "Default")
      (node (ref "IC77") (pin "6") (pinfunction "SDA_6") (pintype "open_collector"))
      (node (ref "R557") (pin "1") (pinfunction "1_1") (pintype "passive"))
      (node (ref "R561") (pin "2") (pinfunction "2_2") (pintype "passive"))
    )
    (net (code "522") (name "Net-(IC77-V+)") (class "Default")
      (node (ref "C297") (pin "1") (pinfunction "1_1") (pintype "passive"))
      (node (ref "IC77") (pin "5") (pinfunction "V+_5") (pintype "input"))
      (node (ref "R559") (pin "2") (pinfunction "2_2") (pintype "passive"))
      (node (ref "R563") (pin "1") (pinfunction "1_1") (pintype "passive"))
    )
    (net (code "523") (name "Net-(L6-NODOT)") (class "Default")
      (node (ref "C100") (pin "1") (pinfunction "1_1") (pintype "passive"))
      (node (ref "L6") (pin "NO_DOT") (pinfunction "NODOT_NO_DOT") (pintype "passive"))
      (node (ref "TP81") (pin "P$1") (pinfunction "TP_P$1") (pintype "input"))
      (node (ref "X23") (pin "1") (pinfunction "1_1") (pintype "passive"))
    )
    (net (code "524") (name "Net-(L8-NODOT)") (class "Default")
      (node (ref "C72") (pin "1") (pinfunction "1_1") (pintype "passive"))
      (node (ref "L8") (pin "NO_DOT") (pinfunction "NODOT_NO_DOT") (pintype "passive"))
      (node (ref "TP80") (pin "P$1") (pinfunction "TP_P$1") (pintype "input"))
      (node (ref "X23") (pin "2") (pinfunction "2_2") (pintype "passive"))
    )
    (net (code "525") (name "Net-(L12-NODOT)") (class "Default")
      (node (ref "C125") (pin "1") (pinfunction "1_1") (pintype "passive"))
      (node (ref "L12") (pin "NO_DOT") (pinfunction "NODOT_NO_DOT") (pintype "passive"))
      (node (ref "TP82") (pin "P$1") (pinfunction "TP_P$1") (pintype "input"))
      (node (ref "X24") (pin "1") (pinfunction "1_1") (pintype "passive"))
    )
    (net (code "526") (name "Net-(L13-NODOT)") (class "Default")
      (node (ref "C126") (pin "1") (pinfunction "1_1") (pintype "passive"))
      (node (ref "L13") (pin "NO_DOT") (pinfunction "NODOT_NO_DOT") (pintype "passive"))
      (node (ref "TP83") (pin "P$1") (pinfunction "TP_P$1") (pintype "input"))
      (node (ref "X24") (pin "2") (pinfunction "2_2") (pintype "passive"))
    )
    (net (code "527") (name "Net-(L15A-NODOT)") (class "Default")
      (node (ref "C234") (pin "1") (pinfunction "1_1") (pintype "passive"))
      (node (ref "C275") (pin "1") (pinfunction "1_1") (pintype "passive"))
      (node (ref "C38") (pin "1") (pinfunction "1_1") (pintype "passive"))
      (node (ref "L15") (pin "3") (pinfunction "NODOT_3") (pintype "passive"))
      (node (ref "R32") (pin "2") (pinfunction "2_2") (pintype "passive"))
      (node (ref "R34") (pin "1") (pinfunction "1_1") (pintype "passive"))
    )
    (net (code "528") (name "Net-(L17-NODOT)") (class "Default")
      (node (ref "L17") (pin "NO_DOT") (pinfunction "NODOT_NO_DOT") (pintype "passive"))
      (node (ref "R343") (pin "2") (pinfunction "2_2") (pintype "passive"))
      (node (ref "R345") (pin "2") (pinfunction "2_2") (pintype "passive"))
    )
    (net (code "529") (name "Net-(L23-NODOT)") (class "Default")
      (node (ref "C211") (pin "1") (pinfunction "1_1") (pintype "passive"))
      (node (ref "L23") (pin "NO_DOT") (pinfunction "NODOT_NO_DOT") (pintype "passive"))
      (node (ref "L25") (pin "1") (pinfunction "1_1") (pintype "passive"))
    )
    (net (code "530") (name "Net-(L24-NODOT)") (class "Default")
      (node (ref "C210") (pin "1") (pinfunction "1_1") (pintype "passive"))
      (node (ref "L24") (pin "NO_DOT") (pinfunction "NODOT_NO_DOT") (pintype "passive"))
      (node (ref "L26") (pin "2") (pinfunction "2_2") (pintype "passive"))
    )
    (net (code "531") (name "Net-(L26-Pad1)") (class "Default")
      (node (ref "L26") (pin "1") (pinfunction "1_1") (pintype "passive"))
      (node (ref "R456") (pin "1") (pinfunction "1_1") (pintype "passive"))
      (node (ref "R457") (pin "2") (pinfunction "2_2") (pintype "passive"))
    )
    (net (code "532") (name "Net-(MOD1A-CAM0_MCLK)") (class "Default")
      (node (ref "MOD1") (pin "116") (pinfunction "CAM0_MCLK_116") (pintype "output"))
      (node (ref "R443") (pin "1") (pinfunction "1_1") (pintype "passive"))
    )
    (net (code "533") (name "Net-(MOD1A-CAM0_PWDN)") (class "Default")
      (node (ref "MOD1") (pin "114") (pinfunction "CAM0_PWDN_114") (pintype "output"))
      (node (ref "R442") (pin "1") (pinfunction "1_1") (pintype "passive"))
    )
    (net (code "534") (name "Net-(MOD1A-CAM1_MCLK)") (class "Default")
      (node (ref "MOD1") (pin "122") (pinfunction "CAM1_MCLK_122") (pintype "output"))
      (node (ref "R114") (pin "1") (pinfunction "1_1") (pintype "passive"))
    )
    (net (code "535") (name "Net-(MOD1A-CAM1_PWDN)") (class "Default")
      (node (ref "MOD1") (pin "120") (pinfunction "CAM1_PWDN_120") (pintype "output"))
      (node (ref "R115") (pin "1") (pinfunction "1_1") (pintype "passive"))
    )
    (net (code "536") (name "Net-(MOD1A-CAM_I2C_SCL)") (class "Default")
      (node (ref "MOD1") (pin "213") (pinfunction "CAM_I2C_SCL_213") (pintype "bidirectional"))
      (node (ref "R280") (pin "1") (pinfunction "1_1") (pintype "passive"))
    )
    (net (code "537") (name "Net-(MOD1A-CAM_I2C_SDA)") (class "Default")
      (node (ref "MOD1") (pin "215") (pinfunction "CAM_I2C_SDA_215") (pintype "bidirectional"))
      (node (ref "R281") (pin "1") (pinfunction "1_1") (pintype "passive"))
    )
    (net (code "538") (name "Net-(MOD1B-DP1_AUX_N)") (class "Default")
      (node (ref "MOD1") (pin "98") (pinfunction "DP1_AUX_N_98") (pintype "bidirectional"))
      (node (ref "R329") (pin "1") (pinfunction "1_1") (pintype "passive"))
    )
    (net (code "539") (name "Net-(MOD1B-DP1_AUX_P)") (class "Default")
      (node (ref "MOD1") (pin "100") (pinfunction "DP1_AUX_P_100") (pintype "bidirectional"))
      (node (ref "R330") (pin "1") (pinfunction "1_1") (pintype "passive"))
    )
    (net (code "540") (name "Net-(MOD1D-CAN_RX{slash}RSVD)") (class "Default")
      (node (ref "MOD1") (pin "143") (pinfunction "CAN_RX/RSVD_143") (pintype "input"))
      (node (ref "R471") (pin "2") (pinfunction "2_2") (pintype "passive"))
    )
    (net (code "541") (name "Net-(MOD1D-CAN_TX{slash}RSVD)") (class "Default")
      (node (ref "MOD1") (pin "145") (pinfunction "CAN_TX/RSVD_145") (pintype "output"))
      (node (ref "R31") (pin "2") (pinfunction "2_2") (pintype "passive"))
    )
    (net (code "542") (name "Net-(MOD1D-I2C0_SCL)") (class "Default")
      (node (ref "MOD1") (pin "185") (pinfunction "I2C0_SCL_185") (pintype "bidirectional"))
      (node (ref "R270") (pin "1") (pinfunction "1_1") (pintype "passive"))
    )
    (net (code "543") (name "Net-(MOD1D-I2C0_SDA)") (class "Default")
      (node (ref "MOD1") (pin "187") (pinfunction "I2C0_SDA_187") (pintype "bidirectional"))
      (node (ref "R269") (pin "1") (pinfunction "1_1") (pintype "passive"))
    )
    (net (code "544") (name "Net-(MOD1D-I2C1_SCL)") (class "Default")
      (node (ref "MOD1") (pin "189") (pinfunction "I2C1_SCL_189") (pintype "bidirectional"))
      (node (ref "R268") (pin "1") (pinfunction "1_1") (pintype "passive"))
    )
    (net (code "545") (name "Net-(MOD1D-I2C1_SDA)") (class "Default")
      (node (ref "MOD1") (pin "191") (pinfunction "I2C1_SDA_191") (pintype "bidirectional"))
      (node (ref "R267") (pin "1") (pinfunction "1_1") (pintype "passive"))
    )
    (net (code "546") (name "Net-(MOD1D-I2S0_DOUT)") (class "Default")
      (node (ref "MOD1") (pin "193") (pinfunction "I2S0_DOUT_193") (pintype "output"))
      (node (ref "R94") (pin "1") (pinfunction "1_1") (pintype "passive"))
    )
    (net (code "547") (name "Net-(MOD1D-I2S0_FS)") (class "Default")
      (node (ref "MOD1") (pin "197") (pinfunction "I2S0_FS_197") (pintype "bidirectional"))
      (node (ref "R141") (pin "1") (pinfunction "1_1") (pintype "passive"))
    )
    (net (code "548") (name "Net-(MOD1D-I2S0_SCLK)") (class "Default")
      (node (ref "MOD1") (pin "199") (pinfunction "I2S0_SCLK_199") (pintype "bidirectional"))
      (node (ref "R142") (pin "1") (pinfunction "1_1") (pintype "passive"))
    )
    (net (code "549") (name "Net-(MOD1D-UART0_TXD)") (class "Default")
      (node (ref "MOD1") (pin "99") (pinfunction "UART0_TXD_99") (pintype "output"))
      (node (ref "R516") (pin "2") (pinfunction "2_2") (pintype "passive"))
    )
    (net (code "550") (name "Net-(MOD1D-UART1_TXD)") (class "Default")
      (node (ref "MOD1") (pin "203") (pinfunction "UART1_TXD_203") (pintype "output"))
      (node (ref "R244") (pin "2") (pinfunction "2_2") (pintype "passive"))
    )
    (net (code "551") (name "Net-(MOD1D-UART2_TXD)") (class "Default")
      (node (ref "MOD1") (pin "236") (pinfunction "UART2_TXD_236") (pintype "output"))
      (node (ref "R235") (pin "2") (pinfunction "2_2") (pintype "passive"))
    )
    (net (code "552") (name "Net-(MOD1E-CLK_32K_OUT)") (class "Default")
      (node (ref "MOD1") (pin "210") (pinfunction "CLK_32K_OUT_210") (pintype "output"))
      (node (ref "R193") (pin "2") (pinfunction "2_2") (pintype "passive"))
    )
    (net (code "553") (name "Net-(MOD1E-~{SHUTDOWN_REQ})") (class "Default")
      (node (ref "MOD1") (pin "233") (pinfunction "~{SHUTDOWN_REQ}_233") (pintype "output"))
      (node (ref "R107") (pin "2") (pinfunction "2_2") (pintype "passive"))
    )
    (net (code "554") (name "Net-(Q1-C2)") (class "Default")
      (node (ref "C103") (pin "1") (pinfunction "1_1") (pintype "passive"))
      (node (ref "Q1") (pin "3") (pinfunction "C2_3") (pintype "bidirectional"))
      (node (ref "R296") (pin "1") (pinfunction "1_1") (pintype "passive"))
    )
    (net (code "555") (name "Net-(R26-Pad2)") (class "Default")
      (node (ref "R26") (pin "2") (pinfunction "2_2") (pintype "passive"))
      (node (ref "R299") (pin "1") (pinfunction "1_1") (pintype "passive"))
    )
    (net (code "556") (name "Net-(R33-Pad1)") (class "Default")
      (node (ref "R33") (pin "1") (pinfunction "1_1") (pintype "passive"))
      (node (ref "R480") (pin "2") (pinfunction "2_2") (pintype "passive"))
    )
    (net (code "557") (name "Net-(R38-Pad1)") (class "Default")
      (node (ref "R38") (pin "1") (pinfunction "1_1") (pintype "passive"))
      (node (ref "R56") (pin "2") (pinfunction "2_2") (pintype "passive"))
    )
    (net (code "558") (name "Net-(R38-Pad2)") (class "Default")
      (node (ref "R38") (pin "2") (pinfunction "2_2") (pintype "passive"))
      (node (ref "R413") (pin "1") (pinfunction "1_1") (pintype "passive"))
    )
    (net (code "559") (name "Net-(R56-Pad1)") (class "Default")
      (node (ref "R56") (pin "1") (pinfunction "1_1") (pintype "passive"))
      (node (ref "R78") (pin "2") (pinfunction "2_2") (pintype "passive"))
    )
    (net (code "560") (name "Net-(R73-Pad2)") (class "Default")
      (node (ref "R73") (pin "2") (pinfunction "2_2") (pintype "passive"))
      (node (ref "X8") (pin "6") (pinfunction "D-_6") (pintype "bidirectional"))
    )
    (net (code "561") (name "Net-(R74-Pad2)") (class "Default")
      (node (ref "R74") (pin "2") (pinfunction "2_2") (pintype "passive"))
      (node (ref "X8") (pin "7") (pinfunction "D+_7") (pintype "bidirectional"))
    )
    (net (code "562") (name "Net-(R76-Pad1)") (class "Default")
      (node (ref "R76") (pin "1") (pinfunction "1_1") (pintype "passive"))
      (node (ref "X2") (pin "4") (pinfunction "4_4") (pintype "passive"))
    )
    (net (code "563") (name "Net-(R78-Pad1)") (class "Default")
      (node (ref "R78") (pin "1") (pinfunction "1_1") (pintype "passive"))
      (node (ref "R80") (pin "2") (pinfunction "2_2") (pintype "passive"))
    )
    (net (code "564") (name "Net-(R81-Pad1)") (class "Default")
      (node (ref "R81") (pin "1") (pinfunction "1_1") (pintype "passive"))
      (node (ref "X2") (pin "1") (pinfunction "1_1") (pintype "passive"))
    )
    (net (code "565") (name "Net-(R134-Pad2)") (class "Default")
      (node (ref "R134") (pin "2") (pinfunction "2_2") (pintype "passive"))
      (node (ref "X13") (pin "34") (pinfunction "34_34") (pintype "passive"))
    )
    (net (code "566") (name "Net-(R138-Pad2)") (class "Default")
      (node (ref "R138") (pin "2") (pinfunction "2_2") (pintype "passive"))
      (node (ref "X13") (pin "36") (pinfunction "36_36") (pintype "passive"))
    )
    (net (code "567") (name "Net-(R202-Pad2)") (class "Default")
      (node (ref "R202") (pin "2") (pinfunction "2_2") (pintype "passive"))
      (node (ref "R363") (pin "2") (pinfunction "2_2") (pintype "passive"))
      (node (ref "T62") (pin "1") (pinfunction "S_1") (pintype "passive"))
      (node (ref "T62") (pin "2") (pinfunction "S_2") (pintype "passive"))
      (node (ref "T62") (pin "3") (pinfunction "S_3") (pintype "passive"))
    )
    (net (code "568") (name "Net-(R209-Pad2)") (class "Default")
      (node (ref "R209") (pin "2") (pinfunction "2_2") (pintype "passive"))
      (node (ref "X13") (pin "38") (pinfunction "38_38") (pintype "passive"))
    )
    (net (code "569") (name "Net-(R210-Pad2)") (class "Default")
      (node (ref "R210") (pin "2") (pinfunction "2_2") (pintype "passive"))
      (node (ref "X13") (pin "40") (pinfunction "40_40") (pintype "passive"))
    )
    (net (code "570") (name "Net-(R232-Pad1)") (class "Default")
      (node (ref "R232") (pin "1") (pinfunction "1_1") (pintype "passive"))
      (node (ref "X4") (pin "8") (pinfunction "8_8") (pintype "passive"))
    )
    (net (code "571") (name "Net-(R245-Pad1)") (class "Default")
      (node (ref "R245") (pin "1") (pinfunction "1_1") (pintype "passive"))
      (node (ref "R530") (pin "2") (pinfunction "2_2") (pintype "passive"))
    )
    (net (code "572") (name "Net-(R289-Pad2)") (class "Default")
      (node (ref "R289") (pin "2") (pinfunction "2_2") (pintype "passive"))
      (node (ref "X8") (pin "2") (pinfunction "D-_2") (pintype "bidirectional"))
    )
    (net (code "573") (name "Net-(R290-Pad2)") (class "Default")
      (node (ref "R290") (pin "2") (pinfunction "2_2") (pintype "passive"))
      (node (ref "X8") (pin "3") (pinfunction "D+_3") (pintype "bidirectional"))
    )
    (net (code "574") (name "Net-(R320-Pad2)") (class "Default")
      (node (ref "R320") (pin "2") (pinfunction "2_2") (pintype "passive"))
      (node (ref "R444") (pin "1") (pinfunction "1_1") (pintype "passive"))
    )
    (net (code "575") (name "Net-(R349-Pad1)") (class "Default")
      (node (ref "R349") (pin "1") (pinfunction "1_1") (pintype "passive"))
      (node (ref "R350") (pin "2") (pinfunction "2_2") (pintype "passive"))
    )
    (net (code "576") (name "Net-(R355-Pad1)") (class "Default")
      (node (ref "R355") (pin "1") (pinfunction "1_1") (pintype "passive"))
      (node (ref "R513") (pin "2") (pinfunction "2_2") (pintype "passive"))
    )
    (net (code "577") (name "Net-(R364-Pad2)") (class "Default")
      (node (ref "R364") (pin "2") (pinfunction "2_2") (pintype "passive"))
      (node (ref "R366") (pin "1") (pinfunction "1_1") (pintype "passive"))
    )
    (net (code "578") (name "Net-(R368-Pad1)") (class "Default")
      (node (ref "R368") (pin "1") (pinfunction "1_1") (pintype "passive"))
      (node (ref "R508") (pin "2") (pinfunction "2_2") (pintype "passive"))
    )
    (net (code "579") (name "Net-(R379-Pad1)") (class "Default")
      (node (ref "R379") (pin "1") (pinfunction "1_1") (pintype "passive"))
      (node (ref "R390") (pin "1") (pinfunction "1_1") (pintype "passive"))
      (node (ref "R395") (pin "2") (pinfunction "2_2") (pintype "passive"))
      (node (ref "R400") (pin "2") (pinfunction "2_2") (pintype "passive"))
    )
    (net (code "580") (name "Net-(R382-Pad2)") (class "Default")
      (node (ref "R382") (pin "2") (pinfunction "2_2") (pintype "passive"))
      (node (ref "R80") (pin "1") (pinfunction "1_1") (pintype "passive"))
    )
    (net (code "581") (name "Net-(R384-Pad1)") (class "Default")
      (node (ref "R384") (pin "1") (pinfunction "1_1") (pintype "passive"))
      (node (ref "R410") (pin "2") (pinfunction "2_2") (pintype "passive"))
    )
    (net (code "582") (name "Net-(R405-Pad1)") (class "Default")
      (node (ref "R405") (pin "1") (pinfunction "1_1") (pintype "passive"))
      (node (ref "R493") (pin "1") (pinfunction "1_1") (pintype "passive"))
      (node (ref "R494") (pin "2") (pinfunction "2_2") (pintype "passive"))
      (node (ref "R495") (pin "2") (pinfunction "2_2") (pintype "passive"))
    )
    (net (code "583") (name "Net-(R410-Pad1)") (class "Default")
      (node (ref "R410") (pin "1") (pinfunction "1_1") (pintype "passive"))
      (node (ref "R411") (pin "2") (pinfunction "2_2") (pintype "passive"))
    )
    (net (code "584") (name "Net-(R411-Pad1)") (class "Default")
      (node (ref "R411") (pin "1") (pinfunction "1_1") (pintype "passive"))
      (node (ref "R412") (pin "2") (pinfunction "2_2") (pintype "passive"))
    )
    (net (code "585") (name "Net-(R412-Pad1)") (class "Default")
      (node (ref "R412") (pin "1") (pinfunction "1_1") (pintype "passive"))
      (node (ref "R413") (pin "2") (pinfunction "2_2") (pintype "passive"))
    )
    (net (code "586") (name "Net-(R466-Pad2)") (class "Default")
      (node (ref "R466") (pin "2") (pinfunction "2_2") (pintype "passive"))
      (node (ref "X3") (pin "2") (pinfunction "2_2") (pintype "passive"))
    )
    (net (code "587") (name "Net-(R467-Pad2)") (class "Default")
      (node (ref "R467") (pin "2") (pinfunction "2_2") (pintype "passive"))
      (node (ref "X3") (pin "3") (pinfunction "3_3") (pintype "passive"))
    )
    (net (code "588") (name "Net-(R474-Pad2)") (class "Default")
      (node (ref "R474") (pin "2") (pinfunction "2_2") (pintype "passive"))
      (node (ref "R93") (pin "2") (pinfunction "2_2") (pintype "passive"))
      (node (ref "X9") (pin "1") (pinfunction "1_1") (pintype "passive"))
    )
    (net (code "589") (name "Net-(R496-Pad1)") (class "Default")
      (node (ref "R496") (pin "1") (pinfunction "1_1") (pintype "passive"))
      (node (ref "R497") (pin "1") (pinfunction "1_1") (pintype "passive"))
      (node (ref "R498") (pin "2") (pinfunction "2_2") (pintype "passive"))
      (node (ref "R499") (pin "2") (pinfunction "2_2") (pintype "passive"))
    )
    (net (code "590") (name "Net-(R500-Pad1)") (class "Default")
      (node (ref "R500") (pin "1") (pinfunction "1_1") (pintype "passive"))
      (node (ref "R501") (pin "1") (pinfunction "1_1") (pintype "passive"))
      (node (ref "R502") (pin "2") (pinfunction "2_2") (pintype "passive"))
      (node (ref "R503") (pin "2") (pinfunction "2_2") (pintype "passive"))
    )
    (net (code "591") (name "Net-(R504-Pad1)") (class "Default")
      (node (ref "R504") (pin "1") (pinfunction "1_1") (pintype "passive"))
      (node (ref "R505") (pin "1") (pinfunction "1_1") (pintype "passive"))
      (node (ref "R506") (pin "2") (pinfunction "2_2") (pintype "passive"))
      (node (ref "R507") (pin "2") (pinfunction "2_2") (pintype "passive"))
    )
    (net (code "592") (name "Net-(R517-Pad1)") (class "Default")
      (node (ref "R517") (pin "1") (pinfunction "1_1") (pintype "passive"))
      (node (ref "X13") (pin "22") (pinfunction "22_22") (pintype "passive"))
    )
    (net (code "593") (name "Net-(R518-Pad1)") (class "Default")
      (node (ref "R518") (pin "1") (pinfunction "1_1") (pintype "passive"))
      (node (ref "X13") (pin "24") (pinfunction "24_24") (pintype "passive"))
    )
    (net (code "594") (name "Net-(R565-Pad2)") (class "Default")
      (node (ref "R565") (pin "2") (pinfunction "2_2") (pintype "passive"))
      (node (ref "X9") (pin "2") (pinfunction "2_2") (pintype "passive"))
    )
    (net (code "595") (name "Net-(T1-D)") (class "Default")
      (node (ref "R319") (pin "1") (pinfunction "1_1") (pintype "passive"))
      (node (ref "T1") (pin "3") (pinfunction "D_3") (pintype "passive"))
      (node (ref "T29") (pin "1") (pinfunction "G_1") (pintype "input"))
    )
    (net (code "596") (name "Net-(T1-G)") (class "Default")
      (node (ref "C231") (pin "1") (pinfunction "1_1") (pintype "passive"))
      (node (ref "R100") (pin "2") (pinfunction "2_2") (pintype "passive"))
      (node (ref "R99") (pin "2") (pinfunction "2_2") (pintype "passive"))
      (node (ref "T1") (pin "1") (pinfunction "G_1") (pintype "passive"))
    )
    (net (code "597") (name "Net-(T3-D)") (class "Default")
      (node (ref "F1") (pin "2") (pinfunction "2_2") (pintype "passive"))
      (node (ref "R214") (pin "2") (pinfunction "2_2") (pintype "passive"))
      (node (ref "T3") (pin "5") (pinfunction "D_5") (pintype "passive"))
      (node (ref "T9") (pin "4") (pinfunction "G_4") (pintype "passive"))
    )
    (net (code "598") (name "Net-(T3-G)") (class "Default")
      (node (ref "R213") (pin "2") (pinfunction "2_2") (pintype "passive"))
      (node (ref "R214") (pin "1") (pinfunction "1_1") (pintype "passive"))
      (node (ref "T3") (pin "4") (pinfunction "G_4") (pintype "input"))
    )
    (net (code "599") (name "Net-(T4-D)") (class "Default")
      (node (ref "R187") (pin "1") (pinfunction "1_1") (pintype "passive"))
      (node (ref "T4") (pin "3") (pinfunction "D_3") (pintype "passive"))
    )
    (net (code "600") (name "Net-(T5-G)") (class "Default")
      (node (ref "R172") (pin "2") (pinfunction "2_2") (pintype "passive"))
      (node (ref "R2") (pin "2") (pinfunction "2_2") (pintype "passive"))
      (node (ref "T5") (pin "1") (pinfunction "G_1") (pintype "passive"))
    )
    (net (code "601") (name "Net-(T6-G)") (class "Default")
      (node (ref "R169") (pin "2") (pinfunction "2_2") (pintype "passive"))
      (node (ref "R7") (pin "2") (pinfunction "2_2") (pintype "passive"))
      (node (ref "T6") (pin "1") (pinfunction "G_1") (pintype "passive"))
    )
    (net (code "602") (name "Net-(T8-D)") (class "Default")
      (node (ref "R111") (pin "1") (pinfunction "1_1") (pintype "passive"))
      (node (ref "R119") (pin "1") (pinfunction "1_1") (pintype "passive"))
      (node (ref "T8") (pin "3") (pinfunction "D_3") (pintype "passive"))
    )
    (net (code "603") (name "Net-(T10-D)") (class "Default")
      (node (ref "C95") (pin "1") (pinfunction "1_1") (pintype "passive"))
      (node (ref "T10") (pin "3") (pinfunction "D_3") (pintype "passive"))
      (node (ref "X32") (pin "67") (pinfunction "RESET#_67") (pintype "input"))
    )
    (net (code "604") (name "Net-(T10-G)") (class "Default")
      (node (ref "R129") (pin "1") (pinfunction "1_1") (pintype "passive"))
      (node (ref "R359") (pin "1") (pinfunction "1_1") (pintype "passive"))
      (node (ref "R485") (pin "2") (pinfunction "2_2") (pintype "passive"))
      (node (ref "T10") (pin "1") (pinfunction "G_1") (pintype "passive"))
      (node (ref "T58") (pin "3") (pinfunction "D_3") (pintype "passive"))
    )
    (net (code "605") (name "Net-(T11-D)") (class "Default")
      (node (ref "D10") (pin "C") (pinfunction "C_C") (pintype "passive"))
      (node (ref "T11") (pin "3") (pinfunction "D_3") (pintype "passive"))
    )
    (net (code "606") (name "Net-(T12-D)") (class "Default")
      (node (ref "R123") (pin "1") (pinfunction "1_1") (pintype "passive"))
      (node (ref "R124") (pin "1") (pinfunction "1_1") (pintype "passive"))
      (node (ref "T12") (pin "3") (pinfunction "D_3") (pintype "passive"))
    )
    (net (code "607") (name "Net-(T12-G)") (class "Default")
      (node (ref "R116") (pin "1") (pinfunction "1_1") (pintype "passive"))
      (node (ref "R117") (pin "2") (pinfunction "2_2") (pintype "passive"))
      (node (ref "R120") (pin "2") (pinfunction "2_2") (pintype "passive"))
      (node (ref "T12") (pin "1") (pinfunction "G_1") (pintype "passive"))
    )
    (net (code "608") (name "Net-(T15-G)") (class "Default")
      (node (ref "R341") (pin "2") (pinfunction "2_2") (pintype "passive"))
      (node (ref "T15") (pin "4") (pinfunction "G_4") (pintype "passive"))
    )
    (net (code "609") (name "Net-(T16-G)") (class "Default")
      (node (ref "R342") (pin "2") (pinfunction "2_2") (pintype "passive"))
      (node (ref "T16") (pin "4") (pinfunction "G_4") (pintype "passive"))
    )
    (net (code "610") (name "Net-(T17-D)") (class "Default")
      (node (ref "R361") (pin "2") (pinfunction "2_2") (pintype "passive"))
      (node (ref "R6") (pin "1") (pinfunction "1_1") (pintype "passive"))
      (node (ref "R60") (pin "1") (pinfunction "1_1") (pintype "passive"))
      (node (ref "T17") (pin "3") (pinfunction "D_3") (pintype "passive"))
    )
    (net (code "611") (name "Net-(T17-G)") (class "Default")
      (node (ref "C184") (pin "1") (pinfunction "1_1") (pintype "passive"))
      (node (ref "R212") (pin "2") (pinfunction "2_2") (pintype "passive"))
      (node (ref "R361") (pin "1") (pinfunction "1_1") (pintype "passive"))
      (node (ref "T17") (pin "1") (pinfunction "G_1") (pintype "passive"))
      (node (ref "T23") (pin "1") (pinfunction "G_1") (pintype "passive"))
    )
    (net (code "612") (name "Net-(T19-G)") (class "Default")
      (node (ref "R358") (pin "2") (pinfunction "2_2") (pintype "passive"))
      (node (ref "T19") (pin "3") (pinfunction "G_3") (pintype "passive"))
    )
    (net (code "613") (name "Net-(T20-G)") (class "Default")
      (node (ref "R360") (pin "2") (pinfunction "2_2") (pintype "passive"))
      (node (ref "T20") (pin "3") (pinfunction "G_3") (pintype "passive"))
    )
    (net (code "614") (name "Net-(T21-G)") (class "Default")
      (node (ref "C81") (pin "2") (pinfunction "2_2") (pintype "passive"))
      (node (ref "R217") (pin "1") (pinfunction "1_1") (pintype "passive"))
      (node (ref "R220") (pin "2") (pinfunction "2_2") (pintype "passive"))
      (node (ref "T21") (pin "4") (pinfunction "G_4") (pintype "input"))
    )
    (net (code "615") (name "Net-(T22-D)") (class "Default")
      (node (ref "R220") (pin "1") (pinfunction "1_1") (pintype "passive"))
      (node (ref "T22") (pin "3") (pinfunction "D_3") (pintype "passive"))
    )
    (net (code "616") (name "Net-(T23-D)") (class "Default")
      (node (ref "R211") (pin "1") (pinfunction "1_1") (pintype "passive"))
      (node (ref "R324") (pin "1") (pinfunction "1_1") (pintype "passive"))
      (node (ref "T23") (pin "3") (pinfunction "D_3") (pintype "passive"))
    )
    (net (code "617") (name "Net-(T25-S)") (class "Default")
      (node (ref "C289") (pin "2") (pinfunction "2_2") (pintype "passive"))
      (node (ref "R312") (pin "2") (pinfunction "2_2") (pintype "passive"))
      (node (ref "T25") (pin "2") (pinfunction "S_2") (pintype "passive"))
    )
    (net (code "618") (name "Net-(T26-D)") (class "Default")
      (node (ref "R302") (pin "1") (pinfunction "1_1") (pintype "passive"))
      (node (ref "T26") (pin "3") (pinfunction "D_3") (pintype "passive"))
    )
    (net (code "619") (name "Net-(T26-G)") (class "Default")
      (node (ref "R297") (pin "2") (pinfunction "2_2") (pintype "passive"))
      (node (ref "R298") (pin "1") (pinfunction "1_1") (pintype "passive"))
      (node (ref "T26") (pin "1") (pinfunction "G_1") (pintype "passive"))
      (node (ref "T27") (pin "1") (pinfunction "G_1") (pintype "passive"))
    )
    (net (code "620") (name "Net-(T27-D)") (class "Default")
      (node (ref "R301") (pin "1") (pinfunction "1_1") (pintype "passive"))
      (node (ref "T27") (pin "3") (pinfunction "D_3") (pintype "passive"))
    )
    (net (code "621") (name "Net-(T28-D)") (class "Default")
      (node (ref "R313") (pin "1") (pinfunction "1_1") (pintype "passive"))
      (node (ref "T28") (pin "3") (pinfunction "D_3") (pintype "passive"))
      (node (ref "T31") (pin "1") (pinfunction "G_1") (pintype "passive"))
    )
    (net (code "622") (name "Net-(T28-G)") (class "Default")
      (node (ref "R312") (pin "1") (pinfunction "1_1") (pintype "passive"))
      (node (ref "R362") (pin "2") (pinfunction "2_2") (pintype "passive"))
      (node (ref "T28") (pin "1") (pinfunction "G_1") (pintype "passive"))
    )
    (net (code "623") (name "Net-(T30-D)") (class "Default")
      (node (ref "D19") (pin "C") (pinfunction "C_C") (pintype "passive"))
      (node (ref "T30") (pin "3") (pinfunction "D_3") (pintype "passive"))
    )
    (net (code "624") (name "Net-(T30-G)") (class "Default")
      (node (ref "R322") (pin "2") (pinfunction "2_2") (pintype "passive"))
      (node (ref "R323") (pin "2") (pinfunction "2_2") (pintype "passive"))
      (node (ref "T30") (pin "1") (pinfunction "G_1") (pintype "passive"))
    )
    (net (code "625") (name "Net-(T31-D)") (class "Default")
      (node (ref "R365") (pin "1") (pinfunction "1_1") (pintype "passive"))
      (node (ref "T31") (pin "3") (pinfunction "D_3") (pintype "passive"))
    )
    (net (code "626") (name "Net-(T33-G)") (class "Default")
      (node (ref "C120") (pin "1") (pinfunction "1_1") (pintype "passive"))
      (node (ref "R102") (pin "2") (pinfunction "2_2") (pintype "passive"))
      (node (ref "R104") (pin "2") (pinfunction "2_2") (pintype "passive"))
      (node (ref "R334") (pin "2") (pinfunction "2_2") (pintype "passive"))
      (node (ref "T33") (pin "1") (pinfunction "G_1") (pintype "passive"))
    )
    (net (code "627") (name "Net-(T34-D)") (class "Default")
      (node (ref "R380") (pin "1") (pinfunction "1_1") (pintype "passive"))
      (node (ref "T34") (pin "3") (pinfunction "D_3") (pintype "passive"))
    )
    (net (code "628") (name "Net-(T35-D)") (class "Default")
      (node (ref "R143") (pin "1") (pinfunction "1_1") (pintype "passive"))
      (node (ref "R144") (pin "1") (pinfunction "1_1") (pintype "passive"))
      (node (ref "R145") (pin "1") (pinfunction "1_1") (pintype "passive"))
      (node (ref "R146") (pin "1") (pinfunction "1_1") (pintype "passive"))
      (node (ref "R153") (pin "1") (pinfunction "1_1") (pintype "passive"))
      (node (ref "R154") (pin "1") (pinfunction "1_1") (pintype "passive"))
      (node (ref "R91") (pin "1") (pinfunction "1_1") (pintype "passive"))
      (node (ref "R97") (pin "1") (pinfunction "1_1") (pintype "passive"))
      (node (ref "T35") (pin "3") (pinfunction "D_3") (pintype "passive"))
    )
    (net (code "629") (name "Net-(T37-D)") (class "Default")
      (node (ref "R155") (pin "1") (pinfunction "1_1") (pintype "passive"))
      (node (ref "T37") (pin "3") (pinfunction "D_3") (pintype "passive"))
      (node (ref "T4") (pin "1") (pinfunction "G_1") (pintype "input"))
    )
    (net (code "630") (name "Net-(T37-G)") (class "Default")
      (node (ref "R156") (pin "2") (pinfunction "2_2") (pintype "passive"))
      (node (ref "R167") (pin "2") (pinfunction "2_2") (pintype "passive"))
      (node (ref "T37") (pin "1") (pinfunction "G_1") (pintype "passive"))
    )
    (net (code "631") (name "Net-(T39-D)") (class "Default")
      (node (ref "R379") (pin "2") (pinfunction "2_2") (pintype "passive"))
      (node (ref "R390") (pin "2") (pinfunction "2_2") (pintype "passive"))
      (node (ref "T39") (pin "3") (pinfunction "D_3") (pintype "passive"))
    )
    (net (code "632") (name "Net-(T39-G)") (class "Default")
      (node (ref "R386") (pin "2") (pinfunction "2_2") (pintype "passive"))
      (node (ref "T39") (pin "1") (pinfunction "G_1") (pintype "passive"))
    )
    (net (code "633") (name "Net-(T40-D)") (class "Default")
      (node (ref "R405") (pin "2") (pinfunction "2_2") (pintype "passive"))
      (node (ref "R493") (pin "2") (pinfunction "2_2") (pintype "passive"))
      (node (ref "T40") (pin "3") (pinfunction "D_3") (pintype "passive"))
    )
    (net (code "634") (name "Net-(T40-G)") (class "Default")
      (node (ref "R391") (pin "2") (pinfunction "2_2") (pintype "passive"))
      (node (ref "T40") (pin "1") (pinfunction "G_1") (pintype "passive"))
    )
    (net (code "635") (name "Net-(T41-G)") (class "Default")
      (node (ref "R178") (pin "2") (pinfunction "2_2") (pintype "passive"))
      (node (ref "R179") (pin "2") (pinfunction "2_2") (pintype "passive"))
      (node (ref "T41") (pin "1") (pinfunction "G_1") (pintype "passive"))
    )
    (net (code "636") (name "Net-(T42-D)") (class "Default")
      (node (ref "R185") (pin "1") (pinfunction "1_1") (pintype "passive"))
      (node (ref "T42") (pin "3") (pinfunction "D_3") (pintype "passive"))
      (node (ref "X7") (pin "16") (pinfunction "SDA_16") (pintype "bidirectional"))
    )
    (net (code "637") (name "Net-(T43-D)") (class "Default")
      (node (ref "R186") (pin "1") (pinfunction "1_1") (pintype "passive"))
      (node (ref "T43") (pin "3") (pinfunction "D_3") (pintype "passive"))
      (node (ref "X7") (pin "15") (pinfunction "SCL_15") (pintype "bidirectional"))
    )
    (net (code "638") (name "Net-(T44-D)") (class "Default")
      (node (ref "R496") (pin "2") (pinfunction "2_2") (pintype "passive"))
      (node (ref "R497") (pin "2") (pinfunction "2_2") (pintype "passive"))
      (node (ref "T44") (pin "3") (pinfunction "D_3") (pintype "passive"))
    )
    (net (code "639") (name "Net-(T44-G)") (class "Default")
      (node (ref "R396") (pin "2") (pinfunction "2_2") (pintype "passive"))
      (node (ref "T44") (pin "1") (pinfunction "G_1") (pintype "passive"))
    )
    (net (code "640") (name "Net-(T45-D)") (class "Default")
      (node (ref "R500") (pin "2") (pinfunction "2_2") (pintype "passive"))
      (node (ref "R501") (pin "2") (pinfunction "2_2") (pintype "passive"))
      (node (ref "T45") (pin "3") (pinfunction "D_3") (pintype "passive"))
    )
    (net (code "641") (name "Net-(T45-G)") (class "Default")
      (node (ref "R401") (pin "2") (pinfunction "2_2") (pintype "passive"))
      (node (ref "T45") (pin "1") (pinfunction "G_1") (pintype "passive"))
    )
    (net (code "642") (name "Net-(T46-D)") (class "Default")
      (node (ref "R504") (pin "2") (pinfunction "2_2") (pintype "passive"))
      (node (ref "R505") (pin "2") (pinfunction "2_2") (pintype "passive"))
      (node (ref "T46") (pin "3") (pinfunction "D_3") (pintype "passive"))
    )
    (net (code "643") (name "Net-(T46-G)") (class "Default")
      (node (ref "R406") (pin "2") (pinfunction "2_2") (pintype "passive"))
      (node (ref "T46") (pin "1") (pinfunction "G_1") (pintype "passive"))
    )
    (net (code "644") (name "Net-(T47-D)") (class "Default")
      (node (ref "R382") (pin "1") (pinfunction "1_1") (pintype "passive"))
      (node (ref "T47") (pin "3") (pinfunction "D_3") (pintype "passive"))
    )
    (net (code "645") (name "Net-(T47-G)") (class "Default")
      (node (ref "R414") (pin "1") (pinfunction "1_1") (pintype "passive"))
      (node (ref "T47") (pin "1") (pinfunction "G_1") (pintype "passive"))
      (node (ref "T55") (pin "3") (pinfunction "D_3") (pintype "passive"))
    )
    (net (code "646") (name "Net-(T49-D)") (class "Default")
      (node (ref "C64") (pin "1") (pinfunction "1_1") (pintype "passive"))
      (node (ref "L10") (pin "2") (pinfunction "2_2") (pintype "passive"))
      (node (ref "T49") (pin "3") (pinfunction "D_3") (pintype "passive"))
    )
    (net (code "647") (name "Net-(T49-G)") (class "Default")
      (node (ref "R317") (pin "1") (pinfunction "1_1") (pintype "passive"))
      (node (ref "T49") (pin "1") (pinfunction "G_1") (pintype "input"))
      (node (ref "T50") (pin "3") (pinfunction "D_3") (pintype "passive"))
    )
    (net (code "648") (name "Net-(T50-G)") (class "Default")
      (node (ref "C41") (pin "1") (pinfunction "1_1") (pintype "passive"))
      (node (ref "R439") (pin "2") (pinfunction "2_2") (pintype "passive"))
      (node (ref "R449") (pin "2") (pinfunction "2_2") (pintype "passive"))
      (node (ref "T50") (pin "1") (pinfunction "G_1") (pintype "passive"))
    )
    (net (code "649") (name "Net-(T51-G)") (class "Default")
      (node (ref "R454") (pin "2") (pinfunction "2_2") (pintype "passive"))
      (node (ref "T51") (pin "1") (pinfunction "G_1") (pintype "passive"))
    )
    (net (code "650") (name "Net-(T52-G)") (class "Default")
      (node (ref "R453") (pin "2") (pinfunction "2_2") (pintype "passive"))
      (node (ref "T52") (pin "1") (pinfunction "G_1") (pintype "passive"))
    )
    (net (code "651") (name "Net-(T53-G)") (class "Default")
      (node (ref "R451") (pin "2") (pinfunction "2_2") (pintype "passive"))
      (node (ref "T53") (pin "1") (pinfunction "G_1") (pintype "passive"))
    )
    (net (code "652") (name "Net-(T54-G)") (class "Default")
      (node (ref "R450") (pin "2") (pinfunction "2_2") (pintype "passive"))
      (node (ref "T54") (pin "1") (pinfunction "G_1") (pintype "passive"))
    )
    (net (code "653") (name "Net-(T55-G)") (class "Default")
      (node (ref "C113") (pin "1") (pinfunction "1_1") (pintype "passive"))
      (node (ref "R481") (pin "2") (pinfunction "2_2") (pintype "passive"))
      (node (ref "R482") (pin "2") (pinfunction "2_2") (pintype "passive"))
      (node (ref "R525") (pin "2") (pinfunction "2_2") (pintype "passive"))
      (node (ref "T55") (pin "1") (pinfunction "G_1") (pintype "passive"))
    )
    (net (code "654") (name "Net-(T56-D)") (class "Default")
      (node (ref "R483") (pin "1") (pinfunction "1_1") (pintype "passive"))
      (node (ref "T56") (pin "3") (pinfunction "D_3") (pintype "passive"))
      (node (ref "T57") (pin "1") (pinfunction "G_1") (pintype "passive"))
    )
    (net (code "655") (name "Net-(T58-G)") (class "Default")
      (node (ref "R316") (pin "1") (pinfunction "1_1") (pintype "passive"))
      (node (ref "R484") (pin "1") (pinfunction "1_1") (pintype "passive"))
      (node (ref "T58") (pin "1") (pinfunction "G_1") (pintype "passive"))
    )
    (net (code "656") (name "Net-(T61-G)") (class "Default")
      (node (ref "R130") (pin "2") (pinfunction "2_2") (pintype "passive"))
      (node (ref "T61") (pin "4") (pinfunction "G_4") (pintype "passive"))
    )
    (net (code "657") (name "Net-(T62-G)") (class "Default")
      (node (ref "R113") (pin "2") (pinfunction "2_2") (pintype "passive"))
      (node (ref "T62") (pin "4") (pinfunction "G_4") (pintype "passive"))
    )
    (net (code "658") (name "Net-(T64-D)") (class "Default")
      (node (ref "R539") (pin "1") (pinfunction "1_1") (pintype "passive"))
      (node (ref "R540") (pin "1") (pinfunction "1_1") (pintype "passive"))
      (node (ref "T64") (pin "3") (pinfunction "D_3") (pintype "passive"))
    )
    (net (code "659") (name "Net-(T64-G)") (class "Default")
      (node (ref "R535") (pin "1") (pinfunction "1_1") (pintype "passive"))
      (node (ref "R536") (pin "2") (pinfunction "2_2") (pintype "passive"))
      (node (ref "R538") (pin "2") (pinfunction "2_2") (pintype "passive"))
      (node (ref "T64") (pin "1") (pinfunction "G_1") (pintype "passive"))
    )
    (net (code "660") (name "Net-(T65-D)") (class "Default")
      (node (ref "R534") (pin "1") (pinfunction "1_1") (pintype "passive"))
      (node (ref "R537") (pin "1") (pinfunction "1_1") (pintype "passive"))
      (node (ref "T65") (pin "3") (pinfunction "D_3") (pintype "passive"))
    )
    (net (code "661") (name "Net-(T66-D)") (class "Default")
      (node (ref "R555") (pin "1") (pinfunction "1_1") (pintype "passive"))
      (node (ref "R556") (pin "1") (pinfunction "1_1") (pintype "passive"))
      (node (ref "T66") (pin "3") (pinfunction "D_3") (pintype "passive"))
    )
    (net (code "662") (name "Net-(T67-D)") (class "Default")
      (node (ref "C111") (pin "1") (pinfunction "1_1") (pintype "passive"))
      (node (ref "C290") (pin "1") (pinfunction "1_1") (pintype "passive"))
      (node (ref "C67") (pin "+") (pinfunction "+_+") (pintype "passive"))
      (node (ref "T67") (pin "5") (pinfunction "D_5") (pintype "passive"))
      (node (ref "X1") (pin "2") (pinfunction "2_2") (pintype "input"))
      (node (ref "X10") (pin "2") (pinfunction "2_2") (pintype "input"))
    )
    (net (code "663") (name "Net-(T67-G)") (class "Default")
      (node (ref "C76") (pin "2") (pinfunction "2_2") (pintype "passive"))
      (node (ref "R524") (pin "1") (pinfunction "1_1") (pintype "passive"))
      (node (ref "R566") (pin "2") (pinfunction "2_2") (pintype "passive"))
      (node (ref "T67") (pin "4") (pinfunction "G_4") (pintype "input"))
    )
    (net (code "664") (name "Net-(T68-D)") (class "Default")
      (node (ref "R566") (pin "1") (pinfunction "1_1") (pintype "passive"))
      (node (ref "T68") (pin "3") (pinfunction "D_3") (pintype "passive"))
    )
    (net (code "665") (name "Net-(TP1-TP)") (class "Default")
      (node (ref "R118") (pin "2") (pinfunction "2_2") (pintype "passive"))
      (node (ref "TP1") (pin "P$1") (pinfunction "TP_P$1") (pintype "input"))
    )
    (net (code "666") (name "Net-(TP4-TP)") (class "Default")
      (node (ref "C12") (pin "1") (pinfunction "1_1") (pintype "passive"))
      (node (ref "D2") (pin "2") (pinfunction "2_2") (pintype "passive"))
      (node (ref "F1") (pin "1") (pinfunction "1_1") (pintype "passive"))
      (node (ref "TP4") (pin "P$1") (pinfunction "TP_P$1") (pintype "input"))
      (node (ref "X2") (pin "3") (pinfunction "3_3") (pintype "passive"))
    )
    (net (code "667") (name "Net-(TP5-TP)") (class "Default")
      (node (ref "C12") (pin "2") (pinfunction "2_2") (pintype "passive"))
      (node (ref "D2") (pin "1") (pinfunction "1_1") (pintype "passive"))
      (node (ref "R213") (pin "1") (pinfunction "1_1") (pintype "passive"))
      (node (ref "T9") (pin "D1") (pinfunction "D_D1") (pintype "passive"))
      (node (ref "T9") (pin "D10") (pinfunction "D_D10") (pintype "passive"))
      (node (ref "T9") (pin "D11") (pinfunction "D_D11") (pintype "passive"))
      (node (ref "T9") (pin "D12") (pinfunction "D_D12") (pintype "passive"))
      (node (ref "T9") (pin "D13") (pinfunction "D_D13") (pintype "passive"))
      (node (ref "T9") (pin "D14") (pinfunction "D_D14") (pintype "passive"))
      (node (ref "T9") (pin "D15") (pinfunction "D_D15") (pintype "passive"))
      (node (ref "T9") (pin "D2") (pinfunction "D_D2") (pintype "passive"))
      (node (ref "T9") (pin "D3") (pinfunction "D_D3") (pintype "passive"))
      (node (ref "T9") (pin "D4") (pinfunction "D_D4") (pintype "passive"))
      (node (ref "T9") (pin "D5") (pinfunction "D_D5") (pintype "passive"))
      (node (ref "T9") (pin "D6") (pinfunction "D_D6") (pintype "passive"))
      (node (ref "T9") (pin "D7") (pinfunction "D_D7") (pintype "passive"))
      (node (ref "T9") (pin "D8") (pinfunction "D_D8") (pintype "passive"))
      (node (ref "T9") (pin "D9") (pinfunction "D_D9") (pintype "passive"))
      (node (ref "TP5") (pin "P$1") (pinfunction "TP_P$1") (pintype "input"))
      (node (ref "X2") (pin "2") (pinfunction "2_2") (pintype "passive"))
    )
    (net (code "668") (name "Net-(TP8-TP)") (class "Default")
      (node (ref "C262") (pin "1") (pinfunction "1_1") (pintype "passive"))
      (node (ref "R207") (pin "1") (pinfunction "1_1") (pintype "passive"))
      (node (ref "TP8") (pin "P$1") (pinfunction "TP_P$1") (pintype "input"))
    )
    (net (code "669") (name "Net-(TP9-TP)") (class "Default")
      (node (ref "R438") (pin "1") (pinfunction "1_1") (pintype "passive"))
      (node (ref "TP9") (pin "P$1") (pinfunction "TP_P$1") (pintype "input"))
    )
    (net (code "670") (name "Net-(TP27-TP)") (class "Default")
      (node (ref "R49") (pin "1") (pinfunction "1_1") (pintype "passive"))
      (node (ref "TP27") (pin "P$1") (pinfunction "TP_P$1") (pintype "input"))
      (node (ref "X2") (pin "5") (pinfunction "5_5") (pintype "passive"))
    )
    (net (code "671") (name "Net-(TP42-TP)") (class "Default")
      (node (ref "R270") (pin "2") (pinfunction "2_2") (pintype "passive"))
      (node (ref "TP42") (pin "P$1") (pinfunction "TP_P$1") (pintype "input"))
    )
    (net (code "672") (name "Net-(TP43-TP)") (class "Default")
      (node (ref "R269") (pin "2") (pinfunction "2_2") (pintype "passive"))
      (node (ref "TP43") (pin "P$1") (pinfunction "TP_P$1") (pintype "input"))
    )
    (net (code "673") (name "Net-(TP44-TP)") (class "Default")
      (node (ref "R268") (pin "2") (pinfunction "2_2") (pintype "passive"))
      (node (ref "TP44") (pin "P$1") (pinfunction "TP_P$1") (pintype "input"))
    )
    (net (code "674") (name "Net-(TP45-TP)") (class "Default")
      (node (ref "R267") (pin "2") (pinfunction "2_2") (pintype "passive"))
      (node (ref "TP45") (pin "P$1") (pinfunction "TP_P$1") (pintype "input"))
    )
    (net (code "675") (name "Net-(X7-HOTPLUGDETECT{slash}HEAC-)") (class "Default")
      (node (ref "R178") (pin "1") (pinfunction "1_1") (pintype "passive"))
      (node (ref "X7") (pin "19") (pinfunction "HOTPLUGDETECT/HEAC-_19") (pintype "bidirectional"))
    )
    (net (code "676") (name "Net-(X7-TMDSCLOCK+)") (class "Default")
      (node (ref "R89") (pin "2") (pinfunction "2_2") (pintype "passive"))
      (node (ref "X7") (pin "10") (pinfunction "TMDSCLOCK+_10") (pintype "input"))
    )
    (net (code "677") (name "Net-(X7-TMDSCLOCK-)") (class "Default")
      (node (ref "R90") (pin "2") (pinfunction "2_2") (pintype "passive"))
      (node (ref "X7") (pin "12") (pinfunction "TMDSCLOCK-_12") (pintype "input"))
    )
    (net (code "678") (name "Net-(X7-TMDSDATA0+)") (class "Default")
      (node (ref "R87") (pin "2") (pinfunction "2_2") (pintype "passive"))
      (node (ref "X7") (pin "7") (pinfunction "TMDSDATA0+_7") (pintype "input"))
    )
    (net (code "679") (name "Net-(X7-TMDSDATA0-)") (class "Default")
      (node (ref "R88") (pin "2") (pinfunction "2_2") (pintype "passive"))
      (node (ref "X7") (pin "9") (pinfunction "TMDSDATA0-_9") (pintype "input"))
    )
    (net (code "680") (name "Net-(X7-TMDSDATA1+)") (class "Default")
      (node (ref "R79") (pin "2") (pinfunction "2_2") (pintype "passive"))
      (node (ref "X7") (pin "4") (pinfunction "TMDSDATA1+_4") (pintype "input"))
    )
    (net (code "681") (name "Net-(X7-TMDSDATA1-)") (class "Default")
      (node (ref "R86") (pin "2") (pinfunction "2_2") (pintype "passive"))
      (node (ref "X7") (pin "6") (pinfunction "TMDSDATA1-_6") (pintype "input"))
    )
    (net (code "682") (name "Net-(X7-TMDSDATA2+)") (class "Default")
      (node (ref "R75") (pin "2") (pinfunction "2_2") (pintype "passive"))
      (node (ref "X7") (pin "1") (pinfunction "TMDSDATA2+_1") (pintype "input"))
    )
    (net (code "683") (name "Net-(X7-TMDSDATA2-)") (class "Default")
      (node (ref "R77") (pin "2") (pinfunction "2_2") (pintype "passive"))
      (node (ref "X7") (pin "3") (pinfunction "TMDSDATA2-_3") (pintype "input"))
    )
    (net (code "684") (name "Net-(X15-VBUS)") (class "Default")
      (node (ref "D13") (pin "A") (pinfunction "A_A") (pintype "passive"))
      (node (ref "D31") (pin "A") (pinfunction "A_A") (pintype "passive"))
      (node (ref "R298") (pin "2") (pinfunction "2_2") (pintype "passive"))
      (node (ref "X15") (pin "1") (pinfunction "VBUS_1") (pintype "output"))
    )
    (net (code "685") (name "Net-(X18-ALERT#)") (class "Default")
      (node (ref "R292") (pin "2") (pinfunction "2_2") (pintype "passive"))
      (node (ref "R59") (pin "1") (pinfunction "1_1") (pintype "passive"))
      (node (ref "X18") (pin "62") (pinfunction "ALERT#_62") (pintype "output"))
    )
    (net (code "686") (name "Net-(X18-LED1#)") (class "Default")
      (node (ref "R175") (pin "2") (pinfunction "2_2") (pintype "passive"))
      (node (ref "X18") (pin "6") (pinfunction "LED1#_6") (pintype "output"))
    )
    (net (code "687") (name "Net-(X18-LED2#)") (class "Default")
      (node (ref "R174") (pin "2") (pinfunction "2_2") (pintype "passive"))
      (node (ref "X18") (pin "16") (pinfunction "LED2#_16") (pintype "output"))
    )
    (net (code "688") (name "Net-(X18-PETN0)") (class "Default")
      (node (ref "C145") (pin "2") (pinfunction "2_2") (pintype "passive"))
      (node (ref "X18") (pin "37") (pinfunction "PETN0_37") (pintype "bidirectional"))
    )
    (net (code "689") (name "Net-(X18-PETP0)") (class "Default")
      (node (ref "C144") (pin "2") (pinfunction "2_2") (pintype "passive"))
      (node (ref "X18") (pin "35") (pinfunction "PETP0_35") (pintype "bidirectional"))
    )
    (net (code "690") (name "Net-(X18-UART_WAKE#)") (class "Default")
      (node (ref "R294") (pin "1") (pinfunction "1_1") (pintype "passive"))
      (node (ref "R295") (pin "2") (pinfunction "2_2") (pintype "passive"))
      (node (ref "X18") (pin "20") (pinfunction "UART_WAKE#_20") (pintype "output"))
    )
    (net (code "691") (name "Net-(X18-USB_D+)") (class "Default")
      (node (ref "R168") (pin "2") (pinfunction "2_2") (pintype "passive"))
      (node (ref "X18") (pin "3") (pinfunction "USB_D+_3") (pintype "bidirectional"))
    )
    (net (code "692") (name "Net-(X18-USB_D-)") (class "Default")
      (node (ref "R166") (pin "2") (pinfunction "2_2") (pintype "passive"))
      (node (ref "X18") (pin "5") (pinfunction "USB_D-_5") (pintype "bidirectional"))
    )
    (net (code "693") (name "Net-(X32-FULL_CARD_POWER_OFF#)") (class "Default")
      (node (ref "R276") (pin "1") (pinfunction "1_1") (pintype "passive"))
      (node (ref "X32") (pin "6") (pinfunction "FULL_CARD_POWER_OFF#_6") (pintype "input"))
    )
    (net (code "694") (name "Net-(X32-GPIO_0{slash}SMB_CLK{slash}I2C_SCL{slash}SIM_DETECT_2)") (class "Default")
      (node (ref "R277") (pin "2") (pinfunction "2_2") (pintype "passive"))
      (node (ref "X32") (pin "40") (pinfunction "GPIO_0/SMB_CLK/I2C_SCL/SIM_DETECT_2_40") (pintype "bidirectional"))
    )
    (net (code "695") (name "Net-(X32-GPIO_9{slash}DAS{slash}DSS{slash}LED_1#)") (class "Default")
      (node (ref "R128") (pin "2") (pinfunction "2_2") (pintype "passive"))
      (node (ref "X32") (pin "10") (pinfunction "GPIO_9/DAS/DSS/LED_1#_10") (pintype "bidirectional"))
    )
    (net (code "696") (name "Net-(X32-USB_D+)") (class "Default")
      (node (ref "R46") (pin "2") (pinfunction "2_2") (pintype "passive"))
      (node (ref "X32") (pin "7") (pinfunction "USB_D+_7") (pintype "bidirectional"))
    )
    (net (code "697") (name "Net-(X32-USB_D-)") (class "Default")
      (node (ref "R48") (pin "2") (pinfunction "2_2") (pintype "passive"))
      (node (ref "X32") (pin "9") (pinfunction "USB_D-_9") (pintype "bidirectional"))
    )
    (net (code "698") (name "Net-(X32-USIM1_CLK)") (class "Default")
      (node (ref "C93") (pin "1") (pinfunction "1_1") (pintype "passive"))
      (node (ref "R126") (pin "1") (pinfunction "1_1") (pintype "passive"))
      (node (ref "X32") (pin "32") (pinfunction "USIM1_CLK_32") (pintype "output"))
    )
    (net (code "699") (name "Net-(X32-USIM1_DATA)") (class "Default")
      (node (ref "C94") (pin "1") (pinfunction "1_1") (pintype "passive"))
      (node (ref "R125") (pin "1") (pinfunction "1_1") (pintype "passive"))
      (node (ref "X32") (pin "34") (pinfunction "USIM1_DATA_34") (pintype "bidirectional"))
    )
    (net (code "700") (name "Net-(X32-USIM1_RESET)") (class "Default")
      (node (ref "C56") (pin "1") (pinfunction "1_1") (pintype "passive"))
      (node (ref "R127") (pin "1") (pinfunction "1_1") (pintype "passive"))
      (node (ref "X32") (pin "30") (pinfunction "USIM1_RESET_30") (pintype "output"))
    )
    (net (code "701") (name "Net-(X32-W_DISABLE1#)") (class "Default")
      (node (ref "R135") (pin "2") (pinfunction "2_2") (pintype "passive"))
      (node (ref "X32") (pin "8") (pinfunction "W_DISABLE1#_8") (pintype "input"))
    )
    (net (code "702") (name "Net-(X33-ALERT#{slash}NC)") (class "Default")
      (node (ref "R304") (pin "2") (pinfunction "2_2") (pintype "passive"))
      (node (ref "R305") (pin "1") (pinfunction "1_1") (pintype "passive"))
      (node (ref "X33") (pin "44") (pinfunction "ALERT#/NC_44") (pintype "output"))
    )
    (net (code "703") (name "Net-(X33-DAS{slash}DSS{slash}LED_1#)") (class "Default")
      (node (ref "R306") (pin "2") (pinfunction "2_2") (pintype "passive"))
      (node (ref "X33") (pin "10") (pinfunction "DAS/DSS/LED_1#_10") (pintype "bidirectional"))
    )
    (net (code "704") (name "Net-(X33-PETN0{slash}SATA-A-)") (class "Default")
      (node (ref "C107") (pin "2") (pinfunction "2_2") (pintype "passive"))
      (node (ref "X33") (pin "47") (pinfunction "PETN0/SATA-A-_47") (pintype "bidirectional"))
    )
    (net (code "705") (name "Net-(X33-PETP0{slash}SATA-A+)") (class "Default")
      (node (ref "C108") (pin "2") (pinfunction "2_2") (pintype "passive"))
      (node (ref "X33") (pin "49") (pinfunction "PETP0/SATA-A+_49") (pintype "bidirectional"))
    )
    (net (code "706") (name "RGB_DIST_5V") (class "Default")
      (node (ref "R256") (pin "2") (pinfunction "2_2") (pintype "passive"))
      (node (ref "TP38") (pin "P$1") (pinfunction "TP_P$1") (pintype "input"))
      (node (ref "X12") (pin "1") (pinfunction "1_1") (pintype "passive"))
    )
    (net (code "707") (name "RGB_LED_UC->FU_5V") (class "Default")
      (node (ref "R437") (pin "2") (pinfunction "2_2") (pintype "passive"))
      (node (ref "TP39") (pin "P$1") (pinfunction "TP_P$1") (pintype "input"))
      (node (ref "X13") (pin "44") (pinfunction "44_44") (pintype "passive"))
    )
    (net (code "708") (name "RGB_LVL_SHIFT_VCC") (class "Default")
      (node (ref "C26") (pin "1") (pinfunction "1_1") (pintype "passive"))
      (node (ref "IC17") (pin "1") (pinfunction "VCCA_1") (pintype "input"))
      (node (ref "R238") (pin "1") (pinfunction "1_1") (pintype "passive"))
      (node (ref "R250") (pin "1") (pinfunction "1_1") (pintype "passive"))
      (node (ref "R531") (pin "1") (pinfunction "1_1") (pintype "passive"))
      (node (ref "R543") (pin "2") (pinfunction "2_2") (pintype "passive"))
      (node (ref "R544") (pin "1") (pinfunction "1_1") (pintype "passive"))
      (node (ref "R547") (pin "2") (pinfunction "2_2") (pintype "passive"))
    )
    (net (code "709") (name "SECBRD_V_BCKUP") (class "Default")
      (node (ref "R526") (pin "1") (pinfunction "1_1") (pintype "passive"))
      (node (ref "X4") (pin "1") (pinfunction "1_1") (pintype "passive"))
    )
    (net (code "710") (name "SENSOR1_INT1") (class "Default")
      (node (ref "IC8") (pin "6") (pinfunction "I/O4_6") (pintype "passive"))
      (node (ref "R29") (pin "1") (pinfunction "1_1") (pintype "passive"))
      (node (ref "X4") (pin "20") (pinfunction "20_20") (pintype "passive"))
    )
    (net (code "711") (name "SENSOR1_INT2") (class "Default")
      (node (ref "IC8") (pin "3") (pinfunction "I/O2_3") (pintype "passive"))
      (node (ref "R28") (pin "1") (pinfunction "1_1") (pintype "passive"))
      (node (ref "X4") (pin "18") (pinfunction "18_18") (pintype "passive"))
    )
    (net (code "712") (name "SENSOR1_SCL") (class "Default")
      (node (ref "IC3") (pin "13") (pinfunction "SCL/SCLK_13") (pintype "input"))
      (node (ref "R311") (pin "1") (pinfunction "1_1") (pintype "passive"))
    )
    (net (code "713") (name "SENSOR1_SDA") (class "Default")
      (node (ref "IC8") (pin "1") (pinfunction "I/O1_1") (pintype "passive"))
      (node (ref "R24") (pin "1") (pinfunction "1_1") (pintype "passive"))
      (node (ref "X4") (pin "17") (pinfunction "17_17") (pintype "passive"))
    )
    (net (code "714") (name "SENSOR1_VDD") (class "Default")
      (node (ref "R25") (pin "1") (pinfunction "1_1") (pintype "passive"))
      (node (ref "R340") (pin "2") (pinfunction "2_2") (pintype "passive"))
    )
    (net (code "715") (name "SENSOR2_N") (class "Default")
      (node (ref "X22") (pin "2") (pinfunction "2_2") (pintype "passive"))
      (node (ref "X4") (pin "24") (pinfunction "24_24") (pintype "passive"))
    )
    (net (code "716") (name "SENSOR2_P") (class "Default")
      (node (ref "X22") (pin "1") (pinfunction "1_1") (pintype "passive"))
      (node (ref "X4") (pin "22") (pinfunction "22_22") (pintype "passive"))
    )
    (net (code "717") (name "SENSOR3_N") (class "Default")
      (node (ref "X22") (pin "4") (pinfunction "4_4") (pintype "passive"))
      (node (ref "X4") (pin "28") (pinfunction "28_28") (pintype "passive"))
    )
    (net (code "718") (name "SENSOR3_P") (class "Default")
      (node (ref "X22") (pin "3") (pinfunction "3_3") (pintype "passive"))
      (node (ref "X4") (pin "26") (pinfunction "26_26") (pintype "passive"))
    )
    (net (code "719") (name "SENSOR4") (class "Default")
      (node (ref "X20") (pin "1") (pinfunction "1_1") (pintype "passive"))
      (node (ref "X4") (pin "7") (pinfunction "7_7") (pintype "passive"))
    )
    (net (code "720") (name "SENSOR4+") (class "Default")
      (node (ref "X27") (pin "1") (pinfunction "1_1") (pintype "passive"))
      (node (ref "X4") (pin "9") (pinfunction "9_9") (pintype "passive"))
    )
    (net (code "721") (name "SENSOR4-") (class "Default")
      (node (ref "X27") (pin "2") (pinfunction "2_2") (pintype "passive"))
      (node (ref "X4") (pin "11") (pinfunction "11_11") (pintype "passive"))
    )
    (net (code "722") (name "SENSOR5") (class "Default")
      (node (ref "X22") (pin "5") (pinfunction "5_5") (pintype "passive"))
      (node (ref "X4") (pin "23") (pinfunction "23_23") (pintype "passive"))
    )
    (net (code "723") (name "SENSOR6") (class "Default")
      (node (ref "X13") (pin "93") (pinfunction "93_93") (pintype "passive"))
      (node (ref "X4") (pin "25") (pinfunction "25_25") (pintype "passive"))
    )
    (net (code "724") (name "SENSOR7") (class "Default")
      (node (ref "X13") (pin "81") (pinfunction "81_81") (pintype "passive"))
      (node (ref "X4") (pin "27") (pinfunction "27_27") (pintype "passive"))
    )
    (net (code "725") (name "SIM_CLK") (class "Default")
      (node (ref "R126") (pin "2") (pinfunction "2_2") (pintype "passive"))
      (node (ref "X11") (pin "4") (pinfunction "4_4") (pintype "passive"))
      (node (ref "X26") (pin "C3") (pinfunction "CLK_C3") (pintype "input"))
    )
    (net (code "726") (name "SIM_IO") (class "Default")
      (node (ref "R125") (pin "2") (pinfunction "2_2") (pintype "passive"))
      (node (ref "X11") (pin "5") (pinfunction "5_5") (pintype "passive"))
      (node (ref "X26") (pin "C7") (pinfunction "I/O_C7") (pintype "bidirectional"))
    )
    (net (code "727") (name "SIM_RST") (class "Default")
      (node (ref "R127") (pin "2") (pinfunction "2_2") (pintype "passive"))
      (node (ref "X11") (pin "3") (pinfunction "3_3") (pintype "passive"))
      (node (ref "X26") (pin "C2") (pinfunction "RST_C2") (pintype "input"))
    )
    (net (code "728") (name "SINGLE_WIRE_CAN_BAT_3V3") (class "Default")
      (node (ref "D7") (pin "2") (pinfunction "A2_2") (pintype "passive"))
      (node (ref "R272") (pin "1") (pinfunction "1_1") (pintype "passive"))
      (node (ref "R441") (pin "2") (pinfunction "2_2") (pintype "passive"))
      (node (ref "R473") (pin "1") (pinfunction "1_1") (pintype "passive"))
      (node (ref "R93") (pin "1") (pinfunction "1_1") (pintype "passive"))
      (node (ref "TP61") (pin "P$1") (pinfunction "TP_P$1") (pintype "input"))
    )
    (net (code "729") (name "SUSCLK_32KHZ_1V8") (class "Default")
      (node (ref "IC2") (pin "2") (pinfunction "A_2") (pintype "input"))
      (node (ref "R193") (pin "1") (pinfunction "1_1") (pintype "passive"))
      (node (ref "R30") (pin "2") (pinfunction "2_2") (pintype "passive"))
    )
    (net (code "730") (name "SUSCLK_32KHZ_3V3") (class "Default")
      (node (ref "R147") (pin "2") (pinfunction "2_2") (pintype "passive"))
      (node (ref "X18") (pin "50") (pinfunction "SUSCLK_32KHZ_50") (pintype "input"))
      (node (ref "X33") (pin "68") (pinfunction "SUSCLK_32KHZ_68") (pintype "input"))
    )
    (net (code "731") (name "TYPE_A_1_USB_D_N") (class "Default")
      (node (ref "IC19") (pin "3") (pinfunction "USBDM_DN2/PRT_DIS_M2_3") (pintype "bidirectional"))
      (node (ref "R73") (pin "1") (pinfunction "1_1") (pintype "passive"))
    )
    (net (code "732") (name "TYPE_A_1_USB_D_P") (class "Default")
      (node (ref "IC19") (pin "4") (pinfunction "USBDP_DN2/PRT_DIS_P2_4") (pintype "bidirectional"))
      (node (ref "R74") (pin "1") (pinfunction "1_1") (pintype "passive"))
    )
    (net (code "733") (name "TYPE_A_2_USB_D_N") (class "Default")
      (node (ref "IC19") (pin "6") (pinfunction "USBDM_DN3/PRT_DIS_M3_6") (pintype "bidirectional"))
      (node (ref "R289") (pin "1") (pinfunction "1_1") (pintype "passive"))
    )
    (net (code "734") (name "TYPE_A_2_USB_D_P") (class "Default")
      (node (ref "IC19") (pin "7") (pinfunction "USBDP_DN3/PRT_DIS_P3_7") (pintype "bidirectional"))
      (node (ref "R290") (pin "1") (pinfunction "1_1") (pintype "passive"))
    )
    (net (code "735") (name "UART_DEBUG->JETSON_1V8") (class "Default")
      (node (ref "MOD1") (pin "238") (pinfunction "UART2_RXD_238") (pintype "input"))
      (node (ref "R118") (pin "1") (pinfunction "1_1") (pintype "passive"))
      (node (ref "R121") (pin "1") (pinfunction "1_1") (pintype "passive"))
    )
    (net (code "736") (name "UART_GPS->UC_3V3") (class "Default")
      (node (ref "IC20") (pin "50") (pinfunction "PB11_50") (pintype "bidirectional"))
      (node (ref "R14") (pin "1") (pinfunction "1_1") (pintype "passive"))
    )
    (net (code "737") (name "UART_JETSON->DEBUG_1V8") (class "Default")
      (node (ref "R122") (pin "1") (pinfunction "1_1") (pintype "passive"))
      (node (ref "R235") (pin "1") (pinfunction "1_1") (pintype "passive"))
      (node (ref "TP2") (pin "P$1") (pinfunction "TP_P$1") (pintype "input"))
    )
    (net (code "738") (name "UART_JETSON->STM32_1V8") (class "Default")
      (node (ref "IC11") (pin "6") (pinfunction "A4_6") (pintype "bidirectional"))
      (node (ref "R244") (pin "1") (pinfunction "1_1") (pintype "passive"))
    )
    (net (code "739") (name "UART_JETSON->STM32_3V3") (class "Default")
      (node (ref "IC20") (pin "31") (pinfunction "PC5_31") (pintype "bidirectional"))
      (node (ref "R52") (pin "2") (pinfunction "2_2") (pintype "passive"))
    )
    (net (code "740") (name "UART_STM32->JETSON_1V8") (class "Default")
      (node (ref "MOD1") (pin "205") (pinfunction "UART1_RXD_205") (pintype "input"))
      (node (ref "R18") (pin "1") (pinfunction "1_1") (pintype "passive"))
    )
    (net (code "741") (name "UART_STM32->JETSON_3V3") (class "Default")
      (node (ref "IC11") (pin "17") (pinfunction "B5_17") (pintype "bidirectional"))
      (node (ref "R243") (pin "1") (pinfunction "1_1") (pintype "passive"))
    )
    (net (code "742") (name "UART_UC->GPS_3V3") (class "Default")
      (node (ref "IC20") (pin "47") (pinfunction "PB10_47") (pintype "bidirectional"))
      (node (ref "R13") (pin "1") (pinfunction "1_1") (pintype "passive"))
    )
    (net (code "743") (name "UC_ADC_1V8") (class "Default")
      (node (ref "C32") (pin "1") (pinfunction "1_1") (pintype "passive"))
      (node (ref "IC20") (pin "57") (pinfunction "PD10_57") (pintype "bidirectional"))
      (node (ref "R351") (pin "2") (pinfunction "2_2") (pintype "passive"))
    )
    (net (code "744") (name "UC_ADC_3V3") (class "Default")
      (node (ref "C69") (pin "1") (pinfunction "1_1") (pintype "passive"))
      (node (ref "IC20") (pin "58") (pinfunction "PD11_58") (pintype "bidirectional"))
      (node (ref "R70") (pin "2") (pinfunction "2_2") (pintype "passive"))
    )
    (net (code "745") (name "UC_ADC_3V8") (class "Default")
      (node (ref "C33") (pin "1") (pinfunction "1_1") (pintype "passive"))
      (node (ref "IC20") (pin "56") (pinfunction "PD9_56") (pintype "bidirectional"))
      (node (ref "R352") (pin "2") (pinfunction "2_2") (pintype "passive"))
    )
    (net (code "746") (name "UC_ADC_5V") (class "Default")
      (node (ref "C42") (pin "1") (pinfunction "1_1") (pintype "passive"))
      (node (ref "IC20") (pin "59") (pinfunction "PD12_59") (pintype "bidirectional"))
      (node (ref "R66") (pin "2") (pinfunction "2_2") (pintype "passive"))
    )
    (net (code "747") (name "UC_ADC_12V") (class "Default")
      (node (ref "C83") (pin "1") (pinfunction "1_1") (pintype "passive"))
      (node (ref "IC20") (pin "17") (pinfunction "PC2_17") (pintype "bidirectional"))
      (node (ref "R421") (pin "2") (pinfunction "2_2") (pintype "passive"))
    )
    (net (code "748") (name "UC_ADC_12V_CAPS") (class "Default")
      (node (ref "C84") (pin "1") (pinfunction "1_1") (pintype "passive"))
      (node (ref "IC20") (pin "18") (pinfunction "PC3_18") (pintype "bidirectional"))
      (node (ref "R422") (pin "2") (pinfunction "2_2") (pintype "passive"))
    )
    (net (code "749") (name "UC_ADC_FU_IR") (class "Default")
      (node (ref "C228") (pin "1") (pinfunction "1_1") (pintype "passive"))
      (node (ref "IC20") (pin "22") (pinfunction "PA2_22") (pintype "bidirectional"))
      (node (ref "R469") (pin "2") (pinfunction "2_2") (pintype "passive"))
    )
    (net (code "750") (name "UC_ADC_HW_VERSION") (class "Default")
      (node (ref "C47") (pin "1") (pinfunction "1_1") (pintype "passive"))
      (node (ref "IC20") (pin "51") (pinfunction "PB12_51") (pintype "bidirectional"))
      (node (ref "R108") (pin "1") (pinfunction "1_1") (pintype "passive"))
      (node (ref "R82") (pin "2") (pinfunction "2_2") (pintype "passive"))
    )
    (net (code "751") (name "UC_ADC_INA240_REF") (class "Default")
      (node (ref "C225") (pin "1") (pinfunction "1_1") (pintype "passive"))
      (node (ref "IC20") (pin "60") (pinfunction "PD13_60") (pintype "bidirectional"))
      (node (ref "R464") (pin "2") (pinfunction "2_2") (pintype "passive"))
    )
    (net (code "752") (name "UC_ADC_INA240_SIG") (class "Default")
      (node (ref "C218") (pin "1") (pinfunction "1_1") (pintype "passive"))
      (node (ref "IC20") (pin "61") (pinfunction "PD14_61") (pintype "bidirectional"))
      (node (ref "R462") (pin "2") (pinfunction "2_2") (pintype "passive"))
    )
    (net (code "753") (name "UC_ADC_PVCC") (class "Default")
      (node (ref "C172") (pin "1") (pinfunction "1_1") (pintype "passive"))
      (node (ref "IC20") (pin "16") (pinfunction "PC1_16") (pintype "bidirectional"))
      (node (ref "R429") (pin "2") (pinfunction "2_2") (pintype "passive"))
    )
    (net (code "754") (name "UC_ADC_VBAT_SW") (class "Default")
      (node (ref "C89") (pin "1") (pinfunction "1_1") (pintype "passive"))
      (node (ref "IC20") (pin "20") (pinfunction "PA0_20") (pintype "bidirectional"))
      (node (ref "R428") (pin "2") (pinfunction "2_2") (pintype "passive"))
    )
    (net (code "755") (name "UC_CAM0_TRIGGER_TO_SENSOR_3V3") (class "Default")
      (node (ref "R190") (pin "1") (pinfunction "1_1") (pintype "passive"))
      (node (ref "TP78") (pin "P$1") (pinfunction "TP_P$1") (pintype "input"))
      (node (ref "X25") (pin "6") (pinfunction "6_6") (pintype "passive"))
    )
    (net (code "756") (name "UC_CAM2_TRIGGER_TO_SENSOR_3V3") (class "Default")
      (node (ref "R136") (pin "1") (pinfunction "1_1") (pintype "passive"))
      (node (ref "TP79") (pin "P$1") (pinfunction "TP_P$1") (pintype "input"))
      (node (ref "X13") (pin "59") (pinfunction "59_59") (pintype "passive"))
    )
    (net (code "757") (name "UC_CAM3_TRIGGER_TO_SENSOR_1V8") (class "Default")
      (node (ref "R226") (pin "2") (pinfunction "2_2") (pintype "passive"))
      (node (ref "X13") (pin "57") (pinfunction "57_57") (pintype "passive"))
    )
    (net (code "758") (name "UC_CAM3_TRIGGER_TO_SENSOR_3V3") (class "Default")
      (node (ref "IC23") (pin "2") (pinfunction "A_2") (pintype "input"))
      (node (ref "R216") (pin "1") (pinfunction "1_1") (pintype "passive"))
      (node (ref "R227") (pin "2") (pinfunction "2_2") (pintype "passive"))
    )
    (net (code "759") (name "UC_CAP_CHARGE_EN_3V3") (class "Default")
      (node (ref "IC35") (pin "2") (pinfunction "CE_2") (pintype "input"))
      (node (ref "R37") (pin "1") (pinfunction "1_1") (pintype "passive"))
    )
    (net (code "760") (name "UC_FAN_AUX_TACH_3V3") (class "Default")
      (node (ref "IC20") (pin "73") (pinfunction "PA12_73") (pintype "bidirectional"))
      (node (ref "R540") (pin "2") (pinfunction "2_2") (pintype "passive"))
    )
    (net (code "761") (name "UC_FAN_MAIN_TACH_3V3") (class "Default")
      (node (ref "IC20") (pin "89") (pinfunction "PD7_89") (pintype "bidirectional"))
      (node (ref "R124") (pin "2") (pinfunction "2_2") (pintype "passive"))
    )
    (net (code "762") (name "UC_FAN_PWR_EN_3V3") (class "Default")
      (node (ref "R550") (pin "2") (pinfunction "2_2") (pintype "passive"))
      (node (ref "R564") (pin "1") (pinfunction "1_1") (pintype "passive"))
      (node (ref "T68") (pin "1") (pinfunction "G_1") (pintype "passive"))
    )
    (net (code "763") (name "UC_FU_740NM_3V3") (class "Default")
      (node (ref "R436") (pin "1") (pinfunction "1_1") (pintype "passive"))
      (node (ref "X13") (pin "69") (pinfunction "69_69") (pintype "passive"))
    )
    (net (code "764") (name "UC_FU_850NM_LEFT_3V3") (class "Default")
      (node (ref "R434") (pin "1") (pinfunction "1_1") (pintype "passive"))
      (node (ref "X13") (pin "65") (pinfunction "65_65") (pintype "passive"))
    )
    (net (code "765") (name "UC_FU_850NM_RIGHT_3V3") (class "Default")
      (node (ref "R435") (pin "1") (pinfunction "1_1") (pintype "passive"))
      (node (ref "X13") (pin "67") (pinfunction "67_67") (pintype "passive"))
    )
    (net (code "766") (name "UC_FU_940NM_LEFT_3V3") (class "Default")
      (node (ref "R432") (pin "1") (pinfunction "1_1") (pintype "passive"))
      (node (ref "X13") (pin "61") (pinfunction "61_61") (pintype "passive"))
    )
    (net (code "767") (name "UC_FU_940NM_RIGHT_3V3") (class "Default")
      (node (ref "R433") (pin "1") (pinfunction "1_1") (pintype "passive"))
      (node (ref "X13") (pin "63") (pinfunction "63_63") (pintype "passive"))
    )
    (net (code "768") (name "UC_FU_OPT_2_3V3") (class "Default")
      (node (ref "R239") (pin "1") (pinfunction "1_1") (pintype "passive"))
      (node (ref "X13") (pin "79") (pinfunction "79_79") (pintype "passive"))
    )
    (net (code "769") (name "UC_FU_RFID_GPO_3V3") (class "Default")
      (node (ref "R241") (pin "1") (pinfunction "1_1") (pintype "passive"))
      (node (ref "X13") (pin "97") (pinfunction "97_97") (pintype "passive"))
    )
    (net (code "770") (name "UC_FU_WHITE_3V3") (class "Default")
      (node (ref "R554") (pin "1") (pinfunction "1_1") (pintype "passive"))
      (node (ref "X13") (pin "85") (pinfunction "85_85") (pintype "passive"))
    )
    (net (code "771") (name "UC_I2C_SCL_1V8") (class "Default")
      (node (ref "C288") (pin "1") (pinfunction "1_1") (pintype "passive"))
      (node (ref "IC24") (pin "11") (pinfunction "SCL_11") (pintype "input"))
      (node (ref "R286") (pin "1") (pinfunction "1_1") (pintype "passive"))
      (node (ref "T7") (pin "2") (pinfunction "S_2") (pintype "passive"))
    )
    (net (code "772") (name "UC_I2C_SCL_3V3") (class "Default")
      (node (ref "IC58") (pin "6") (pinfunction "I/O4_6") (pintype "passive"))
      (node (ref "R43") (pin "1") (pinfunction "1_1") (pintype "passive"))
      (node (ref "R466") (pin "1") (pinfunction "1_1") (pintype "passive"))
      (node (ref "R548") (pin "2") (pinfunction "2_2") (pintype "passive"))
      (node (ref "R558") (pin "2") (pinfunction "2_2") (pintype "passive"))
      (node (ref "R72") (pin "2") (pinfunction "2_2") (pintype "passive"))
      (node (ref "T7") (pin "3") (pinfunction "D_3") (pintype "passive"))
      (node (ref "X13") (pin "50") (pinfunction "50_50") (pintype "passive"))
    )
    (net (code "773") (name "UC_I2C_SDA_1V8") (class "Default")
      (node (ref "R266") (pin "1") (pinfunction "1_1") (pintype "passive"))
      (node (ref "R287") (pin "1") (pinfunction "1_1") (pintype "passive"))
      (node (ref "T2") (pin "2") (pinfunction "S_2") (pintype "passive"))
    )
    (net (code "774") (name "UC_I2C_SDA_3V3") (class "Default")
      (node (ref "IC58") (pin "4") (pinfunction "I/O3_4") (pintype "passive"))
      (node (ref "R45") (pin "1") (pinfunction "1_1") (pintype "passive"))
      (node (ref "R467") (pin "1") (pinfunction "1_1") (pintype "passive"))
      (node (ref "R545") (pin "2") (pinfunction "2_2") (pintype "passive"))
      (node (ref "R557") (pin "2") (pinfunction "2_2") (pintype "passive"))
      (node (ref "R64") (pin "1") (pinfunction "1_1") (pintype "passive"))
      (node (ref "T2") (pin "3") (pinfunction "D_3") (pintype "passive"))
      (node (ref "X13") (pin "48") (pinfunction "48_48") (pintype "passive"))
    )
    (net (code "775") (name "UC_JETSON_LVL_SHIFTER_EN_3V3") (class "Default")
      (node (ref "IC20") (pin "38") (pinfunction "PE7_38") (pintype "bidirectional"))
      (node (ref "R104") (pin "1") (pinfunction "1_1") (pintype "passive"))
    )
    (net (code "776") (name "UC_JETSON_POWER_EN_3V3") (class "Default")
      (node (ref "R271") (pin "1") (pinfunction "1_1") (pintype "passive"))
      (node (ref "R99") (pin "1") (pinfunction "1_1") (pintype "passive"))
    )
    (net (code "777") (name "UC_LENS_EN_3V3") (class "Default")
      (node (ref "IC46") (pin "6") (pinfunction "EN_6") (pintype "input"))
      (node (ref "IC7") (pin "6") (pinfunction "EN_6") (pintype "input"))
      (node (ref "R218") (pin "1") (pinfunction "1_1") (pintype "passive"))
    )
    (net (code "778") (name "UC_LENS_HS1_3V3") (class "Default")
      (node (ref "IC7") (pin "7") (pinfunction "HI_7") (pintype "input"))
      (node (ref "R478") (pin "1") (pinfunction "1_1") (pintype "passive"))
    )
    (net (code "779") (name "UC_LENS_HS2_3V3") (class "Default")
      (node (ref "IC46") (pin "7") (pinfunction "HI_7") (pintype "input"))
      (node (ref "R476") (pin "1") (pinfunction "1_1") (pintype "passive"))
    )
    (net (code "780") (name "UC_LENS_LS1_3V3") (class "Default")
      (node (ref "IC7") (pin "8") (pinfunction "LI_8") (pintype "input"))
      (node (ref "R477") (pin "1") (pinfunction "1_1") (pintype "passive"))
    )
    (net (code "781") (name "UC_LENS_LS2_3V3") (class "Default")
      (node (ref "IC46") (pin "8") (pinfunction "LI_8") (pintype "input"))
      (node (ref "R475") (pin "1") (pinfunction "1_1") (pintype "passive"))
    )
    (net (code "782") (name "UC_NRST_3V3") (class "Default")
      (node (ref "C187") (pin "1") (pinfunction "1_1") (pintype "passive"))
      (node (ref "D11") (pin "C") (pinfunction "C_C") (pintype "passive"))
      (node (ref "IC20") (pin "14") (pinfunction "~{NRST}/PG10/MCO_14") (pintype "bidirectional"))
      (node (ref "R365") (pin "2") (pinfunction "2_2") (pintype "passive"))
      (node (ref "R67") (pin "1") (pinfunction "1_1") (pintype "passive"))
      (node (ref "TP71") (pin "P$1") (pinfunction "TP_P$1") (pintype "input"))
    )
    (net (code "783") (name "UC_OPAMP_SUP_EN_3V3") (class "Default")
      (node (ref "R236") (pin "1") (pinfunction "1_1") (pintype "passive"))
      (node (ref "R237") (pin "1") (pinfunction "1_1") (pintype "passive"))
      (node (ref "T24") (pin "1") (pinfunction "G_1") (pintype "input"))
    )
    (net (code "784") (name "UC_PVCC_EN_3V3") (class "Default")
      (node (ref "R20") (pin "1") (pinfunction "1_1") (pintype "passive"))
      (node (ref "R383") (pin "2") (pinfunction "2_2") (pintype "passive"))
      (node (ref "T36") (pin "1") (pinfunction "G_1") (pintype "passive"))
    )
    (net (code "785") (name "UC_PWM_FAN_AUX_3V3") (class "Default")
      (node (ref "R533") (pin "2") (pinfunction "2_2") (pintype "passive"))
      (node (ref "R541") (pin "1") (pinfunction "1_1") (pintype "passive"))
      (node (ref "T65") (pin "1") (pinfunction "G_1") (pintype "passive"))
    )
    (net (code "786") (name "UC_PWM_FAN_MAIN_3V3") (class "Default")
      (node (ref "R110") (pin "2") (pinfunction "2_2") (pintype "passive"))
      (node (ref "R150") (pin "1") (pinfunction "1_1") (pintype "passive"))
      (node (ref "T8") (pin "1") (pinfunction "G_1") (pintype "passive"))
    )
    (net (code "787") (name "UC_RFID_GPO_3V3") (class "Default")
      (node (ref "IC20") (pin "80") (pinfunction "PC11_80") (pintype "bidirectional"))
      (node (ref "R532") (pin "1") (pinfunction "1_1") (pintype "passive"))
    )
    (net (code "788") (name "UC_RGB_DIST_3V3") (class "Default")
      (node (ref "IC17") (pin "6") (pinfunction "B2_6") (pintype "bidirectional"))
      (node (ref "IC75") (pin "2") (pinfunction "A_2") (pintype "input"))
      (node (ref "R264") (pin "2") (pinfunction "2_2") (pintype "passive"))
      (node (ref "R448") (pin "1") (pinfunction "1_1") (pintype "passive"))
    )
    (net (code "789") (name "UC_RGB_FU_3V3") (class "Default")
      (node (ref "IC17") (pin "7") (pinfunction "B1_7") (pintype "bidirectional"))
      (node (ref "IC34") (pin "2") (pinfunction "A_2") (pintype "input"))
      (node (ref "R234") (pin "1") (pinfunction "1_1") (pintype "passive"))
      (node (ref "R263") (pin "2") (pinfunction "2_2") (pintype "passive"))
    )
    (net (code "790") (name "UC_SPI_STEPPER_CSN_3V3") (class "Default")
      (node (ref "IC20") (pin "25") (pinfunction "PA3_25") (pintype "bidirectional"))
      (node (ref "R134") (pin "1") (pinfunction "1_1") (pintype "passive"))
    )
    (net (code "791") (name "UC_SPI_STEPPER_MISO_3V3") (class "Default")
      (node (ref "IC20") (pin "28") (pinfunction "PA6_28") (pintype "bidirectional"))
      (node (ref "R209") (pin "1") (pinfunction "1_1") (pintype "passive"))
      (node (ref "R215") (pin "2") (pinfunction "2_2") (pintype "passive"))
    )
    (net (code "792") (name "UC_SPI_STEPPER_MOSI_3V3") (class "Default")
      (node (ref "IC20") (pin "29") (pinfunction "PA7_29") (pintype "bidirectional"))
      (node (ref "R210") (pin "1") (pinfunction "1_1") (pintype "passive"))
    )
    (net (code "793") (name "UC_SPI_STEPPER_SCK_3V3") (class "Default")
      (node (ref "IC20") (pin "27") (pinfunction "PA5_27") (pintype "bidirectional"))
      (node (ref "R138") (pin "1") (pinfunction "1_1") (pintype "passive"))
    )
    (net (code "794") (name "UC_SWCLK_3V3") (class "Default")
      (node (ref "IC20") (pin "77") (pinfunction "PA14_77") (pintype "bidirectional"))
      (node (ref "R68") (pin "1") (pinfunction "1_1") (pintype "passive"))
    )
    (net (code "795") (name "UC_SWDIO_3V3") (class "Default")
      (node (ref "IC20") (pin "76") (pinfunction "PA13_76") (pintype "bidirectional"))
      (node (ref "R69") (pin "1") (pinfunction "1_1") (pintype "passive"))
    )
    (net (code "796") (name "UC_SWO_3V3") (class "Default")
      (node (ref "R288") (pin "1") (pinfunction "1_1") (pintype "passive"))
      (node (ref "R96") (pin "1") (pinfunction "1_1") (pintype "passive"))
    )
    (net (code "797") (name "UC_USB0_VBUS_DET_3V3") (class "Default")
      (node (ref "IC20") (pin "86") (pinfunction "PD4_86") (pintype "bidirectional"))
      (node (ref "R301") (pin "2") (pinfunction "2_2") (pintype "passive"))
    )
    (net (code "798") (name "UC_VBAT_EN_3V3") (class "Default")
      (node (ref "C82") (pin "1") (pinfunction "1_1") (pintype "passive"))
      (node (ref "R219") (pin "2") (pinfunction "2_2") (pintype "passive"))
      (node (ref "R221") (pin "1") (pinfunction "1_1") (pintype "passive"))
      (node (ref "T22") (pin "1") (pinfunction "G_1") (pintype "passive"))
    )
    (net (code "799") (name "USB2_D_N") (class "Default")
      (node (ref "MOD1") (pin "121") (pinfunction "USB2_D_N_121") (pintype "bidirectional"))
      (node (ref "R83") (pin "1") (pinfunction "1_1") (pintype "passive"))
    )
    (net (code "800") (name "USB2_D_P") (class "Default")
      (node (ref "MOD1") (pin "123") (pinfunction "USB2_D_P_123") (pintype "bidirectional"))
      (node (ref "R160") (pin "1") (pinfunction "1_1") (pintype "passive"))
    )
    (net (code "801") (name "USB2512B_VDD") (class "Default")
      (node (ref "C157") (pin "2") (pinfunction "2_2") (pintype "passive"))
      (node (ref "C158") (pin "2") (pinfunction "2_2") (pintype "passive"))
      (node (ref "C159") (pin "2") (pinfunction "2_2") (pintype "passive"))
      (node (ref "C160") (pin "2") (pinfunction "2_2") (pintype "passive"))
      (node (ref "C161") (pin "2") (pinfunction "2_2") (pintype "passive"))
      (node (ref "C164") (pin "2") (pinfunction "2_2") (pintype "passive"))
      (node (ref "C165") (pin "1") (pinfunction "1_1") (pintype "passive"))
      (node (ref "IC19") (pin "10") (pinfunction "VDDA33_10") (pintype "input"))
      (node (ref "IC19") (pin "15") (pinfunction "VDD33_15") (pintype "input"))
      (node (ref "IC19") (pin "23") (pinfunction "VDD33_23") (pintype "input"))
      (node (ref "IC19") (pin "27") (pinfunction "VBUS_DET_27") (pintype "input"))
      (node (ref "IC19") (pin "29") (pinfunction "VDDA33_29") (pintype "input"))
      (node (ref "IC19") (pin "36") (pinfunction "VDDA33_36") (pintype "input"))
      (node (ref "IC19") (pin "5") (pinfunction "VDDA33_5") (pintype "input"))
      (node (ref "R165") (pin "1") (pinfunction "1_1") (pintype "passive"))
    )
    (net (code "802") (name "VCC") (class "Default")
      (node (ref "C10") (pin "1") (pinfunction "1_1") (pintype "passive"))
      (node (ref "D1") (pin "A") (pinfunction "A_A") (pintype "passive"))
      (node (ref "IC5") (pin "16") (pinfunction "VCC_16") (pintype "input"))
      (node (ref "R132") (pin "1") (pinfunction "1_1") (pintype "passive"))
    )
    (net (code "803") (name "VSIM") (class "Default")
      (node (ref "C146") (pin "1") (pinfunction "1_1") (pintype "passive"))
      (node (ref "X11") (pin "2") (pinfunction "2_2") (pintype "passive"))
      (node (ref "X26") (pin "C1") (pinfunction "VCC_C1") (pintype "input"))
      (node (ref "X32") (pin "36") (pinfunction "USIM1_PWR_36") (pintype "output"))
    )
    (net (code "804") (name "unconnected-(D6-A1-Pad1)") (class "Default")
      (node (ref "D6") (pin "1") (pinfunction "A1_1") (pintype "passive"))
    )
    (net (code "805") (name "unconnected-(D7-A1-Pad1)") (class "Default")
      (node (ref "D7") (pin "1") (pinfunction "A1_1") (pintype "passive"))
    )
    (net (code "806") (name "unconnected-(D24-A1-Pad1)") (class "Default")
      (node (ref "D24") (pin "1") (pinfunction "A1_1") (pintype "passive"))
    )
    (net (code "807") (name "unconnected-(D30-A2-Pad2)") (class "Default")
      (node (ref "D30") (pin "2") (pinfunction "A2_2") (pintype "passive"))
    )
    (net (code "808") (name "unconnected-(IC3-RESV-Pad2)") (class "Default")
      (node (ref "IC3") (pin "2") (pinfunction "RESV_2") (pintype "bidirectional"))
    )
    (net (code "809") (name "unconnected-(IC3-RESV-Pad3)") (class "Default")
      (node (ref "IC3") (pin "3") (pinfunction "RESV_3") (pintype "bidirectional"))
    )
    (net (code "810") (name "unconnected-(IC3-RESV-Pad10)") (class "Default")
      (node (ref "IC3") (pin "10") (pinfunction "RESV_10") (pintype "bidirectional"))
    )
    (net (code "811") (name "unconnected-(IC9-NC-Pad1)") (class "Default")
      (node (ref "IC9") (pin "1") (pinfunction "NC_1") (pintype "passive"))
    )
    (net (code "812") (name "unconnected-(IC9-SUB-Pad2)") (class "Default")
      (node (ref "IC9") (pin "2") (pinfunction "SUB_2") (pintype "output"))
    )
    (net (code "813") (name "unconnected-(IC11-B1-Pad21)") (class "Default")
      (node (ref "IC11") (pin "21") (pinfunction "B1_21") (pintype "bidirectional"))
    )
    (net (code "814") (name "unconnected-(IC11-B2-Pad20)") (class "Default")
      (node (ref "IC11") (pin "20") (pinfunction "B2_20") (pintype "bidirectional"))
    )
    (net (code "815") (name "unconnected-(IC14-I{slash}O1-Pad1)") (class "Default")
      (node (ref "IC14") (pin "1") (pinfunction "I/O1_1") (pintype "passive"))
    )
    (net (code "816") (name "unconnected-(IC14-I{slash}O4-Pad6)") (class "Default")
      (node (ref "IC14") (pin "6") (pinfunction "I/O4_6") (pintype "passive"))
    )
    (net (code "817") (name "unconnected-(IC15-NC-Pad1)") (class "Default")
      (node (ref "IC15") (pin "1") (pinfunction "NC_1") (pintype "passive"))
    )
    (net (code "818") (name "unconnected-(IC15-SUB-Pad2)") (class "Default")
      (node (ref "IC15") (pin "2") (pinfunction "SUB_2") (pintype "output"))
    )
    (net (code "819") (name "unconnected-(IC16-I{slash}O1-Pad1)") (class "Default")
      (node (ref "IC16") (pin "1") (pinfunction "I/O1_1") (pintype "passive"))
    )
    (net (code "820") (name "unconnected-(IC16-I{slash}O2-Pad3)") (class "Default")
      (node (ref "IC16") (pin "3") (pinfunction "I/O2_3") (pintype "passive"))
    )
    (net (code "821") (name "unconnected-(IC19-OCS_N1-Pad13)") (class "Default")
      (node (ref "IC19") (pin "13") (pinfunction "OCS_N1_13") (pintype "input"))
    )
    (net (code "822") (name "unconnected-(IC19-OCS_N2-Pad17)") (class "Default")
      (node (ref "IC19") (pin "17") (pinfunction "OCS_N2_17") (pintype "input"))
    )
    (net (code "823") (name "unconnected-(IC19-OCS_N3-Pad19)") (class "Default")
      (node (ref "IC19") (pin "19") (pinfunction "OCS_N3_19") (pintype "input"))
    )
    (net (code "824") (name "unconnected-(IC19-OCS_N4-Pad21)") (class "Default")
      (node (ref "IC19") (pin "21") (pinfunction "OCS_N4_21") (pintype "input"))
    )
    (net (code "825") (name "unconnected-(IC19-PRTPWR1{slash}BC_EN1-Pad12)") (class "Default")
      (node (ref "IC19") (pin "12") (pinfunction "PRTPWR1/BC_EN1_12") (pintype "bidirectional"))
    )
    (net (code "826") (name "unconnected-(IC19-PRTPWR2{slash}BC_EN2-Pad16)") (class "Default")
      (node (ref "IC19") (pin "16") (pinfunction "PRTPWR2/BC_EN2_16") (pintype "bidirectional"))
    )
    (net (code "827") (name "unconnected-(IC19-PRTPWR3{slash}BC_EN3-Pad18)") (class "Default")
      (node (ref "IC19") (pin "18") (pinfunction "PRTPWR3/BC_EN3_18") (pintype "bidirectional"))
    )
    (net (code "828") (name "unconnected-(IC19-PRTPWR4{slash}BC_EN4-Pad20)") (class "Default")
      (node (ref "IC19") (pin "20") (pinfunction "PRTPWR4/BC_EN4_20") (pintype "bidirectional"))
    )
    (net (code "829") (name "unconnected-(IC21-NC-Pad1)") (class "Default")
      (node (ref "IC21") (pin "1") (pinfunction "NC_1") (pintype "passive"))
    )
    (net (code "830") (name "unconnected-(IC21-SUB-Pad2)") (class "Default")
      (node (ref "IC21") (pin "2") (pinfunction "SUB_2") (pintype "output"))
    )
    (net (code "831") (name "unconnected-(IC22-DNC-Pad15)") (class "Default")
      (node (ref "IC22") (pin "15") (pinfunction "DNC_15") (pintype "output"))
    )
    (net (code "832") (name "unconnected-(IC22-EXTINT-Pad5)") (class "Default")
      (node (ref "IC22") (pin "5") (pinfunction "EXTINT_5") (pintype "input"))
    )
    (net (code "833") (name "unconnected-(IC22-LNA_EN-Pad13)") (class "Default")
      (node (ref "IC22") (pin "13") (pinfunction "LNA_EN_13") (pintype "output"))
    )
    (net (code "834") (name "unconnected-(IC22-SAFEBOOT_N-Pad18)") (class "Default")
      (node (ref "IC22") (pin "18") (pinfunction "SAFEBOOT_N_18") (pintype "input"))
    )
    (net (code "835") (name "unconnected-(IC22-SCL-Pad17)") (class "Default")
      (node (ref "IC22") (pin "17") (pinfunction "SCL_17") (pintype "bidirectional"))
    )
    (net (code "836") (name "unconnected-(IC22-SDA-Pad16)") (class "Default")
      (node (ref "IC22") (pin "16") (pinfunction "SDA_16") (pintype "bidirectional"))
    )
    (net (code "837") (name "unconnected-(IC22-TIMEPULSE-Pad4)") (class "Default")
      (node (ref "IC22") (pin "4") (pinfunction "TIMEPULSE_4") (pintype "output"))
    )
    (net (code "838") (name "unconnected-(IC27-NC-Pad1)") (class "Default")
      (node (ref "IC27") (pin "1") (pinfunction "NC_1") (pintype "passive"))
    )
    (net (code "839") (name "unconnected-(IC27-SUB-Pad2)") (class "Default")
      (node (ref "IC27") (pin "2") (pinfunction "SUB_2") (pintype "output"))
    )
    (net (code "840") (name "unconnected-(IC31-SYNCOUT-Pad1)") (class "Default")
      (node (ref "IC31") (pin "1") (pinfunction "SYNCOUT_1") (pintype "output"))
    )
    (net (code "841") (name "unconnected-(IC52-I{slash}O2-Pad3)") (class "Default")
      (node (ref "IC52") (pin "3") (pinfunction "I/O2_3") (pintype "passive"))
    )
    (net (code "842") (name "unconnected-(IC52-I{slash}O3-Pad4)") (class "Default")
      (node (ref "IC52") (pin "4") (pinfunction "I/O3_4") (pintype "passive"))
    )
    (net (code "843") (name "unconnected-(IC52-I{slash}O4-Pad6)") (class "Default")
      (node (ref "IC52") (pin "6") (pinfunction "I/O4_6") (pintype "passive"))
    )
    (net (code "844") (name "unconnected-(IC54-S2A-Pad3)") (class "Default")
      (node (ref "IC54") (pin "3") (pinfunction "S2A_3") (pintype "passive"))
    )
    (net (code "845") (name "unconnected-(IC54-S3A-Pad4)") (class "Default")
      (node (ref "IC54") (pin "4") (pinfunction "S3A_4") (pintype "passive"))
    )
    (net (code "846") (name "unconnected-(IC54-S3B-Pad9)") (class "Default")
      (node (ref "IC54") (pin "9") (pinfunction "S3B_9") (pintype "passive"))
    )
    (net (code "847") (name "unconnected-(IC54-S4A-Pad5)") (class "Default")
      (node (ref "IC54") (pin "5") (pinfunction "S4A_5") (pintype "passive"))
    )
    (net (code "848") (name "unconnected-(IC54-S4B-Pad8)") (class "Default")
      (node (ref "IC54") (pin "8") (pinfunction "S4B_8") (pintype "passive"))
    )
    (net (code "849") (name "unconnected-(IC55-S3A-Pad4)") (class "Default")
      (node (ref "IC55") (pin "4") (pinfunction "S3A_4") (pintype "passive"))
    )
    (net (code "850") (name "unconnected-(IC55-S3B-Pad9)") (class "Default")
      (node (ref "IC55") (pin "9") (pinfunction "S3B_9") (pintype "passive"))
    )
    (net (code "851") (name "unconnected-(IC55-S4A-Pad5)") (class "Default")
      (node (ref "IC55") (pin "5") (pinfunction "S4A_5") (pintype "passive"))
    )
    (net (code "852") (name "unconnected-(IC55-S4B-Pad8)") (class "Default")
      (node (ref "IC55") (pin "8") (pinfunction "S4B_8") (pintype "passive"))
    )
    (net (code "853") (name "unconnected-(IC56-NC-Pad1)") (class "Default")
      (node (ref "IC56") (pin "1") (pinfunction "NC_1") (pintype "passive"))
    )
    (net (code "854") (name "unconnected-(IC56-SUB-Pad2)") (class "Default")
      (node (ref "IC56") (pin "2") (pinfunction "SUB_2") (pintype "output"))
    )
    (net (code "855") (name "unconnected-(IC58-I{slash}O2-Pad3)") (class "Default")
      (node (ref "IC58") (pin "3") (pinfunction "I/O2_3") (pintype "passive"))
    )
    (net (code "856") (name "unconnected-(IC76-V_EH-Pad1)") (class "Default")
      (node (ref "IC76") (pin "1") (pinfunction "V_EH_1") (pintype "output"))
    )
    (net (code "857") (name "unconnected-(IC77-ALERT-Pad3)") (class "Default")
      (node (ref "IC77") (pin "3") (pinfunction "ALERT_3") (pintype "open_collector"))
    )
    (net (code "858") (name "unconnected-(MOD1A-CSI1_CLK_N{slash}RSVD-Pad9)") (class "Default")
      (node (ref "MOD1") (pin "9") (pinfunction "CSI1_CLK_N/RSVD_9") (pintype "input"))
    )
    (net (code "859") (name "unconnected-(MOD1A-CSI1_CLK_P{slash}RSVD-Pad11)") (class "Default")
      (node (ref "MOD1") (pin "11") (pinfunction "CSI1_CLK_P/RSVD_11") (pintype "input"))
    )
    (net (code "860") (name "unconnected-(MOD1A-CSI1_D0_N-Pad3)") (class "Default")
      (node (ref "MOD1") (pin "3") (pinfunction "CSI1_D0_N_3") (pintype "input"))
    )
    (net (code "861") (name "unconnected-(MOD1A-CSI1_D0_P-Pad5)") (class "Default")
      (node (ref "MOD1") (pin "5") (pinfunction "CSI1_D0_P_5") (pintype "input"))
    )
    (net (code "862") (name "unconnected-(MOD1A-CSI1_D1_N-Pad15)") (class "Default")
      (node (ref "MOD1") (pin "15") (pinfunction "CSI1_D1_N_15") (pintype "input"))
    )
    (net (code "863") (name "unconnected-(MOD1A-CSI1_D1_P-Pad17)") (class "Default")
      (node (ref "MOD1") (pin "17") (pinfunction "CSI1_D1_P_17") (pintype "input"))
    )
    (net (code "864") (name "unconnected-(MOD1A-CSI4_D1_N-Pad58)") (class "Default")
      (node (ref "MOD1") (pin "58") (pinfunction "CSI4_D1_N_58") (pintype "input"))
    )
    (net (code "865") (name "unconnected-(MOD1A-CSI4_D1_P-Pad60)") (class "Default")
      (node (ref "MOD1") (pin "60") (pinfunction "CSI4_D1_P_60") (pintype "input"))
    )
    (net (code "866") (name "unconnected-(MOD1A-CSI4_D2_N-Pad40)") (class "Default")
      (node (ref "MOD1") (pin "40") (pinfunction "CSI4_D2_N_40") (pintype "input"))
    )
    (net (code "867") (name "unconnected-(MOD1A-CSI4_D2_P-Pad42)") (class "Default")
      (node (ref "MOD1") (pin "42") (pinfunction "CSI4_D2_P_42") (pintype "input"))
    )
    (net (code "868") (name "unconnected-(MOD1A-CSI4_D3_N-Pad64)") (class "Default")
      (node (ref "MOD1") (pin "64") (pinfunction "CSI4_D3_N_64") (pintype "input"))
    )
    (net (code "869") (name "unconnected-(MOD1A-CSI4_D3_P-Pad66)") (class "Default")
      (node (ref "MOD1") (pin "66") (pinfunction "CSI4_D3_P_66") (pintype "input"))
    )
    (net (code "870") (name "unconnected-(MOD1B-DP0_AUX_N-Pad90)") (class "Default")
      (node (ref "MOD1") (pin "90") (pinfunction "DP0_AUX_N_90") (pintype "bidirectional"))
    )
    (net (code "871") (name "unconnected-(MOD1B-DP0_AUX_P-Pad92)") (class "Default")
      (node (ref "MOD1") (pin "92") (pinfunction "DP0_AUX_P_92") (pintype "bidirectional"))
    )
    (net (code "872") (name "unconnected-(MOD1B-DP0_HPD-Pad88)") (class "Default")
      (node (ref "MOD1") (pin "88") (pinfunction "DP0_HPD_88") (pintype "input"))
    )
    (net (code "873") (name "unconnected-(MOD1B-DP0_TXD0_N-Pad39)") (class "Default")
      (node (ref "MOD1") (pin "39") (pinfunction "DP0_TXD0_N_39") (pintype "output"))
    )
    (net (code "874") (name "unconnected-(MOD1B-DP0_TXD0_P-Pad41)") (class "Default")
      (node (ref "MOD1") (pin "41") (pinfunction "DP0_TXD0_P_41") (pintype "output"))
    )
    (net (code "875") (name "unconnected-(MOD1B-DP0_TXD1_N-Pad45)") (class "Default")
      (node (ref "MOD1") (pin "45") (pinfunction "DP0_TXD1_N_45") (pintype "output"))
    )
    (net (code "876") (name "unconnected-(MOD1B-DP0_TXD1_P-Pad47)") (class "Default")
      (node (ref "MOD1") (pin "47") (pinfunction "DP0_TXD1_P_47") (pintype "output"))
    )
    (net (code "877") (name "unconnected-(MOD1B-DP0_TXD2_N-Pad51)") (class "Default")
      (node (ref "MOD1") (pin "51") (pinfunction "DP0_TXD2_N_51") (pintype "output"))
    )
    (net (code "878") (name "unconnected-(MOD1B-DP0_TXD2_P-Pad53)") (class "Default")
      (node (ref "MOD1") (pin "53") (pinfunction "DP0_TXD2_P_53") (pintype "output"))
    )
    (net (code "879") (name "unconnected-(MOD1B-DP0_TXD3_N-Pad57)") (class "Default")
      (node (ref "MOD1") (pin "57") (pinfunction "DP0_TXD3_N_57") (pintype "output"))
    )
    (net (code "880") (name "unconnected-(MOD1B-DP0_TXD3_P-Pad59)") (class "Default")
      (node (ref "MOD1") (pin "59") (pinfunction "DP0_TXD3_P_59") (pintype "output"))
    )
    (net (code "881") (name "unconnected-(MOD1B-DSI_CLK_N-Pad76)") (class "Default")
      (node (ref "MOD1") (pin "76") (pinfunction "DSI_CLK_N_76") (pintype "output"))
    )
    (net (code "882") (name "unconnected-(MOD1B-DSI_CLK_P-Pad78)") (class "Default")
      (node (ref "MOD1") (pin "78") (pinfunction "DSI_CLK_P_78") (pintype "output"))
    )
    (net (code "883") (name "unconnected-(MOD1B-DSI_D0_N-Pad70)") (class "Default")
      (node (ref "MOD1") (pin "70") (pinfunction "DSI_D0_N_70") (pintype "bidirectional"))
    )
    (net (code "884") (name "unconnected-(MOD1B-DSI_D0_P-Pad72)") (class "Default")
      (node (ref "MOD1") (pin "72") (pinfunction "DSI_D0_P_72") (pintype "bidirectional"))
    )
    (net (code "885") (name "unconnected-(MOD1B-DSI_D1_N-Pad82)") (class "Default")
      (node (ref "MOD1") (pin "82") (pinfunction "DSI_D1_N_82") (pintype "output"))
    )
    (net (code "886") (name "unconnected-(MOD1B-DSI_D1_P-Pad84)") (class "Default")
      (node (ref "MOD1") (pin "84") (pinfunction "DSI_D1_P_84") (pintype "output"))
    )
    (net (code "887") (name "unconnected-(MOD1C-GBE_LED_ACT-Pad194)") (class "Default")
      (node (ref "MOD1") (pin "194") (pinfunction "GBE_LED_ACT_194") (pintype "output"))
    )
    (net (code "888") (name "unconnected-(MOD1C-GBE_LED_LINK-Pad188)") (class "Default")
      (node (ref "MOD1") (pin "188") (pinfunction "GBE_LED_LINK_188") (pintype "output"))
    )
    (net (code "889") (name "unconnected-(MOD1C-GBE_MDI0_N-Pad184)") (class "Default")
      (node (ref "MOD1") (pin "184") (pinfunction "GBE_MDI0_N_184") (pintype "bidirectional"))
    )
    (net (code "890") (name "unconnected-(MOD1C-GBE_MDI0_P-Pad186)") (class "Default")
      (node (ref "MOD1") (pin "186") (pinfunction "GBE_MDI0_P_186") (pintype "bidirectional"))
    )
    (net (code "891") (name "unconnected-(MOD1C-GBE_MDI1_N-Pad190)") (class "Default")
      (node (ref "MOD1") (pin "190") (pinfunction "GBE_MDI1_N_190") (pintype "bidirectional"))
    )
    (net (code "892") (name "unconnected-(MOD1C-GBE_MDI1_P-Pad192)") (class "Default")
      (node (ref "MOD1") (pin "192") (pinfunction "GBE_MDI1_P_192") (pintype "bidirectional"))
    )
    (net (code "893") (name "unconnected-(MOD1C-GBE_MDI2_N-Pad196)") (class "Default")
      (node (ref "MOD1") (pin "196") (pinfunction "GBE_MDI2_N_196") (pintype "bidirectional"))
    )
    (net (code "894") (name "unconnected-(MOD1C-GBE_MDI2_P-Pad198)") (class "Default")
      (node (ref "MOD1") (pin "198") (pinfunction "GBE_MDI2_P_198") (pintype "bidirectional"))
    )
    (net (code "895") (name "unconnected-(MOD1C-GBE_MDI3_N-Pad202)") (class "Default")
      (node (ref "MOD1") (pin "202") (pinfunction "GBE_MDI3_N_202") (pintype "bidirectional"))
    )
    (net (code "896") (name "unconnected-(MOD1C-GBE_MDI3_P-Pad204)") (class "Default")
      (node (ref "MOD1") (pin "204") (pinfunction "GBE_MDI3_P_204") (pintype "bidirectional"))
    )
    (net (code "897") (name "unconnected-(MOD1C-PCIE0_RX1_N-Pad137)") (class "Default")
      (node (ref "MOD1") (pin "137") (pinfunction "PCIE0_RX1_N_137") (pintype "input"))
    )
    (net (code "898") (name "unconnected-(MOD1C-PCIE0_RX1_P-Pad139)") (class "Default")
      (node (ref "MOD1") (pin "139") (pinfunction "PCIE0_RX1_P_139") (pintype "input"))
    )
    (net (code "899") (name "unconnected-(MOD1C-PCIE0_RX2_N{slash}RSVD-Pad149)") (class "Default")
      (node (ref "MOD1") (pin "149") (pinfunction "PCIE0_RX2_N/RSVD_149") (pintype "input"))
    )
    (net (code "900") (name "unconnected-(MOD1C-PCIE0_RX2_P{slash}RSVD-Pad151)") (class "Default")
      (node (ref "MOD1") (pin "151") (pinfunction "PCIE0_RX2_P/RSVD_151") (pintype "input"))
    )
    (net (code "901") (name "unconnected-(MOD1C-PCIE0_RX3_N{slash}RSVD-Pad155)") (class "Default")
      (node (ref "MOD1") (pin "155") (pinfunction "PCIE0_RX3_N/RSVD_155") (pintype "input"))
    )
    (net (code "902") (name "unconnected-(MOD1C-PCIE0_RX3_P{slash}RSVD-Pad157)") (class "Default")
      (node (ref "MOD1") (pin "157") (pinfunction "PCIE0_RX3_P/RSVD_157") (pintype "input"))
    )
    (net (code "903") (name "unconnected-(MOD1C-PCIE0_TX1_N-Pad140)") (class "Default")
      (node (ref "MOD1") (pin "140") (pinfunction "PCIE0_TX1_N_140") (pintype "output"))
    )
    (net (code "904") (name "unconnected-(MOD1C-PCIE0_TX1_P-Pad142)") (class "Default")
      (node (ref "MOD1") (pin "142") (pinfunction "PCIE0_TX1_P_142") (pintype "output"))
    )
    (net (code "905") (name "unconnected-(MOD1C-PCIE0_TX2_N{slash}RSVD-Pad148)") (class "Default")
      (node (ref "MOD1") (pin "148") (pinfunction "PCIE0_TX2_N/RSVD_148") (pintype "output"))
    )
    (net (code "906") (name "unconnected-(MOD1C-PCIE0_TX2_P{slash}RSVD-Pad150)") (class "Default")
      (node (ref "MOD1") (pin "150") (pinfunction "PCIE0_TX2_P/RSVD_150") (pintype "output"))
    )
    (net (code "907") (name "unconnected-(MOD1C-PCIE0_TX3_N{slash}RSVD-Pad154)") (class "Default")
      (node (ref "MOD1") (pin "154") (pinfunction "PCIE0_TX3_N/RSVD_154") (pintype "output"))
    )
    (net (code "908") (name "unconnected-(MOD1C-PCIE0_TX3_P{slash}RSVD-Pad156)") (class "Default")
      (node (ref "MOD1") (pin "156") (pinfunction "PCIE0_TX3_P/RSVD_156") (pintype "output"))
    )
    (net (code "909") (name "unconnected-(MOD1C-SDMMC_CLK-Pad229)") (class "Default")
      (node (ref "MOD1") (pin "229") (pinfunction "SDMMC_CLK_229") (pintype "output"))
    )
    (net (code "910") (name "unconnected-(MOD1C-SDMMC_CMD-Pad227)") (class "Default")
      (node (ref "MOD1") (pin "227") (pinfunction "SDMMC_CMD_227") (pintype "bidirectional"))
    )
    (net (code "911") (name "unconnected-(MOD1C-SDMMC_DAT0-Pad219)") (class "Default")
      (node (ref "MOD1") (pin "219") (pinfunction "SDMMC_DAT0_219") (pintype "bidirectional"))
    )
    (net (code "912") (name "unconnected-(MOD1C-SDMMC_DAT2-Pad223)") (class "Default")
      (node (ref "MOD1") (pin "223") (pinfunction "SDMMC_DAT2_223") (pintype "bidirectional"))
    )
    (net (code "913") (name "unconnected-(MOD1C-SDMMC_DAT3-Pad225)") (class "Default")
      (node (ref "MOD1") (pin "225") (pinfunction "SDMMC_DAT3_225") (pintype "bidirectional"))
    )
    (net (code "914") (name "unconnected-(MOD1C-USBSS_RX_N-Pad161)") (class "Default")
      (node (ref "MOD1") (pin "161") (pinfunction "USBSS_RX_N_161") (pintype "input"))
    )
    (net (code "915") (name "unconnected-(MOD1C-USBSS_RX_P-Pad163)") (class "Default")
      (node (ref "MOD1") (pin "163") (pinfunction "USBSS_RX_P_163") (pintype "input"))
    )
    (net (code "916") (name "unconnected-(MOD1C-USBSS_TX_N-Pad166)") (class "Default")
      (node (ref "MOD1") (pin "166") (pinfunction "USBSS_TX_N_166") (pintype "output"))
    )
    (net (code "917") (name "unconnected-(MOD1C-USBSS_TX_P-Pad168)") (class "Default")
      (node (ref "MOD1") (pin "168") (pinfunction "USBSS_TX_P_168") (pintype "output"))
    )
    (net (code "918") (name "unconnected-(MOD1D-GPIO01{slash}CAM_MCLK2-Pad118)") (class "Default")
      (node (ref "MOD1") (pin "118") (pinfunction "GPIO01/CAM_MCLK2_118") (pintype "bidirectional"))
    )
    (net (code "919") (name "unconnected-(MOD1D-GPIO07{slash}PWM-Pad206)") (class "Default")
      (node (ref "MOD1") (pin "206") (pinfunction "GPIO07/PWM_206") (pintype "bidirectional"))
    )
    (net (code "920") (name "unconnected-(MOD1D-GPIO09{slash}AUD_MCLK-Pad211)") (class "Default")
      (node (ref "MOD1") (pin "211") (pinfunction "GPIO09/AUD_MCLK_211") (pintype "output"))
    )
    (net (code "921") (name "unconnected-(MOD1D-GPIO12{slash}I2S3_DOUT-Pad218)") (class "Default")
      (node (ref "MOD1") (pin "218") (pinfunction "GPIO12/I2S3_DOUT_218") (pintype "bidirectional"))
    )
    (net (code "922") (name "unconnected-(MOD1D-GPIO13{slash}PWM-Pad228)") (class "Default")
      (node (ref "MOD1") (pin "228") (pinfunction "GPIO13/PWM_228") (pintype "bidirectional"))
    )
    (net (code "923") (name "unconnected-(MOD1D-I2C2_SCL-Pad232)") (class "Default")
      (node (ref "MOD1") (pin "232") (pinfunction "I2C2_SCL_232") (pintype "bidirectional"))
    )
    (net (code "924") (name "unconnected-(MOD1D-I2C2_SDA-Pad234)") (class "Default")
      (node (ref "MOD1") (pin "234") (pinfunction "I2C2_SDA_234") (pintype "bidirectional"))
    )
    (net (code "925") (name "unconnected-(MOD1D-I2S1_DIN-Pad222)") (class "Default")
      (node (ref "MOD1") (pin "222") (pinfunction "I2S1_DIN_222") (pintype "input"))
    )
    (net (code "926") (name "unconnected-(MOD1D-I2S1_DOUT-Pad220)") (class "Default")
      (node (ref "MOD1") (pin "220") (pinfunction "I2S1_DOUT_220") (pintype "output"))
    )
    (net (code "927") (name "unconnected-(MOD1D-I2S1_FS-Pad224)") (class "Default")
      (node (ref "MOD1") (pin "224") (pinfunction "I2S1_FS_224") (pintype "bidirectional"))
    )
    (net (code "928") (name "unconnected-(MOD1D-I2S1_SCLK-Pad226)") (class "Default")
      (node (ref "MOD1") (pin "226") (pinfunction "I2S1_SCLK_226") (pintype "bidirectional"))
    )
    (net (code "929") (name "unconnected-(MOD1D-SPI0_MISO-Pad93)") (class "Default")
      (node (ref "MOD1") (pin "93") (pinfunction "SPI0_MISO_93") (pintype "bidirectional"))
    )
    (net (code "930") (name "unconnected-(MOD1D-SPI0_MOSI-Pad89)") (class "Default")
      (node (ref "MOD1") (pin "89") (pinfunction "SPI0_MOSI_89") (pintype "bidirectional"))
    )
    (net (code "931") (name "unconnected-(MOD1D-SPI0_SCK-Pad91)") (class "Default")
      (node (ref "MOD1") (pin "91") (pinfunction "SPI0_SCK_91") (pintype "bidirectional"))
    )
    (net (code "932") (name "unconnected-(MOD1D-SPI0_~{CS0}-Pad95)") (class "Default")
      (node (ref "MOD1") (pin "95") (pinfunction "SPI0_~{CS0}_95") (pintype "bidirectional"))
    )
    (net (code "933") (name "unconnected-(MOD1D-SPI0_~{CS1}-Pad97)") (class "Default")
      (node (ref "MOD1") (pin "97") (pinfunction "SPI0_~{CS1}_97") (pintype "bidirectional"))
    )
    (net (code "934") (name "unconnected-(MOD1D-SPI1_MISO-Pad108)") (class "Default")
      (node (ref "MOD1") (pin "108") (pinfunction "SPI1_MISO_108") (pintype "bidirectional"))
    )
    (net (code "935") (name "unconnected-(MOD1D-SPI1_MOSI-Pad104)") (class "Default")
      (node (ref "MOD1") (pin "104") (pinfunction "SPI1_MOSI_104") (pintype "bidirectional"))
    )
    (net (code "936") (name "unconnected-(MOD1D-SPI1_SCK-Pad106)") (class "Default")
      (node (ref "MOD1") (pin "106") (pinfunction "SPI1_SCK_106") (pintype "bidirectional"))
    )
    (net (code "937") (name "unconnected-(MOD1D-SPI1_~{CS0}-Pad110)") (class "Default")
      (node (ref "MOD1") (pin "110") (pinfunction "SPI1_~{CS0}_110") (pintype "bidirectional"))
    )
    (net (code "938") (name "unconnected-(MOD1D-SPI1_~{CS1}{slash}I2S3_DIN-Pad112)") (class "Default")
      (node (ref "MOD1") (pin "112") (pinfunction "SPI1_~{CS1}/I2S3_DIN_112") (pintype "bidirectional"))
    )
    (net (code "939") (name "unconnected-(MOD1D-UART0_~{CTS}-Pad105)") (class "Default")
      (node (ref "MOD1") (pin "105") (pinfunction "UART0_~{CTS}_105") (pintype "input"))
    )
    (net (code "940") (name "unconnected-(MOD1D-UART0_~{RTS}-Pad103)") (class "Default")
      (node (ref "MOD1") (pin "103") (pinfunction "UART0_~{RTS}_103") (pintype "output"))
    )
    (net (code "941") (name "unconnected-(MOD1D-UART1_~{CTS}-Pad209)") (class "Default")
      (node (ref "MOD1") (pin "209") (pinfunction "UART1_~{CTS}_209") (pintype "input"))
    )
    (net (code "942") (name "unconnected-(MOD1D-UART1_~{RTS}-Pad207)") (class "Default")
      (node (ref "MOD1") (pin "207") (pinfunction "UART1_~{RTS}_207") (pintype "output"))
    )
    (net (code "943") (name "unconnected-(X4-Pad21)") (class "Default")
      (node (ref "X4") (pin "21") (pinfunction "21_21") (pintype "passive"))
    )
    (net (code "944") (name "unconnected-(X7-UTILITY{slash}HEAC+-Pad14)") (class "Default")
      (node (ref "X7") (pin "14") (pinfunction "UTILITY/HEAC+_14") (pintype "bidirectional"))
    )
    (net (code "945") (name "unconnected-(X15-ID-Pad4)") (class "Default")
      (node (ref "X15") (pin "4") (pinfunction "ID_4") (pintype "output"))
    )
    (net (code "946") (name "unconnected-(X18-COEX1-Pad48)") (class "Default")
      (node (ref "X18") (pin "48") (pinfunction "COEX1_48") (pintype "bidirectional"))
    )
    (net (code "947") (name "unconnected-(X18-COEX2-Pad46)") (class "Default")
      (node (ref "X18") (pin "46") (pinfunction "COEX2_46") (pintype "bidirectional"))
    )
    (net (code "948") (name "unconnected-(X18-COEX3-Pad44)") (class "Default")
      (node (ref "X18") (pin "44") (pinfunction "COEX3_44") (pintype "bidirectional"))
    )
    (net (code "949") (name "unconnected-(X18-I2C_CLK-Pad60)") (class "Default")
      (node (ref "X18") (pin "60") (pinfunction "I2C_CLK_60") (pintype "input"))
    )
    (net (code "950") (name "unconnected-(X18-I2C_DATA-Pad58)") (class "Default")
      (node (ref "X18") (pin "58") (pinfunction "I2C_DATA_58") (pintype "bidirectional"))
    )
    (net (code "951") (name "unconnected-(X18-PCM_CLK{slash}I2SSCK-Pad8)") (class "Default")
      (node (ref "X18") (pin "8") (pinfunction "PCM_CLK/I2SSCK_8") (pintype "bidirectional"))
    )
    (net (code "952") (name "unconnected-(X18-PCM_IN{slash}I2SSD_IN-Pad12)") (class "Default")
      (node (ref "X18") (pin "12") (pinfunction "PCM_IN/I2SSD_IN_12") (pintype "output"))
    )
    (net (code "953") (name "unconnected-(X18-PCM_OUT{slash}I2SSD_OUT-Pad14)") (class "Default")
      (node (ref "X18") (pin "14") (pinfunction "PCM_OUT/I2SSD_OUT_14") (pintype "input"))
    )
    (net (code "954") (name "unconnected-(X18-PCM_SYNC{slash}I2SWS-Pad10)") (class "Default")
      (node (ref "X18") (pin "10") (pinfunction "PCM_SYNC/I2SWS_10") (pintype "bidirectional"))
    )
    (net (code "955") (name "unconnected-(X18-RESERVED-Pad64)") (class "Default")
      (node (ref "X18") (pin "64") (pinfunction "RESERVED_64") (pintype "output"))
    )
    (net (code "956") (name "unconnected-(X18-RESERVED{slash}PERN1-Pad67)") (class "Default")
      (node (ref "X18") (pin "67") (pinfunction "RESERVED/PERN1_67") (pintype "bidirectional"))
    )
    (net (code "957") (name "unconnected-(X18-RESERVED{slash}PERP1-Pad65)") (class "Default")
      (node (ref "X18") (pin "65") (pinfunction "RESERVED/PERP1_65") (pintype "bidirectional"))
    )
    (net (code "958") (name "unconnected-(X18-RESERVED{slash}PETN1-Pad61)") (class "Default")
      (node (ref "X18") (pin "61") (pinfunction "RESERVED/PETN1_61") (pintype "bidirectional"))
    )
    (net (code "959") (name "unconnected-(X18-RESERVED{slash}PETP1-Pad59)") (class "Default")
      (node (ref "X18") (pin "59") (pinfunction "RESERVED/PETP1_59") (pintype "bidirectional"))
    )
    (net (code "960") (name "unconnected-(X18-RESERVED{slash}REFCLKN1-Pad73)") (class "Default")
      (node (ref "X18") (pin "73") (pinfunction "RESERVED/REFCLKN1_73") (pintype "bidirectional"))
    )
    (net (code "961") (name "unconnected-(X18-RESERVED{slash}REFCLKP1-Pad71)") (class "Default")
      (node (ref "X18") (pin "71") (pinfunction "RESERVED/REFCLKP1_71") (pintype "bidirectional"))
    )
    (net (code "962") (name "unconnected-(X18-SDIO_CLK-Pad9)") (class "Default")
      (node (ref "X18") (pin "9") (pinfunction "SDIO_CLK_9") (pintype "input"))
    )
    (net (code "963") (name "unconnected-(X18-SDIO_CMD-Pad11)") (class "Default")
      (node (ref "X18") (pin "11") (pinfunction "SDIO_CMD_11") (pintype "bidirectional"))
    )
    (net (code "964") (name "unconnected-(X18-SDIO_DATA0-Pad13)") (class "Default")
      (node (ref "X18") (pin "13") (pinfunction "SDIO_DATA0_13") (pintype "bidirectional"))
    )
    (net (code "965") (name "unconnected-(X18-SDIO_DATA1-Pad15)") (class "Default")
      (node (ref "X18") (pin "15") (pinfunction "SDIO_DATA1_15") (pintype "bidirectional"))
    )
    (net (code "966") (name "unconnected-(X18-SDIO_DATA2-Pad17)") (class "Default")
      (node (ref "X18") (pin "17") (pinfunction "SDIO_DATA2_17") (pintype "bidirectional"))
    )
    (net (code "967") (name "unconnected-(X18-SDIO_DATA3-Pad19)") (class "Default")
      (node (ref "X18") (pin "19") (pinfunction "SDIO_DATA3_19") (pintype "bidirectional"))
    )
    (net (code "968") (name "unconnected-(X18-SDIO_RESET#-Pad23)") (class "Default")
      (node (ref "X18") (pin "23") (pinfunction "SDIO_RESET#_23") (pintype "input"))
    )
    (net (code "969") (name "unconnected-(X18-SDIO_WAKE#-Pad21)") (class "Default")
      (node (ref "X18") (pin "21") (pinfunction "SDIO_WAKE#_21") (pintype "output"))
    )
    (net (code "970") (name "unconnected-(X18-UART_CTS-Pad34)") (class "Default")
      (node (ref "X18") (pin "34") (pinfunction "UART_CTS_34") (pintype "output"))
    )
    (net (code "971") (name "unconnected-(X18-UART_RTS-Pad36)") (class "Default")
      (node (ref "X18") (pin "36") (pinfunction "UART_RTS_36") (pintype "input"))
    )
    (net (code "972") (name "unconnected-(X18-UART_RXD-Pad22)") (class "Default")
      (node (ref "X18") (pin "22") (pinfunction "UART_RXD_22") (pintype "output"))
    )
    (net (code "973") (name "unconnected-(X18-UART_TXD-Pad32)") (class "Default")
      (node (ref "X18") (pin "32") (pinfunction "UART_TXD_32") (pintype "input"))
    )
    (net (code "974") (name "unconnected-(X18-UIM_POWER_SNK{slash}CLKREQ1#-Pad68)") (class "Default")
      (node (ref "X18") (pin "68") (pinfunction "UIM_POWER_SNK/CLKREQ1#_68") (pintype "bidirectional"))
    )
    (net (code "975") (name "unconnected-(X18-UIM_POWER_SRC{slash}GPIO1{slash}PEWAKE1#-Pad70)") (class "Default")
      (node (ref "X18") (pin "70") (pinfunction "UIM_POWER_SRC/GPIO1/PEWAKE1#_70") (pintype "bidirectional"))
    )
    (net (code "976") (name "unconnected-(X18-UIM_SWP{slash}PERST1#-Pad66)") (class "Default")
      (node (ref "X18") (pin "66") (pinfunction "UIM_SWP/PERST1#_66") (pintype "bidirectional"))
    )
    (net (code "977") (name "unconnected-(X18-VENDOR_DEFINED-Pad38)") (class "Default")
      (node (ref "X18") (pin "38") (pinfunction "VENDOR_DEFINED_38") (pintype "bidirectional"))
    )
    (net (code "978") (name "unconnected-(X18-VENDOR_DEFINED-Pad40)") (class "Default")
      (node (ref "X18") (pin "40") (pinfunction "VENDOR_DEFINED_40") (pintype "bidirectional"))
    )
    (net (code "979") (name "unconnected-(X18-VENDOR_DEFINED-Pad42)") (class "Default")
      (node (ref "X18") (pin "42") (pinfunction "VENDOR_DEFINED_42") (pintype "bidirectional"))
    )
    (net (code "980") (name "unconnected-(X20-Pad3)") (class "Default")
      (node (ref "X20") (pin "3") (pinfunction "3_3") (pintype "passive"))
    )
    (net (code "981") (name "unconnected-(X25-Pad8)") (class "Default")
      (node (ref "X25") (pin "8") (pinfunction "8_8") (pintype "passive"))
    )
    (net (code "982") (name "unconnected-(X25-Pad9)") (class "Default")
      (node (ref "X25") (pin "9") (pinfunction "9_9") (pintype "passive"))
    )
    (net (code "983") (name "unconnected-(X25-Pad11)") (class "Default")
      (node (ref "X25") (pin "11") (pinfunction "11_11") (pintype "passive"))
    )
    (net (code "984") (name "unconnected-(X25-Pad12)") (class "Default")
      (node (ref "X25") (pin "12") (pinfunction "12_12") (pintype "passive"))
    )
    (net (code "985") (name "unconnected-(X26-VPP-PadC6)") (class "Default")
      (node (ref "X26") (pin "C6") (pinfunction "VPP_C6") (pintype "input"))
    )
    (net (code "986") (name "unconnected-(X32-CLKREQ#{slash}UART_DTR-Pad52)") (class "Default")
      (node (ref "X32") (pin "52") (pinfunction "CLKREQ#/UART_DTR_52") (pintype "bidirectional"))
    )
    (net (code "987") (name "unconnected-(X32-COEX3-Pad60)") (class "Default")
      (node (ref "X32") (pin "60") (pinfunction "COEX3_60") (pintype "bidirectional"))
    )
    (net (code "988") (name "unconnected-(X32-COEX_RXD-Pad64)") (class "Default")
      (node (ref "X32") (pin "64") (pinfunction "COEX_RXD_64") (pintype "bidirectional"))
    )
    (net (code "989") (name "unconnected-(X32-COEX_TXD-Pad62)") (class "Default")
      (node (ref "X32") (pin "62") (pinfunction "COEX_TXD_62") (pintype "bidirectional"))
    )
    (net (code "990") (name "unconnected-(X32-CONFIG_0-Pad21)") (class "Default")
      (node (ref "X32") (pin "21") (pinfunction "CONFIG_0_21") (pintype "output"))
    )
    (net (code "991") (name "unconnected-(X32-CONFIG_1-Pad69)") (class "Default")
      (node (ref "X32") (pin "69") (pinfunction "CONFIG_1_69") (pintype "input"))
    )
    (net (code "992") (name "unconnected-(X32-CONFIG_2-Pad75)") (class "Default")
      (node (ref "X32") (pin "75") (pinfunction "CONFIG_2_75") (pintype "input"))
    )
    (net (code "993") (name "unconnected-(X32-CONFIG_3-Pad1)") (class "Default")
      (node (ref "X32") (pin "1") (pinfunction "CONFIG_3_1") (pintype "output"))
    )
    (net (code "994") (name "unconnected-(X32-DEVSLP-Pad38)") (class "Default")
      (node (ref "X32") (pin "38") (pinfunction "DEVSLP_38") (pintype "input"))
    )
    (net (code "995") (name "unconnected-(X32-DPR-Pad25)") (class "Default")
      (node (ref "X32") (pin "25") (pinfunction "DPR_25") (pintype "input"))
    )
    (net (code "996") (name "unconnected-(X32-GPIO1{slash}ANTCTL0-Pad59)") (class "Default")
      (node (ref "X32") (pin "59") (pinfunction "GPIO1/ANTCTL0_59") (pintype "bidirectional"))
    )
    (net (code "997") (name "unconnected-(X32-GPIO2{slash}ANTCTL1-Pad61)") (class "Default")
      (node (ref "X32") (pin "61") (pinfunction "GPIO2/ANTCTL1_61") (pintype "bidirectional"))
    )
    (net (code "998") (name "unconnected-(X32-GPIO3{slash}ANTCTL2-Pad63)") (class "Default")
      (node (ref "X32") (pin "63") (pinfunction "GPIO3/ANTCTL2_63") (pintype "bidirectional"))
    )
    (net (code "999") (name "unconnected-(X32-GPIO4{slash}ANTCTL3-Pad65)") (class "Default")
      (node (ref "X32") (pin "65") (pinfunction "GPIO4/ANTCTL3_65") (pintype "bidirectional"))
    )
    (net (code "1000") (name "unconnected-(X32-GPIO_1{slash}SMB_DATA{slash}I2C_SDA{slash}USIM2_DATA-Pad42)") (class "Default")
      (node (ref "X32") (pin "42") (pinfunction "GPIO_1/SMB_DATA/I2C_SDA/USIM2_DATA_42") (pintype "bidirectional"))
    )
    (net (code "1001") (name "unconnected-(X32-GPIO_2{slash}ALERT#{slash}USIM2_CLK-Pad44)") (class "Default")
      (node (ref "X32") (pin "44") (pinfunction "GPIO_2/ALERT#/USIM2_CLK_44") (pintype "bidirectional"))
    )
    (net (code "1002") (name "unconnected-(X32-GPIO_3{slash}USIM2_RESET-Pad46)") (class "Default")
      (node (ref "X32") (pin "46") (pinfunction "GPIO_3/USIM2_RESET_46") (pintype "bidirectional"))
    )
    (net (code "1003") (name "unconnected-(X32-GPIO_4{slash}USIM2_PWR-Pad48)") (class "Default")
      (node (ref "X32") (pin "48") (pinfunction "GPIO_4/USIM2_PWR_48") (pintype "bidirectional"))
    )
    (net (code "1004") (name "unconnected-(X32-GPIO_5{slash}PCM_SYNC-Pad20)") (class "Default")
      (node (ref "X32") (pin "20") (pinfunction "GPIO_5/PCM_SYNC_20") (pintype "bidirectional"))
    )
    (net (code "1005") (name "unconnected-(X32-GPIO_6{slash}PCM_IN-Pad22)") (class "Default")
      (node (ref "X32") (pin "22") (pinfunction "GPIO_6/PCM_IN_22") (pintype "bidirectional"))
    )
    (net (code "1006") (name "unconnected-(X32-GPIO_7{slash}PCM_OUT-Pad24)") (class "Default")
      (node (ref "X32") (pin "24") (pinfunction "GPIO_7/PCM_OUT_24") (pintype "bidirectional"))
    )
    (net (code "1007") (name "unconnected-(X32-GPIO_8{slash}PCM_CLK-Pad28)") (class "Default")
      (node (ref "X32") (pin "28") (pinfunction "GPIO_8/PCM_CLK_28") (pintype "bidirectional"))
    )
    (net (code "1008") (name "unconnected-(X32-GPIO_10{slash}W_DISABLE2#-Pad26)") (class "Default")
      (node (ref "X32") (pin "26") (pinfunction "GPIO_10/W_DISABLE2#_26") (pintype "bidirectional"))
    )
    (net (code "1009") (name "unconnected-(X32-GPIO_11{slash}WAKE_ON_WAN#-Pad23)") (class "Default")
      (node (ref "X32") (pin "23") (pinfunction "GPIO_11/WAKE_ON_WAN#_23") (pintype "bidirectional"))
    )
    (net (code "1010") (name "unconnected-(X32-MFG1{slash}UART_CTS{slash}I2C_DATA-Pad56)") (class "Default")
      (node (ref "X32") (pin "56") (pinfunction "MFG1/UART_CTS/I2C_DATA_56") (pintype "bidirectional"))
    )
    (net (code "1011") (name "unconnected-(X32-MFG2{slash}UART_RXD{slash}I2C_DATA-Pad58)") (class "Default")
      (node (ref "X32") (pin "58") (pinfunction "MFG2/UART_RXD/I2C_DATA_58") (pintype "bidirectional"))
    )
    (net (code "1012") (name "unconnected-(X32-PERN0{slash}SATA-B+-Pad41)") (class "Default")
      (node (ref "X32") (pin "41") (pinfunction "PERN0/SATA-B+_41") (pintype "bidirectional"))
    )
    (net (code "1013") (name "unconnected-(X32-PERN1{slash}USB_SS_TX--Pad29)") (class "Default")
      (node (ref "X32") (pin "29") (pinfunction "PERN1/USB_SS_TX-_29") (pintype "bidirectional"))
    )
    (net (code "1014") (name "unconnected-(X32-PERP0{slash}SATA-B--Pad43)") (class "Default")
      (node (ref "X32") (pin "43") (pinfunction "PERP0/SATA-B-_43") (pintype "bidirectional"))
    )
    (net (code "1015") (name "unconnected-(X32-PERP1{slash}USB_SS_TX+-Pad31)") (class "Default")
      (node (ref "X32") (pin "31") (pinfunction "PERP1/USB_SS_TX+_31") (pintype "bidirectional"))
    )
    (net (code "1016") (name "unconnected-(X32-PERST#-Pad50)") (class "Default")
      (node (ref "X32") (pin "50") (pinfunction "PERST#_50") (pintype "input"))
    )
    (net (code "1017") (name "unconnected-(X32-PETN0{slash}SATA-A--Pad47)") (class "Default")
      (node (ref "X32") (pin "47") (pinfunction "PETN0/SATA-A-_47") (pintype "bidirectional"))
    )
    (net (code "1018") (name "unconnected-(X32-PETN1{slash}USB_SS_RX--Pad35)") (class "Default")
      (node (ref "X32") (pin "35") (pinfunction "PETN1/USB_SS_RX-_35") (pintype "bidirectional"))
    )
    (net (code "1019") (name "unconnected-(X32-PETP0{slash}SATA-A+-Pad49)") (class "Default")
      (node (ref "X32") (pin "49") (pinfunction "PETP0/SATA-A+_49") (pintype "bidirectional"))
    )
    (net (code "1020") (name "unconnected-(X32-PETP1{slash}USB_SS_RX+-Pad37)") (class "Default")
      (node (ref "X32") (pin "37") (pinfunction "PETP1/USB_SS_RX+_37") (pintype "bidirectional"))
    )
    (net (code "1021") (name "unconnected-(X32-PEWAKE#{slash}UART_RTS-Pad54)") (class "Default")
      (node (ref "X32") (pin "54") (pinfunction "PEWAKE#/UART_RTS_54") (pintype "bidirectional"))
    )
    (net (code "1022") (name "unconnected-(X32-REFCLKN-Pad53)") (class "Default")
      (node (ref "X32") (pin "53") (pinfunction "REFCLKN_53") (pintype "bidirectional"))
    )
    (net (code "1023") (name "unconnected-(X32-REFCLKP-Pad55)") (class "Default")
      (node (ref "X32") (pin "55") (pinfunction "REFCLKP_55") (pintype "bidirectional"))
    )
    (net (code "1024") (name "unconnected-(X32-SIM_DETECT-Pad66)") (class "Default")
      (node (ref "X32") (pin "66") (pinfunction "SIM_DETECT_66") (pintype "input"))
    )
    (net (code "1025") (name "unconnected-(X32-SUSCLK_32KHZ-Pad68)") (class "Default")
      (node (ref "X32") (pin "68") (pinfunction "SUSCLK_32KHZ_68") (pintype "input"))
    )
    (net (code "1026") (name "unconnected-(X33-DEVSLP{slash}GND{slash}NC-Pad38)") (class "Default")
      (node (ref "X33") (pin "38") (pinfunction "DEVSLP/GND/NC_38") (pintype "input"))
    )
    (net (code "1027") (name "unconnected-(X33-GND{slash}NC-Pad32)") (class "Default")
      (node (ref "X33") (pin "32") (pinfunction "GND/NC_32") (pintype "input"))
    )
    (net (code "1028") (name "unconnected-(X33-MFG_CLOCK{slash}NC-Pad58)") (class "Default")
      (node (ref "X33") (pin "58") (pinfunction "MFG_CLOCK/NC_58") (pintype "bidirectional"))
    )
    (net (code "1029") (name "unconnected-(X33-MFG_DATA{slash}NC-Pad56)") (class "Default")
      (node (ref "X33") (pin "56") (pinfunction "MFG_DATA/NC_56") (pintype "bidirectional"))
    )
    (net (code "1030") (name "unconnected-(X33-NC-Pad20)") (class "Default")
      (node (ref "X33") (pin "20") (pinfunction "NC_20") (pintype "passive"))
    )
    (net (code "1031") (name "unconnected-(X33-NC-Pad24)") (class "Default")
      (node (ref "X33") (pin "24") (pinfunction "NC_24") (pintype "passive"))
    )
    (net (code "1032") (name "unconnected-(X33-NC-Pad26)") (class "Default")
      (node (ref "X33") (pin "26") (pinfunction "NC_26") (pintype "passive"))
    )
    (net (code "1033") (name "unconnected-(X33-NC-Pad28)") (class "Default")
      (node (ref "X33") (pin "28") (pinfunction "NC_28") (pintype "passive"))
    )
    (net (code "1034") (name "unconnected-(X33-NC-Pad46)") (class "Default")
      (node (ref "X33") (pin "46") (pinfunction "NC_46") (pintype "passive"))
    )
    (net (code "1035") (name "unconnected-(X33-NC-Pad48)") (class "Default")
      (node (ref "X33") (pin "48") (pinfunction "NC_48") (pintype "passive"))
    )
    (net (code "1036") (name "unconnected-(X33-NC-Pad67)") (class "Default")
      (node (ref "X33") (pin "67") (pinfunction "NC_67") (pintype "input"))
    )
    (net (code "1037") (name "unconnected-(X33-PEDET{slash}NC(PCIE){slash}GND(SATA)-Pad69)") (class "Default")
      (node (ref "X33") (pin "69") (pinfunction "PEDET/NC(PCIE)/GND(SATA)_69") (pintype "input"))
    )
    (net (code "1038") (name "unconnected-(X33-PERN1-Pad29)") (class "Default")
      (node (ref "X33") (pin "29") (pinfunction "PERN1_29") (pintype "bidirectional"))
    )
    (net (code "1039") (name "unconnected-(X33-PERN2-Pad17)") (class "Default")
      (node (ref "X33") (pin "17") (pinfunction "PERN2_17") (pintype "bidirectional"))
    )
    (net (code "1040") (name "unconnected-(X33-PERN3-Pad5)") (class "Default")
      (node (ref "X33") (pin "5") (pinfunction "PERN3_5") (pintype "bidirectional"))
    )
    (net (code "1041") (name "unconnected-(X33-PERP1-Pad31)") (class "Default")
      (node (ref "X33") (pin "31") (pinfunction "PERP1_31") (pintype "bidirectional"))
    )
    (net (code "1042") (name "unconnected-(X33-PERP2-Pad19)") (class "Default")
      (node (ref "X33") (pin "19") (pinfunction "PERP2_19") (pintype "bidirectional"))
    )
    (net (code "1043") (name "unconnected-(X33-PERP3-Pad7)") (class "Default")
      (node (ref "X33") (pin "7") (pinfunction "PERP3_7") (pintype "bidirectional"))
    )
    (net (code "1044") (name "unconnected-(X33-PETN1-Pad35)") (class "Default")
      (node (ref "X33") (pin "35") (pinfunction "PETN1_35") (pintype "bidirectional"))
    )
    (net (code "1045") (name "unconnected-(X33-PETN2-Pad23)") (class "Default")
      (node (ref "X33") (pin "23") (pinfunction "PETN2_23") (pintype "bidirectional"))
    )
    (net (code "1046") (name "unconnected-(X33-PETN3-Pad11)") (class "Default")
      (node (ref "X33") (pin "11") (pinfunction "PETN3_11") (pintype "bidirectional"))
    )
    (net (code "1047") (name "unconnected-(X33-PETP1-Pad37)") (class "Default")
      (node (ref "X33") (pin "37") (pinfunction "PETP1_37") (pintype "bidirectional"))
    )
    (net (code "1048") (name "unconnected-(X33-PETP2-Pad25)") (class "Default")
      (node (ref "X33") (pin "25") (pinfunction "PETP2_25") (pintype "bidirectional"))
    )
    (net (code "1049") (name "unconnected-(X33-PETP3-Pad13)") (class "Default")
      (node (ref "X33") (pin "13") (pinfunction "PETP3_13") (pintype "bidirectional"))
    )
    (net (code "1050") (name "unconnected-(X33-PLA_S3#{slash}NC-Pad30)") (class "Default")
      (node (ref "X33") (pin "30") (pinfunction "PLA_S3#/NC_30") (pintype "input"))
    )
    (net (code "1051") (name "unconnected-(X33-PLN#{slash}NC-Pad8)") (class "Default")
      (node (ref "X33") (pin "8") (pinfunction "PLN#/NC_8") (pintype "input"))
    )
    (net (code "1052") (name "unconnected-(X33-PWRDIS{slash}NC-Pad6)") (class "Default")
      (node (ref "X33") (pin "6") (pinfunction "PWRDIS/NC_6") (pintype "bidirectional"))
    )
    (net (code "1053") (name "unconnected-(X33-SMB_CLK{slash}NC-Pad40)") (class "Default")
      (node (ref "X33") (pin "40") (pinfunction "SMB_CLK/NC_40") (pintype "bidirectional"))
    )
    (net (code "1054") (name "unconnected-(X33-SMB_DATA{slash}NC-Pad42)") (class "Default")
      (node (ref "X33") (pin "42") (pinfunction "SMB_DATA/NC_42") (pintype "bidirectional"))
    )
    (net (code "1055") (name "unconnected-(X33-USB_D+{slash}NC-Pad34)") (class "Default")
      (node (ref "X33") (pin "34") (pinfunction "USB_D+/NC_34") (pintype "bidirectional"))
    )
    (net (code "1056") (name "unconnected-(X33-USB_D-{slash}NC-Pad36)") (class "Default")
      (node (ref "X33") (pin "36") (pinfunction "USB_D-/NC_36") (pintype "bidirectional"))
    )
    (net (code "1057") (name "unconnected-(X33-VIO_1V8{slash}NC-Pad22)") (class "Default")
      (node (ref "X33") (pin "22") (pinfunction "VIO_1V8/NC_22") (pintype "input"))
    )
  )
)
